# pdp8i-cpu.net
KiCad netlist of a schematic drawn in EAGLE
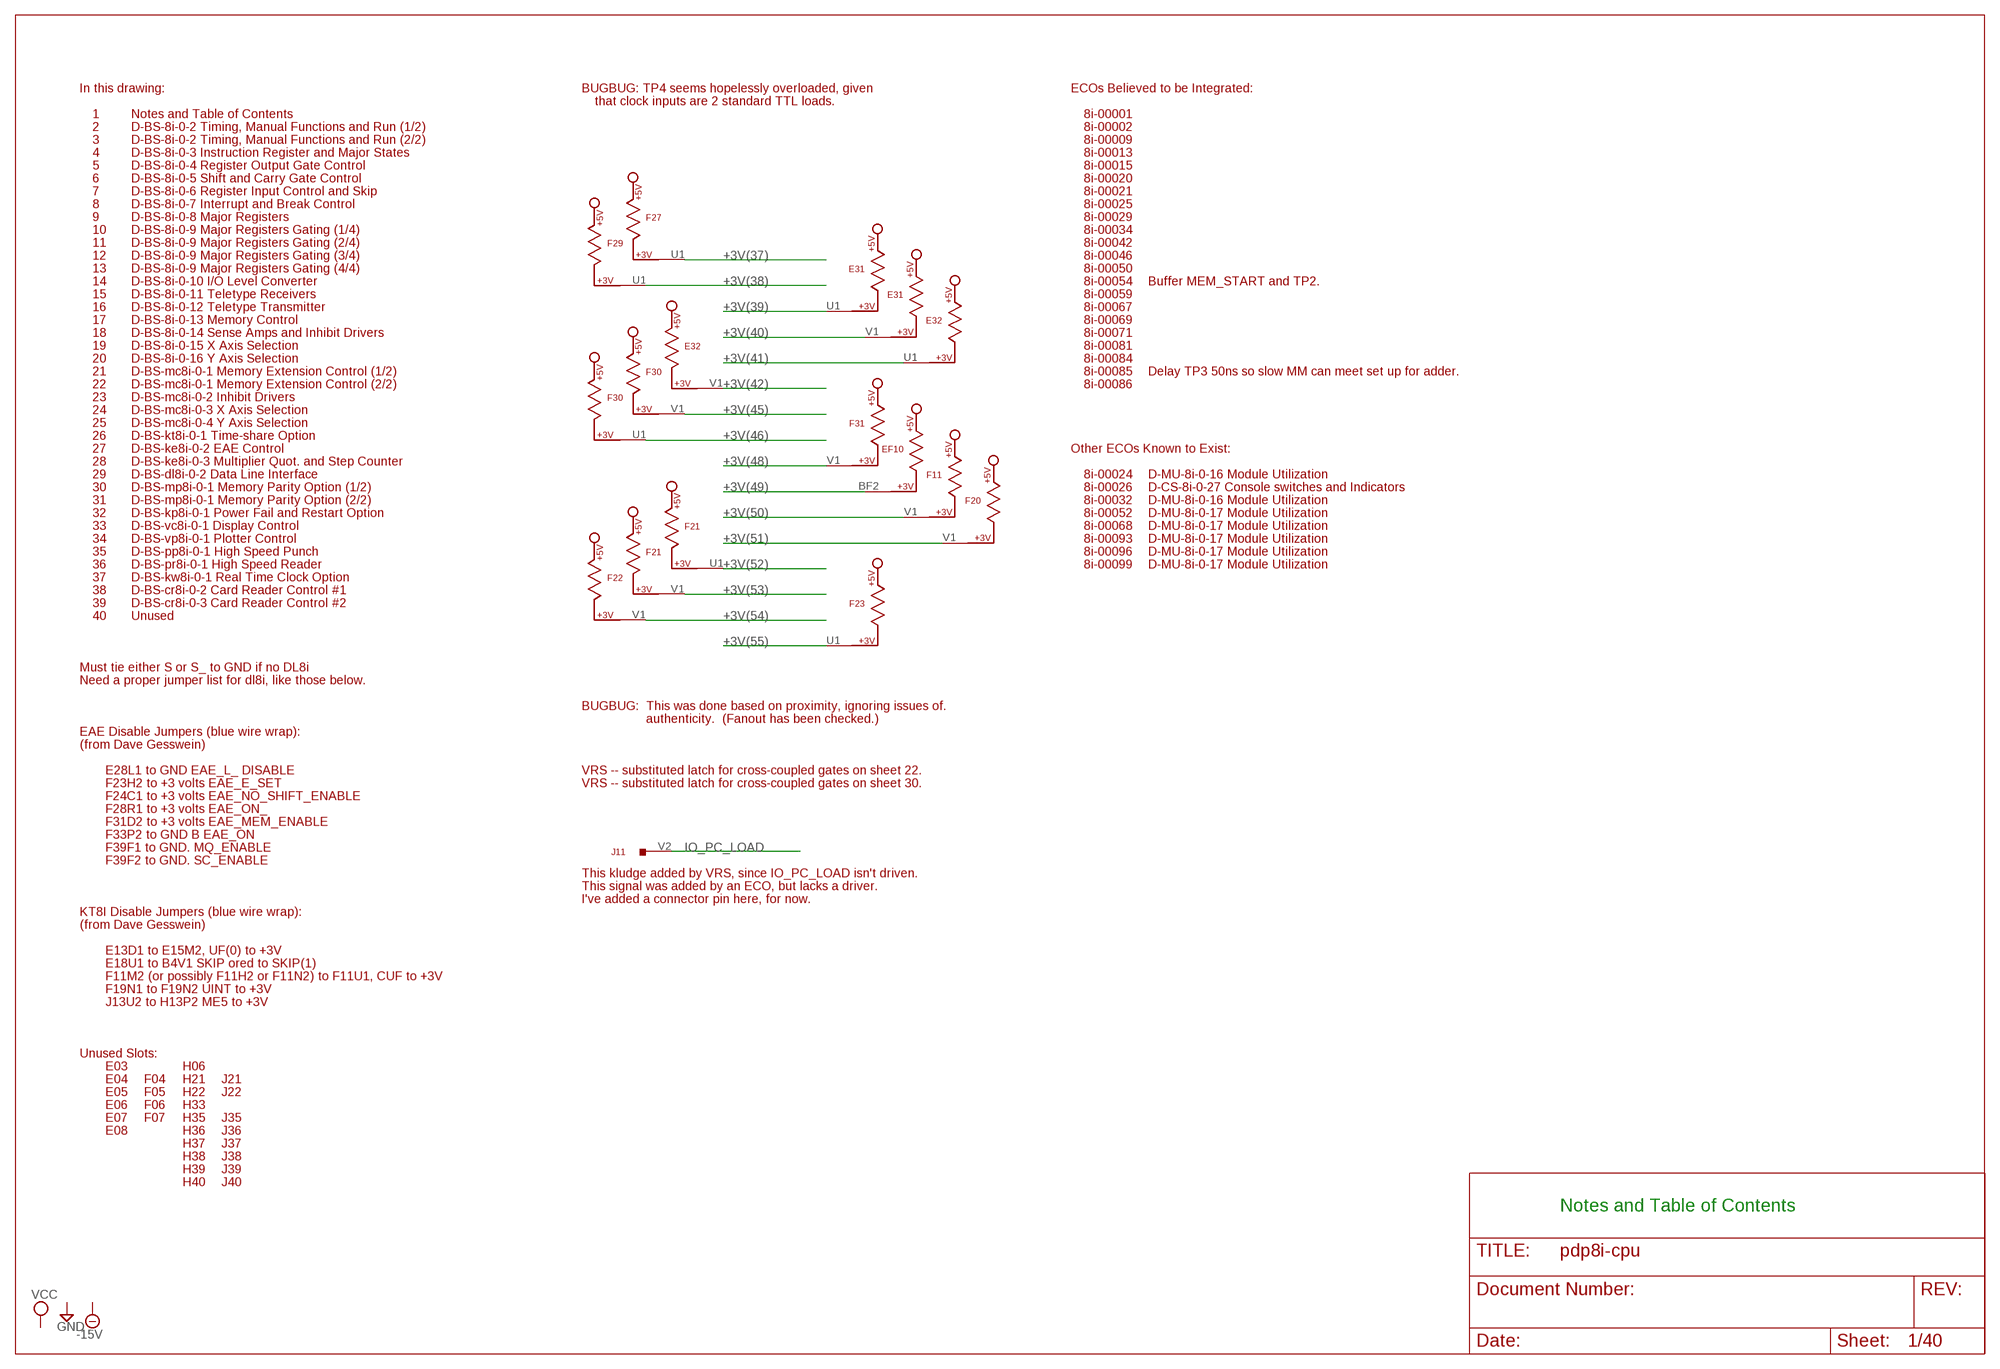
[diagram p0: schematic, sheet 1]
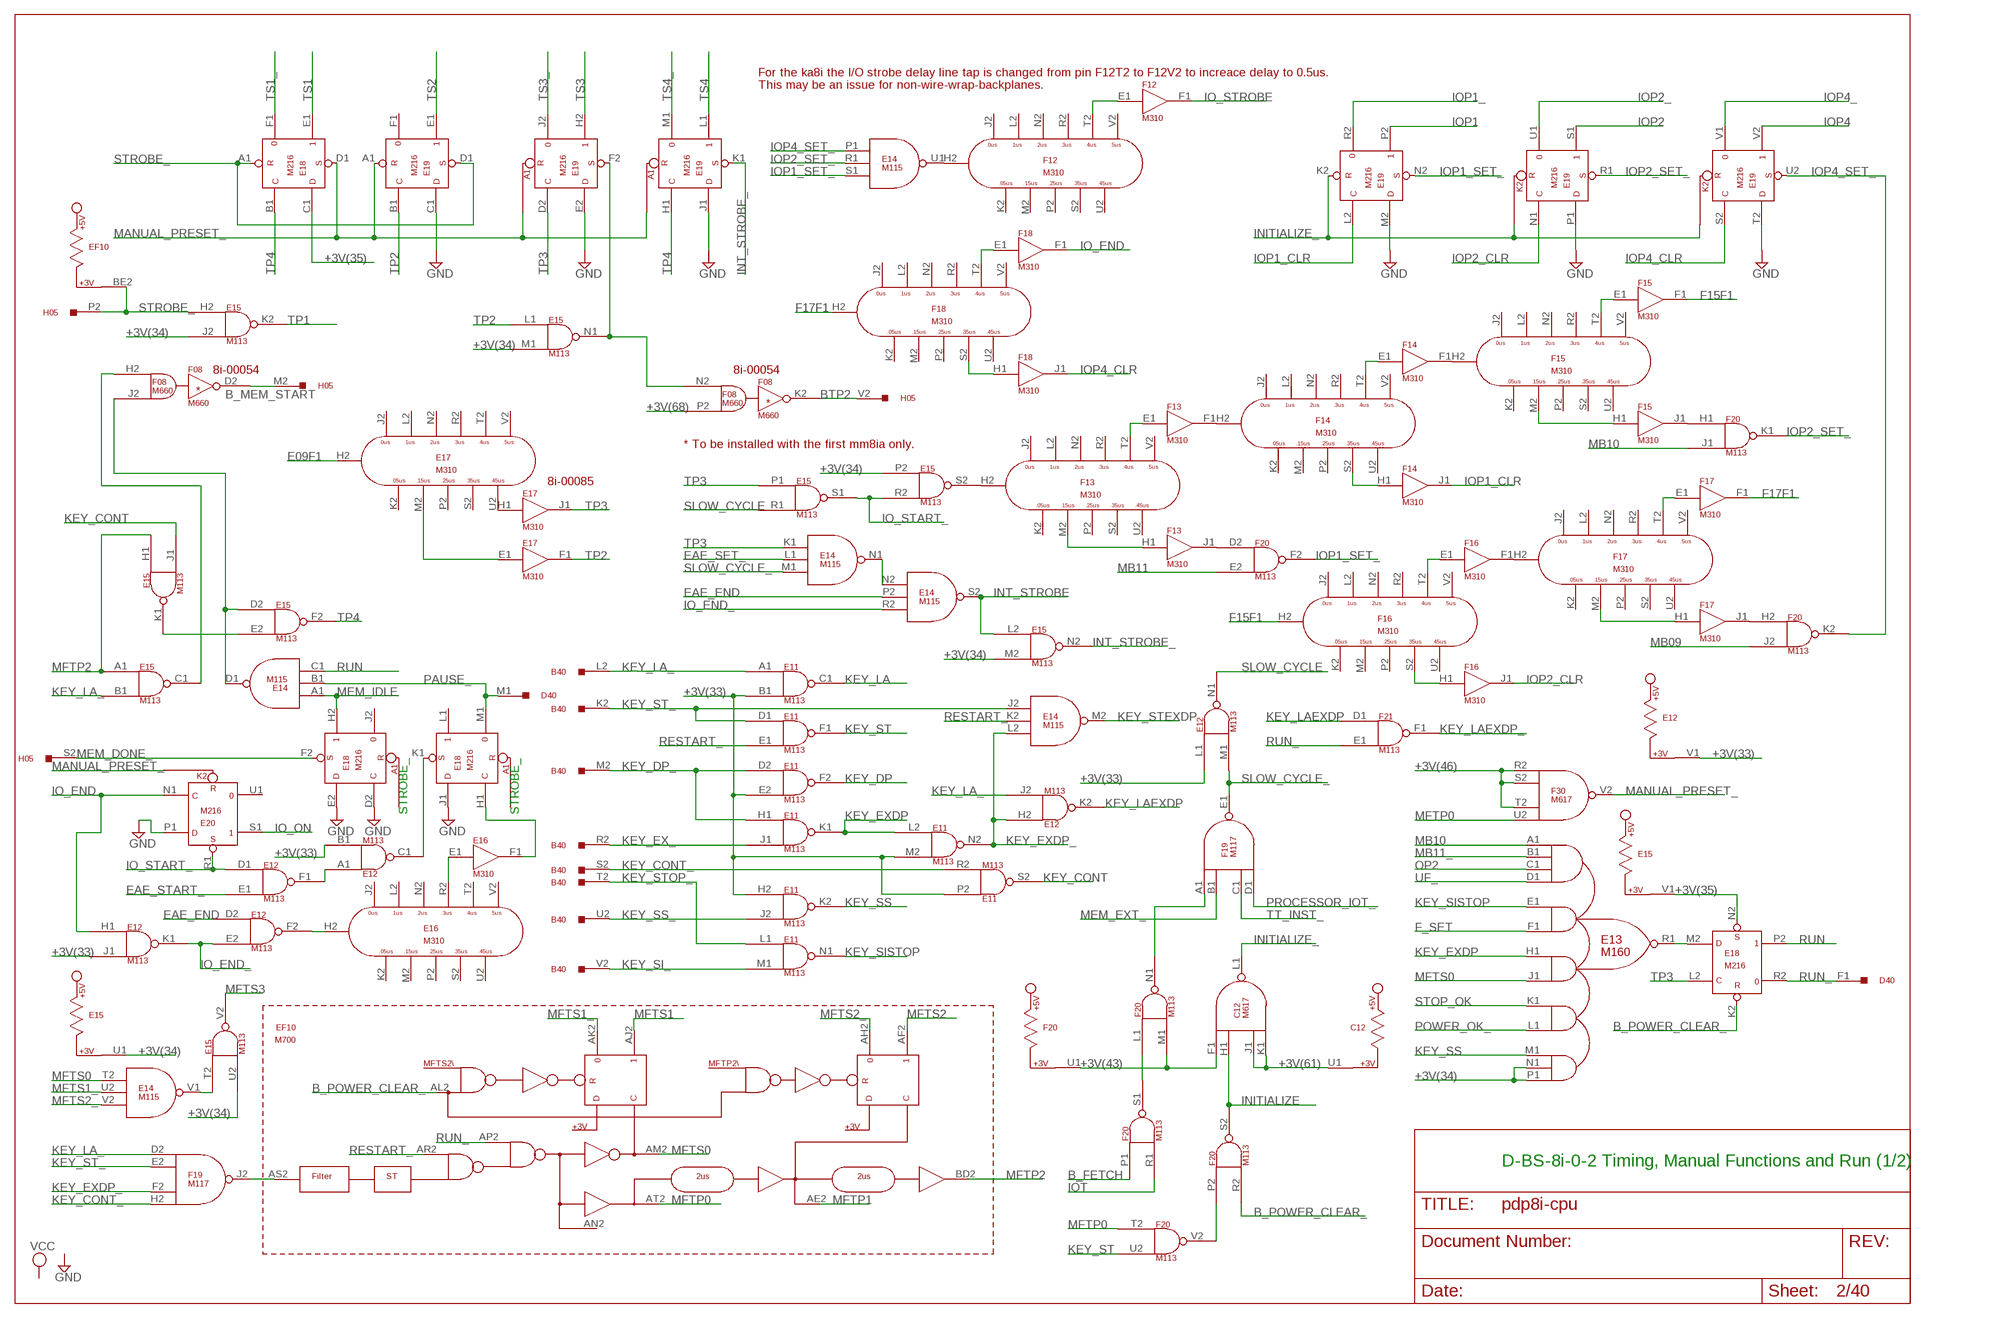
[diagram p1: schematic, sheet 2]
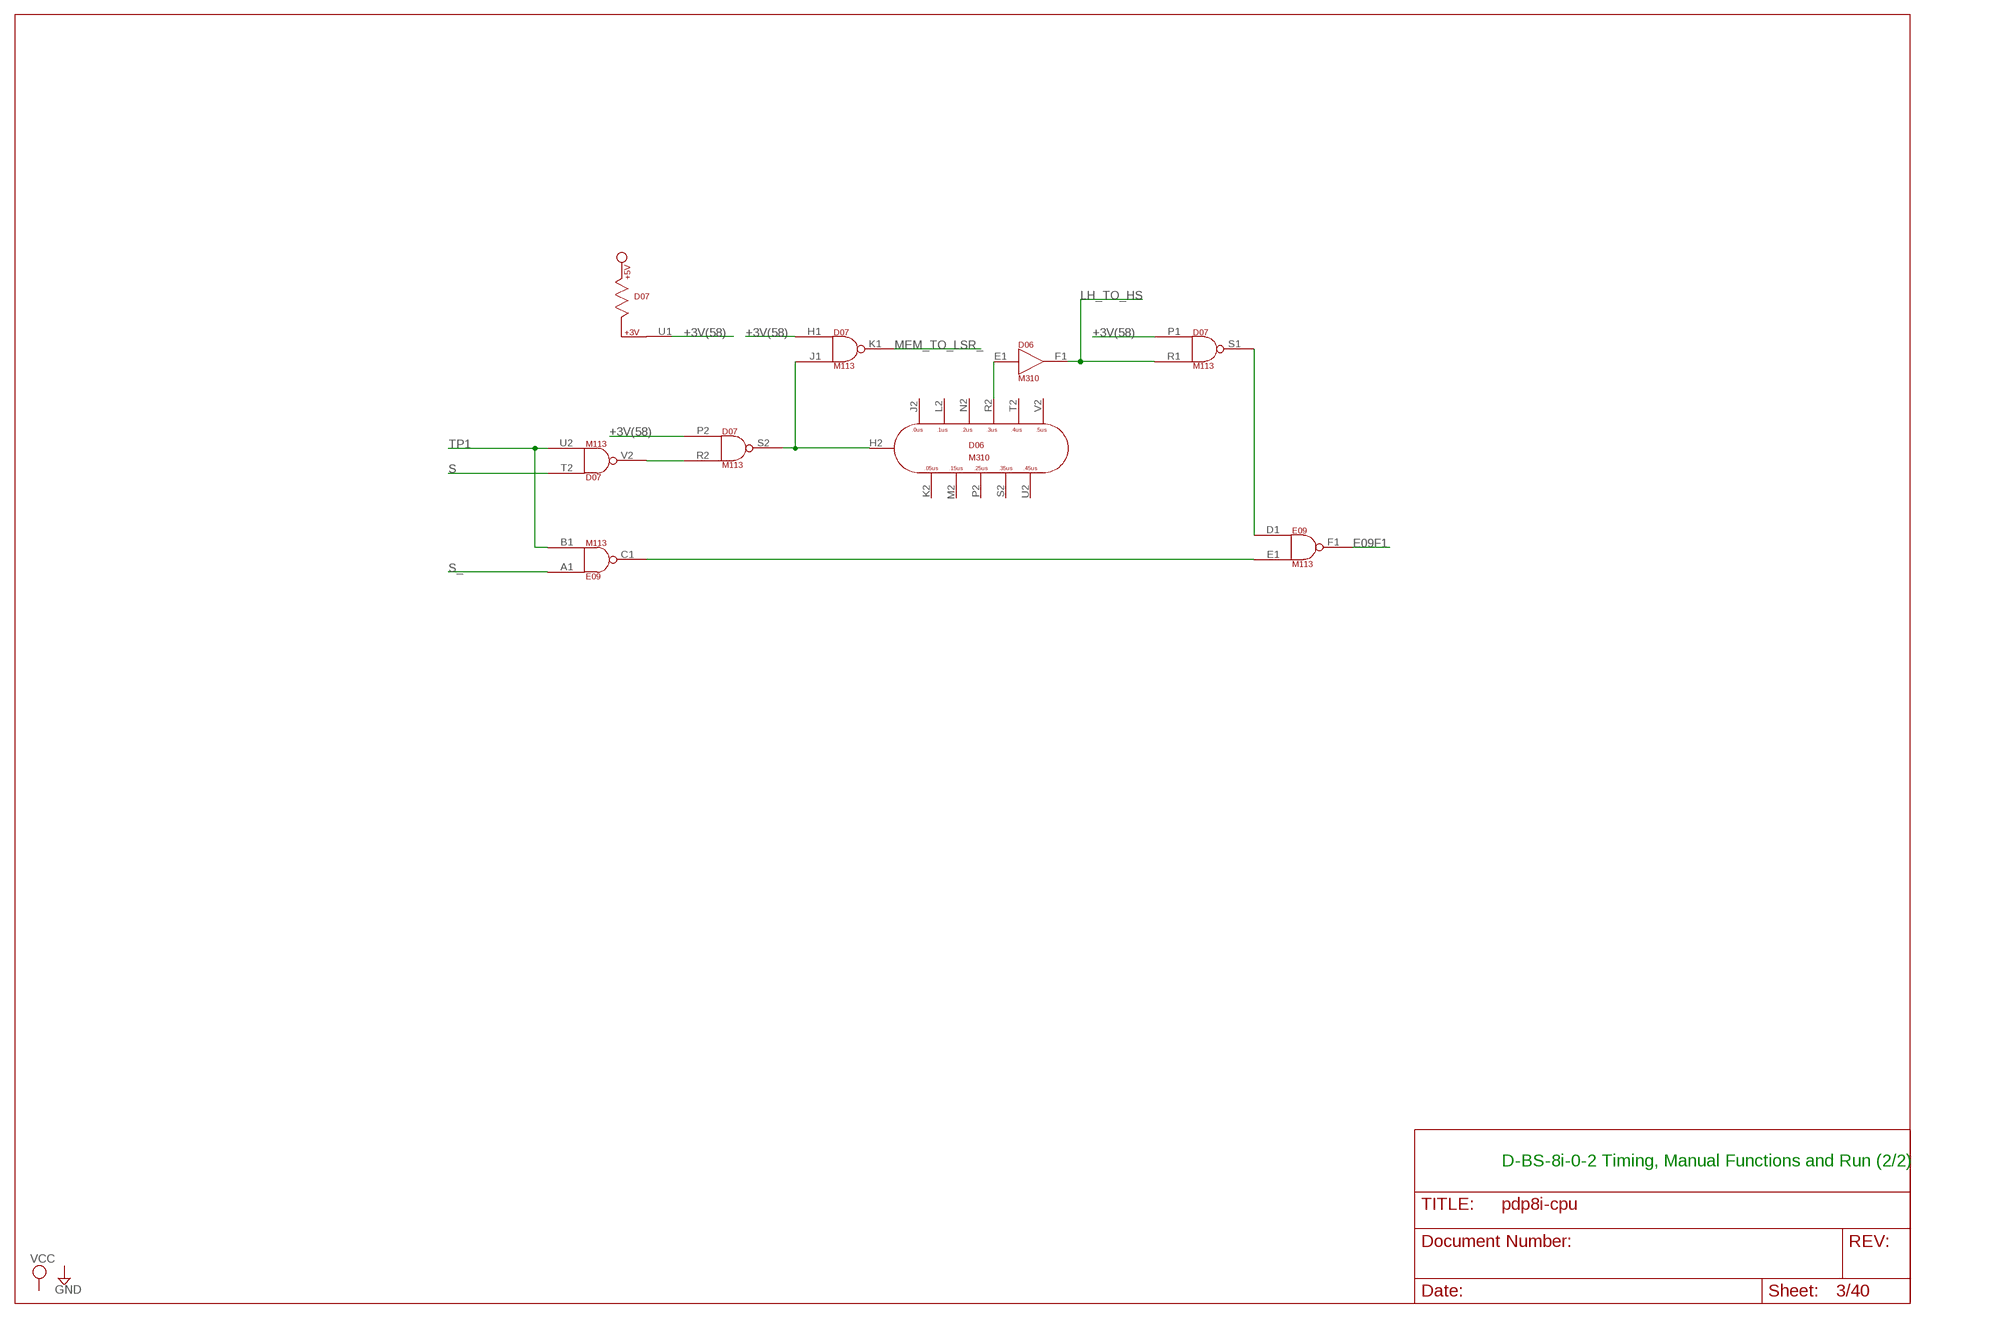
[diagram p2: schematic, sheet 3]
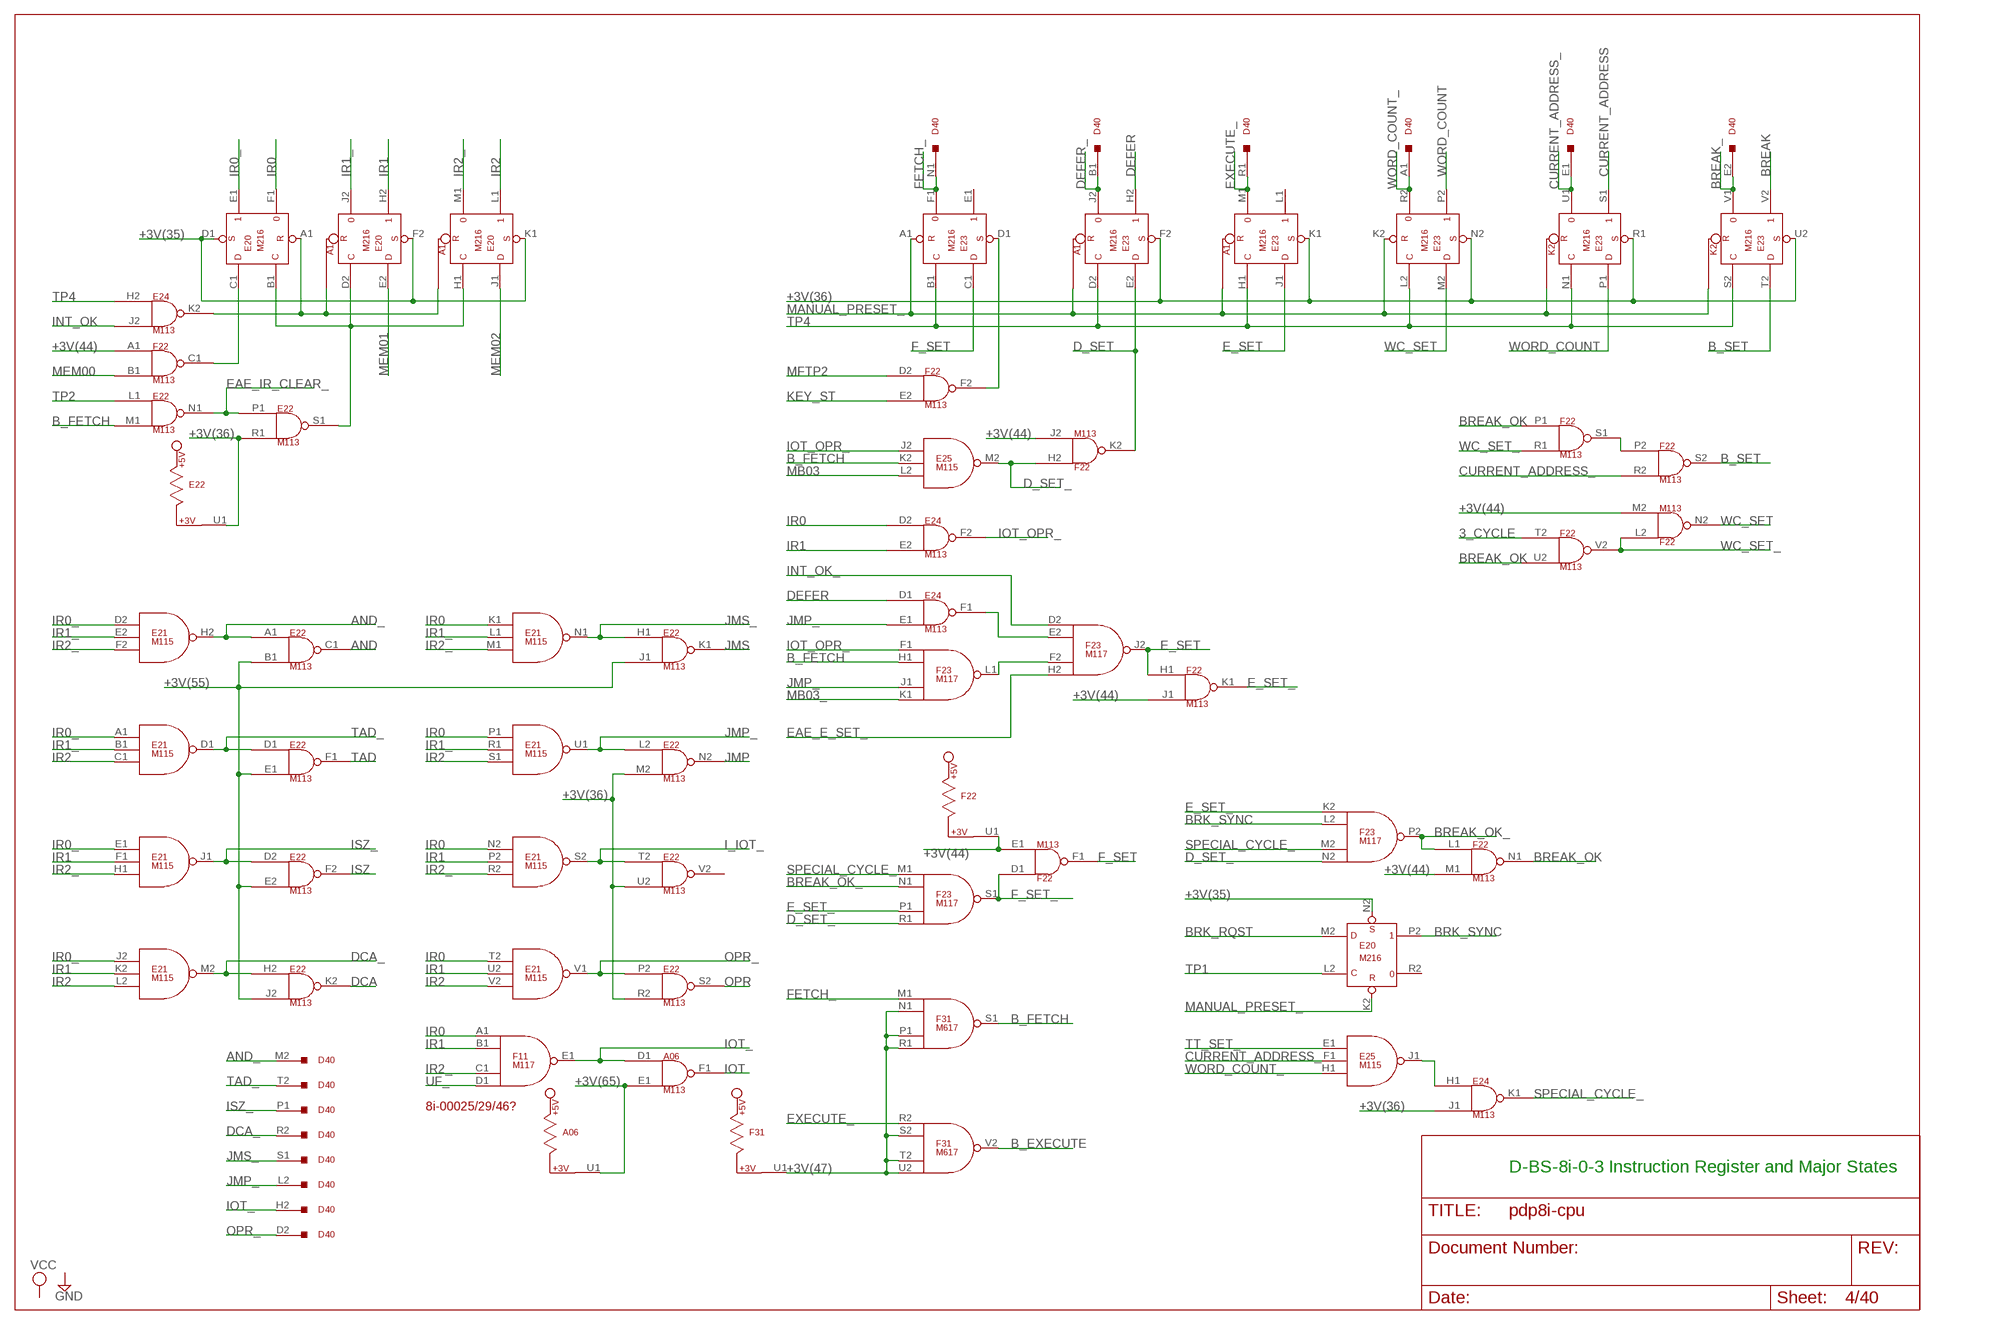
[diagram p3: schematic, sheet 4]
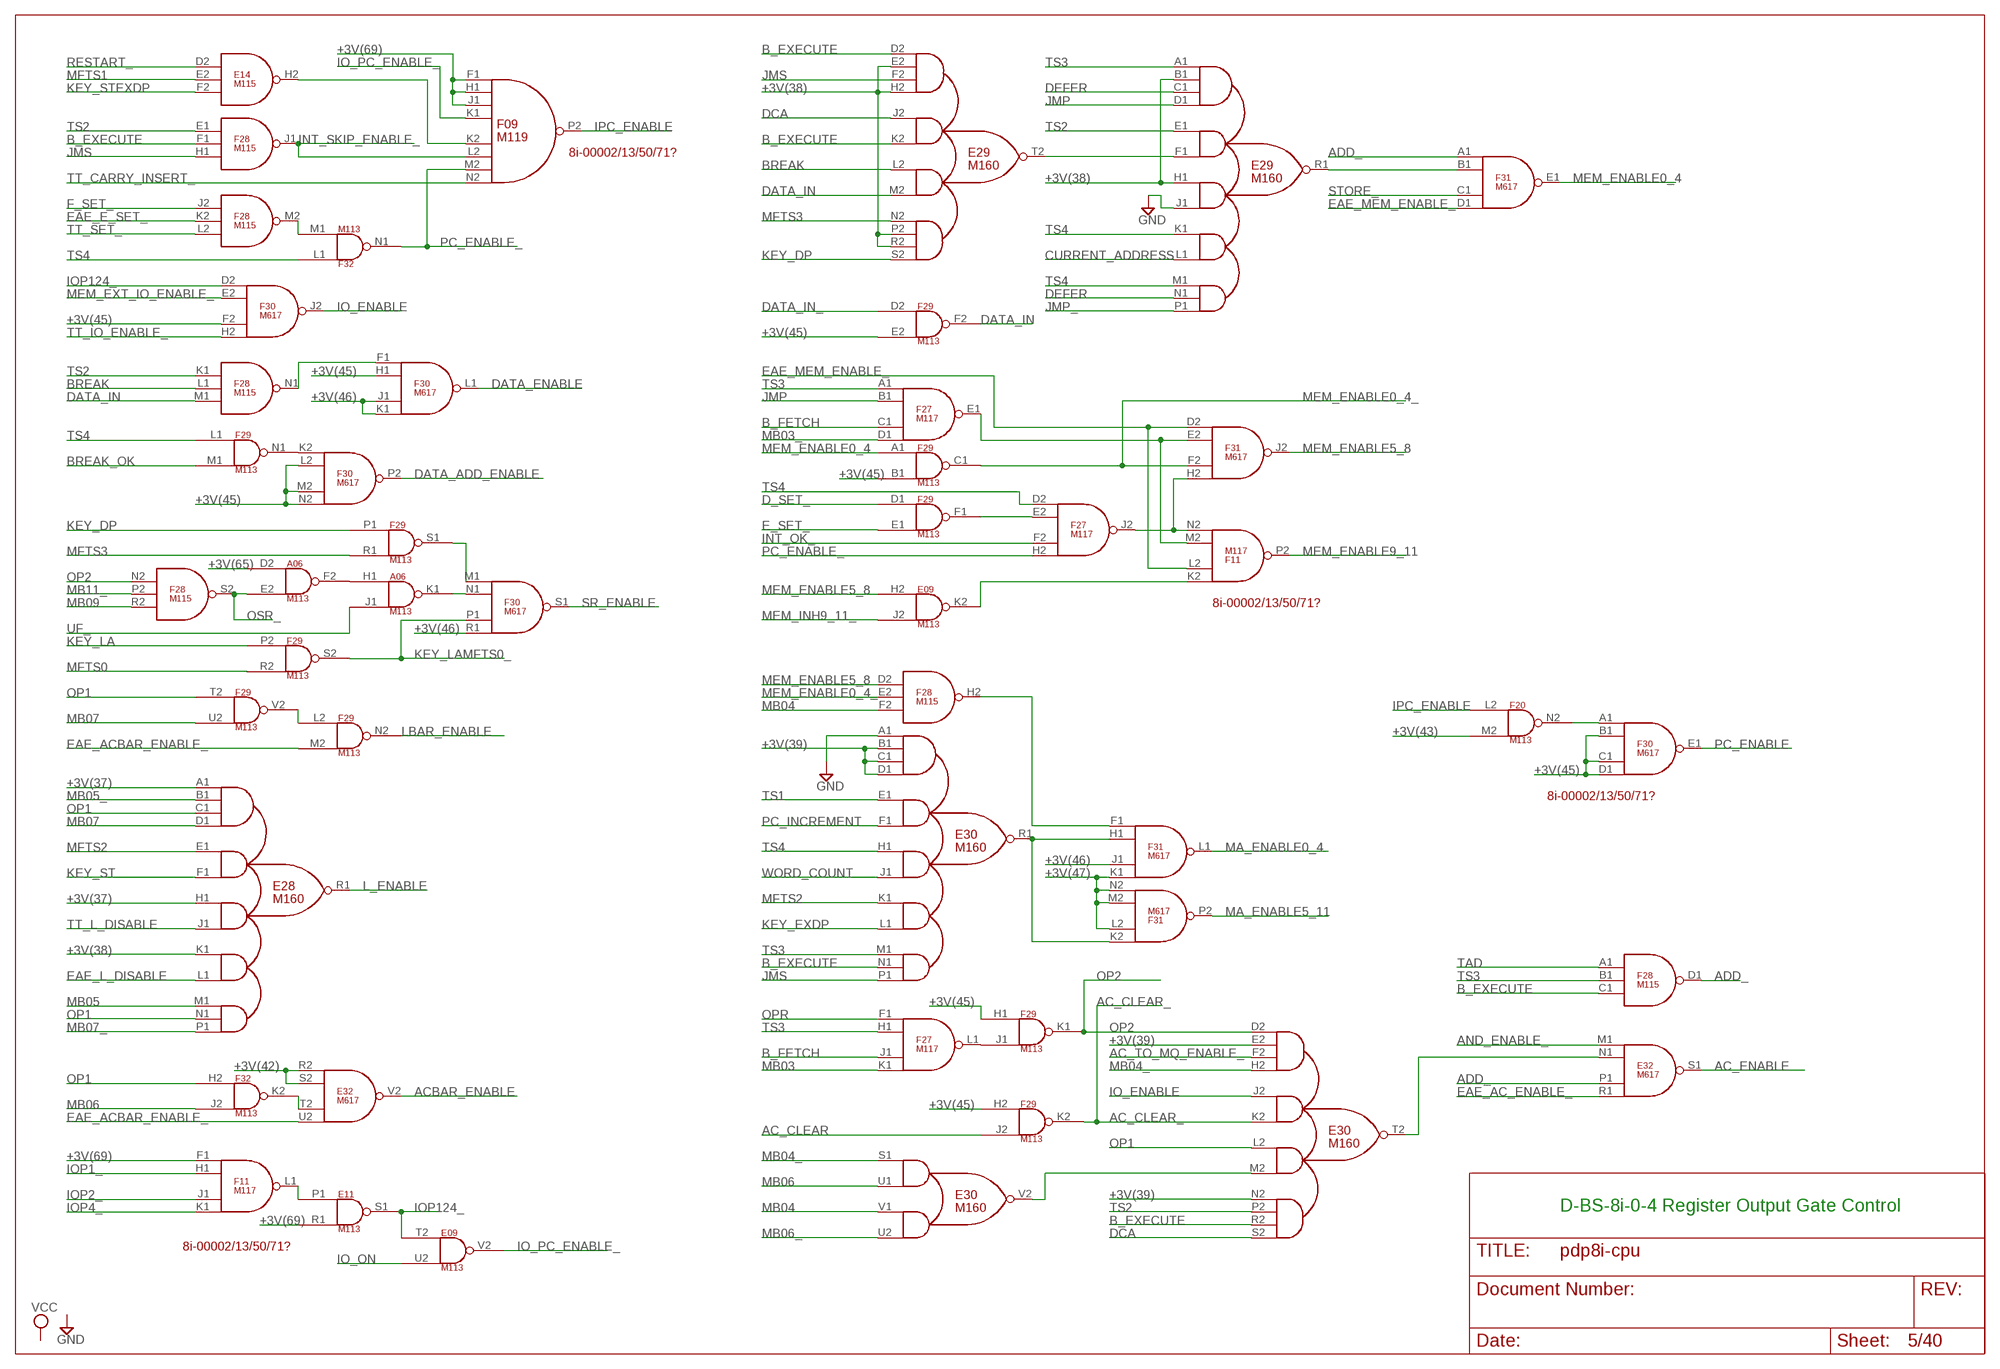
[diagram p4: schematic, sheet 5]
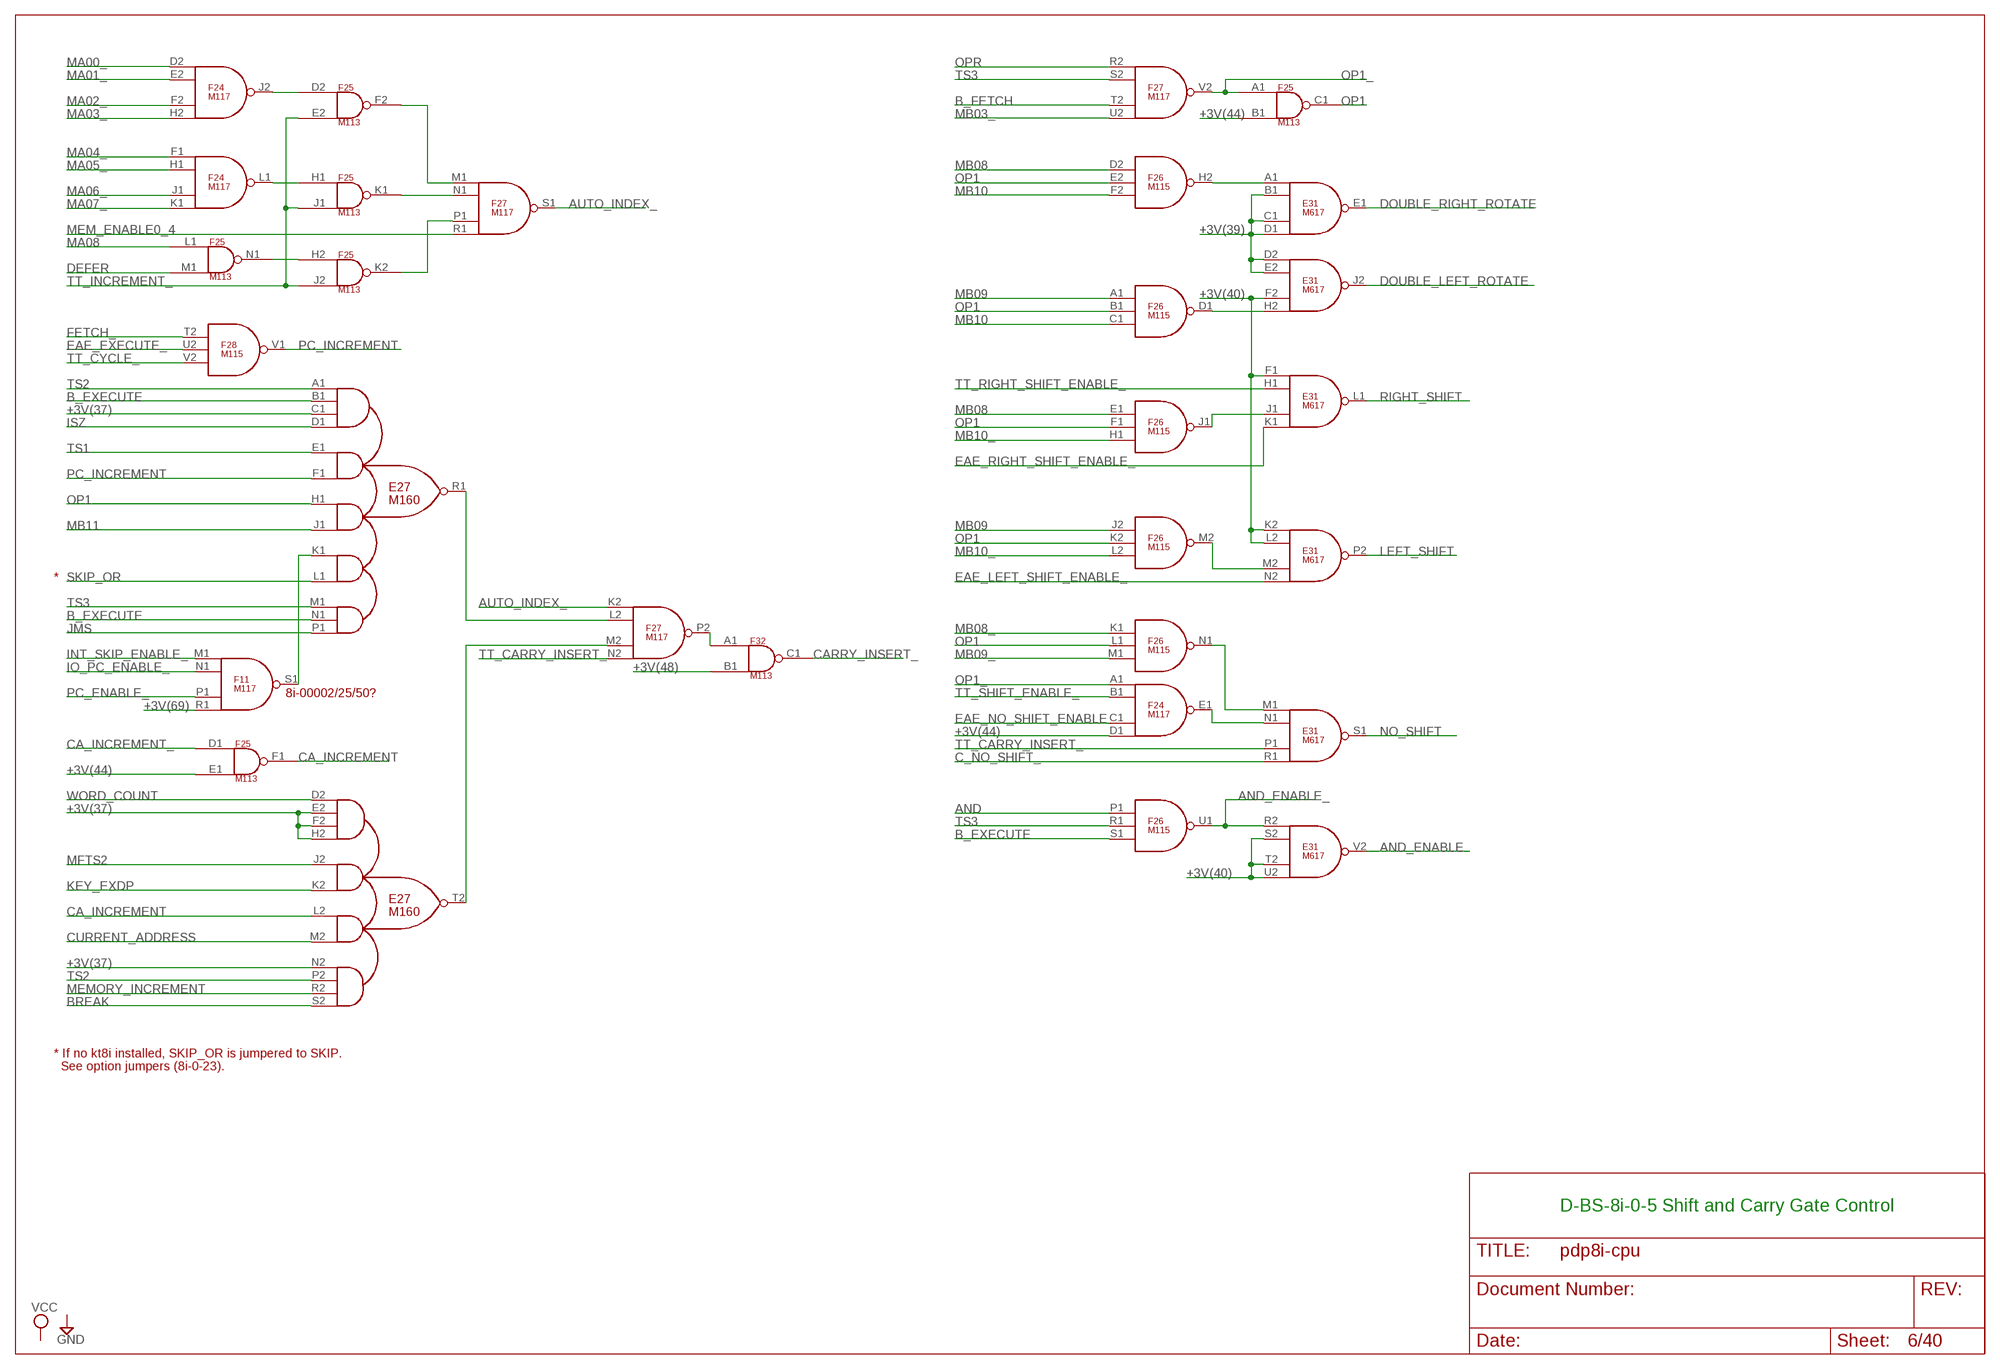
[diagram p5: schematic, sheet 6]
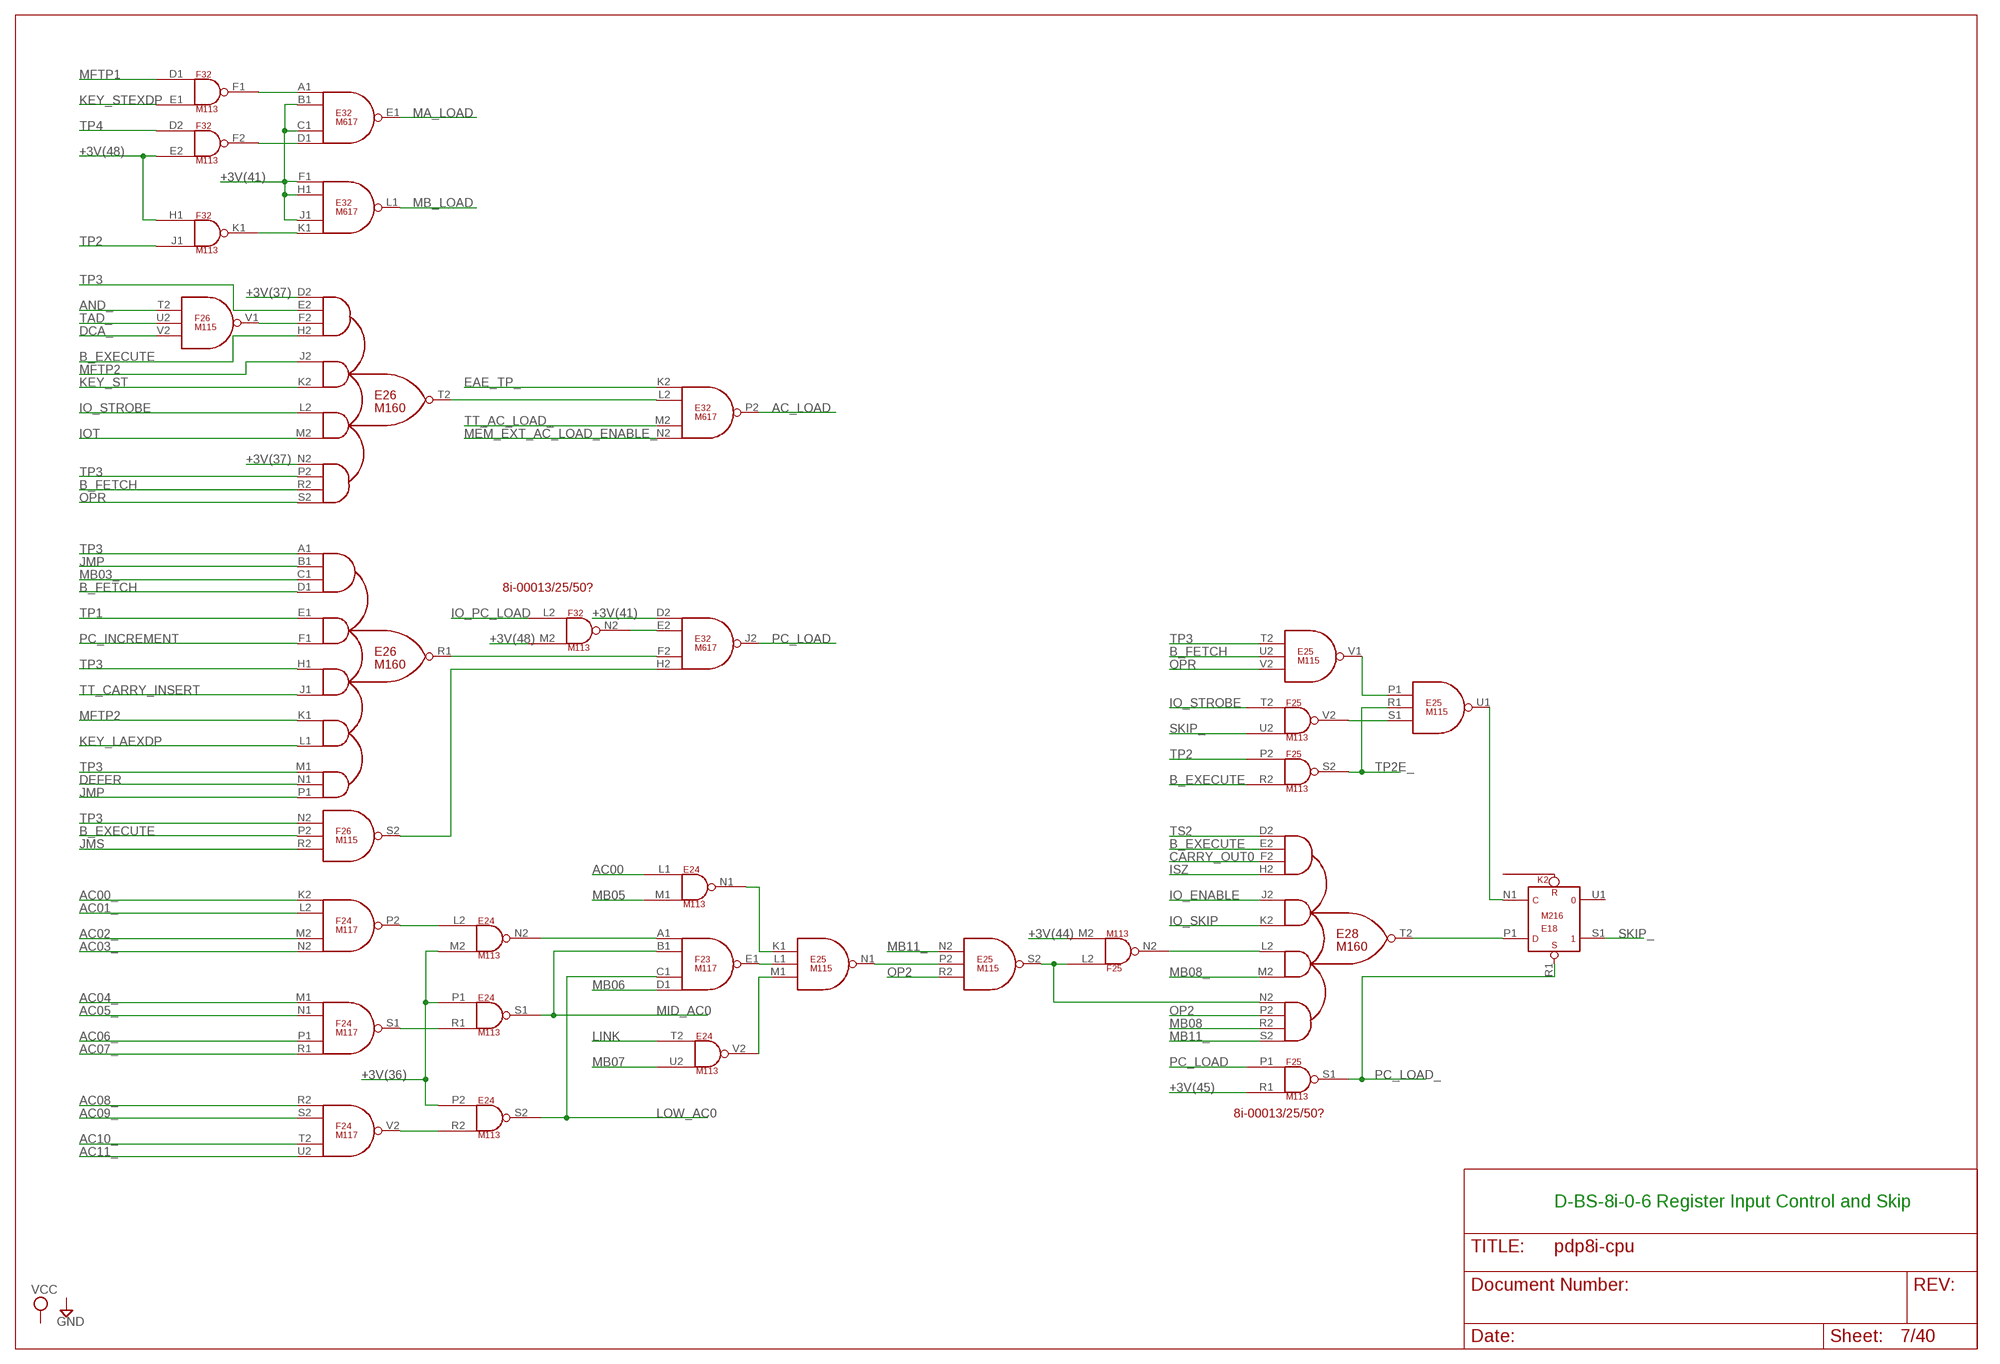
[diagram p6: schematic, sheet 7]
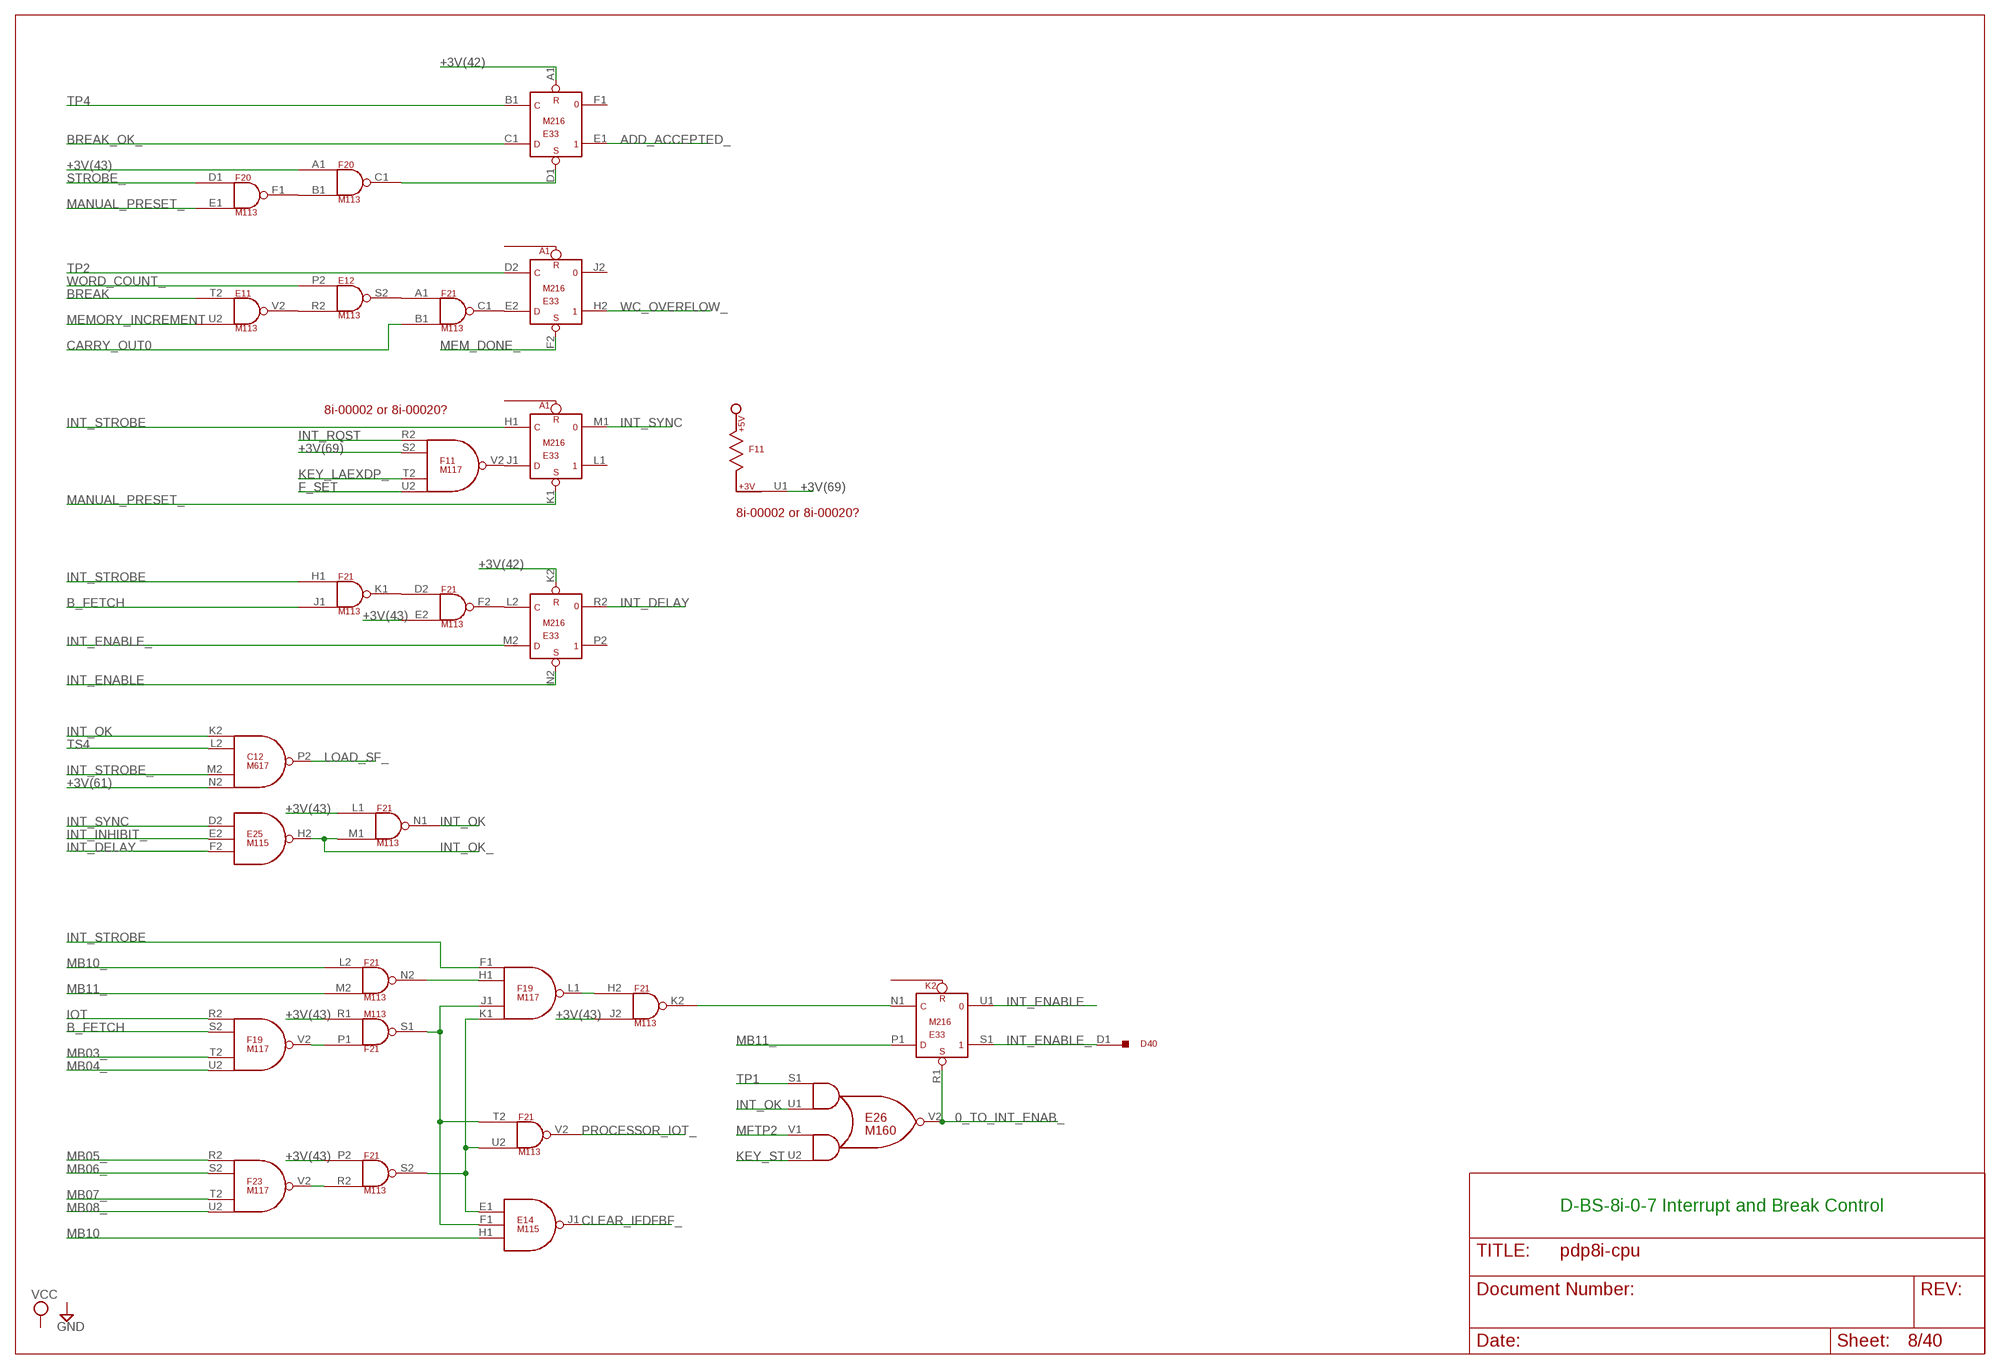
[diagram p7: schematic, sheet 8]
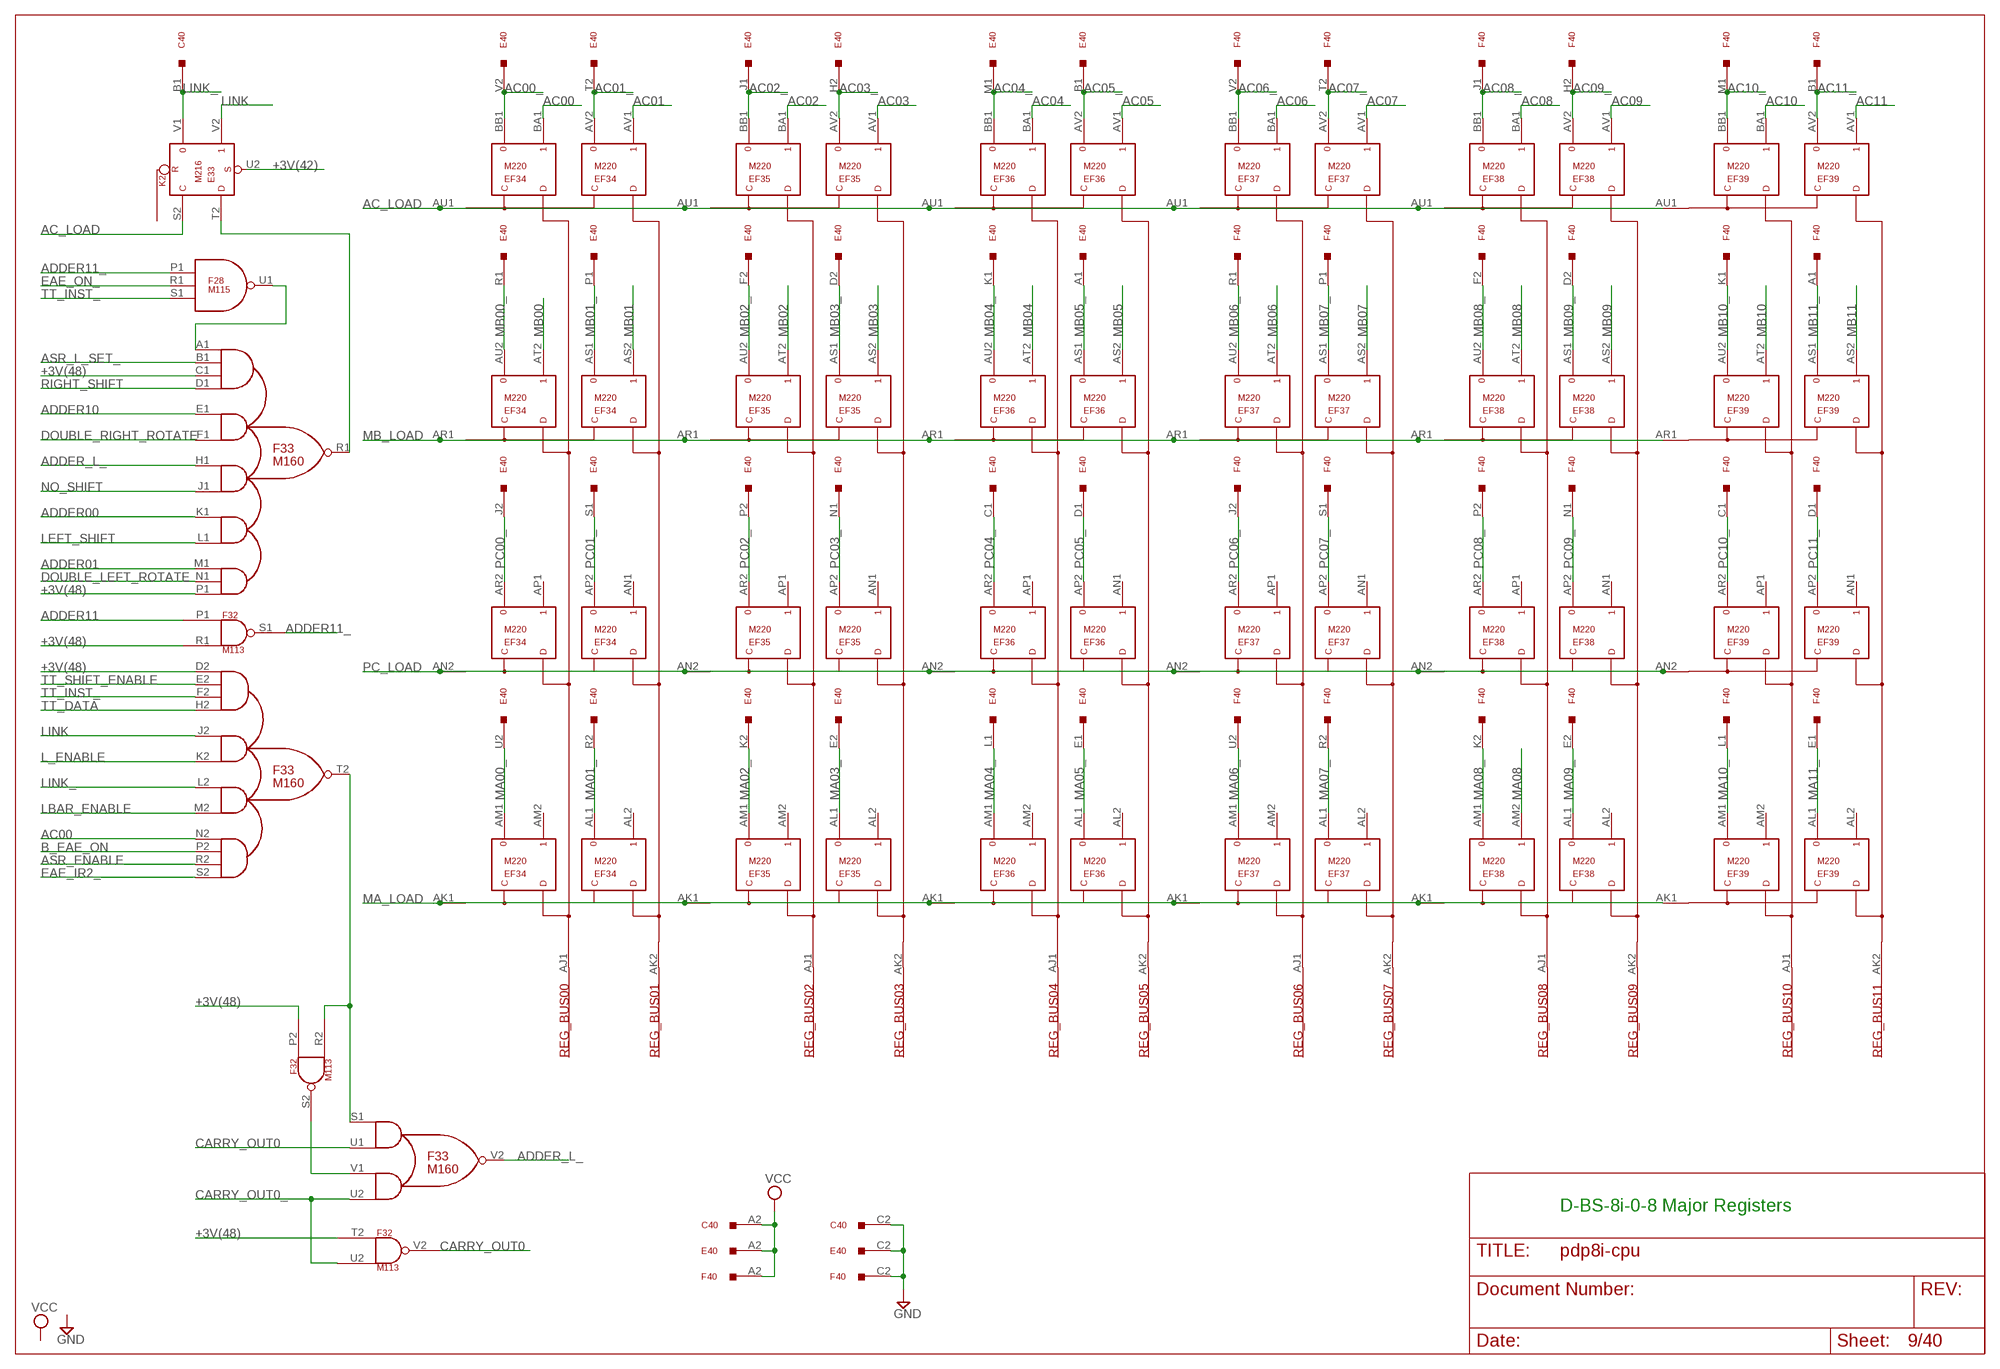
[diagram p8: schematic, sheet 9]
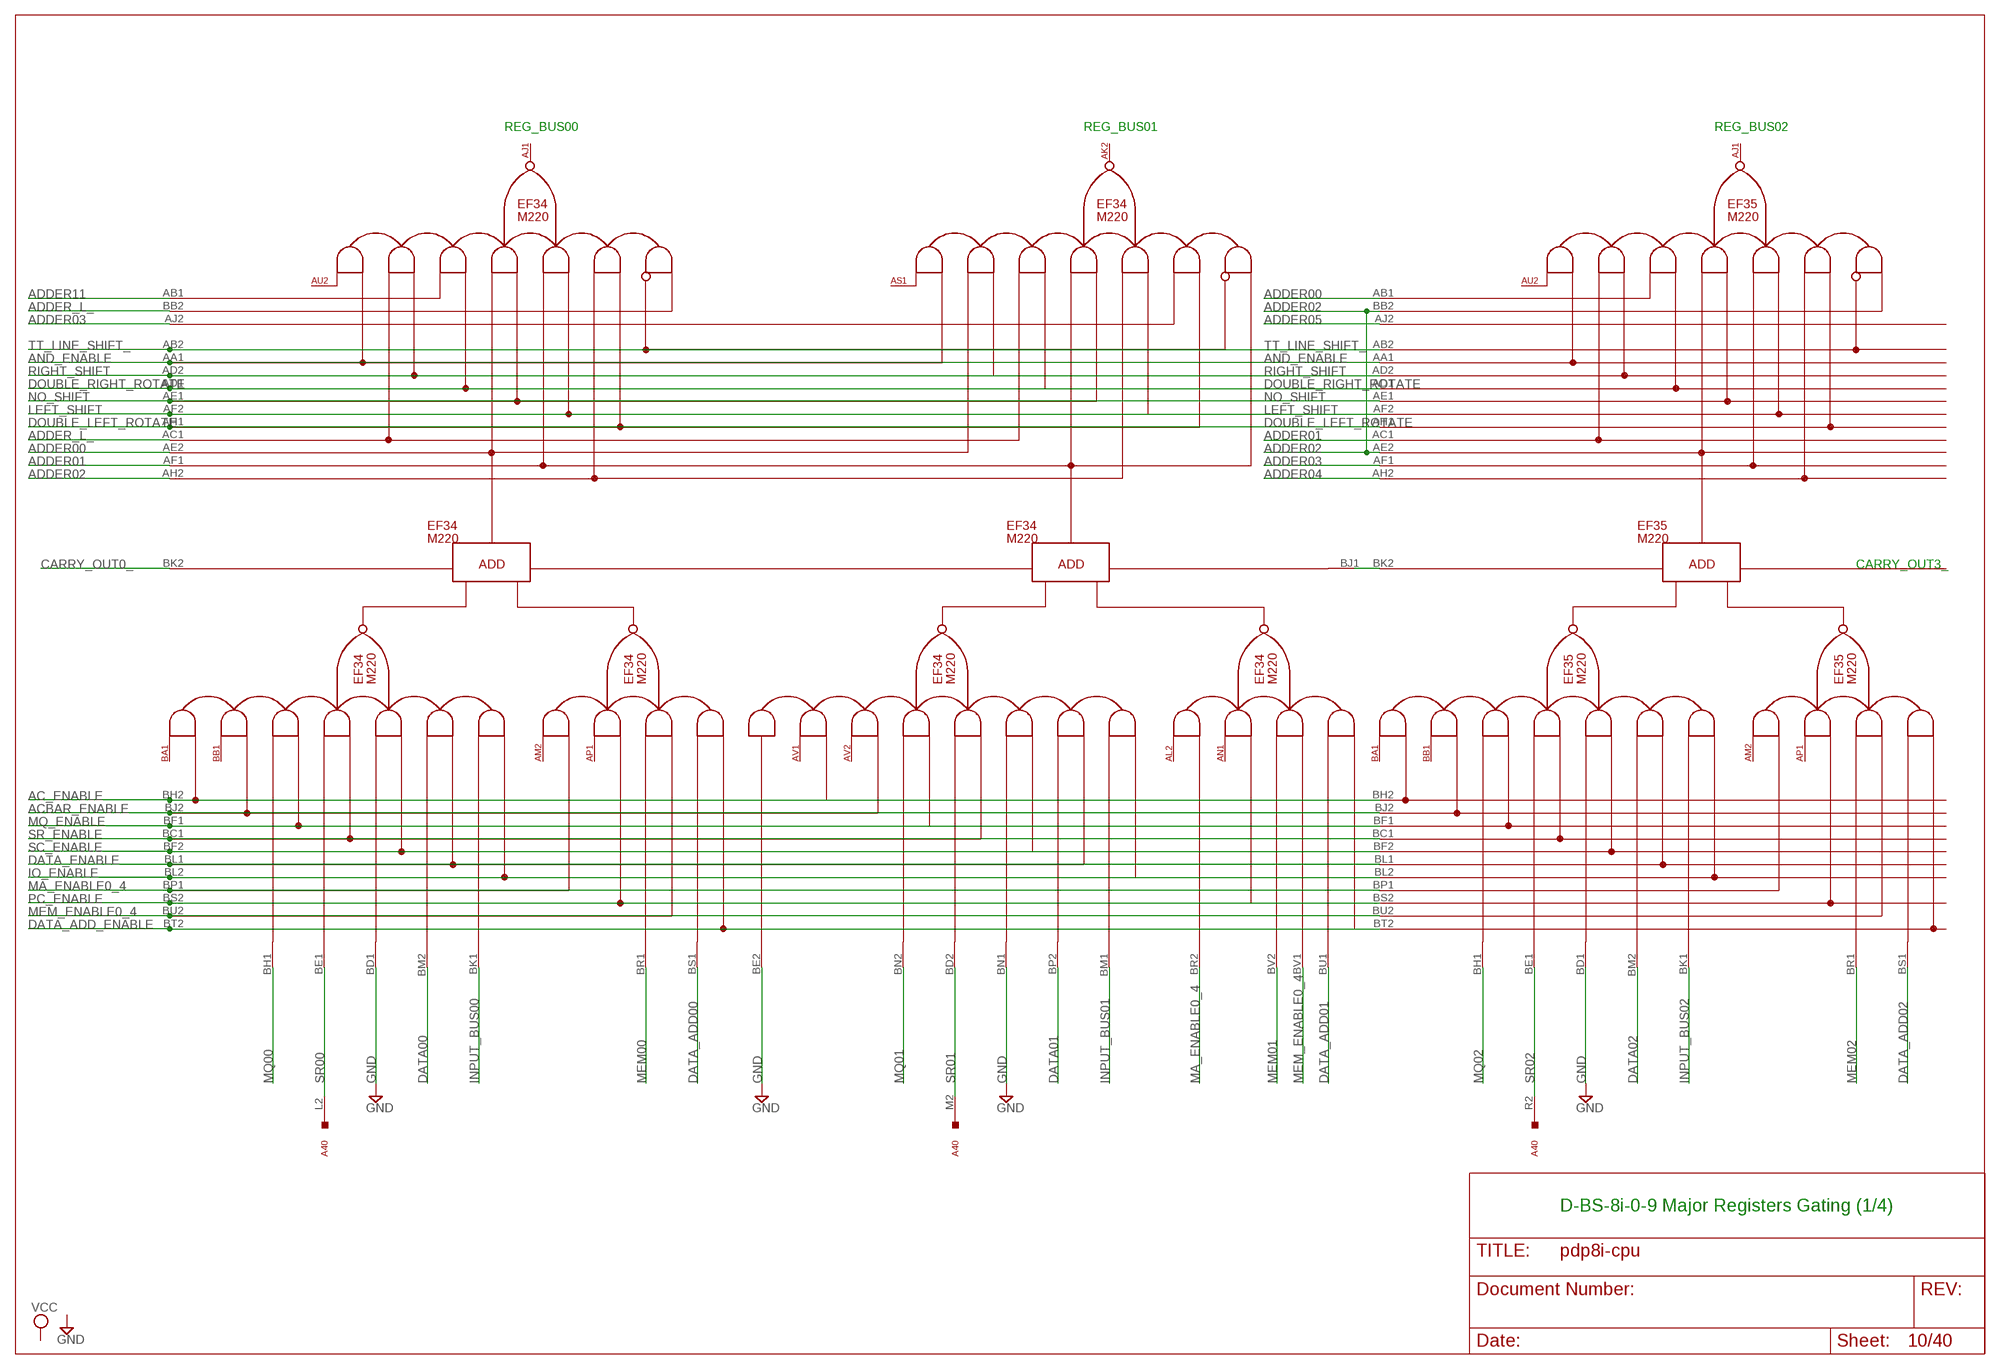
[diagram p9: schematic, sheet 10]
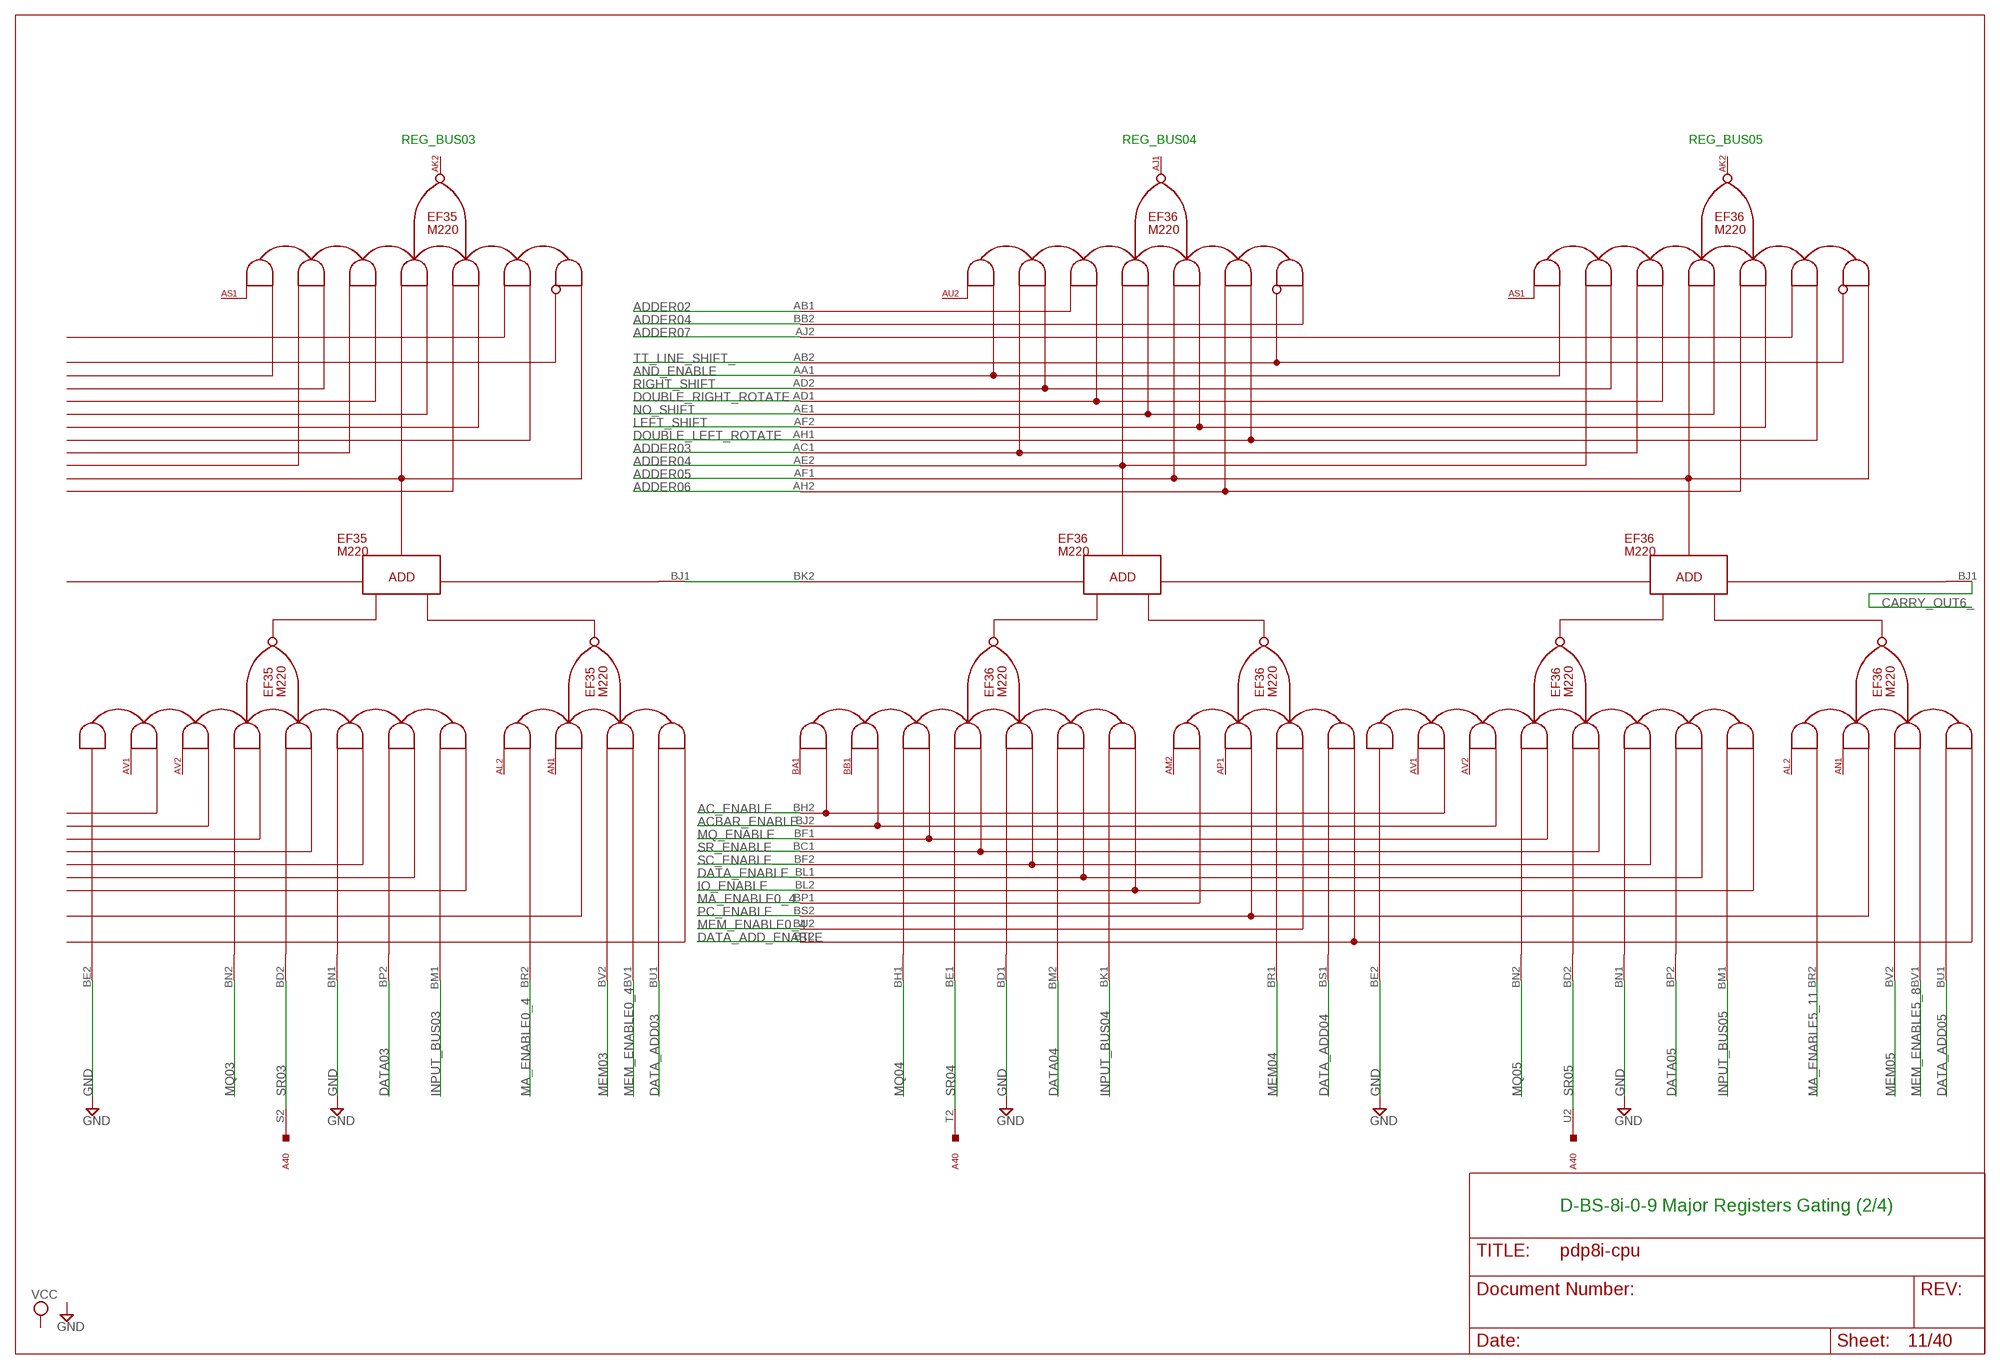
[diagram p10: schematic, sheet 11]
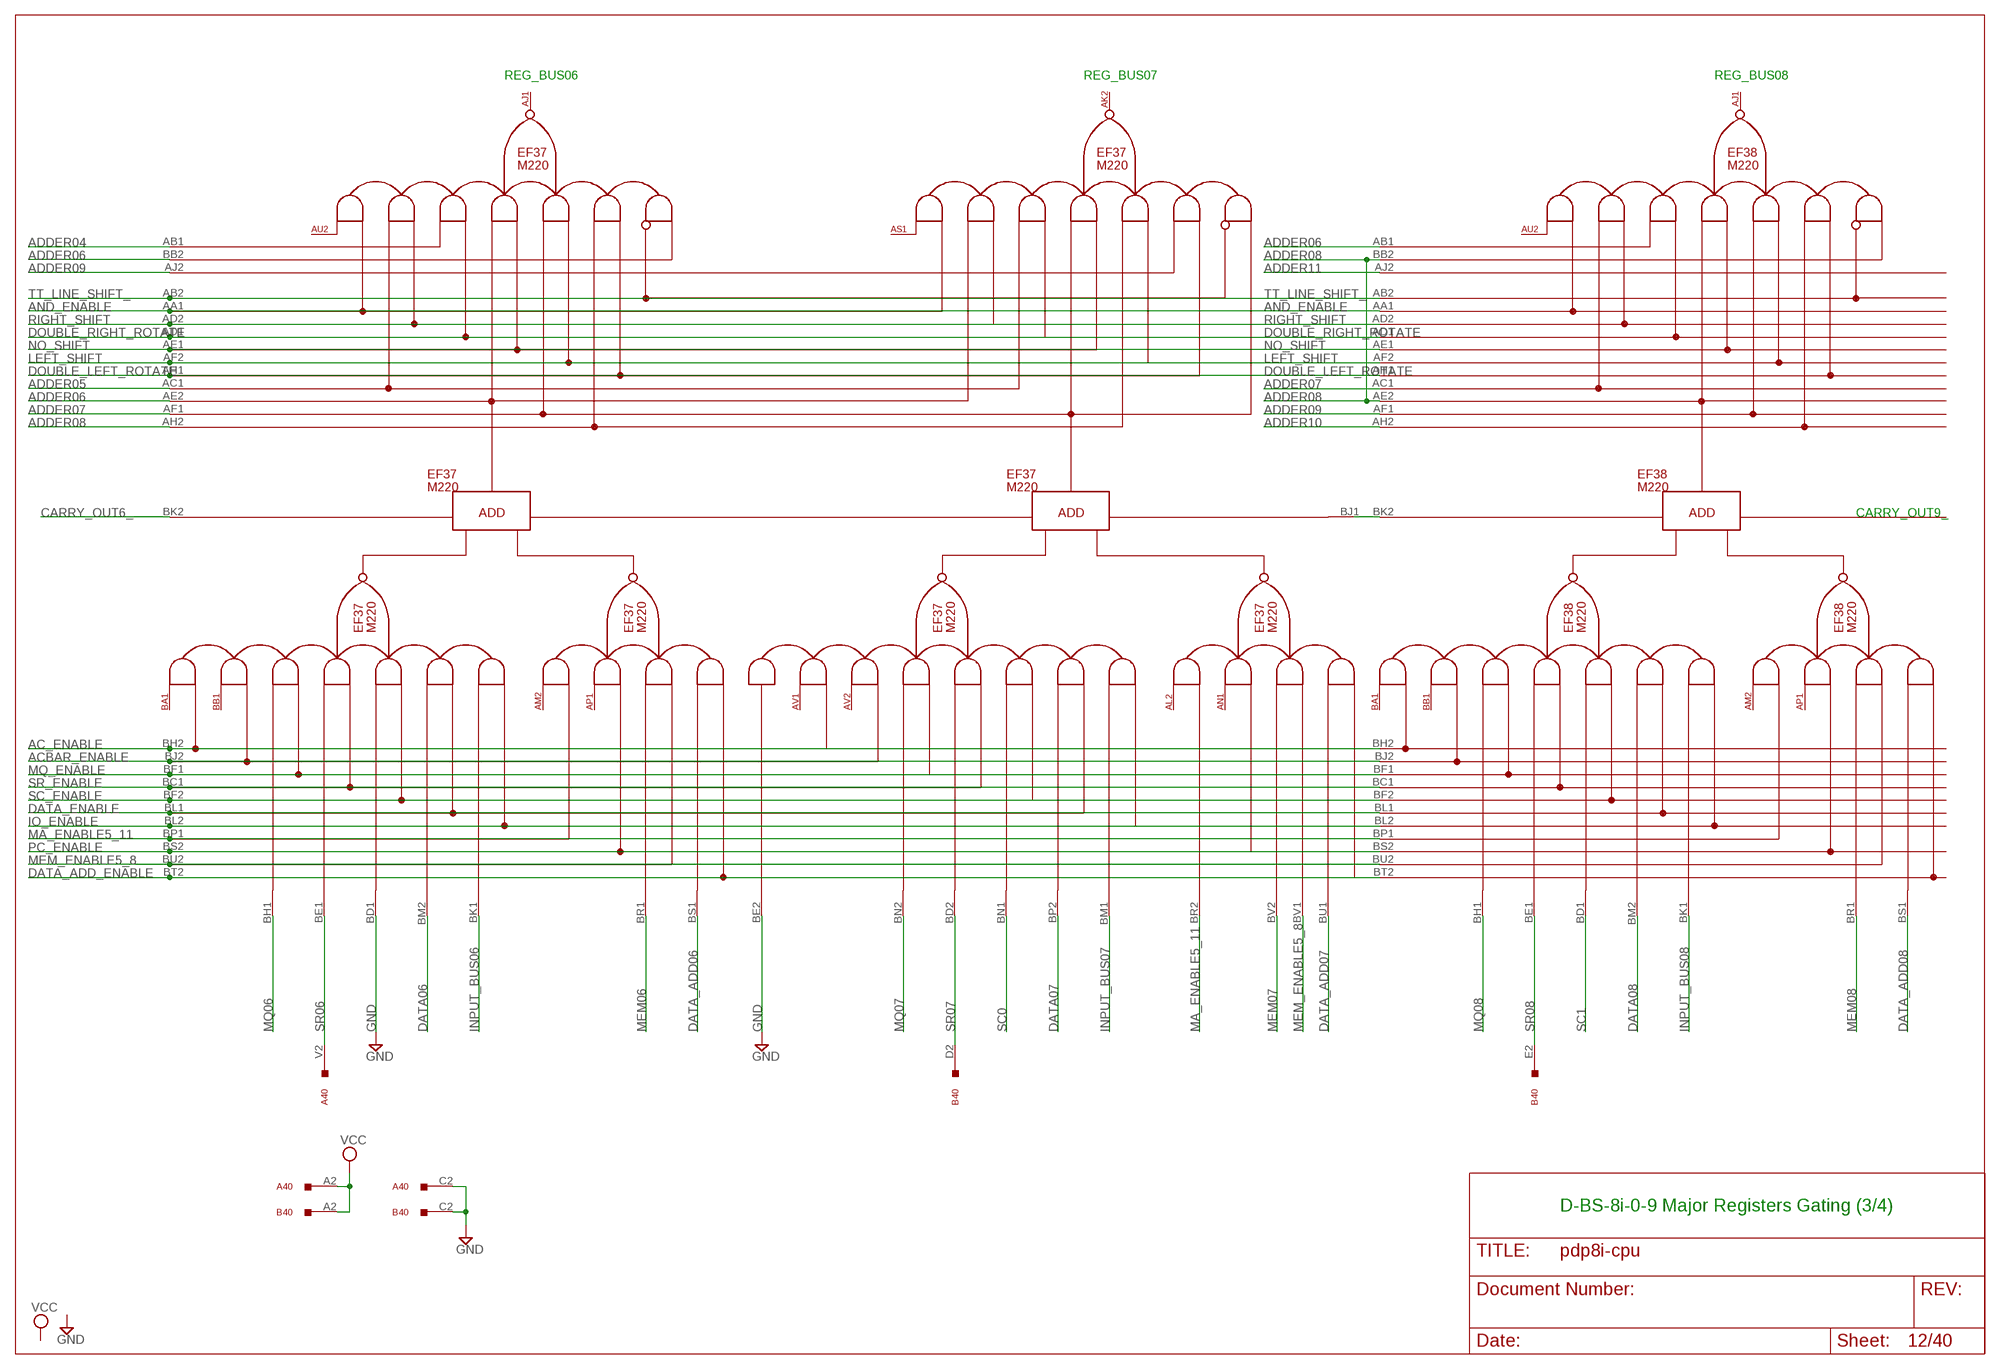
[diagram p11: schematic, sheet 12]
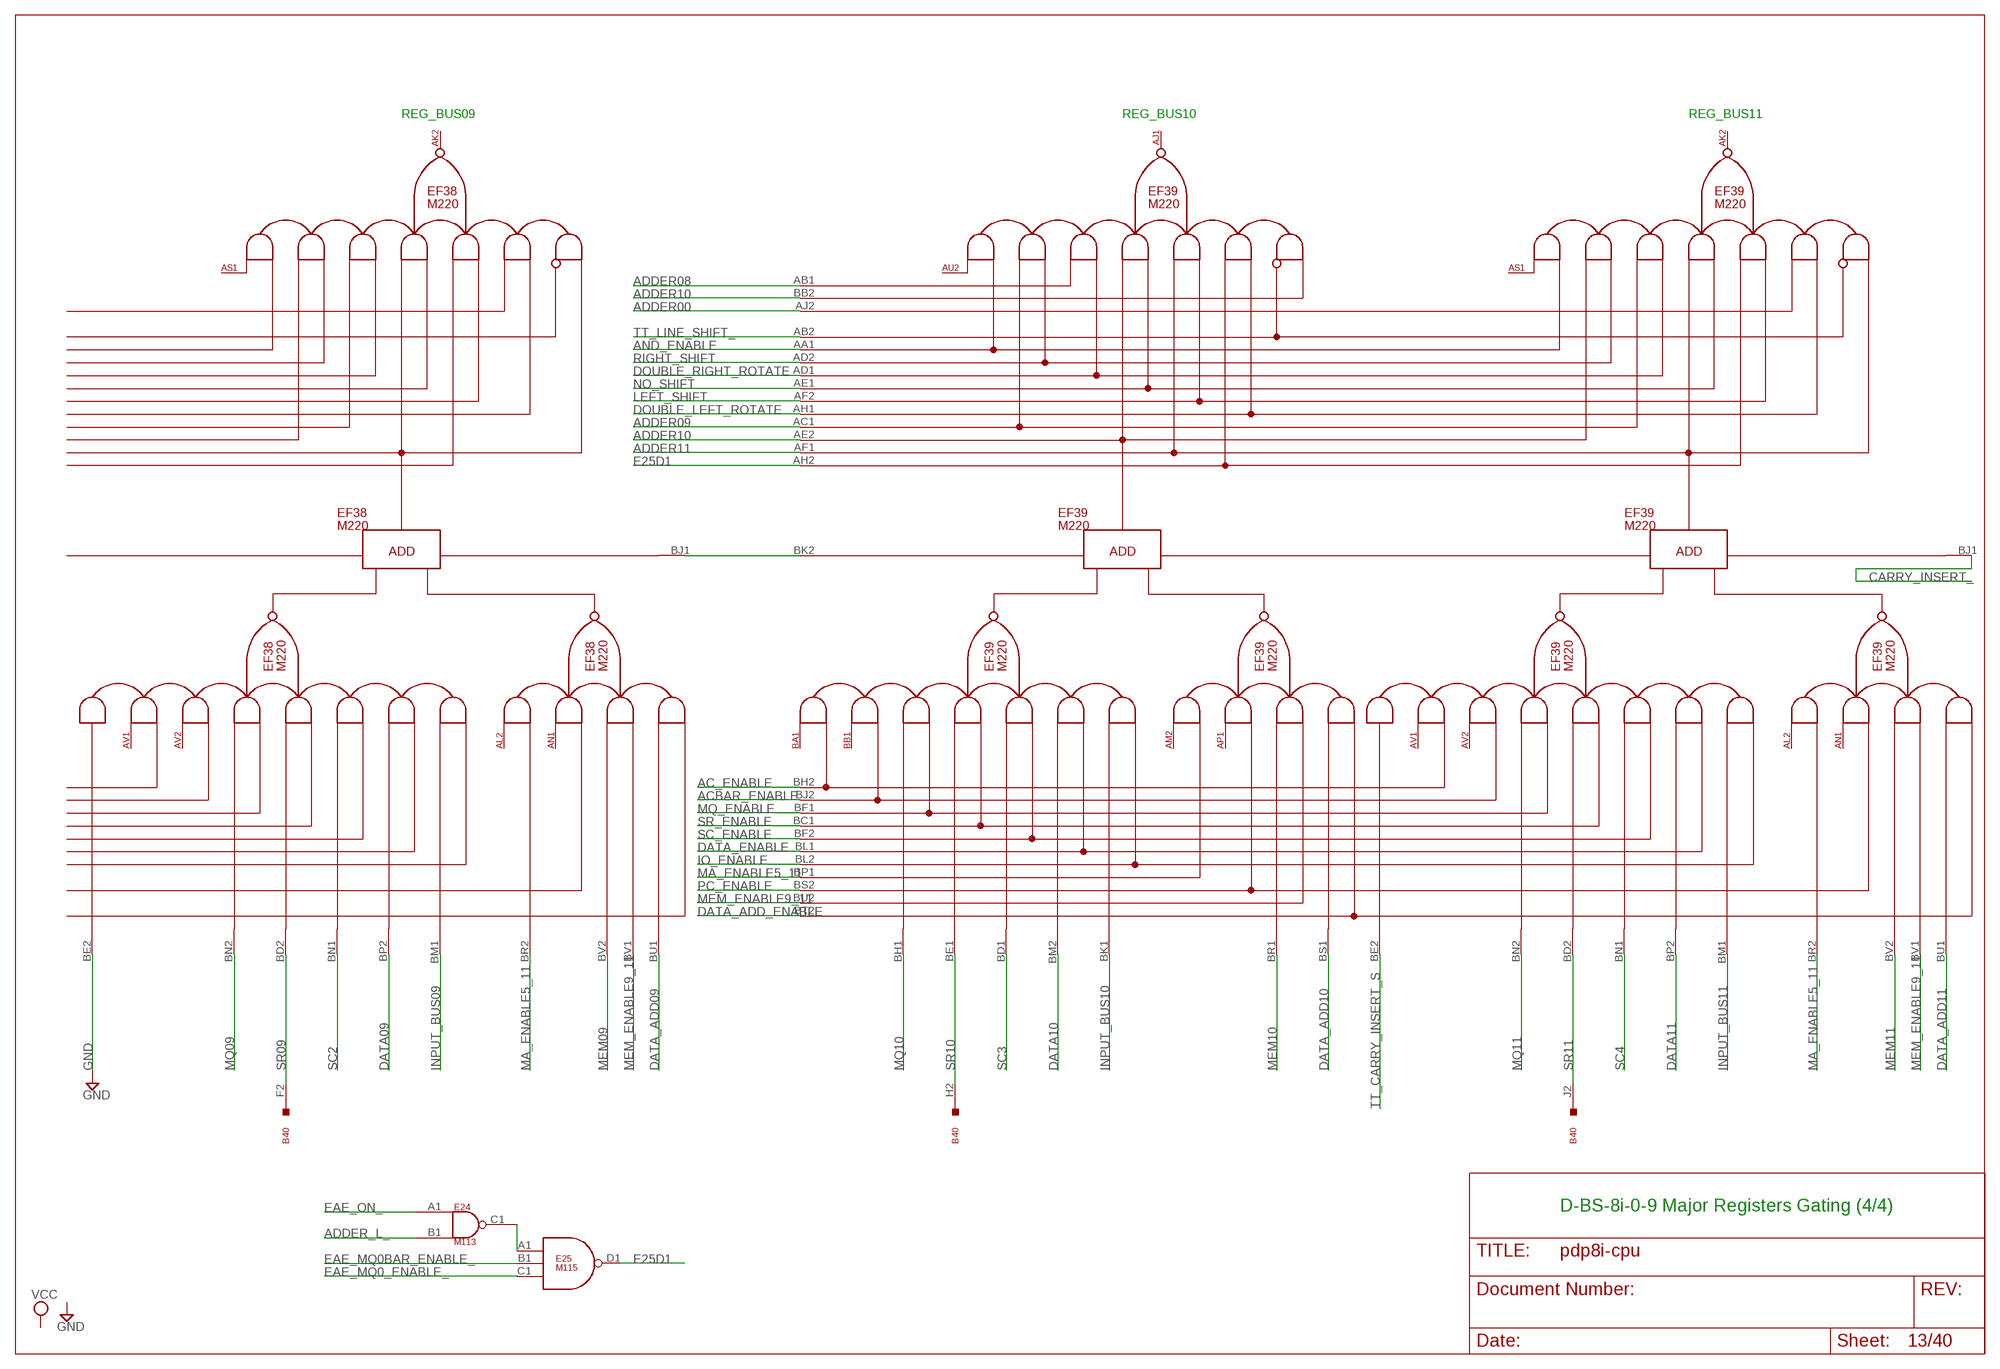
[diagram p12: schematic, sheet 13]
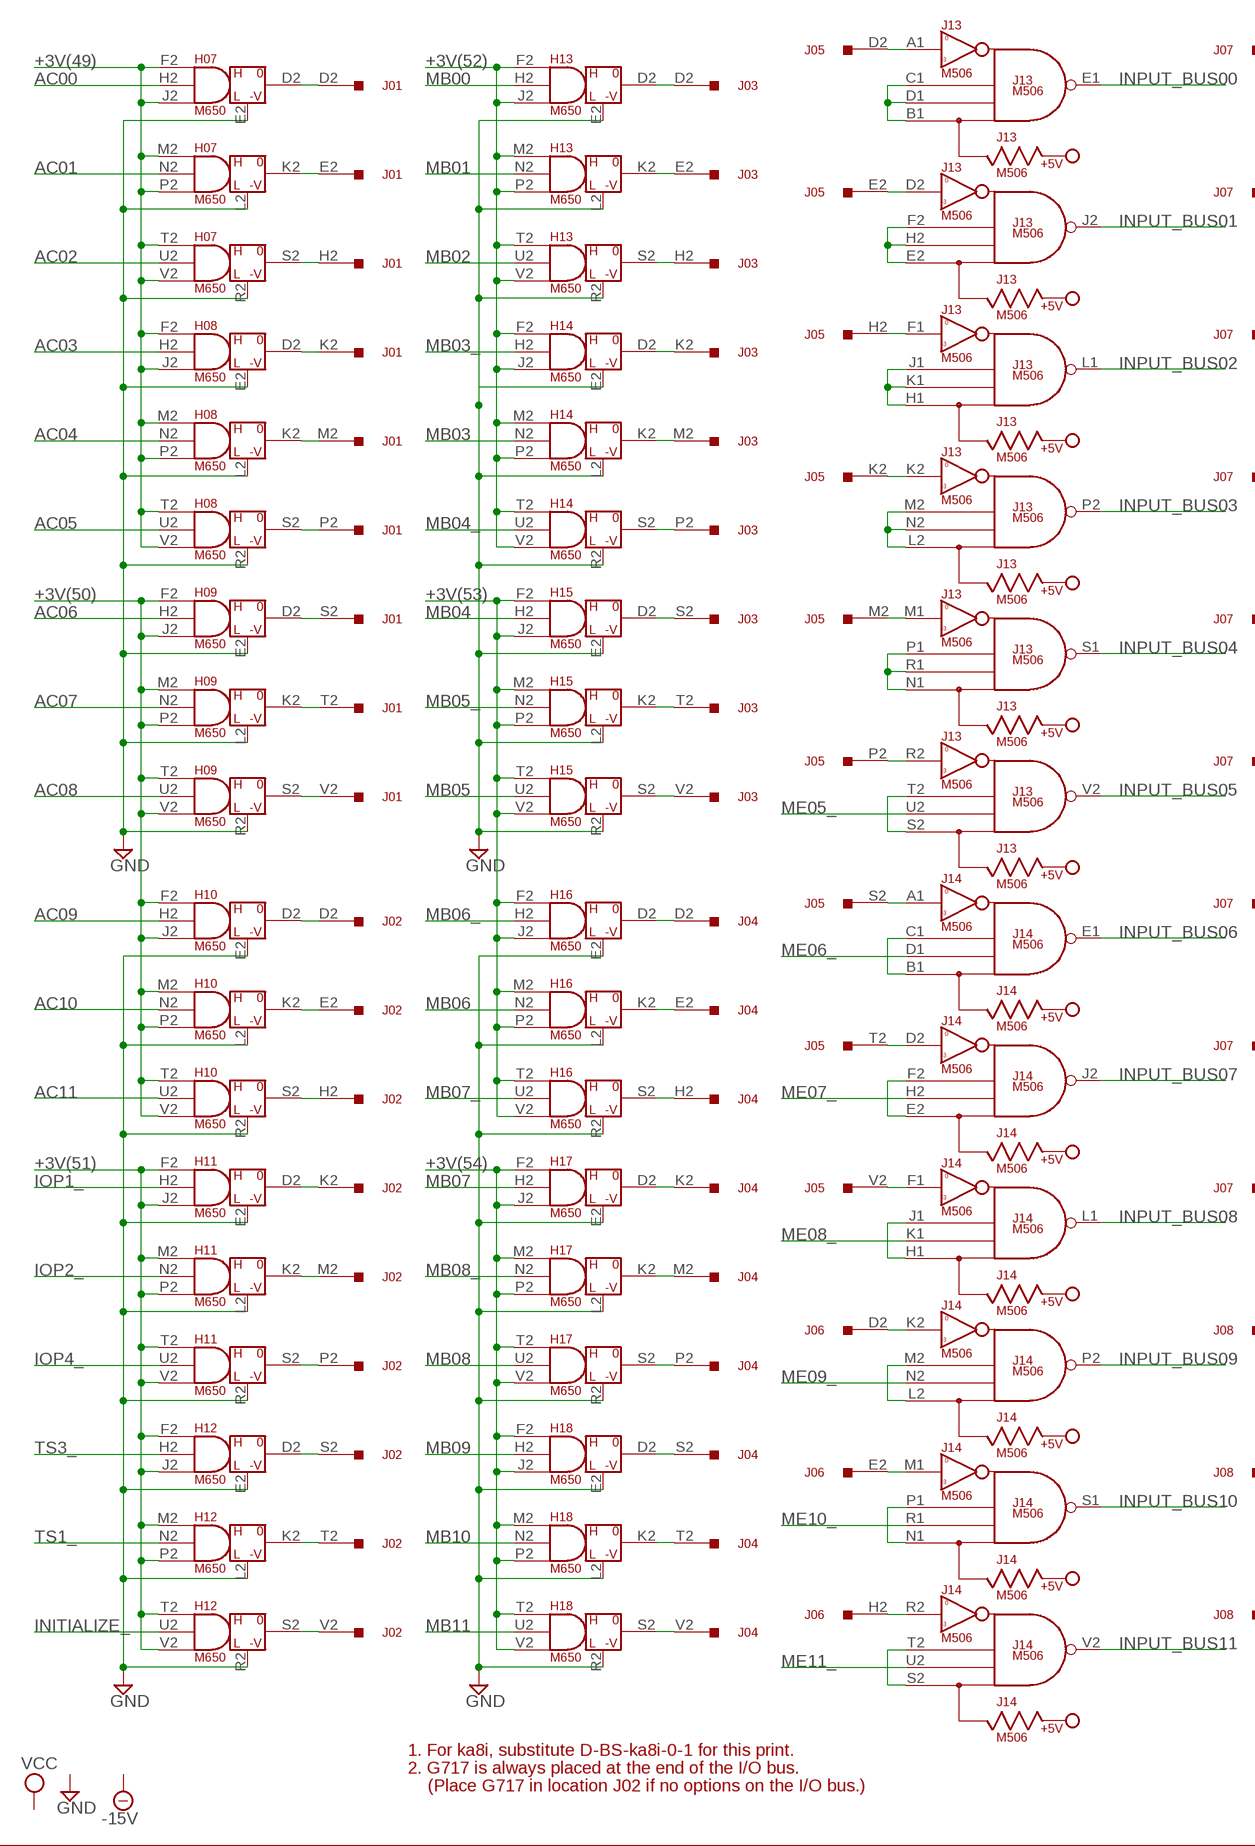
[diagram p13: schematic, sheet 14, part 1 of 2]
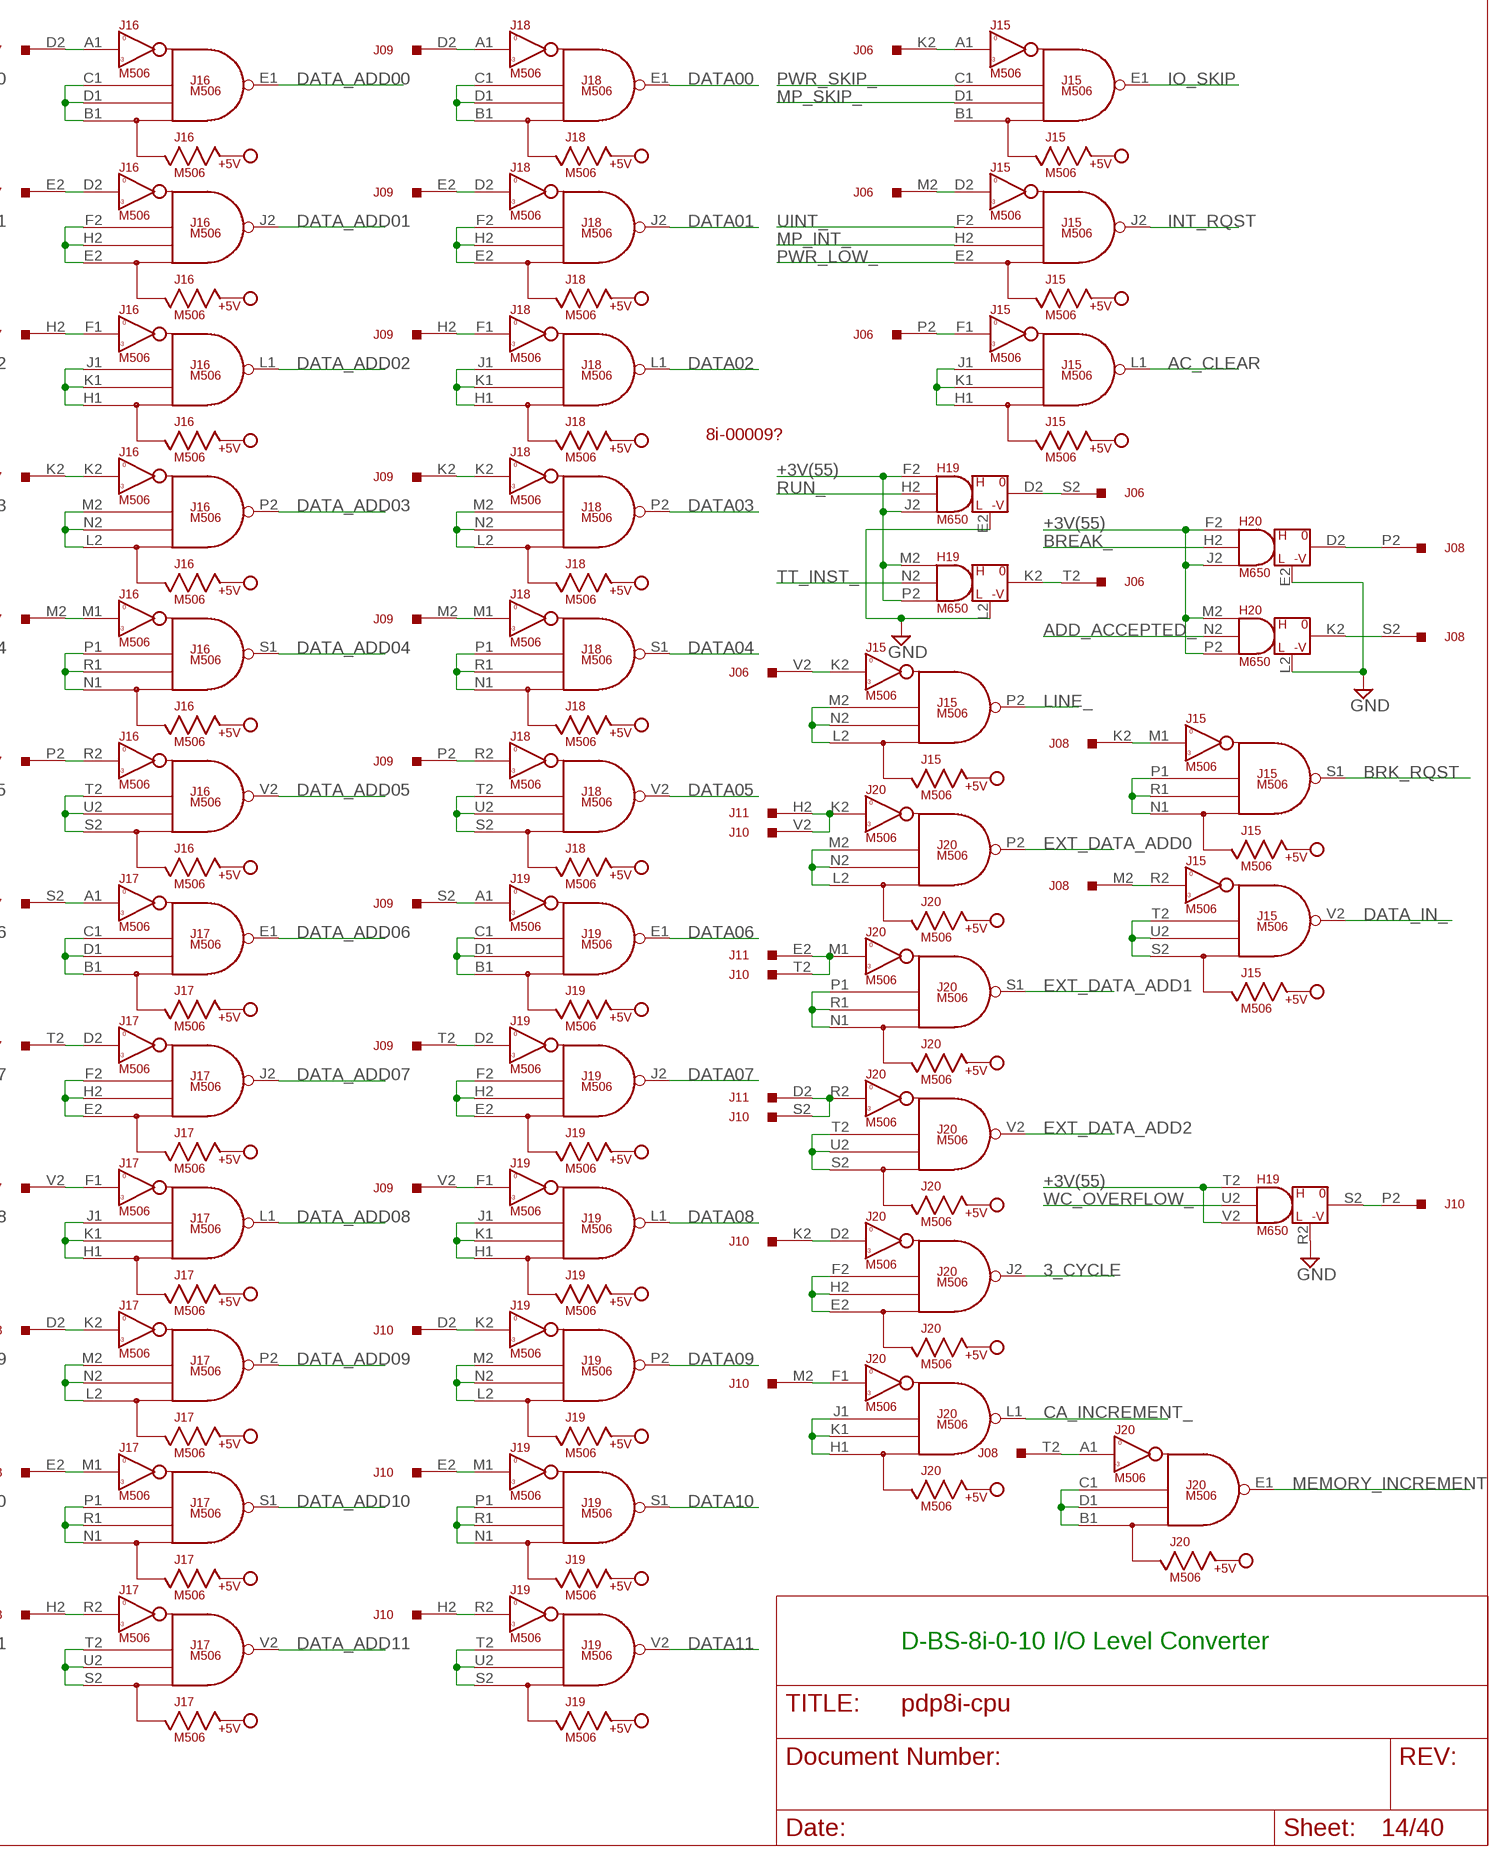
[diagram p14: schematic, sheet 14, part 2 of 2]
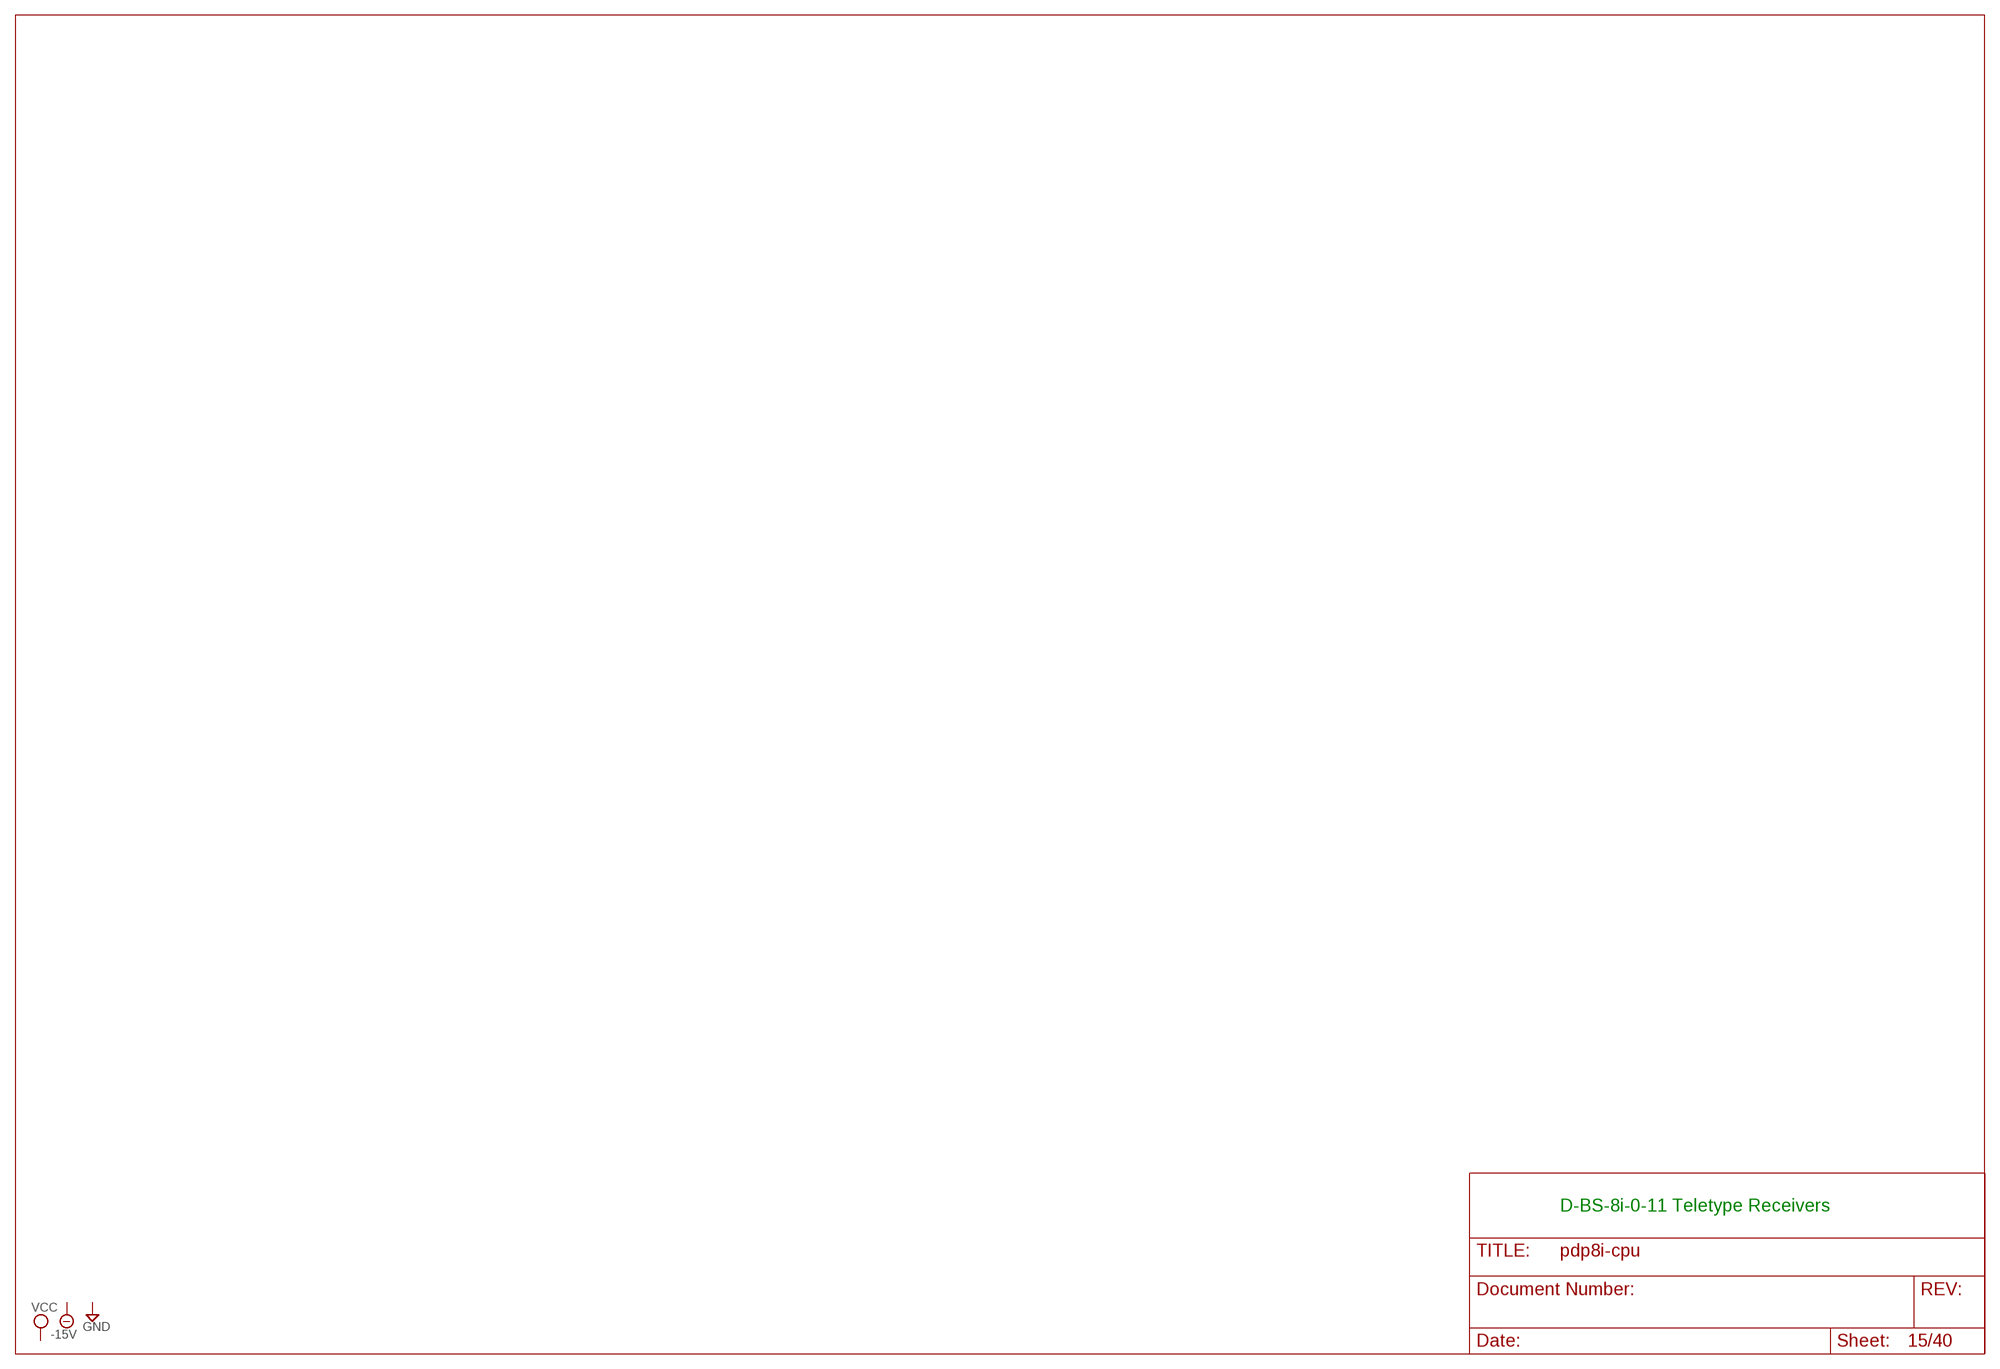
[diagram p15: schematic, sheet 15]
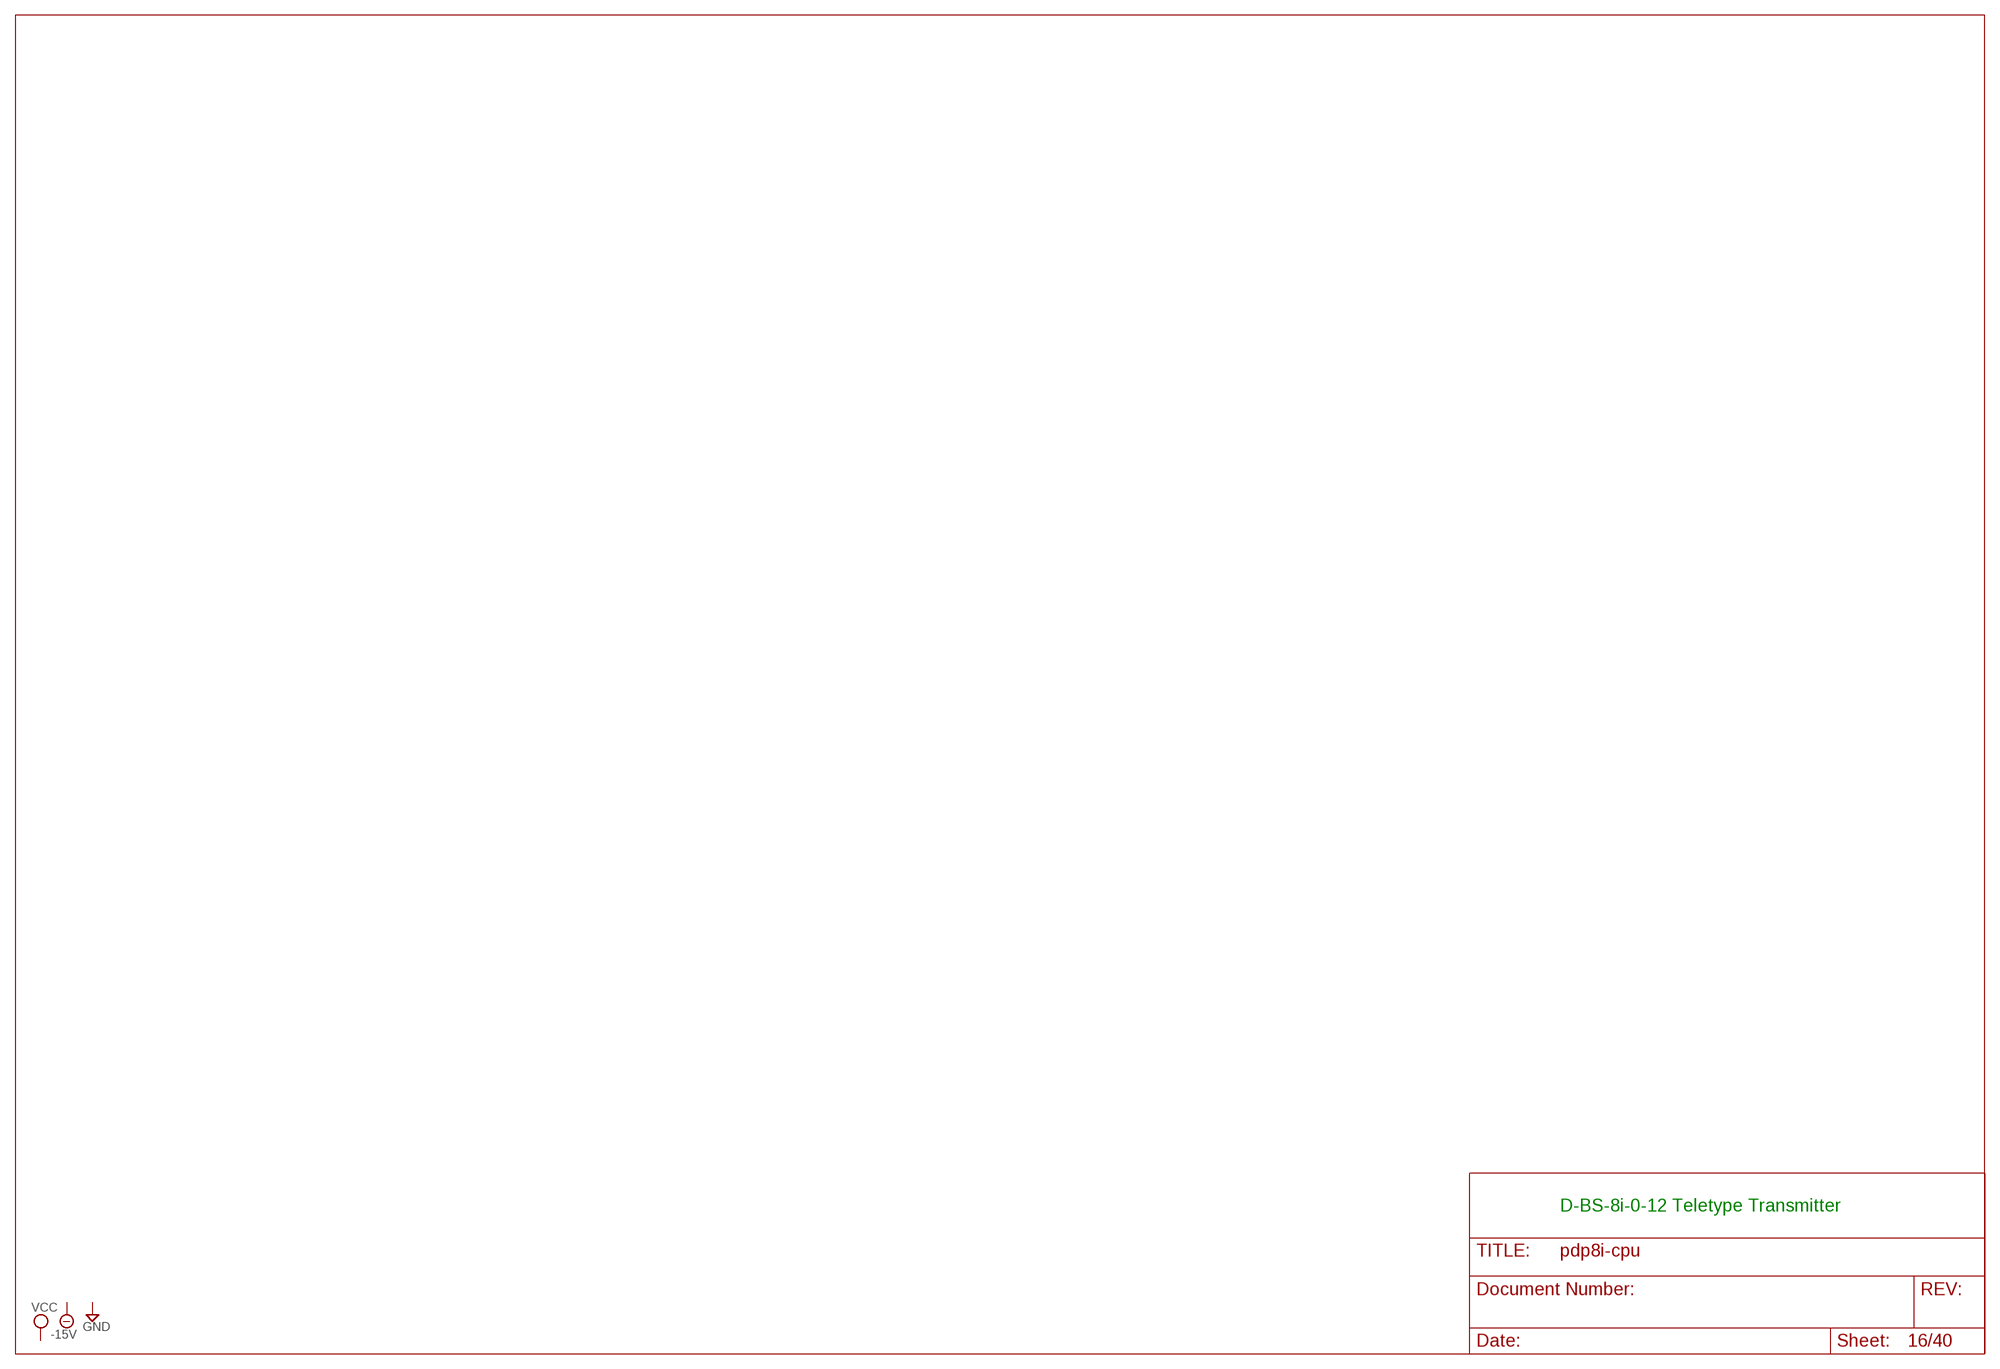
[diagram p16: schematic, sheet 16]
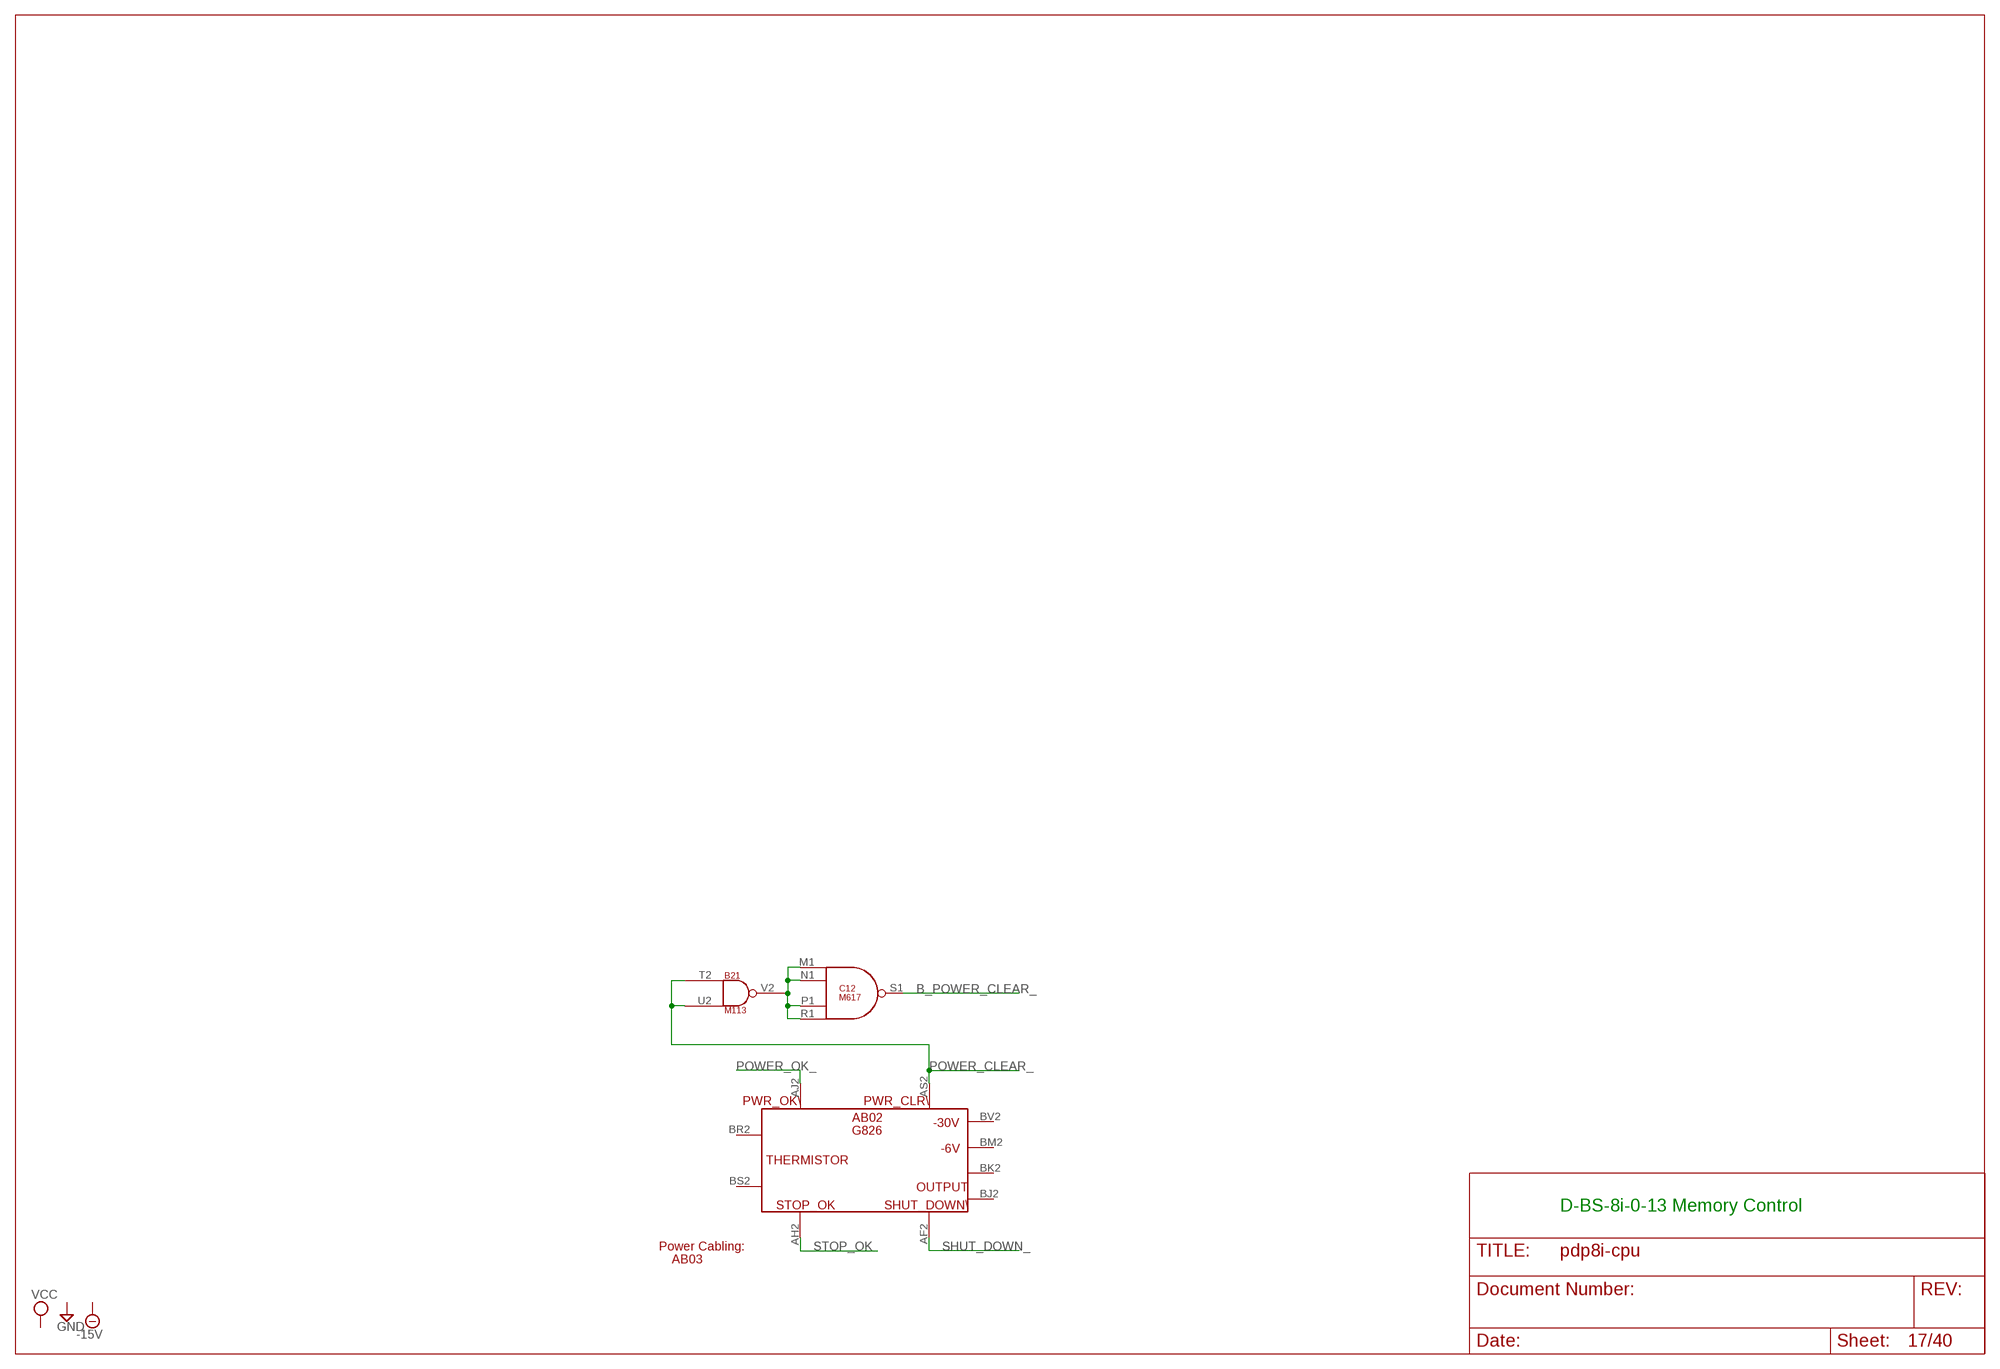
[diagram p17: schematic, sheet 17]
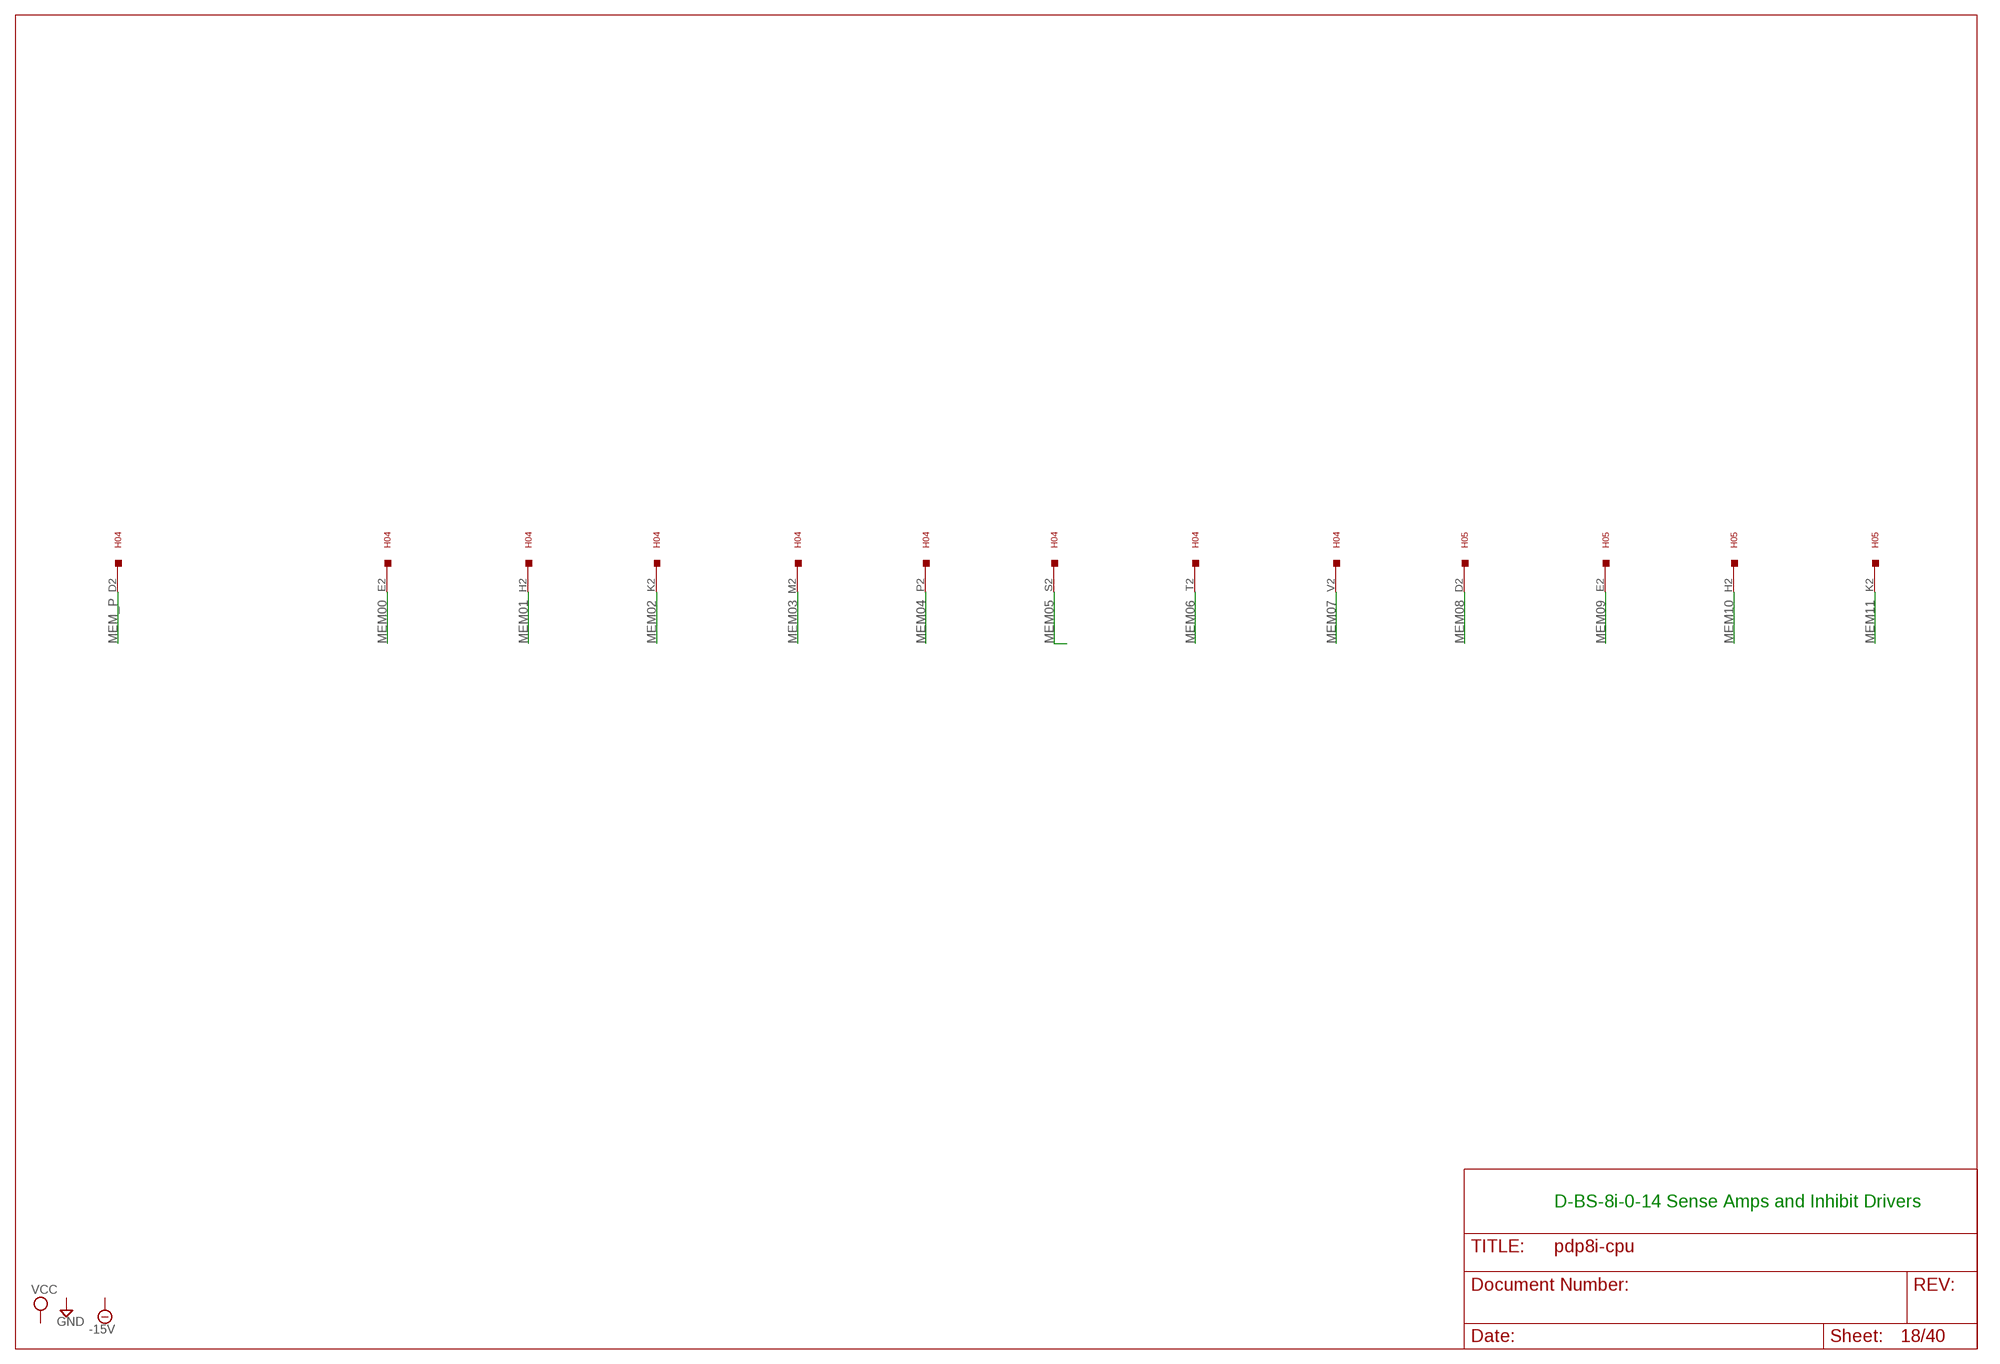
[diagram p18: schematic, sheet 18]
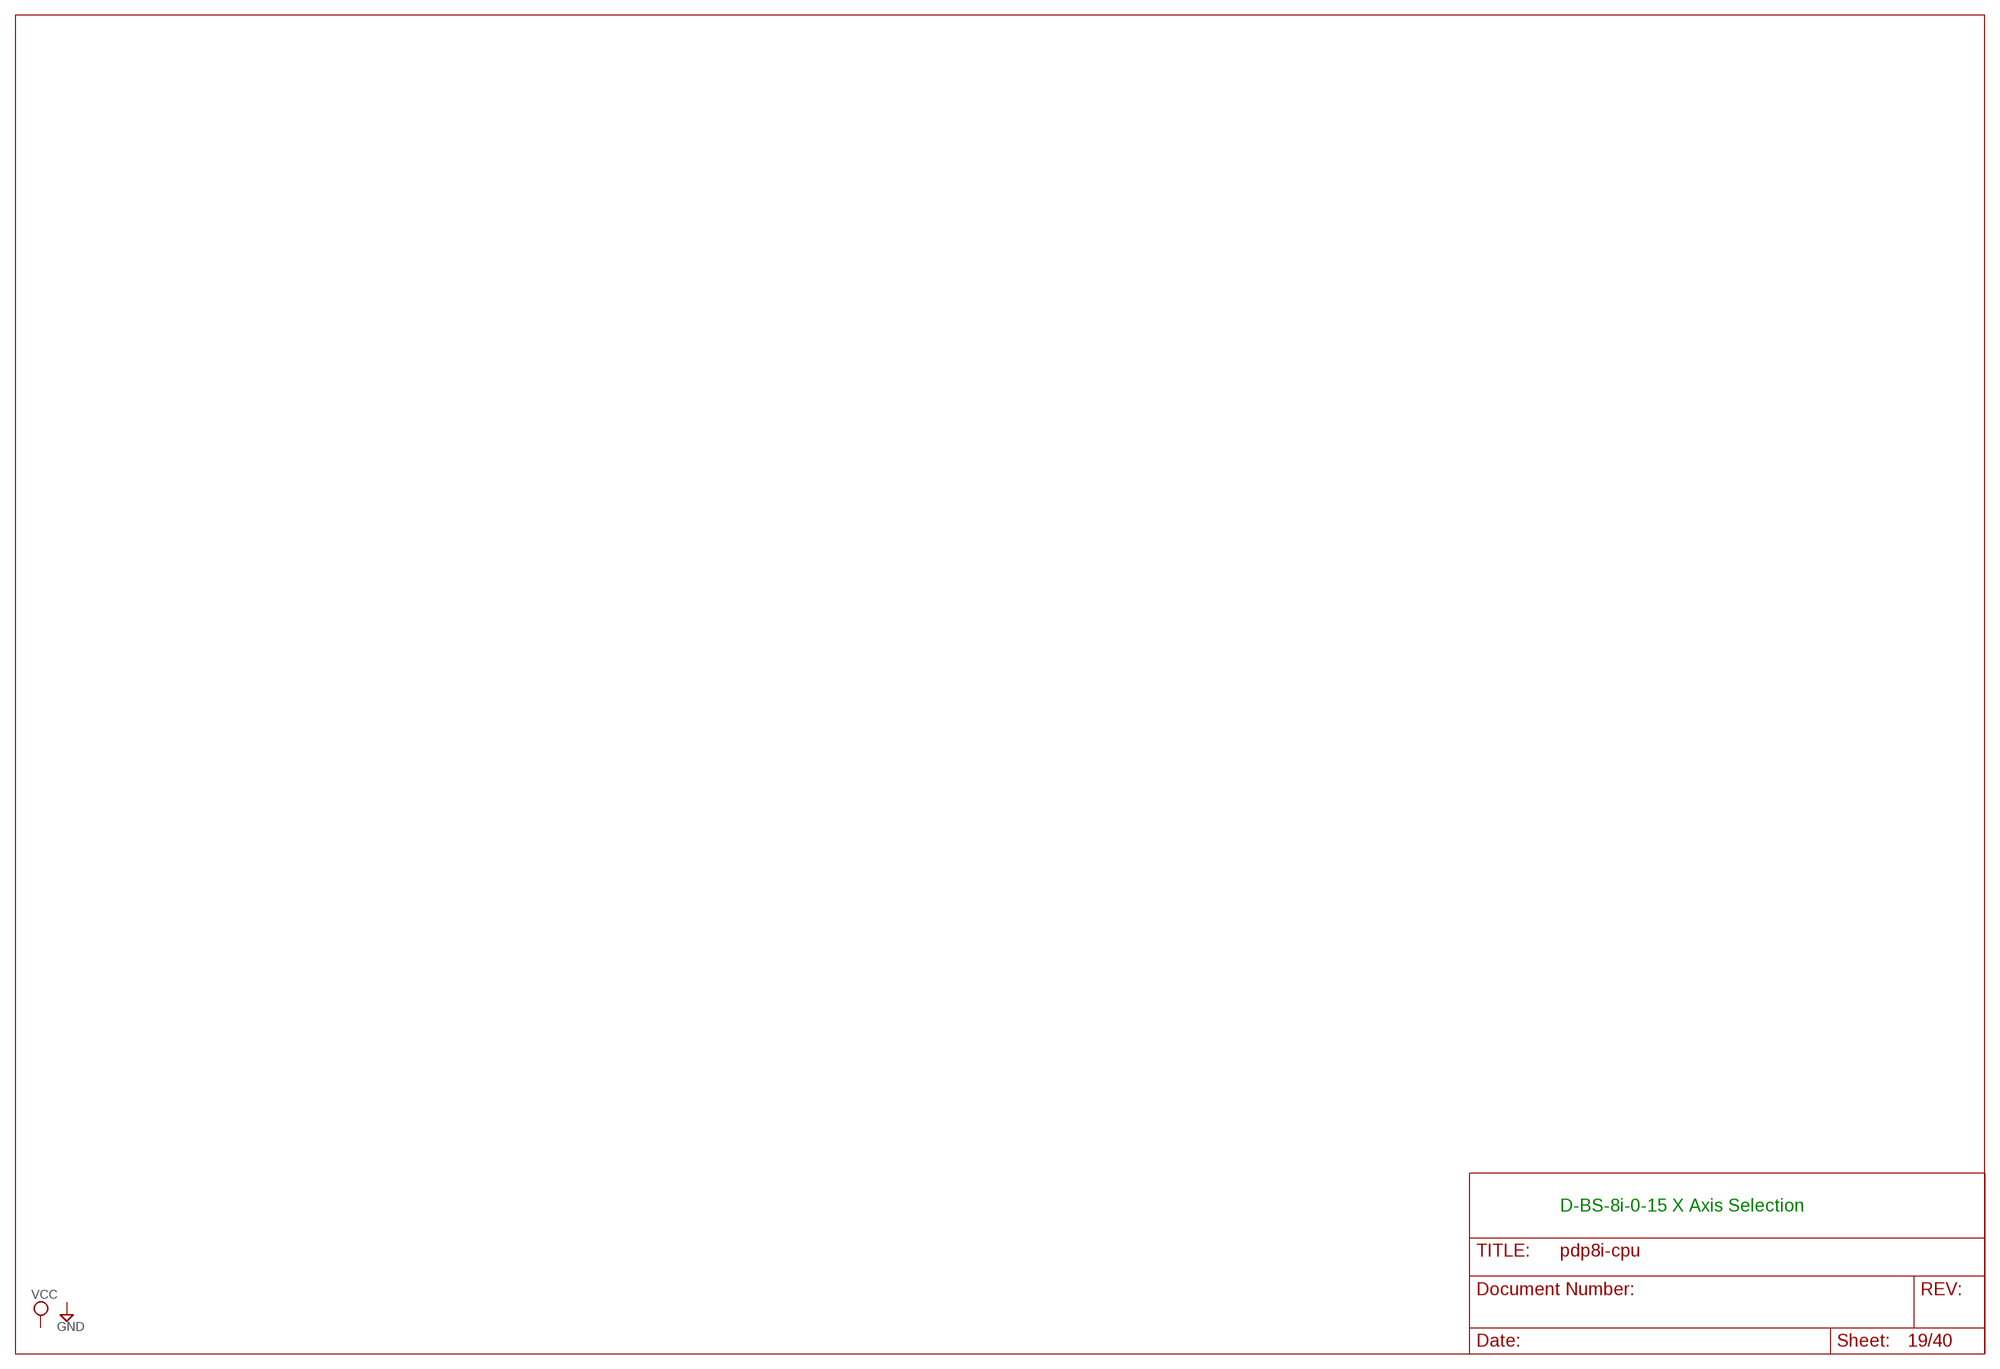
[diagram p19: schematic, sheet 19]
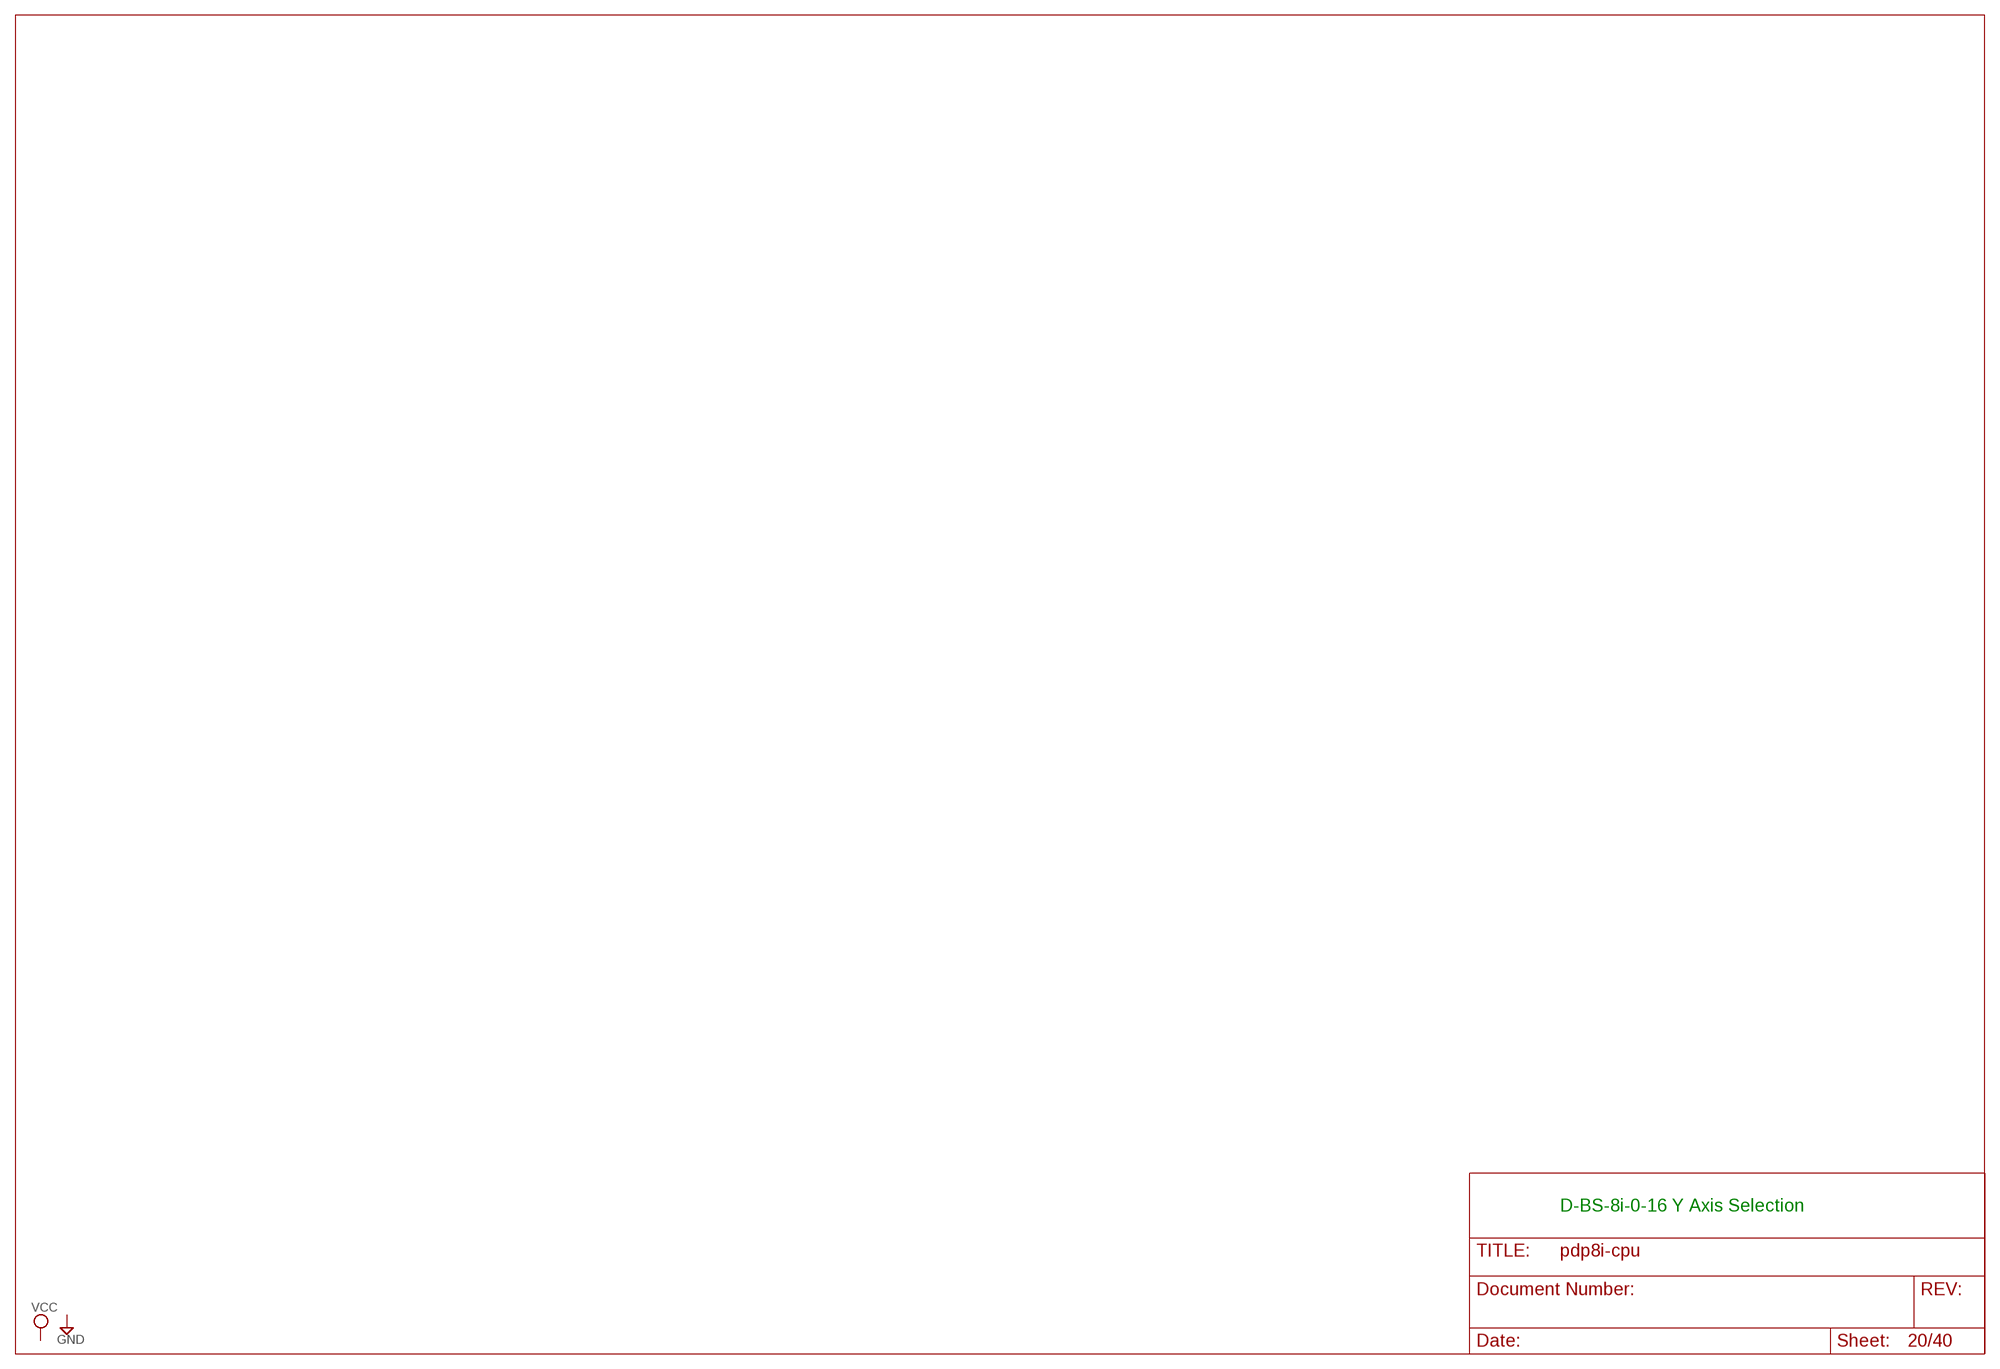
[diagram p20: schematic, sheet 20]
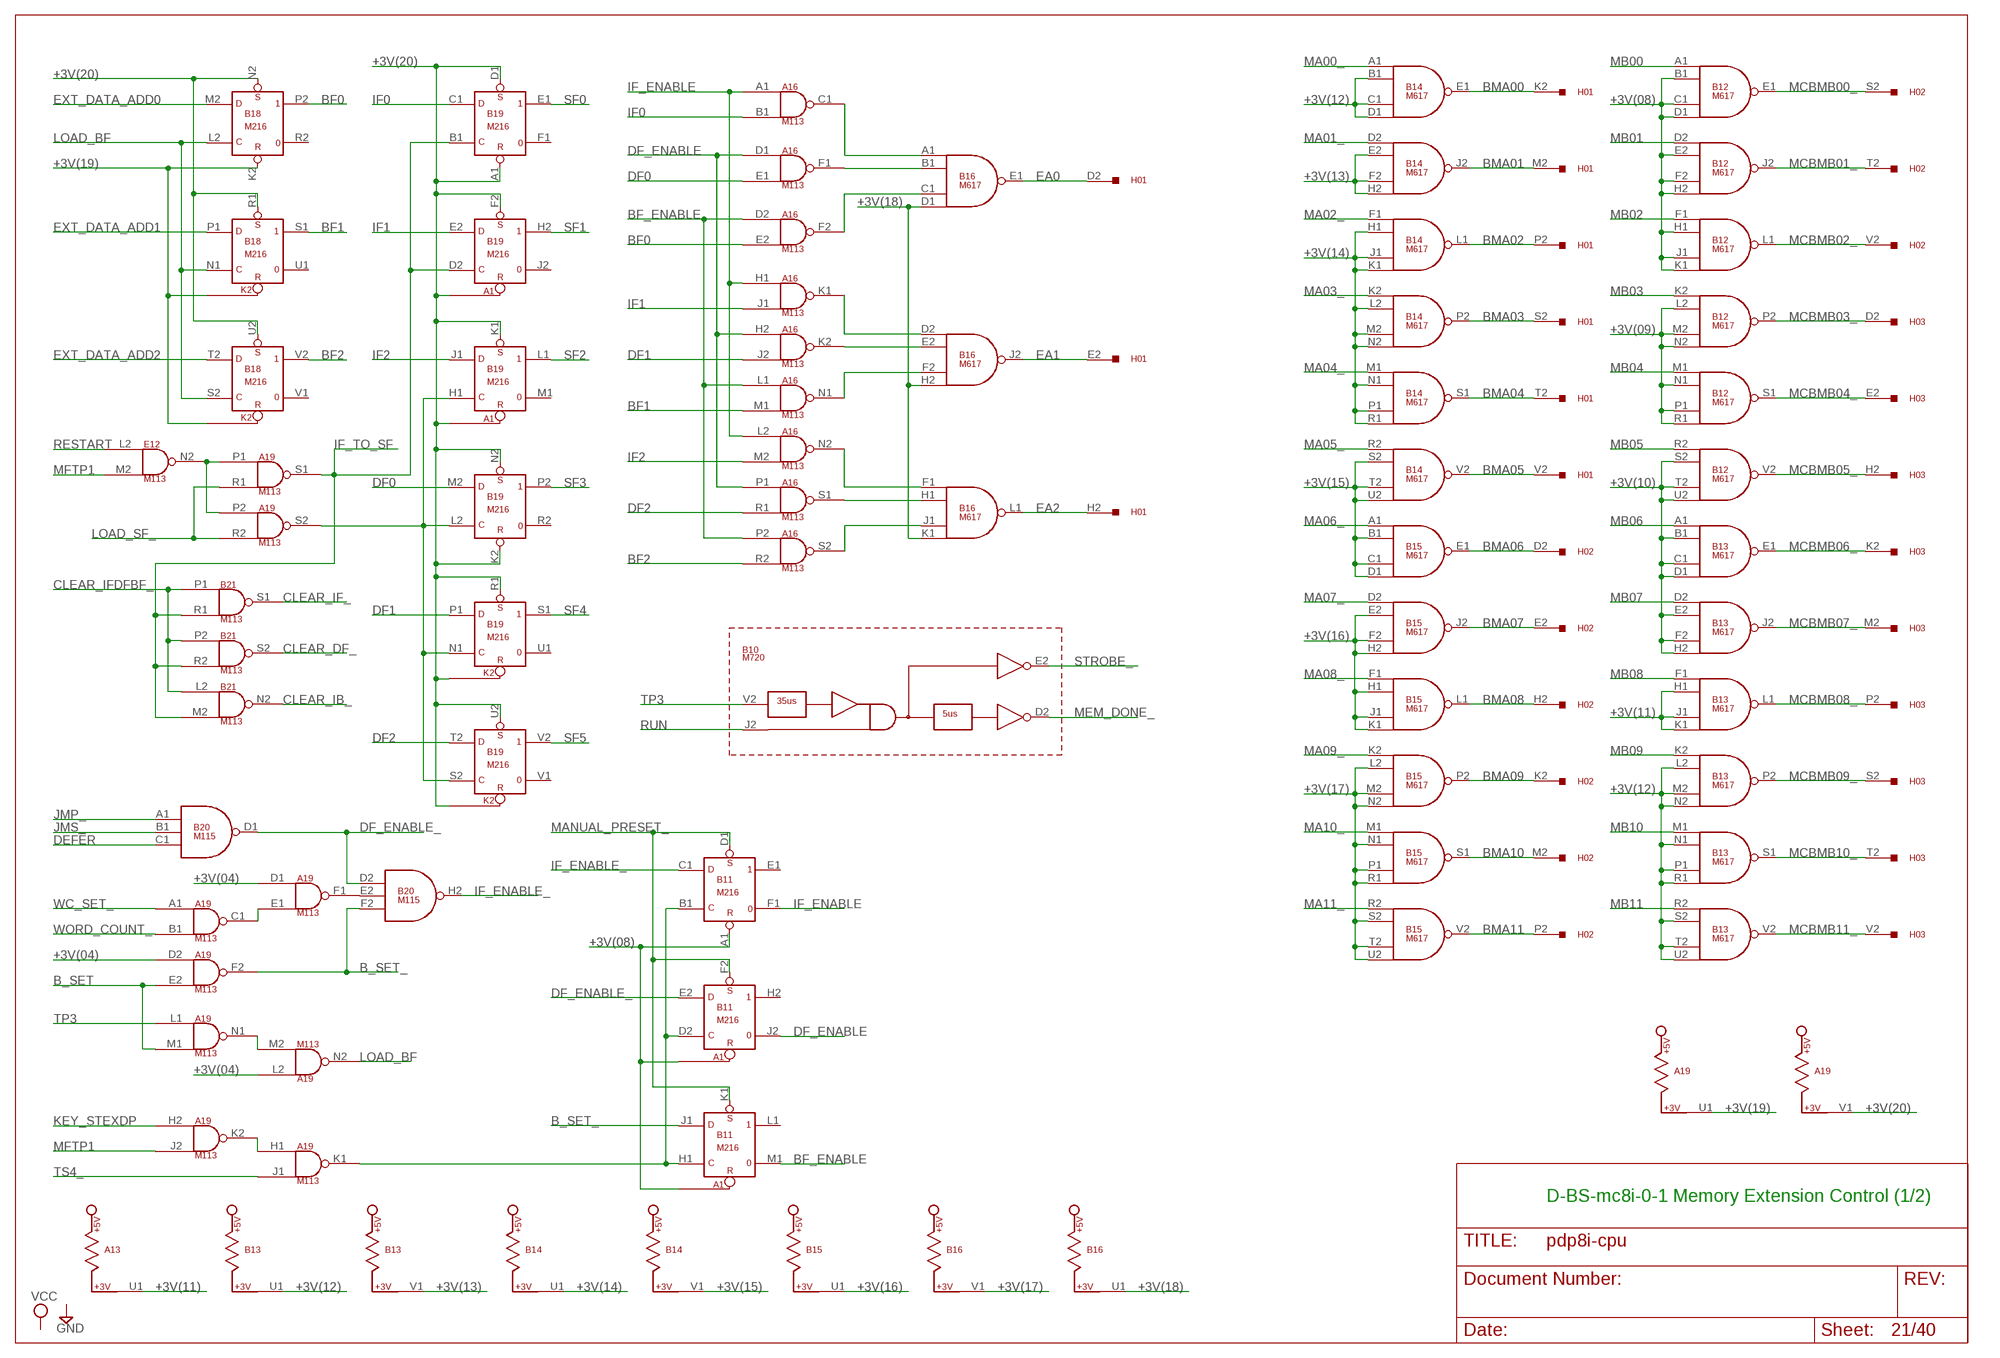
[diagram p21: schematic, sheet 21]
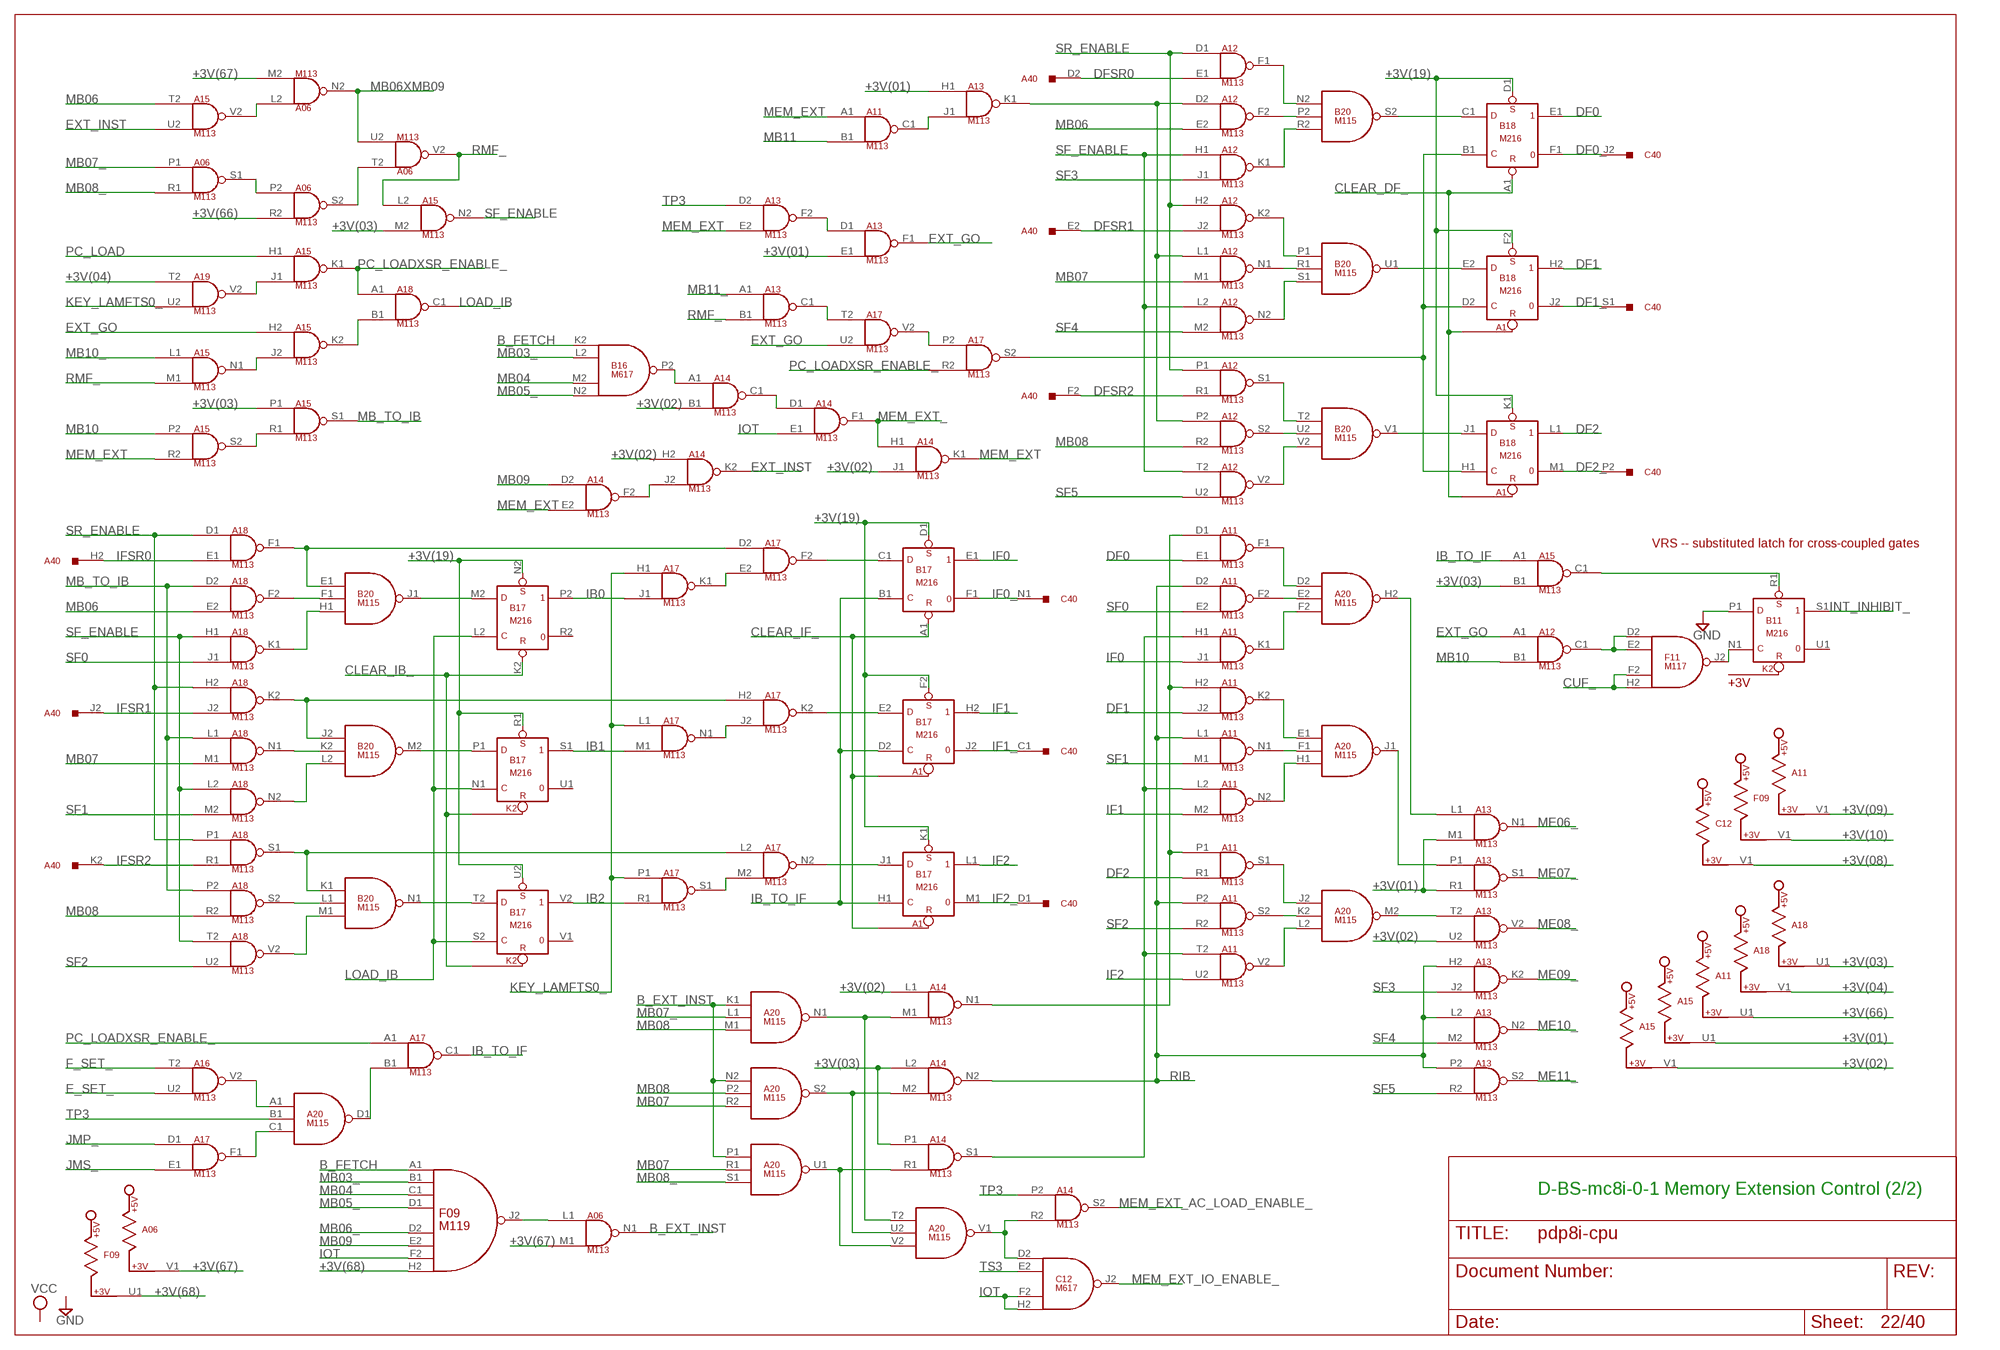
[diagram p22: schematic, sheet 22]
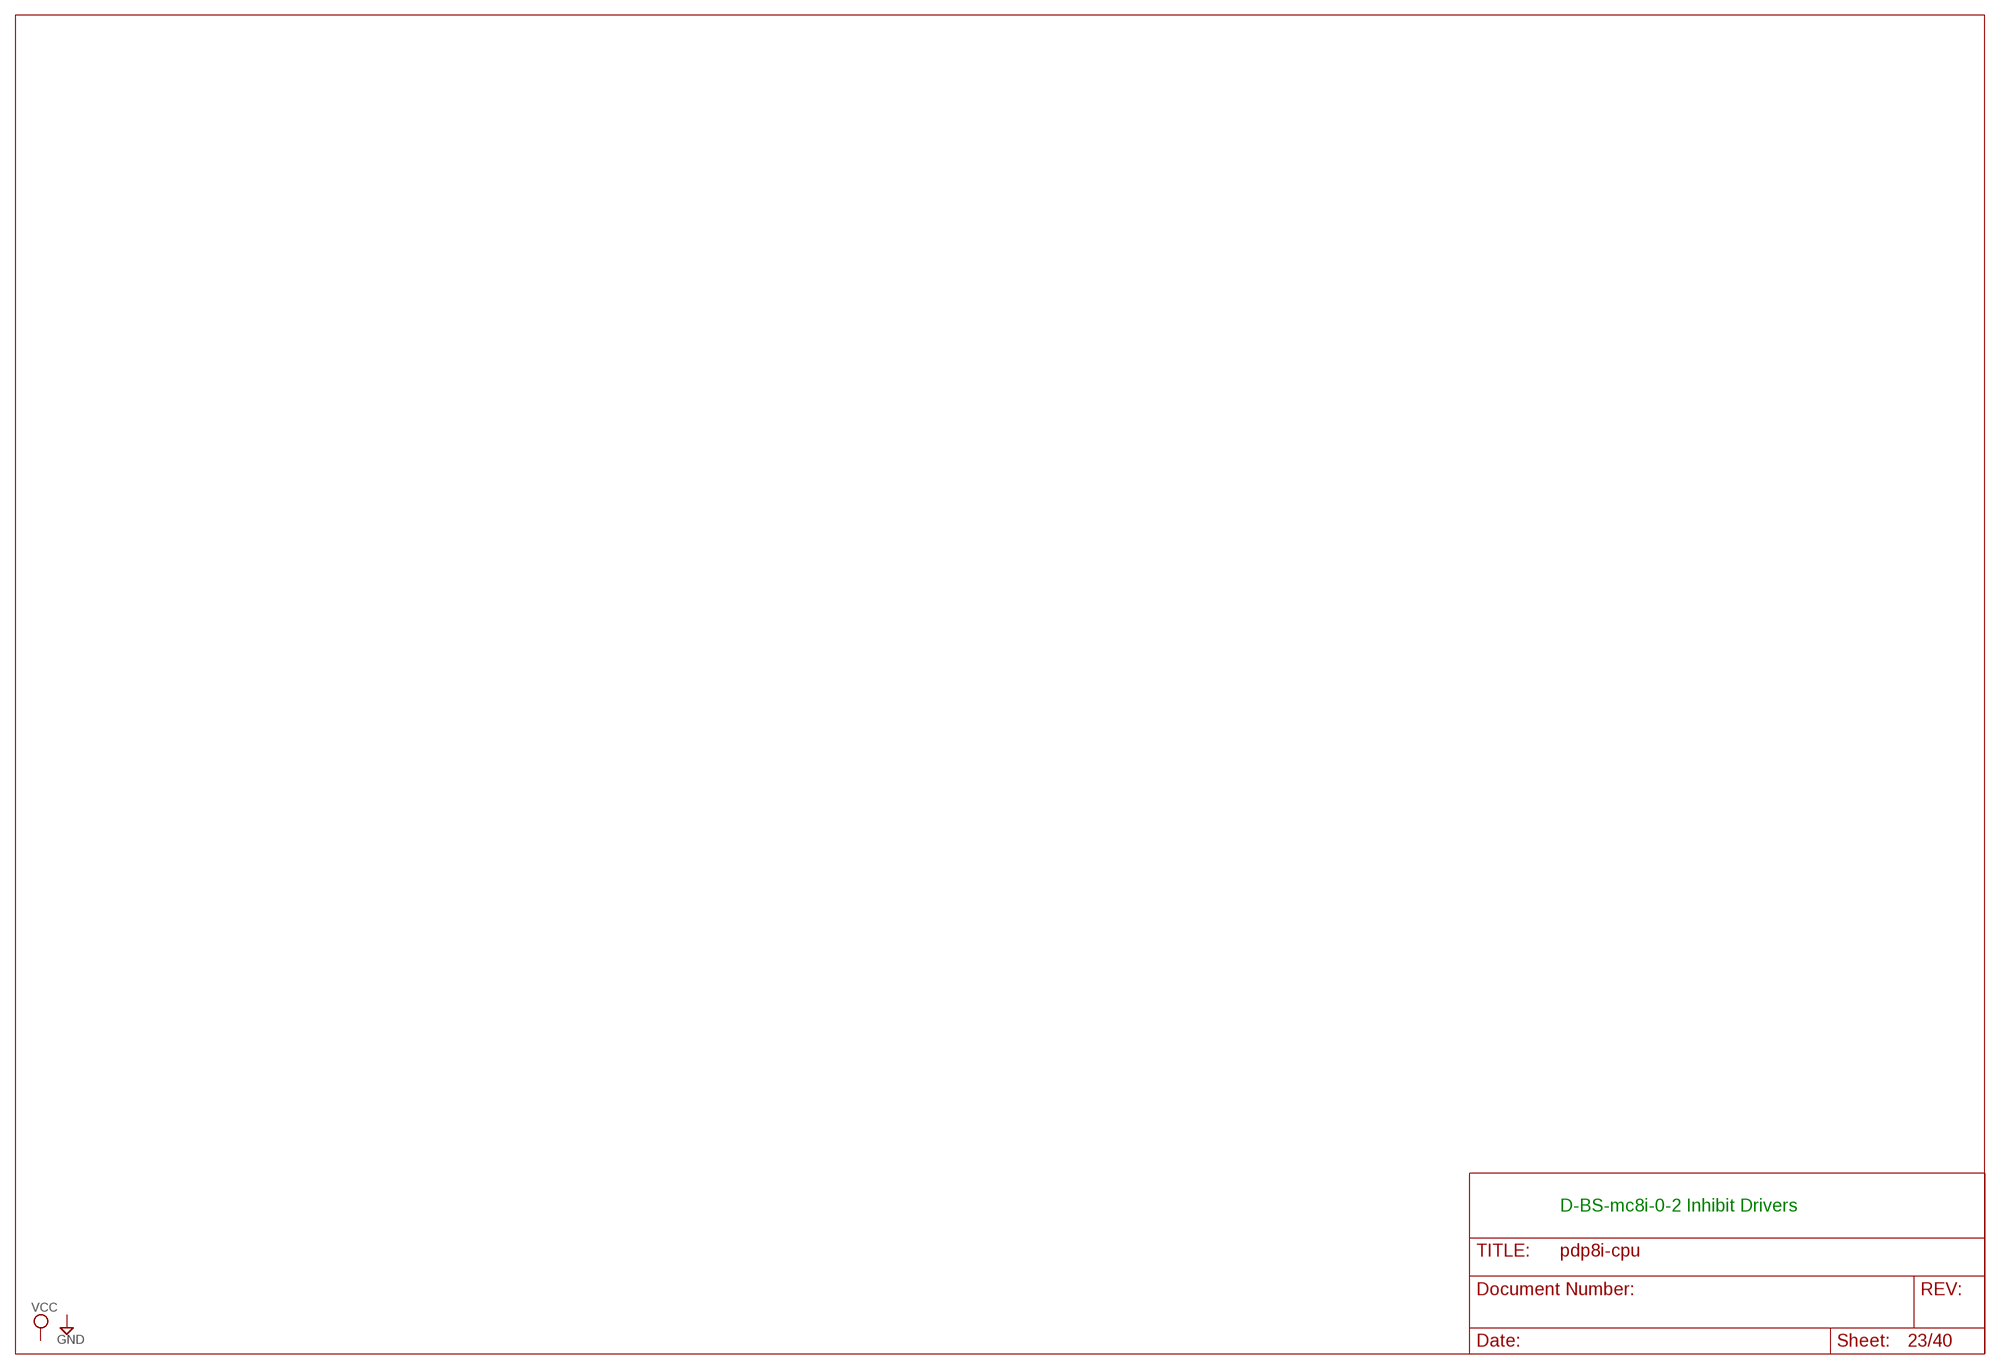
[diagram p23: schematic, sheet 23]
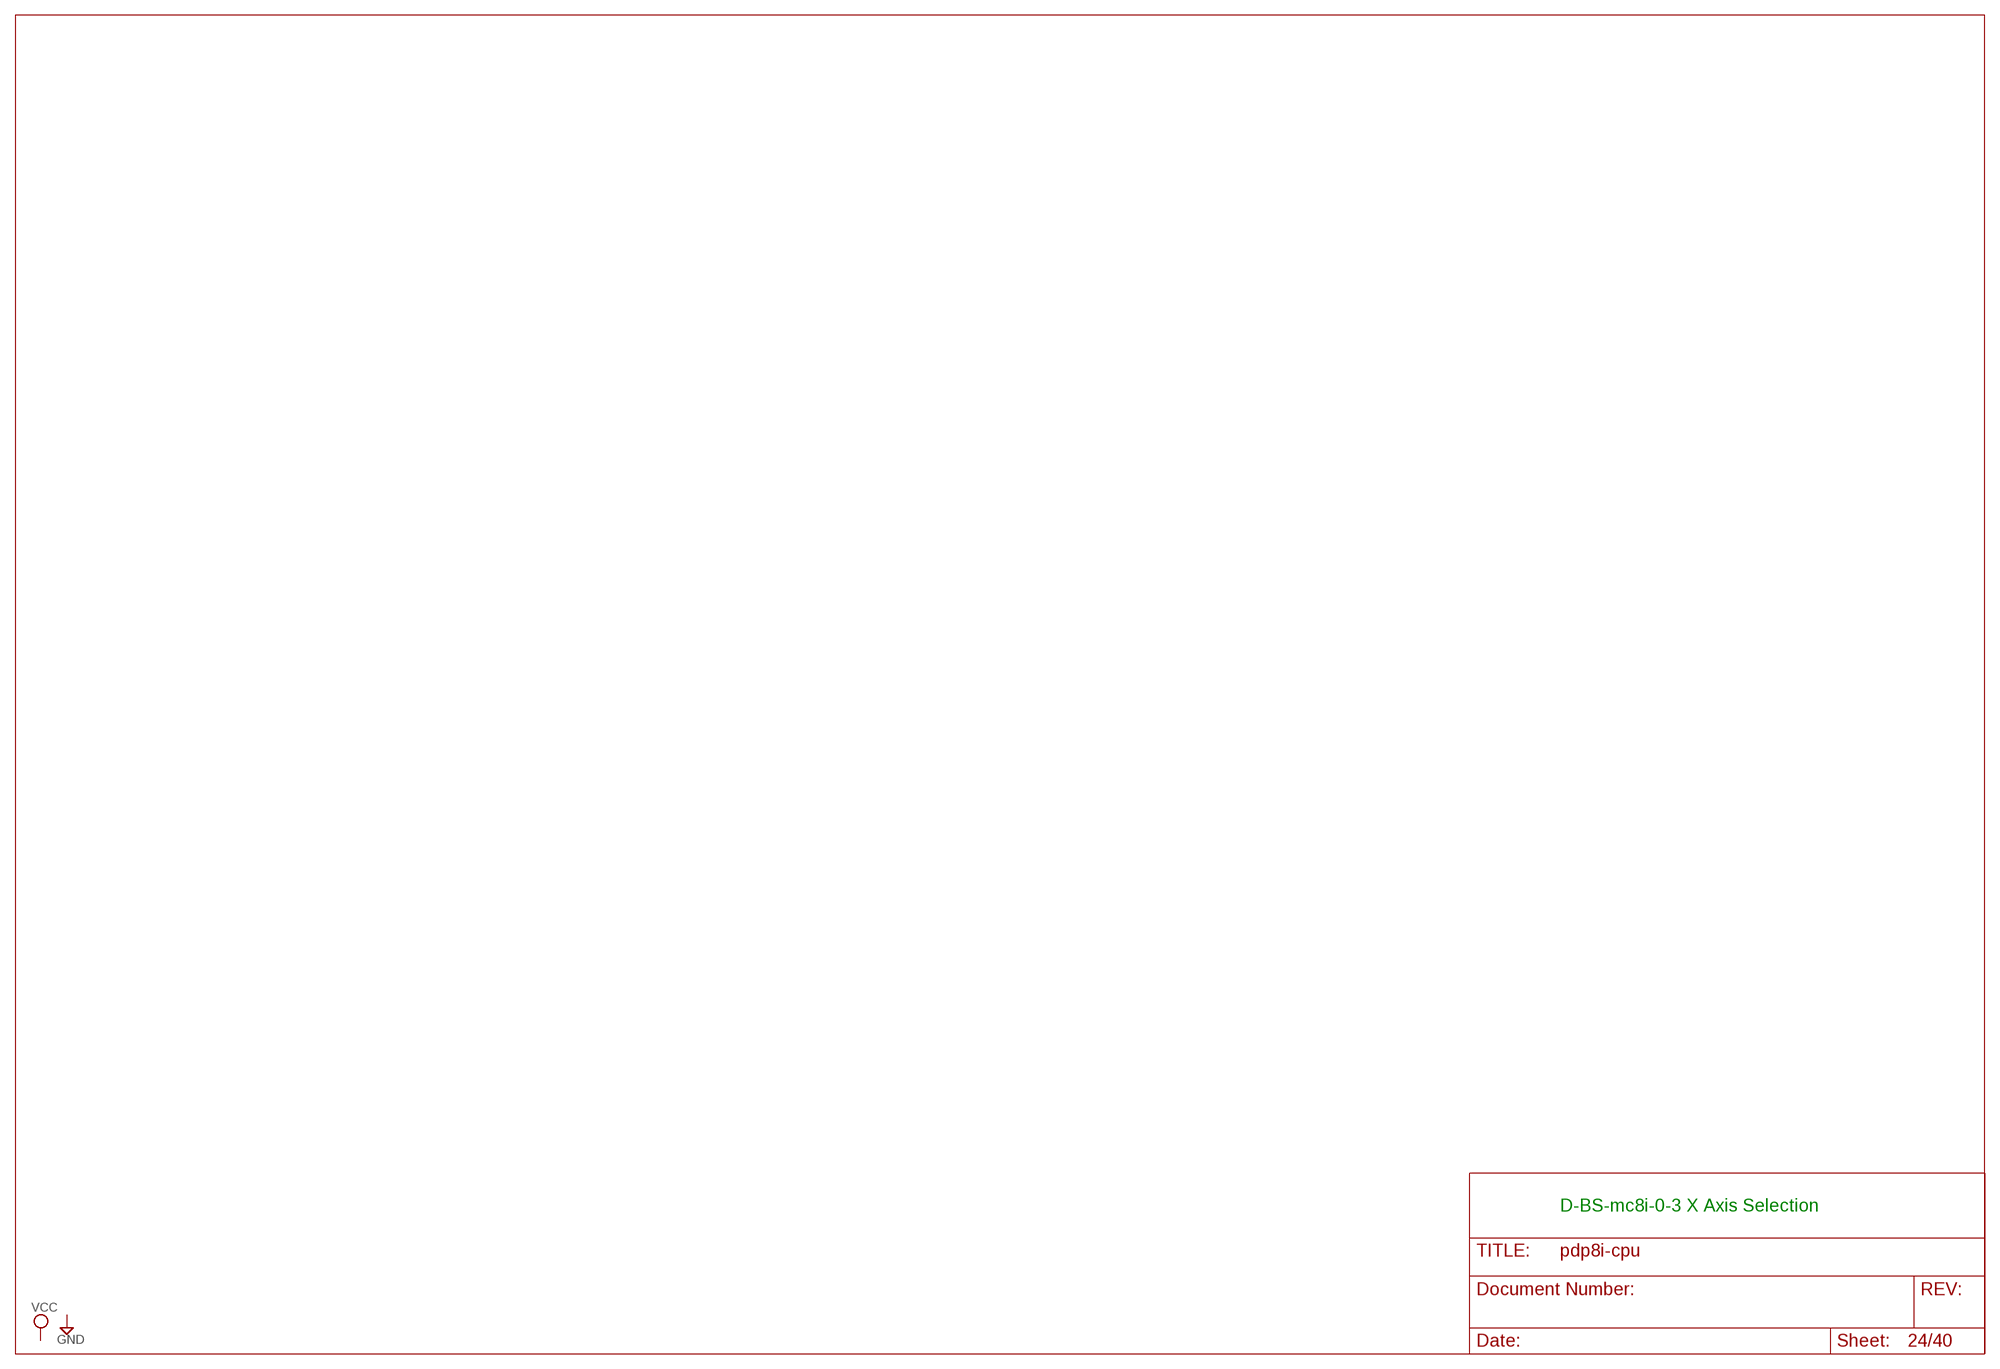
[diagram p24: schematic, sheet 24]
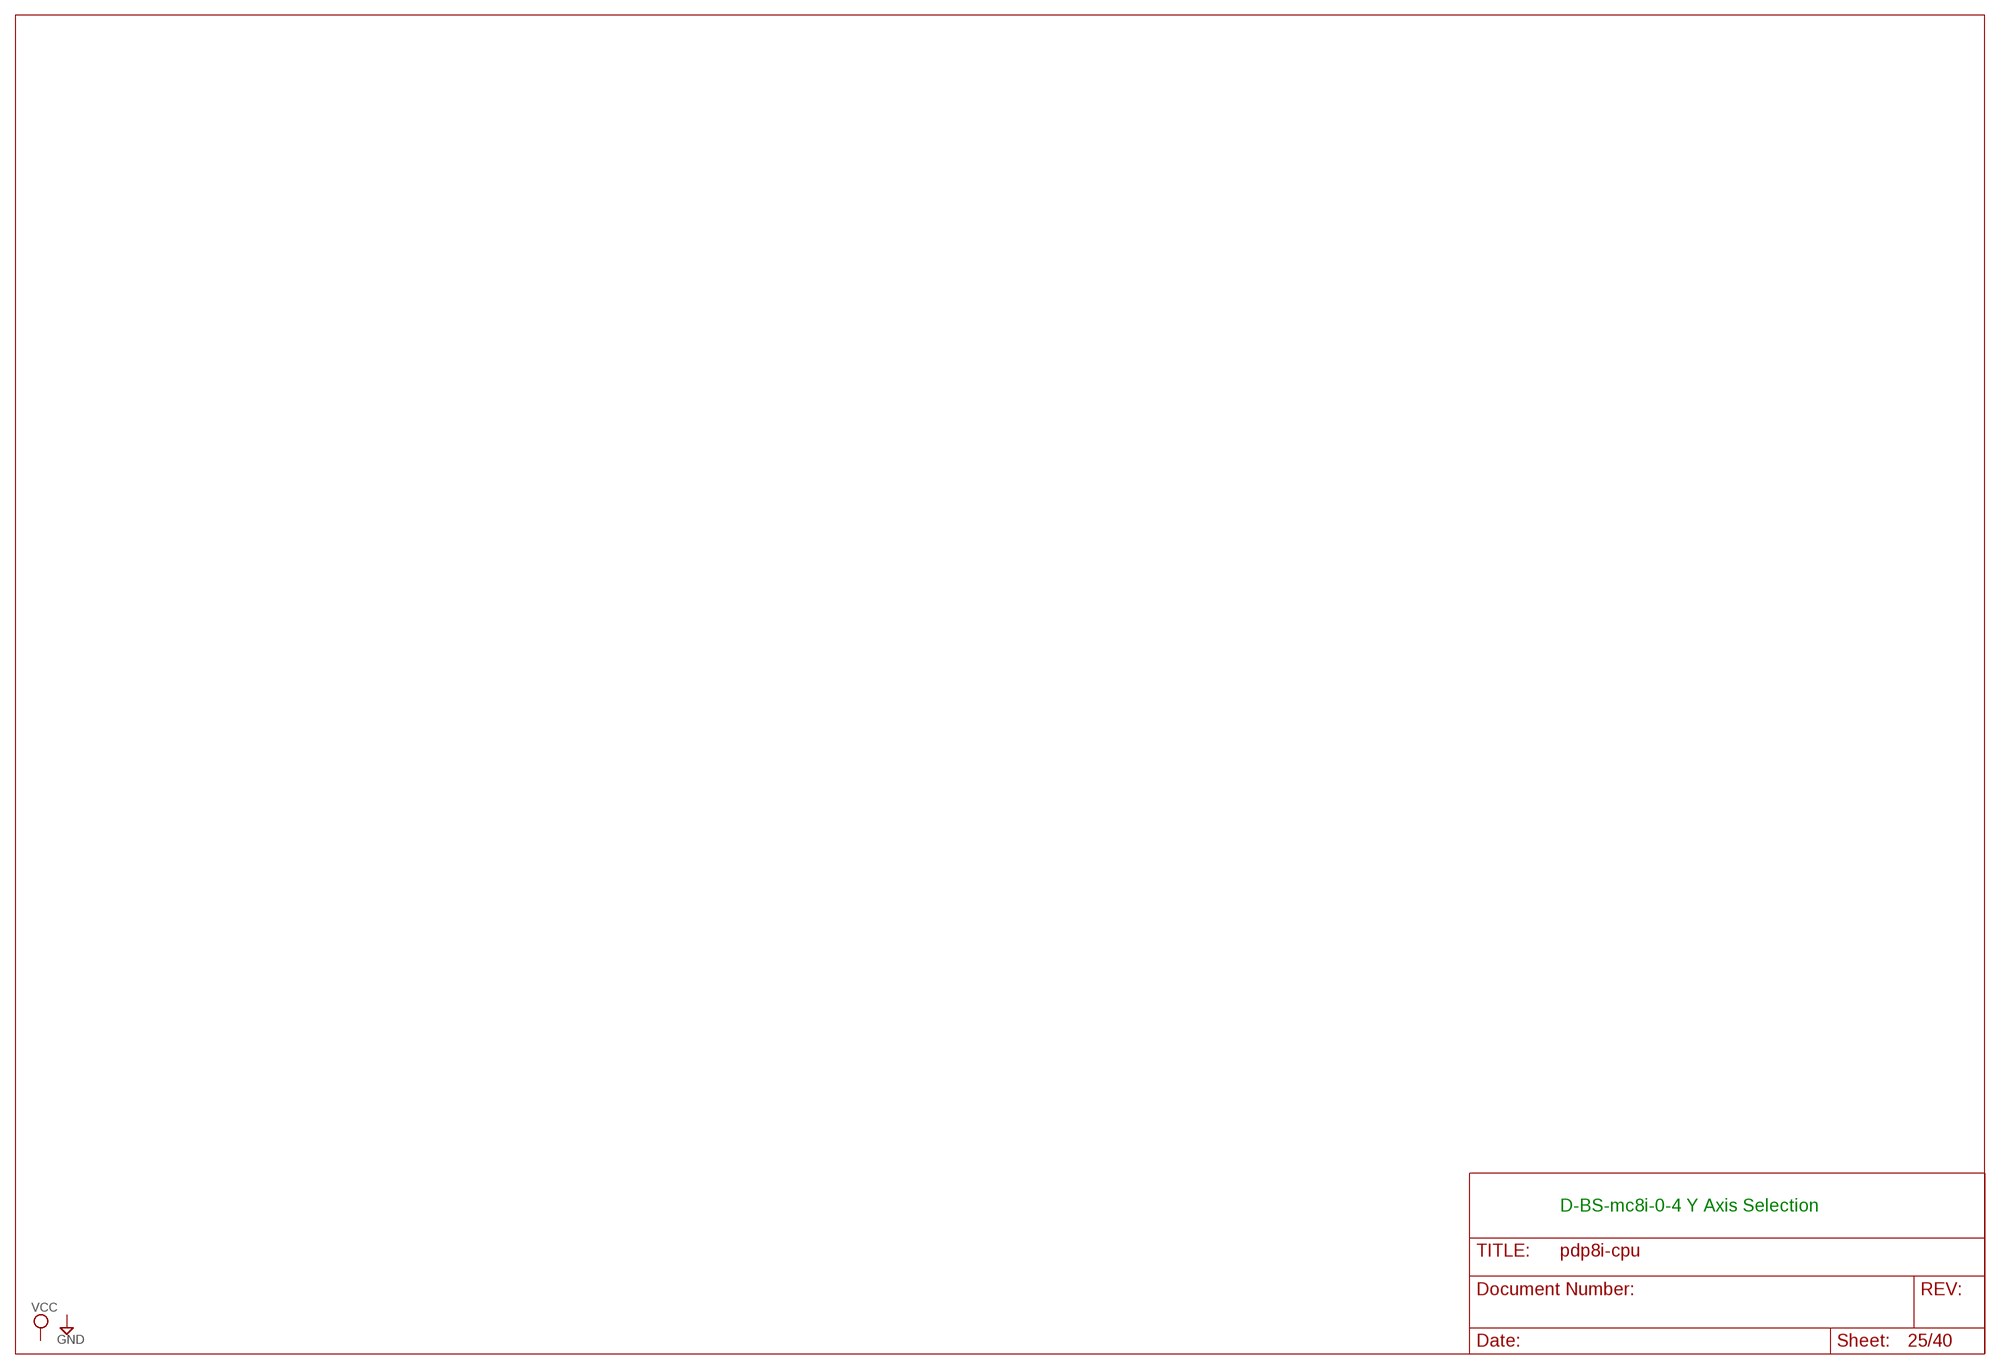
[diagram p25: schematic, sheet 25]
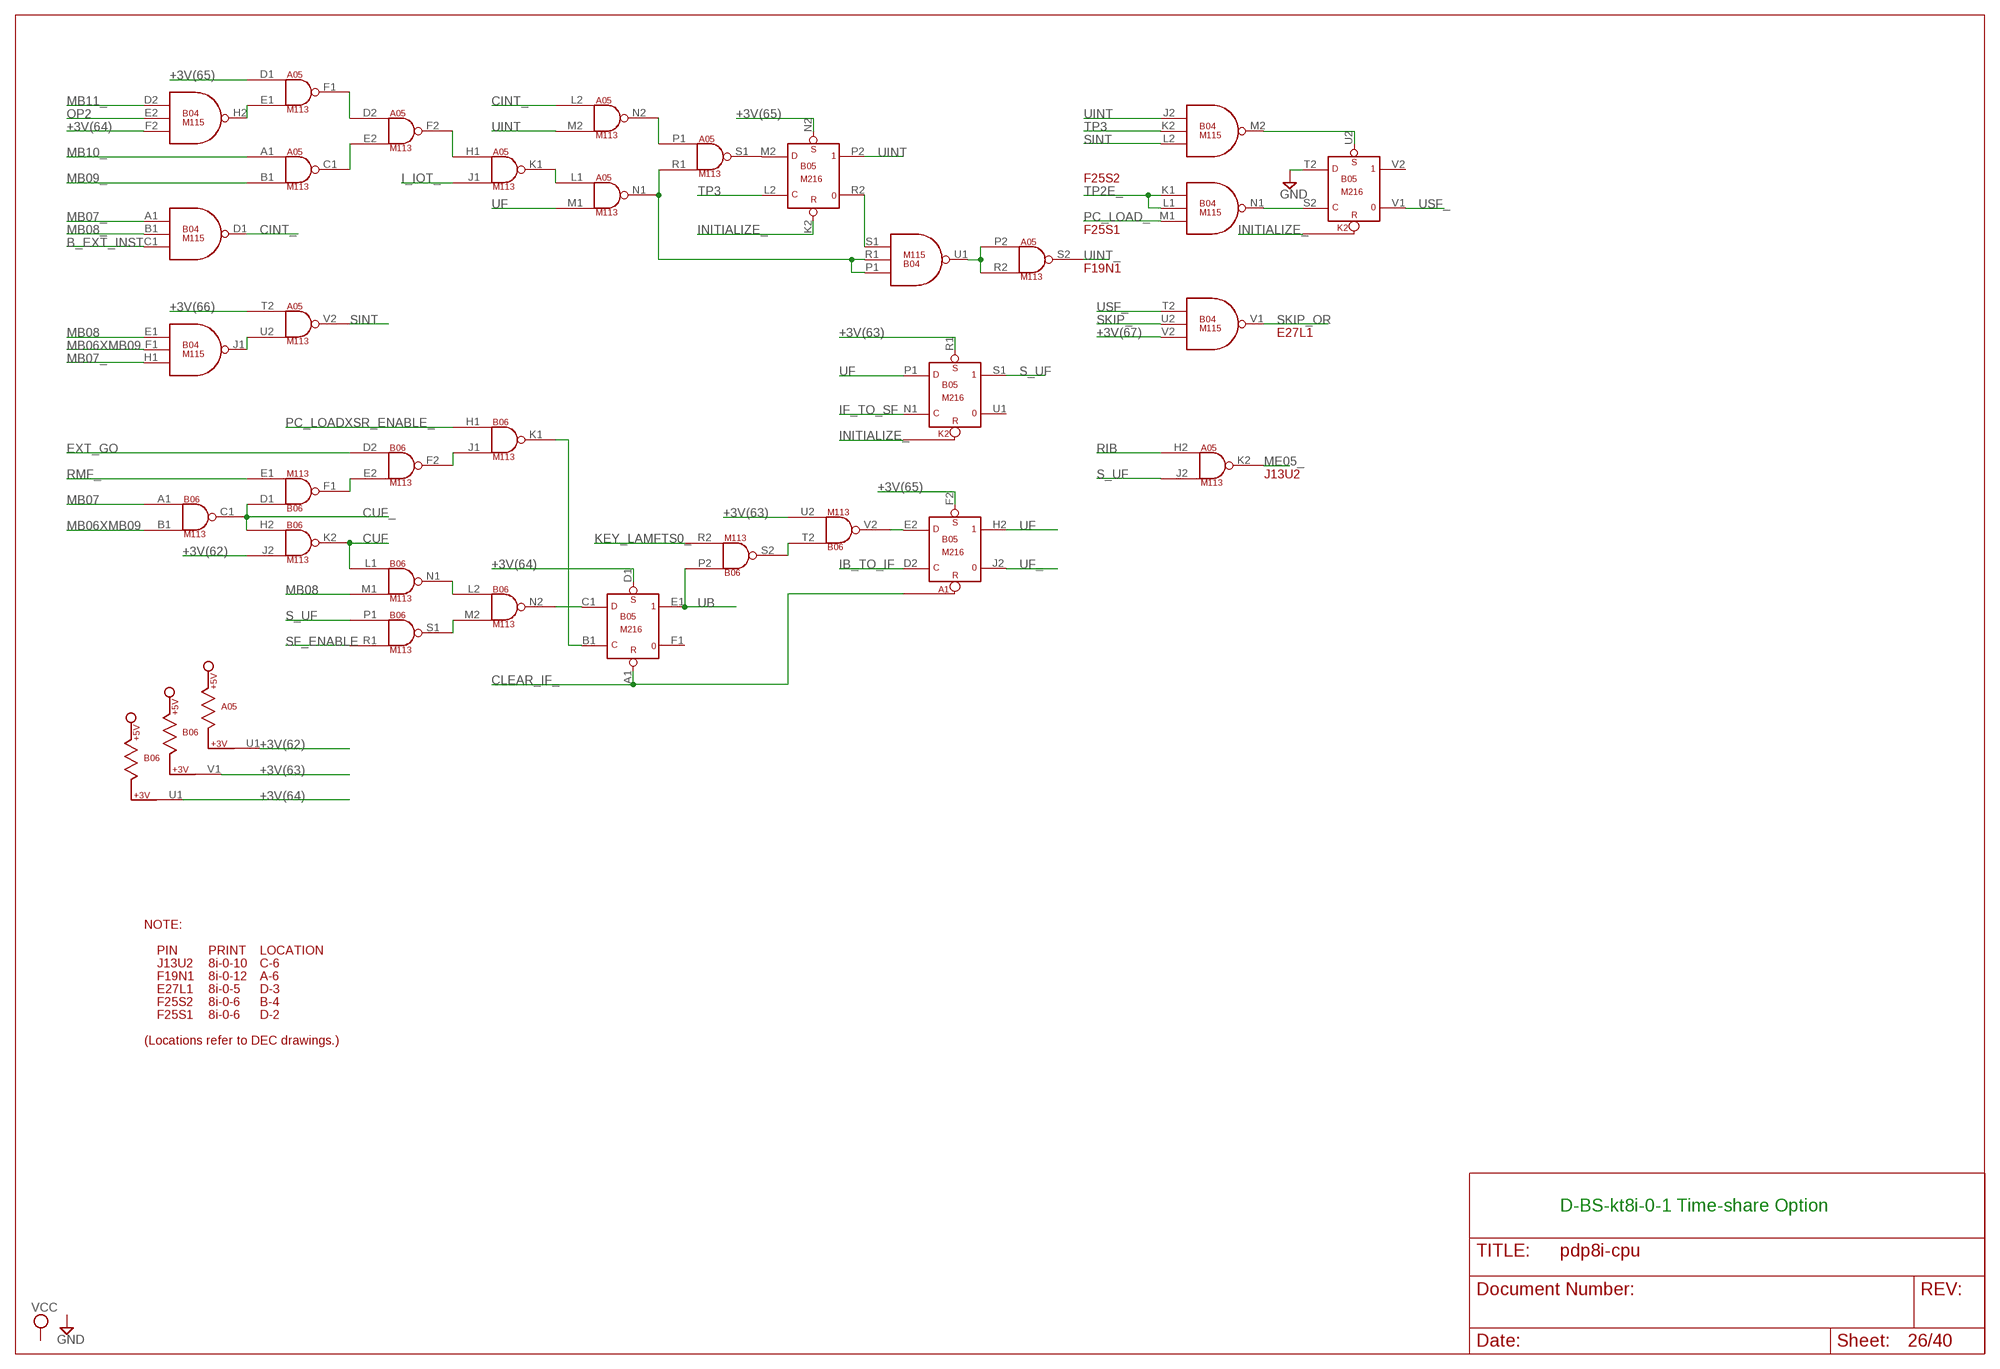
[diagram p26: schematic, sheet 26]
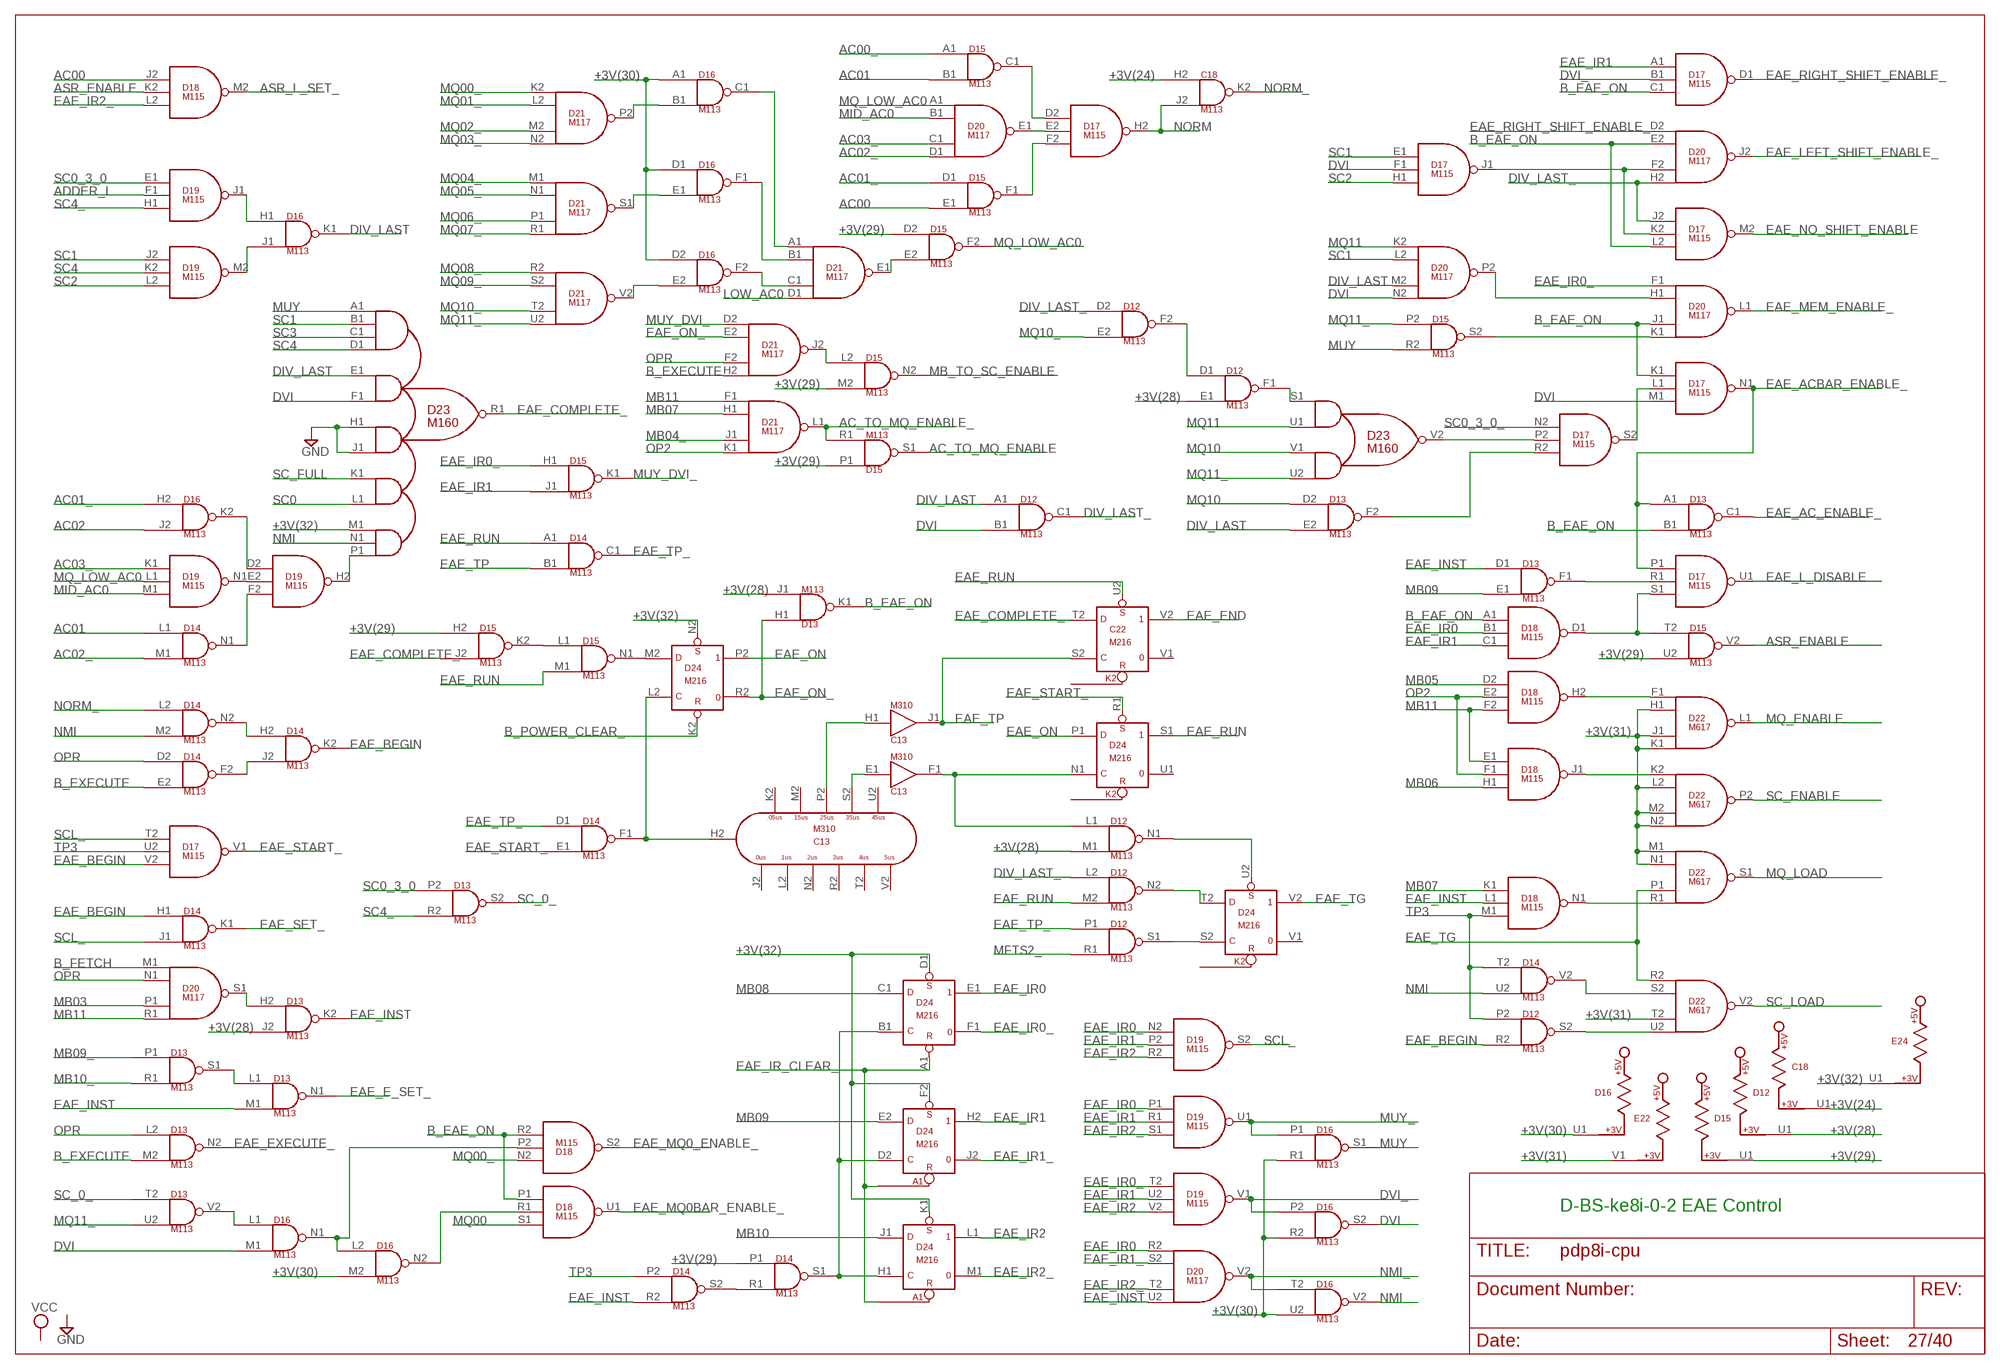
[diagram p27: schematic, sheet 27]
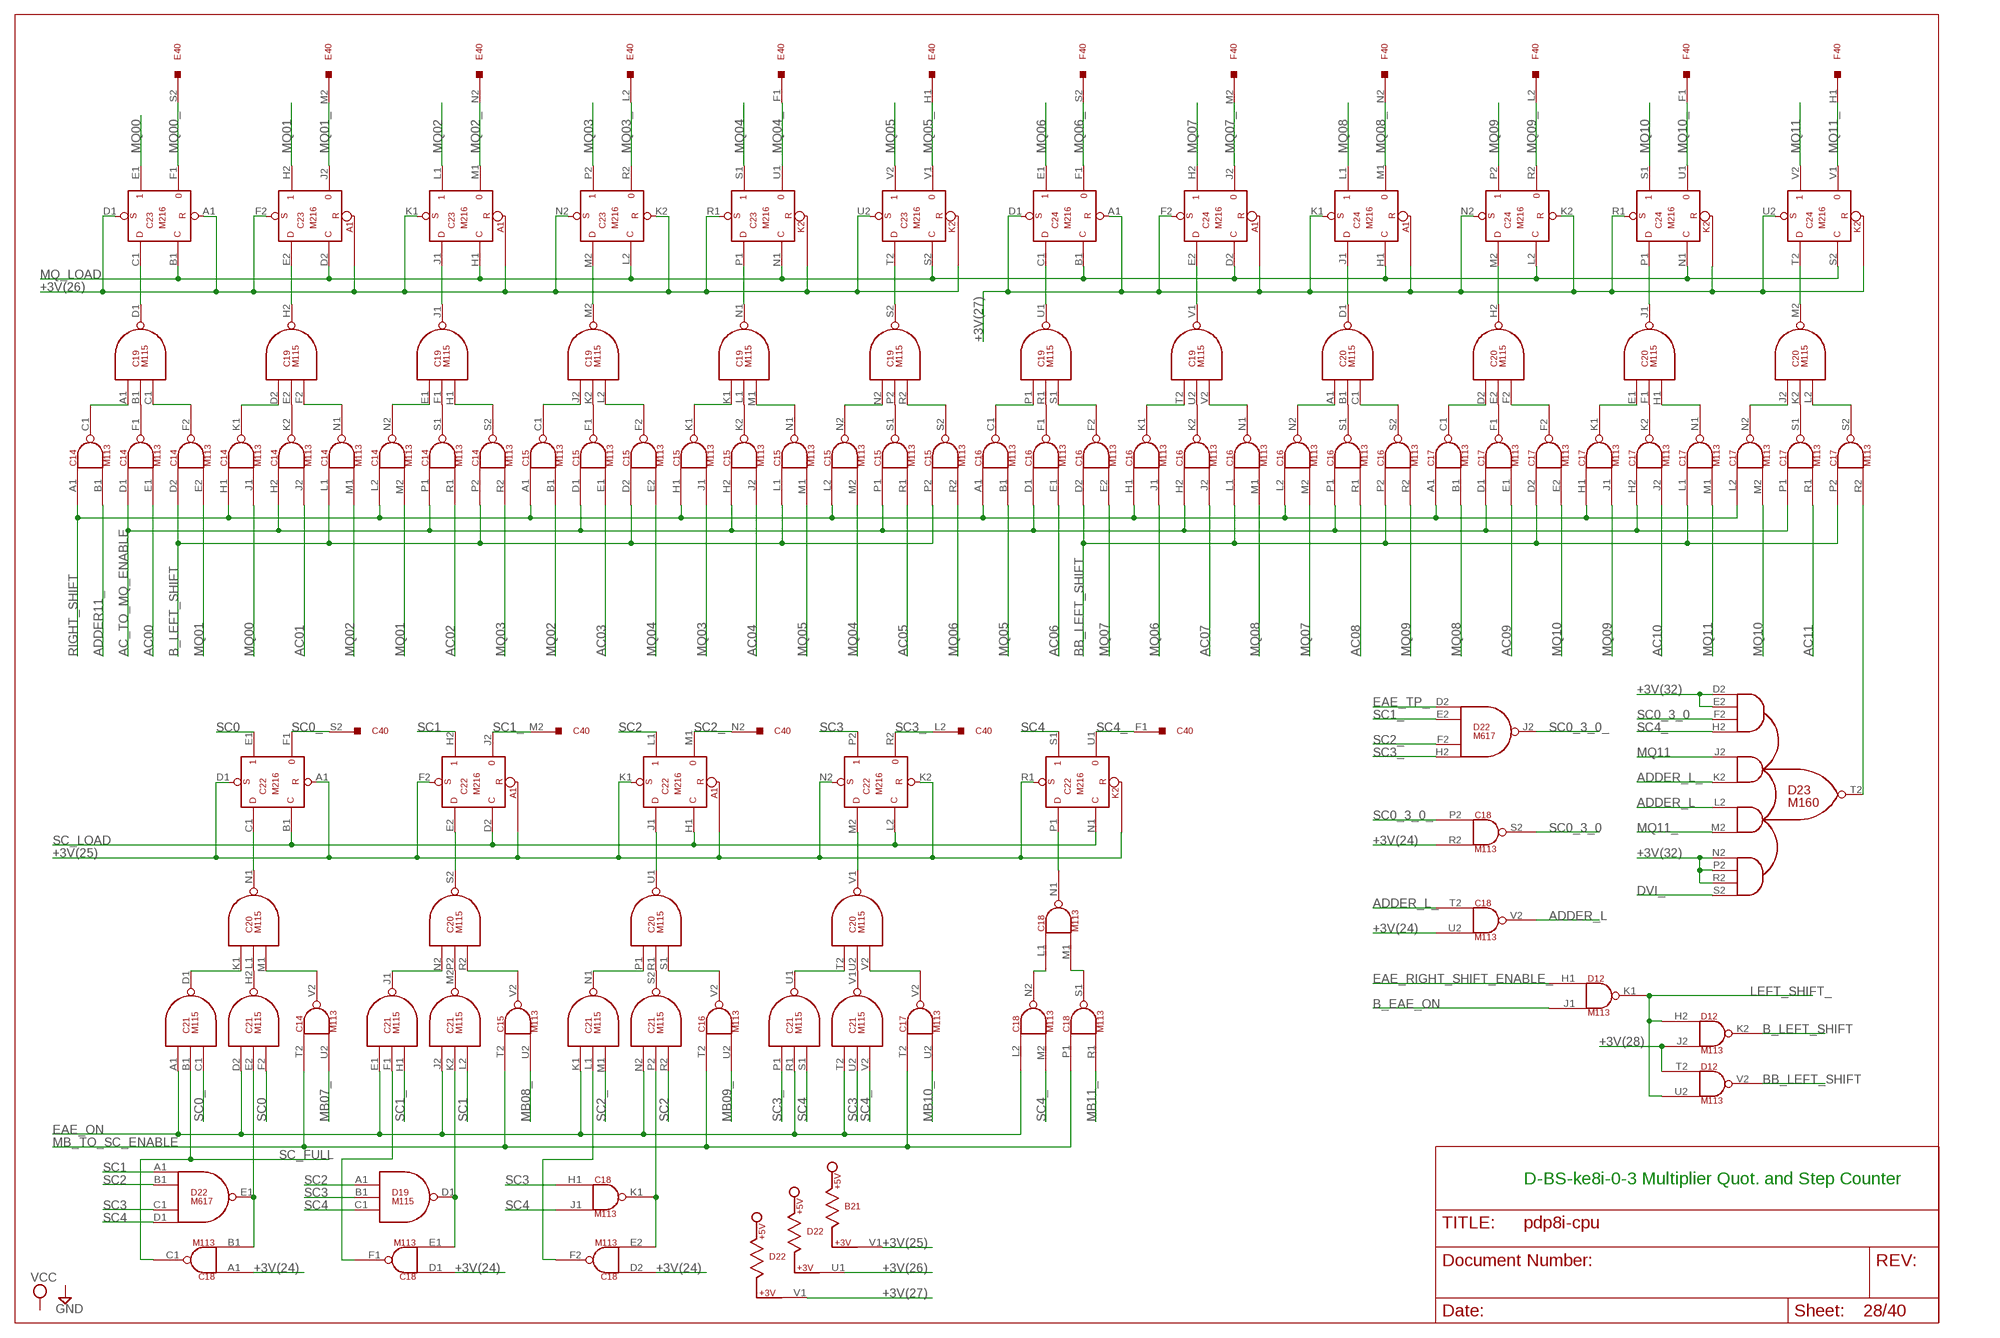
[diagram p28: schematic, sheet 28]
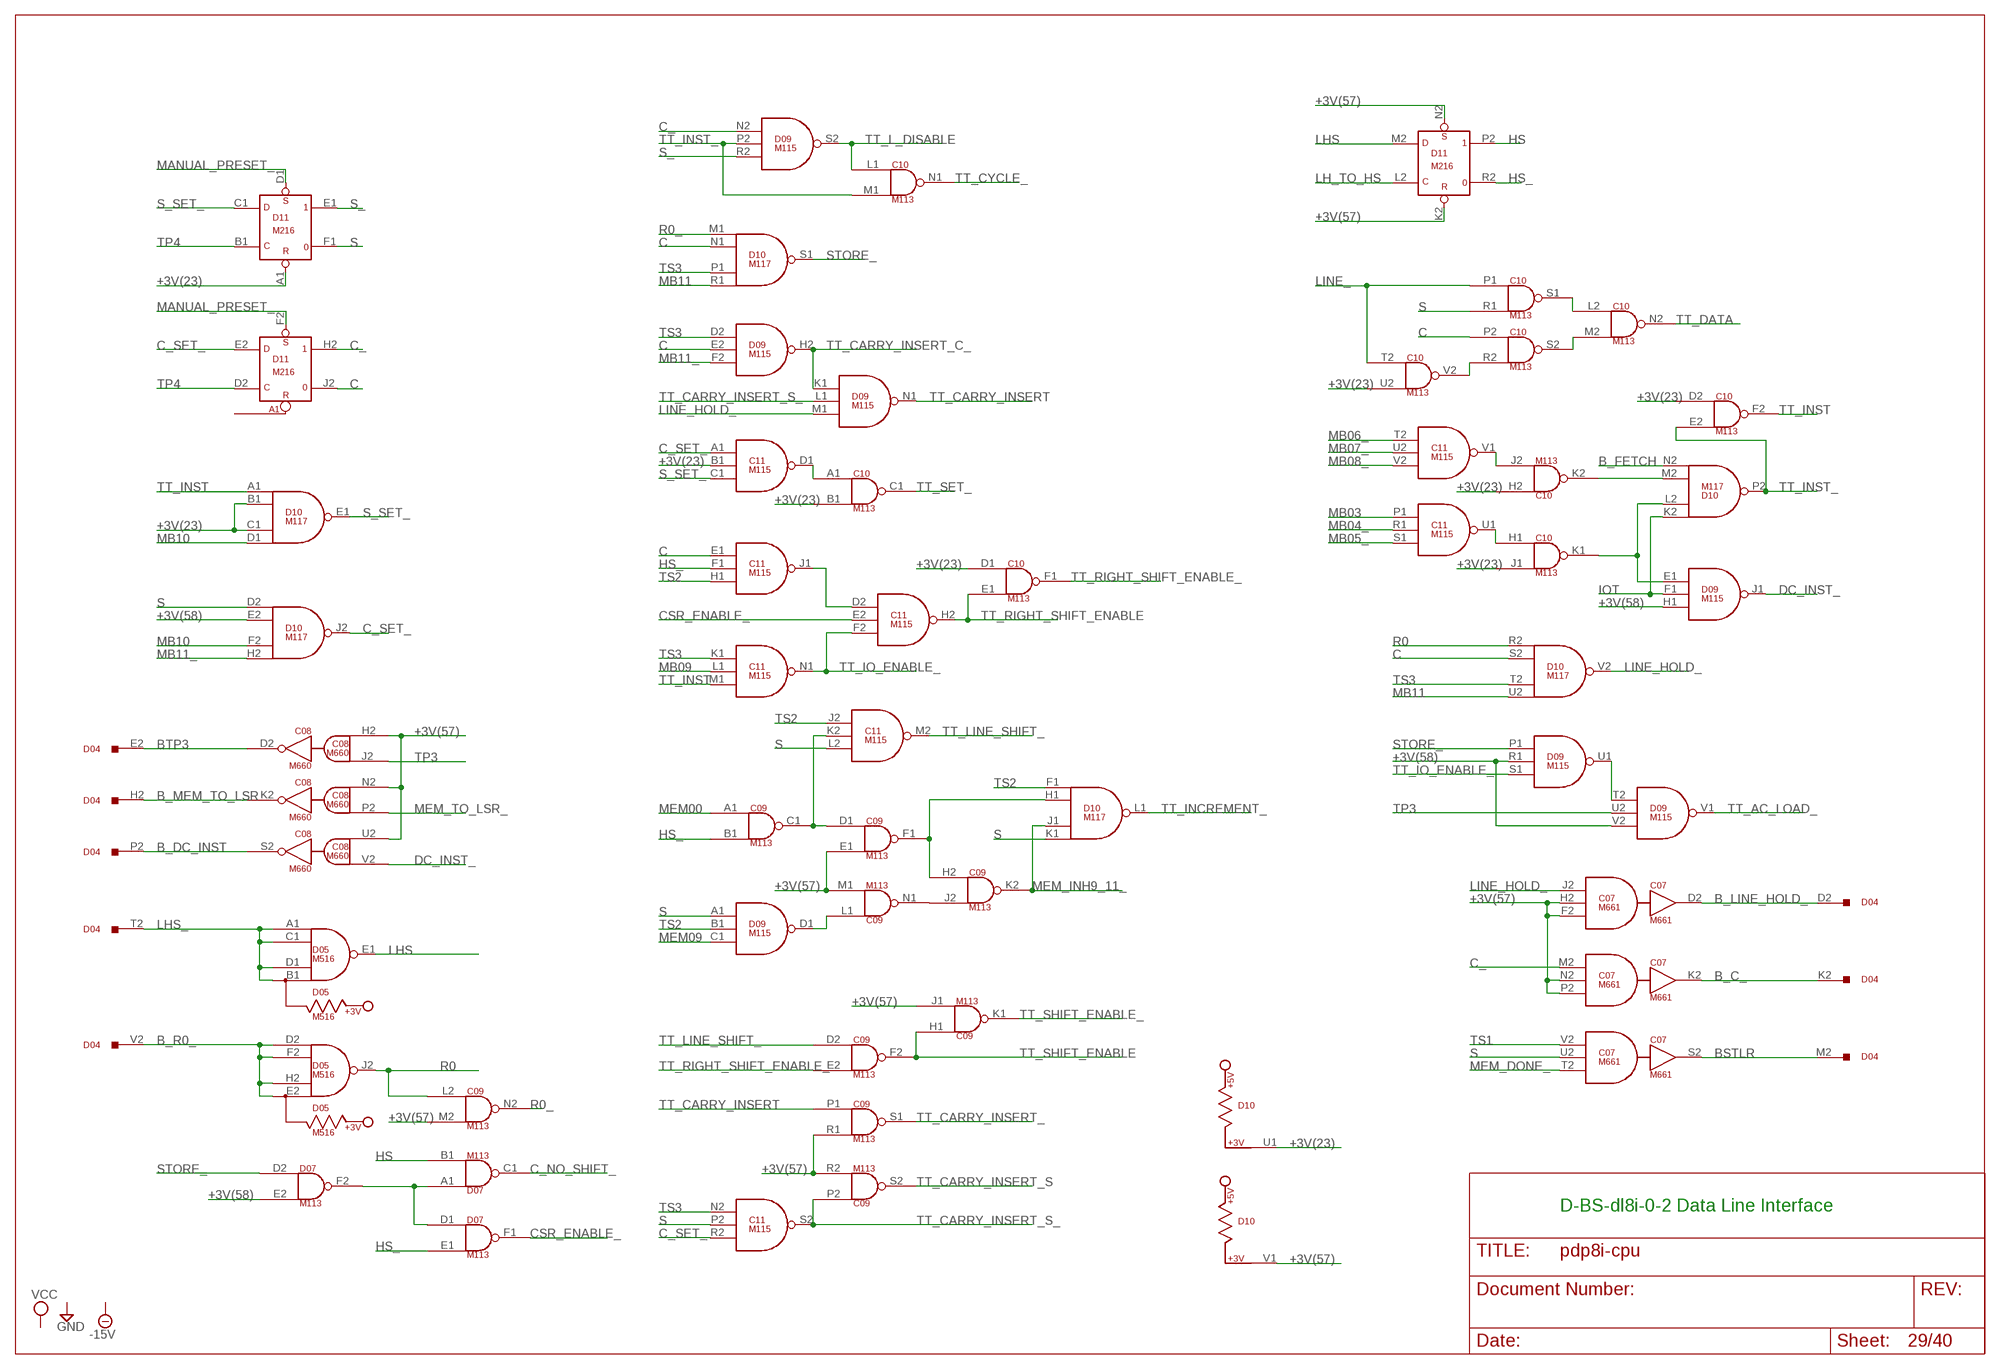
[diagram p29: schematic, sheet 29]
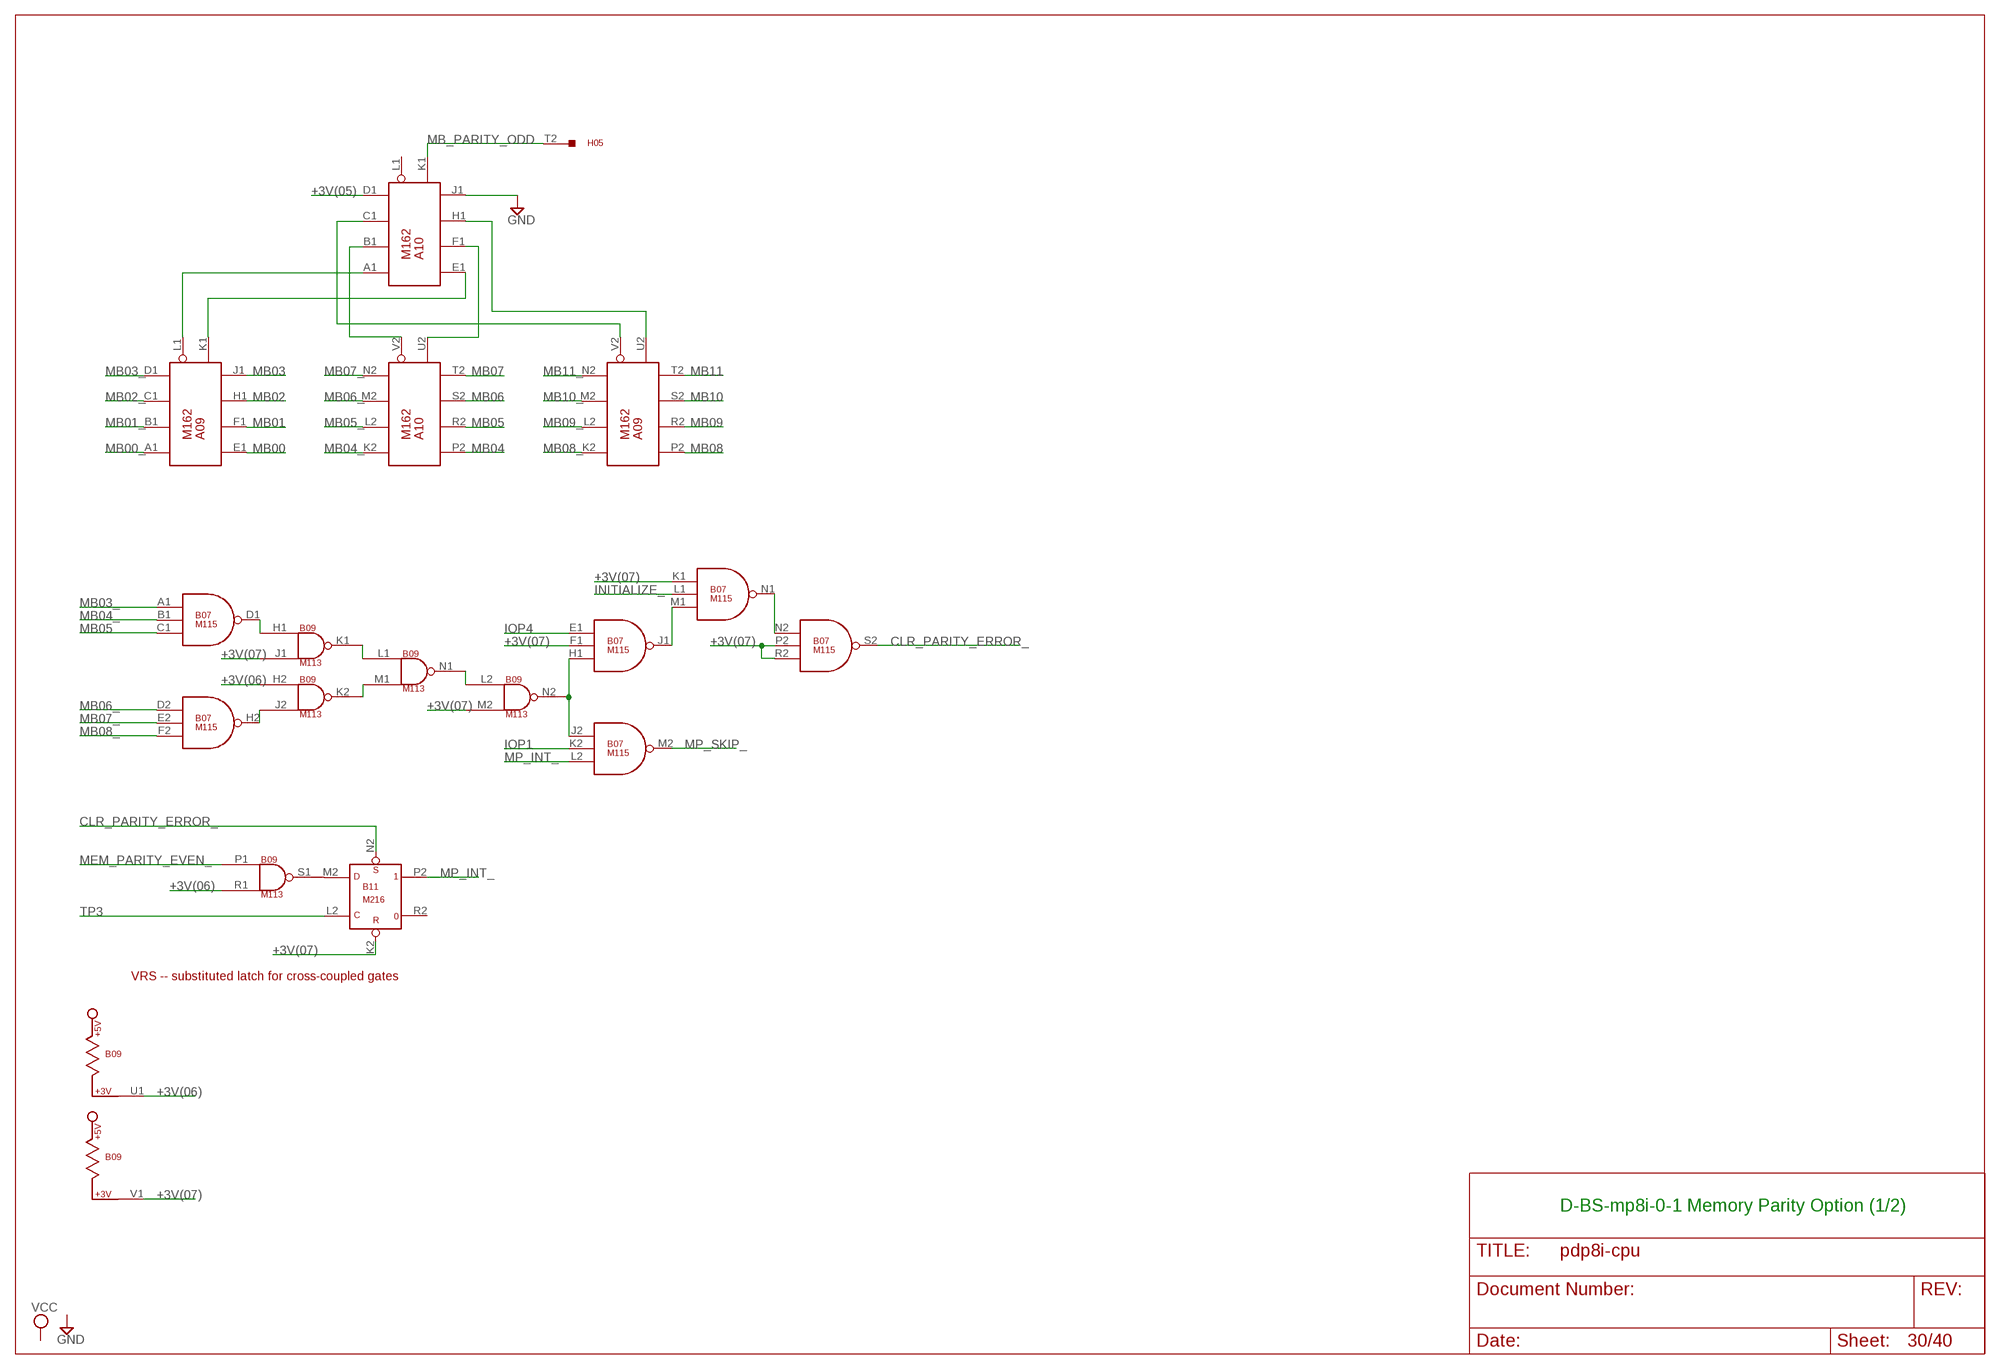
[diagram p30: schematic, sheet 30]
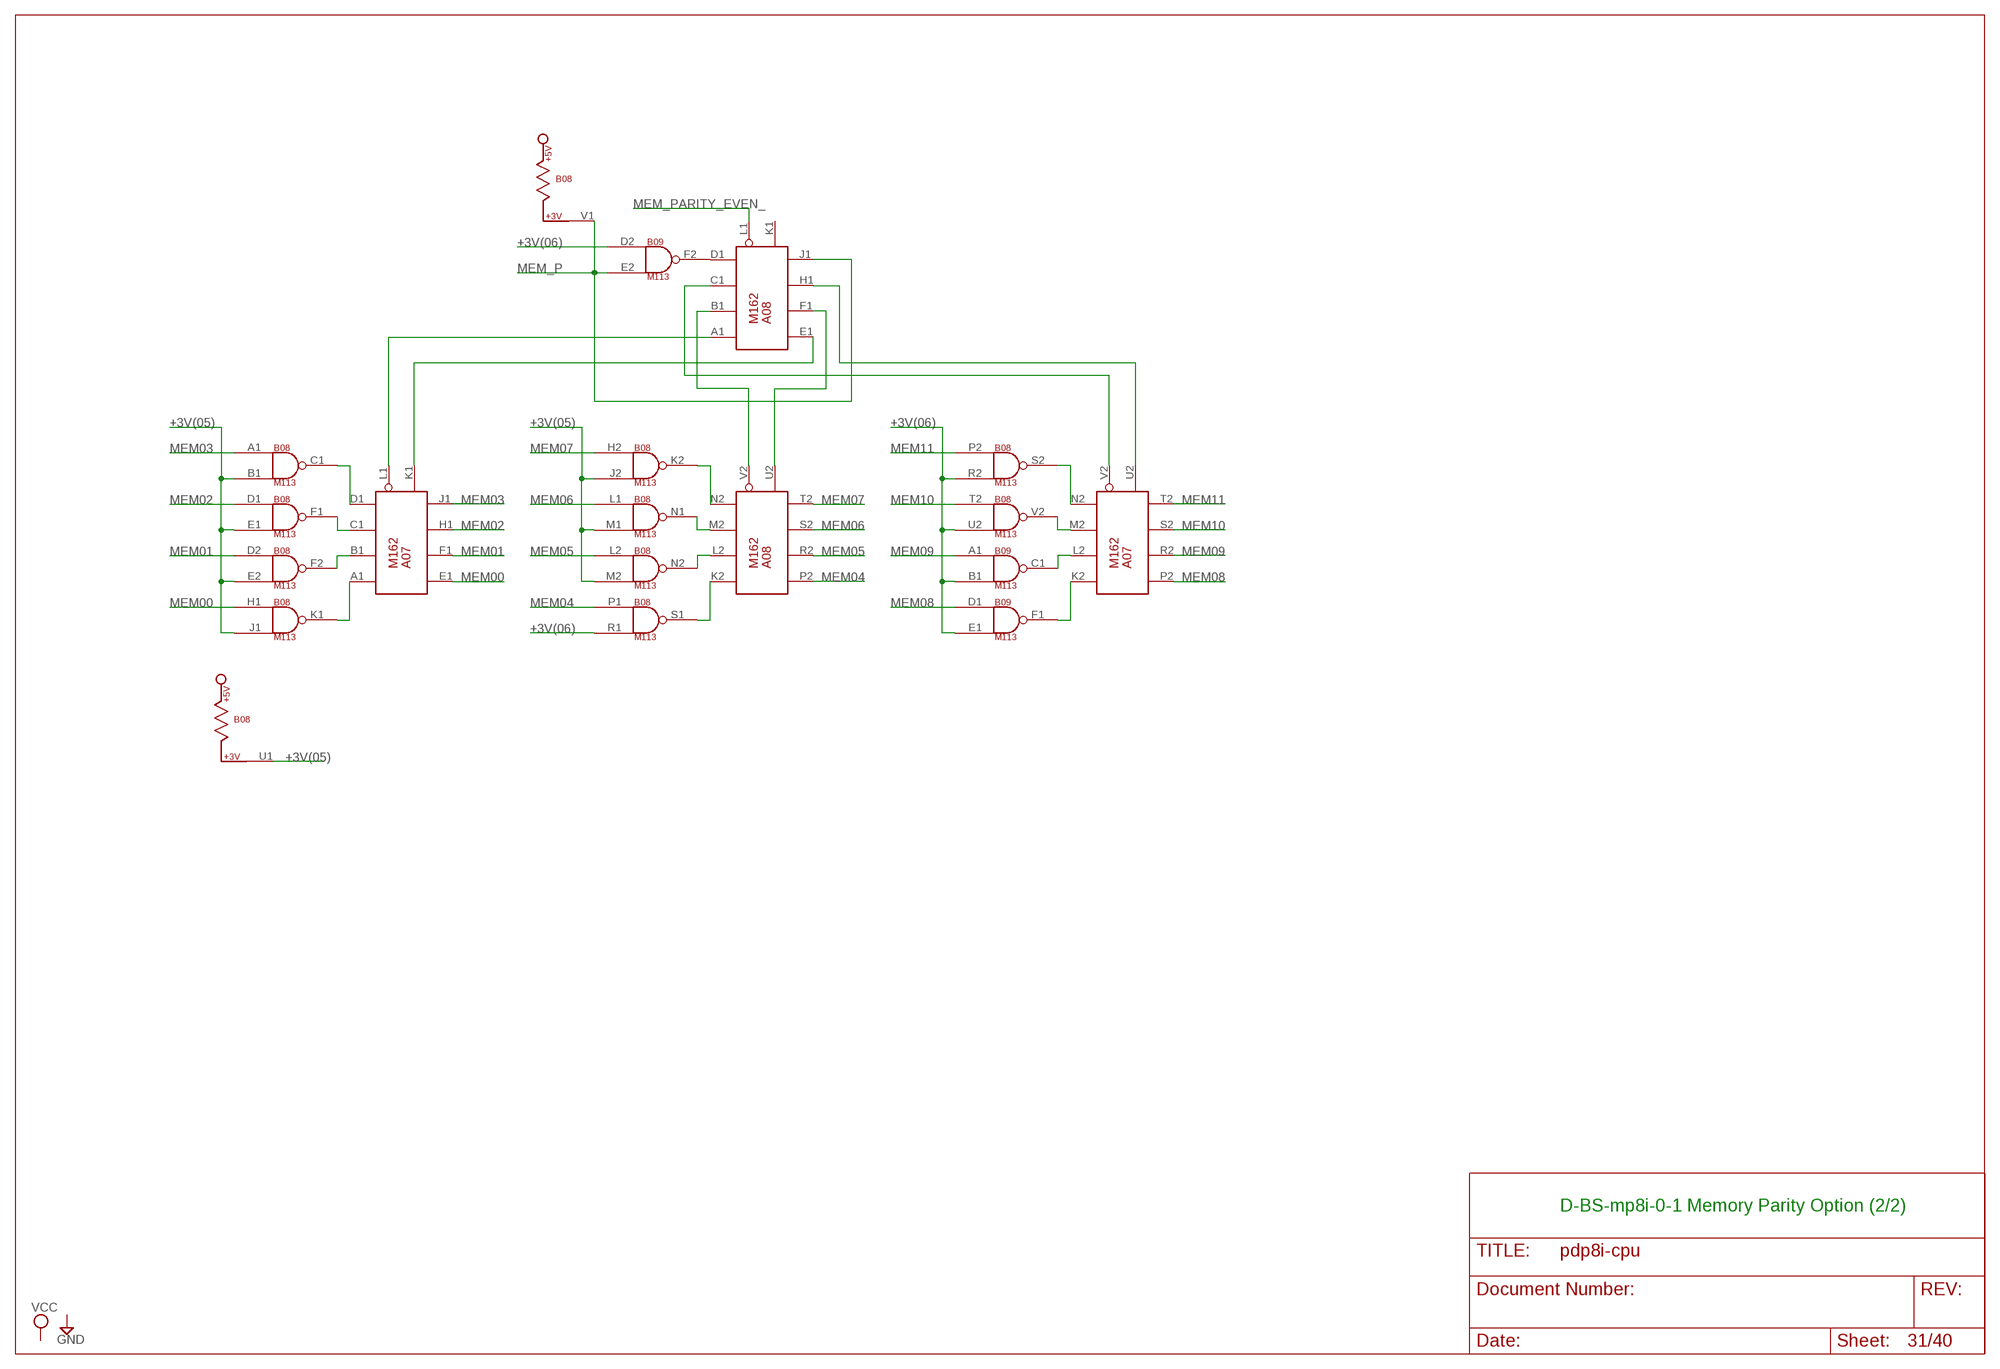
[diagram p31: schematic, sheet 31]
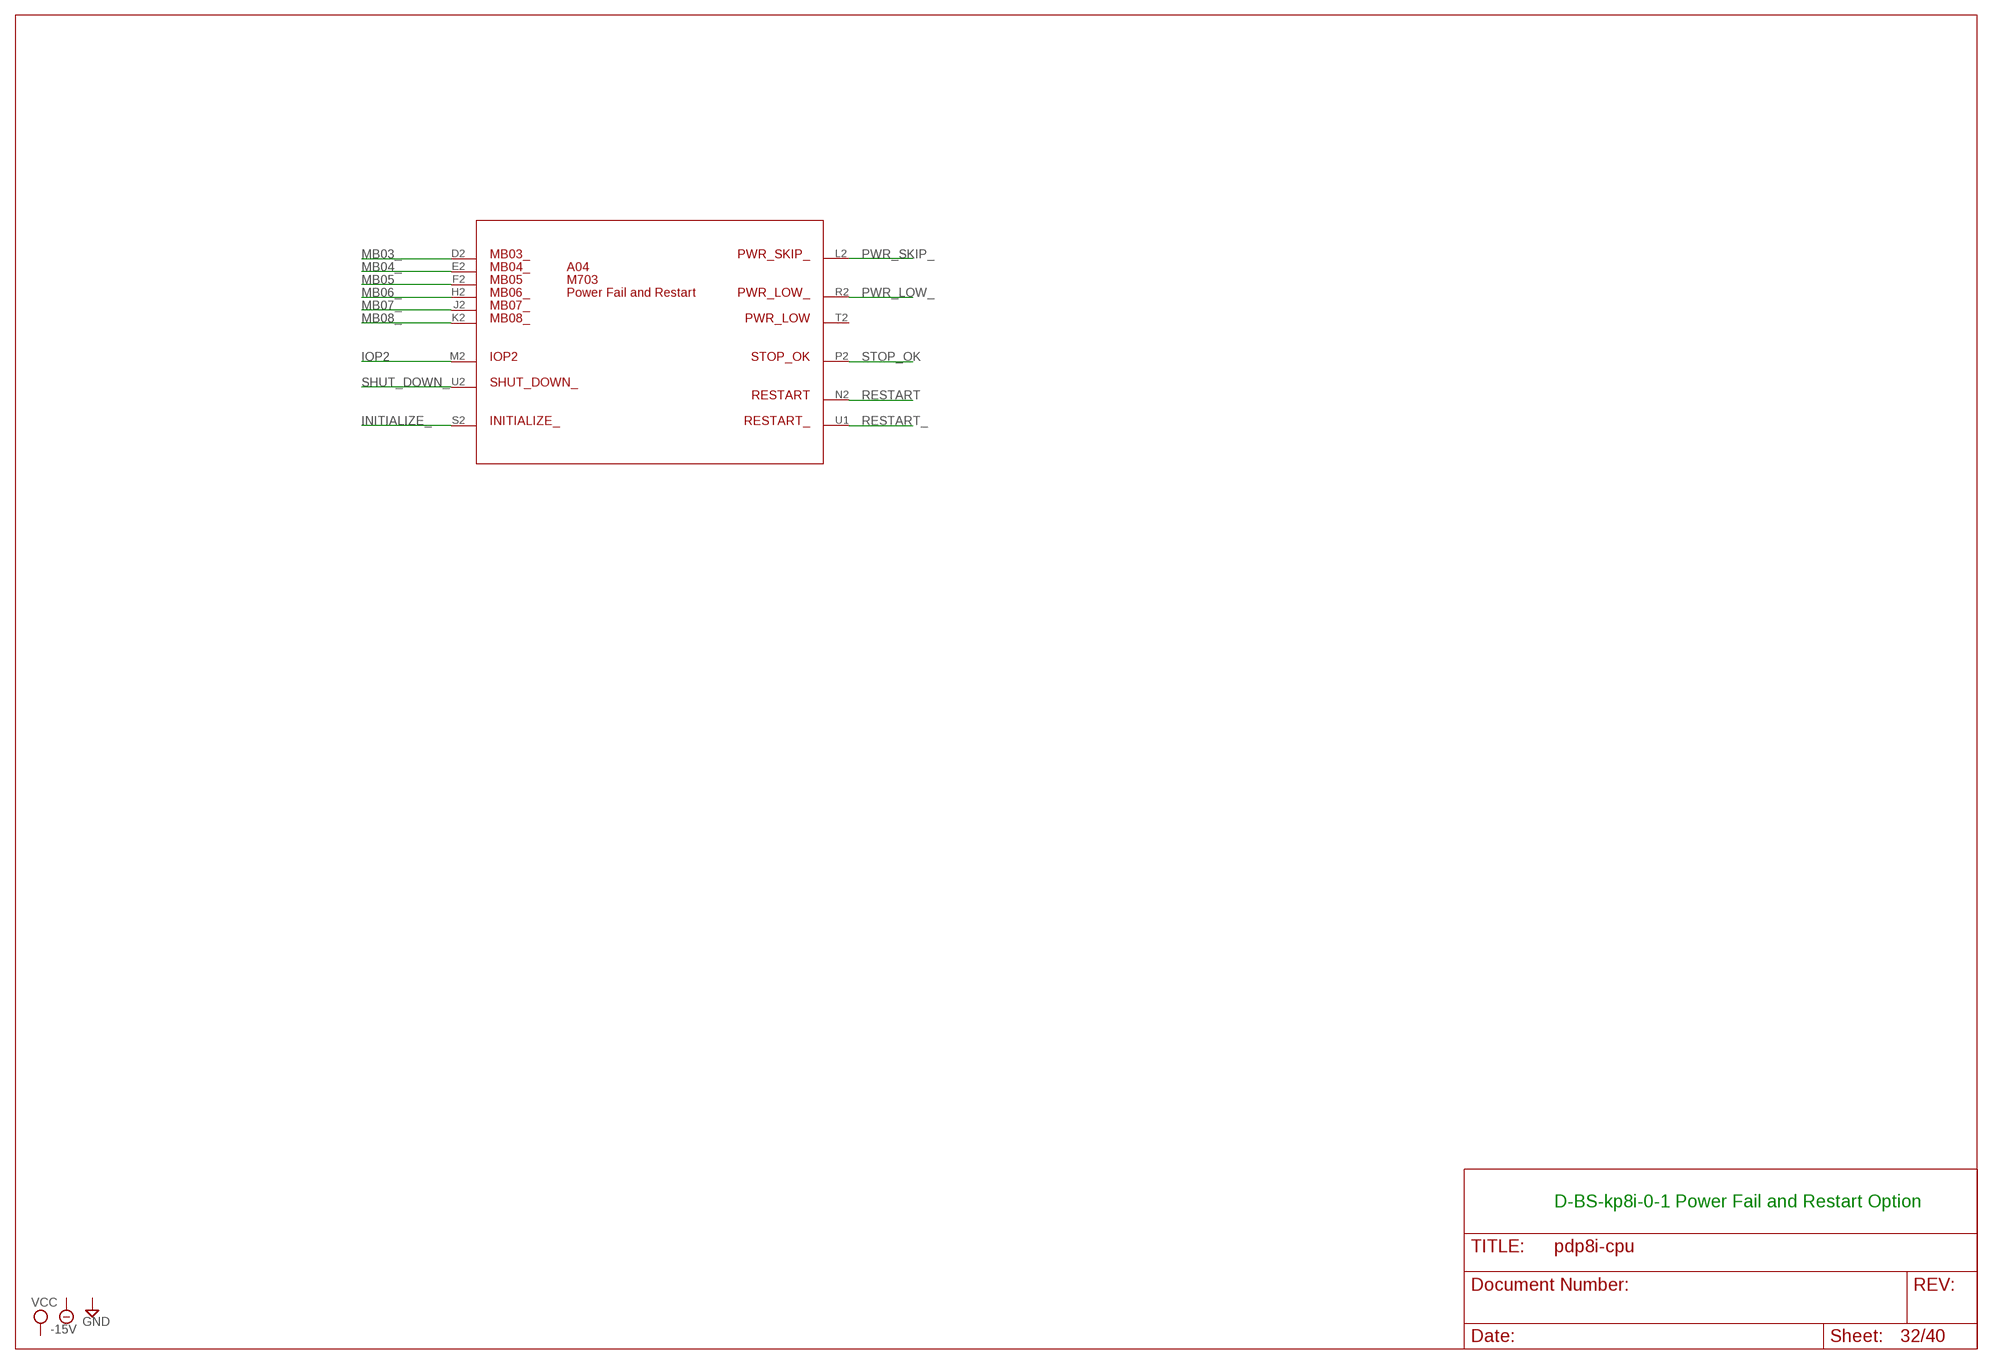
[diagram p32: schematic, sheet 32]
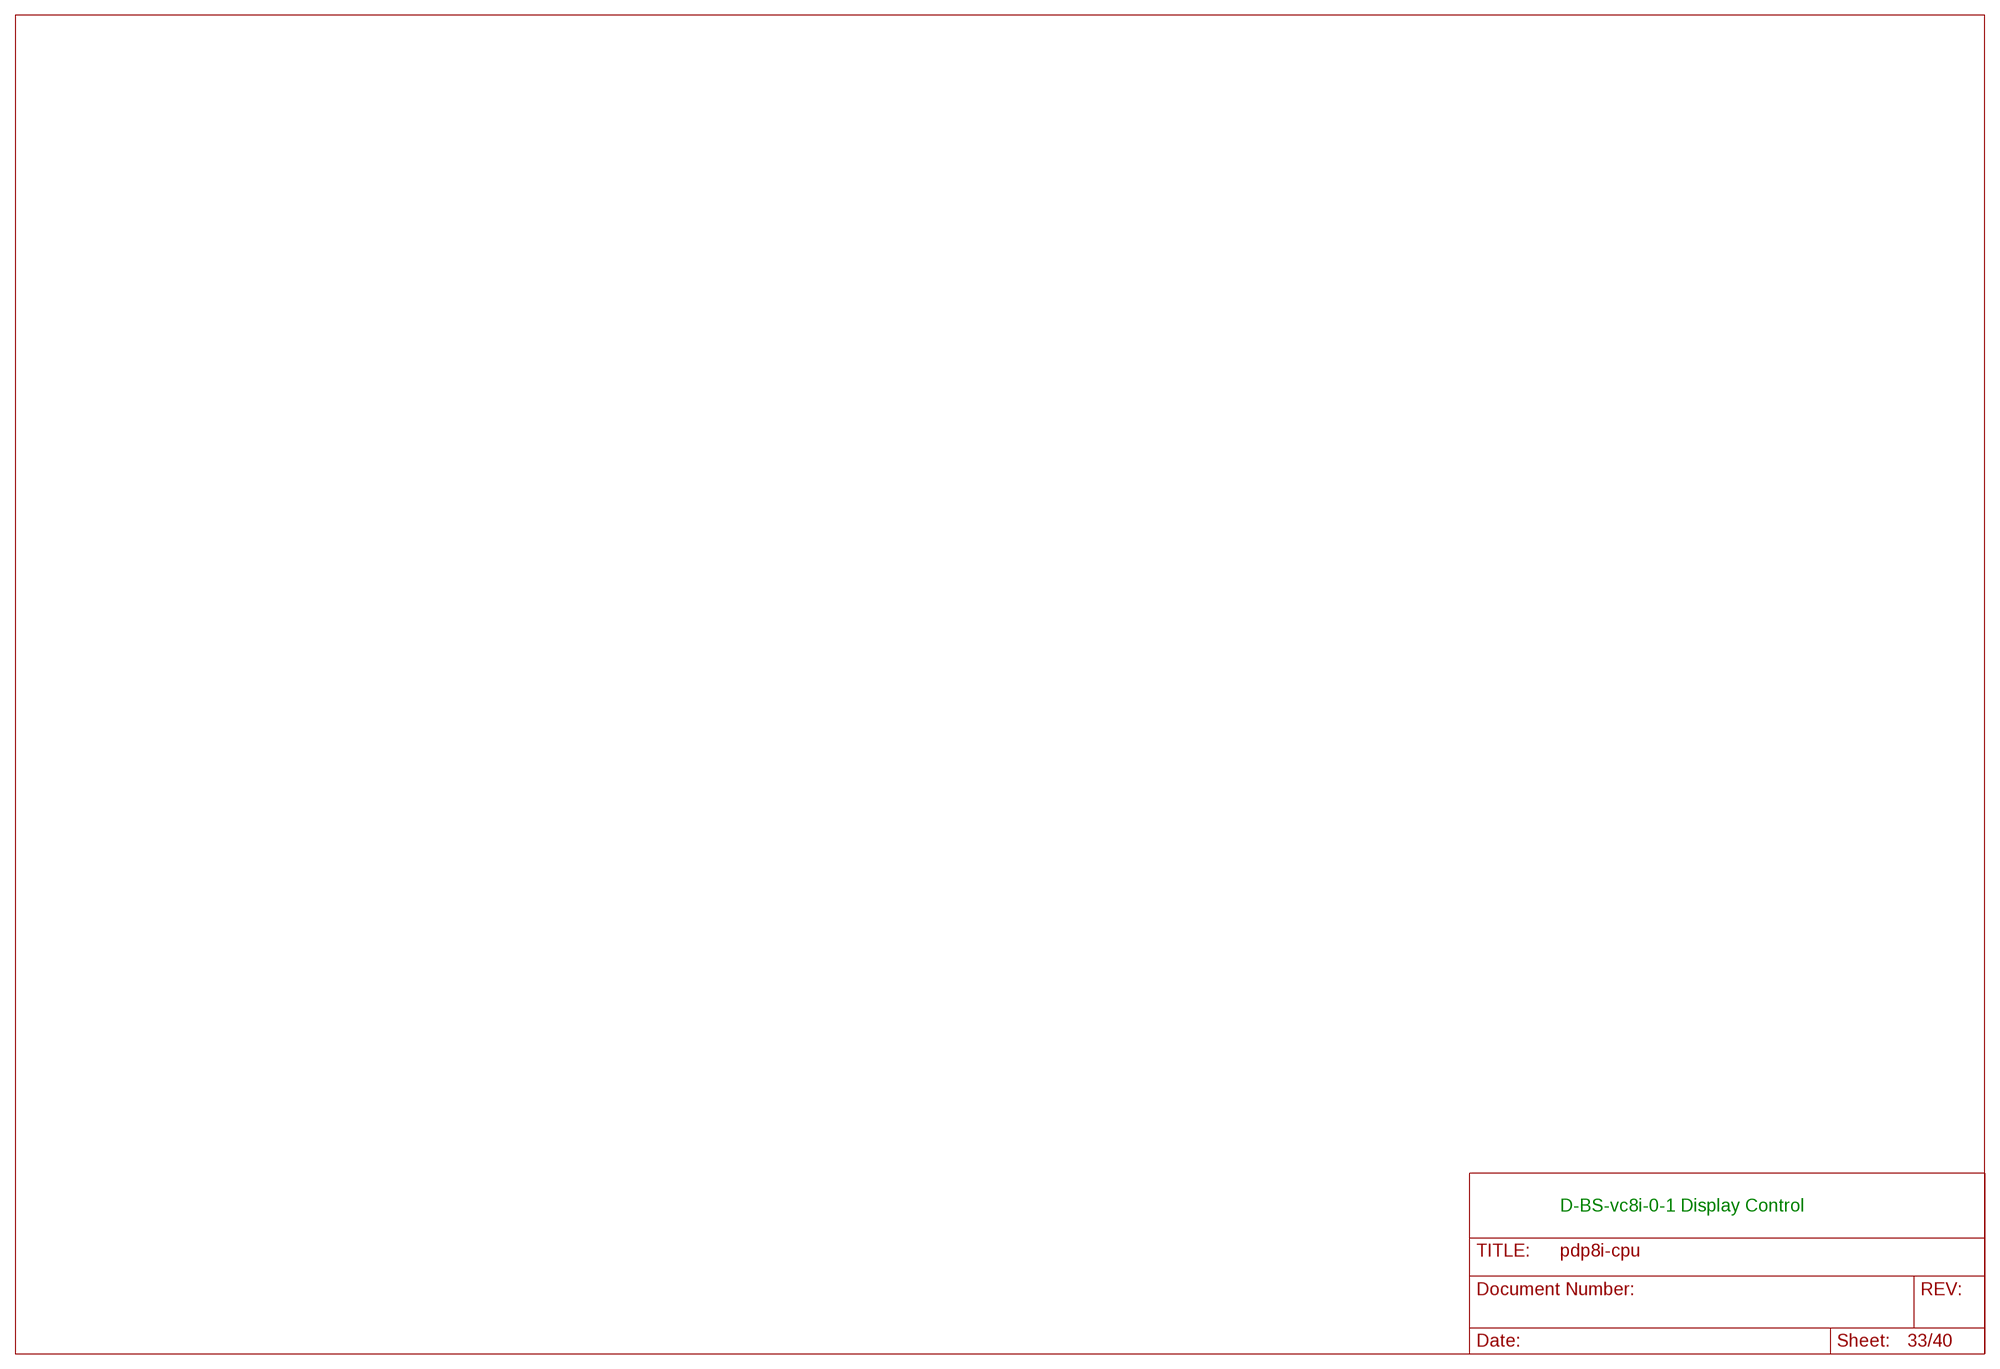
[diagram p33: schematic, sheet 33]
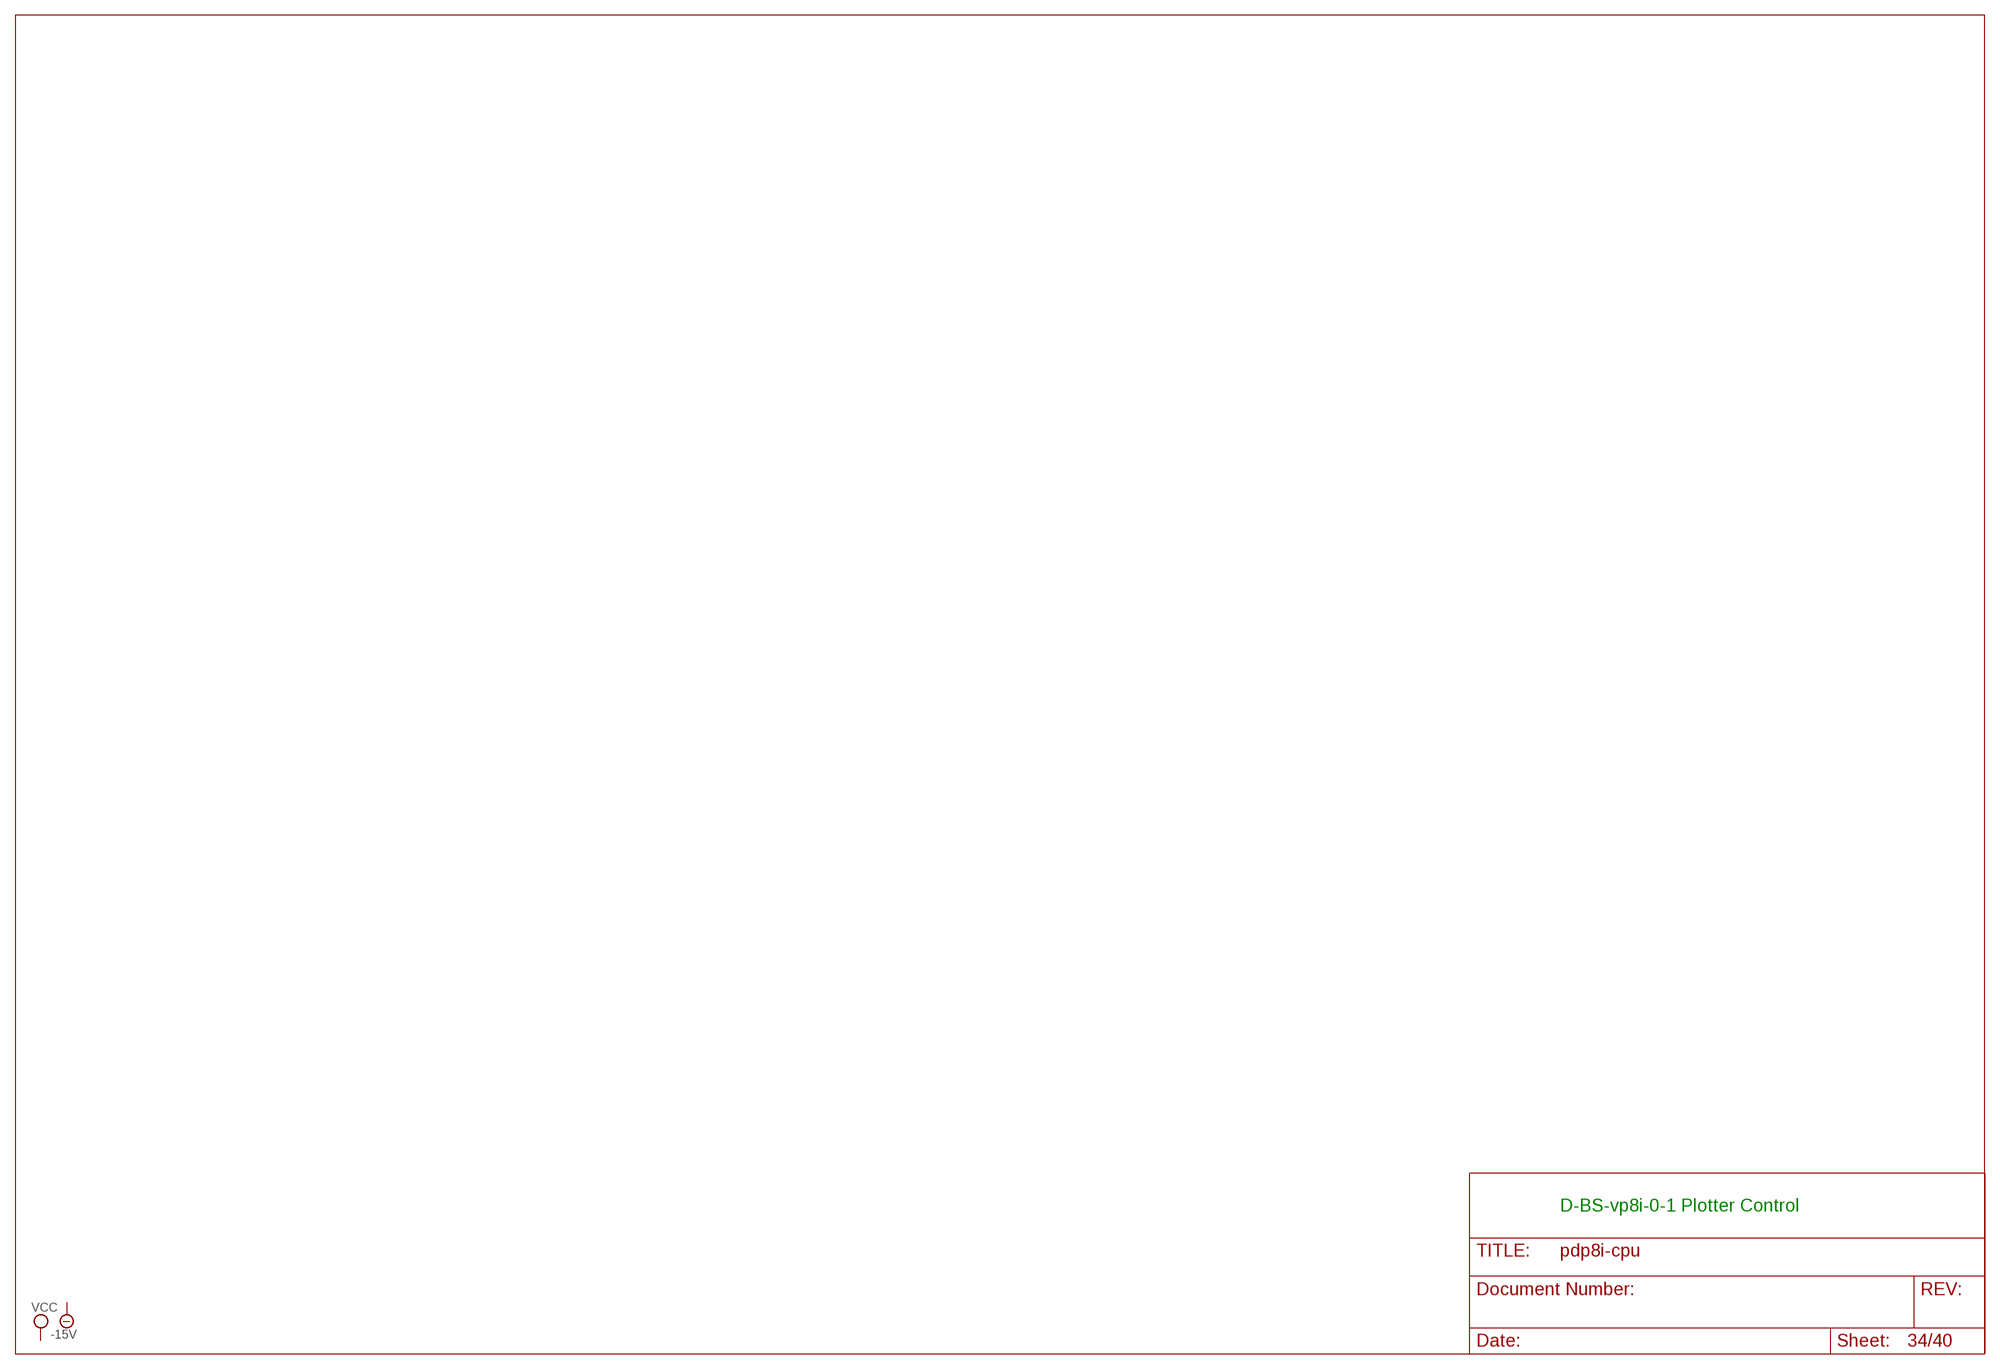
[diagram p34: schematic, sheet 34]
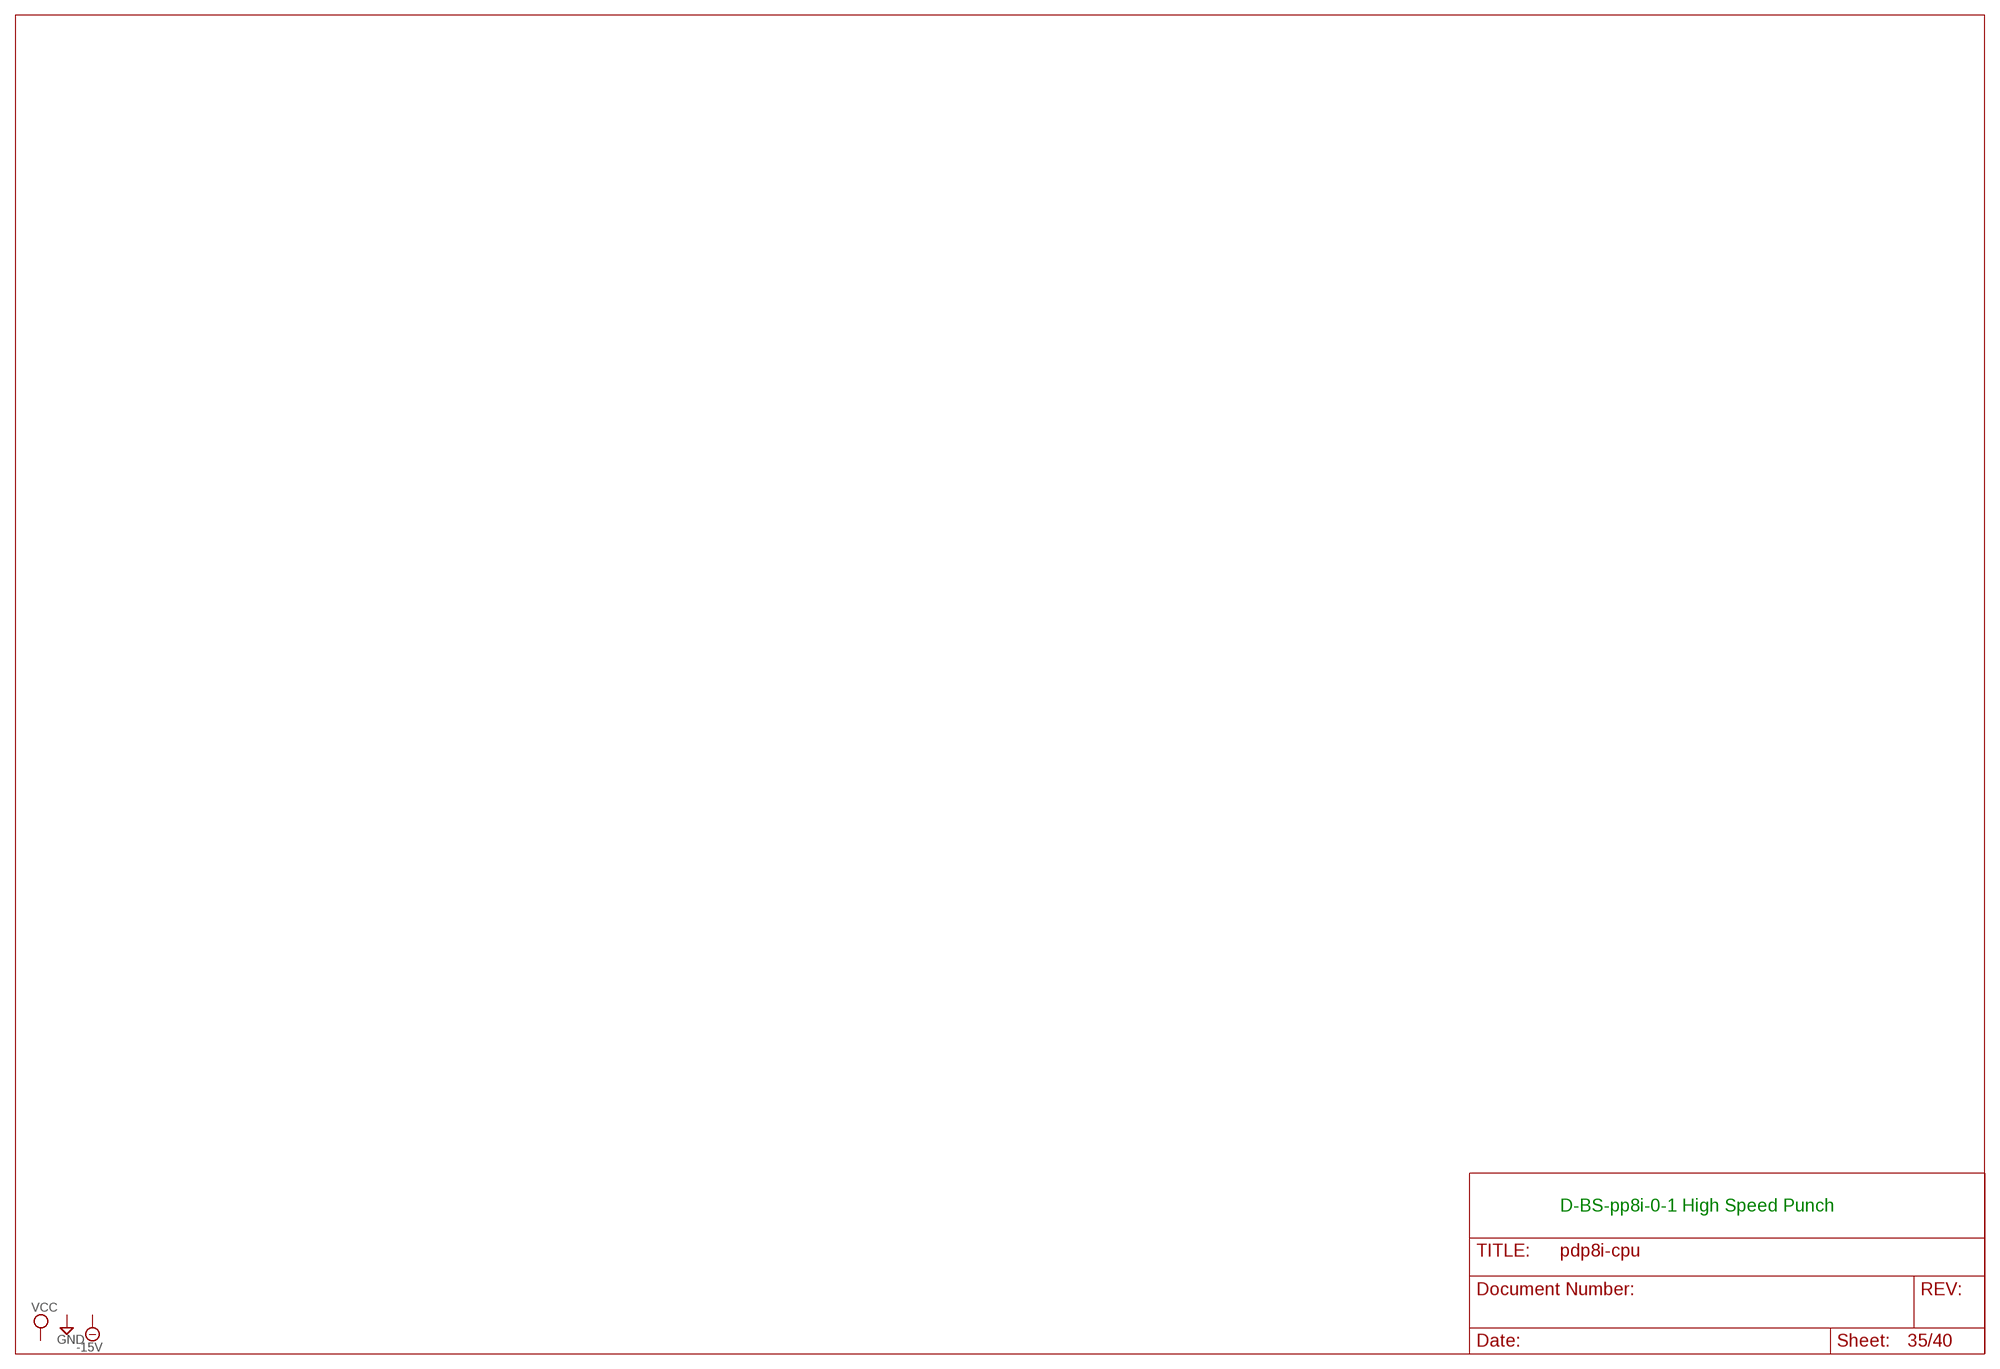
[diagram p35: schematic, sheet 35]
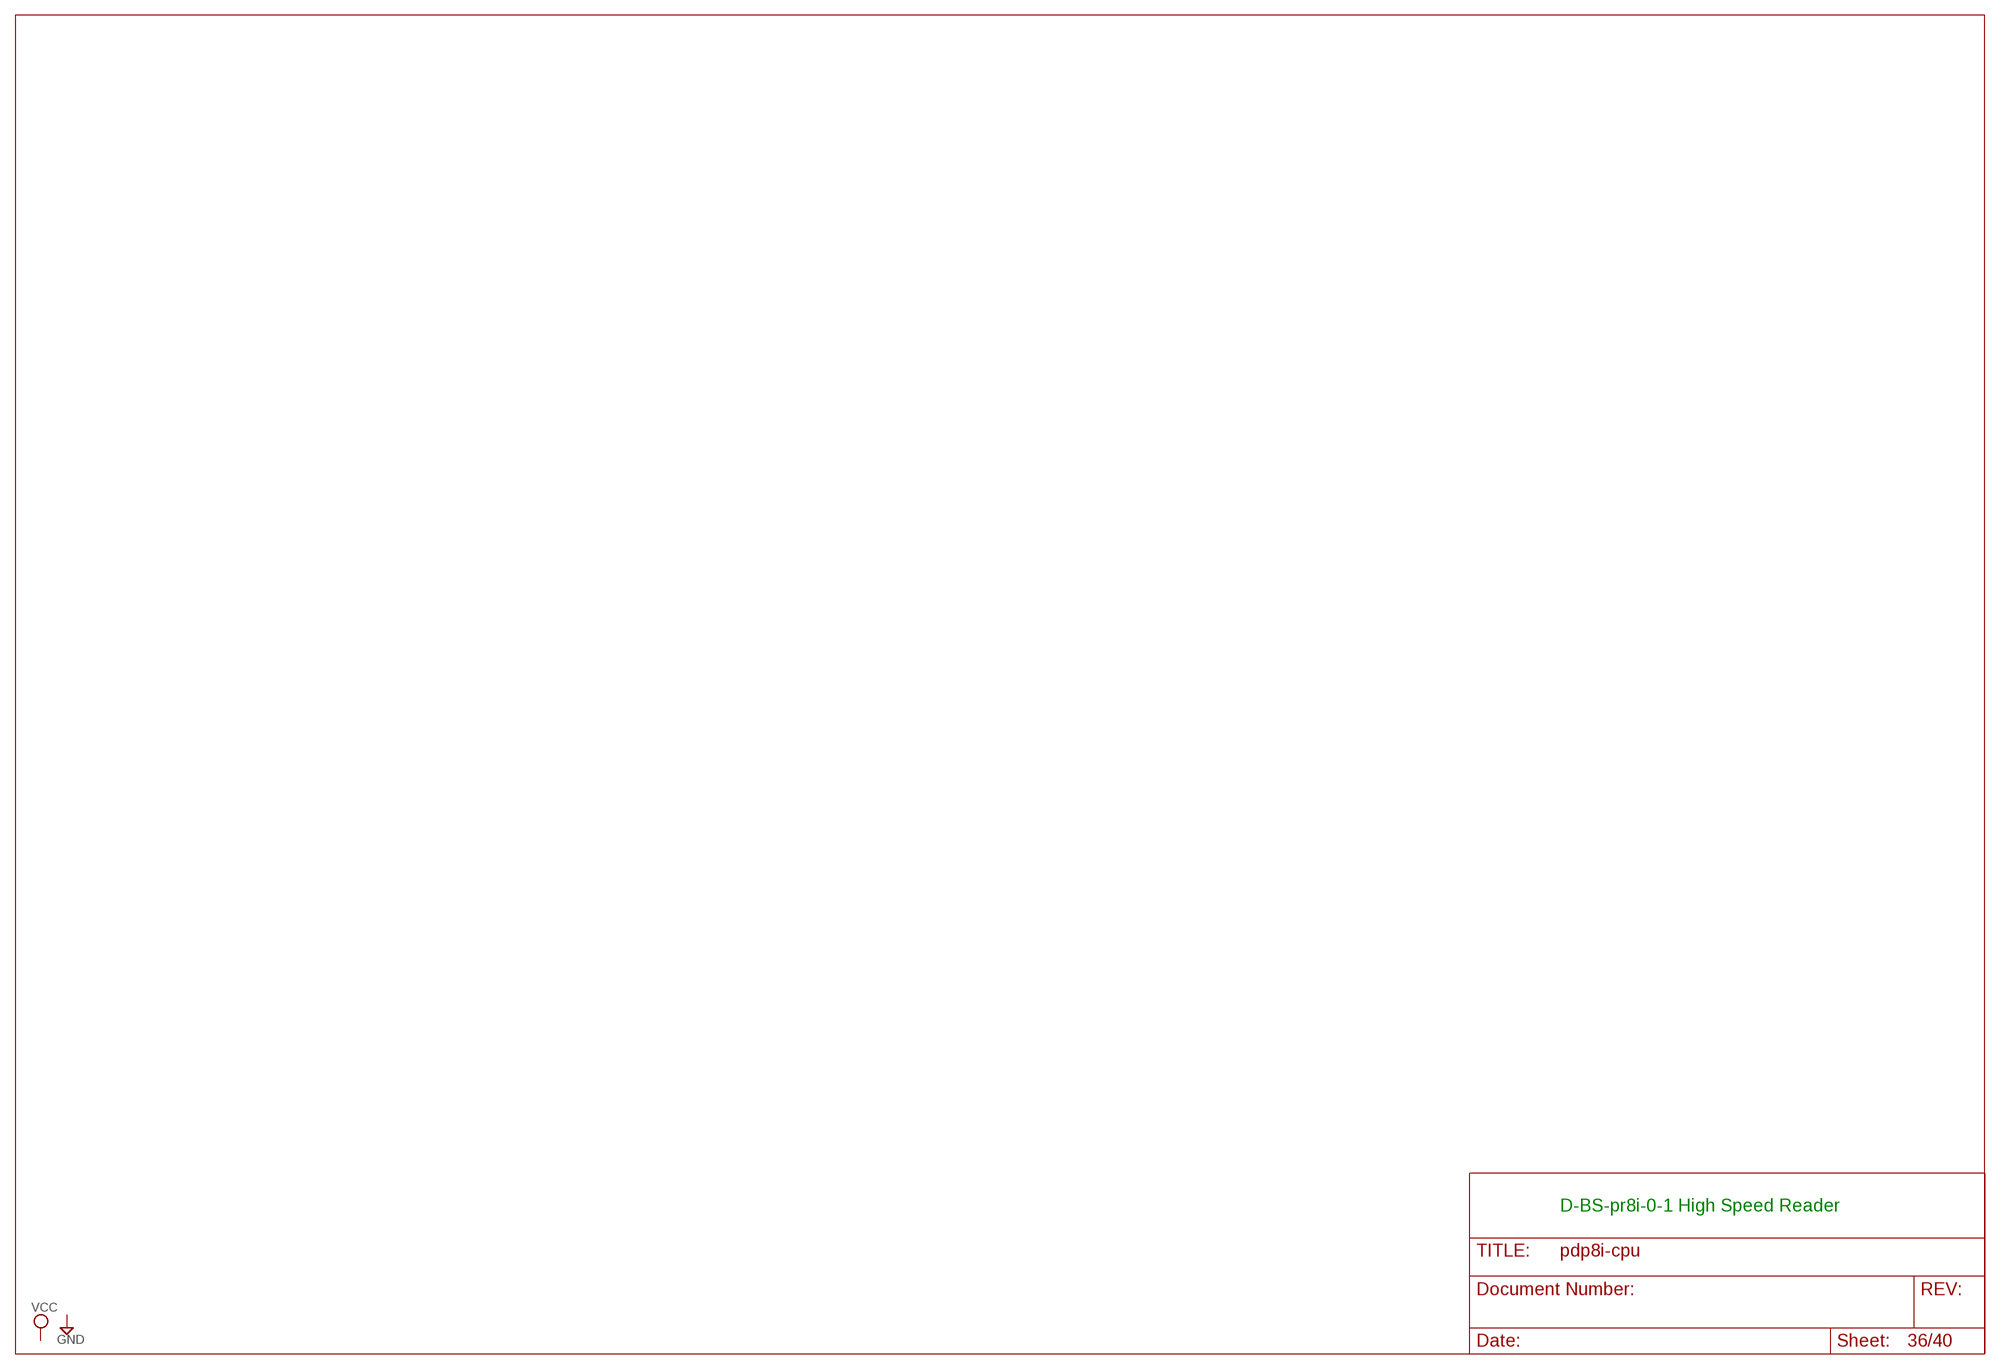
[diagram p36: schematic, sheet 36]
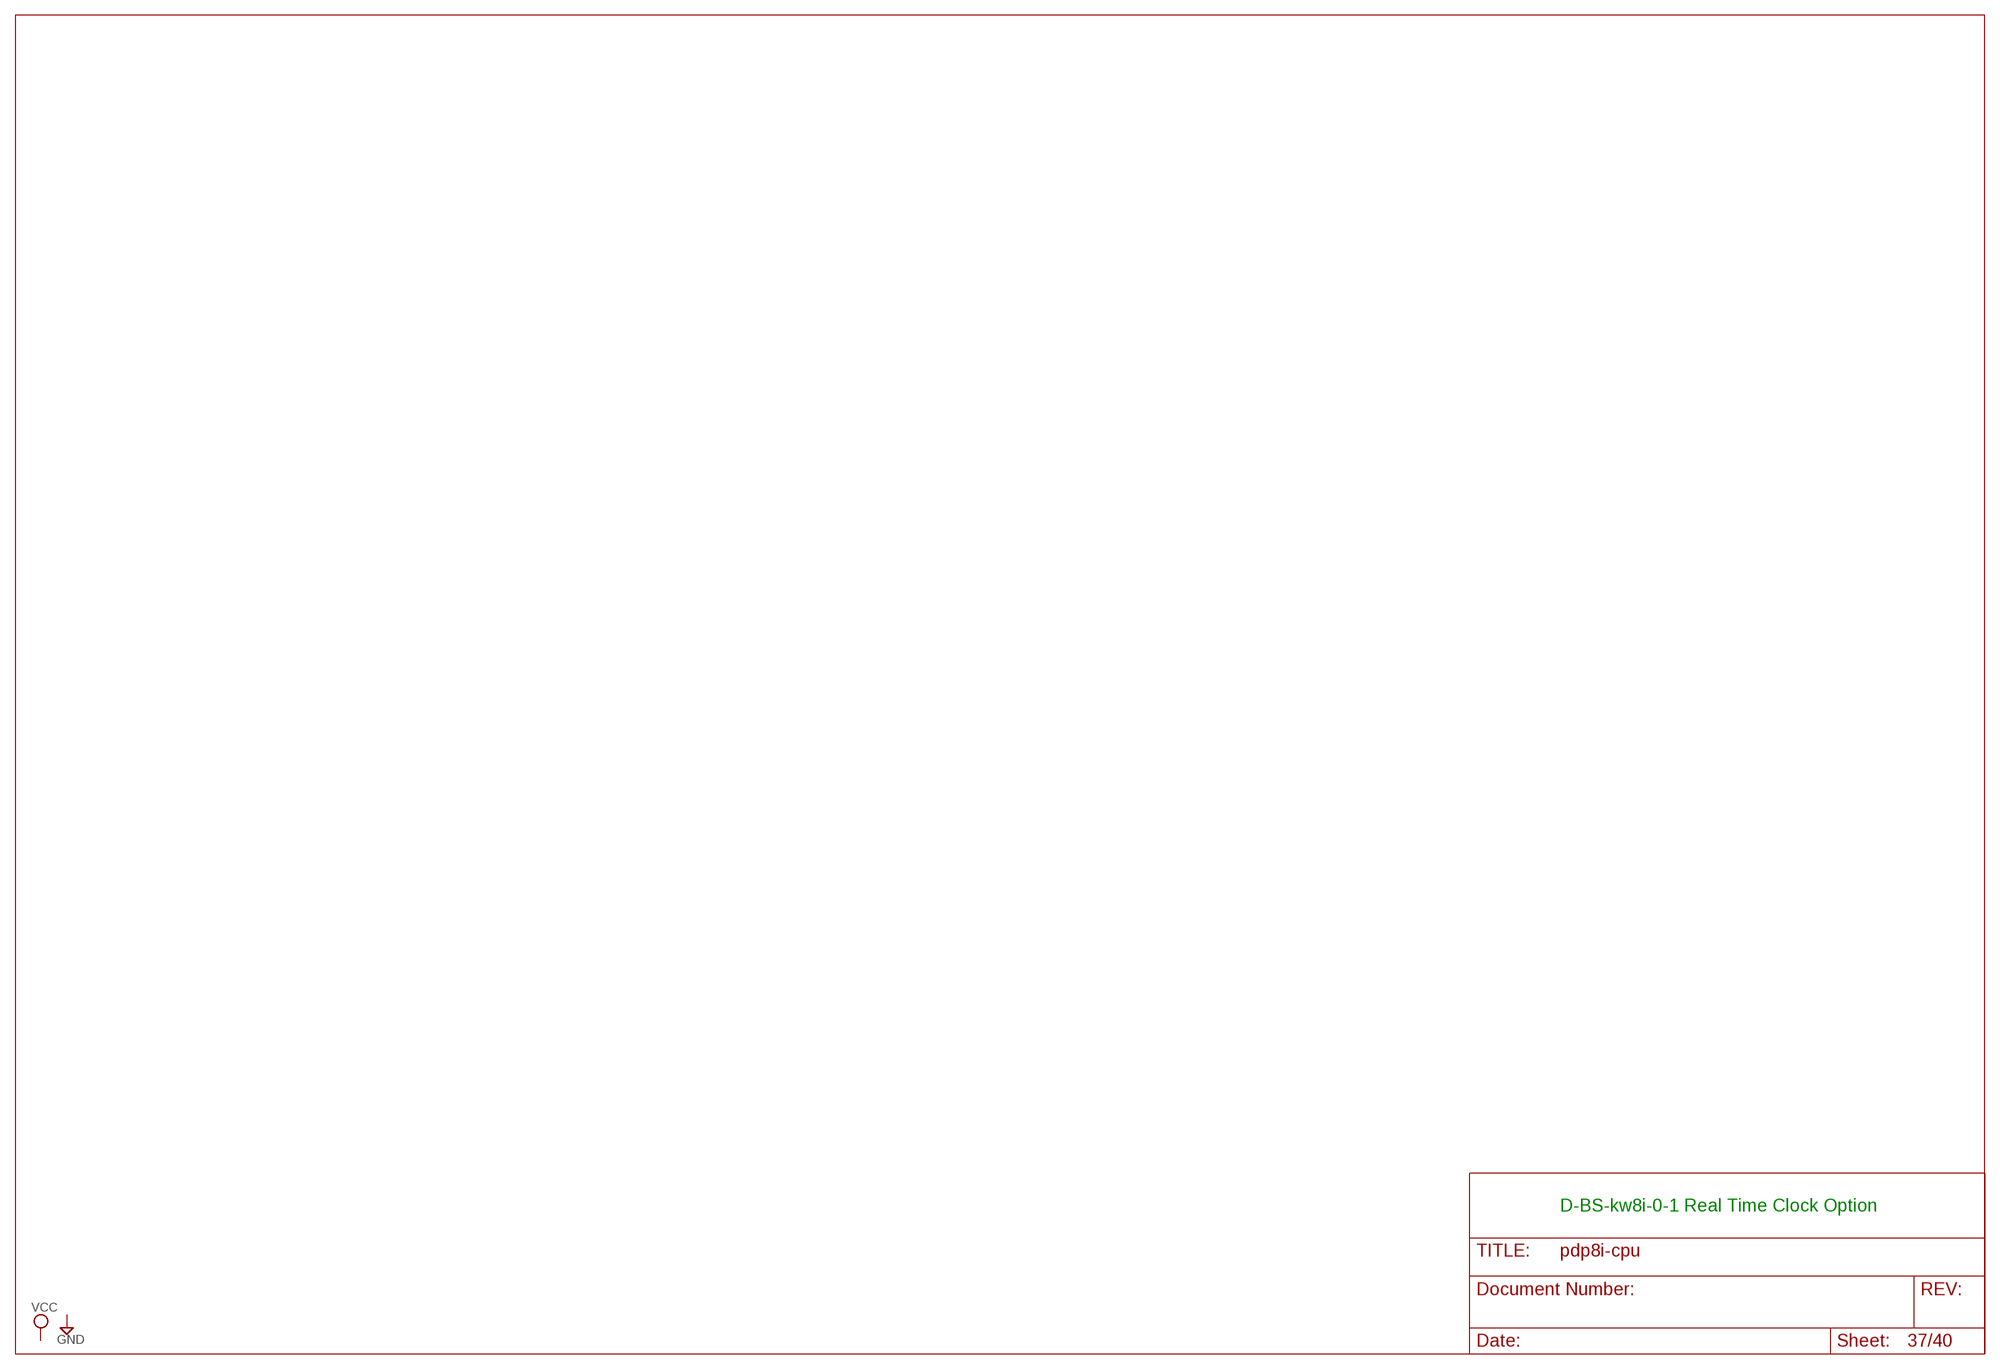
[diagram p37: schematic, sheet 37]
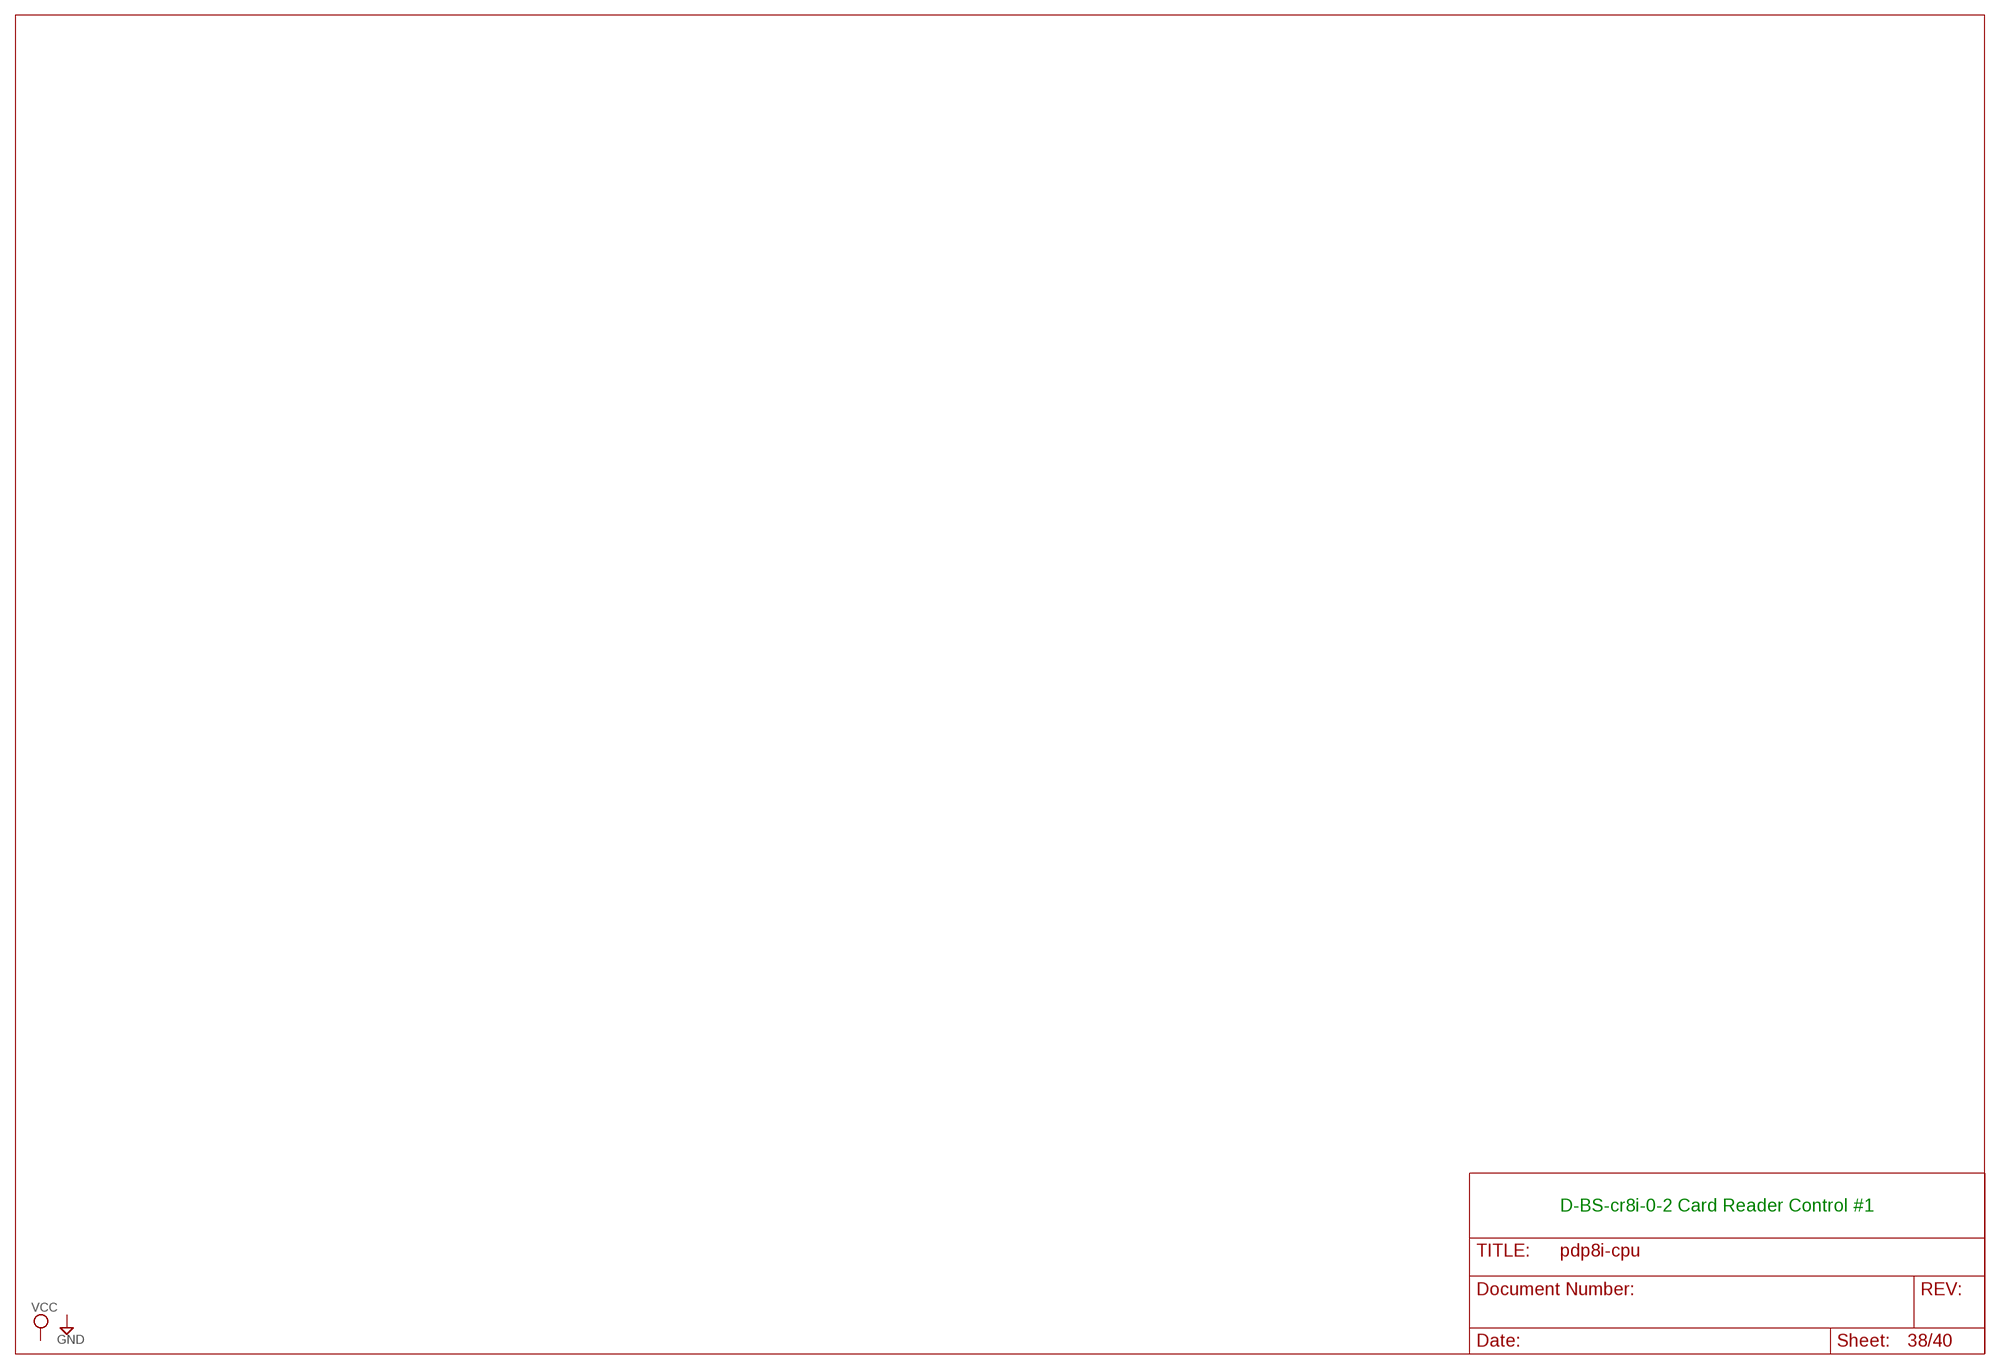
[diagram p38: schematic, sheet 38]
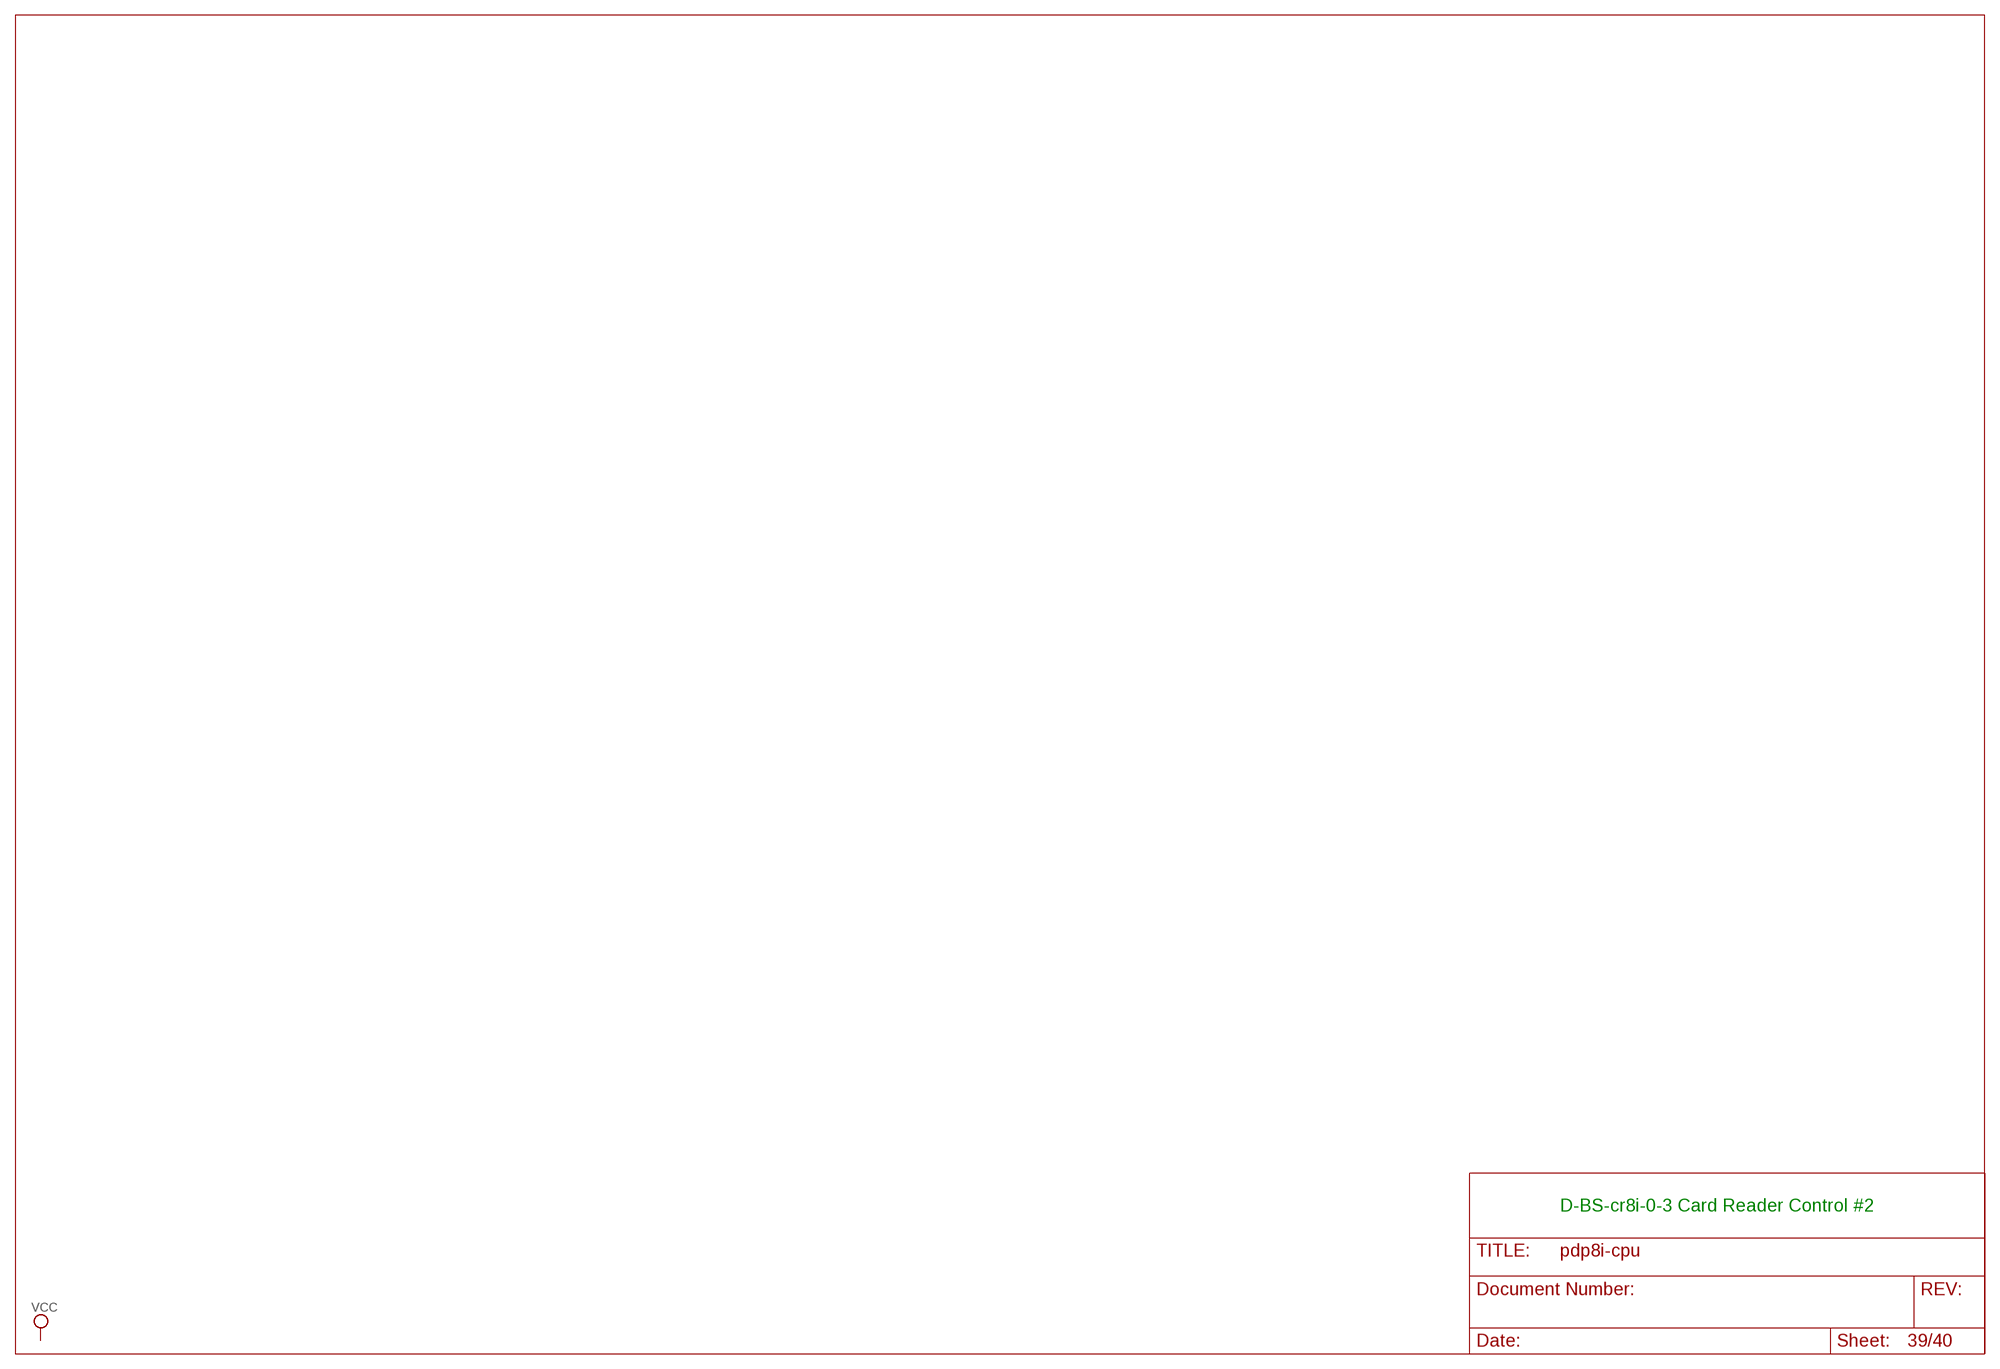
[diagram p39: schematic, sheet 39]
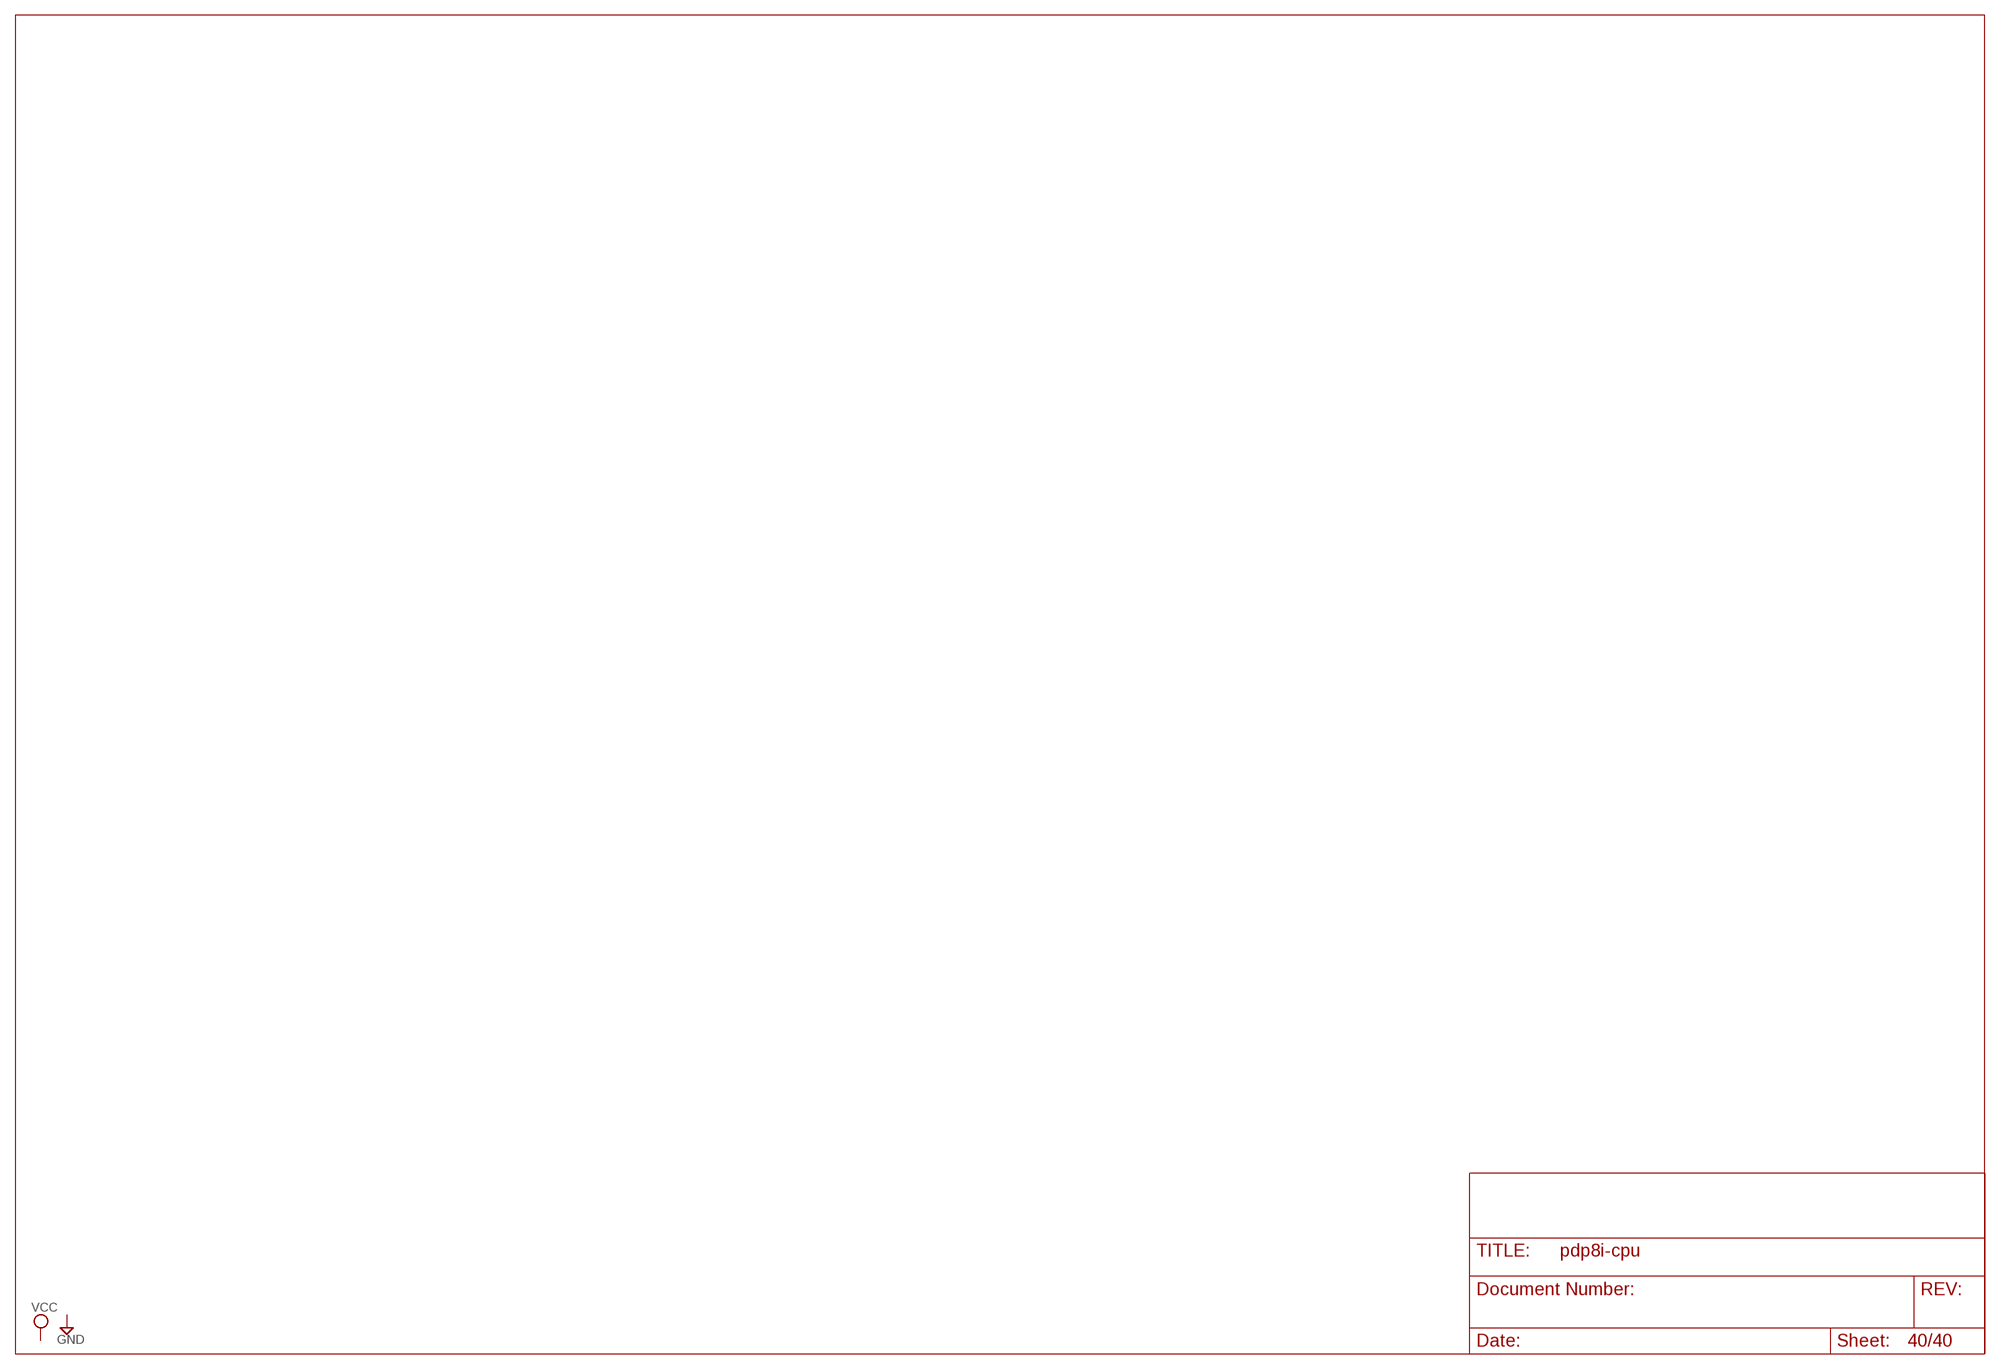
[diagram p40: schematic, sheet 40]

(export (version "E")
  (design (tool "Eeschema 10.0.6"))
  (components
    (comp (ref "A04")
      (value "M703")
      (footprint "eagle-import:H807")
      (libsource (lib "eagle-import") (part "M703"))
    )
    (comp (ref "E03")
      (value "EMPTY")
      (footprint "eagle-import:H807")
      (libsource (lib "eagle-import") (part "EMPTY"))
    )
    (comp (ref "E04")
      (value "EMPTY")
      (footprint "eagle-import:H807")
      (libsource (lib "eagle-import") (part "EMPTY"))
    )
    (comp (ref "E05")
      (value "EMPTY")
      (footprint "eagle-import:H807")
      (libsource (lib "eagle-import") (part "EMPTY"))
    )
    (comp (ref "E06")
      (value "EMPTY")
      (footprint "eagle-import:H807")
      (libsource (lib "eagle-import") (part "EMPTY"))
    )
    (comp (ref "E07")
      (value "EMPTY")
      (footprint "eagle-import:H807")
      (libsource (lib "eagle-import") (part "EMPTY"))
    )
    (comp (ref "E08")
      (value "EMPTY")
      (footprint "eagle-import:H807")
      (libsource (lib "eagle-import") (part "EMPTY"))
    )
    (comp (ref "E31")
      (value "M617")
      (footprint "eagle-import:H807")
      (libsource (lib "eagle-import") (part "M617"))
    )
    (comp (ref "E32")
      (value "M617")
      (footprint "eagle-import:H807")
      (libsource (lib "eagle-import") (part "M617"))
    )
    (comp (ref "EF10")
      (value "M700")
      (footprint "eagle-import:H807-2")
      (libsource (lib "eagle-import") (part "M700"))
    )
    (comp (ref "F04")
      (value "EMPTY")
      (footprint "eagle-import:H807")
      (libsource (lib "eagle-import") (part "EMPTY"))
    )
    (comp (ref "F05")
      (value "EMPTY")
      (footprint "eagle-import:H807")
      (libsource (lib "eagle-import") (part "EMPTY"))
    )
    (comp (ref "F06")
      (value "EMPTY")
      (footprint "eagle-import:H807")
      (libsource (lib "eagle-import") (part "EMPTY"))
    )
    (comp (ref "F07")
      (value "EMPTY")
      (footprint "eagle-import:H807")
      (libsource (lib "eagle-import") (part "EMPTY"))
    )
    (comp (ref "F11")
      (value "M117")
      (footprint "eagle-import:H807")
      (libsource (lib "eagle-import") (part "M117"))
    )
    (comp (ref "F20")
      (value "M113")
      (footprint "eagle-import:H807")
      (libsource (lib "eagle-import") (part "M113"))
    )
    (comp (ref "F21")
      (value "M113")
      (footprint "eagle-import:H807")
      (libsource (lib "eagle-import") (part "M113"))
    )
    (comp (ref "F22")
      (value "M113")
      (footprint "eagle-import:H807")
      (libsource (lib "eagle-import") (part "M113"))
    )
    (comp (ref "F23")
      (value "M117")
      (footprint "eagle-import:H807")
      (libsource (lib "eagle-import") (part "M117"))
    )
    (comp (ref "F27")
      (value "M117")
      (footprint "eagle-import:H807")
      (libsource (lib "eagle-import") (part "M117"))
    )
    (comp (ref "F29")
      (value "M113")
      (footprint "eagle-import:H807")
      (libsource (lib "eagle-import") (part "M113"))
    )
    (comp (ref "F30")
      (value "M617")
      (footprint "eagle-import:H807")
      (libsource (lib "eagle-import") (part "M617"))
    )
    (comp (ref "F31")
      (value "M617")
      (footprint "eagle-import:H807")
      (libsource (lib "eagle-import") (part "M617"))
    )
    (comp (ref "H06")
      (value "EMPTY")
      (footprint "eagle-import:H807")
      (libsource (lib "eagle-import") (part "EMPTY"))
    )
    (comp (ref "H21")
      (value "EMPTY")
      (footprint "eagle-import:H807")
      (libsource (lib "eagle-import") (part "EMPTY"))
    )
    (comp (ref "H22")
      (value "EMPTY")
      (footprint "eagle-import:H807")
      (libsource (lib "eagle-import") (part "EMPTY"))
    )
    (comp (ref "H33")
      (value "EMPTY")
      (footprint "eagle-import:H807")
      (libsource (lib "eagle-import") (part "EMPTY"))
    )
    (comp (ref "H35")
      (value "EMPTY")
      (footprint "eagle-import:H807")
      (libsource (lib "eagle-import") (part "EMPTY"))
    )
    (comp (ref "H36")
      (value "EMPTY")
      (footprint "eagle-import:H807")
      (libsource (lib "eagle-import") (part "EMPTY"))
    )
    (comp (ref "H37")
      (value "EMPTY")
      (footprint "eagle-import:H807")
      (libsource (lib "eagle-import") (part "EMPTY"))
    )
    (comp (ref "H38")
      (value "EMPTY")
      (footprint "eagle-import:H807")
      (libsource (lib "eagle-import") (part "EMPTY"))
    )
    (comp (ref "H39")
      (value "EMPTY")
      (footprint "eagle-import:H807")
      (libsource (lib "eagle-import") (part "EMPTY"))
    )
    (comp (ref "H40")
      (value "EMPTY")
      (footprint "eagle-import:H807")
      (libsource (lib "eagle-import") (part "EMPTY"))
    )
    (comp (ref "J11")
      (value "W011")
      (footprint "eagle-import:H807")
      (libsource (lib "eagle-import") (part "W011"))
    )
    (comp (ref "J21")
      (value "EMPTY")
      (footprint "eagle-import:H807")
      (libsource (lib "eagle-import") (part "EMPTY"))
    )
    (comp (ref "J22")
      (value "EMPTY")
      (footprint "eagle-import:H807")
      (libsource (lib "eagle-import") (part "EMPTY"))
    )
    (comp (ref "J35")
      (value "EMPTY")
      (footprint "eagle-import:H807")
      (libsource (lib "eagle-import") (part "EMPTY"))
    )
    (comp (ref "J36")
      (value "EMPTY")
      (footprint "eagle-import:H807")
      (libsource (lib "eagle-import") (part "EMPTY"))
    )
    (comp (ref "J37")
      (value "EMPTY")
      (footprint "eagle-import:H807")
      (libsource (lib "eagle-import") (part "EMPTY"))
    )
    (comp (ref "J38")
      (value "EMPTY")
      (footprint "eagle-import:H807")
      (libsource (lib "eagle-import") (part "EMPTY"))
    )
    (comp (ref "J39")
      (value "EMPTY")
      (footprint "eagle-import:H807")
      (libsource (lib "eagle-import") (part "EMPTY"))
    )
    (comp (ref "J40")
      (value "EMPTY")
      (footprint "eagle-import:H807")
      (libsource (lib "eagle-import") (part "EMPTY"))
    )
    (comp (ref "E18")
      (value "M216")
      (footprint "eagle-import:H807")
      (libsource (lib "eagle-import") (part "M206X"))
    )
    (comp (ref "E24")
      (value "M113")
      (footprint "eagle-import:H807")
      (libsource (lib "eagle-import") (part "M113"))
    )
    (comp (ref "E25")
      (value "M115")
      (footprint "eagle-import:H807")
      (libsource (lib "eagle-import") (part "M115"))
    )
    (comp (ref "E26")
      (value "M160")
      (footprint "eagle-import:H807")
      (libsource (lib "eagle-import") (part "M160"))
    )
    (comp (ref "E28")
      (value "M160")
      (footprint "eagle-import:H807")
      (libsource (lib "eagle-import") (part "M160"))
    )
    (comp (ref "F24")
      (value "M117")
      (footprint "eagle-import:H807")
      (libsource (lib "eagle-import") (part "M117"))
    )
    (comp (ref "F25")
      (value "M113")
      (footprint "eagle-import:H807")
      (libsource (lib "eagle-import") (part "M113"))
    )
    (comp (ref "F26")
      (value "M115")
      (footprint "eagle-import:H807")
      (libsource (lib "eagle-import") (part "M115"))
    )
    (comp (ref "F32")
      (value "M113")
      (footprint "eagle-import:H807")
      (libsource (lib "eagle-import") (part "M113"))
    )
    (comp (ref "A05")
      (value "M113")
      (footprint "eagle-import:H807")
      (libsource (lib "eagle-import") (part "M113"))
    )
    (comp (ref "B04")
      (value "M115")
      (footprint "eagle-import:H807")
      (libsource (lib "eagle-import") (part "M115"))
    )
    (comp (ref "B05")
      (value "M216")
      (footprint "eagle-import:H807")
      (libsource (lib "eagle-import") (part "M216"))
    )
    (comp (ref "B06")
      (value "M113")
      (footprint "eagle-import:H807")
      (libsource (lib "eagle-import") (part "M113"))
    )
    (comp (ref "C40")
      (value "M900")
      (footprint "eagle-import:H807")
      (libsource (lib "eagle-import") (part "M916"))
    )
    (comp (ref "E33")
      (value "M216")
      (footprint "eagle-import:H807")
      (libsource (lib "eagle-import") (part "M206X"))
    )
    (comp (ref "E40")
      (value "M900")
      (footprint "eagle-import:H807")
      (libsource (lib "eagle-import") (part "M916"))
    )
    (comp (ref "EF34")
      (value "M220")
      (footprint "eagle-import:H807-2")
      (libsource (lib "eagle-import") (part "M220"))
    )
    (comp (ref "EF35")
      (value "M220")
      (footprint "eagle-import:H807-2")
      (libsource (lib "eagle-import") (part "M220"))
    )
    (comp (ref "EF36")
      (value "M220")
      (footprint "eagle-import:H807-2")
      (libsource (lib "eagle-import") (part "M220"))
    )
    (comp (ref "EF37")
      (value "M220")
      (footprint "eagle-import:H807-2")
      (libsource (lib "eagle-import") (part "M220"))
    )
    (comp (ref "EF38")
      (value "M220")
      (footprint "eagle-import:H807-2")
      (libsource (lib "eagle-import") (part "M220"))
    )
    (comp (ref "EF39")
      (value "M220")
      (footprint "eagle-import:H807-2")
      (libsource (lib "eagle-import") (part "M220"))
    )
    (comp (ref "F28")
      (value "M115")
      (footprint "eagle-import:H807")
      (libsource (lib "eagle-import") (part "M115"))
    )
    (comp (ref "F33")
      (value "M160")
      (footprint "eagle-import:H807")
      (libsource (lib "eagle-import") (part "M160"))
    )
    (comp (ref "F40")
      (value "M900")
      (footprint "eagle-import:H807")
      (libsource (lib "eagle-import") (part "M916"))
    )
    (comp (ref "H04")
      (value "W011")
      (footprint "eagle-import:H807")
      (libsource (lib "eagle-import") (part "W011"))
    )
    (comp (ref "H05")
      (value "W011")
      (footprint "eagle-import:H807")
      (libsource (lib "eagle-import") (part "W011"))
    )
    (comp (ref "A07")
      (value "M162")
      (footprint "eagle-import:H807")
      (libsource (lib "eagle-import") (part "M162"))
    )
    (comp (ref "A08")
      (value "M162")
      (footprint "eagle-import:H807")
      (libsource (lib "eagle-import") (part "M162"))
    )
    (comp (ref "B08")
      (value "M113")
      (footprint "eagle-import:H807")
      (libsource (lib "eagle-import") (part "M113"))
    )
    (comp (ref "B09")
      (value "M113")
      (footprint "eagle-import:H807")
      (libsource (lib "eagle-import") (part "M113"))
    )
    (comp (ref "A06")
      (value "M113")
      (footprint "eagle-import:H807")
      (libsource (lib "eagle-import") (part "M113"))
    )
    (comp (ref "D40")
      (value "M900")
      (footprint "eagle-import:H807")
      (libsource (lib "eagle-import") (part "M916"))
    )
    (comp (ref "E20")
      (value "M216")
      (footprint "eagle-import:H807")
      (libsource (lib "eagle-import") (part "M206X"))
    )
    (comp (ref "E21")
      (value "M115")
      (footprint "eagle-import:H807")
      (libsource (lib "eagle-import") (part "M115"))
    )
    (comp (ref "E22")
      (value "M113")
      (footprint "eagle-import:H807")
      (libsource (lib "eagle-import") (part "M113"))
    )
    (comp (ref "E23")
      (value "M216")
      (footprint "eagle-import:H807")
      (libsource (lib "eagle-import") (part "M206X"))
    )
    (comp (ref "AB02")
      (value "G826")
      (footprint "eagle-import:H807-2")
      (libsource (lib "eagle-import") (part "G826"))
    )
    (comp (ref "AB03")
      (value "G792")
      (footprint "eagle-import:H807-2")
      (libsource (lib "eagle-import") (part "G792"))
    )
    (comp (ref "B21")
      (value "M113")
      (footprint "eagle-import:H807")
      (libsource (lib "eagle-import") (part "M113"))
    )
    (comp (ref "C12")
      (value "M617")
      (footprint "eagle-import:H807")
      (libsource (lib "eagle-import") (part "M617"))
    )
    (comp (ref "D06")
      (value "M310")
      (footprint "eagle-import:H807")
      (libsource (lib "eagle-import") (part "M310"))
    )
    (comp (ref "D07")
      (value "M113")
      (footprint "eagle-import:H807")
      (libsource (lib "eagle-import") (part "M113"))
    )
    (comp (ref "E09")
      (value "M113")
      (footprint "eagle-import:H807")
      (libsource (lib "eagle-import") (part "M113"))
    )
    (comp (ref "B40")
      (value "W077")
      (footprint "eagle-import:H807")
      (libsource (lib "eagle-import") (part "M916"))
    )
    (comp (ref "A13")
      (value "M113")
      (footprint "eagle-import:H807")
      (libsource (lib "eagle-import") (part "M113"))
    )
    (comp (ref "A16")
      (value "M113")
      (footprint "eagle-import:H807")
      (libsource (lib "eagle-import") (part "M113"))
    )
    (comp (ref "A19")
      (value "M113")
      (footprint "eagle-import:H807")
      (libsource (lib "eagle-import") (part "M113"))
    )
    (comp (ref "B10")
      (value "M720")
      (footprint "eagle-import:H807")
      (libsource (lib "eagle-import") (part "M720"))
    )
    (comp (ref "B11")
      (value "M216")
      (footprint "eagle-import:H807")
      (libsource (lib "eagle-import") (part "M216"))
    )
    (comp (ref "B12")
      (value "M617")
      (footprint "eagle-import:H807")
      (libsource (lib "eagle-import") (part "M617"))
    )
    (comp (ref "B13")
      (value "M617")
      (footprint "eagle-import:H807")
      (libsource (lib "eagle-import") (part "M617"))
    )
    (comp (ref "B14")
      (value "M617")
      (footprint "eagle-import:H807")
      (libsource (lib "eagle-import") (part "M617"))
    )
    (comp (ref "B15")
      (value "M617")
      (footprint "eagle-import:H807")
      (libsource (lib "eagle-import") (part "M617"))
    )
    (comp (ref "B16")
      (value "M617")
      (footprint "eagle-import:H807")
      (libsource (lib "eagle-import") (part "M617"))
    )
    (comp (ref "B18")
      (value "M216")
      (footprint "eagle-import:H807")
      (libsource (lib "eagle-import") (part "M216"))
    )
    (comp (ref "B19")
      (value "M216")
      (footprint "eagle-import:H807")
      (libsource (lib "eagle-import") (part "M216"))
    )
    (comp (ref "B20")
      (value "M115")
      (footprint "eagle-import:H807")
      (libsource (lib "eagle-import") (part "M115"))
    )
    (comp (ref "E12")
      (value "M113")
      (footprint "eagle-import:H807")
      (libsource (lib "eagle-import") (part "M113"))
    )
    (comp (ref "H01")
      (value "W011")
      (footprint "eagle-import:H807")
      (libsource (lib "eagle-import") (part "W011"))
    )
    (comp (ref "H02")
      (value "W011")
      (footprint "eagle-import:H807")
      (libsource (lib "eagle-import") (part "W011"))
    )
    (comp (ref "H03")
      (value "W011")
      (footprint "eagle-import:H807")
      (libsource (lib "eagle-import") (part "W011"))
    )
    (comp (ref "A09")
      (value "M162")
      (footprint "eagle-import:H807")
      (libsource (lib "eagle-import") (part "M162"))
    )
    (comp (ref "A10")
      (value "M162")
      (footprint "eagle-import:H807")
      (libsource (lib "eagle-import") (part "M162"))
    )
    (comp (ref "B07")
      (value "M115")
      (footprint "eagle-import:H807")
      (libsource (lib "eagle-import") (part "M115"))
    )
    (comp (ref "C07")
      (value "M661")
      (footprint "eagle-import:H807")
      (libsource (lib "eagle-import") (part "M661"))
    )
    (comp (ref "C08")
      (value "M660")
      (footprint "eagle-import:H807")
      (libsource (lib "eagle-import") (part "M660"))
    )
    (comp (ref "C09")
      (value "M113")
      (footprint "eagle-import:H807")
      (libsource (lib "eagle-import") (part "M113"))
    )
    (comp (ref "C10")
      (value "M113")
      (footprint "eagle-import:H807")
      (libsource (lib "eagle-import") (part "M113"))
    )
    (comp (ref "C11")
      (value "M115")
      (footprint "eagle-import:H807")
      (libsource (lib "eagle-import") (part "M115"))
    )
    (comp (ref "D04")
      (value "W011")
      (footprint "eagle-import:H807")
      (libsource (lib "eagle-import") (part "W011"))
    )
    (comp (ref "D05")
      (value "M516")
      (footprint "eagle-import:H807")
      (libsource (lib "eagle-import") (part "M516"))
    )
    (comp (ref "D09")
      (value "M115")
      (footprint "eagle-import:H807")
      (libsource (lib "eagle-import") (part "M115"))
    )
    (comp (ref "D10")
      (value "M117")
      (footprint "eagle-import:H807")
      (libsource (lib "eagle-import") (part "M117"))
    )
    (comp (ref "D11")
      (value "M216")
      (footprint "eagle-import:H807")
      (libsource (lib "eagle-import") (part "M216"))
    )
    (comp (ref "H07")
      (value "M650")
      (footprint "eagle-import:H807")
      (libsource (lib "eagle-import") (part "M650"))
    )
    (comp (ref "H08")
      (value "M650")
      (footprint "eagle-import:H807")
      (libsource (lib "eagle-import") (part "M650"))
    )
    (comp (ref "H09")
      (value "M650")
      (footprint "eagle-import:H807")
      (libsource (lib "eagle-import") (part "M650"))
    )
    (comp (ref "H10")
      (value "M650")
      (footprint "eagle-import:H807")
      (libsource (lib "eagle-import") (part "M650"))
    )
    (comp (ref "H11")
      (value "M650")
      (footprint "eagle-import:H807")
      (libsource (lib "eagle-import") (part "M650"))
    )
    (comp (ref "H12")
      (value "M650")
      (footprint "eagle-import:H807")
      (libsource (lib "eagle-import") (part "M650"))
    )
    (comp (ref "H13")
      (value "M650")
      (footprint "eagle-import:H807")
      (libsource (lib "eagle-import") (part "M650"))
    )
    (comp (ref "H14")
      (value "M650")
      (footprint "eagle-import:H807")
      (libsource (lib "eagle-import") (part "M650"))
    )
    (comp (ref "H15")
      (value "M650")
      (footprint "eagle-import:H807")
      (libsource (lib "eagle-import") (part "M650"))
    )
    (comp (ref "H16")
      (value "M650")
      (footprint "eagle-import:H807")
      (libsource (lib "eagle-import") (part "M650"))
    )
    (comp (ref "H17")
      (value "M650")
      (footprint "eagle-import:H807")
      (libsource (lib "eagle-import") (part "M650"))
    )
    (comp (ref "H18")
      (value "M650")
      (footprint "eagle-import:H807")
      (libsource (lib "eagle-import") (part "M650"))
    )
    (comp (ref "H19")
      (value "M650")
      (footprint "eagle-import:H807")
      (libsource (lib "eagle-import") (part "M650"))
    )
    (comp (ref "H20")
      (value "M650")
      (footprint "eagle-import:H807")
      (libsource (lib "eagle-import") (part "M650"))
    )
    (comp (ref "J01")
      (value "W011")
      (footprint "eagle-import:H807")
      (libsource (lib "eagle-import") (part "W011"))
    )
    (comp (ref "J02")
      (value "W011")
      (footprint "eagle-import:H807")
      (libsource (lib "eagle-import") (part "W011"))
    )
    (comp (ref "J03")
      (value "W011")
      (footprint "eagle-import:H807")
      (libsource (lib "eagle-import") (part "W011"))
    )
    (comp (ref "J04")
      (value "W011")
      (footprint "eagle-import:H807")
      (libsource (lib "eagle-import") (part "W011"))
    )
    (comp (ref "J05")
      (value "W011")
      (footprint "eagle-import:H807")
      (libsource (lib "eagle-import") (part "W011"))
    )
    (comp (ref "J06")
      (value "W011")
      (footprint "eagle-import:H807")
      (libsource (lib "eagle-import") (part "W011"))
    )
    (comp (ref "J07")
      (value "W011")
      (footprint "eagle-import:H807")
      (libsource (lib "eagle-import") (part "W011"))
    )
    (comp (ref "J08")
      (value "W011")
      (footprint "eagle-import:H807")
      (libsource (lib "eagle-import") (part "W011"))
    )
    (comp (ref "J09")
      (value "W011")
      (footprint "eagle-import:H807")
      (libsource (lib "eagle-import") (part "W011"))
    )
    (comp (ref "J10")
      (value "W011")
      (footprint "eagle-import:H807")
      (libsource (lib "eagle-import") (part "W011"))
    )
    (comp (ref "J13")
      (value "M506")
      (footprint "eagle-import:H807")
      (libsource (lib "eagle-import") (part "M506"))
    )
    (comp (ref "J14")
      (value "M506")
      (footprint "eagle-import:H807")
      (libsource (lib "eagle-import") (part "M506"))
    )
    (comp (ref "J15")
      (value "M506")
      (footprint "eagle-import:H807")
      (libsource (lib "eagle-import") (part "M506"))
    )
    (comp (ref "J16")
      (value "M506")
      (footprint "eagle-import:H807")
      (libsource (lib "eagle-import") (part "M506"))
    )
    (comp (ref "J17")
      (value "M506")
      (footprint "eagle-import:H807")
      (libsource (lib "eagle-import") (part "M506"))
    )
    (comp (ref "J18")
      (value "M506")
      (footprint "eagle-import:H807")
      (libsource (lib "eagle-import") (part "M506"))
    )
    (comp (ref "J19")
      (value "M506")
      (footprint "eagle-import:H807")
      (libsource (lib "eagle-import") (part "M506"))
    )
    (comp (ref "J20")
      (value "M506")
      (footprint "eagle-import:H807")
      (libsource (lib "eagle-import") (part "M506"))
    )
    (comp (ref "A40")
      (value "W077")
      (footprint "eagle-import:H807")
      (libsource (lib "eagle-import") (part "M916"))
    )
    (comp (ref "E11")
      (value "M113")
      (footprint "eagle-import:H807")
      (libsource (lib "eagle-import") (part "M113"))
    )
    (comp (ref "E14")
      (value "M115")
      (footprint "eagle-import:H807")
      (libsource (lib "eagle-import") (part "M115"))
    )
    (comp (ref "E29")
      (value "M160")
      (footprint "eagle-import:H807")
      (libsource (lib "eagle-import") (part "M160"))
    )
    (comp (ref "E30")
      (value "M160")
      (footprint "eagle-import:H807")
      (libsource (lib "eagle-import") (part "M160"))
    )
    (comp (ref "F09")
      (value "M119")
      (footprint "eagle-import:H807")
      (libsource (lib "eagle-import") (part "M119"))
    )
    (comp (ref "E27")
      (value "M160")
      (footprint "eagle-import:H807")
      (libsource (lib "eagle-import") (part "M160"))
    )
    (comp (ref "A11")
      (value "M113")
      (footprint "eagle-import:H807")
      (libsource (lib "eagle-import") (part "M113"))
    )
    (comp (ref "A12")
      (value "M113")
      (footprint "eagle-import:H807")
      (libsource (lib "eagle-import") (part "M113"))
    )
    (comp (ref "A14")
      (value "M113")
      (footprint "eagle-import:H807")
      (libsource (lib "eagle-import") (part "M113"))
    )
    (comp (ref "A15")
      (value "M113")
      (footprint "eagle-import:H807")
      (libsource (lib "eagle-import") (part "M113"))
    )
    (comp (ref "A17")
      (value "M113")
      (footprint "eagle-import:H807")
      (libsource (lib "eagle-import") (part "M113"))
    )
    (comp (ref "A18")
      (value "M113")
      (footprint "eagle-import:H807")
      (libsource (lib "eagle-import") (part "M113"))
    )
    (comp (ref "A20")
      (value "M115")
      (footprint "eagle-import:H807")
      (libsource (lib "eagle-import") (part "M115"))
    )
    (comp (ref "B17")
      (value "M216")
      (footprint "eagle-import:H807")
      (libsource (lib "eagle-import") (part "M216"))
    )
    (comp (ref "C14")
      (value "M113")
      (footprint "eagle-import:H807")
      (libsource (lib "eagle-import") (part "M113"))
    )
    (comp (ref "C15")
      (value "M113")
      (footprint "eagle-import:H807")
      (libsource (lib "eagle-import") (part "M113"))
    )
    (comp (ref "C16")
      (value "M113")
      (footprint "eagle-import:H807")
      (libsource (lib "eagle-import") (part "M113"))
    )
    (comp (ref "C17")
      (value "M113")
      (footprint "eagle-import:H807")
      (libsource (lib "eagle-import") (part "M113"))
    )
    (comp (ref "C18")
      (value "M113")
      (footprint "eagle-import:H807")
      (libsource (lib "eagle-import") (part "M113"))
    )
    (comp (ref "C19")
      (value "M115")
      (footprint "eagle-import:H807")
      (libsource (lib "eagle-import") (part "M115"))
    )
    (comp (ref "C20")
      (value "M115")
      (footprint "eagle-import:H807")
      (libsource (lib "eagle-import") (part "M115"))
    )
    (comp (ref "C21")
      (value "M115")
      (footprint "eagle-import:H807")
      (libsource (lib "eagle-import") (part "M115"))
    )
    (comp (ref "C22")
      (value "M216")
      (footprint "eagle-import:H807")
      (libsource (lib "eagle-import") (part "M216"))
    )
    (comp (ref "C23")
      (value "M216")
      (footprint "eagle-import:H807")
      (libsource (lib "eagle-import") (part "M216"))
    )
    (comp (ref "C24")
      (value "M216")
      (footprint "eagle-import:H807")
      (libsource (lib "eagle-import") (part "M216"))
    )
    (comp (ref "D12")
      (value "M113")
      (footprint "eagle-import:H807")
      (libsource (lib "eagle-import") (part "M113"))
    )
    (comp (ref "D19")
      (value "M115")
      (footprint "eagle-import:H807")
      (libsource (lib "eagle-import") (part "M115"))
    )
    (comp (ref "D22")
      (value "M617")
      (footprint "eagle-import:H807")
      (libsource (lib "eagle-import") (part "M617"))
    )
    (comp (ref "D23")
      (value "M160")
      (footprint "eagle-import:H807")
      (libsource (lib "eagle-import") (part "M160"))
    )
    (comp (ref "F19")
      (value "M117")
      (footprint "eagle-import:H807")
      (libsource (lib "eagle-import") (part "M117"))
    )
    (comp (ref "E13")
      (value "M160")
      (footprint "eagle-import:H807")
      (libsource (lib "eagle-import") (part "M160"))
    )
    (comp (ref "E15")
      (value "M113")
      (footprint "eagle-import:H807")
      (libsource (lib "eagle-import") (part "M113"))
    )
    (comp (ref "E16")
      (value "M310")
      (footprint "eagle-import:H807")
      (libsource (lib "eagle-import") (part "M310"))
    )
    (comp (ref "E17")
      (value "M310")
      (footprint "eagle-import:H807")
      (libsource (lib "eagle-import") (part "M310"))
    )
    (comp (ref "E19")
      (value "M216")
      (footprint "eagle-import:H807")
      (libsource (lib "eagle-import") (part "M206X"))
    )
    (comp (ref "F08")
      (value "M660")
      (footprint "eagle-import:H807")
      (libsource (lib "eagle-import") (part "M660"))
    )
    (comp (ref "F12")
      (value "M310")
      (footprint "eagle-import:H807")
      (libsource (lib "eagle-import") (part "M310"))
    )
    (comp (ref "F13")
      (value "M310")
      (footprint "eagle-import:H807")
      (libsource (lib "eagle-import") (part "M310"))
    )
    (comp (ref "F14")
      (value "M310")
      (footprint "eagle-import:H807")
      (libsource (lib "eagle-import") (part "M310"))
    )
    (comp (ref "F15")
      (value "M310")
      (footprint "eagle-import:H807")
      (libsource (lib "eagle-import") (part "M310"))
    )
    (comp (ref "F16")
      (value "M310")
      (footprint "eagle-import:H807")
      (libsource (lib "eagle-import") (part "M310"))
    )
    (comp (ref "F17")
      (value "M310")
      (footprint "eagle-import:H807")
      (libsource (lib "eagle-import") (part "M310"))
    )
    (comp (ref "F18")
      (value "M310")
      (footprint "eagle-import:H807")
      (libsource (lib "eagle-import") (part "M310"))
    )
    (comp (ref "C13")
      (value "M310")
      (footprint "eagle-import:H807")
      (libsource (lib "eagle-import") (part "M310"))
    )
    (comp (ref "D13")
      (value "M113")
      (footprint "eagle-import:H807")
      (libsource (lib "eagle-import") (part "M113"))
    )
    (comp (ref "D14")
      (value "M113")
      (footprint "eagle-import:H807")
      (libsource (lib "eagle-import") (part "M113"))
    )
    (comp (ref "D15")
      (value "M113")
      (footprint "eagle-import:H807")
      (libsource (lib "eagle-import") (part "M113"))
    )
    (comp (ref "D16")
      (value "M113")
      (footprint "eagle-import:H807")
      (libsource (lib "eagle-import") (part "M113"))
    )
    (comp (ref "D17")
      (value "M115")
      (footprint "eagle-import:H807")
      (libsource (lib "eagle-import") (part "M115"))
    )
    (comp (ref "D18")
      (value "M115")
      (footprint "eagle-import:H807")
      (libsource (lib "eagle-import") (part "M115"))
    )
    (comp (ref "D20")
      (value "M117")
      (footprint "eagle-import:H807")
      (libsource (lib "eagle-import") (part "M117"))
    )
    (comp (ref "D21")
      (value "M117")
      (footprint "eagle-import:H807")
      (libsource (lib "eagle-import") (part "M117"))
    )
    (comp (ref "D24")
      (value "M216")
      (footprint "eagle-import:H807")
      (libsource (lib "eagle-import") (part "M216"))
    )
  )
  (nets
    (net (code "1") (name "+3V(01)") (class "Default")
      (node (ref "A13") (pin "E1") (pinfunction "IN2_E1") (pintype "input"))
      (node (ref "A13") (pin "H1") (pinfunction "IN1_H1") (pintype "input"))
      (node (ref "A13") (pin "M1") (pinfunction "IN2_M1") (pintype "input"))
      (node (ref "A13") (pin "R1") (pinfunction "IN2_R1") (pintype "input"))
      (node (ref "A15") (pin "U1") (pinfunction "P$1_U1") (pintype "passive"))
    )
    (net (code "2") (name "+3V(02)") (class "Default")
      (node (ref "A13") (pin "U2") (pinfunction "IN2_U2") (pintype "input"))
      (node (ref "A14") (pin "B1") (pinfunction "IN2_B1") (pintype "input"))
      (node (ref "A14") (pin "H2") (pinfunction "IN1_H2") (pintype "input"))
      (node (ref "A14") (pin "J1") (pinfunction "IN2_J1") (pintype "input"))
      (node (ref "A14") (pin "L1") (pinfunction "IN1_L1") (pintype "input"))
      (node (ref "A15") (pin "V1") (pinfunction "P$1_V1") (pintype "passive"))
    )
    (net (code "3") (name "+3V(03)") (class "Default")
      (node (ref "A14") (pin "L2") (pinfunction "IN1_L2") (pintype "input"))
      (node (ref "A14") (pin "P1") (pinfunction "IN1_P1") (pintype "input"))
      (node (ref "A15") (pin "B1") (pinfunction "IN2_B1") (pintype "input"))
      (node (ref "A15") (pin "M2") (pinfunction "IN2_M2") (pintype "input"))
      (node (ref "A15") (pin "P1") (pinfunction "IN1_P1") (pintype "input"))
      (node (ref "A18") (pin "U1") (pinfunction "P$1_U1") (pintype "passive"))
    )
    (net (code "4") (name "+3V(04)") (class "Default")
      (node (ref "A18") (pin "V1") (pinfunction "P$1_V1") (pintype "passive"))
      (node (ref "A19") (pin "D1") (pinfunction "IN1_D1") (pintype "input"))
      (node (ref "A19") (pin "D2") (pinfunction "IN1_D2") (pintype "input"))
      (node (ref "A19") (pin "L2") (pinfunction "IN1_L2") (pintype "input"))
      (node (ref "A19") (pin "T2") (pinfunction "IN1_T2") (pintype "input"))
    )
    (net (code "5") (name "+3V(05)") (class "Default")
      (node (ref "A10") (pin "D1") (pinfunction "8B_D1") (pintype "input"))
      (node (ref "B08") (pin "B1") (pinfunction "IN2_B1") (pintype "input"))
      (node (ref "B08") (pin "E1") (pinfunction "IN2_E1") (pintype "input"))
      (node (ref "B08") (pin "E2") (pinfunction "IN2_E2") (pintype "input"))
      (node (ref "B08") (pin "J1") (pinfunction "IN2_J1") (pintype "input"))
      (node (ref "B08") (pin "J2") (pinfunction "IN2_J2") (pintype "input"))
      (node (ref "B08") (pin "M1") (pinfunction "IN2_M1") (pintype "input"))
      (node (ref "B08") (pin "M2") (pinfunction "IN2_M2") (pintype "input"))
      (node (ref "B08") (pin "U1") (pinfunction "P$1_U1") (pintype "passive"))
    )
    (net (code "6") (name "+3V(06)") (class "Default")
      (node (ref "B08") (pin "R1") (pinfunction "IN2_R1") (pintype "input"))
      (node (ref "B08") (pin "R2") (pinfunction "IN2_R2") (pintype "input"))
      (node (ref "B08") (pin "U2") (pinfunction "IN2_U2") (pintype "input"))
      (node (ref "B09") (pin "B1") (pinfunction "IN2_B1") (pintype "input"))
      (node (ref "B09") (pin "D2") (pinfunction "IN1_D2") (pintype "input"))
      (node (ref "B09") (pin "E1") (pinfunction "IN2_E1") (pintype "input"))
      (node (ref "B09") (pin "H2") (pinfunction "IN1_H2") (pintype "input"))
      (node (ref "B09") (pin "R1") (pinfunction "IN2_R1") (pintype "input"))
      (node (ref "B09") (pin "U1") (pinfunction "P$1_U1") (pintype "passive"))
    )
    (net (code "7") (name "+3V(07)") (class "Default")
      (node (ref "B07") (pin "F1") (pinfunction "IN2_F1") (pintype "input"))
      (node (ref "B07") (pin "K1") (pinfunction "IN1_K1") (pintype "input"))
      (node (ref "B07") (pin "P2") (pinfunction "IN2_P2") (pintype "input"))
      (node (ref "B07") (pin "R2") (pinfunction "IN3_R2") (pintype "input"))
      (node (ref "B09") (pin "J1") (pinfunction "IN2_J1") (pintype "input"))
      (node (ref "B09") (pin "M2") (pinfunction "IN2_M2") (pintype "input"))
      (node (ref "B09") (pin "V1") (pinfunction "P$1_V1") (pintype "passive"))
      (node (ref "B11") (pin "K2") (pinfunction "R_K2") (pintype "input"))
    )
    (net (code "8") (name "+3V(08)") (class "Default")
      (node (ref "B11") (pin "A1") (pinfunction "R_A1") (pintype "input"))
      (node (ref "B12") (pin "B1") (pinfunction "IN2_B1") (pintype "input"))
      (node (ref "B12") (pin "C1") (pinfunction "IN3_C1") (pintype "input"))
      (node (ref "B12") (pin "D1") (pinfunction "IN4_D1") (pintype "input"))
      (node (ref "B12") (pin "E2") (pinfunction "IN2_E2") (pintype "input"))
      (node (ref "B12") (pin "F2") (pinfunction "IN3_F2") (pintype "input"))
      (node (ref "B12") (pin "H1") (pinfunction "IN2_H1") (pintype "input"))
      (node (ref "B12") (pin "H2") (pinfunction "IN4_H2") (pintype "input"))
      (node (ref "B12") (pin "J1") (pinfunction "IN3_J1") (pintype "input"))
      (node (ref "B12") (pin "K1") (pinfunction "IN4_K1") (pintype "input"))
      (node (ref "C12") (pin "V1") (pinfunction "P$1_V1") (pintype "passive"))
    )
    (net (code "9") (name "+3V(09)") (class "Default")
      (node (ref "A11") (pin "V1") (pinfunction "P$1_V1") (pintype "passive"))
      (node (ref "B12") (pin "L2") (pinfunction "IN2_L2") (pintype "input"))
      (node (ref "B12") (pin "M2") (pinfunction "IN3_M2") (pintype "input"))
      (node (ref "B12") (pin "N1") (pinfunction "IN2_N1") (pintype "input"))
      (node (ref "B12") (pin "N2") (pinfunction "IN4_N2") (pintype "input"))
      (node (ref "B12") (pin "P1") (pinfunction "IN3_P1") (pintype "input"))
      (node (ref "B12") (pin "R1") (pinfunction "IN4_R1") (pintype "input"))
    )
    (net (code "10") (name "+3V(10)") (class "Default")
      (node (ref "B12") (pin "S2") (pinfunction "IN2_S2") (pintype "input"))
      (node (ref "B12") (pin "T2") (pinfunction "IN3_T2") (pintype "input"))
      (node (ref "B12") (pin "U2") (pinfunction "IN4_U2") (pintype "input"))
      (node (ref "B13") (pin "B1") (pinfunction "IN2_B1") (pintype "input"))
      (node (ref "B13") (pin "C1") (pinfunction "IN3_C1") (pintype "input"))
      (node (ref "B13") (pin "D1") (pinfunction "IN4_D1") (pintype "input"))
      (node (ref "B13") (pin "E2") (pinfunction "IN2_E2") (pintype "input"))
      (node (ref "B13") (pin "F2") (pinfunction "IN3_F2") (pintype "input"))
      (node (ref "B13") (pin "H2") (pinfunction "IN4_H2") (pintype "input"))
      (node (ref "F09") (pin "V1") (pinfunction "P$1_V1") (pintype "passive"))
    )
    (net (code "11") (name "+3V(11)") (class "Default")
      (node (ref "A13") (pin "U1") (pinfunction "P$1_U1") (pintype "passive"))
      (node (ref "B13") (pin "H1") (pinfunction "IN2_H1") (pintype "input"))
      (node (ref "B13") (pin "J1") (pinfunction "IN3_J1") (pintype "input"))
      (node (ref "B13") (pin "K1") (pinfunction "IN4_K1") (pintype "input"))
    )
    (net (code "12") (name "+3V(12)") (class "Default")
      (node (ref "B13") (pin "L2") (pinfunction "IN2_L2") (pintype "input"))
      (node (ref "B13") (pin "M2") (pinfunction "IN3_M2") (pintype "input"))
      (node (ref "B13") (pin "N1") (pinfunction "IN2_N1") (pintype "input"))
      (node (ref "B13") (pin "N2") (pinfunction "IN4_N2") (pintype "input"))
      (node (ref "B13") (pin "P1") (pinfunction "IN3_P1") (pintype "input"))
      (node (ref "B13") (pin "R1") (pinfunction "IN4_R1") (pintype "input"))
      (node (ref "B13") (pin "S2") (pinfunction "IN2_S2") (pintype "input"))
      (node (ref "B13") (pin "T2") (pinfunction "IN3_T2") (pintype "input"))
      (node (ref "B13") (pin "U1") (pinfunction "P$1_U1") (pintype "passive"))
      (node (ref "B13") (pin "U2") (pinfunction "IN4_U2") (pintype "input"))
      (node (ref "B14") (pin "B1") (pinfunction "IN2_B1") (pintype "input"))
      (node (ref "B14") (pin "C1") (pinfunction "IN3_C1") (pintype "input"))
      (node (ref "B14") (pin "D1") (pinfunction "IN4_D1") (pintype "input"))
    )
    (net (code "13") (name "+3V(13)") (class "Default")
      (node (ref "B13") (pin "V1") (pinfunction "P$1_V1") (pintype "passive"))
      (node (ref "B14") (pin "E2") (pinfunction "IN2_E2") (pintype "input"))
      (node (ref "B14") (pin "F2") (pinfunction "IN3_F2") (pintype "input"))
      (node (ref "B14") (pin "H2") (pinfunction "IN4_H2") (pintype "input"))
    )
    (net (code "14") (name "+3V(14)") (class "Default")
      (node (ref "B14") (pin "H1") (pinfunction "IN2_H1") (pintype "input"))
      (node (ref "B14") (pin "J1") (pinfunction "IN3_J1") (pintype "input"))
      (node (ref "B14") (pin "K1") (pinfunction "IN4_K1") (pintype "input"))
      (node (ref "B14") (pin "L2") (pinfunction "IN2_L2") (pintype "input"))
      (node (ref "B14") (pin "M2") (pinfunction "IN3_M2") (pintype "input"))
      (node (ref "B14") (pin "N1") (pinfunction "IN2_N1") (pintype "input"))
      (node (ref "B14") (pin "N2") (pinfunction "IN4_N2") (pintype "input"))
      (node (ref "B14") (pin "P1") (pinfunction "IN3_P1") (pintype "input"))
      (node (ref "B14") (pin "R1") (pinfunction "IN4_R1") (pintype "input"))
      (node (ref "B14") (pin "U1") (pinfunction "P$1_U1") (pintype "passive"))
    )
    (net (code "15") (name "+3V(15)") (class "Default")
      (node (ref "B14") (pin "S2") (pinfunction "IN2_S2") (pintype "input"))
      (node (ref "B14") (pin "T2") (pinfunction "IN3_T2") (pintype "input"))
      (node (ref "B14") (pin "U2") (pinfunction "IN4_U2") (pintype "input"))
      (node (ref "B14") (pin "V1") (pinfunction "P$1_V1") (pintype "passive"))
      (node (ref "B15") (pin "B1") (pinfunction "IN2_B1") (pintype "input"))
      (node (ref "B15") (pin "C1") (pinfunction "IN3_C1") (pintype "input"))
      (node (ref "B15") (pin "D1") (pinfunction "IN4_D1") (pintype "input"))
    )
    (net (code "16") (name "+3V(16)") (class "Default")
      (node (ref "B15") (pin "E2") (pinfunction "IN2_E2") (pintype "input"))
      (node (ref "B15") (pin "F2") (pinfunction "IN3_F2") (pintype "input"))
      (node (ref "B15") (pin "H1") (pinfunction "IN2_H1") (pintype "input"))
      (node (ref "B15") (pin "H2") (pinfunction "IN4_H2") (pintype "input"))
      (node (ref "B15") (pin "J1") (pinfunction "IN3_J1") (pintype "input"))
      (node (ref "B15") (pin "K1") (pinfunction "IN4_K1") (pintype "input"))
      (node (ref "B15") (pin "U1") (pinfunction "P$1_U1") (pintype "passive"))
    )
    (net (code "17") (name "+3V(17)") (class "Default")
      (node (ref "B15") (pin "L2") (pinfunction "IN2_L2") (pintype "input"))
      (node (ref "B15") (pin "M2") (pinfunction "IN3_M2") (pintype "input"))
      (node (ref "B15") (pin "N1") (pinfunction "IN2_N1") (pintype "input"))
      (node (ref "B15") (pin "N2") (pinfunction "IN4_N2") (pintype "input"))
      (node (ref "B15") (pin "P1") (pinfunction "IN3_P1") (pintype "input"))
      (node (ref "B15") (pin "R1") (pinfunction "IN4_R1") (pintype "input"))
      (node (ref "B15") (pin "S2") (pinfunction "IN2_S2") (pintype "input"))
      (node (ref "B15") (pin "T2") (pinfunction "IN3_T2") (pintype "input"))
      (node (ref "B15") (pin "U2") (pinfunction "IN4_U2") (pintype "input"))
      (node (ref "B16") (pin "V1") (pinfunction "P$1_V1") (pintype "passive"))
    )
    (net (code "18") (name "+3V(18)") (class "Default")
      (node (ref "B16") (pin "D1") (pinfunction "IN4_D1") (pintype "input"))
      (node (ref "B16") (pin "H2") (pinfunction "IN4_H2") (pintype "input"))
      (node (ref "B16") (pin "K1") (pinfunction "IN4_K1") (pintype "input"))
      (node (ref "B16") (pin "U1") (pinfunction "P$1_U1") (pintype "passive"))
    )
    (net (code "19") (name "+3V(19)") (class "Default")
      (node (ref "A19") (pin "U1") (pinfunction "P$1_U1") (pintype "passive"))
      (node (ref "B17") (pin "D1") (pinfunction "S_D1") (pintype "input"))
      (node (ref "B17") (pin "F2") (pinfunction "S_F2") (pintype "input"))
      (node (ref "B17") (pin "K1") (pinfunction "S_K1") (pintype "input"))
      (node (ref "B17") (pin "N2") (pinfunction "S_N2") (pintype "input"))
      (node (ref "B17") (pin "R1") (pinfunction "S_R1") (pintype "input"))
      (node (ref "B17") (pin "U2") (pinfunction "S_U2") (pintype "input"))
      (node (ref "B18") (pin "D1") (pinfunction "S_D1") (pintype "input"))
      (node (ref "B18") (pin "F2") (pinfunction "S_F2") (pintype "input"))
      (node (ref "B18") (pin "K1") (pinfunction "S_K1") (pintype "input"))
      (node (ref "B18") (pin "K2") (pinfunction "R_K2") (pintype "input"))
    )
    (net (code "20") (name "+3V(20)") (class "Default")
      (node (ref "A19") (pin "V1") (pinfunction "P$1_V1") (pintype "passive"))
      (node (ref "B18") (pin "N2") (pinfunction "S_N2") (pintype "input"))
      (node (ref "B18") (pin "R1") (pinfunction "S_R1") (pintype "input"))
      (node (ref "B18") (pin "U2") (pinfunction "S_U2") (pintype "input"))
      (node (ref "B19") (pin "A1") (pinfunction "R_A1") (pintype "input"))
      (node (ref "B19") (pin "D1") (pinfunction "S_D1") (pintype "input"))
      (node (ref "B19") (pin "F2") (pinfunction "S_F2") (pintype "input"))
      (node (ref "B19") (pin "K1") (pinfunction "S_K1") (pintype "input"))
      (node (ref "B19") (pin "K2") (pinfunction "R_K2") (pintype "input"))
      (node (ref "B19") (pin "N2") (pinfunction "S_N2") (pintype "input"))
      (node (ref "B19") (pin "R1") (pinfunction "S_R1") (pintype "input"))
      (node (ref "B19") (pin "U2") (pinfunction "S_U2") (pintype "input"))
    )
    (net (code "21") (name "+3V(23)") (class "Default")
      (node (ref "C10") (pin "B1") (pinfunction "IN2_B1") (pintype "input"))
      (node (ref "C10") (pin "D1") (pinfunction "IN1_D1") (pintype "input"))
      (node (ref "C10") (pin "D2") (pinfunction "IN1_D2") (pintype "input"))
      (node (ref "C10") (pin "H2") (pinfunction "IN1_H2") (pintype "input"))
      (node (ref "C10") (pin "J1") (pinfunction "IN2_J1") (pintype "input"))
      (node (ref "C10") (pin "U2") (pinfunction "IN2_U2") (pintype "input"))
      (node (ref "C11") (pin "B1") (pinfunction "IN2_B1") (pintype "input"))
      (node (ref "D10") (pin "B1") (pinfunction "IN2_B1") (pintype "input"))
      (node (ref "D10") (pin "C1") (pinfunction "IN3_C1") (pintype "input"))
      (node (ref "D10") (pin "U1") (pinfunction "P$1_U1") (pintype "passive"))
      (node (ref "D11") (pin "A1") (pinfunction "R_A1") (pintype "input"))
    )
    (net (code "22") (name "+3V(24)") (class "Default")
      (node (ref "C18") (pin "A1") (pinfunction "IN1_A1") (pintype "input"))
      (node (ref "C18") (pin "D1") (pinfunction "IN1_D1") (pintype "input"))
      (node (ref "C18") (pin "D2") (pinfunction "IN1_D2") (pintype "input"))
      (node (ref "C18") (pin "H2") (pinfunction "IN1_H2") (pintype "input"))
      (node (ref "C18") (pin "R2") (pinfunction "IN2_R2") (pintype "input"))
      (node (ref "C18") (pin "U1") (pinfunction "P$1_U1") (pintype "passive"))
      (node (ref "C18") (pin "U2") (pinfunction "IN2_U2") (pintype "input"))
    )
    (net (code "23") (name "+3V(25)") (class "Default")
      (node (ref "B21") (pin "V1") (pinfunction "P$1_V1") (pintype "passive"))
      (node (ref "C22") (pin "A1") (pinfunction "R_A1") (pintype "input"))
      (node (ref "C22") (pin "D1") (pinfunction "S_D1") (pintype "input"))
      (node (ref "C22") (pin "F2") (pinfunction "S_F2") (pintype "input"))
      (node (ref "C22") (pin "K1") (pinfunction "S_K1") (pintype "input"))
      (node (ref "C22") (pin "K2") (pinfunction "R_K2") (pintype "input"))
      (node (ref "C22") (pin "N2") (pinfunction "S_N2") (pintype "input"))
      (node (ref "C22") (pin "R1") (pinfunction "S_R1") (pintype "input"))
    )
    (net (code "24") (name "+3V(26)") (class "Default")
      (node (ref "C23") (pin "A1") (pinfunction "R_A1") (pintype "input"))
      (node (ref "C23") (pin "D1") (pinfunction "S_D1") (pintype "input"))
      (node (ref "C23") (pin "F2") (pinfunction "S_F2") (pintype "input"))
      (node (ref "C23") (pin "K1") (pinfunction "S_K1") (pintype "input"))
      (node (ref "C23") (pin "K2") (pinfunction "R_K2") (pintype "input"))
      (node (ref "C23") (pin "N2") (pinfunction "S_N2") (pintype "input"))
      (node (ref "C23") (pin "R1") (pinfunction "S_R1") (pintype "input"))
      (node (ref "C23") (pin "U2") (pinfunction "S_U2") (pintype "input"))
      (node (ref "D22") (pin "U1") (pinfunction "P$1_U1") (pintype "passive"))
    )
    (net (code "25") (name "+3V(27)") (class "Default")
      (node (ref "C24") (pin "A1") (pinfunction "R_A1") (pintype "input"))
      (node (ref "C24") (pin "D1") (pinfunction "S_D1") (pintype "input"))
      (node (ref "C24") (pin "F2") (pinfunction "S_F2") (pintype "input"))
      (node (ref "C24") (pin "K1") (pinfunction "S_K1") (pintype "input"))
      (node (ref "C24") (pin "K2") (pinfunction "R_K2") (pintype "input"))
      (node (ref "C24") (pin "N2") (pinfunction "S_N2") (pintype "input"))
      (node (ref "C24") (pin "R1") (pinfunction "S_R1") (pintype "input"))
      (node (ref "C24") (pin "U2") (pinfunction "S_U2") (pintype "input"))
      (node (ref "D22") (pin "V1") (pinfunction "P$1_V1") (pintype "passive"))
    )
    (net (code "26") (name "+3V(28)") (class "Default")
      (node (ref "D12") (pin "E1") (pinfunction "IN2_E1") (pintype "input"))
      (node (ref "D12") (pin "J2") (pinfunction "IN2_J2") (pintype "input"))
      (node (ref "D12") (pin "M1") (pinfunction "IN2_M1") (pintype "input"))
      (node (ref "D12") (pin "T2") (pinfunction "IN1_T2") (pintype "input"))
      (node (ref "D12") (pin "U1") (pinfunction "P$1_U1") (pintype "passive"))
      (node (ref "D13") (pin "J1") (pinfunction "IN2_J1") (pintype "input"))
      (node (ref "D13") (pin "J2") (pinfunction "IN2_J2") (pintype "input"))
    )
    (net (code "27") (name "+3V(29)") (class "Default")
      (node (ref "D14") (pin "P1") (pinfunction "IN1_P1") (pintype "input"))
      (node (ref "D15") (pin "D2") (pinfunction "IN1_D2") (pintype "input"))
      (node (ref "D15") (pin "H2") (pinfunction "IN1_H2") (pintype "input"))
      (node (ref "D15") (pin "M2") (pinfunction "IN2_M2") (pintype "input"))
      (node (ref "D15") (pin "P1") (pinfunction "IN1_P1") (pintype "input"))
      (node (ref "D15") (pin "U1") (pinfunction "P$1_U1") (pintype "passive"))
      (node (ref "D15") (pin "U2") (pinfunction "IN2_U2") (pintype "input"))
    )
    (net (code "28") (name "+3V(30)") (class "Default")
      (node (ref "D16") (pin "A1") (pinfunction "IN1_A1") (pintype "input"))
      (node (ref "D16") (pin "D1") (pinfunction "IN1_D1") (pintype "input"))
      (node (ref "D16") (pin "D2") (pinfunction "IN1_D2") (pintype "input"))
      (node (ref "D16") (pin "M2") (pinfunction "IN2_M2") (pintype "input"))
      (node (ref "D16") (pin "R1") (pinfunction "IN2_R1") (pintype "input"))
      (node (ref "D16") (pin "R2") (pinfunction "IN2_R2") (pintype "input"))
      (node (ref "D16") (pin "U1") (pinfunction "P$1_U1") (pintype "passive"))
      (node (ref "D16") (pin "U2") (pinfunction "IN2_U2") (pintype "input"))
    )
    (net (code "29") (name "+3V(31)") (class "Default")
      (node (ref "D22") (pin "H1") (pinfunction "IN2_H1") (pintype "input"))
      (node (ref "D22") (pin "J1") (pinfunction "IN3_J1") (pintype "input"))
      (node (ref "D22") (pin "K1") (pinfunction "IN4_K1") (pintype "input"))
      (node (ref "D22") (pin "L2") (pinfunction "IN2_L2") (pintype "input"))
      (node (ref "D22") (pin "M1") (pinfunction "IN1_M1") (pintype "input"))
      (node (ref "D22") (pin "M2") (pinfunction "IN3_M2") (pintype "input"))
      (node (ref "D22") (pin "N1") (pinfunction "IN2_N1") (pintype "input"))
      (node (ref "D22") (pin "N2") (pinfunction "IN4_N2") (pintype "input"))
      (node (ref "D22") (pin "T2") (pinfunction "IN3_T2") (pintype "input"))
      (node (ref "E22") (pin "V1") (pinfunction "P$1_V1") (pintype "passive"))
    )
    (net (code "30") (name "+3V(32)") (class "Default")
      (node (ref "D23") (pin "D2") (pinfunction "IN1A_D2") (pintype "input"))
      (node (ref "D23") (pin "E2") (pinfunction "IN1B_E2") (pintype "input"))
      (node (ref "D23") (pin "M1") (pinfunction "IN5A_M1") (pintype "input"))
      (node (ref "D23") (pin "N2") (pinfunction "IN4A_N2") (pintype "input"))
      (node (ref "D23") (pin "P2") (pinfunction "IN4B_P2") (pintype "input"))
      (node (ref "D23") (pin "R2") (pinfunction "IN4C_R2") (pintype "input"))
      (node (ref "D24") (pin "D1") (pinfunction "S_D1") (pintype "input"))
      (node (ref "D24") (pin "F2") (pinfunction "S_F2") (pintype "input"))
      (node (ref "D24") (pin "K1") (pinfunction "S_K1") (pintype "input"))
      (node (ref "D24") (pin "N2") (pinfunction "S_N2") (pintype "input"))
      (node (ref "E24") (pin "U1") (pinfunction "P$1_U1") (pintype "passive"))
    )
    (net (code "31") (name "+3V(33)") (class "Default")
      (node (ref "E11") (pin "B1") (pinfunction "IN2_B1") (pintype "input"))
      (node (ref "E11") (pin "E2") (pinfunction "IN2_E2") (pintype "input"))
      (node (ref "E11") (pin "H2") (pinfunction "IN1_H2") (pintype "input"))
      (node (ref "E11") (pin "M2") (pinfunction "IN2_M2") (pintype "input"))
      (node (ref "E11") (pin "P2") (pinfunction "IN1_P2") (pintype "input"))
      (node (ref "E12") (pin "B1") (pinfunction "IN2_B1") (pintype "input"))
      (node (ref "E12") (pin "J1") (pinfunction "IN2_J1") (pintype "input"))
      (node (ref "E12") (pin "L1") (pinfunction "IN1_L1") (pintype "input"))
      (node (ref "E12") (pin "V1") (pinfunction "P$1_V1") (pintype "passive"))
    )
    (net (code "32") (name "+3V(34)") (class "Default")
      (node (ref "E13") (pin "N1") (pinfunction "IN5B_N1") (pintype "input"))
      (node (ref "E13") (pin "P1") (pinfunction "IN5C_P1") (pintype "input"))
      (node (ref "E15") (pin "J2") (pinfunction "IN2_J2") (pintype "input"))
      (node (ref "E15") (pin "M1") (pinfunction "IN2_M1") (pintype "input"))
      (node (ref "E15") (pin "M2") (pinfunction "IN2_M2") (pintype "input"))
      (node (ref "E15") (pin "P2") (pinfunction "IN1_P2") (pintype "input"))
      (node (ref "E15") (pin "U1") (pinfunction "P$1_U1") (pintype "passive"))
      (node (ref "E15") (pin "U2") (pinfunction "IN2_U2") (pintype "input"))
    )
    (net (code "33") (name "+3V(35)") (class "Default")
      (node (ref "E15") (pin "V1") (pinfunction "P$1_V1") (pintype "passive"))
      (node (ref "E18") (pin "C1") (pinfunction "D_C1") (pintype "input"))
      (node (ref "E18") (pin "N2") (pinfunction "S_N2") (pintype "input"))
      (node (ref "E20") (pin "D1") (pinfunction "S_D1") (pintype "input"))
      (node (ref "E20") (pin "F2") (pinfunction "S_F2") (pintype "input"))
      (node (ref "E20") (pin "K1") (pinfunction "S_K1") (pintype "input"))
      (node (ref "E20") (pin "N2") (pinfunction "S_N2") (pintype "input"))
    )
    (net (code "34") (name "+3V(36)") (class "Default")
      (node (ref "E22") (pin "M2") (pinfunction "IN2_M2") (pintype "input"))
      (node (ref "E22") (pin "R1") (pinfunction "IN2_R1") (pintype "input"))
      (node (ref "E22") (pin "R2") (pinfunction "IN2_R2") (pintype "input"))
      (node (ref "E22") (pin "U1") (pinfunction "P$1_U1") (pintype "passive"))
      (node (ref "E22") (pin "U2") (pinfunction "IN2_U2") (pintype "input"))
      (node (ref "E23") (pin "F2") (pinfunction "S_F2") (pintype "input"))
      (node (ref "E23") (pin "K1") (pinfunction "S_K1") (pintype "input"))
      (node (ref "E23") (pin "N2") (pinfunction "S_N2") (pintype "input"))
      (node (ref "E23") (pin "R1") (pinfunction "S_R1") (pintype "input"))
      (node (ref "E23") (pin "U2") (pinfunction "S_U2") (pintype "input"))
      (node (ref "E24") (pin "J1") (pinfunction "IN2_J1") (pintype "input"))
      (node (ref "E24") (pin "M2") (pinfunction "IN2_M2") (pintype "input"))
      (node (ref "E24") (pin "P1") (pinfunction "IN1_P1") (pintype "input"))
      (node (ref "E24") (pin "P2") (pinfunction "IN1_P2") (pintype "input"))
    )
    (net (code "35") (name "+3V(37)") (class "Default")
      (node (ref "E26") (pin "D2") (pinfunction "IN1A_D2") (pintype "input"))
      (node (ref "E26") (pin "N2") (pinfunction "IN4A_N2") (pintype "input"))
      (node (ref "E27") (pin "C1") (pinfunction "IN1C_C1") (pintype "input"))
      (node (ref "E27") (pin "E2") (pinfunction "IN1B_E2") (pintype "input"))
      (node (ref "E27") (pin "F2") (pinfunction "IN1C_F2") (pintype "input"))
      (node (ref "E27") (pin "H2") (pinfunction "IN1D_H2") (pintype "input"))
      (node (ref "E27") (pin "N2") (pinfunction "IN4A_N2") (pintype "input"))
      (node (ref "E28") (pin "A1") (pinfunction "IN1A_A1") (pintype "input"))
      (node (ref "E28") (pin "H1") (pinfunction "IN3A_H1") (pintype "input"))
      (node (ref "F27") (pin "U1") (pinfunction "P$1_U1") (pintype "passive"))
    )
    (net (code "36") (name "+3V(38)") (class "Default")
      (node (ref "E28") (pin "K1") (pinfunction "IN4A_K1") (pintype "input"))
      (node (ref "E29") (pin "B1") (pinfunction "IN1B_B1") (pintype "input"))
      (node (ref "E29") (pin "E2") (pinfunction "IN1B_E2") (pintype "input"))
      (node (ref "E29") (pin "H1") (pinfunction "IN3A_H1") (pintype "input"))
      (node (ref "E29") (pin "H2") (pinfunction "IN1D_H2") (pintype "input"))
      (node (ref "E29") (pin "P2") (pinfunction "IN4B_P2") (pintype "input"))
      (node (ref "E29") (pin "R2") (pinfunction "IN4C_R2") (pintype "input"))
      (node (ref "F29") (pin "U1") (pinfunction "P$1_U1") (pintype "passive"))
    )
    (net (code "37") (name "+3V(39)") (class "Default")
      (node (ref "E30") (pin "B1") (pinfunction "IN1B_B1") (pintype "input"))
      (node (ref "E30") (pin "C1") (pinfunction "IN1C_C1") (pintype "input"))
      (node (ref "E30") (pin "D1") (pinfunction "IN1D_D1") (pintype "input"))
      (node (ref "E30") (pin "E2") (pinfunction "IN1B_E2") (pintype "input"))
      (node (ref "E30") (pin "N2") (pinfunction "IN4A_N2") (pintype "input"))
      (node (ref "E31") (pin "B1") (pinfunction "IN2_B1") (pintype "input"))
      (node (ref "E31") (pin "C1") (pinfunction "IN3_C1") (pintype "input"))
      (node (ref "E31") (pin "D1") (pinfunction "IN4_D1") (pintype "input"))
      (node (ref "E31") (pin "D2") (pinfunction "IN1_D2") (pintype "input"))
      (node (ref "E31") (pin "E2") (pinfunction "IN2_E2") (pintype "input"))
      (node (ref "E31") (pin "U1") (pinfunction "P$1_U1") (pintype "passive"))
    )
    (net (code "38") (name "+3V(40)") (class "Default")
      (node (ref "E31") (pin "F1") (pinfunction "IN1_F1") (pintype "input"))
      (node (ref "E31") (pin "F2") (pinfunction "IN3_F2") (pintype "input"))
      (node (ref "E31") (pin "K2") (pinfunction "IN1_K2") (pintype "input"))
      (node (ref "E31") (pin "L2") (pinfunction "IN2_L2") (pintype "input"))
      (node (ref "E31") (pin "S2") (pinfunction "IN2_S2") (pintype "input"))
      (node (ref "E31") (pin "T2") (pinfunction "IN3_T2") (pintype "input"))
      (node (ref "E31") (pin "U2") (pinfunction "IN4_U2") (pintype "input"))
      (node (ref "E31") (pin "V1") (pinfunction "P$1_V1") (pintype "passive"))
    )
    (net (code "39") (name "+3V(41)") (class "Default")
      (node (ref "E32") (pin "B1") (pinfunction "IN2_B1") (pintype "input"))
      (node (ref "E32") (pin "C1") (pinfunction "IN3_C1") (pintype "input"))
      (node (ref "E32") (pin "D2") (pinfunction "IN1_D2") (pintype "input"))
      (node (ref "E32") (pin "F1") (pinfunction "IN1_F1") (pintype "input"))
      (node (ref "E32") (pin "H1") (pinfunction "IN2_H1") (pintype "input"))
      (node (ref "E32") (pin "J1") (pinfunction "IN3_J1") (pintype "input"))
      (node (ref "E32") (pin "U1") (pinfunction "P$1_U1") (pintype "passive"))
    )
    (net (code "40") (name "+3V(42)") (class "Default")
      (node (ref "E32") (pin "R2") (pinfunction "IN1_R2") (pintype "input"))
      (node (ref "E32") (pin "S2") (pinfunction "IN2_S2") (pintype "input"))
      (node (ref "E32") (pin "V1") (pinfunction "P$1_V1") (pintype "passive"))
      (node (ref "E33") (pin "A1") (pinfunction "R_A1") (pintype "input"))
      (node (ref "E33") (pin "K2") (pinfunction "R_K2") (pintype "input"))
      (node (ref "E33") (pin "U2") (pinfunction "S_U2") (pintype "input"))
    )
    (net (code "41") (name "+3V(43)") (class "Default")
      (node (ref "C12") (pin "F1") (pinfunction "IN1_F1") (pintype "input"))
      (node (ref "F20") (pin "A1") (pinfunction "IN1_A1") (pintype "input"))
      (node (ref "F20") (pin "M1") (pinfunction "IN2_M1") (pintype "input"))
      (node (ref "F20") (pin "M2") (pinfunction "IN2_M2") (pintype "input"))
      (node (ref "F20") (pin "U1") (pinfunction "P$1_U1") (pintype "passive"))
      (node (ref "F21") (pin "E2") (pinfunction "IN2_E2") (pintype "input"))
      (node (ref "F21") (pin "J2") (pinfunction "IN2_J2") (pintype "input"))
      (node (ref "F21") (pin "L1") (pinfunction "IN1_L1") (pintype "input"))
      (node (ref "F21") (pin "P2") (pinfunction "IN1_P2") (pintype "input"))
      (node (ref "F21") (pin "R1") (pinfunction "IN2_R1") (pintype "input"))
    )
    (net (code "42") (name "+3V(44)") (class "Default")
      (node (ref "F22") (pin "A1") (pinfunction "IN1_A1") (pintype "input"))
      (node (ref "F22") (pin "E1") (pinfunction "IN2_E1") (pintype "input"))
      (node (ref "F22") (pin "J1") (pinfunction "IN2_J1") (pintype "input"))
      (node (ref "F22") (pin "J2") (pinfunction "IN2_J2") (pintype "input"))
      (node (ref "F22") (pin "M1") (pinfunction "IN2_M1") (pintype "input"))
      (node (ref "F22") (pin "M2") (pinfunction "IN2_M2") (pintype "input"))
      (node (ref "F22") (pin "U1") (pinfunction "P$1_U1") (pintype "passive"))
      (node (ref "F24") (pin "D1") (pinfunction "IN4_D1") (pintype "input"))
      (node (ref "F25") (pin "B1") (pinfunction "IN2_B1") (pintype "input"))
      (node (ref "F25") (pin "E1") (pinfunction "IN2_E1") (pintype "input"))
      (node (ref "F25") (pin "M2") (pinfunction "IN2_M2") (pintype "input"))
    )
    (net (code "43") (name "+3V(45)") (class "Default")
      (node (ref "F25") (pin "R1") (pinfunction "IN2_R1") (pintype "input"))
      (node (ref "F29") (pin "B1") (pinfunction "IN2_B1") (pintype "input"))
      (node (ref "F29") (pin "E2") (pinfunction "IN2_E2") (pintype "input"))
      (node (ref "F29") (pin "H1") (pinfunction "IN1_H1") (pintype "input"))
      (node (ref "F29") (pin "H2") (pinfunction "IN1_H2") (pintype "input"))
      (node (ref "F30") (pin "B1") (pinfunction "IN2_B1") (pintype "input"))
      (node (ref "F30") (pin "C1") (pinfunction "IN3_C1") (pintype "input"))
      (node (ref "F30") (pin "D1") (pinfunction "IN4_D1") (pintype "input"))
      (node (ref "F30") (pin "F2") (pinfunction "IN3_F2") (pintype "input"))
      (node (ref "F30") (pin "H1") (pinfunction "IN2_H1") (pintype "input"))
      (node (ref "F30") (pin "L2") (pinfunction "IN2_L2") (pintype "input"))
      (node (ref "F30") (pin "M2") (pinfunction "IN3_M2") (pintype "input"))
      (node (ref "F30") (pin "N2") (pinfunction "IN4_N2") (pintype "input"))
      (node (ref "F30") (pin "V1") (pinfunction "P$1_V1") (pintype "passive"))
    )
    (net (code "44") (name "+3V(46)") (class "Default")
      (node (ref "F30") (pin "J1") (pinfunction "IN3_J1") (pintype "input"))
      (node (ref "F30") (pin "K1") (pinfunction "IN4_K1") (pintype "input"))
      (node (ref "F30") (pin "R1") (pinfunction "IN4_R1") (pintype "input"))
      (node (ref "F30") (pin "R2") (pinfunction "IN1_R2") (pintype "input"))
      (node (ref "F30") (pin "S2") (pinfunction "IN2_S2") (pintype "input"))
      (node (ref "F30") (pin "T2") (pinfunction "IN3_T2") (pintype "input"))
      (node (ref "F30") (pin "U1") (pinfunction "P$1_U1") (pintype "passive"))
      (node (ref "F31") (pin "J1") (pinfunction "IN3_J1") (pintype "input"))
    )
    (net (code "45") (name "+3V(47)") (class "Default")
      (node (ref "F31") (pin "K1") (pinfunction "IN4_K1") (pintype "input"))
      (node (ref "F31") (pin "L2") (pinfunction "IN2_L2") (pintype "input"))
      (node (ref "F31") (pin "M2") (pinfunction "IN3_M2") (pintype "input"))
      (node (ref "F31") (pin "N1") (pinfunction "IN2_N1") (pintype "input"))
      (node (ref "F31") (pin "N2") (pinfunction "IN4_N2") (pintype "input"))
      (node (ref "F31") (pin "P1") (pinfunction "IN3_P1") (pintype "input"))
      (node (ref "F31") (pin "R1") (pinfunction "IN4_R1") (pintype "input"))
      (node (ref "F31") (pin "S2") (pinfunction "IN2_S2") (pintype "input"))
      (node (ref "F31") (pin "T2") (pinfunction "IN3_T2") (pintype "input"))
      (node (ref "F31") (pin "U1") (pinfunction "P$1_U1") (pintype "passive"))
      (node (ref "F31") (pin "U2") (pinfunction "IN4_U2") (pintype "input"))
    )
    (net (code "46") (name "+3V(48)") (class "Default")
      (node (ref "F31") (pin "V1") (pinfunction "P$1_V1") (pintype "passive"))
      (node (ref "F32") (pin "B1") (pinfunction "IN2_B1") (pintype "input"))
      (node (ref "F32") (pin "E2") (pinfunction "IN2_E2") (pintype "input"))
      (node (ref "F32") (pin "H1") (pinfunction "IN1_H1") (pintype "input"))
      (node (ref "F32") (pin "M2") (pinfunction "IN2_M2") (pintype "input"))
      (node (ref "F32") (pin "P2") (pinfunction "IN1_P2") (pintype "input"))
      (node (ref "F32") (pin "R1") (pinfunction "IN2_R1") (pintype "input"))
      (node (ref "F32") (pin "T2") (pinfunction "IN1_T2") (pintype "input"))
      (node (ref "F33") (pin "C1") (pinfunction "IN1C_C1") (pintype "input"))
      (node (ref "F33") (pin "D2") (pinfunction "IN1A_D2") (pintype "input"))
      (node (ref "F33") (pin "P1") (pinfunction "IN5C_P1") (pintype "input"))
    )
    (net (code "47") (name "+3V(49)") (class "Default")
      (node (ref "EF10") (pin "BF2") (pinfunction "P$1_BF2") (pintype "passive"))
      (node (ref "H07") (pin "F2") (pinfunction "IN1_F2") (pintype "input"))
      (node (ref "H07") (pin "J2") (pinfunction "IN3_J2") (pintype "input"))
      (node (ref "H07") (pin "M2") (pinfunction "IN1_M2") (pintype "input"))
      (node (ref "H07") (pin "P2") (pinfunction "IN3_P2") (pintype "input"))
      (node (ref "H07") (pin "T2") (pinfunction "IN1_T2") (pintype "input"))
      (node (ref "H07") (pin "V2") (pinfunction "IN3_V2") (pintype "input"))
      (node (ref "H08") (pin "F2") (pinfunction "IN1_F2") (pintype "input"))
      (node (ref "H08") (pin "J2") (pinfunction "IN3_J2") (pintype "input"))
      (node (ref "H08") (pin "M2") (pinfunction "IN1_M2") (pintype "input"))
      (node (ref "H08") (pin "P2") (pinfunction "IN3_P2") (pintype "input"))
      (node (ref "H08") (pin "T2") (pinfunction "IN1_T2") (pintype "input"))
      (node (ref "H08") (pin "V2") (pinfunction "IN3_V2") (pintype "input"))
    )
    (net (code "48") (name "+3V(50)") (class "Default")
      (node (ref "F11") (pin "V1") (pinfunction "P$1_V1") (pintype "passive"))
      (node (ref "H09") (pin "F2") (pinfunction "IN1_F2") (pintype "input"))
      (node (ref "H09") (pin "J2") (pinfunction "IN3_J2") (pintype "input"))
      (node (ref "H09") (pin "M2") (pinfunction "IN1_M2") (pintype "input"))
      (node (ref "H09") (pin "P2") (pinfunction "IN3_P2") (pintype "input"))
      (node (ref "H09") (pin "T2") (pinfunction "IN1_T2") (pintype "input"))
      (node (ref "H09") (pin "V2") (pinfunction "IN3_V2") (pintype "input"))
      (node (ref "H10") (pin "F2") (pinfunction "IN1_F2") (pintype "input"))
      (node (ref "H10") (pin "J2") (pinfunction "IN3_J2") (pintype "input"))
      (node (ref "H10") (pin "M2") (pinfunction "IN1_M2") (pintype "input"))
      (node (ref "H10") (pin "P2") (pinfunction "IN3_P2") (pintype "input"))
      (node (ref "H10") (pin "T2") (pinfunction "IN1_T2") (pintype "input"))
      (node (ref "H10") (pin "V2") (pinfunction "IN3_V2") (pintype "input"))
    )
    (net (code "49") (name "+3V(51)") (class "Default")
      (node (ref "F20") (pin "V1") (pinfunction "P$1_V1") (pintype "passive"))
      (node (ref "H11") (pin "F2") (pinfunction "IN1_F2") (pintype "input"))
      (node (ref "H11") (pin "J2") (pinfunction "IN3_J2") (pintype "input"))
      (node (ref "H11") (pin "M2") (pinfunction "IN1_M2") (pintype "input"))
      (node (ref "H11") (pin "P2") (pinfunction "IN3_P2") (pintype "input"))
      (node (ref "H11") (pin "T2") (pinfunction "IN1_T2") (pintype "input"))
      (node (ref "H11") (pin "V2") (pinfunction "IN3_V2") (pintype "input"))
      (node (ref "H12") (pin "F2") (pinfunction "IN1_F2") (pintype "input"))
      (node (ref "H12") (pin "J2") (pinfunction "IN3_J2") (pintype "input"))
      (node (ref "H12") (pin "M2") (pinfunction "IN1_M2") (pintype "input"))
      (node (ref "H12") (pin "P2") (pinfunction "IN3_P2") (pintype "input"))
      (node (ref "H12") (pin "T2") (pinfunction "IN1_T2") (pintype "input"))
      (node (ref "H12") (pin "V2") (pinfunction "IN3_V2") (pintype "input"))
    )
    (net (code "50") (name "+3V(52)") (class "Default")
      (node (ref "F21") (pin "U1") (pinfunction "P$1_U1") (pintype "passive"))
      (node (ref "H13") (pin "F2") (pinfunction "IN1_F2") (pintype "input"))
      (node (ref "H13") (pin "J2") (pinfunction "IN3_J2") (pintype "input"))
      (node (ref "H13") (pin "M2") (pinfunction "IN1_M2") (pintype "input"))
      (node (ref "H13") (pin "P2") (pinfunction "IN3_P2") (pintype "input"))
      (node (ref "H13") (pin "T2") (pinfunction "IN1_T2") (pintype "input"))
      (node (ref "H13") (pin "V2") (pinfunction "IN3_V2") (pintype "input"))
      (node (ref "H14") (pin "F2") (pinfunction "IN1_F2") (pintype "input"))
      (node (ref "H14") (pin "J2") (pinfunction "IN3_J2") (pintype "input"))
      (node (ref "H14") (pin "M2") (pinfunction "IN1_M2") (pintype "input"))
      (node (ref "H14") (pin "P2") (pinfunction "IN3_P2") (pintype "input"))
      (node (ref "H14") (pin "T2") (pinfunction "IN1_T2") (pintype "input"))
      (node (ref "H14") (pin "V2") (pinfunction "IN3_V2") (pintype "input"))
    )
    (net (code "51") (name "+3V(53)") (class "Default")
      (node (ref "F21") (pin "V1") (pinfunction "P$1_V1") (pintype "passive"))
      (node (ref "H15") (pin "F2") (pinfunction "IN1_F2") (pintype "input"))
      (node (ref "H15") (pin "J2") (pinfunction "IN3_J2") (pintype "input"))
      (node (ref "H15") (pin "M2") (pinfunction "IN1_M2") (pintype "input"))
      (node (ref "H15") (pin "P2") (pinfunction "IN3_P2") (pintype "input"))
      (node (ref "H15") (pin "T2") (pinfunction "IN1_T2") (pintype "input"))
      (node (ref "H15") (pin "V2") (pinfunction "IN3_V2") (pintype "input"))
      (node (ref "H16") (pin "F2") (pinfunction "IN1_F2") (pintype "input"))
      (node (ref "H16") (pin "J2") (pinfunction "IN3_J2") (pintype "input"))
      (node (ref "H16") (pin "M2") (pinfunction "IN1_M2") (pintype "input"))
      (node (ref "H16") (pin "P2") (pinfunction "IN3_P2") (pintype "input"))
      (node (ref "H16") (pin "T2") (pinfunction "IN1_T2") (pintype "input"))
      (node (ref "H16") (pin "V2") (pinfunction "IN3_V2") (pintype "input"))
    )
    (net (code "52") (name "+3V(54)") (class "Default")
      (node (ref "F22") (pin "V1") (pinfunction "P$1_V1") (pintype "passive"))
      (node (ref "H17") (pin "F2") (pinfunction "IN1_F2") (pintype "input"))
      (node (ref "H17") (pin "J2") (pinfunction "IN3_J2") (pintype "input"))
      (node (ref "H17") (pin "M2") (pinfunction "IN1_M2") (pintype "input"))
      (node (ref "H17") (pin "P2") (pinfunction "IN3_P2") (pintype "input"))
      (node (ref "H17") (pin "T2") (pinfunction "IN1_T2") (pintype "input"))
      (node (ref "H17") (pin "V2") (pinfunction "IN3_V2") (pintype "input"))
      (node (ref "H18") (pin "F2") (pinfunction "IN1_F2") (pintype "input"))
      (node (ref "H18") (pin "J2") (pinfunction "IN3_J2") (pintype "input"))
      (node (ref "H18") (pin "M2") (pinfunction "IN1_M2") (pintype "input"))
      (node (ref "H18") (pin "P2") (pinfunction "IN3_P2") (pintype "input"))
      (node (ref "H18") (pin "T2") (pinfunction "IN1_T2") (pintype "input"))
      (node (ref "H18") (pin "V2") (pinfunction "IN3_V2") (pintype "input"))
    )
    (net (code "53") (name "+3V(55)") (class "Default")
      (node (ref "E22") (pin "B1") (pinfunction "IN2_B1") (pintype "input"))
      (node (ref "E22") (pin "E1") (pinfunction "IN2_E1") (pintype "input"))
      (node (ref "E22") (pin "E2") (pinfunction "IN2_E2") (pintype "input"))
      (node (ref "E22") (pin "J1") (pinfunction "IN2_J1") (pintype "input"))
      (node (ref "E22") (pin "J2") (pinfunction "IN2_J2") (pintype "input"))
      (node (ref "F23") (pin "U1") (pinfunction "P$1_U1") (pintype "passive"))
      (node (ref "H19") (pin "F2") (pinfunction "IN1_F2") (pintype "input"))
      (node (ref "H19") (pin "J2") (pinfunction "IN3_J2") (pintype "input"))
      (node (ref "H19") (pin "M2") (pinfunction "IN1_M2") (pintype "input"))
      (node (ref "H19") (pin "P2") (pinfunction "IN3_P2") (pintype "input"))
      (node (ref "H19") (pin "T2") (pinfunction "IN1_T2") (pintype "input"))
      (node (ref "H19") (pin "V2") (pinfunction "IN3_V2") (pintype "input"))
      (node (ref "H20") (pin "F2") (pinfunction "IN1_F2") (pintype "input"))
      (node (ref "H20") (pin "J2") (pinfunction "IN3_J2") (pintype "input"))
      (node (ref "H20") (pin "M2") (pinfunction "IN1_M2") (pintype "input"))
      (node (ref "H20") (pin "P2") (pinfunction "IN3_P2") (pintype "input"))
    )
    (net (code "54") (name "+3V(57)") (class "Default")
      (node (ref "C07") (pin "F2") (pinfunction "IN3_F2") (pintype "input"))
      (node (ref "C07") (pin "H2") (pinfunction "IN2_H2") (pintype "input"))
      (node (ref "C07") (pin "N2") (pinfunction "IN2_N2") (pintype "input"))
      (node (ref "C07") (pin "P2") (pinfunction "IN3_P2") (pintype "input"))
      (node (ref "C08") (pin "H2") (pinfunction "IN1_H2") (pintype "input"))
      (node (ref "C08") (pin "N2") (pinfunction "IN1_N2") (pintype "input"))
      (node (ref "C08") (pin "U2") (pinfunction "IN1_U2") (pintype "input"))
      (node (ref "C09") (pin "E1") (pinfunction "IN2_E1") (pintype "input"))
      (node (ref "C09") (pin "J1") (pinfunction "IN2_J1") (pintype "input"))
      (node (ref "C09") (pin "M1") (pinfunction "IN2_M1") (pintype "input"))
      (node (ref "C09") (pin "M2") (pinfunction "IN2_M2") (pintype "input"))
      (node (ref "C09") (pin "R1") (pinfunction "IN2_R1") (pintype "input"))
      (node (ref "C09") (pin "R2") (pinfunction "IN2_R2") (pintype "input"))
      (node (ref "D10") (pin "V1") (pinfunction "P$1_V1") (pintype "passive"))
      (node (ref "D11") (pin "K2") (pinfunction "R_K2") (pintype "input"))
      (node (ref "D11") (pin "N2") (pinfunction "S_N2") (pintype "input"))
    )
    (net (code "55") (name "+3V(58)") (class "Default")
      (node (ref "D07") (pin "E2") (pinfunction "IN2_E2") (pintype "input"))
      (node (ref "D07") (pin "H1") (pinfunction "IN1_H1") (pintype "input"))
      (node (ref "D07") (pin "P1") (pinfunction "IN1_P1") (pintype "input"))
      (node (ref "D07") (pin "P2") (pinfunction "IN1_P2") (pintype "input"))
      (node (ref "D07") (pin "U1") (pinfunction "P$1_U1") (pintype "passive"))
      (node (ref "D09") (pin "H1") (pinfunction "IN3_H1") (pintype "input"))
      (node (ref "D09") (pin "R1") (pinfunction "IN2_R1") (pintype "input"))
      (node (ref "D09") (pin "V2") (pinfunction "IN3_V2") (pintype "input"))
      (node (ref "D10") (pin "E2") (pinfunction "IN2_E2") (pintype "input"))
    )
    (net (code "56") (name "+3V(61)") (class "Default")
      (node (ref "C12") (pin "J1") (pinfunction "IN3_J1") (pintype "input"))
      (node (ref "C12") (pin "K1") (pinfunction "IN4_K1") (pintype "input"))
      (node (ref "C12") (pin "N2") (pinfunction "IN4_N2") (pintype "input"))
      (node (ref "C12") (pin "U1") (pinfunction "P$1_U1") (pintype "passive"))
    )
    (net (code "57") (name "+3V(62)") (class "Default")
      (node (ref "A05") (pin "U1") (pinfunction "P$1_U1") (pintype "passive"))
      (node (ref "B06") (pin "J2") (pinfunction "IN2_J2") (pintype "input"))
    )
    (net (code "58") (name "+3V(63)") (class "Default")
      (node (ref "B05") (pin "R1") (pinfunction "S_R1") (pintype "input"))
      (node (ref "B06") (pin "U2") (pinfunction "IN2_U2") (pintype "input"))
      (node (ref "B06") (pin "V1") (pinfunction "P$1_V1") (pintype "passive"))
    )
    (net (code "59") (name "+3V(64)") (class "Default")
      (node (ref "B04") (pin "F2") (pinfunction "IN3_F2") (pintype "input"))
      (node (ref "B05") (pin "D1") (pinfunction "S_D1") (pintype "input"))
      (node (ref "B06") (pin "U1") (pinfunction "P$1_U1") (pintype "passive"))
    )
    (net (code "60") (name "+3V(65)") (class "Default")
      (node (ref "A05") (pin "D1") (pinfunction "IN1_D1") (pintype "input"))
      (node (ref "A06") (pin "D2") (pinfunction "IN1_D2") (pintype "input"))
      (node (ref "A06") (pin "E1") (pinfunction "IN2_E1") (pintype "input"))
      (node (ref "A06") (pin "U1") (pinfunction "P$1_U1") (pintype "passive"))
      (node (ref "B05") (pin "F2") (pinfunction "S_F2") (pintype "input"))
      (node (ref "B05") (pin "N2") (pinfunction "S_N2") (pintype "input"))
    )
    (net (code "61") (name "+3V(66)") (class "Default")
      (node (ref "A05") (pin "T2") (pinfunction "IN1_T2") (pintype "input"))
      (node (ref "A06") (pin "R2") (pinfunction "IN2_R2") (pintype "input"))
      (node (ref "A11") (pin "U1") (pinfunction "P$1_U1") (pintype "passive"))
    )
    (net (code "62") (name "+3V(67)") (class "Default")
      (node (ref "A06") (pin "M1") (pinfunction "IN2_M1") (pintype "input"))
      (node (ref "A06") (pin "M2") (pinfunction "IN2_M2") (pintype "input"))
      (node (ref "A06") (pin "V1") (pinfunction "P$1_V1") (pintype "passive"))
      (node (ref "B04") (pin "V2") (pinfunction "IN3_V2") (pintype "input"))
    )
    (net (code "63") (name "+3V(68)") (class "Default")
      (node (ref "F08") (pin "P2") (pinfunction "IN2_P2") (pintype "input"))
      (node (ref "F09") (pin "H2") (pinfunction "IN8_H2") (pintype "input"))
      (node (ref "F09") (pin "U1") (pinfunction "P$1_U1") (pintype "passive"))
    )
    (net (code "64") (name "+3V(69)") (class "Default")
      (node (ref "E11") (pin "R1") (pinfunction "IN2_R1") (pintype "input"))
      (node (ref "F09") (pin "F1") (pinfunction "IN1_F1") (pintype "input"))
      (node (ref "F09") (pin "H1") (pinfunction "IN2_H1") (pintype "input"))
      (node (ref "F09") (pin "J1") (pinfunction "IN3_J1") (pintype "input"))
      (node (ref "F11") (pin "F1") (pinfunction "IN1_F1") (pintype "input"))
      (node (ref "F11") (pin "R1") (pinfunction "IN4_R1") (pintype "input"))
      (node (ref "F11") (pin "S2") (pinfunction "IN2_S2") (pintype "input"))
      (node (ref "F11") (pin "U1") (pinfunction "P$1_U1") (pintype "passive"))
    )
    (net (code "65") (name "-6V") (class "Default")
      (node (ref "AB02") (pin "BM2") (pinfunction "-6V_BM2") (pintype "power_in"))
    )
    (net (code "67") (name "-30V") (class "Default")
      (node (ref "AB02") (pin "BV2") (pinfunction "-30V_BV2") (pintype "power_in"))
    )
    (net (code "68") (name "0_TO_INT_ENAB_") (class "Default")
      (node (ref "E26") (pin "V2") (pinfunction "OUT_V2") (pintype "output"))
      (node (ref "E33") (pin "R1") (pinfunction "S_R1") (pintype "input"))
    )
    (net (code "69") (name "3_CYCLE") (class "Default")
      (node (ref "F22") (pin "T2") (pinfunction "IN1_T2") (pintype "input"))
      (node (ref "J20") (pin "J2") (pinfunction "OUT_J2") (pintype "output"))
    )
    (net (code "70") (name "AC00") (class "Default")
      (node (ref "C14") (pin "E1") (pinfunction "IN2_E1") (pintype "input"))
      (node (ref "D15") (pin "E1") (pinfunction "IN2_E1") (pintype "input"))
      (node (ref "D18") (pin "J2") (pinfunction "IN1_J2") (pintype "input"))
      (node (ref "E24") (pin "L1") (pinfunction "IN1_L1") (pintype "input"))
      (node (ref "EF34") (pin "BA1") (pinfunction "BA1_BA1") (pintype "output"))
      (node (ref "F33") (pin "N2") (pinfunction "IN4A_N2") (pintype "input"))
      (node (ref "H07") (pin "H2") (pinfunction "IN2_H2") (pintype "input"))
    )
    (net (code "71") (name "AC00_") (class "Default")
      (node (ref "D15") (pin "A1") (pinfunction "IN1_A1") (pintype "input"))
      (node (ref "E40") (pin "V2") (pinfunction "P$2_V2") (pintype "bidirectional"))
      (node (ref "EF34") (pin "BB1") (pinfunction "BB1_BB1") (pintype "output"))
      (node (ref "F24") (pin "K2") (pinfunction "IN1_K2") (pintype "input"))
    )
    (net (code "72") (name "AC01") (class "Default")
      (node (ref "C14") (pin "J2") (pinfunction "IN2_J2") (pintype "input"))
      (node (ref "D14") (pin "L1") (pinfunction "IN1_L1") (pintype "input"))
      (node (ref "D15") (pin "B1") (pinfunction "IN2_B1") (pintype "input"))
      (node (ref "EF34") (pin "AV1") (pinfunction "AV1_AV1") (pintype "output"))
      (node (ref "H07") (pin "N2") (pinfunction "IN2_N2") (pintype "input"))
    )
    (net (code "73") (name "AC01_") (class "Default")
      (node (ref "D15") (pin "D1") (pinfunction "IN1_D1") (pintype "input"))
      (node (ref "D16") (pin "H2") (pinfunction "IN1_H2") (pintype "input"))
      (node (ref "E40") (pin "T2") (pinfunction "P$2_T2") (pintype "bidirectional"))
      (node (ref "EF34") (pin "AV2") (pinfunction "AV2_AV2") (pintype "output"))
      (node (ref "F24") (pin "L2") (pinfunction "IN2_L2") (pintype "input"))
    )
    (net (code "74") (name "AC02") (class "Default")
      (node (ref "C14") (pin "R1") (pinfunction "IN2_R1") (pintype "input"))
      (node (ref "D16") (pin "J2") (pinfunction "IN2_J2") (pintype "input"))
      (node (ref "EF35") (pin "BA1") (pinfunction "BA1_BA1") (pintype "output"))
      (node (ref "H07") (pin "U2") (pinfunction "IN2_U2") (pintype "input"))
    )
    (net (code "75") (name "AC02_") (class "Default")
      (node (ref "D14") (pin "M1") (pinfunction "IN2_M1") (pintype "input"))
      (node (ref "D20") (pin "D1") (pinfunction "IN4_D1") (pintype "input"))
      (node (ref "E40") (pin "J1") (pinfunction "P$2_J1") (pintype "bidirectional"))
      (node (ref "EF35") (pin "BB1") (pinfunction "BB1_BB1") (pintype "output"))
      (node (ref "F24") (pin "M2") (pinfunction "IN3_M2") (pintype "input"))
    )
    (net (code "76") (name "AC03") (class "Default")
      (node (ref "C15") (pin "E1") (pinfunction "IN2_E1") (pintype "input"))
      (node (ref "EF35") (pin "AV1") (pinfunction "AV1_AV1") (pintype "output"))
      (node (ref "H08") (pin "H2") (pinfunction "IN2_H2") (pintype "input"))
    )
    (net (code "77") (name "AC03_") (class "Default")
      (node (ref "D19") (pin "K1") (pinfunction "IN1_K1") (pintype "input"))
      (node (ref "D20") (pin "C1") (pinfunction "IN3_C1") (pintype "input"))
      (node (ref "E40") (pin "H2") (pinfunction "P$2_H2") (pintype "bidirectional"))
      (node (ref "EF35") (pin "AV2") (pinfunction "AV2_AV2") (pintype "output"))
      (node (ref "F24") (pin "N2") (pinfunction "IN4_N2") (pintype "input"))
    )
    (net (code "78") (name "AC04") (class "Default")
      (node (ref "C15") (pin "J2") (pinfunction "IN2_J2") (pintype "input"))
      (node (ref "EF36") (pin "BA1") (pinfunction "BA1_BA1") (pintype "output"))
      (node (ref "H08") (pin "N2") (pinfunction "IN2_N2") (pintype "input"))
    )
    (net (code "79") (name "AC04_") (class "Default")
      (node (ref "E40") (pin "M1") (pinfunction "P$2_M1") (pintype "bidirectional"))
      (node (ref "EF36") (pin "BB1") (pinfunction "BB1_BB1") (pintype "output"))
      (node (ref "F24") (pin "M1") (pinfunction "IN1_M1") (pintype "input"))
    )
    (net (code "80") (name "AC05") (class "Default")
      (node (ref "C15") (pin "R1") (pinfunction "IN2_R1") (pintype "input"))
      (node (ref "EF36") (pin "AV1") (pinfunction "AV1_AV1") (pintype "output"))
      (node (ref "H08") (pin "U2") (pinfunction "IN2_U2") (pintype "input"))
    )
    (net (code "81") (name "AC05_") (class "Default")
      (node (ref "E40") (pin "B1") (pinfunction "P$2_B1") (pintype "bidirectional"))
      (node (ref "EF36") (pin "AV2") (pinfunction "AV2_AV2") (pintype "output"))
      (node (ref "F24") (pin "N1") (pinfunction "IN2_N1") (pintype "input"))
    )
    (net (code "82") (name "AC06") (class "Default")
      (node (ref "C16") (pin "E1") (pinfunction "IN2_E1") (pintype "input"))
      (node (ref "EF37") (pin "BA1") (pinfunction "BA1_BA1") (pintype "output"))
      (node (ref "H09") (pin "H2") (pinfunction "IN2_H2") (pintype "input"))
    )
    (net (code "83") (name "AC06_") (class "Default")
      (node (ref "EF37") (pin "BB1") (pinfunction "BB1_BB1") (pintype "output"))
      (node (ref "F24") (pin "P1") (pinfunction "IN3_P1") (pintype "input"))
      (node (ref "F40") (pin "V2") (pinfunction "P$2_V2") (pintype "bidirectional"))
    )
    (net (code "84") (name "AC07") (class "Default")
      (node (ref "C16") (pin "J2") (pinfunction "IN2_J2") (pintype "input"))
      (node (ref "EF37") (pin "AV1") (pinfunction "AV1_AV1") (pintype "output"))
      (node (ref "H09") (pin "N2") (pinfunction "IN2_N2") (pintype "input"))
    )
    (net (code "85") (name "AC07_") (class "Default")
      (node (ref "EF37") (pin "AV2") (pinfunction "AV2_AV2") (pintype "output"))
      (node (ref "F24") (pin "R1") (pinfunction "IN4_R1") (pintype "input"))
      (node (ref "F40") (pin "T2") (pinfunction "P$2_T2") (pintype "bidirectional"))
    )
    (net (code "86") (name "AC08") (class "Default")
      (node (ref "C16") (pin "R1") (pinfunction "IN2_R1") (pintype "input"))
      (node (ref "EF38") (pin "BA1") (pinfunction "BA1_BA1") (pintype "output"))
      (node (ref "H09") (pin "U2") (pinfunction "IN2_U2") (pintype "input"))
    )
    (net (code "87") (name "AC08_") (class "Default")
      (node (ref "EF38") (pin "BB1") (pinfunction "BB1_BB1") (pintype "output"))
      (node (ref "F24") (pin "R2") (pinfunction "IN1_R2") (pintype "input"))
      (node (ref "F40") (pin "J1") (pinfunction "P$2_J1") (pintype "bidirectional"))
    )
    (net (code "88") (name "AC09") (class "Default")
      (node (ref "C17") (pin "E1") (pinfunction "IN2_E1") (pintype "input"))
      (node (ref "EF38") (pin "AV1") (pinfunction "AV1_AV1") (pintype "output"))
      (node (ref "H10") (pin "H2") (pinfunction "IN2_H2") (pintype "input"))
    )
    (net (code "89") (name "AC09_") (class "Default")
      (node (ref "EF38") (pin "AV2") (pinfunction "AV2_AV2") (pintype "output"))
      (node (ref "F24") (pin "S2") (pinfunction "IN2_S2") (pintype "input"))
      (node (ref "F40") (pin "H2") (pinfunction "P$2_H2") (pintype "bidirectional"))
    )
    (net (code "90") (name "AC10") (class "Default")
      (node (ref "C17") (pin "J2") (pinfunction "IN2_J2") (pintype "input"))
      (node (ref "EF39") (pin "BA1") (pinfunction "BA1_BA1") (pintype "output"))
      (node (ref "H10") (pin "N2") (pinfunction "IN2_N2") (pintype "input"))
    )
    (net (code "91") (name "AC10_") (class "Default")
      (node (ref "EF39") (pin "BB1") (pinfunction "BB1_BB1") (pintype "output"))
      (node (ref "F24") (pin "T2") (pinfunction "IN3_T2") (pintype "input"))
      (node (ref "F40") (pin "M1") (pinfunction "P$2_M1") (pintype "bidirectional"))
    )
    (net (code "92") (name "AC11") (class "Default")
      (node (ref "C17") (pin "R1") (pinfunction "IN2_R1") (pintype "input"))
      (node (ref "EF39") (pin "AV1") (pinfunction "AV1_AV1") (pintype "output"))
      (node (ref "H10") (pin "U2") (pinfunction "IN2_U2") (pintype "input"))
    )
    (net (code "93") (name "AC11_") (class "Default")
      (node (ref "EF39") (pin "AV2") (pinfunction "AV2_AV2") (pintype "output"))
      (node (ref "F24") (pin "U2") (pinfunction "IN4_U2") (pintype "input"))
      (node (ref "F40") (pin "B1") (pinfunction "P$2_B1") (pintype "bidirectional"))
    )
    (net (code "94") (name "ACBAR_ENABLE") (class "Default")
      (node (ref "E32") (pin "V2") (pinfunction "OUT_V2") (pintype "open_collector"))
      (node (ref "EF34") (pin "BJ2") (pinfunction "BJ2_BJ2") (pintype "input"))
      (node (ref "EF35") (pin "BJ2") (pinfunction "BJ2_BJ2") (pintype "input"))
      (node (ref "EF36") (pin "BJ2") (pinfunction "BJ2_BJ2") (pintype "input"))
      (node (ref "EF37") (pin "BJ2") (pinfunction "BJ2_BJ2") (pintype "input"))
      (node (ref "EF38") (pin "BJ2") (pinfunction "BJ2_BJ2") (pintype "input"))
      (node (ref "EF39") (pin "BJ2") (pinfunction "BJ2_BJ2") (pintype "input"))
    )
    (net (code "95") (name "AC_CLEAR") (class "Default")
      (node (ref "F29") (pin "J2") (pinfunction "IN2_J2") (pintype "input"))
      (node (ref "J15") (pin "L1") (pinfunction "OUT_L1") (pintype "output"))
    )
    (net (code "96") (name "AC_CLEAR_") (class "Default")
      (node (ref "E30") (pin "K2") (pinfunction "IN2B_K2") (pintype "input"))
      (node (ref "F29") (pin "K2") (pinfunction "OUT_K2") (pintype "output"))
    )
    (net (code "97") (name "AC_ENABLE") (class "Default")
      (node (ref "E32") (pin "S1") (pinfunction "OUT_S1") (pintype "open_collector"))
      (node (ref "EF34") (pin "BH2") (pinfunction "BH2_BH2") (pintype "input"))
      (node (ref "EF35") (pin "BH2") (pinfunction "BH2_BH2") (pintype "input"))
      (node (ref "EF36") (pin "BH2") (pinfunction "BH2_BH2") (pintype "input"))
      (node (ref "EF37") (pin "BH2") (pinfunction "BH2_BH2") (pintype "input"))
      (node (ref "EF38") (pin "BH2") (pinfunction "BH2_BH2") (pintype "input"))
      (node (ref "EF39") (pin "BH2") (pinfunction "BH2_BH2") (pintype "input"))
    )
    (net (code "98") (name "AC_LOAD") (class "Default")
      (node (ref "E32") (pin "P2") (pinfunction "OUT_P2") (pintype "open_collector"))
      (node (ref "E33") (pin "S2") (pinfunction "C_S2") (pintype "input"))
      (node (ref "EF34") (pin "AU1") (pinfunction "AU1_AU1") (pintype "input"))
      (node (ref "EF35") (pin "AU1") (pinfunction "AU1_AU1") (pintype "input"))
      (node (ref "EF36") (pin "AU1") (pinfunction "AU1_AU1") (pintype "input"))
      (node (ref "EF37") (pin "AU1") (pinfunction "AU1_AU1") (pintype "input"))
      (node (ref "EF38") (pin "AU1") (pinfunction "AU1_AU1") (pintype "input"))
      (node (ref "EF39") (pin "AU1") (pinfunction "AU1_AU1") (pintype "input"))
    )
    (net (code "99") (name "AC_TO_MQ_ENABLE") (class "Default")
      (node (ref "C14") (pin "D1") (pinfunction "IN1_D1") (pintype "input"))
      (node (ref "C14") (pin "H2") (pinfunction "IN1_H2") (pintype "input"))
      (node (ref "C14") (pin "P1") (pinfunction "IN1_P1") (pintype "input"))
      (node (ref "C15") (pin "D1") (pinfunction "IN1_D1") (pintype "input"))
      (node (ref "C15") (pin "H2") (pinfunction "IN1_H2") (pintype "input"))
      (node (ref "C15") (pin "P1") (pinfunction "IN1_P1") (pintype "input"))
      (node (ref "C16") (pin "D1") (pinfunction "IN1_D1") (pintype "input"))
      (node (ref "C16") (pin "H2") (pinfunction "IN1_H2") (pintype "input"))
      (node (ref "C16") (pin "P1") (pinfunction "IN1_P1") (pintype "input"))
      (node (ref "C17") (pin "D1") (pinfunction "IN1_D1") (pintype "input"))
      (node (ref "C17") (pin "H2") (pinfunction "IN1_H2") (pintype "input"))
      (node (ref "C17") (pin "P1") (pinfunction "IN1_P1") (pintype "input"))
      (node (ref "D15") (pin "S1") (pinfunction "OUT_S1") (pintype "output"))
    )
    (net (code "100") (name "AC_TO_MQ_ENABLE_") (class "Default")
      (node (ref "D15") (pin "R1") (pinfunction "IN2_R1") (pintype "input"))
      (node (ref "D21") (pin "L1") (pinfunction "OUT_L1") (pintype "output"))
      (node (ref "E30") (pin "F2") (pinfunction "IN1C_F2") (pintype "input"))
    )
    (net (code "101") (name "ADDER00") (class "Default")
      (node (ref "EF34") (pin "AE2") (pinfunction "AE2_AE2") (pintype "output"))
      (node (ref "EF35") (pin "AB1") (pinfunction "AB1_AB1") (pintype "input"))
      (node (ref "EF39") (pin "AJ2") (pinfunction "AJ2_AJ2") (pintype "input"))
      (node (ref "F33") (pin "K1") (pinfunction "IN4A_K1") (pintype "input"))
    )
    (net (code "102") (name "ADDER01") (class "Default")
      (node (ref "EF34") (pin "AF1") (pinfunction "AF1_AF1") (pintype "output"))
      (node (ref "EF35") (pin "AC1") (pinfunction "AC1_AC1") (pintype "input"))
      (node (ref "F33") (pin "M1") (pinfunction "IN5A_M1") (pintype "input"))
    )
    (net (code "103") (name "ADDER02") (class "Default")
      (node (ref "EF34") (pin "AH2") (pinfunction "AH2_AH2") (pintype "input"))
      (node (ref "EF35") (pin "AE2") (pinfunction "AE2_AE2") (pintype "output"))
      (node (ref "EF35") (pin "BB2") (pinfunction "BB2_BB2") (pintype "input"))
      (node (ref "EF36") (pin "AB1") (pinfunction "AB1_AB1") (pintype "input"))
    )
    (net (code "104") (name "ADDER03") (class "Default")
      (node (ref "EF34") (pin "AJ2") (pinfunction "AJ2_AJ2") (pintype "input"))
      (node (ref "EF35") (pin "AF1") (pinfunction "AF1_AF1") (pintype "output"))
      (node (ref "EF36") (pin "AC1") (pinfunction "AC1_AC1") (pintype "input"))
    )
    (net (code "105") (name "ADDER04") (class "Default")
      (node (ref "EF35") (pin "AH2") (pinfunction "AH2_AH2") (pintype "input"))
      (node (ref "EF36") (pin "AE2") (pinfunction "AE2_AE2") (pintype "output"))
      (node (ref "EF36") (pin "BB2") (pinfunction "BB2_BB2") (pintype "input"))
      (node (ref "EF37") (pin "AB1") (pinfunction "AB1_AB1") (pintype "input"))
    )
    (net (code "106") (name "ADDER05") (class "Default")
      (node (ref "EF35") (pin "AJ2") (pinfunction "AJ2_AJ2") (pintype "input"))
      (node (ref "EF36") (pin "AF1") (pinfunction "AF1_AF1") (pintype "output"))
      (node (ref "EF37") (pin "AC1") (pinfunction "AC1_AC1") (pintype "input"))
    )
    (net (code "107") (name "ADDER06") (class "Default")
      (node (ref "EF36") (pin "AH2") (pinfunction "AH2_AH2") (pintype "input"))
      (node (ref "EF37") (pin "AE2") (pinfunction "AE2_AE2") (pintype "output"))
      (node (ref "EF37") (pin "BB2") (pinfunction "BB2_BB2") (pintype "input"))
      (node (ref "EF38") (pin "AB1") (pinfunction "AB1_AB1") (pintype "input"))
    )
    (net (code "108") (name "ADDER07") (class "Default")
      (node (ref "EF36") (pin "AJ2") (pinfunction "AJ2_AJ2") (pintype "input"))
      (node (ref "EF37") (pin "AF1") (pinfunction "AF1_AF1") (pintype "output"))
      (node (ref "EF38") (pin "AC1") (pinfunction "AC1_AC1") (pintype "input"))
    )
    (net (code "109") (name "ADDER08") (class "Default")
      (node (ref "EF37") (pin "AH2") (pinfunction "AH2_AH2") (pintype "input"))
      (node (ref "EF38") (pin "AE2") (pinfunction "AE2_AE2") (pintype "output"))
      (node (ref "EF38") (pin "BB2") (pinfunction "BB2_BB2") (pintype "input"))
      (node (ref "EF39") (pin "AB1") (pinfunction "AB1_AB1") (pintype "input"))
    )
    (net (code "110") (name "ADDER09") (class "Default")
      (node (ref "EF37") (pin "AJ2") (pinfunction "AJ2_AJ2") (pintype "input"))
      (node (ref "EF38") (pin "AF1") (pinfunction "AF1_AF1") (pintype "output"))
      (node (ref "EF39") (pin "AC1") (pinfunction "AC1_AC1") (pintype "input"))
    )
    (net (code "111") (name "ADDER10") (class "Default")
      (node (ref "EF38") (pin "AH2") (pinfunction "AH2_AH2") (pintype "input"))
      (node (ref "EF39") (pin "AE2") (pinfunction "AE2_AE2") (pintype "output"))
      (node (ref "EF39") (pin "BB2") (pinfunction "BB2_BB2") (pintype "input"))
      (node (ref "F33") (pin "E1") (pinfunction "IN2A_E1") (pintype "input"))
    )
    (net (code "112") (name "ADDER11") (class "Default")
      (node (ref "EF34") (pin "AB1") (pinfunction "AB1_AB1") (pintype "input"))
      (node (ref "EF38") (pin "AJ2") (pinfunction "AJ2_AJ2") (pintype "input"))
      (node (ref "EF39") (pin "AF1") (pinfunction "AF1_AF1") (pintype "output"))
      (node (ref "F32") (pin "P1") (pinfunction "IN1_P1") (pintype "input"))
    )
    (net (code "113") (name "ADDER11_") (class "Default")
      (node (ref "C14") (pin "B1") (pinfunction "IN2_B1") (pintype "input"))
      (node (ref "F28") (pin "P1") (pinfunction "IN1_P1") (pintype "input"))
      (node (ref "F32") (pin "S1") (pinfunction "OUT_S1") (pintype "output"))
    )
    (net (code "114") (name "ADDER_L") (class "Default")
      (node (ref "C18") (pin "V2") (pinfunction "OUT_V2") (pintype "output"))
      (node (ref "D19") (pin "F1") (pinfunction "IN2_F1") (pintype "input"))
      (node (ref "D23") (pin "L2") (pinfunction "IN3A_L2") (pintype "input"))
    )
    (net (code "115") (name "ADDER_L_") (class "Default")
      (node (ref "C18") (pin "T2") (pinfunction "IN1_T2") (pintype "input"))
      (node (ref "D23") (pin "K2") (pinfunction "IN2B_K2") (pintype "input"))
      (node (ref "E24") (pin "B1") (pinfunction "IN2_B1") (pintype "input"))
      (node (ref "EF34") (pin "AC1") (pinfunction "AC1_AC1") (pintype "input"))
      (node (ref "EF34") (pin "BB2") (pinfunction "BB2_BB2") (pintype "input"))
      (node (ref "F33") (pin "H1") (pinfunction "IN3A_H1") (pintype "input"))
      (node (ref "F33") (pin "V2") (pinfunction "OUT_V2") (pintype "output"))
    )
    (net (code "116") (name "ADD_") (class "Default")
      (node (ref "E32") (pin "P1") (pinfunction "IN3_P1") (pintype "input"))
      (node (ref "F28") (pin "D1") (pinfunction "OUT_D1") (pintype "output"))
      (node (ref "F31") (pin "A1") (pinfunction "IN1_A1") (pintype "input"))
    )
    (net (code "117") (name "ADD_ACCEPTED_") (class "Default")
      (node (ref "E33") (pin "E1") (pinfunction "1_E1") (pintype "output"))
      (node (ref "H20") (pin "N2") (pinfunction "IN2_N2") (pintype "input"))
    )
    (net (code "118") (name "AND") (class "Default")
      (node (ref "E22") (pin "C1") (pinfunction "OUT_C1") (pintype "output"))
      (node (ref "F26") (pin "P1") (pinfunction "IN1_P1") (pintype "input"))
    )
    (net (code "119") (name "AND_") (class "Default")
      (node (ref "D40") (pin "M2") (pinfunction "P$2_M2") (pintype "bidirectional"))
      (node (ref "E21") (pin "H2") (pinfunction "OUT_H2") (pintype "output"))
      (node (ref "E22") (pin "A1") (pinfunction "IN1_A1") (pintype "input"))
      (node (ref "F26") (pin "T2") (pinfunction "IN1_T2") (pintype "input"))
    )
    (net (code "120") (name "AND_ENABLE") (class "Default")
      (node (ref "E31") (pin "V2") (pinfunction "OUT_V2") (pintype "open_collector"))
      (node (ref "EF34") (pin "AA1") (pinfunction "AA1_AA1") (pintype "input"))
      (node (ref "EF35") (pin "AA1") (pinfunction "AA1_AA1") (pintype "input"))
      (node (ref "EF36") (pin "AA1") (pinfunction "AA1_AA1") (pintype "input"))
      (node (ref "EF37") (pin "AA1") (pinfunction "AA1_AA1") (pintype "input"))
      (node (ref "EF38") (pin "AA1") (pinfunction "AA1_AA1") (pintype "input"))
      (node (ref "EF39") (pin "AA1") (pinfunction "AA1_AA1") (pintype "input"))
    )
    (net (code "121") (name "AND_ENABLE_") (class "Default")
      (node (ref "E31") (pin "R2") (pinfunction "IN1_R2") (pintype "input"))
      (node (ref "E32") (pin "M1") (pinfunction "IN1_M1") (pintype "input"))
      (node (ref "F26") (pin "U1") (pinfunction "OUT_U1") (pintype "output"))
    )
    (net (code "122") (name "ASR_ENABLE") (class "Default")
      (node (ref "D15") (pin "V2") (pinfunction "OUT_V2") (pintype "output"))
      (node (ref "D18") (pin "K2") (pinfunction "IN2_K2") (pintype "input"))
      (node (ref "F33") (pin "R2") (pinfunction "IN4C_R2") (pintype "input"))
    )
    (net (code "123") (name "ASR_L_SET_") (class "Default")
      (node (ref "D18") (pin "M2") (pinfunction "OUT_M2") (pintype "output"))
      (node (ref "F33") (pin "B1") (pinfunction "IN1B_B1") (pintype "input"))
    )
    (net (code "124") (name "AUTO_INDEX_") (class "Default")
      (node (ref "F27") (pin "K2") (pinfunction "IN1_K2") (pintype "input"))
      (node (ref "F27") (pin "S1") (pinfunction "OUT_S1") (pintype "output"))
    )
    (net (code "125") (name "BB_LEFT_SHIFT") (class "Default")
      (node (ref "C16") (pin "D2") (pinfunction "IN1_D2") (pintype "input"))
      (node (ref "C16") (pin "L1") (pinfunction "IN1_L1") (pintype "input"))
      (node (ref "C16") (pin "P2") (pinfunction "IN1_P2") (pintype "input"))
      (node (ref "C17") (pin "D2") (pinfunction "IN1_D2") (pintype "input"))
      (node (ref "C17") (pin "L1") (pinfunction "IN1_L1") (pintype "input"))
      (node (ref "C17") (pin "P2") (pinfunction "IN1_P2") (pintype "input"))
      (node (ref "D12") (pin "V2") (pinfunction "OUT_V2") (pintype "output"))
    )
    (net (code "126") (name "BF0") (class "Default")
      (node (ref "A16") (pin "E2") (pinfunction "IN2_E2") (pintype "input"))
      (node (ref "B18") (pin "P2") (pinfunction "1_P2") (pintype "output"))
    )
    (net (code "127") (name "BF1") (class "Default")
      (node (ref "A16") (pin "M1") (pinfunction "IN2_M1") (pintype "input"))
      (node (ref "B18") (pin "S1") (pinfunction "1_S1") (pintype "output"))
    )
    (net (code "128") (name "BF2") (class "Default")
      (node (ref "A16") (pin "R2") (pinfunction "IN2_R2") (pintype "input"))
      (node (ref "B18") (pin "V2") (pinfunction "1_V2") (pintype "output"))
    )
    (net (code "129") (name "BF_ENABLE") (class "Default")
      (node (ref "A16") (pin "D2") (pinfunction "IN1_D2") (pintype "input"))
      (node (ref "A16") (pin "L1") (pinfunction "IN1_L1") (pintype "input"))
      (node (ref "A16") (pin "P2") (pinfunction "IN1_P2") (pintype "input"))
      (node (ref "B11") (pin "M1") (pinfunction "0_M1") (pintype "output"))
    )
    (net (code "130") (name "BMA00") (class "Default")
      (node (ref "B14") (pin "E1") (pinfunction "OUT_E1") (pintype "open_collector"))
      (node (ref "H01") (pin "K2") (pinfunction "P$2_K2") (pintype "bidirectional"))
    )
    (net (code "131") (name "BMA01") (class "Default")
      (node (ref "B14") (pin "J2") (pinfunction "OUT_J2") (pintype "open_collector"))
      (node (ref "H01") (pin "M2") (pinfunction "P$2_M2") (pintype "bidirectional"))
    )
    (net (code "132") (name "BMA02") (class "Default")
      (node (ref "B14") (pin "L1") (pinfunction "OUT_L1") (pintype "open_collector"))
      (node (ref "H01") (pin "P2") (pinfunction "P$2_P2") (pintype "bidirectional"))
    )
    (net (code "133") (name "BMA03") (class "Default")
      (node (ref "B14") (pin "P2") (pinfunction "OUT_P2") (pintype "open_collector"))
      (node (ref "H01") (pin "S2") (pinfunction "P$2_S2") (pintype "bidirectional"))
    )
    (net (code "134") (name "BMA04") (class "Default")
      (node (ref "B14") (pin "S1") (pinfunction "OUT_S1") (pintype "open_collector"))
      (node (ref "H01") (pin "T2") (pinfunction "P$2_T2") (pintype "bidirectional"))
    )
    (net (code "135") (name "BMA05") (class "Default")
      (node (ref "B14") (pin "V2") (pinfunction "OUT_V2") (pintype "open_collector"))
      (node (ref "H01") (pin "V2") (pinfunction "P$2_V2") (pintype "bidirectional"))
    )
    (net (code "136") (name "BMA06") (class "Default")
      (node (ref "B15") (pin "E1") (pinfunction "OUT_E1") (pintype "open_collector"))
      (node (ref "H02") (pin "D2") (pinfunction "P$2_D2") (pintype "bidirectional"))
    )
    (net (code "137") (name "BMA07") (class "Default")
      (node (ref "B15") (pin "J2") (pinfunction "OUT_J2") (pintype "open_collector"))
      (node (ref "H02") (pin "E2") (pinfunction "P$2_E2") (pintype "bidirectional"))
    )
    (net (code "138") (name "BMA08") (class "Default")
      (node (ref "B15") (pin "L1") (pinfunction "OUT_L1") (pintype "open_collector"))
      (node (ref "H02") (pin "H2") (pinfunction "P$2_H2") (pintype "bidirectional"))
    )
    (net (code "139") (name "BMA09") (class "Default")
      (node (ref "B15") (pin "P2") (pinfunction "OUT_P2") (pintype "open_collector"))
      (node (ref "H02") (pin "K2") (pinfunction "P$2_K2") (pintype "bidirectional"))
    )
    (net (code "140") (name "BMA10") (class "Default")
      (node (ref "B15") (pin "S1") (pinfunction "OUT_S1") (pintype "open_collector"))
      (node (ref "H02") (pin "M2") (pinfunction "P$2_M2") (pintype "bidirectional"))
    )
    (net (code "141") (name "BMA11") (class "Default")
      (node (ref "B15") (pin "V2") (pinfunction "OUT_V2") (pintype "open_collector"))
      (node (ref "H02") (pin "P2") (pinfunction "P$2_P2") (pintype "bidirectional"))
    )
    (net (code "142") (name "BREAK") (class "Default")
      (node (ref "E11") (pin "T2") (pinfunction "IN1_T2") (pintype "input"))
      (node (ref "E23") (pin "V2") (pinfunction "1_V2") (pintype "output"))
      (node (ref "E27") (pin "S2") (pinfunction "IN4D_S2") (pintype "input"))
      (node (ref "E29") (pin "L2") (pinfunction "IN3A_L2") (pintype "input"))
      (node (ref "F28") (pin "L1") (pinfunction "IN2_L1") (pintype "input"))
    )
    (net (code "143") (name "BREAK_") (class "Default")
      (node (ref "D40") (pin "E2") (pinfunction "P$2_E2") (pintype "bidirectional"))
      (node (ref "E23") (pin "V1") (pinfunction "0_V1") (pintype "output"))
      (node (ref "H20") (pin "H2") (pinfunction "IN2_H2") (pintype "input"))
    )
    (net (code "144") (name "BREAK_OK") (class "Default")
      (node (ref "F22") (pin "N1") (pinfunction "OUT_N1") (pintype "output"))
      (node (ref "F22") (pin "P1") (pinfunction "IN1_P1") (pintype "input"))
      (node (ref "F22") (pin "U2") (pinfunction "IN2_U2") (pintype "input"))
      (node (ref "F29") (pin "M1") (pinfunction "IN2_M1") (pintype "input"))
    )
    (net (code "145") (name "BREAK_OK_") (class "Default")
      (node (ref "E33") (pin "C1") (pinfunction "D_C1") (pintype "input"))
      (node (ref "F22") (pin "L1") (pinfunction "IN1_L1") (pintype "input"))
      (node (ref "F23") (pin "N1") (pinfunction "IN2_N1") (pintype "input"))
      (node (ref "F23") (pin "P2") (pinfunction "OUT_P2") (pintype "output"))
    )
    (net (code "146") (name "BRK_RQST") (class "Default")
      (node (ref "E20") (pin "M2") (pinfunction "D_M2") (pintype "input"))
      (node (ref "J15") (pin "S1") (pinfunction "OUT_S1") (pintype "output"))
    )
    (net (code "147") (name "BRK_SYNC") (class "Default")
      (node (ref "E20") (pin "P2") (pinfunction "1_P2") (pintype "output"))
      (node (ref "F23") (pin "L2") (pinfunction "IN2_L2") (pintype "input"))
    )
    (net (code "148") (name "BSTLR") (class "Default")
      (node (ref "C07") (pin "S2") (pinfunction "OUT_S2") (pintype "output"))
      (node (ref "D04") (pin "M2") (pinfunction "P$2_M2") (pintype "bidirectional"))
    )
    (net (code "149") (name "BTP2") (class "Default")
      (node (ref "F08") (pin "K2") (pinfunction "OUT_K2") (pintype "output"))
      (node (ref "H05") (pin "V2") (pinfunction "P$2_V2") (pintype "bidirectional"))
    )
    (net (code "150") (name "BTP3") (class "Default")
      (node (ref "C08") (pin "D2") (pinfunction "OUT_D2") (pintype "output"))
      (node (ref "D04") (pin "E2") (pinfunction "P$2_E2") (pintype "bidirectional"))
    )
    (net (code "151") (name "B_C_") (class "Default")
      (node (ref "C07") (pin "K2") (pinfunction "OUT_K2") (pintype "output"))
      (node (ref "D04") (pin "K2") (pinfunction "P$2_K2") (pintype "bidirectional"))
    )
    (net (code "152") (name "B_DC_INST") (class "Default")
      (node (ref "C08") (pin "S2") (pinfunction "OUT_S2") (pintype "output"))
      (node (ref "D04") (pin "P2") (pinfunction "P$2_P2") (pintype "bidirectional"))
    )
    (net (code "153") (name "B_EAE_ON") (class "Default")
      (node (ref "D12") (pin "J1") (pinfunction "IN2_J1") (pintype "input"))
      (node (ref "D13") (pin "B1") (pinfunction "IN2_B1") (pintype "input"))
      (node (ref "D13") (pin "K1") (pinfunction "OUT_K1") (pintype "output"))
      (node (ref "D17") (pin "C1") (pinfunction "IN3_C1") (pintype "input"))
      (node (ref "D17") (pin "K1") (pinfunction "IN1_K1") (pintype "input"))
      (node (ref "D17") (pin "L2") (pinfunction "IN3_L2") (pintype "input"))
      (node (ref "D18") (pin "A1") (pinfunction "IN1_A1") (pintype "input"))
      (node (ref "D18") (pin "P1") (pinfunction "IN1_P1") (pintype "input"))
      (node (ref "D18") (pin "R2") (pinfunction "IN3_R2") (pintype "input"))
      (node (ref "D20") (pin "E2") (pinfunction "IN2_E2") (pintype "input"))
      (node (ref "D20") (pin "J1") (pinfunction "IN3_J1") (pintype "input"))
      (node (ref "F33") (pin "P2") (pinfunction "IN4B_P2") (pintype "input"))
    )
    (net (code "154") (name "B_EXECUTE") (class "Default")
      (node (ref "D13") (pin "M2") (pinfunction "IN2_M2") (pintype "input"))
      (node (ref "D14") (pin "E2") (pinfunction "IN2_E2") (pintype "input"))
      (node (ref "D21") (pin "H2") (pinfunction "IN4_H2") (pintype "input"))
      (node (ref "E26") (pin "H2") (pinfunction "IN1D_H2") (pintype "input"))
      (node (ref "E27") (pin "B1") (pinfunction "IN1B_B1") (pintype "input"))
      (node (ref "E27") (pin "N1") (pinfunction "IN5B_N1") (pintype "input"))
      (node (ref "E28") (pin "E2") (pinfunction "IN1B_E2") (pintype "input"))
      (node (ref "E29") (pin "D2") (pinfunction "IN1A_D2") (pintype "input"))
      (node (ref "E29") (pin "K2") (pinfunction "IN2B_K2") (pintype "input"))
      (node (ref "E30") (pin "N1") (pinfunction "IN5B_N1") (pintype "input"))
      (node (ref "E30") (pin "R2") (pinfunction "IN4C_R2") (pintype "input"))
      (node (ref "F25") (pin "R2") (pinfunction "IN2_R2") (pintype "input"))
      (node (ref "F26") (pin "P2") (pinfunction "IN2_P2") (pintype "input"))
      (node (ref "F26") (pin "S1") (pinfunction "IN3_S1") (pintype "input"))
      (node (ref "F28") (pin "C1") (pinfunction "IN3_C1") (pintype "input"))
      (node (ref "F28") (pin "F1") (pinfunction "IN2_F1") (pintype "input"))
      (node (ref "F31") (pin "V2") (pinfunction "OUT_V2") (pintype "open_collector"))
    )
    (net (code "155") (name "B_EXT_INST") (class "Default")
      (node (ref "A06") (pin "N1") (pinfunction "OUT_N1") (pintype "output"))
      (node (ref "A20") (pin "K1") (pinfunction "IN1_K1") (pintype "input"))
      (node (ref "A20") (pin "N2") (pinfunction "IN1_N2") (pintype "input"))
      (node (ref "A20") (pin "P1") (pinfunction "IN1_P1") (pintype "input"))
      (node (ref "B04") (pin "C1") (pinfunction "IN3_C1") (pintype "input"))
    )
    (net (code "156") (name "B_FETCH") (class "Default")
      (node (ref "B16") (pin "K2") (pinfunction "IN1_K2") (pintype "input"))
      (node (ref "D10") (pin "N2") (pinfunction "IN4_N2") (pintype "input"))
      (node (ref "D20") (pin "M1") (pinfunction "IN1_M1") (pintype "input"))
      (node (ref "E22") (pin "M1") (pinfunction "IN2_M1") (pintype "input"))
      (node (ref "E25") (pin "K2") (pinfunction "IN2_K2") (pintype "input"))
      (node (ref "E25") (pin "U2") (pinfunction "IN2_U2") (pintype "input"))
      (node (ref "E26") (pin "D1") (pinfunction "IN1D_D1") (pintype "input"))
      (node (ref "E26") (pin "R2") (pinfunction "IN4C_R2") (pintype "input"))
      (node (ref "F09") (pin "A1") (pinfunction "IN1_A1") (pintype "input"))
      (node (ref "F19") (pin "S2") (pinfunction "IN2_S2") (pintype "input"))
      (node (ref "F20") (pin "P1") (pinfunction "IN1_P1") (pintype "input"))
      (node (ref "F21") (pin "J1") (pinfunction "IN2_J1") (pintype "input"))
      (node (ref "F23") (pin "H1") (pinfunction "IN2_H1") (pintype "input"))
      (node (ref "F27") (pin "C1") (pinfunction "IN3_C1") (pintype "input"))
      (node (ref "F27") (pin "J1") (pinfunction "IN3_J1") (pintype "input"))
      (node (ref "F27") (pin "T2") (pinfunction "IN3_T2") (pintype "input"))
      (node (ref "F31") (pin "S1") (pinfunction "OUT_S1") (pintype "open_collector"))
    )
    (net (code "157") (name "B_LEFT_SHIFT") (class "Default")
      (node (ref "C14") (pin "D2") (pinfunction "IN1_D2") (pintype "input"))
      (node (ref "C14") (pin "L1") (pinfunction "IN1_L1") (pintype "input"))
      (node (ref "C14") (pin "P2") (pinfunction "IN1_P2") (pintype "input"))
      (node (ref "C15") (pin "D2") (pinfunction "IN1_D2") (pintype "input"))
      (node (ref "C15") (pin "L1") (pinfunction "IN1_L1") (pintype "input"))
      (node (ref "C15") (pin "P2") (pinfunction "IN1_P2") (pintype "input"))
      (node (ref "D12") (pin "K2") (pinfunction "OUT_K2") (pintype "output"))
    )
    (net (code "158") (name "B_LINE_HOLD_") (class "Default")
      (node (ref "C07") (pin "D2") (pinfunction "OUT_D2") (pintype "output"))
      (node (ref "D04") (pin "D2") (pinfunction "P$2_D2") (pintype "bidirectional"))
    )
    (net (code "159") (name "B_MEM_START") (class "Default")
      (node (ref "F08") (pin "D2") (pinfunction "OUT_D2") (pintype "output"))
      (node (ref "H05") (pin "M2") (pinfunction "P$2_M2") (pintype "bidirectional"))
    )
    (net (code "160") (name "B_MEM_TO_LSR") (class "Default")
      (node (ref "C08") (pin "K2") (pinfunction "OUT_K2") (pintype "output"))
      (node (ref "D04") (pin "H2") (pinfunction "P$2_H2") (pintype "bidirectional"))
    )
    (net (code "161") (name "B_POWER_CLEAR_") (class "Default")
      (node (ref "C12") (pin "S1") (pinfunction "OUT_S1") (pintype "open_collector"))
      (node (ref "D24") (pin "K2") (pinfunction "R_K2") (pintype "input"))
      (node (ref "E18") (pin "K2") (pinfunction "R_K2") (pintype "input"))
      (node (ref "EF10") (pin "AL2") (pinfunction "CL2_AL2") (pintype "input"))
      (node (ref "F20") (pin "R2") (pinfunction "IN2_R2") (pintype "input"))
    )
    (net (code "162") (name "B_R0_") (class "Default")
      (node (ref "D04") (pin "V2") (pinfunction "P$2_V2") (pintype "bidirectional"))
      (node (ref "D05") (pin "D2") (pinfunction "IN_D2") (pintype "input"))
      (node (ref "D05") (pin "E2") (pinfunction "IN2_E2") (pintype "bidirectional"))
      (node (ref "D05") (pin "F2") (pinfunction "IN3_F2") (pintype "input"))
      (node (ref "D05") (pin "H2") (pinfunction "IN4_H2") (pintype "input"))
    )
    (net (code "163") (name "B_SET") (class "Default")
      (node (ref "A19") (pin "E2") (pinfunction "IN2_E2") (pintype "input"))
      (node (ref "A19") (pin "M1") (pinfunction "IN2_M1") (pintype "input"))
      (node (ref "E23") (pin "T2") (pinfunction "D_T2") (pintype "input"))
      (node (ref "F22") (pin "S2") (pinfunction "OUT_S2") (pintype "output"))
    )
    (net (code "164") (name "B_SET_") (class "Default")
      (node (ref "A19") (pin "F2") (pinfunction "OUT_F2") (pintype "output"))
      (node (ref "B11") (pin "J1") (pinfunction "D_J1") (pintype "input"))
      (node (ref "B20") (pin "F2") (pinfunction "IN3_F2") (pintype "input"))
    )
    (net (code "165") (name "C") (class "Default")
      (node (ref "C10") (pin "P2") (pinfunction "IN1_P2") (pintype "input"))
      (node (ref "C11") (pin "E1") (pinfunction "IN1_E1") (pintype "input"))
      (node (ref "D09") (pin "E2") (pinfunction "IN2_E2") (pintype "input"))
      (node (ref "D10") (pin "N1") (pinfunction "IN2_N1") (pintype "input"))
      (node (ref "D10") (pin "S2") (pinfunction "IN2_S2") (pintype "input"))
      (node (ref "D11") (pin "J2") (pinfunction "0_J2") (pintype "output"))
    )
    (net (code "166") (name "CARRY_INSERT_") (class "Default")
      (node (ref "EF39") (pin "BJ1") (pinfunction "BJ1_BJ1") (pintype "input"))
      (node (ref "F32") (pin "C1") (pinfunction "OUT_C1") (pintype "output"))
    )
    (net (code "167") (name "CARRY_OUT0") (class "Default")
      (node (ref "E28") (pin "F2") (pinfunction "IN1C_F2") (pintype "input"))
      (node (ref "F21") (pin "B1") (pinfunction "IN2_B1") (pintype "input"))
      (node (ref "F32") (pin "V2") (pinfunction "OUT_V2") (pintype "output"))
      (node (ref "F33") (pin "U1") (pinfunction "IN1B_U1") (pintype "input"))
    )
    (net (code "168") (name "CARRY_OUT0_") (class "Default")
      (node (ref "EF34") (pin "BK2") (pinfunction "BK2_BK2") (pintype "output"))
      (node (ref "F32") (pin "U2") (pinfunction "IN2_U2") (pintype "input"))
      (node (ref "F33") (pin "U2") (pinfunction "IN2B_U2") (pintype "input"))
    )
    (net (code "169") (name "CARRY_OUT6_") (class "Default")
      (node (ref "EF36") (pin "BJ1") (pinfunction "BJ1_BJ1") (pintype "input"))
      (node (ref "EF37") (pin "BK2") (pinfunction "BK2_BK2") (pintype "output"))
    )
    (net (code "170") (name "CA_INCREMENT") (class "Default")
      (node (ref "E27") (pin "L2") (pinfunction "IN3A_L2") (pintype "input"))
      (node (ref "F25") (pin "F1") (pinfunction "OUT_F1") (pintype "output"))
    )
    (net (code "171") (name "CA_INCREMENT_") (class "Default")
      (node (ref "F25") (pin "D1") (pinfunction "IN1_D1") (pintype "input"))
      (node (ref "J20") (pin "L1") (pinfunction "OUT_L1") (pintype "output"))
    )
    (net (code "172") (name "CINT_") (class "Default")
      (node (ref "A05") (pin "L2") (pinfunction "IN1_L2") (pintype "input"))
      (node (ref "B04") (pin "D1") (pinfunction "OUT_D1") (pintype "output"))
    )
    (net (code "173") (name "CLEAR_DF_") (class "Default")
      (node (ref "B18") (pin "A1") (pinfunction "R_A1") (pintype "input"))
      (node (ref "B21") (pin "S2") (pinfunction "OUT_S2") (pintype "output"))
    )
    (net (code "174") (name "CLEAR_IB_") (class "Default")
      (node (ref "B17") (pin "K2") (pinfunction "R_K2") (pintype "input"))
      (node (ref "B21") (pin "N2") (pinfunction "OUT_N2") (pintype "output"))
    )
    (net (code "175") (name "CLEAR_IFDFBF_") (class "Default")
      (node (ref "B21") (pin "L2") (pinfunction "IN1_L2") (pintype "input"))
      (node (ref "B21") (pin "P1") (pinfunction "IN1_P1") (pintype "input"))
      (node (ref "B21") (pin "P2") (pinfunction "IN1_P2") (pintype "input"))
      (node (ref "E14") (pin "J1") (pinfunction "OUT_J1") (pintype "output"))
    )
    (net (code "176") (name "CLEAR_IF_") (class "Default")
      (node (ref "B05") (pin "A1") (pinfunction "R_A1") (pintype "input"))
      (node (ref "B17") (pin "A1") (pinfunction "R_A1") (pintype "input"))
      (node (ref "B21") (pin "S1") (pinfunction "OUT_S1") (pintype "output"))
    )
    (net (code "177") (name "CLR_PARITY_ERROR_") (class "Default")
      (node (ref "B07") (pin "S2") (pinfunction "OUT_S2") (pintype "output"))
      (node (ref "B11") (pin "N2") (pinfunction "S_N2") (pintype "input"))
    )
    (net (code "178") (name "CSR_ENABLE_") (class "Default")
      (node (ref "C11") (pin "E2") (pinfunction "IN2_E2") (pintype "input"))
      (node (ref "D07") (pin "F1") (pinfunction "OUT_F1") (pintype "output"))
    )
    (net (code "179") (name "CUF") (class "Default")
      (node (ref "B06") (pin "K2") (pinfunction "OUT_K2") (pintype "output"))
      (node (ref "B06") (pin "L1") (pinfunction "IN1_L1") (pintype "input"))
    )
    (net (code "180") (name "CUF_") (class "Default")
      (node (ref "B06") (pin "C1") (pinfunction "OUT_C1") (pintype "output"))
      (node (ref "B06") (pin "D1") (pinfunction "IN1_D1") (pintype "input"))
      (node (ref "B06") (pin "H2") (pinfunction "IN1_H2") (pintype "input"))
      (node (ref "F11") (pin "F2") (pinfunction "IN3_F2") (pintype "input"))
      (node (ref "F11") (pin "H2") (pinfunction "IN4_H2") (pintype "input"))
    )
    (net (code "181") (name "CURRENT_ADDRESS") (class "Default")
      (node (ref "E23") (pin "S1") (pinfunction "1_S1") (pintype "output"))
      (node (ref "E27") (pin "M2") (pinfunction "IN3B_M2") (pintype "input"))
      (node (ref "E29") (pin "L1") (pinfunction "IN4B_L1") (pintype "input"))
    )
    (net (code "182") (name "CURRENT_ADDRESS_") (class "Default")
      (node (ref "D40") (pin "E1") (pinfunction "P$2_E1") (pintype "bidirectional"))
      (node (ref "E23") (pin "U1") (pinfunction "0_U1") (pintype "output"))
      (node (ref "E25") (pin "F1") (pinfunction "IN2_F1") (pintype "input"))
      (node (ref "F22") (pin "R2") (pinfunction "IN2_R2") (pintype "input"))
    )
    (net (code "183") (name "C_") (class "Default")
      (node (ref "C07") (pin "M2") (pinfunction "IN1_M2") (pintype "input"))
      (node (ref "D09") (pin "N2") (pinfunction "IN1_N2") (pintype "input"))
      (node (ref "D11") (pin "H2") (pinfunction "1_H2") (pintype "output"))
    )
    (net (code "184") (name "C_NO_SHIFT_") (class "Default")
      (node (ref "D07") (pin "C1") (pinfunction "OUT_C1") (pintype "output"))
      (node (ref "E31") (pin "R1") (pinfunction "IN4_R1") (pintype "input"))
    )
    (net (code "185") (name "C_SET_") (class "Default")
      (node (ref "C11") (pin "A1") (pinfunction "IN1_A1") (pintype "input"))
      (node (ref "C11") (pin "R2") (pinfunction "IN3_R2") (pintype "input"))
      (node (ref "D10") (pin "J2") (pinfunction "OUT_J2") (pintype "output"))
      (node (ref "D11") (pin "E2") (pinfunction "D_E2") (pintype "input"))
    )
    (net (code "186") (name "DATA00") (class "Default")
      (node (ref "EF34") (pin "BM2") (pinfunction "BM2_BM2") (pintype "input"))
      (node (ref "J18") (pin "E1") (pinfunction "OUT_E1") (pintype "output"))
    )
    (net (code "187") (name "DATA01") (class "Default")
      (node (ref "EF34") (pin "BP2") (pinfunction "BP2_BP2") (pintype "input"))
      (node (ref "J18") (pin "J2") (pinfunction "OUT_J2") (pintype "output"))
    )
    (net (code "188") (name "DATA02") (class "Default")
      (node (ref "EF35") (pin "BM2") (pinfunction "BM2_BM2") (pintype "input"))
      (node (ref "J18") (pin "L1") (pinfunction "OUT_L1") (pintype "output"))
    )
    (net (code "189") (name "DATA03") (class "Default")
      (node (ref "EF35") (pin "BP2") (pinfunction "BP2_BP2") (pintype "input"))
      (node (ref "J18") (pin "P2") (pinfunction "OUT_P2") (pintype "output"))
    )
    (net (code "190") (name "DATA04") (class "Default")
      (node (ref "EF36") (pin "BM2") (pinfunction "BM2_BM2") (pintype "input"))
      (node (ref "J18") (pin "S1") (pinfunction "OUT_S1") (pintype "output"))
    )
    (net (code "191") (name "DATA05") (class "Default")
      (node (ref "EF36") (pin "BP2") (pinfunction "BP2_BP2") (pintype "input"))
      (node (ref "J18") (pin "V2") (pinfunction "OUT_V2") (pintype "output"))
    )
    (net (code "192") (name "DATA06") (class "Default")
      (node (ref "EF37") (pin "BM2") (pinfunction "BM2_BM2") (pintype "input"))
      (node (ref "J19") (pin "E1") (pinfunction "OUT_E1") (pintype "output"))
    )
    (net (code "193") (name "DATA07") (class "Default")
      (node (ref "EF37") (pin "BP2") (pinfunction "BP2_BP2") (pintype "input"))
      (node (ref "J19") (pin "J2") (pinfunction "OUT_J2") (pintype "output"))
    )
    (net (code "194") (name "DATA08") (class "Default")
      (node (ref "EF38") (pin "BM2") (pinfunction "BM2_BM2") (pintype "input"))
      (node (ref "J19") (pin "L1") (pinfunction "OUT_L1") (pintype "output"))
    )
    (net (code "195") (name "DATA09") (class "Default")
      (node (ref "EF38") (pin "BP2") (pinfunction "BP2_BP2") (pintype "input"))
      (node (ref "J19") (pin "P2") (pinfunction "OUT_P2") (pintype "output"))
    )
    (net (code "196") (name "DATA10") (class "Default")
      (node (ref "EF39") (pin "BM2") (pinfunction "BM2_BM2") (pintype "input"))
      (node (ref "J19") (pin "S1") (pinfunction "OUT_S1") (pintype "output"))
    )
    (net (code "197") (name "DATA11") (class "Default")
      (node (ref "EF39") (pin "BP2") (pinfunction "BP2_BP2") (pintype "input"))
      (node (ref "J19") (pin "V2") (pinfunction "OUT_V2") (pintype "output"))
    )
    (net (code "198") (name "DATA_ADD00") (class "Default")
      (node (ref "EF34") (pin "BS1") (pinfunction "BS1_BS1") (pintype "input"))
      (node (ref "J16") (pin "E1") (pinfunction "OUT_E1") (pintype "output"))
    )
    (net (code "199") (name "DATA_ADD01") (class "Default")
      (node (ref "EF34") (pin "BU1") (pinfunction "BU1_BU1") (pintype "input"))
      (node (ref "J16") (pin "J2") (pinfunction "OUT_J2") (pintype "output"))
    )
    (net (code "200") (name "DATA_ADD02") (class "Default")
      (node (ref "EF35") (pin "BS1") (pinfunction "BS1_BS1") (pintype "input"))
      (node (ref "J16") (pin "L1") (pinfunction "OUT_L1") (pintype "output"))
    )
    (net (code "201") (name "DATA_ADD03") (class "Default")
      (node (ref "EF35") (pin "BU1") (pinfunction "BU1_BU1") (pintype "input"))
      (node (ref "J16") (pin "P2") (pinfunction "OUT_P2") (pintype "output"))
    )
    (net (code "202") (name "DATA_ADD04") (class "Default")
      (node (ref "EF36") (pin "BS1") (pinfunction "BS1_BS1") (pintype "input"))
      (node (ref "J16") (pin "S1") (pinfunction "OUT_S1") (pintype "output"))
    )
    (net (code "203") (name "DATA_ADD05") (class "Default")
      (node (ref "EF36") (pin "BU1") (pinfunction "BU1_BU1") (pintype "input"))
      (node (ref "J16") (pin "V2") (pinfunction "OUT_V2") (pintype "output"))
    )
    (net (code "204") (name "DATA_ADD06") (class "Default")
      (node (ref "EF37") (pin "BS1") (pinfunction "BS1_BS1") (pintype "input"))
      (node (ref "J17") (pin "E1") (pinfunction "OUT_E1") (pintype "output"))
    )
    (net (code "205") (name "DATA_ADD07") (class "Default")
      (node (ref "EF37") (pin "BU1") (pinfunction "BU1_BU1") (pintype "input"))
      (node (ref "J17") (pin "J2") (pinfunction "OUT_J2") (pintype "output"))
    )
    (net (code "206") (name "DATA_ADD08") (class "Default")
      (node (ref "EF38") (pin "BS1") (pinfunction "BS1_BS1") (pintype "input"))
      (node (ref "J17") (pin "L1") (pinfunction "OUT_L1") (pintype "output"))
    )
    (net (code "207") (name "DATA_ADD09") (class "Default")
      (node (ref "EF38") (pin "BU1") (pinfunction "BU1_BU1") (pintype "input"))
      (node (ref "J17") (pin "P2") (pinfunction "OUT_P2") (pintype "output"))
    )
    (net (code "208") (name "DATA_ADD10") (class "Default")
      (node (ref "EF39") (pin "BS1") (pinfunction "BS1_BS1") (pintype "input"))
      (node (ref "J17") (pin "S1") (pinfunction "OUT_S1") (pintype "output"))
    )
    (net (code "209") (name "DATA_ADD11") (class "Default")
      (node (ref "EF39") (pin "BU1") (pinfunction "BU1_BU1") (pintype "input"))
      (node (ref "J17") (pin "V2") (pinfunction "OUT_V2") (pintype "output"))
    )
    (net (code "210") (name "DATA_ADD_ENABLE") (class "Default")
      (node (ref "EF34") (pin "BT2") (pinfunction "BT2_BT2") (pintype "input"))
      (node (ref "EF35") (pin "BT2") (pinfunction "BT2_BT2") (pintype "input"))
      (node (ref "EF36") (pin "BT2") (pinfunction "BT2_BT2") (pintype "input"))
      (node (ref "EF37") (pin "BT2") (pinfunction "BT2_BT2") (pintype "input"))
      (node (ref "EF38") (pin "BT2") (pinfunction "BT2_BT2") (pintype "input"))
      (node (ref "EF39") (pin "BT2") (pinfunction "BT2_BT2") (pintype "input"))
      (node (ref "F30") (pin "P2") (pinfunction "OUT_P2") (pintype "open_collector"))
    )
    (net (code "211") (name "DATA_ENABLE") (class "Default")
      (node (ref "EF34") (pin "BL1") (pinfunction "BL1_BL1") (pintype "input"))
      (node (ref "EF35") (pin "BL1") (pinfunction "BL1_BL1") (pintype "input"))
      (node (ref "EF36") (pin "BL1") (pinfunction "BL1_BL1") (pintype "input"))
      (node (ref "EF37") (pin "BL1") (pinfunction "BL1_BL1") (pintype "input"))
      (node (ref "EF38") (pin "BL1") (pinfunction "BL1_BL1") (pintype "input"))
      (node (ref "EF39") (pin "BL1") (pinfunction "BL1_BL1") (pintype "input"))
      (node (ref "F30") (pin "L1") (pinfunction "OUT_L1") (pintype "open_collector"))
    )
    (net (code "212") (name "DATA_IN") (class "Default")
      (node (ref "E29") (pin "M2") (pinfunction "IN3B_M2") (pintype "input"))
      (node (ref "F28") (pin "M1") (pinfunction "IN3_M1") (pintype "input"))
      (node (ref "F29") (pin "F2") (pinfunction "OUT_F2") (pintype "output"))
    )
    (net (code "213") (name "DATA_IN_") (class "Default")
      (node (ref "F29") (pin "D2") (pinfunction "IN1_D2") (pintype "input"))
      (node (ref "J15") (pin "V2") (pinfunction "OUT_V2") (pintype "output"))
    )
    (net (code "214") (name "DCA") (class "Default")
      (node (ref "E22") (pin "K2") (pinfunction "OUT_K2") (pintype "output"))
      (node (ref "E29") (pin "J2") (pinfunction "IN2A_J2") (pintype "input"))
      (node (ref "E30") (pin "S2") (pinfunction "IN4D_S2") (pintype "input"))
    )
    (net (code "215") (name "DCA_") (class "Default")
      (node (ref "D40") (pin "R2") (pinfunction "P$2_R2") (pintype "bidirectional"))
      (node (ref "E21") (pin "M2") (pinfunction "OUT_M2") (pintype "output"))
      (node (ref "E22") (pin "H2") (pinfunction "IN1_H2") (pintype "input"))
      (node (ref "F26") (pin "V2") (pinfunction "IN3_V2") (pintype "input"))
    )
    (net (code "216") (name "DC_INST_") (class "Default")
      (node (ref "C08") (pin "V2") (pinfunction "IN2_V2") (pintype "input"))
      (node (ref "D09") (pin "J1") (pinfunction "OUT_J1") (pintype "output"))
    )
    (net (code "217") (name "DEFER") (class "Default")
      (node (ref "B20") (pin "C1") (pinfunction "IN3_C1") (pintype "input"))
      (node (ref "E23") (pin "H2") (pinfunction "1_H2") (pintype "output"))
      (node (ref "E24") (pin "D1") (pinfunction "IN1_D1") (pintype "input"))
      (node (ref "E26") (pin "N1") (pinfunction "IN5B_N1") (pintype "input"))
      (node (ref "E29") (pin "C1") (pinfunction "IN1C_C1") (pintype "input"))
      (node (ref "E29") (pin "N1") (pinfunction "IN5B_N1") (pintype "input"))
      (node (ref "F25") (pin "M1") (pinfunction "IN2_M1") (pintype "input"))
    )
    (net (code "218") (name "DEFER_") (class "Default")
      (node (ref "D40") (pin "B1") (pinfunction "P$2_B1") (pintype "bidirectional"))
      (node (ref "E23") (pin "J2") (pinfunction "0_J2") (pintype "output"))
    )
    (net (code "219") (name "DF0") (class "Default")
      (node (ref "A11") (pin "E1") (pinfunction "IN2_E1") (pintype "input"))
      (node (ref "A16") (pin "E1") (pinfunction "IN2_E1") (pintype "input"))
      (node (ref "B18") (pin "E1") (pinfunction "1_E1") (pintype "output"))
      (node (ref "B19") (pin "M2") (pinfunction "D_M2") (pintype "input"))
    )
    (net (code "220") (name "DF0_") (class "Default")
      (node (ref "B18") (pin "F1") (pinfunction "0_F1") (pintype "output"))
      (node (ref "C40") (pin "J2") (pinfunction "P$2_J2") (pintype "bidirectional"))
    )
    (net (code "221") (name "DF1") (class "Default")
      (node (ref "A11") (pin "J2") (pinfunction "IN2_J2") (pintype "input"))
      (node (ref "A16") (pin "J2") (pinfunction "IN2_J2") (pintype "input"))
      (node (ref "B18") (pin "H2") (pinfunction "1_H2") (pintype "output"))
      (node (ref "B19") (pin "P1") (pinfunction "D_P1") (pintype "input"))
    )
    (net (code "222") (name "DF1_") (class "Default")
      (node (ref "B18") (pin "J2") (pinfunction "0_J2") (pintype "output"))
      (node (ref "C40") (pin "S1") (pinfunction "P$2_S1") (pintype "bidirectional"))
    )
    (net (code "223") (name "DF2") (class "Default")
      (node (ref "A11") (pin "R1") (pinfunction "IN2_R1") (pintype "input"))
      (node (ref "A16") (pin "R1") (pinfunction "IN2_R1") (pintype "input"))
      (node (ref "B18") (pin "L1") (pinfunction "1_L1") (pintype "output"))
      (node (ref "B19") (pin "T2") (pinfunction "D_T2") (pintype "input"))
    )
    (net (code "224") (name "DF2_") (class "Default")
      (node (ref "B18") (pin "M1") (pinfunction "0_M1") (pintype "output"))
      (node (ref "C40") (pin "P2") (pinfunction "P$2_P2") (pintype "bidirectional"))
    )
    (net (code "225") (name "DFSR0") (class "Default")
      (node (ref "A12") (pin "E1") (pinfunction "IN2_E1") (pintype "input"))
      (node (ref "A40") (pin "D2") (pinfunction "P$2_D2") (pintype "bidirectional"))
    )
    (net (code "226") (name "DFSR1") (class "Default")
      (node (ref "A12") (pin "J2") (pinfunction "IN2_J2") (pintype "input"))
      (node (ref "A40") (pin "E2") (pinfunction "P$2_E2") (pintype "bidirectional"))
    )
    (net (code "227") (name "DFSR2") (class "Default")
      (node (ref "A12") (pin "R1") (pinfunction "IN2_R1") (pintype "input"))
      (node (ref "A40") (pin "F2") (pinfunction "P$2_F2") (pintype "bidirectional"))
    )
    (net (code "228") (name "DF_ENABLE") (class "Default")
      (node (ref "A16") (pin "D1") (pinfunction "IN1_D1") (pintype "input"))
      (node (ref "A16") (pin "H2") (pinfunction "IN1_H2") (pintype "input"))
      (node (ref "A16") (pin "P1") (pinfunction "IN1_P1") (pintype "input"))
      (node (ref "B11") (pin "J2") (pinfunction "0_J2") (pintype "output"))
    )
    (net (code "229") (name "DF_ENABLE_") (class "Default")
      (node (ref "B11") (pin "E2") (pinfunction "D_E2") (pintype "input"))
      (node (ref "B20") (pin "D1") (pinfunction "OUT_D1") (pintype "output"))
      (node (ref "B20") (pin "D2") (pinfunction "IN1_D2") (pintype "input"))
    )
    (net (code "230") (name "DIV_LAST") (class "Default")
      (node (ref "D12") (pin "A1") (pinfunction "IN1_A1") (pintype "input"))
      (node (ref "D13") (pin "E2") (pinfunction "IN2_E2") (pintype "input"))
      (node (ref "D16") (pin "K1") (pinfunction "OUT_K1") (pintype "output"))
      (node (ref "D20") (pin "M2") (pinfunction "IN3_M2") (pintype "input"))
      (node (ref "D23") (pin "E1") (pinfunction "IN2A_E1") (pintype "input"))
    )
    (net (code "231") (name "DIV_LAST_") (class "Default")
      (node (ref "D12") (pin "C1") (pinfunction "OUT_C1") (pintype "output"))
      (node (ref "D12") (pin "D2") (pinfunction "IN1_D2") (pintype "input"))
      (node (ref "D12") (pin "L2") (pinfunction "IN1_L2") (pintype "input"))
      (node (ref "D17") (pin "J2") (pinfunction "IN1_J2") (pintype "input"))
      (node (ref "D20") (pin "H2") (pinfunction "IN4_H2") (pintype "input"))
    )
    (net (code "232") (name "DOUBLE_LEFT_ROTATE") (class "Default")
      (node (ref "E31") (pin "J2") (pinfunction "OUT_J2") (pintype "open_collector"))
      (node (ref "EF34") (pin "AH1") (pinfunction "AH1_AH1") (pintype "input"))
      (node (ref "EF35") (pin "AH1") (pinfunction "AH1_AH1") (pintype "input"))
      (node (ref "EF36") (pin "AH1") (pinfunction "AH1_AH1") (pintype "input"))
      (node (ref "EF37") (pin "AH1") (pinfunction "AH1_AH1") (pintype "input"))
      (node (ref "EF38") (pin "AH1") (pinfunction "AH1_AH1") (pintype "input"))
      (node (ref "EF39") (pin "AH1") (pinfunction "AH1_AH1") (pintype "input"))
      (node (ref "F33") (pin "N1") (pinfunction "IN5B_N1") (pintype "input"))
    )
    (net (code "233") (name "DOUBLE_RIGHT_ROTATE") (class "Default")
      (node (ref "E31") (pin "E1") (pinfunction "OUT_E1") (pintype "open_collector"))
      (node (ref "EF34") (pin "AD1") (pinfunction "AD1_AD1") (pintype "input"))
      (node (ref "EF35") (pin "AD1") (pinfunction "AD1_AD1") (pintype "input"))
      (node (ref "EF36") (pin "AD1") (pinfunction "AD1_AD1") (pintype "input"))
      (node (ref "EF37") (pin "AD1") (pinfunction "AD1_AD1") (pintype "input"))
      (node (ref "EF38") (pin "AD1") (pinfunction "AD1_AD1") (pintype "input"))
      (node (ref "EF39") (pin "AD1") (pinfunction "AD1_AD1") (pintype "input"))
      (node (ref "F33") (pin "F1") (pinfunction "IN2B_F1") (pintype "input"))
    )
    (net (code "234") (name "DVI") (class "Default")
      (node (ref "D12") (pin "B1") (pinfunction "IN2_B1") (pintype "input"))
      (node (ref "D16") (pin "M1") (pinfunction "IN2_M1") (pintype "input"))
      (node (ref "D16") (pin "S2") (pinfunction "OUT_S2") (pintype "output"))
      (node (ref "D17") (pin "F1") (pinfunction "IN2_F1") (pintype "input"))
      (node (ref "D17") (pin "M1") (pinfunction "IN3_M1") (pintype "input"))
      (node (ref "D20") (pin "N2") (pinfunction "IN4_N2") (pintype "input"))
      (node (ref "D23") (pin "F1") (pinfunction "IN2B_F1") (pintype "input"))
    )
    (net (code "235") (name "DVI_") (class "Default")
      (node (ref "D16") (pin "P2") (pinfunction "IN1_P2") (pintype "input"))
      (node (ref "D17") (pin "B1") (pinfunction "IN2_B1") (pintype "input"))
      (node (ref "D19") (pin "V1") (pinfunction "OUT_V1") (pintype "output"))
      (node (ref "D23") (pin "S2") (pinfunction "IN4D_S2") (pintype "input"))
    )
    (net (code "236") (name "D_SET") (class "Default")
      (node (ref "E23") (pin "E2") (pinfunction "D_E2") (pintype "input"))
      (node (ref "F22") (pin "K2") (pinfunction "OUT_K2") (pintype "output"))
    )
    (net (code "237") (name "D_SET_") (class "Default")
      (node (ref "E25") (pin "M2") (pinfunction "OUT_M2") (pintype "output"))
      (node (ref "F22") (pin "H2") (pinfunction "IN1_H2") (pintype "input"))
      (node (ref "F23") (pin "N2") (pinfunction "IN4_N2") (pintype "input"))
      (node (ref "F23") (pin "R1") (pinfunction "IN4_R1") (pintype "input"))
      (node (ref "F29") (pin "D1") (pinfunction "IN1_D1") (pintype "input"))
    )
    (net (code "238") (name "E09F1") (class "Default")
      (node (ref "E09") (pin "F1") (pinfunction "OUT_F1") (pintype "output"))
      (node (ref "E17") (pin "H2") (pinfunction "H2_H2") (pintype "input"))
    )
    (net (code "239") (name "E25D1") (class "Default")
      (node (ref "E25") (pin "D1") (pinfunction "OUT_D1") (pintype "output"))
      (node (ref "EF39") (pin "AH2") (pinfunction "AH2_AH2") (pintype "input"))
    )
    (net (code "240") (name "EA0") (class "Default")
      (node (ref "B16") (pin "E1") (pinfunction "OUT_E1") (pintype "open_collector"))
      (node (ref "H01") (pin "D2") (pinfunction "P$2_D2") (pintype "bidirectional"))
    )
    (net (code "241") (name "EA1") (class "Default")
      (node (ref "B16") (pin "J2") (pinfunction "OUT_J2") (pintype "open_collector"))
      (node (ref "H01") (pin "E2") (pinfunction "P$2_E2") (pintype "bidirectional"))
    )
    (net (code "242") (name "EA2") (class "Default")
      (node (ref "B16") (pin "L1") (pinfunction "OUT_L1") (pintype "open_collector"))
      (node (ref "H01") (pin "H2") (pinfunction "P$2_H2") (pintype "bidirectional"))
    )
    (net (code "243") (name "EAE_ACBAR_ENABLE_") (class "Default")
      (node (ref "D13") (pin "A1") (pinfunction "IN1_A1") (pintype "input"))
      (node (ref "D17") (pin "N1") (pinfunction "OUT_N1") (pintype "output"))
      (node (ref "D17") (pin "P1") (pinfunction "IN1_P1") (pintype "input"))
      (node (ref "E32") (pin "U2") (pinfunction "IN4_U2") (pintype "input"))
      (node (ref "F29") (pin "M2") (pinfunction "IN2_M2") (pintype "input"))
    )
    (net (code "244") (name "EAE_AC_ENABLE_") (class "Default")
      (node (ref "D13") (pin "C1") (pinfunction "OUT_C1") (pintype "output"))
      (node (ref "E32") (pin "R1") (pinfunction "IN4_R1") (pintype "input"))
    )
    (net (code "245") (name "EAE_BEGIN") (class "Default")
      (node (ref "D12") (pin "R2") (pinfunction "IN2_R2") (pintype "input"))
      (node (ref "D14") (pin "H1") (pinfunction "IN1_H1") (pintype "input"))
      (node (ref "D14") (pin "K2") (pinfunction "OUT_K2") (pintype "output"))
      (node (ref "D17") (pin "V2") (pinfunction "IN3_V2") (pintype "input"))
    )
    (net (code "246") (name "EAE_COMPLETE_") (class "Default")
      (node (ref "C22") (pin "T2") (pinfunction "D_T2") (pintype "input"))
      (node (ref "D15") (pin "J2") (pinfunction "IN2_J2") (pintype "input"))
      (node (ref "D23") (pin "R1") (pinfunction "OUT_R1") (pintype "output"))
    )
    (net (code "247") (name "EAE_END") (class "Default")
      (node (ref "C22") (pin "V2") (pinfunction "1_V2") (pintype "output"))
      (node (ref "E12") (pin "D2") (pinfunction "IN1_D2") (pintype "input"))
      (node (ref "E14") (pin "P2") (pinfunction "IN2_P2") (pintype "input"))
    )
    (net (code "248") (name "EAE_EXECUTE_") (class "Default")
      (node (ref "D13") (pin "N2") (pinfunction "OUT_N2") (pintype "output"))
      (node (ref "F28") (pin "U2") (pinfunction "IN2_U2") (pintype "input"))
    )
    (net (code "249") (name "EAE_E_SET_") (class "Default")
      (node (ref "D13") (pin "N1") (pinfunction "OUT_N1") (pintype "output"))
      (node (ref "F23") (pin "H2") (pinfunction "IN4_H2") (pintype "input"))
      (node (ref "F28") (pin "K2") (pinfunction "IN2_K2") (pintype "input"))
    )
    (net (code "250") (name "EAE_INST") (class "Default")
      (node (ref "D13") (pin "D1") (pinfunction "IN1_D1") (pintype "input"))
      (node (ref "D13") (pin "K2") (pinfunction "OUT_K2") (pintype "output"))
      (node (ref "D13") (pin "M1") (pinfunction "IN2_M1") (pintype "input"))
      (node (ref "D14") (pin "R2") (pinfunction "IN2_R2") (pintype "input"))
      (node (ref "D18") (pin "L1") (pinfunction "IN2_L1") (pintype "input"))
      (node (ref "D20") (pin "U2") (pinfunction "IN4_U2") (pintype "input"))
    )
    (net (code "251") (name "EAE_IR0") (class "Default")
      (node (ref "D18") (pin "B1") (pinfunction "IN2_B1") (pintype "input"))
      (node (ref "D20") (pin "R2") (pinfunction "IN1_R2") (pintype "input"))
      (node (ref "D24") (pin "E1") (pinfunction "1_E1") (pintype "output"))
    )
    (net (code "252") (name "EAE_IR0_") (class "Default")
      (node (ref "D15") (pin "H1") (pinfunction "IN1_H1") (pintype "input"))
      (node (ref "D19") (pin "N2") (pinfunction "IN1_N2") (pintype "input"))
      (node (ref "D19") (pin "P1") (pinfunction "IN1_P1") (pintype "input"))
      (node (ref "D19") (pin "T2") (pinfunction "IN1_T2") (pintype "input"))
      (node (ref "D20") (pin "F1") (pinfunction "IN1_F1") (pintype "input"))
      (node (ref "D24") (pin "F1") (pinfunction "0_F1") (pintype "output"))
    )
    (net (code "253") (name "EAE_IR1") (class "Default")
      (node (ref "D15") (pin "J1") (pinfunction "IN2_J1") (pintype "input"))
      (node (ref "D17") (pin "A1") (pinfunction "IN1_A1") (pintype "input"))
      (node (ref "D18") (pin "C1") (pinfunction "IN3_C1") (pintype "input"))
      (node (ref "D19") (pin "R1") (pinfunction "IN2_R1") (pintype "input"))
      (node (ref "D19") (pin "U2") (pinfunction "IN2_U2") (pintype "input"))
      (node (ref "D24") (pin "H2") (pinfunction "1_H2") (pintype "output"))
    )
    (net (code "254") (name "EAE_IR1_") (class "Default")
      (node (ref "D19") (pin "P2") (pinfunction "IN2_P2") (pintype "input"))
      (node (ref "D20") (pin "S2") (pinfunction "IN2_S2") (pintype "input"))
      (node (ref "D24") (pin "J2") (pinfunction "0_J2") (pintype "output"))
    )
    (net (code "255") (name "EAE_IR2") (class "Default")
      (node (ref "D19") (pin "R2") (pinfunction "IN3_R2") (pintype "input"))
      (node (ref "D19") (pin "V2") (pinfunction "IN3_V2") (pintype "input"))
      (node (ref "D24") (pin "L1") (pinfunction "1_L1") (pintype "output"))
    )
    (net (code "256") (name "EAE_IR2_") (class "Default")
      (node (ref "D18") (pin "L2") (pinfunction "IN3_L2") (pintype "input"))
      (node (ref "D19") (pin "S1") (pinfunction "IN3_S1") (pintype "input"))
      (node (ref "D20") (pin "T2") (pinfunction "IN3_T2") (pintype "input"))
      (node (ref "D24") (pin "M1") (pinfunction "0_M1") (pintype "output"))
      (node (ref "F33") (pin "S2") (pinfunction "IN4D_S2") (pintype "input"))
    )
    (net (code "257") (name "EAE_IR_CLEAR_") (class "Default")
      (node (ref "D24") (pin "A1") (pinfunction "R_A1") (pintype "input"))
      (node (ref "E22") (pin "N1") (pinfunction "OUT_N1") (pintype "output"))
      (node (ref "E22") (pin "P1") (pinfunction "IN1_P1") (pintype "input"))
    )
    (net (code "258") (name "EAE_LEFT_SHIFT_ENABLE_") (class "Default")
      (node (ref "D20") (pin "J2") (pinfunction "OUT_J2") (pintype "output"))
      (node (ref "E31") (pin "N2") (pinfunction "IN4_N2") (pintype "input"))
    )
    (net (code "259") (name "EAE_L_DISABLE") (class "Default")
      (node (ref "D17") (pin "U1") (pinfunction "OUT_U1") (pintype "output"))
      (node (ref "E28") (pin "L1") (pinfunction "IN4B_L1") (pintype "input"))
    )
    (net (code "260") (name "EAE_MEM_ENABLE_") (class "Default")
      (node (ref "D20") (pin "L1") (pinfunction "OUT_L1") (pintype "output"))
      (node (ref "F11") (pin "L2") (pinfunction "IN2_L2") (pintype "input"))
      (node (ref "F31") (pin "D1") (pinfunction "IN4_D1") (pintype "input"))
      (node (ref "F31") (pin "D2") (pinfunction "IN1_D2") (pintype "input"))
    )
    (net (code "261") (name "EAE_MQ0BAR_ENABLE_") (class "Default")
      (node (ref "D18") (pin "U1") (pinfunction "OUT_U1") (pintype "output"))
      (node (ref "E25") (pin "B1") (pinfunction "IN2_B1") (pintype "input"))
    )
    (net (code "262") (name "EAE_MQ0_ENABLE_") (class "Default")
      (node (ref "D18") (pin "S2") (pinfunction "OUT_S2") (pintype "output"))
      (node (ref "E25") (pin "C1") (pinfunction "IN3_C1") (pintype "input"))
    )
    (net (code "263") (name "EAE_NO_SHIFT_ENABLE") (class "Default")
      (node (ref "D17") (pin "M2") (pinfunction "OUT_M2") (pintype "output"))
      (node (ref "F24") (pin "C1") (pinfunction "IN3_C1") (pintype "input"))
    )
    (net (code "264") (name "EAE_ON") (class "Default")
      (node (ref "C18") (pin "L2") (pinfunction "IN1_L2") (pintype "input"))
      (node (ref "C21") (pin "A1") (pinfunction "IN1_A1") (pintype "input"))
      (node (ref "C21") (pin "D2") (pinfunction "IN1_D2") (pintype "input"))
      (node (ref "C21") (pin "E1") (pinfunction "IN1_E1") (pintype "input"))
      (node (ref "C21") (pin "J2") (pinfunction "IN1_J2") (pintype "input"))
      (node (ref "C21") (pin "K1") (pinfunction "IN1_K1") (pintype "input"))
      (node (ref "C21") (pin "N2") (pinfunction "IN1_N2") (pintype "input"))
      (node (ref "C21") (pin "R1") (pinfunction "IN2_R1") (pintype "input"))
      (node (ref "C21") (pin "T2") (pinfunction "IN1_T2") (pintype "input"))
      (node (ref "D24") (pin "P1") (pinfunction "D_P1") (pintype "input"))
      (node (ref "D24") (pin "P2") (pinfunction "1_P2") (pintype "output"))
    )
    (net (code "265") (name "EAE_ON_") (class "Default")
      (node (ref "D13") (pin "H1") (pinfunction "IN1_H1") (pintype "input"))
      (node (ref "D21") (pin "E2") (pinfunction "IN2_E2") (pintype "input"))
      (node (ref "D24") (pin "R2") (pinfunction "0_R2") (pintype "output"))
      (node (ref "E24") (pin "A1") (pinfunction "IN1_A1") (pintype "input"))
      (node (ref "F28") (pin "R1") (pinfunction "IN2_R1") (pintype "input"))
    )
    (net (code "266") (name "EAE_RIGHT_SHIFT_ENABLE_") (class "Default")
      (node (ref "D12") (pin "H1") (pinfunction "IN1_H1") (pintype "input"))
      (node (ref "D17") (pin "D1") (pinfunction "OUT_D1") (pintype "output"))
      (node (ref "D20") (pin "D2") (pinfunction "IN1_D2") (pintype "input"))
      (node (ref "E31") (pin "K1") (pinfunction "IN4_K1") (pintype "input"))
    )
    (net (code "267") (name "EAE_RUN") (class "Default")
      (node (ref "C22") (pin "U2") (pinfunction "S_U2") (pintype "input"))
      (node (ref "D12") (pin "M2") (pinfunction "IN2_M2") (pintype "input"))
      (node (ref "D14") (pin "A1") (pinfunction "IN1_A1") (pintype "input"))
      (node (ref "D15") (pin "M1") (pinfunction "IN2_M1") (pintype "input"))
      (node (ref "D24") (pin "S1") (pinfunction "1_S1") (pintype "output"))
    )
    (net (code "268") (name "EAE_SET_") (class "Default")
      (node (ref "D14") (pin "K1") (pinfunction "OUT_K1") (pintype "output"))
      (node (ref "E14") (pin "L1") (pinfunction "IN2_L1") (pintype "input"))
    )
    (net (code "269") (name "EAE_START_") (class "Default")
      (node (ref "D14") (pin "E1") (pinfunction "IN2_E1") (pintype "input"))
      (node (ref "D17") (pin "V1") (pinfunction "OUT_V1") (pintype "output"))
      (node (ref "D24") (pin "R1") (pinfunction "S_R1") (pintype "input"))
      (node (ref "E12") (pin "E1") (pinfunction "IN2_E1") (pintype "input"))
    )
    (net (code "270") (name "EAE_TG") (class "Default")
      (node (ref "D22") (pin "P1") (pinfunction "IN3_P1") (pintype "input"))
      (node (ref "D22") (pin "R2") (pinfunction "IN1_R2") (pintype "input"))
      (node (ref "D24") (pin "V2") (pinfunction "1_V2") (pintype "output"))
    )
    (net (code "271") (name "EAE_TP") (class "Default")
      (node (ref "C13") (pin "J1") (pinfunction "OUT_J1") (pintype "output"))
      (node (ref "C22") (pin "S2") (pinfunction "C_S2") (pintype "input"))
      (node (ref "D14") (pin "B1") (pinfunction "IN2_B1") (pintype "input"))
    )
    (net (code "272") (name "EAE_TP_") (class "Default")
      (node (ref "D12") (pin "P1") (pinfunction "IN1_P1") (pintype "input"))
      (node (ref "D14") (pin "C1") (pinfunction "OUT_C1") (pintype "output"))
      (node (ref "D14") (pin "D1") (pinfunction "IN1_D1") (pintype "input"))
      (node (ref "D22") (pin "D2") (pinfunction "IN1_D2") (pintype "input"))
      (node (ref "E32") (pin "K2") (pinfunction "IN1_K2") (pintype "input"))
    )
    (net (code "273") (name "EXECUTE_") (class "Default")
      (node (ref "D40") (pin "R1") (pinfunction "P$2_R1") (pintype "bidirectional"))
      (node (ref "E23") (pin "M1") (pinfunction "0_M1") (pintype "output"))
      (node (ref "F31") (pin "R2") (pinfunction "IN1_R2") (pintype "input"))
    )
    (net (code "274") (name "EXT_DATA_ADD0") (class "Default")
      (node (ref "B18") (pin "M2") (pinfunction "D_M2") (pintype "input"))
      (node (ref "J20") (pin "P2") (pinfunction "OUT_P2") (pintype "output"))
    )
    (net (code "275") (name "EXT_DATA_ADD1") (class "Default")
      (node (ref "B18") (pin "P1") (pinfunction "D_P1") (pintype "input"))
      (node (ref "J20") (pin "S1") (pinfunction "OUT_S1") (pintype "output"))
    )
    (net (code "276") (name "EXT_DATA_ADD2") (class "Default")
      (node (ref "B18") (pin "T2") (pinfunction "D_T2") (pintype "input"))
      (node (ref "J20") (pin "V2") (pinfunction "OUT_V2") (pintype "output"))
    )
    (net (code "277") (name "EXT_GO") (class "Default")
      (node (ref "A12") (pin "A1") (pinfunction "IN1_A1") (pintype "input"))
      (node (ref "A13") (pin "F1") (pinfunction "OUT_F1") (pintype "output"))
      (node (ref "A15") (pin "H2") (pinfunction "IN1_H2") (pintype "input"))
      (node (ref "A17") (pin "U2") (pinfunction "IN2_U2") (pintype "input"))
      (node (ref "B06") (pin "D2") (pinfunction "IN1_D2") (pintype "input"))
    )
    (net (code "278") (name "EXT_INST") (class "Default")
      (node (ref "A14") (pin "K2") (pinfunction "OUT_K2") (pintype "output"))
      (node (ref "A15") (pin "U2") (pinfunction "IN2_U2") (pintype "input"))
    )
    (net (code "279") (name "E_SET") (class "Default")
      (node (ref "E23") (pin "J1") (pinfunction "D_J1") (pintype "input"))
      (node (ref "F22") (pin "H1") (pinfunction "IN1_H1") (pintype "input"))
      (node (ref "F23") (pin "J2") (pinfunction "OUT_J2") (pintype "output"))
    )
    (net (code "280") (name "E_SET_") (class "Default")
      (node (ref "A16") (pin "U2") (pinfunction "IN2_U2") (pintype "input"))
      (node (ref "F22") (pin "K1") (pinfunction "OUT_K1") (pintype "output"))
      (node (ref "F23") (pin "K2") (pinfunction "IN1_K2") (pintype "input"))
      (node (ref "F23") (pin "P1") (pinfunction "IN3_P1") (pintype "input"))
      (node (ref "F29") (pin "E1") (pinfunction "IN2_E1") (pintype "input"))
    )
    (net (code "281") (name "F15F1") (class "Default")
      (node (ref "F15") (pin "F1") (pinfunction "OUT_F1") (pintype "output"))
      (node (ref "F16") (pin "H2") (pinfunction "H2_H2") (pintype "input"))
    )
    (net (code "282") (name "F17F1") (class "Default")
      (node (ref "F17") (pin "F1") (pinfunction "OUT_F1") (pintype "output"))
      (node (ref "F18") (pin "H2") (pinfunction "H2_H2") (pintype "input"))
    )
    (net (code "283") (name "FETCH_") (class "Default")
      (node (ref "D40") (pin "N1") (pinfunction "P$2_N1") (pintype "bidirectional"))
      (node (ref "E23") (pin "F1") (pinfunction "0_F1") (pintype "output"))
      (node (ref "F28") (pin "T2") (pinfunction "IN1_T2") (pintype "input"))
      (node (ref "F31") (pin "M1") (pinfunction "IN1_M1") (pintype "input"))
    )
    (net (code "284") (name "F_SET") (class "Default")
      (node (ref "E13") (pin "F1") (pinfunction "IN2B_F1") (pintype "input"))
      (node (ref "E23") (pin "C1") (pinfunction "D_C1") (pintype "input"))
      (node (ref "F11") (pin "U2") (pinfunction "IN4_U2") (pintype "input"))
      (node (ref "F22") (pin "F1") (pinfunction "OUT_F1") (pintype "output"))
    )
    (net (code "285") (name "F_SET_") (class "Default")
      (node (ref "A16") (pin "T2") (pinfunction "IN1_T2") (pintype "input"))
      (node (ref "F22") (pin "D1") (pinfunction "IN1_D1") (pintype "input"))
      (node (ref "F23") (pin "S1") (pinfunction "OUT_S1") (pintype "output"))
      (node (ref "F28") (pin "J2") (pinfunction "IN1_J2") (pintype "input"))
    )
    (net (code "286") (name "GND") (class "Default")
      (node (ref "A10") (pin "J1") (pinfunction "8A_J1") (pintype "input"))
      (node (ref "A40") (pin "C2") (pinfunction "P$2_C2") (pintype "bidirectional"))
      (node (ref "B05") (pin "T2") (pinfunction "D_T2") (pintype "input"))
      (node (ref "B11") (pin "P1") (pinfunction "D_P1") (pintype "input"))
      (node (ref "B40") (pin "C2") (pinfunction "P$2_C2") (pintype "bidirectional"))
      (node (ref "C40") (pin "C2") (pinfunction "P$2_C2") (pintype "bidirectional"))
      (node (ref "D23") (pin "H1") (pinfunction "IN3A_H1") (pintype "input"))
      (node (ref "D23") (pin "J1") (pinfunction "IN3B_J1") (pintype "input"))
      (node (ref "E18") (pin "D2") (pinfunction "C_D2") (pintype "input"))
      (node (ref "E18") (pin "E2") (pinfunction "D_E2") (pintype "input"))
      (node (ref "E18") (pin "J1") (pinfunction "D_J1") (pintype "input"))
      (node (ref "E19") (pin "C1") (pinfunction "D_C1") (pintype "input"))
      (node (ref "E19") (pin "E2") (pinfunction "D_E2") (pintype "input"))
      (node (ref "E19") (pin "J1") (pinfunction "D_J1") (pintype "input"))
      (node (ref "E19") (pin "M2") (pinfunction "D_M2") (pintype "input"))
      (node (ref "E19") (pin "P1") (pinfunction "D_P1") (pintype "input"))
      (node (ref "E19") (pin "T2") (pinfunction "D_T2") (pintype "input"))
      (node (ref "E20") (pin "P1") (pinfunction "D_P1") (pintype "input"))
      (node (ref "E29") (pin "J1") (pinfunction "IN3B_J1") (pintype "input"))
      (node (ref "E30") (pin "A1") (pinfunction "IN1A_A1") (pintype "input"))
      (node (ref "E40") (pin "C2") (pinfunction "P$2_C2") (pintype "bidirectional"))
      (node (ref "EF34") (pin "BD1") (pinfunction "BD1_BD1") (pintype "input"))
      (node (ref "EF34") (pin "BE2") (pinfunction "BE2_BE2") (pintype "input"))
      (node (ref "EF34") (pin "BN1") (pinfunction "BN1_BN1") (pintype "input"))
      (node (ref "EF35") (pin "BD1") (pinfunction "BD1_BD1") (pintype "input"))
      (node (ref "EF35") (pin "BE2") (pinfunction "BE2_BE2") (pintype "input"))
      (node (ref "EF35") (pin "BN1") (pinfunction "BN1_BN1") (pintype "input"))
      (node (ref "EF36") (pin "BD1") (pinfunction "BD1_BD1") (pintype "input"))
      (node (ref "EF36") (pin "BE2") (pinfunction "BE2_BE2") (pintype "input"))
      (node (ref "EF36") (pin "BN1") (pinfunction "BN1_BN1") (pintype "input"))
      (node (ref "EF37") (pin "BD1") (pinfunction "BD1_BD1") (pintype "input"))
      (node (ref "EF37") (pin "BE2") (pinfunction "BE2_BE2") (pintype "input"))
      (node (ref "EF38") (pin "BE2") (pinfunction "BE2_BE2") (pintype "input"))
      (node (ref "F40") (pin "C2") (pinfunction "P$2_C2") (pintype "bidirectional"))
      (node (ref "H07") (pin "E2") (pinfunction "SLOW_E2") (pintype "passive"))
      (node (ref "H07") (pin "L2") (pinfunction "SLOW_L2") (pintype "passive"))
      (node (ref "H07") (pin "R2") (pinfunction "SLOW_R2") (pintype "passive"))
      (node (ref "H08") (pin "E2") (pinfunction "SLOW_E2") (pintype "passive"))
      (node (ref "H08") (pin "L2") (pinfunction "SLOW_L2") (pintype "passive"))
      (node (ref "H08") (pin "R2") (pinfunction "SLOW_R2") (pintype "passive"))
      (node (ref "H09") (pin "E2") (pinfunction "SLOW_E2") (pintype "passive"))
      (node (ref "H09") (pin "L2") (pinfunction "SLOW_L2") (pintype "passive"))
      (node (ref "H09") (pin "R2") (pinfunction "SLOW_R2") (pintype "passive"))
      (node (ref "H10") (pin "E2") (pinfunction "SLOW_E2") (pintype "passive"))
      (node (ref "H10") (pin "L2") (pinfunction "SLOW_L2") (pintype "passive"))
      (node (ref "H10") (pin "R2") (pinfunction "SLOW_R2") (pintype "passive"))
      (node (ref "H11") (pin "E2") (pinfunction "SLOW_E2") (pintype "passive"))
      (node (ref "H11") (pin "L2") (pinfunction "SLOW_L2") (pintype "passive"))
      (node (ref "H11") (pin "R2") (pinfunction "SLOW_R2") (pintype "passive"))
      (node (ref "H12") (pin "E2") (pinfunction "SLOW_E2") (pintype "passive"))
      (node (ref "H12") (pin "L2") (pinfunction "SLOW_L2") (pintype "passive"))
      (node (ref "H12") (pin "R2") (pinfunction "SLOW_R2") (pintype "passive"))
      (node (ref "H13") (pin "E2") (pinfunction "SLOW_E2") (pintype "passive"))
      (node (ref "H13") (pin "L2") (pinfunction "SLOW_L2") (pintype "passive"))
      (node (ref "H13") (pin "R2") (pinfunction "SLOW_R2") (pintype "passive"))
      (node (ref "H14") (pin "E2") (pinfunction "SLOW_E2") (pintype "passive"))
      (node (ref "H14") (pin "L2") (pinfunction "SLOW_L2") (pintype "passive"))
      (node (ref "H14") (pin "R2") (pinfunction "SLOW_R2") (pintype "passive"))
      (node (ref "H15") (pin "E2") (pinfunction "SLOW_E2") (pintype "passive"))
      (node (ref "H15") (pin "L2") (pinfunction "SLOW_L2") (pintype "passive"))
      (node (ref "H15") (pin "R2") (pinfunction "SLOW_R2") (pintype "passive"))
      (node (ref "H16") (pin "E2") (pinfunction "SLOW_E2") (pintype "passive"))
      (node (ref "H16") (pin "L2") (pinfunction "SLOW_L2") (pintype "passive"))
      (node (ref "H16") (pin "R2") (pinfunction "SLOW_R2") (pintype "passive"))
      (node (ref "H17") (pin "E2") (pinfunction "SLOW_E2") (pintype "passive"))
      (node (ref "H17") (pin "L2") (pinfunction "SLOW_L2") (pintype "passive"))
      (node (ref "H17") (pin "R2") (pinfunction "SLOW_R2") (pintype "passive"))
      (node (ref "H18") (pin "E2") (pinfunction "SLOW_E2") (pintype "passive"))
      (node (ref "H18") (pin "L2") (pinfunction "SLOW_L2") (pintype "passive"))
      (node (ref "H18") (pin "R2") (pinfunction "SLOW_R2") (pintype "passive"))
      (node (ref "H19") (pin "E2") (pinfunction "SLOW_E2") (pintype "passive"))
      (node (ref "H19") (pin "L2") (pinfunction "SLOW_L2") (pintype "passive"))
      (node (ref "H19") (pin "R2") (pinfunction "SLOW_R2") (pintype "passive"))
      (node (ref "H20") (pin "E2") (pinfunction "SLOW_E2") (pintype "passive"))
      (node (ref "H20") (pin "L2") (pinfunction "SLOW_L2") (pintype "passive"))
    )
    (net (code "287") (name "HS") (class "Default")
      (node (ref "D07") (pin "B1") (pinfunction "IN2_B1") (pintype "input"))
      (node (ref "D11") (pin "P2") (pinfunction "1_P2") (pintype "output"))
    )
    (net (code "288") (name "HS_") (class "Default")
      (node (ref "C09") (pin "B1") (pinfunction "IN2_B1") (pintype "input"))
      (node (ref "C11") (pin "F1") (pinfunction "IN2_F1") (pintype "input"))
      (node (ref "D07") (pin "E1") (pinfunction "IN2_E1") (pintype "input"))
      (node (ref "D11") (pin "R2") (pinfunction "0_R2") (pintype "output"))
    )
    (net (code "289") (name "IB0") (class "Default")
      (node (ref "A17") (pin "J1") (pinfunction "IN2_J1") (pintype "input"))
      (node (ref "B17") (pin "P2") (pinfunction "1_P2") (pintype "output"))
    )
    (net (code "290") (name "IB1") (class "Default")
      (node (ref "A17") (pin "M1") (pinfunction "IN2_M1") (pintype "input"))
      (node (ref "B17") (pin "S1") (pinfunction "1_S1") (pintype "output"))
    )
    (net (code "291") (name "IB2") (class "Default")
      (node (ref "A17") (pin "R1") (pinfunction "IN2_R1") (pintype "input"))
      (node (ref "B17") (pin "V2") (pinfunction "1_V2") (pintype "output"))
    )
    (net (code "292") (name "IB_TO_IF") (class "Default")
      (node (ref "A15") (pin "A1") (pinfunction "IN1_A1") (pintype "input"))
      (node (ref "A17") (pin "C1") (pinfunction "OUT_C1") (pintype "output"))
      (node (ref "B05") (pin "D2") (pinfunction "C_D2") (pintype "input"))
      (node (ref "B17") (pin "B1") (pinfunction "C_B1") (pintype "input"))
      (node (ref "B17") (pin "D2") (pinfunction "C_D2") (pintype "input"))
      (node (ref "B17") (pin "H1") (pinfunction "C_H1") (pintype "input"))
    )
    (net (code "293") (name "IF0") (class "Default")
      (node (ref "A11") (pin "J1") (pinfunction "IN2_J1") (pintype "input"))
      (node (ref "A16") (pin "B1") (pinfunction "IN2_B1") (pintype "input"))
      (node (ref "B17") (pin "E1") (pinfunction "1_E1") (pintype "output"))
      (node (ref "B19") (pin "C1") (pinfunction "D_C1") (pintype "input"))
    )
    (net (code "294") (name "IF0_") (class "Default")
      (node (ref "B17") (pin "F1") (pinfunction "0_F1") (pintype "output"))
      (node (ref "C40") (pin "N1") (pinfunction "P$2_N1") (pintype "bidirectional"))
    )
    (net (code "295") (name "IF1") (class "Default")
      (node (ref "A11") (pin "M2") (pinfunction "IN2_M2") (pintype "input"))
      (node (ref "A16") (pin "J1") (pinfunction "IN2_J1") (pintype "input"))
      (node (ref "B17") (pin "H2") (pinfunction "1_H2") (pintype "output"))
      (node (ref "B19") (pin "E2") (pinfunction "D_E2") (pintype "input"))
    )
    (net (code "296") (name "IF1_") (class "Default")
      (node (ref "B17") (pin "J2") (pinfunction "0_J2") (pintype "output"))
      (node (ref "C40") (pin "C1") (pinfunction "P$2_C1") (pintype "bidirectional"))
    )
    (net (code "297") (name "IF2") (class "Default")
      (node (ref "A11") (pin "U2") (pinfunction "IN2_U2") (pintype "input"))
      (node (ref "A16") (pin "M2") (pinfunction "IN2_M2") (pintype "input"))
      (node (ref "B17") (pin "L1") (pinfunction "1_L1") (pintype "output"))
      (node (ref "B19") (pin "J1") (pinfunction "D_J1") (pintype "input"))
    )
    (net (code "298") (name "IF2_") (class "Default")
      (node (ref "B17") (pin "M1") (pinfunction "0_M1") (pintype "output"))
      (node (ref "C40") (pin "D1") (pinfunction "P$2_D1") (pintype "bidirectional"))
    )
    (net (code "299") (name "IFSR0") (class "Default")
      (node (ref "A18") (pin "E1") (pinfunction "IN2_E1") (pintype "input"))
      (node (ref "A40") (pin "H2") (pinfunction "P$2_H2") (pintype "bidirectional"))
    )
    (net (code "300") (name "IFSR1") (class "Default")
      (node (ref "A18") (pin "J2") (pinfunction "IN2_J2") (pintype "input"))
      (node (ref "A40") (pin "J2") (pinfunction "P$2_J2") (pintype "bidirectional"))
    )
    (net (code "301") (name "IFSR2") (class "Default")
      (node (ref "A18") (pin "R1") (pinfunction "IN2_R1") (pintype "input"))
      (node (ref "A40") (pin "K2") (pinfunction "P$2_K2") (pintype "bidirectional"))
    )
    (net (code "302") (name "IF_ENABLE") (class "Default")
      (node (ref "A16") (pin "A1") (pinfunction "IN1_A1") (pintype "input"))
      (node (ref "A16") (pin "H1") (pinfunction "IN1_H1") (pintype "input"))
      (node (ref "A16") (pin "L2") (pinfunction "IN1_L2") (pintype "input"))
      (node (ref "B11") (pin "F1") (pinfunction "0_F1") (pintype "output"))
    )
    (net (code "303") (name "IF_ENABLE_") (class "Default")
      (node (ref "B11") (pin "C1") (pinfunction "D_C1") (pintype "input"))
      (node (ref "B20") (pin "H2") (pinfunction "OUT_H2") (pintype "output"))
    )
    (net (code "304") (name "IF_TO_SF") (class "Default")
      (node (ref "A19") (pin "S1") (pinfunction "OUT_S1") (pintype "output"))
      (node (ref "B05") (pin "N1") (pinfunction "C_N1") (pintype "input"))
      (node (ref "B19") (pin "B1") (pinfunction "C_B1") (pintype "input"))
      (node (ref "B19") (pin "D2") (pinfunction "C_D2") (pintype "input"))
      (node (ref "B21") (pin "M2") (pinfunction "IN2_M2") (pintype "input"))
      (node (ref "B21") (pin "R1") (pinfunction "IN2_R1") (pintype "input"))
      (node (ref "B21") (pin "R2") (pinfunction "IN2_R2") (pintype "input"))
    )
    (net (code "305") (name "INITIALIZE") (class "Default")
      (node (ref "C12") (pin "H1") (pinfunction "IN2_H1") (pintype "input"))
      (node (ref "F20") (pin "S2") (pinfunction "OUT_S2") (pintype "output"))
    )
    (net (code "306") (name "INITIALIZE_") (class "Default")
      (node (ref "A04") (pin "S2") (pinfunction "S2_S2") (pintype "input"))
      (node (ref "B05") (pin "K2") (pinfunction "R_K2") (pintype "input"))
      (node (ref "B07") (pin "L1") (pinfunction "IN2_L1") (pintype "input"))
      (node (ref "C12") (pin "L1") (pinfunction "OUT_L1") (pintype "open_collector"))
      (node (ref "E19") (pin "K2") (pinfunction "R_K2") (pintype "input"))
      (node (ref "H12") (pin "U2") (pinfunction "IN2_U2") (pintype "input"))
    )
    (net (code "307") (name "INPUT_BUS00") (class "Default")
      (node (ref "EF34") (pin "BK1") (pinfunction "BK1_BK1") (pintype "input"))
      (node (ref "J13") (pin "E1") (pinfunction "OUT_E1") (pintype "output"))
    )
    (net (code "308") (name "INPUT_BUS01") (class "Default")
      (node (ref "EF34") (pin "BM1") (pinfunction "BM1_BM1") (pintype "input"))
      (node (ref "J13") (pin "J2") (pinfunction "OUT_J2") (pintype "output"))
    )
    (net (code "309") (name "INPUT_BUS02") (class "Default")
      (node (ref "EF35") (pin "BK1") (pinfunction "BK1_BK1") (pintype "input"))
      (node (ref "J13") (pin "L1") (pinfunction "OUT_L1") (pintype "output"))
    )
    (net (code "310") (name "INPUT_BUS03") (class "Default")
      (node (ref "EF35") (pin "BM1") (pinfunction "BM1_BM1") (pintype "input"))
      (node (ref "J13") (pin "P2") (pinfunction "OUT_P2") (pintype "output"))
    )
    (net (code "311") (name "INPUT_BUS04") (class "Default")
      (node (ref "EF36") (pin "BK1") (pinfunction "BK1_BK1") (pintype "input"))
      (node (ref "J13") (pin "S1") (pinfunction "OUT_S1") (pintype "output"))
    )
    (net (code "312") (name "INPUT_BUS05") (class "Default")
      (node (ref "EF36") (pin "BM1") (pinfunction "BM1_BM1") (pintype "input"))
      (node (ref "J13") (pin "V2") (pinfunction "OUT_V2") (pintype "output"))
    )
    (net (code "313") (name "INPUT_BUS06") (class "Default")
      (node (ref "EF37") (pin "BK1") (pinfunction "BK1_BK1") (pintype "input"))
      (node (ref "J14") (pin "E1") (pinfunction "OUT_E1") (pintype "output"))
    )
    (net (code "314") (name "INPUT_BUS07") (class "Default")
      (node (ref "EF37") (pin "BM1") (pinfunction "BM1_BM1") (pintype "input"))
      (node (ref "J14") (pin "J2") (pinfunction "OUT_J2") (pintype "output"))
    )
    (net (code "315") (name "INPUT_BUS08") (class "Default")
      (node (ref "EF38") (pin "BK1") (pinfunction "BK1_BK1") (pintype "input"))
      (node (ref "J14") (pin "L1") (pinfunction "OUT_L1") (pintype "output"))
    )
    (net (code "316") (name "INPUT_BUS09") (class "Default")
      (node (ref "EF38") (pin "BM1") (pinfunction "BM1_BM1") (pintype "input"))
      (node (ref "J14") (pin "P2") (pinfunction "OUT_P2") (pintype "output"))
    )
    (net (code "317") (name "INPUT_BUS10") (class "Default")
      (node (ref "EF39") (pin "BK1") (pinfunction "BK1_BK1") (pintype "input"))
      (node (ref "J14") (pin "S1") (pinfunction "OUT_S1") (pintype "output"))
    )
    (net (code "318") (name "INPUT_BUS11") (class "Default")
      (node (ref "EF39") (pin "BM1") (pinfunction "BM1_BM1") (pintype "input"))
      (node (ref "J14") (pin "V2") (pinfunction "OUT_V2") (pintype "output"))
    )
    (net (code "319") (name "INT_DELAY") (class "Default")
      (node (ref "E25") (pin "F2") (pinfunction "IN3_F2") (pintype "input"))
      (node (ref "E33") (pin "R2") (pinfunction "0_R2") (pintype "output"))
    )
    (net (code "320") (name "INT_ENABLE") (class "Default")
      (node (ref "E33") (pin "N2") (pinfunction "S_N2") (pintype "input"))
      (node (ref "E33") (pin "U1") (pinfunction "0_U1") (pintype "output"))
    )
    (net (code "321") (name "INT_ENABLE_") (class "Default")
      (node (ref "D40") (pin "D1") (pinfunction "P$2_D1") (pintype "bidirectional"))
      (node (ref "E33") (pin "M2") (pinfunction "D_M2") (pintype "input"))
      (node (ref "E33") (pin "S1") (pinfunction "1_S1") (pintype "output"))
    )
    (net (code "322") (name "INT_INHIBIT_") (class "Default")
      (node (ref "B11") (pin "S1") (pinfunction "1_S1") (pintype "output"))
      (node (ref "E25") (pin "E2") (pinfunction "IN2_E2") (pintype "input"))
    )
    (net (code "323") (name "INT_OK") (class "Default")
      (node (ref "C12") (pin "K2") (pinfunction "IN1_K2") (pintype "input"))
      (node (ref "E24") (pin "J2") (pinfunction "IN2_J2") (pintype "input"))
      (node (ref "E26") (pin "U1") (pinfunction "IN1B_U1") (pintype "input"))
      (node (ref "F21") (pin "N1") (pinfunction "OUT_N1") (pintype "output"))
    )
    (net (code "324") (name "INT_OK_") (class "Default")
      (node (ref "E25") (pin "H2") (pinfunction "OUT_H2") (pintype "output"))
      (node (ref "F21") (pin "M1") (pinfunction "IN2_M1") (pintype "input"))
      (node (ref "F23") (pin "D2") (pinfunction "IN1_D2") (pintype "input"))
      (node (ref "F27") (pin "F2") (pinfunction "IN3_F2") (pintype "input"))
    )
    (net (code "325") (name "INT_RQST") (class "Default")
      (node (ref "F11") (pin "R2") (pinfunction "IN1_R2") (pintype "input"))
      (node (ref "J15") (pin "J2") (pinfunction "OUT_J2") (pintype "output"))
    )
    (net (code "326") (name "INT_SKIP_ENABLE_") (class "Default")
      (node (ref "F09") (pin "L2") (pinfunction "IN6_L2") (pintype "input"))
      (node (ref "F11") (pin "M1") (pinfunction "IN1_M1") (pintype "input"))
      (node (ref "F28") (pin "J1") (pinfunction "OUT_J1") (pintype "output"))
    )
    (net (code "327") (name "INT_STROBE") (class "Default")
      (node (ref "E14") (pin "S2") (pinfunction "OUT_S2") (pintype "output"))
      (node (ref "E15") (pin "L2") (pinfunction "IN1_L2") (pintype "input"))
      (node (ref "E33") (pin "H1") (pinfunction "C_H1") (pintype "input"))
      (node (ref "F19") (pin "F1") (pinfunction "IN1_F1") (pintype "input"))
      (node (ref "F21") (pin "H1") (pinfunction "IN1_H1") (pintype "input"))
    )
    (net (code "328") (name "INT_STROBE_") (class "Default")
      (node (ref "C12") (pin "M2") (pinfunction "IN3_M2") (pintype "input"))
      (node (ref "E15") (pin "N2") (pinfunction "OUT_N2") (pintype "output"))
      (node (ref "E19") (pin "K1") (pinfunction "S_K1") (pintype "input"))
    )
    (net (code "329") (name "INT_SYNC") (class "Default")
      (node (ref "E25") (pin "D2") (pinfunction "IN1_D2") (pintype "input"))
      (node (ref "E33") (pin "M1") (pinfunction "0_M1") (pintype "output"))
    )
    (net (code "330") (name "IOP1") (class "Default")
      (node (ref "B07") (pin "K2") (pinfunction "IN2_K2") (pintype "input"))
      (node (ref "E19") (pin "P2") (pinfunction "1_P2") (pintype "output"))
    )
    (net (code "331") (name "IOP1_") (class "Default")
      (node (ref "E19") (pin "R2") (pinfunction "0_R2") (pintype "output"))
      (node (ref "F11") (pin "H1") (pinfunction "IN2_H1") (pintype "input"))
      (node (ref "H11") (pin "H2") (pinfunction "IN2_H2") (pintype "input"))
    )
    (net (code "332") (name "IOP1_CLR") (class "Default")
      (node (ref "E19") (pin "L2") (pinfunction "C_L2") (pintype "input"))
      (node (ref "F14") (pin "J1") (pinfunction "OUT_J1") (pintype "output"))
    )
    (net (code "333") (name "IOP1_SET_") (class "Default")
      (node (ref "E14") (pin "S1") (pinfunction "IN3_S1") (pintype "input"))
      (node (ref "E19") (pin "N2") (pinfunction "S_N2") (pintype "input"))
      (node (ref "F20") (pin "F2") (pinfunction "OUT_F2") (pintype "output"))
    )
    (net (code "334") (name "IOP2") (class "Default")
      (node (ref "A04") (pin "M2") (pinfunction "M2_M2") (pintype "input"))
      (node (ref "E19") (pin "S1") (pinfunction "1_S1") (pintype "output"))
    )
    (net (code "335") (name "IOP2_") (class "Default")
      (node (ref "E19") (pin "U1") (pinfunction "0_U1") (pintype "output"))
      (node (ref "F11") (pin "J1") (pinfunction "IN3_J1") (pintype "input"))
      (node (ref "H11") (pin "N2") (pinfunction "IN2_N2") (pintype "input"))
    )
    (net (code "336") (name "IOP2_CLR") (class "Default")
      (node (ref "E19") (pin "N1") (pinfunction "C_N1") (pintype "input"))
      (node (ref "F16") (pin "J1") (pinfunction "OUT_J1") (pintype "output"))
    )
    (net (code "337") (name "IOP2_SET_") (class "Default")
      (node (ref "E14") (pin "R1") (pinfunction "IN2_R1") (pintype "input"))
      (node (ref "E19") (pin "R1") (pinfunction "S_R1") (pintype "input"))
      (node (ref "F20") (pin "K1") (pinfunction "OUT_K1") (pintype "output"))
    )
    (net (code "338") (name "IOP4") (class "Default")
      (node (ref "B07") (pin "E1") (pinfunction "IN1_E1") (pintype "input"))
      (node (ref "E19") (pin "V2") (pinfunction "1_V2") (pintype "output"))
    )
    (net (code "339") (name "IOP4_") (class "Default")
      (node (ref "E19") (pin "V1") (pinfunction "0_V1") (pintype "output"))
      (node (ref "F11") (pin "K1") (pinfunction "IN4_K1") (pintype "input"))
      (node (ref "H11") (pin "U2") (pinfunction "IN2_U2") (pintype "input"))
    )
    (net (code "340") (name "IOP4_CLR") (class "Default")
      (node (ref "E19") (pin "S2") (pinfunction "C_S2") (pintype "input"))
      (node (ref "F18") (pin "J1") (pinfunction "OUT_J1") (pintype "output"))
    )
    (net (code "341") (name "IOP4_SET_") (class "Default")
      (node (ref "E14") (pin "P1") (pinfunction "IN1_P1") (pintype "input"))
      (node (ref "E19") (pin "U2") (pinfunction "S_U2") (pintype "input"))
      (node (ref "F20") (pin "K2") (pinfunction "OUT_K2") (pintype "output"))
    )
    (net (code "342") (name "IOP124_") (class "Default")
      (node (ref "E09") (pin "T2") (pinfunction "IN1_T2") (pintype "input"))
      (node (ref "E11") (pin "S1") (pinfunction "OUT_S1") (pintype "output"))
      (node (ref "F30") (pin "D2") (pinfunction "IN1_D2") (pintype "input"))
    )
    (net (code "343") (name "IOT") (class "Default")
      (node (ref "A06") (pin "F1") (pinfunction "OUT_F1") (pintype "output"))
      (node (ref "A14") (pin "E1") (pinfunction "IN2_E1") (pintype "input"))
      (node (ref "C12") (pin "F2") (pinfunction "IN3_F2") (pintype "input"))
      (node (ref "C12") (pin "H2") (pinfunction "IN4_H2") (pintype "input"))
      (node (ref "D09") (pin "F1") (pinfunction "IN2_F1") (pintype "input"))
      (node (ref "D10") (pin "K2") (pinfunction "IN1_K2") (pintype "input"))
      (node (ref "E26") (pin "M2") (pinfunction "IN3B_M2") (pintype "input"))
      (node (ref "F09") (pin "F2") (pinfunction "IN7_F2") (pintype "input"))
      (node (ref "F19") (pin "R2") (pinfunction "IN1_R2") (pintype "input"))
      (node (ref "F20") (pin "R1") (pinfunction "IN2_R1") (pintype "input"))
    )
    (net (code "344") (name "IOT_") (class "Default")
      (node (ref "A06") (pin "D1") (pinfunction "IN1_D1") (pintype "input"))
      (node (ref "D40") (pin "H2") (pinfunction "P$2_H2") (pintype "bidirectional"))
      (node (ref "F11") (pin "E1") (pinfunction "OUT_E1") (pintype "output"))
    )
    (net (code "345") (name "IOT_OPR_") (class "Default")
      (node (ref "E24") (pin "F2") (pinfunction "OUT_F2") (pintype "output"))
      (node (ref "E25") (pin "J2") (pinfunction "IN1_J2") (pintype "input"))
      (node (ref "F23") (pin "F1") (pinfunction "IN1_F1") (pintype "input"))
    )
    (net (code "346") (name "IO_ENABLE") (class "Default")
      (node (ref "E28") (pin "J2") (pinfunction "IN2A_J2") (pintype "input"))
      (node (ref "E30") (pin "J2") (pinfunction "IN2A_J2") (pintype "input"))
      (node (ref "EF34") (pin "BL2") (pinfunction "BL2_BL2") (pintype "input"))
      (node (ref "EF35") (pin "BL2") (pinfunction "BL2_BL2") (pintype "input"))
      (node (ref "EF36") (pin "BL2") (pinfunction "BL2_BL2") (pintype "input"))
      (node (ref "EF37") (pin "BL2") (pinfunction "BL2_BL2") (pintype "input"))
      (node (ref "EF38") (pin "BL2") (pinfunction "BL2_BL2") (pintype "input"))
      (node (ref "EF39") (pin "BL2") (pinfunction "BL2_BL2") (pintype "input"))
      (node (ref "F30") (pin "J2") (pinfunction "OUT_J2") (pintype "open_collector"))
    )
    (net (code "347") (name "IO_END") (class "Default")
      (node (ref "E12") (pin "H1") (pinfunction "IN1_H1") (pintype "input"))
      (node (ref "E20") (pin "N1") (pinfunction "C_N1") (pintype "input"))
      (node (ref "F18") (pin "F1") (pinfunction "OUT_F1") (pintype "output"))
    )
    (net (code "348") (name "IO_END_") (class "Default")
      (node (ref "E12") (pin "E2") (pinfunction "IN2_E2") (pintype "input"))
      (node (ref "E12") (pin "K1") (pinfunction "OUT_K1") (pintype "output"))
      (node (ref "E14") (pin "R2") (pinfunction "IN3_R2") (pintype "input"))
    )
    (net (code "349") (name "IO_ON") (class "Default")
      (node (ref "E09") (pin "U2") (pinfunction "IN2_U2") (pintype "input"))
      (node (ref "E20") (pin "S1") (pinfunction "1_S1") (pintype "output"))
    )
    (net (code "350") (name "IO_PC_ENABLE_") (class "Default")
      (node (ref "E09") (pin "V2") (pinfunction "OUT_V2") (pintype "output"))
      (node (ref "F09") (pin "K1") (pinfunction "IN4_K1") (pintype "input"))
      (node (ref "F11") (pin "N1") (pinfunction "IN2_N1") (pintype "input"))
    )
    (net (code "351") (name "IO_PC_LOAD") (class "Default")
      (node (ref "F32") (pin "L2") (pinfunction "IN1_L2") (pintype "input"))
      (node (ref "J11") (pin "V2") (pinfunction "P$2_V2") (pintype "bidirectional"))
    )
    (net (code "352") (name "IO_SKIP") (class "Default")
      (node (ref "E28") (pin "K2") (pinfunction "IN2B_K2") (pintype "input"))
      (node (ref "J15") (pin "E1") (pinfunction "OUT_E1") (pintype "output"))
    )
    (net (code "353") (name "IO_START_") (class "Default")
      (node (ref "E12") (pin "D1") (pinfunction "IN1_D1") (pintype "input"))
      (node (ref "E15") (pin "R2") (pinfunction "IN2_R2") (pintype "input"))
      (node (ref "E15") (pin "S1") (pinfunction "OUT_S1") (pintype "output"))
      (node (ref "E20") (pin "R1") (pinfunction "S_R1") (pintype "input"))
    )
    (net (code "354") (name "IO_STROBE") (class "Default")
      (node (ref "E26") (pin "L2") (pinfunction "IN3A_L2") (pintype "input"))
      (node (ref "F12") (pin "F1") (pinfunction "OUT_F1") (pintype "output"))
      (node (ref "F25") (pin "T2") (pinfunction "IN1_T2") (pintype "input"))
    )
    (net (code "355") (name "IPC_ENABLE") (class "Default")
      (node (ref "F09") (pin "P2") (pinfunction "OUT_P2") (pintype "output"))
      (node (ref "F20") (pin "L2") (pinfunction "IN1_L2") (pintype "input"))
    )
    (net (code "356") (name "IR0") (class "Default")
      (node (ref "E20") (pin "F1") (pinfunction "0_F1") (pintype "output"))
      (node (ref "E21") (pin "K1") (pinfunction "IN1_K1") (pintype "input"))
      (node (ref "E21") (pin "N2") (pinfunction "IN1_N2") (pintype "input"))
      (node (ref "E21") (pin "P1") (pinfunction "IN1_P1") (pintype "input"))
      (node (ref "E21") (pin "T2") (pinfunction "IN1_T2") (pintype "input"))
      (node (ref "E24") (pin "D2") (pinfunction "IN1_D2") (pintype "input"))
      (node (ref "F11") (pin "A1") (pinfunction "IN1_A1") (pintype "input"))
    )
    (net (code "357") (name "IR0_") (class "Default")
      (node (ref "E20") (pin "E1") (pinfunction "1_E1") (pintype "output"))
      (node (ref "E21") (pin "A1") (pinfunction "IN1_A1") (pintype "input"))
      (node (ref "E21") (pin "D2") (pinfunction "IN1_D2") (pintype "input"))
      (node (ref "E21") (pin "E1") (pinfunction "IN1_E1") (pintype "input"))
      (node (ref "E21") (pin "J2") (pinfunction "IN1_J2") (pintype "input"))
    )
    (net (code "358") (name "IR1") (class "Default")
      (node (ref "E20") (pin "H2") (pinfunction "1_H2") (pintype "output"))
      (node (ref "E21") (pin "F1") (pinfunction "IN2_F1") (pintype "input"))
      (node (ref "E21") (pin "K2") (pinfunction "IN2_K2") (pintype "input"))
      (node (ref "E21") (pin "P2") (pinfunction "IN2_P2") (pintype "input"))
      (node (ref "E21") (pin "U2") (pinfunction "IN2_U2") (pintype "input"))
      (node (ref "E24") (pin "E2") (pinfunction "IN2_E2") (pintype "input"))
      (node (ref "F11") (pin "B1") (pinfunction "IN2_B1") (pintype "input"))
    )
    (net (code "359") (name "IR1_") (class "Default")
      (node (ref "E20") (pin "J2") (pinfunction "0_J2") (pintype "output"))
      (node (ref "E21") (pin "B1") (pinfunction "IN2_B1") (pintype "input"))
      (node (ref "E21") (pin "E2") (pinfunction "IN2_E2") (pintype "input"))
      (node (ref "E21") (pin "L1") (pinfunction "IN2_L1") (pintype "input"))
      (node (ref "E21") (pin "R1") (pinfunction "IN2_R1") (pintype "input"))
    )
    (net (code "360") (name "IR2") (class "Default")
      (node (ref "E20") (pin "L1") (pinfunction "1_L1") (pintype "output"))
      (node (ref "E21") (pin "C1") (pinfunction "IN3_C1") (pintype "input"))
      (node (ref "E21") (pin "L2") (pinfunction "IN3_L2") (pintype "input"))
      (node (ref "E21") (pin "S1") (pinfunction "IN3_S1") (pintype "input"))
      (node (ref "E21") (pin "V2") (pinfunction "IN3_V2") (pintype "input"))
    )
    (net (code "361") (name "IR2_") (class "Default")
      (node (ref "E20") (pin "M1") (pinfunction "0_M1") (pintype "output"))
      (node (ref "E21") (pin "F2") (pinfunction "IN3_F2") (pintype "input"))
      (node (ref "E21") (pin "H1") (pinfunction "IN3_H1") (pintype "input"))
      (node (ref "E21") (pin "M1") (pinfunction "IN3_M1") (pintype "input"))
      (node (ref "E21") (pin "R2") (pinfunction "IN3_R2") (pintype "input"))
      (node (ref "F11") (pin "C1") (pinfunction "IN3_C1") (pintype "input"))
    )
    (net (code "362") (name "ISZ") (class "Default")
      (node (ref "E22") (pin "F2") (pinfunction "OUT_F2") (pintype "output"))
      (node (ref "E27") (pin "D1") (pinfunction "IN1D_D1") (pintype "input"))
      (node (ref "E28") (pin "H2") (pinfunction "IN1D_H2") (pintype "input"))
    )
    (net (code "363") (name "ISZ_") (class "Default")
      (node (ref "D40") (pin "P1") (pinfunction "P$2_P1") (pintype "bidirectional"))
      (node (ref "E21") (pin "J1") (pinfunction "OUT_J1") (pintype "output"))
      (node (ref "E22") (pin "D2") (pinfunction "IN1_D2") (pintype "input"))
    )
    (net (code "364") (name "I_IOT_") (class "Default")
      (node (ref "A05") (pin "J1") (pinfunction "IN2_J1") (pintype "input"))
      (node (ref "E21") (pin "S2") (pinfunction "OUT_S2") (pintype "output"))
      (node (ref "E22") (pin "T2") (pinfunction "IN1_T2") (pintype "input"))
    )
    (net (code "365") (name "JMP") (class "Default")
      (node (ref "E22") (pin "N2") (pinfunction "OUT_N2") (pintype "output"))
      (node (ref "E26") (pin "B1") (pinfunction "IN1B_B1") (pintype "input"))
      (node (ref "E26") (pin "P1") (pinfunction "IN5C_P1") (pintype "input"))
      (node (ref "E29") (pin "D1") (pinfunction "IN1D_D1") (pintype "input"))
      (node (ref "F27") (pin "B1") (pinfunction "IN2_B1") (pintype "input"))
    )
    (net (code "366") (name "JMP_") (class "Default")
      (node (ref "A17") (pin "D1") (pinfunction "IN1_D1") (pintype "input"))
      (node (ref "B20") (pin "A1") (pinfunction "IN1_A1") (pintype "input"))
      (node (ref "D40") (pin "L2") (pinfunction "P$2_L2") (pintype "bidirectional"))
      (node (ref "E21") (pin "U1") (pinfunction "OUT_U1") (pintype "output"))
      (node (ref "E22") (pin "L2") (pinfunction "IN1_L2") (pintype "input"))
      (node (ref "E24") (pin "E1") (pinfunction "IN2_E1") (pintype "input"))
      (node (ref "E29") (pin "P1") (pinfunction "IN5C_P1") (pintype "input"))
      (node (ref "F23") (pin "J1") (pinfunction "IN3_J1") (pintype "input"))
    )
    (net (code "367") (name "JMS") (class "Default")
      (node (ref "E22") (pin "K1") (pinfunction "OUT_K1") (pintype "output"))
      (node (ref "E27") (pin "P1") (pinfunction "IN5C_P1") (pintype "input"))
      (node (ref "E29") (pin "F2") (pinfunction "IN1C_F2") (pintype "input"))
      (node (ref "E30") (pin "P1") (pinfunction "IN5C_P1") (pintype "input"))
      (node (ref "F26") (pin "R2") (pinfunction "IN3_R2") (pintype "input"))
      (node (ref "F28") (pin "H1") (pinfunction "IN3_H1") (pintype "input"))
    )
    (net (code "368") (name "JMS_") (class "Default")
      (node (ref "A17") (pin "E1") (pinfunction "IN2_E1") (pintype "input"))
      (node (ref "B20") (pin "B1") (pinfunction "IN2_B1") (pintype "input"))
      (node (ref "D40") (pin "S1") (pinfunction "P$2_S1") (pintype "bidirectional"))
      (node (ref "E21") (pin "N1") (pinfunction "OUT_N1") (pintype "output"))
      (node (ref "E22") (pin "H1") (pinfunction "IN1_H1") (pintype "input"))
    )
    (net (code "369") (name "KEY_CONT") (class "Default")
      (node (ref "E11") (pin "S2") (pinfunction "OUT_S2") (pintype "output"))
      (node (ref "E15") (pin "J1") (pinfunction "IN2_J1") (pintype "input"))
    )
    (net (code "370") (name "KEY_CONT_") (class "Default")
      (node (ref "B40") (pin "S2") (pinfunction "P$2_S2") (pintype "bidirectional"))
      (node (ref "E11") (pin "R2") (pinfunction "IN2_R2") (pintype "input"))
      (node (ref "F19") (pin "H2") (pinfunction "IN4_H2") (pintype "input"))
    )
    (net (code "371") (name "KEY_DP") (class "Default")
      (node (ref "E11") (pin "F2") (pinfunction "OUT_F2") (pintype "output"))
      (node (ref "E29") (pin "S2") (pinfunction "IN4D_S2") (pintype "input"))
      (node (ref "F29") (pin "P1") (pinfunction "IN1_P1") (pintype "input"))
    )
    (net (code "372") (name "KEY_DP_") (class "Default")
      (node (ref "B40") (pin "M2") (pinfunction "P$2_M2") (pintype "bidirectional"))
      (node (ref "E11") (pin "D2") (pinfunction "IN1_D2") (pintype "input"))
      (node (ref "E11") (pin "H1") (pinfunction "IN1_H1") (pintype "input"))
    )
    (net (code "373") (name "KEY_EXDP") (class "Default")
      (node (ref "E11") (pin "K1") (pinfunction "OUT_K1") (pintype "output"))
      (node (ref "E11") (pin "L2") (pinfunction "IN1_L2") (pintype "input"))
      (node (ref "E13") (pin "H1") (pinfunction "IN3A_H1") (pintype "input"))
      (node (ref "E27") (pin "K2") (pinfunction "IN2B_K2") (pintype "input"))
      (node (ref "E30") (pin "L1") (pinfunction "IN4B_L1") (pintype "input"))
    )
    (net (code "374") (name "KEY_EXDP_") (class "Default")
      (node (ref "E11") (pin "N2") (pinfunction "OUT_N2") (pintype "output"))
      (node (ref "E12") (pin "H2") (pinfunction "IN1_H2") (pintype "input"))
      (node (ref "E14") (pin "L2") (pinfunction "IN3_L2") (pintype "input"))
      (node (ref "F19") (pin "F2") (pinfunction "IN3_F2") (pintype "input"))
    )
    (net (code "375") (name "KEY_EX_") (class "Default")
      (node (ref "B40") (pin "R2") (pinfunction "P$2_R2") (pintype "bidirectional"))
      (node (ref "E11") (pin "J1") (pinfunction "IN2_J1") (pintype "input"))
    )
    (net (code "376") (name "KEY_LA") (class "Default")
      (node (ref "E11") (pin "C1") (pinfunction "OUT_C1") (pintype "output"))
      (node (ref "F29") (pin "P2") (pinfunction "IN1_P2") (pintype "input"))
    )
    (net (code "377") (name "KEY_LAEXDP") (class "Default")
      (node (ref "E12") (pin "K2") (pinfunction "OUT_K2") (pintype "output"))
      (node (ref "E26") (pin "L1") (pinfunction "IN4B_L1") (pintype "input"))
      (node (ref "F21") (pin "D1") (pinfunction "IN1_D1") (pintype "input"))
    )
    (net (code "378") (name "KEY_LAEXDP_") (class "Default")
      (node (ref "F11") (pin "T2") (pinfunction "IN3_T2") (pintype "input"))
      (node (ref "F21") (pin "F1") (pinfunction "OUT_F1") (pintype "output"))
    )
    (net (code "379") (name "KEY_LAMFTS0_") (class "Default")
      (node (ref "A17") (pin "H1") (pinfunction "IN1_H1") (pintype "input"))
      (node (ref "A17") (pin "L1") (pinfunction "IN1_L1") (pintype "input"))
      (node (ref "A17") (pin "P1") (pinfunction "IN1_P1") (pintype "input"))
      (node (ref "A19") (pin "U2") (pinfunction "IN2_U2") (pintype "input"))
      (node (ref "B06") (pin "R2") (pinfunction "IN2_R2") (pintype "input"))
      (node (ref "F29") (pin "S2") (pinfunction "OUT_S2") (pintype "output"))
      (node (ref "F30") (pin "P1") (pinfunction "IN3_P1") (pintype "input"))
    )
    (net (code "380") (name "KEY_LA_") (class "Default")
      (node (ref "B40") (pin "L2") (pinfunction "P$2_L2") (pintype "bidirectional"))
      (node (ref "E11") (pin "A1") (pinfunction "IN1_A1") (pintype "input"))
      (node (ref "E12") (pin "J2") (pinfunction "IN2_J2") (pintype "input"))
      (node (ref "E15") (pin "B1") (pinfunction "IN2_B1") (pintype "input"))
      (node (ref "F19") (pin "D2") (pinfunction "IN1_D2") (pintype "input"))
    )
    (net (code "381") (name "KEY_SISTOP") (class "Default")
      (node (ref "E11") (pin "N1") (pinfunction "OUT_N1") (pintype "output"))
      (node (ref "E13") (pin "E1") (pinfunction "IN2A_E1") (pintype "input"))
    )
    (net (code "382") (name "KEY_SI_") (class "Default")
      (node (ref "B40") (pin "V2") (pinfunction "P$2_V2") (pintype "bidirectional"))
      (node (ref "E11") (pin "M1") (pinfunction "IN2_M1") (pintype "input"))
    )
    (net (code "383") (name "KEY_SS") (class "Default")
      (node (ref "E11") (pin "K2") (pinfunction "OUT_K2") (pintype "output"))
      (node (ref "E13") (pin "M1") (pinfunction "IN5A_M1") (pintype "input"))
    )
    (net (code "384") (name "KEY_SS_") (class "Default")
      (node (ref "B40") (pin "U2") (pinfunction "P$2_U2") (pintype "bidirectional"))
      (node (ref "E11") (pin "J2") (pinfunction "IN2_J2") (pintype "input"))
    )
    (net (code "385") (name "KEY_ST") (class "Default")
      (node (ref "E11") (pin "F1") (pinfunction "OUT_F1") (pintype "output"))
      (node (ref "E26") (pin "K2") (pinfunction "IN2B_K2") (pintype "input"))
      (node (ref "E26") (pin "U2") (pinfunction "IN2B_U2") (pintype "input"))
      (node (ref "E28") (pin "F1") (pinfunction "IN2B_F1") (pintype "input"))
      (node (ref "F20") (pin "U2") (pinfunction "IN2_U2") (pintype "input"))
      (node (ref "F22") (pin "E2") (pinfunction "IN2_E2") (pintype "input"))
    )
    (net (code "386") (name "KEY_STEXDP") (class "Default")
      (node (ref "A19") (pin "H2") (pinfunction "IN1_H2") (pintype "input"))
      (node (ref "E14") (pin "F2") (pinfunction "IN3_F2") (pintype "input"))
      (node (ref "E14") (pin "M2") (pinfunction "OUT_M2") (pintype "output"))
      (node (ref "F32") (pin "E1") (pinfunction "IN2_E1") (pintype "input"))
    )
    (net (code "387") (name "KEY_STOP_") (class "Default")
      (node (ref "B40") (pin "T2") (pinfunction "P$2_T2") (pintype "bidirectional"))
      (node (ref "E11") (pin "L1") (pinfunction "IN1_L1") (pintype "input"))
    )
    (net (code "388") (name "KEY_ST_") (class "Default")
      (node (ref "B40") (pin "K2") (pinfunction "P$2_K2") (pintype "bidirectional"))
      (node (ref "E11") (pin "D1") (pinfunction "IN1_D1") (pintype "input"))
      (node (ref "E14") (pin "J2") (pinfunction "IN1_J2") (pintype "input"))
      (node (ref "F19") (pin "E2") (pinfunction "IN2_E2") (pintype "input"))
    )
    (net (code "389") (name "LBAR_ENABLE") (class "Default")
      (node (ref "F29") (pin "N2") (pinfunction "OUT_N2") (pintype "output"))
      (node (ref "F33") (pin "M2") (pinfunction "IN3B_M2") (pintype "input"))
    )
    (net (code "390") (name "LEFT_SHIFT") (class "Default")
      (node (ref "E31") (pin "P2") (pinfunction "OUT_P2") (pintype "open_collector"))
      (node (ref "EF34") (pin "AF2") (pinfunction "AF2_AF2") (pintype "input"))
      (node (ref "EF35") (pin "AF2") (pinfunction "AF2_AF2") (pintype "input"))
      (node (ref "EF36") (pin "AF2") (pinfunction "AF2_AF2") (pintype "input"))
      (node (ref "EF37") (pin "AF2") (pinfunction "AF2_AF2") (pintype "input"))
      (node (ref "EF38") (pin "AF2") (pinfunction "AF2_AF2") (pintype "input"))
      (node (ref "EF39") (pin "AF2") (pinfunction "AF2_AF2") (pintype "input"))
      (node (ref "F33") (pin "L1") (pinfunction "IN4B_L1") (pintype "input"))
    )
    (net (code "391") (name "LEFT_SHIFT_") (class "Default")
      (node (ref "D12") (pin "H2") (pinfunction "IN1_H2") (pintype "input"))
      (node (ref "D12") (pin "K1") (pinfunction "OUT_K1") (pintype "output"))
      (node (ref "D12") (pin "U2") (pinfunction "IN2_U2") (pintype "input"))
    )
    (net (code "392") (name "LHS") (class "Default")
      (node (ref "D05") (pin "E1") (pinfunction "OUT_E1") (pintype "output"))
      (node (ref "D11") (pin "M2") (pinfunction "D_M2") (pintype "input"))
    )
    (net (code "393") (name "LHS_") (class "Default")
      (node (ref "D04") (pin "T2") (pinfunction "P$2_T2") (pintype "bidirectional"))
      (node (ref "D05") (pin "A1") (pinfunction "IN_A1") (pintype "input"))
      (node (ref "D05") (pin "B1") (pinfunction "IN2_B1") (pintype "bidirectional"))
      (node (ref "D05") (pin "C1") (pinfunction "IN3_C1") (pintype "input"))
      (node (ref "D05") (pin "D1") (pinfunction "IN4_D1") (pintype "input"))
    )
    (net (code "394") (name "LH_TO_HS") (class "Default")
      (node (ref "D06") (pin "F1") (pinfunction "OUT_F1") (pintype "output"))
      (node (ref "D07") (pin "R1") (pinfunction "IN2_R1") (pintype "input"))
      (node (ref "D11") (pin "L2") (pinfunction "C_L2") (pintype "input"))
    )
    (net (code "395") (name "LINE_") (class "Default")
      (node (ref "C10") (pin "P1") (pinfunction "IN1_P1") (pintype "input"))
      (node (ref "C10") (pin "T2") (pinfunction "IN1_T2") (pintype "input"))
      (node (ref "J15") (pin "P2") (pinfunction "OUT_P2") (pintype "output"))
    )
    (net (code "396") (name "LINE_HOLD_") (class "Default")
      (node (ref "C07") (pin "J2") (pinfunction "IN1_J2") (pintype "input"))
      (node (ref "D09") (pin "M1") (pinfunction "IN3_M1") (pintype "input"))
      (node (ref "D10") (pin "V2") (pinfunction "OUT_V2") (pintype "output"))
    )
    (net (code "397") (name "LINK") (class "Default")
      (node (ref "E24") (pin "T2") (pinfunction "IN1_T2") (pintype "input"))
      (node (ref "E33") (pin "V2") (pinfunction "1_V2") (pintype "output"))
      (node (ref "F33") (pin "J2") (pinfunction "IN2A_J2") (pintype "input"))
    )
    (net (code "398") (name "LINK_") (class "Default")
      (node (ref "C40") (pin "B1") (pinfunction "P$2_B1") (pintype "bidirectional"))
      (node (ref "E33") (pin "V1") (pinfunction "0_V1") (pintype "output"))
      (node (ref "F33") (pin "L2") (pinfunction "IN3A_L2") (pintype "input"))
    )
    (net (code "399") (name "LOAD_BF") (class "Default")
      (node (ref "A19") (pin "N2") (pinfunction "OUT_N2") (pintype "output"))
      (node (ref "B18") (pin "L2") (pinfunction "C_L2") (pintype "input"))
      (node (ref "B18") (pin "N1") (pinfunction "C_N1") (pintype "input"))
      (node (ref "B18") (pin "S2") (pinfunction "C_S2") (pintype "input"))
    )
    (net (code "400") (name "LOAD_IB") (class "Default")
      (node (ref "A18") (pin "C1") (pinfunction "OUT_C1") (pintype "output"))
      (node (ref "B17") (pin "L2") (pinfunction "C_L2") (pintype "input"))
      (node (ref "B17") (pin "N1") (pinfunction "C_N1") (pintype "input"))
      (node (ref "B17") (pin "S2") (pinfunction "C_S2") (pintype "input"))
    )
    (net (code "401") (name "LOAD_SF_") (class "Default")
      (node (ref "A19") (pin "R1") (pinfunction "IN2_R1") (pintype "input"))
      (node (ref "A19") (pin "R2") (pinfunction "IN2_R2") (pintype "input"))
      (node (ref "C12") (pin "P2") (pinfunction "OUT_P2") (pintype "open_collector"))
    )
    (net (code "402") (name "LOW_AC0") (class "Default")
      (node (ref "D21") (pin "D1") (pinfunction "IN4_D1") (pintype "input"))
      (node (ref "E24") (pin "S2") (pinfunction "OUT_S2") (pintype "output"))
      (node (ref "F23") (pin "C1") (pinfunction "IN3_C1") (pintype "input"))
    )
    (net (code "403") (name "L_ENABLE") (class "Default")
      (node (ref "E28") (pin "R1") (pinfunction "OUT_R1") (pintype "output"))
      (node (ref "F33") (pin "K2") (pinfunction "IN2B_K2") (pintype "input"))
    )
    (net (code "404") (name "MA00_") (class "Default")
      (node (ref "B14") (pin "A1") (pinfunction "IN1_A1") (pintype "input"))
      (node (ref "E40") (pin "U2") (pinfunction "P$2_U2") (pintype "bidirectional"))
      (node (ref "EF34") (pin "AM1") (pinfunction "AM1_AM1") (pintype "output"))
      (node (ref "F24") (pin "D2") (pinfunction "IN1_D2") (pintype "input"))
    )
    (net (code "405") (name "MA01_") (class "Default")
      (node (ref "B14") (pin "D2") (pinfunction "IN1_D2") (pintype "input"))
      (node (ref "E40") (pin "R2") (pinfunction "P$2_R2") (pintype "bidirectional"))
      (node (ref "EF34") (pin "AL1") (pinfunction "AL1_AL1") (pintype "output"))
      (node (ref "F24") (pin "E2") (pinfunction "IN2_E2") (pintype "input"))
    )
    (net (code "406") (name "MA02_") (class "Default")
      (node (ref "B14") (pin "F1") (pinfunction "IN1_F1") (pintype "input"))
      (node (ref "E40") (pin "K2") (pinfunction "P$2_K2") (pintype "bidirectional"))
      (node (ref "EF35") (pin "AM1") (pinfunction "AM1_AM1") (pintype "output"))
      (node (ref "F24") (pin "F2") (pinfunction "IN3_F2") (pintype "input"))
    )
    (net (code "407") (name "MA03_") (class "Default")
      (node (ref "B14") (pin "K2") (pinfunction "IN1_K2") (pintype "input"))
      (node (ref "E40") (pin "E2") (pinfunction "P$2_E2") (pintype "bidirectional"))
      (node (ref "EF35") (pin "AL1") (pinfunction "AL1_AL1") (pintype "output"))
      (node (ref "F24") (pin "H2") (pinfunction "IN4_H2") (pintype "input"))
    )
    (net (code "408") (name "MA04_") (class "Default")
      (node (ref "B14") (pin "M1") (pinfunction "IN1_M1") (pintype "input"))
      (node (ref "E40") (pin "L1") (pinfunction "P$2_L1") (pintype "bidirectional"))
      (node (ref "EF36") (pin "AM1") (pinfunction "AM1_AM1") (pintype "output"))
      (node (ref "F24") (pin "F1") (pinfunction "IN1_F1") (pintype "input"))
    )
    (net (code "409") (name "MA05_") (class "Default")
      (node (ref "B14") (pin "R2") (pinfunction "IN1_R2") (pintype "input"))
      (node (ref "E40") (pin "E1") (pinfunction "P$2_E1") (pintype "bidirectional"))
      (node (ref "EF36") (pin "AL1") (pinfunction "AL1_AL1") (pintype "output"))
      (node (ref "F24") (pin "H1") (pinfunction "IN2_H1") (pintype "input"))
    )
    (net (code "410") (name "MA06_") (class "Default")
      (node (ref "B15") (pin "A1") (pinfunction "IN1_A1") (pintype "input"))
      (node (ref "EF37") (pin "AM1") (pinfunction "AM1_AM1") (pintype "output"))
      (node (ref "F24") (pin "J1") (pinfunction "IN3_J1") (pintype "input"))
      (node (ref "F40") (pin "U2") (pinfunction "P$2_U2") (pintype "bidirectional"))
    )
    (net (code "411") (name "MA07_") (class "Default")
      (node (ref "B15") (pin "D2") (pinfunction "IN1_D2") (pintype "input"))
      (node (ref "EF37") (pin "AL1") (pinfunction "AL1_AL1") (pintype "output"))
      (node (ref "F24") (pin "K1") (pinfunction "IN4_K1") (pintype "input"))
      (node (ref "F40") (pin "R2") (pinfunction "P$2_R2") (pintype "bidirectional"))
    )
    (net (code "412") (name "MA08") (class "Default")
      (node (ref "EF38") (pin "AM2") (pinfunction "AM2_AM2") (pintype "output"))
      (node (ref "F25") (pin "L1") (pinfunction "IN1_L1") (pintype "input"))
    )
    (net (code "413") (name "MA08_") (class "Default")
      (node (ref "B15") (pin "F1") (pinfunction "IN1_F1") (pintype "input"))
      (node (ref "EF38") (pin "AM1") (pinfunction "AM1_AM1") (pintype "output"))
      (node (ref "F40") (pin "K2") (pinfunction "P$2_K2") (pintype "bidirectional"))
    )
    (net (code "414") (name "MA09_") (class "Default")
      (node (ref "B15") (pin "K2") (pinfunction "IN1_K2") (pintype "input"))
      (node (ref "EF38") (pin "AL1") (pinfunction "AL1_AL1") (pintype "output"))
      (node (ref "F40") (pin "E2") (pinfunction "P$2_E2") (pintype "bidirectional"))
    )
    (net (code "415") (name "MA10_") (class "Default")
      (node (ref "B15") (pin "M1") (pinfunction "IN1_M1") (pintype "input"))
      (node (ref "EF39") (pin "AM1") (pinfunction "AM1_AM1") (pintype "output"))
      (node (ref "F40") (pin "L1") (pinfunction "P$2_L1") (pintype "bidirectional"))
    )
    (net (code "416") (name "MA11_") (class "Default")
      (node (ref "B15") (pin "R2") (pinfunction "IN1_R2") (pintype "input"))
      (node (ref "EF39") (pin "AL1") (pinfunction "AL1_AL1") (pintype "output"))
      (node (ref "F40") (pin "E1") (pinfunction "P$2_E1") (pintype "bidirectional"))
    )
    (net (code "417") (name "MANUAL_PRESET_") (class "Default")
      (node (ref "B11") (pin "D1") (pinfunction "S_D1") (pintype "input"))
      (node (ref "B11") (pin "F2") (pinfunction "S_F2") (pintype "input"))
      (node (ref "B11") (pin "K1") (pinfunction "S_K1") (pintype "input"))
      (node (ref "D11") (pin "D1") (pinfunction "S_D1") (pintype "input"))
      (node (ref "D11") (pin "F2") (pinfunction "S_F2") (pintype "input"))
      (node (ref "E18") (pin "D1") (pinfunction "S_D1") (pintype "input"))
      (node (ref "E19") (pin "A1") (pinfunction "R_A1") (pintype "input"))
      (node (ref "E20") (pin "K2") (pinfunction "R_K2") (pintype "input"))
      (node (ref "E23") (pin "A1") (pinfunction "R_A1") (pintype "input"))
      (node (ref "E23") (pin "K2") (pinfunction "R_K2") (pintype "input"))
      (node (ref "E33") (pin "K1") (pinfunction "S_K1") (pintype "input"))
      (node (ref "F20") (pin "E1") (pinfunction "IN2_E1") (pintype "input"))
      (node (ref "F30") (pin "V2") (pinfunction "OUT_V2") (pintype "open_collector"))
    )
    (net (code "418") (name "MA_ENABLE0_4") (class "Default")
      (node (ref "EF34") (pin "BP1") (pinfunction "BP1_BP1") (pintype "input"))
      (node (ref "EF34") (pin "BR2") (pinfunction "BR2_BR2") (pintype "input"))
      (node (ref "EF35") (pin "BP1") (pinfunction "BP1_BP1") (pintype "input"))
      (node (ref "EF35") (pin "BR2") (pinfunction "BR2_BR2") (pintype "input"))
      (node (ref "EF36") (pin "BP1") (pinfunction "BP1_BP1") (pintype "input"))
      (node (ref "F31") (pin "L1") (pinfunction "OUT_L1") (pintype "open_collector"))
    )
    (net (code "419") (name "MA_ENABLE5_11") (class "Default")
      (node (ref "EF36") (pin "BR2") (pinfunction "BR2_BR2") (pintype "input"))
      (node (ref "EF37") (pin "BP1") (pinfunction "BP1_BP1") (pintype "input"))
      (node (ref "EF37") (pin "BR2") (pinfunction "BR2_BR2") (pintype "input"))
      (node (ref "EF38") (pin "BP1") (pinfunction "BP1_BP1") (pintype "input"))
      (node (ref "EF38") (pin "BR2") (pinfunction "BR2_BR2") (pintype "input"))
      (node (ref "EF39") (pin "BP1") (pinfunction "BP1_BP1") (pintype "input"))
      (node (ref "EF39") (pin "BR2") (pinfunction "BR2_BR2") (pintype "input"))
      (node (ref "F31") (pin "P2") (pinfunction "OUT_P2") (pintype "open_collector"))
    )
    (net (code "420") (name "MA_LOAD") (class "Default")
      (node (ref "E32") (pin "E1") (pinfunction "OUT_E1") (pintype "open_collector"))
      (node (ref "EF34") (pin "AK1") (pinfunction "AK1_AK1") (pintype "input"))
      (node (ref "EF35") (pin "AK1") (pinfunction "AK1_AK1") (pintype "input"))
      (node (ref "EF36") (pin "AK1") (pinfunction "AK1_AK1") (pintype "input"))
      (node (ref "EF37") (pin "AK1") (pinfunction "AK1_AK1") (pintype "input"))
      (node (ref "EF38") (pin "AK1") (pinfunction "AK1_AK1") (pintype "input"))
      (node (ref "EF39") (pin "AK1") (pinfunction "AK1_AK1") (pintype "input"))
    )
    (net (code "421") (name "MB00") (class "Default")
      (node (ref "A09") (pin "E1") (pinfunction "1A_E1") (pintype "input"))
      (node (ref "B12") (pin "A1") (pinfunction "IN1_A1") (pintype "input"))
      (node (ref "EF34") (pin "AT2") (pinfunction "AT2_AT2") (pintype "output"))
      (node (ref "H13") (pin "H2") (pinfunction "IN2_H2") (pintype "input"))
    )
    (net (code "422") (name "MB00_") (class "Default")
      (node (ref "A09") (pin "A1") (pinfunction "1B_A1") (pintype "input"))
      (node (ref "E40") (pin "R1") (pinfunction "P$2_R1") (pintype "bidirectional"))
      (node (ref "EF34") (pin "AU2") (pinfunction "AU2_AU2") (pintype "output"))
    )
    (net (code "423") (name "MB01") (class "Default")
      (node (ref "A09") (pin "F1") (pinfunction "2A_F1") (pintype "input"))
      (node (ref "B12") (pin "D2") (pinfunction "IN1_D2") (pintype "input"))
      (node (ref "EF34") (pin "AS2") (pinfunction "AS2_AS2") (pintype "output"))
      (node (ref "H13") (pin "N2") (pinfunction "IN2_N2") (pintype "input"))
    )
    (net (code "424") (name "MB01_") (class "Default")
      (node (ref "A09") (pin "B1") (pinfunction "2B_B1") (pintype "input"))
      (node (ref "E40") (pin "P1") (pinfunction "P$2_P1") (pintype "bidirectional"))
      (node (ref "EF34") (pin "AS1") (pinfunction "AS1_AS1") (pintype "output"))
    )
    (net (code "425") (name "MB02") (class "Default")
      (node (ref "A09") (pin "H1") (pinfunction "4A_H1") (pintype "input"))
      (node (ref "B12") (pin "F1") (pinfunction "IN1_F1") (pintype "input"))
      (node (ref "EF35") (pin "AT2") (pinfunction "AT2_AT2") (pintype "output"))
      (node (ref "H13") (pin "U2") (pinfunction "IN2_U2") (pintype "input"))
    )
    (net (code "426") (name "MB02_") (class "Default")
      (node (ref "A09") (pin "C1") (pinfunction "4B_C1") (pintype "input"))
      (node (ref "E40") (pin "F2") (pinfunction "P$2_F2") (pintype "bidirectional"))
      (node (ref "EF35") (pin "AU2") (pinfunction "AU2_AU2") (pintype "output"))
    )
    (net (code "427") (name "MB03") (class "Default")
      (node (ref "A09") (pin "J1") (pinfunction "8A_J1") (pintype "input"))
      (node (ref "B12") (pin "K2") (pinfunction "IN1_K2") (pintype "input"))
      (node (ref "C11") (pin "P1") (pinfunction "IN1_P1") (pintype "input"))
      (node (ref "D20") (pin "P1") (pinfunction "IN3_P1") (pintype "input"))
      (node (ref "E25") (pin "L2") (pinfunction "IN3_L2") (pintype "input"))
      (node (ref "EF35") (pin "AS2") (pinfunction "AS2_AS2") (pintype "output"))
      (node (ref "F27") (pin "K1") (pinfunction "IN4_K1") (pintype "input"))
      (node (ref "H14") (pin "N2") (pinfunction "IN2_N2") (pintype "input"))
    )
    (net (code "428") (name "MB03_") (class "Default")
      (node (ref "A04") (pin "D2") (pinfunction "D2_D2") (pintype "input"))
      (node (ref "A09") (pin "D1") (pinfunction "8B_D1") (pintype "input"))
      (node (ref "B07") (pin "A1") (pinfunction "IN1_A1") (pintype "input"))
      (node (ref "B16") (pin "L2") (pinfunction "IN2_L2") (pintype "input"))
      (node (ref "E26") (pin "C1") (pinfunction "IN1C_C1") (pintype "input"))
      (node (ref "E40") (pin "D2") (pinfunction "P$2_D2") (pintype "bidirectional"))
      (node (ref "EF35") (pin "AS1") (pinfunction "AS1_AS1") (pintype "output"))
      (node (ref "F09") (pin "B1") (pinfunction "IN2_B1") (pintype "input"))
      (node (ref "F19") (pin "T2") (pinfunction "IN3_T2") (pintype "input"))
      (node (ref "F23") (pin "K1") (pinfunction "IN4_K1") (pintype "input"))
      (node (ref "F27") (pin "D1") (pinfunction "IN4_D1") (pintype "input"))
      (node (ref "F27") (pin "U2") (pinfunction "IN4_U2") (pintype "input"))
      (node (ref "H14") (pin "H2") (pinfunction "IN2_H2") (pintype "input"))
    )
    (net (code "429") (name "MB04") (class "Default")
      (node (ref "A10") (pin "P2") (pinfunction "1A_P2") (pintype "input"))
      (node (ref "B12") (pin "M1") (pinfunction "IN1_M1") (pintype "input"))
      (node (ref "B16") (pin "M2") (pinfunction "IN3_M2") (pintype "input"))
      (node (ref "E30") (pin "V1") (pinfunction "IN2A_V1") (pintype "input"))
      (node (ref "EF36") (pin "AT2") (pinfunction "AT2_AT2") (pintype "output"))
      (node (ref "F09") (pin "C1") (pinfunction "IN3_C1") (pintype "input"))
      (node (ref "F28") (pin "F2") (pinfunction "IN3_F2") (pintype "input"))
      (node (ref "H15") (pin "H2") (pinfunction "IN2_H2") (pintype "input"))
    )
    (net (code "430") (name "MB04_") (class "Default")
      (node (ref "A04") (pin "E2") (pinfunction "E2_E2") (pintype "input"))
      (node (ref "A10") (pin "K2") (pinfunction "1B_K2") (pintype "input"))
      (node (ref "B07") (pin "B1") (pinfunction "IN2_B1") (pintype "input"))
      (node (ref "C11") (pin "R1") (pinfunction "IN2_R1") (pintype "input"))
      (node (ref "D21") (pin "J1") (pinfunction "IN3_J1") (pintype "input"))
      (node (ref "E30") (pin "H2") (pinfunction "IN1D_H2") (pintype "input"))
      (node (ref "E30") (pin "S1") (pinfunction "IN1A_S1") (pintype "input"))
      (node (ref "E40") (pin "K1") (pinfunction "P$2_K1") (pintype "bidirectional"))
      (node (ref "EF36") (pin "AU2") (pinfunction "AU2_AU2") (pintype "output"))
      (node (ref "F19") (pin "U2") (pinfunction "IN4_U2") (pintype "input"))
      (node (ref "H14") (pin "U2") (pinfunction "IN2_U2") (pintype "input"))
    )
    (net (code "431") (name "MB05") (class "Default")
      (node (ref "A04") (pin "F2") (pinfunction "F2_F2") (pintype "input"))
      (node (ref "A10") (pin "R2") (pinfunction "2A_R2") (pintype "input"))
      (node (ref "B07") (pin "C1") (pinfunction "IN3_C1") (pintype "input"))
      (node (ref "B12") (pin "R2") (pinfunction "IN1_R2") (pintype "input"))
      (node (ref "D18") (pin "D2") (pinfunction "IN1_D2") (pintype "input"))
      (node (ref "E24") (pin "M1") (pinfunction "IN2_M1") (pintype "input"))
      (node (ref "E28") (pin "M1") (pinfunction "IN5A_M1") (pintype "input"))
      (node (ref "EF36") (pin "AS2") (pinfunction "AS2_AS2") (pintype "output"))
      (node (ref "H15") (pin "U2") (pinfunction "IN2_U2") (pintype "input"))
    )
    (net (code "432") (name "MB05_") (class "Default")
      (node (ref "A10") (pin "L2") (pinfunction "2B_L2") (pintype "input"))
      (node (ref "B16") (pin "N2") (pinfunction "IN4_N2") (pintype "input"))
      (node (ref "C11") (pin "S1") (pinfunction "IN3_S1") (pintype "input"))
      (node (ref "E28") (pin "B1") (pinfunction "IN1B_B1") (pintype "input"))
      (node (ref "E40") (pin "A1") (pinfunction "P$2_A1") (pintype "bidirectional"))
      (node (ref "EF36") (pin "AS1") (pinfunction "AS1_AS1") (pintype "output"))
      (node (ref "F09") (pin "D1") (pinfunction "IN4_D1") (pintype "input"))
      (node (ref "F23") (pin "R2") (pinfunction "IN1_R2") (pintype "input"))
      (node (ref "H15") (pin "N2") (pinfunction "IN2_N2") (pintype "input"))
    )
    (net (code "433") (name "MB06") (class "Default")
      (node (ref "A10") (pin "S2") (pinfunction "4A_S2") (pintype "input"))
      (node (ref "A12") (pin "E2") (pinfunction "IN2_E2") (pintype "input"))
      (node (ref "A15") (pin "T2") (pinfunction "IN1_T2") (pintype "input"))
      (node (ref "A18") (pin "E2") (pinfunction "IN2_E2") (pintype "input"))
      (node (ref "B13") (pin "A1") (pinfunction "IN1_A1") (pintype "input"))
      (node (ref "D18") (pin "H1") (pinfunction "IN3_H1") (pintype "input"))
      (node (ref "E30") (pin "U1") (pinfunction "IN1B_U1") (pintype "input"))
      (node (ref "EF37") (pin "AT2") (pinfunction "AT2_AT2") (pintype "output"))
      (node (ref "F23") (pin "D1") (pinfunction "IN4_D1") (pintype "input"))
      (node (ref "F32") (pin "J2") (pinfunction "IN2_J2") (pintype "input"))
      (node (ref "H16") (pin "N2") (pinfunction "IN2_N2") (pintype "input"))
    )
    (net (code "434") (name "MB06XMB09") (class "Default")
      (node (ref "A06") (pin "N2") (pinfunction "OUT_N2") (pintype "output"))
      (node (ref "A06") (pin "U2") (pinfunction "IN2_U2") (pintype "input"))
      (node (ref "B04") (pin "F1") (pinfunction "IN2_F1") (pintype "input"))
      (node (ref "B06") (pin "B1") (pinfunction "IN2_B1") (pintype "input"))
    )
    (net (code "435") (name "MB06_") (class "Default")
      (node (ref "A04") (pin "H2") (pinfunction "H2_H2") (pintype "input"))
      (node (ref "A10") (pin "M2") (pinfunction "4B_M2") (pintype "input"))
      (node (ref "B07") (pin "D2") (pinfunction "IN1_D2") (pintype "input"))
      (node (ref "C11") (pin "T2") (pinfunction "IN1_T2") (pintype "input"))
      (node (ref "E30") (pin "U2") (pinfunction "IN2B_U2") (pintype "input"))
      (node (ref "EF37") (pin "AU2") (pinfunction "AU2_AU2") (pintype "output"))
      (node (ref "F09") (pin "D2") (pinfunction "IN5_D2") (pintype "input"))
      (node (ref "F23") (pin "S2") (pinfunction "IN2_S2") (pintype "input"))
      (node (ref "F40") (pin "R1") (pinfunction "P$2_R1") (pintype "bidirectional"))
      (node (ref "H16") (pin "H2") (pinfunction "IN2_H2") (pintype "input"))
    )
    (net (code "436") (name "MB07") (class "Default")
      (node (ref "A10") (pin "T2") (pinfunction "8A_T2") (pintype "input"))
      (node (ref "A12") (pin "M1") (pinfunction "IN2_M1") (pintype "input"))
      (node (ref "A18") (pin "M1") (pinfunction "IN2_M1") (pintype "input"))
      (node (ref "A20") (pin "R1") (pinfunction "IN2_R1") (pintype "input"))
      (node (ref "A20") (pin "R2") (pinfunction "IN3_R2") (pintype "input"))
      (node (ref "B06") (pin "A1") (pinfunction "IN1_A1") (pintype "input"))
      (node (ref "B13") (pin "D2") (pinfunction "IN1_D2") (pintype "input"))
      (node (ref "D18") (pin "K1") (pinfunction "IN1_K1") (pintype "input"))
      (node (ref "D21") (pin "H1") (pinfunction "IN2_H1") (pintype "input"))
      (node (ref "E24") (pin "U2") (pinfunction "IN2_U2") (pintype "input"))
      (node (ref "E28") (pin "D1") (pinfunction "IN1D_D1") (pintype "input"))
      (node (ref "EF37") (pin "AS2") (pinfunction "AS2_AS2") (pintype "output"))
      (node (ref "F29") (pin "U2") (pinfunction "IN2_U2") (pintype "input"))
      (node (ref "H17") (pin "H2") (pinfunction "IN2_H2") (pintype "input"))
    )
    (net (code "437") (name "MB07_") (class "Default")
      (node (ref "A04") (pin "J2") (pinfunction "J2_J2") (pintype "input"))
      (node (ref "A06") (pin "P1") (pinfunction "IN1_P1") (pintype "input"))
      (node (ref "A10") (pin "N2") (pinfunction "8B_N2") (pintype "input"))
      (node (ref "A20") (pin "L1") (pinfunction "IN2_L1") (pintype "input"))
      (node (ref "B04") (pin "A1") (pinfunction "IN1_A1") (pintype "input"))
      (node (ref "B04") (pin "H1") (pinfunction "IN3_H1") (pintype "input"))
      (node (ref "B07") (pin "E2") (pinfunction "IN2_E2") (pintype "input"))
      (node (ref "C11") (pin "U2") (pinfunction "IN2_U2") (pintype "input"))
      (node (ref "C14") (pin "U2") (pinfunction "IN2_U2") (pintype "input"))
      (node (ref "E28") (pin "P1") (pinfunction "IN5C_P1") (pintype "input"))
      (node (ref "EF37") (pin "AS1") (pinfunction "AS1_AS1") (pintype "output"))
      (node (ref "F23") (pin "T2") (pinfunction "IN3_T2") (pintype "input"))
      (node (ref "F40") (pin "P1") (pinfunction "P$2_P1") (pintype "bidirectional"))
      (node (ref "H16") (pin "U2") (pinfunction "IN2_U2") (pintype "input"))
    )
    (net (code "438") (name "MB08") (class "Default")
      (node (ref "A09") (pin "P2") (pinfunction "1A_P2") (pintype "input"))
      (node (ref "A12") (pin "R2") (pinfunction "IN2_R2") (pintype "input"))
      (node (ref "A18") (pin "R2") (pinfunction "IN2_R2") (pintype "input"))
      (node (ref "A20") (pin "M1") (pinfunction "IN3_M1") (pintype "input"))
      (node (ref "A20") (pin "P2") (pinfunction "IN2_P2") (pintype "input"))
      (node (ref "B04") (pin "E1") (pinfunction "IN1_E1") (pintype "input"))
      (node (ref "B06") (pin "M1") (pinfunction "IN2_M1") (pintype "input"))
      (node (ref "B13") (pin "F1") (pinfunction "IN1_F1") (pintype "input"))
      (node (ref "D24") (pin "C1") (pinfunction "D_C1") (pintype "input"))
      (node (ref "E28") (pin "R2") (pinfunction "IN4C_R2") (pintype "input"))
      (node (ref "EF38") (pin "AT2") (pinfunction "AT2_AT2") (pintype "output"))
      (node (ref "F26") (pin "D2") (pinfunction "IN1_D2") (pintype "input"))
      (node (ref "F26") (pin "E1") (pinfunction "IN1_E1") (pintype "input"))
      (node (ref "H17") (pin "U2") (pinfunction "IN2_U2") (pintype "input"))
    )
    (net (code "439") (name "MB08_") (class "Default")
      (node (ref "A04") (pin "K2") (pinfunction "K2_K2") (pintype "input"))
      (node (ref "A06") (pin "R1") (pinfunction "IN2_R1") (pintype "input"))
      (node (ref "A09") (pin "K2") (pinfunction "1B_K2") (pintype "input"))
      (node (ref "A20") (pin "S1") (pinfunction "IN3_S1") (pintype "input"))
      (node (ref "B04") (pin "B1") (pinfunction "IN2_B1") (pintype "input"))
      (node (ref "B07") (pin "F2") (pinfunction "IN3_F2") (pintype "input"))
      (node (ref "C11") (pin "V2") (pinfunction "IN3_V2") (pintype "input"))
      (node (ref "C15") (pin "U2") (pinfunction "IN2_U2") (pintype "input"))
      (node (ref "E28") (pin "M2") (pinfunction "IN3B_M2") (pintype "input"))
      (node (ref "EF38") (pin "AU2") (pinfunction "AU2_AU2") (pintype "output"))
      (node (ref "F23") (pin "U2") (pinfunction "IN4_U2") (pintype "input"))
      (node (ref "F26") (pin "K1") (pinfunction "IN1_K1") (pintype "input"))
      (node (ref "F40") (pin "F2") (pinfunction "P$2_F2") (pintype "bidirectional"))
      (node (ref "H17") (pin "N2") (pinfunction "IN2_N2") (pintype "input"))
    )
    (net (code "440") (name "MB09") (class "Default")
      (node (ref "A09") (pin "R2") (pinfunction "2A_R2") (pintype "input"))
      (node (ref "A14") (pin "D2") (pinfunction "IN1_D2") (pintype "input"))
      (node (ref "B13") (pin "K2") (pinfunction "IN1_K2") (pintype "input"))
      (node (ref "C11") (pin "L1") (pinfunction "IN2_L1") (pintype "input"))
      (node (ref "D13") (pin "E1") (pinfunction "IN2_E1") (pintype "input"))
      (node (ref "D24") (pin "E2") (pinfunction "D_E2") (pintype "input"))
      (node (ref "EF38") (pin "AS2") (pinfunction "AS2_AS2") (pintype "output"))
      (node (ref "F09") (pin "E2") (pinfunction "IN6_E2") (pintype "input"))
      (node (ref "F20") (pin "J2") (pinfunction "IN2_J2") (pintype "input"))
      (node (ref "F26") (pin "A1") (pinfunction "IN1_A1") (pintype "input"))
      (node (ref "F26") (pin "J2") (pinfunction "IN1_J2") (pintype "input"))
      (node (ref "F28") (pin "R2") (pinfunction "IN3_R2") (pintype "input"))
      (node (ref "H18") (pin "H2") (pinfunction "IN2_H2") (pintype "input"))
    )
    (net (code "441") (name "MB09_") (class "Default")
      (node (ref "A05") (pin "B1") (pinfunction "IN2_B1") (pintype "input"))
      (node (ref "A09") (pin "L2") (pinfunction "2B_L2") (pintype "input"))
      (node (ref "C16") (pin "U2") (pinfunction "IN2_U2") (pintype "input"))
      (node (ref "D13") (pin "P1") (pinfunction "IN1_P1") (pintype "input"))
      (node (ref "EF38") (pin "AS1") (pinfunction "AS1_AS1") (pintype "output"))
      (node (ref "F26") (pin "M1") (pinfunction "IN3_M1") (pintype "input"))
      (node (ref "F40") (pin "D2") (pinfunction "P$2_D2") (pintype "bidirectional"))
    )
    (net (code "442") (name "MB10") (class "Default")
      (node (ref "A09") (pin "S2") (pinfunction "4A_S2") (pintype "input"))
      (node (ref "A12") (pin "B1") (pinfunction "IN2_B1") (pintype "input"))
      (node (ref "A15") (pin "P2") (pinfunction "IN1_P2") (pintype "input"))
      (node (ref "B13") (pin "M1") (pinfunction "IN1_M1") (pintype "input"))
      (node (ref "D10") (pin "D1") (pinfunction "IN4_D1") (pintype "input"))
      (node (ref "D10") (pin "F2") (pinfunction "IN3_F2") (pintype "input"))
      (node (ref "D24") (pin "J1") (pinfunction "D_J1") (pintype "input"))
      (node (ref "E13") (pin "A1") (pinfunction "IN1A_A1") (pintype "input"))
      (node (ref "E14") (pin "H1") (pinfunction "IN3_H1") (pintype "input"))
      (node (ref "EF39") (pin "AT2") (pinfunction "AT2_AT2") (pintype "output"))
      (node (ref "F20") (pin "J1") (pinfunction "IN2_J1") (pintype "input"))
      (node (ref "F26") (pin "C1") (pinfunction "IN3_C1") (pintype "input"))
      (node (ref "F26") (pin "F2") (pinfunction "IN3_F2") (pintype "input"))
      (node (ref "H18") (pin "N2") (pinfunction "IN2_N2") (pintype "input"))
    )
    (net (code "443") (name "MB10_") (class "Default")
      (node (ref "A05") (pin "A1") (pinfunction "IN1_A1") (pintype "input"))
      (node (ref "A09") (pin "M2") (pinfunction "4B_M2") (pintype "input"))
      (node (ref "A15") (pin "L1") (pinfunction "IN1_L1") (pintype "input"))
      (node (ref "C17") (pin "U2") (pinfunction "IN2_U2") (pintype "input"))
      (node (ref "D13") (pin "R1") (pinfunction "IN2_R1") (pintype "input"))
      (node (ref "EF39") (pin "AU2") (pinfunction "AU2_AU2") (pintype "output"))
      (node (ref "F21") (pin "L2") (pinfunction "IN1_L2") (pintype "input"))
      (node (ref "F26") (pin "H1") (pinfunction "IN3_H1") (pintype "input"))
      (node (ref "F26") (pin "L2") (pinfunction "IN3_L2") (pintype "input"))
      (node (ref "F40") (pin "K1") (pinfunction "P$2_K1") (pintype "bidirectional"))
    )
    (net (code "444") (name "MB11") (class "Default")
      (node (ref "A09") (pin "T2") (pinfunction "8A_T2") (pintype "input"))
      (node (ref "A11") (pin "B1") (pinfunction "IN2_B1") (pintype "input"))
      (node (ref "B13") (pin "R2") (pinfunction "IN1_R2") (pintype "input"))
      (node (ref "D10") (pin "R1") (pinfunction "IN4_R1") (pintype "input"))
      (node (ref "D10") (pin "U2") (pinfunction "IN4_U2") (pintype "input"))
      (node (ref "D18") (pin "E1") (pinfunction "IN1_E1") (pintype "input"))
      (node (ref "D18") (pin "F2") (pinfunction "IN3_F2") (pintype "input"))
      (node (ref "D20") (pin "R1") (pinfunction "IN4_R1") (pintype "input"))
      (node (ref "D21") (pin "F1") (pinfunction "IN1_F1") (pintype "input"))
      (node (ref "E27") (pin "J1") (pinfunction "IN3B_J1") (pintype "input"))
      (node (ref "EF39") (pin "AS2") (pinfunction "AS2_AS2") (pintype "output"))
      (node (ref "F20") (pin "E2") (pinfunction "IN2_E2") (pintype "input"))
      (node (ref "H18") (pin "U2") (pinfunction "IN2_U2") (pintype "input"))
    )
    (net (code "445") (name "MB11_") (class "Default")
      (node (ref "A09") (pin "N2") (pinfunction "8B_N2") (pintype "input"))
      (node (ref "A13") (pin "A1") (pinfunction "IN1_A1") (pintype "input"))
      (node (ref "B04") (pin "D2") (pinfunction "IN1_D2") (pintype "input"))
      (node (ref "C18") (pin "R1") (pinfunction "IN2_R1") (pintype "input"))
      (node (ref "D09") (pin "F2") (pinfunction "IN3_F2") (pintype "input"))
      (node (ref "D10") (pin "H2") (pinfunction "IN4_H2") (pintype "input"))
      (node (ref "E13") (pin "B1") (pinfunction "IN1B_B1") (pintype "input"))
      (node (ref "E25") (pin "N2") (pinfunction "IN1_N2") (pintype "input"))
      (node (ref "E28") (pin "S2") (pinfunction "IN4D_S2") (pintype "input"))
      (node (ref "E33") (pin "P1") (pinfunction "D_P1") (pintype "input"))
      (node (ref "EF39") (pin "AS1") (pinfunction "AS1_AS1") (pintype "output"))
      (node (ref "F21") (pin "M2") (pinfunction "IN2_M2") (pintype "input"))
      (node (ref "F28") (pin "P2") (pinfunction "IN2_P2") (pintype "input"))
      (node (ref "F40") (pin "A1") (pinfunction "P$2_A1") (pintype "bidirectional"))
    )
    (net (code "446") (name "MB_LOAD") (class "Default")
      (node (ref "E32") (pin "L1") (pinfunction "OUT_L1") (pintype "open_collector"))
      (node (ref "EF34") (pin "AR1") (pinfunction "AR1_AR1") (pintype "input"))
      (node (ref "EF35") (pin "AR1") (pinfunction "AR1_AR1") (pintype "input"))
      (node (ref "EF36") (pin "AR1") (pinfunction "AR1_AR1") (pintype "input"))
      (node (ref "EF37") (pin "AR1") (pinfunction "AR1_AR1") (pintype "input"))
      (node (ref "EF38") (pin "AR1") (pinfunction "AR1_AR1") (pintype "input"))
      (node (ref "EF39") (pin "AR1") (pinfunction "AR1_AR1") (pintype "input"))
    )
    (net (code "447") (name "MB_PARITY_ODD") (class "Default")
      (node (ref "A10") (pin "K1") (pinfunction "ODD_K1") (pintype "output"))
      (node (ref "H05") (pin "T2") (pinfunction "P$2_T2") (pintype "bidirectional"))
    )
    (net (code "448") (name "MB_TO_IB") (class "Default")
      (node (ref "A15") (pin "S1") (pinfunction "OUT_S1") (pintype "output"))
      (node (ref "A18") (pin "D2") (pinfunction "IN1_D2") (pintype "input"))
      (node (ref "A18") (pin "L1") (pinfunction "IN1_L1") (pintype "input"))
      (node (ref "A18") (pin "P2") (pinfunction "IN1_P2") (pintype "input"))
    )
    (net (code "449") (name "MB_TO_SC_ENABLE") (class "Default")
      (node (ref "C14") (pin "T2") (pinfunction "IN1_T2") (pintype "input"))
      (node (ref "C15") (pin "T2") (pinfunction "IN1_T2") (pintype "input"))
      (node (ref "C16") (pin "T2") (pinfunction "IN1_T2") (pintype "input"))
      (node (ref "C17") (pin "T2") (pinfunction "IN1_T2") (pintype "input"))
      (node (ref "C18") (pin "P1") (pinfunction "IN1_P1") (pintype "input"))
      (node (ref "D15") (pin "N2") (pinfunction "OUT_N2") (pintype "output"))
    )
    (net (code "450") (name "MCBMB00_") (class "Default")
      (node (ref "B12") (pin "E1") (pinfunction "OUT_E1") (pintype "open_collector"))
      (node (ref "H02") (pin "S2") (pinfunction "P$2_S2") (pintype "bidirectional"))
    )
    (net (code "451") (name "MCBMB01_") (class "Default")
      (node (ref "B12") (pin "J2") (pinfunction "OUT_J2") (pintype "open_collector"))
      (node (ref "H02") (pin "T2") (pinfunction "P$2_T2") (pintype "bidirectional"))
    )
    (net (code "452") (name "MCBMB02_") (class "Default")
      (node (ref "B12") (pin "L1") (pinfunction "OUT_L1") (pintype "open_collector"))
      (node (ref "H02") (pin "V2") (pinfunction "P$2_V2") (pintype "bidirectional"))
    )
    (net (code "453") (name "MCBMB03_") (class "Default")
      (node (ref "B12") (pin "P2") (pinfunction "OUT_P2") (pintype "open_collector"))
      (node (ref "H03") (pin "D2") (pinfunction "P$2_D2") (pintype "bidirectional"))
    )
    (net (code "454") (name "MCBMB04_") (class "Default")
      (node (ref "B12") (pin "S1") (pinfunction "OUT_S1") (pintype "open_collector"))
      (node (ref "H03") (pin "E2") (pinfunction "P$2_E2") (pintype "bidirectional"))
    )
    (net (code "455") (name "MCBMB05_") (class "Default")
      (node (ref "B12") (pin "V2") (pinfunction "OUT_V2") (pintype "open_collector"))
      (node (ref "H03") (pin "H2") (pinfunction "P$2_H2") (pintype "bidirectional"))
    )
    (net (code "456") (name "MCBMB06_") (class "Default")
      (node (ref "B13") (pin "E1") (pinfunction "OUT_E1") (pintype "open_collector"))
      (node (ref "H03") (pin "K2") (pinfunction "P$2_K2") (pintype "bidirectional"))
    )
    (net (code "457") (name "MCBMB07_") (class "Default")
      (node (ref "B13") (pin "J2") (pinfunction "OUT_J2") (pintype "open_collector"))
      (node (ref "H03") (pin "M2") (pinfunction "P$2_M2") (pintype "bidirectional"))
    )
    (net (code "458") (name "MCBMB08_") (class "Default")
      (node (ref "B13") (pin "L1") (pinfunction "OUT_L1") (pintype "open_collector"))
      (node (ref "H03") (pin "P2") (pinfunction "P$2_P2") (pintype "bidirectional"))
    )
    (net (code "459") (name "MCBMB09_") (class "Default")
      (node (ref "B13") (pin "P2") (pinfunction "OUT_P2") (pintype "open_collector"))
      (node (ref "H03") (pin "S2") (pinfunction "P$2_S2") (pintype "bidirectional"))
    )
    (net (code "460") (name "MCBMB10_") (class "Default")
      (node (ref "B13") (pin "S1") (pinfunction "OUT_S1") (pintype "open_collector"))
      (node (ref "H03") (pin "T2") (pinfunction "P$2_T2") (pintype "bidirectional"))
    )
    (net (code "461") (name "MCBMB11_") (class "Default")
      (node (ref "B13") (pin "V2") (pinfunction "OUT_V2") (pintype "open_collector"))
      (node (ref "H03") (pin "V2") (pinfunction "P$2_V2") (pintype "bidirectional"))
    )
    (net (code "462") (name "ME05_") (class "Default")
      (node (ref "A05") (pin "K2") (pinfunction "OUT_K2") (pintype "output"))
      (node (ref "J13") (pin "U2") (pinfunction "IN4_U2") (pintype "input"))
    )
    (net (code "463") (name "ME06_") (class "Default")
      (node (ref "A13") (pin "N1") (pinfunction "OUT_N1") (pintype "output"))
      (node (ref "J14") (pin "D1") (pinfunction "IN4_D1") (pintype "input"))
    )
    (net (code "464") (name "ME07_") (class "Default")
      (node (ref "A13") (pin "S1") (pinfunction "OUT_S1") (pintype "output"))
      (node (ref "J14") (pin "H2") (pinfunction "IN4_H2") (pintype "input"))
    )
    (net (code "465") (name "ME08_") (class "Default")
      (node (ref "A13") (pin "V2") (pinfunction "OUT_V2") (pintype "output"))
      (node (ref "J14") (pin "K1") (pinfunction "IN4_K1") (pintype "input"))
    )
    (net (code "466") (name "ME09_") (class "Default")
      (node (ref "A13") (pin "K2") (pinfunction "OUT_K2") (pintype "output"))
      (node (ref "J14") (pin "N2") (pinfunction "IN4_N2") (pintype "input"))
    )
    (net (code "467") (name "ME10_") (class "Default")
      (node (ref "A13") (pin "N2") (pinfunction "OUT_N2") (pintype "output"))
      (node (ref "J14") (pin "R1") (pinfunction "IN4_R1") (pintype "input"))
    )
    (net (code "468") (name "ME11_") (class "Default")
      (node (ref "A13") (pin "S2") (pinfunction "OUT_S2") (pintype "output"))
      (node (ref "J14") (pin "U2") (pinfunction "IN4_U2") (pintype "input"))
    )
    (net (code "469") (name "MEM00") (class "Default")
      (node (ref "A07") (pin "E1") (pinfunction "1A_E1") (pintype "input"))
      (node (ref "B08") (pin "H1") (pinfunction "IN1_H1") (pintype "input"))
      (node (ref "C09") (pin "A1") (pinfunction "IN1_A1") (pintype "input"))
      (node (ref "EF34") (pin "BR1") (pinfunction "BR1_BR1") (pintype "input"))
      (node (ref "F22") (pin "B1") (pinfunction "IN2_B1") (pintype "input"))
      (node (ref "H04") (pin "E2") (pinfunction "P$2_E2") (pintype "bidirectional"))
    )
    (net (code "470") (name "MEM01") (class "Default")
      (node (ref "A07") (pin "F1") (pinfunction "2A_F1") (pintype "input"))
      (node (ref "B08") (pin "D2") (pinfunction "IN1_D2") (pintype "input"))
      (node (ref "E20") (pin "E2") (pinfunction "D_E2") (pintype "input"))
      (node (ref "EF34") (pin "BV2") (pinfunction "BV2_BV2") (pintype "input"))
      (node (ref "H04") (pin "H2") (pinfunction "P$2_H2") (pintype "bidirectional"))
    )
    (net (code "471") (name "MEM02") (class "Default")
      (node (ref "A07") (pin "H1") (pinfunction "4A_H1") (pintype "input"))
      (node (ref "B08") (pin "D1") (pinfunction "IN1_D1") (pintype "input"))
      (node (ref "E20") (pin "J1") (pinfunction "D_J1") (pintype "input"))
      (node (ref "EF35") (pin "BR1") (pinfunction "BR1_BR1") (pintype "input"))
      (node (ref "H04") (pin "K2") (pinfunction "P$2_K2") (pintype "bidirectional"))
    )
    (net (code "472") (name "MEM03") (class "Default")
      (node (ref "A07") (pin "J1") (pinfunction "8A_J1") (pintype "input"))
      (node (ref "B08") (pin "A1") (pinfunction "IN1_A1") (pintype "input"))
      (node (ref "EF35") (pin "BV2") (pinfunction "BV2_BV2") (pintype "input"))
      (node (ref "H04") (pin "M2") (pinfunction "P$2_M2") (pintype "bidirectional"))
    )
    (net (code "473") (name "MEM04") (class "Default")
      (node (ref "A08") (pin "P2") (pinfunction "1A_P2") (pintype "input"))
      (node (ref "B08") (pin "P1") (pinfunction "IN1_P1") (pintype "input"))
      (node (ref "EF36") (pin "BR1") (pinfunction "BR1_BR1") (pintype "input"))
      (node (ref "H04") (pin "P2") (pinfunction "P$2_P2") (pintype "bidirectional"))
    )
    (net (code "474") (name "MEM05") (class "Default")
      (node (ref "A08") (pin "R2") (pinfunction "2A_R2") (pintype "input"))
      (node (ref "B08") (pin "L2") (pinfunction "IN1_L2") (pintype "input"))
      (node (ref "EF36") (pin "BV2") (pinfunction "BV2_BV2") (pintype "input"))
      (node (ref "H04") (pin "S2") (pinfunction "P$2_S2") (pintype "bidirectional"))
    )
    (net (code "475") (name "MEM06") (class "Default")
      (node (ref "A08") (pin "S2") (pinfunction "4A_S2") (pintype "input"))
      (node (ref "B08") (pin "L1") (pinfunction "IN1_L1") (pintype "input"))
      (node (ref "EF37") (pin "BR1") (pinfunction "BR1_BR1") (pintype "input"))
      (node (ref "H04") (pin "T2") (pinfunction "P$2_T2") (pintype "bidirectional"))
    )
    (net (code "476") (name "MEM07") (class "Default")
      (node (ref "A08") (pin "T2") (pinfunction "8A_T2") (pintype "input"))
      (node (ref "B08") (pin "H2") (pinfunction "IN1_H2") (pintype "input"))
      (node (ref "EF37") (pin "BV2") (pinfunction "BV2_BV2") (pintype "input"))
      (node (ref "H04") (pin "V2") (pinfunction "P$2_V2") (pintype "bidirectional"))
    )
    (net (code "477") (name "MEM08") (class "Default")
      (node (ref "A07") (pin "P2") (pinfunction "1A_P2") (pintype "input"))
      (node (ref "B09") (pin "D1") (pinfunction "IN1_D1") (pintype "input"))
      (node (ref "EF38") (pin "BR1") (pinfunction "BR1_BR1") (pintype "input"))
      (node (ref "H05") (pin "D2") (pinfunction "P$2_D2") (pintype "bidirectional"))
    )
    (net (code "478") (name "MEM09") (class "Default")
      (node (ref "A07") (pin "R2") (pinfunction "2A_R2") (pintype "input"))
      (node (ref "B09") (pin "A1") (pinfunction "IN1_A1") (pintype "input"))
      (node (ref "D09") (pin "C1") (pinfunction "IN3_C1") (pintype "input"))
      (node (ref "EF38") (pin "BV2") (pinfunction "BV2_BV2") (pintype "input"))
      (node (ref "H05") (pin "E2") (pinfunction "P$2_E2") (pintype "bidirectional"))
    )
    (net (code "479") (name "MEM10") (class "Default")
      (node (ref "A07") (pin "S2") (pinfunction "4A_S2") (pintype "input"))
      (node (ref "B08") (pin "T2") (pinfunction "IN1_T2") (pintype "input"))
      (node (ref "EF39") (pin "BR1") (pinfunction "BR1_BR1") (pintype "input"))
      (node (ref "H05") (pin "H2") (pinfunction "P$2_H2") (pintype "bidirectional"))
    )
    (net (code "480") (name "MEM11") (class "Default")
      (node (ref "A07") (pin "T2") (pinfunction "8A_T2") (pintype "input"))
      (node (ref "B08") (pin "P2") (pinfunction "IN1_P2") (pintype "input"))
      (node (ref "EF39") (pin "BV2") (pinfunction "BV2_BV2") (pintype "input"))
      (node (ref "H05") (pin "K2") (pinfunction "P$2_K2") (pintype "bidirectional"))
    )
    (net (code "481") (name "MEMORY_INCREMENT") (class "Default")
      (node (ref "E11") (pin "U2") (pinfunction "IN2_U2") (pintype "input"))
      (node (ref "E27") (pin "R2") (pinfunction "IN4C_R2") (pintype "input"))
      (node (ref "J20") (pin "E1") (pinfunction "OUT_E1") (pintype "output"))
    )
    (net (code "482") (name "MEM_DONE_") (class "Default")
      (node (ref "B10") (pin "D2") (pinfunction "D2_D2") (pintype "open_collector"))
      (node (ref "C07") (pin "T2") (pinfunction "IN3_T2") (pintype "input"))
      (node (ref "E18") (pin "F2") (pinfunction "S_F2") (pintype "input"))
      (node (ref "E33") (pin "F2") (pinfunction "S_F2") (pintype "input"))
      (node (ref "H05") (pin "S2") (pinfunction "P$2_S2") (pintype "bidirectional"))
    )
    (net (code "483") (name "MEM_ENABLE0_4") (class "Default")
      (node (ref "EF34") (pin "BU2") (pinfunction "BU2_BU2") (pintype "input"))
      (node (ref "EF34") (pin "BV1") (pinfunction "BV1_BV1") (pintype "input"))
      (node (ref "EF35") (pin "BU2") (pinfunction "BU2_BU2") (pintype "input"))
      (node (ref "EF35") (pin "BV1") (pinfunction "BV1_BV1") (pintype "input"))
      (node (ref "EF36") (pin "BU2") (pinfunction "BU2_BU2") (pintype "input"))
      (node (ref "F27") (pin "R1") (pinfunction "IN4_R1") (pintype "input"))
      (node (ref "F29") (pin "A1") (pinfunction "IN1_A1") (pintype "input"))
      (node (ref "F31") (pin "E1") (pinfunction "OUT_E1") (pintype "open_collector"))
    )
    (net (code "484") (name "MEM_ENABLE0_4_") (class "Default")
      (node (ref "F28") (pin "E2") (pinfunction "IN2_E2") (pintype "input"))
      (node (ref "F29") (pin "C1") (pinfunction "OUT_C1") (pintype "output"))
      (node (ref "F31") (pin "F2") (pinfunction "IN3_F2") (pintype "input"))
    )
    (net (code "485") (name "MEM_ENABLE5_8") (class "Default")
      (node (ref "E09") (pin "H2") (pinfunction "IN1_H2") (pintype "input"))
      (node (ref "EF36") (pin "BV1") (pinfunction "BV1_BV1") (pintype "input"))
      (node (ref "EF37") (pin "BU2") (pinfunction "BU2_BU2") (pintype "input"))
      (node (ref "EF37") (pin "BV1") (pinfunction "BV1_BV1") (pintype "input"))
      (node (ref "EF38") (pin "BU2") (pinfunction "BU2_BU2") (pintype "input"))
      (node (ref "F28") (pin "D2") (pinfunction "IN1_D2") (pintype "input"))
      (node (ref "F31") (pin "J2") (pinfunction "OUT_J2") (pintype "open_collector"))
    )
    (net (code "486") (name "MEM_ENABLE9_11") (class "Default")
      (node (ref "EF38") (pin "BV1") (pinfunction "BV1_BV1") (pintype "input"))
      (node (ref "EF39") (pin "BU2") (pinfunction "BU2_BU2") (pintype "input"))
      (node (ref "EF39") (pin "BV1") (pinfunction "BV1_BV1") (pintype "input"))
      (node (ref "F11") (pin "P2") (pinfunction "OUT_P2") (pintype "output"))
    )
    (net (code "487") (name "MEM_EXT") (class "Default")
      (node (ref "A11") (pin "A1") (pinfunction "IN1_A1") (pintype "input"))
      (node (ref "A13") (pin "E2") (pinfunction "IN2_E2") (pintype "input"))
      (node (ref "A14") (pin "E2") (pinfunction "IN2_E2") (pintype "input"))
      (node (ref "A14") (pin "K1") (pinfunction "OUT_K1") (pintype "output"))
      (node (ref "A15") (pin "R2") (pinfunction "IN2_R2") (pintype "input"))
    )
    (net (code "488") (name "MEM_EXT_") (class "Default")
      (node (ref "A14") (pin "F1") (pinfunction "OUT_F1") (pintype "output"))
      (node (ref "A14") (pin "H1") (pinfunction "IN1_H1") (pintype "input"))
      (node (ref "F19") (pin "B1") (pinfunction "IN2_B1") (pintype "input"))
    )
    (net (code "489") (name "MEM_EXT_AC_LOAD_ENABLE_") (class "Default")
      (node (ref "A14") (pin "S2") (pinfunction "OUT_S2") (pintype "output"))
      (node (ref "E32") (pin "N2") (pinfunction "IN4_N2") (pintype "input"))
    )
    (net (code "490") (name "MEM_EXT_IO_ENABLE_") (class "Default")
      (node (ref "C12") (pin "J2") (pinfunction "OUT_J2") (pintype "open_collector"))
      (node (ref "F30") (pin "E2") (pinfunction "IN2_E2") (pintype "input"))
    )
    (net (code "491") (name "MEM_IDLE") (class "Default")
      (node (ref "E14") (pin "A1") (pinfunction "IN1_A1") (pintype "input"))
      (node (ref "E18") (pin "H2") (pinfunction "1_H2") (pintype "output"))
    )
    (net (code "492") (name "MEM_INH9_11_") (class "Default")
      (node (ref "C09") (pin "K2") (pinfunction "OUT_K2") (pintype "output"))
      (node (ref "D10") (pin "J1") (pinfunction "IN3_J1") (pintype "input"))
      (node (ref "E09") (pin "J2") (pinfunction "IN2_J2") (pintype "input"))
    )
    (net (code "493") (name "MEM_P") (class "Default")
      (node (ref "A08") (pin "J1") (pinfunction "8A_J1") (pintype "input"))
      (node (ref "B08") (pin "V1") (pinfunction "P$1_V1") (pintype "passive"))
      (node (ref "B09") (pin "E2") (pinfunction "IN2_E2") (pintype "input"))
      (node (ref "H04") (pin "D2") (pinfunction "P$2_D2") (pintype "bidirectional"))
    )
    (net (code "494") (name "MEM_PARITY_EVEN_") (class "Default")
      (node (ref "A08") (pin "L1") (pinfunction "EVEN_L1") (pintype "output"))
      (node (ref "B09") (pin "P1") (pinfunction "IN1_P1") (pintype "input"))
    )
    (net (code "495") (name "MEM_TO_LSR_") (class "Default")
      (node (ref "C08") (pin "P2") (pinfunction "IN2_P2") (pintype "input"))
      (node (ref "D07") (pin "K1") (pinfunction "OUT_K1") (pintype "output"))
    )
    (net (code "496") (name "MFTP0") (class "Default")
      (node (ref "EF10") (pin "AT2") (pinfunction "CT2_AT2") (pintype "output"))
      (node (ref "F20") (pin "T2") (pinfunction "IN1_T2") (pintype "input"))
      (node (ref "F30") (pin "U2") (pinfunction "IN4_U2") (pintype "input"))
    )
    (net (code "497") (name "MFTP1") (class "Default")
      (node (ref "A19") (pin "J2") (pinfunction "IN2_J2") (pintype "input"))
      (node (ref "E12") (pin "M2") (pinfunction "IN2_M2") (pintype "input"))
      (node (ref "EF10") (pin "AE2") (pinfunction "CE2_AE2") (pintype "output"))
      (node (ref "F32") (pin "D1") (pinfunction "IN1_D1") (pintype "input"))
    )
    (net (code "498") (name "MFTP2") (class "Default")
      (node (ref "E15") (pin "A1") (pinfunction "IN1_A1") (pintype "input"))
      (node (ref "E15") (pin "H1") (pinfunction "IN1_H1") (pintype "input"))
      (node (ref "E26") (pin "J2") (pinfunction "IN2A_J2") (pintype "input"))
      (node (ref "E26") (pin "K1") (pinfunction "IN4A_K1") (pintype "input"))
      (node (ref "E26") (pin "V1") (pinfunction "IN2A_V1") (pintype "input"))
      (node (ref "EF10") (pin "BD2") (pinfunction "DD2_BD2") (pintype "output"))
      (node (ref "F22") (pin "D2") (pinfunction "IN1_D2") (pintype "input"))
    )
    (net (code "499") (name "MFTS0") (class "Default")
      (node (ref "E13") (pin "J1") (pinfunction "IN3B_J1") (pintype "input"))
      (node (ref "E14") (pin "T2") (pinfunction "IN1_T2") (pintype "input"))
      (node (ref "EF10") (pin "AM2") (pinfunction "CM2_AM2") (pintype "output"))
      (node (ref "F29") (pin "R2") (pinfunction "IN2_R2") (pintype "input"))
    )
    (net (code "500") (name "MFTS1") (class "Default")
      (node (ref "E14") (pin "E2") (pinfunction "IN2_E2") (pintype "input"))
      (node (ref "EF10") (pin "AJ2") (pinfunction "CJ2_AJ2") (pintype "output"))
    )
    (net (code "501") (name "MFTS1_") (class "Default")
      (node (ref "E14") (pin "U2") (pinfunction "IN2_U2") (pintype "input"))
      (node (ref "EF10") (pin "AK2") (pinfunction "CK2_AK2") (pintype "output"))
    )
    (net (code "502") (name "MFTS2") (class "Default")
      (node (ref "E27") (pin "J2") (pinfunction "IN2A_J2") (pintype "input"))
      (node (ref "E28") (pin "E1") (pinfunction "IN2A_E1") (pintype "input"))
      (node (ref "E30") (pin "K1") (pinfunction "IN4A_K1") (pintype "input"))
      (node (ref "EF10") (pin "AF2") (pinfunction "CF2_AF2") (pintype "output"))
    )
    (net (code "503") (name "MFTS2_") (class "Default")
      (node (ref "D12") (pin "R1") (pinfunction "IN2_R1") (pintype "input"))
      (node (ref "E14") (pin "V2") (pinfunction "IN3_V2") (pintype "input"))
      (node (ref "EF10") (pin "AH2") (pinfunction "CH2_AH2") (pintype "output"))
    )
    (net (code "504") (name "MFTS3") (class "Default")
      (node (ref "E15") (pin "V2") (pinfunction "OUT_V2") (pintype "output"))
      (node (ref "E29") (pin "N2") (pinfunction "IN4A_N2") (pintype "input"))
      (node (ref "F29") (pin "R1") (pinfunction "IN2_R1") (pintype "input"))
    )
    (net (code "505") (name "MID_AC0") (class "Default")
      (node (ref "D19") (pin "M1") (pinfunction "IN3_M1") (pintype "input"))
      (node (ref "D20") (pin "B1") (pinfunction "IN2_B1") (pintype "input"))
      (node (ref "E24") (pin "S1") (pinfunction "OUT_S1") (pintype "output"))
      (node (ref "F23") (pin "B1") (pinfunction "IN2_B1") (pintype "input"))
    )
    (net (code "506") (name "MP_INT_") (class "Default")
      (node (ref "B07") (pin "L2") (pinfunction "IN3_L2") (pintype "input"))
      (node (ref "B11") (pin "P2") (pinfunction "1_P2") (pintype "output"))
      (node (ref "J15") (pin "H2") (pinfunction "IN4_H2") (pintype "input"))
    )
    (net (code "507") (name "MP_SKIP_") (class "Default")
      (node (ref "B07") (pin "M2") (pinfunction "OUT_M2") (pintype "output"))
      (node (ref "J15") (pin "D1") (pinfunction "IN4_D1") (pintype "input"))
    )
    (net (code "508") (name "MQ00") (class "Default")
      (node (ref "C14") (pin "J1") (pinfunction "IN2_J1") (pintype "input"))
      (node (ref "C23") (pin "E1") (pinfunction "1_E1") (pintype "output"))
      (node (ref "D18") (pin "S1") (pinfunction "IN3_S1") (pintype "input"))
      (node (ref "EF34") (pin "BH1") (pinfunction "BH1_BH1") (pintype "input"))
    )
    (net (code "509") (name "MQ00_") (class "Default")
      (node (ref "C23") (pin "F1") (pinfunction "0_F1") (pintype "output"))
      (node (ref "D18") (pin "N2") (pinfunction "IN1_N2") (pintype "input"))
      (node (ref "D21") (pin "K2") (pinfunction "IN1_K2") (pintype "input"))
      (node (ref "E40") (pin "S2") (pinfunction "P$2_S2") (pintype "bidirectional"))
    )
    (net (code "510") (name "MQ01") (class "Default")
      (node (ref "C14") (pin "E2") (pinfunction "IN2_E2") (pintype "input"))
      (node (ref "C14") (pin "M2") (pinfunction "IN2_M2") (pintype "input"))
      (node (ref "C23") (pin "H2") (pinfunction "1_H2") (pintype "output"))
      (node (ref "EF34") (pin "BN2") (pinfunction "BN2_BN2") (pintype "input"))
    )
    (net (code "511") (name "MQ01_") (class "Default")
      (node (ref "C23") (pin "J2") (pinfunction "0_J2") (pintype "output"))
      (node (ref "D21") (pin "L2") (pinfunction "IN2_L2") (pintype "input"))
      (node (ref "E40") (pin "M2") (pinfunction "P$2_M2") (pintype "bidirectional"))
    )
    (net (code "512") (name "MQ02") (class "Default")
      (node (ref "C14") (pin "M1") (pinfunction "IN2_M1") (pintype "input"))
      (node (ref "C15") (pin "B1") (pinfunction "IN2_B1") (pintype "input"))
      (node (ref "C23") (pin "L1") (pinfunction "1_L1") (pintype "output"))
      (node (ref "EF35") (pin "BH1") (pinfunction "BH1_BH1") (pintype "input"))
    )
    (net (code "513") (name "MQ02_") (class "Default")
      (node (ref "C23") (pin "M1") (pinfunction "0_M1") (pintype "output"))
      (node (ref "D21") (pin "M2") (pinfunction "IN3_M2") (pintype "input"))
      (node (ref "E40") (pin "N2") (pinfunction "P$2_N2") (pintype "bidirectional"))
    )
    (net (code "514") (name "MQ03") (class "Default")
      (node (ref "C14") (pin "R2") (pinfunction "IN2_R2") (pintype "input"))
      (node (ref "C15") (pin "J1") (pinfunction "IN2_J1") (pintype "input"))
      (node (ref "C23") (pin "P2") (pinfunction "1_P2") (pintype "output"))
      (node (ref "EF35") (pin "BN2") (pinfunction "BN2_BN2") (pintype "input"))
    )
    (net (code "515") (name "MQ03_") (class "Default")
      (node (ref "C23") (pin "R2") (pinfunction "0_R2") (pintype "output"))
      (node (ref "D21") (pin "N2") (pinfunction "IN4_N2") (pintype "input"))
      (node (ref "E40") (pin "L2") (pinfunction "P$2_L2") (pintype "bidirectional"))
    )
    (net (code "516") (name "MQ04") (class "Default")
      (node (ref "C15") (pin "E2") (pinfunction "IN2_E2") (pintype "input"))
      (node (ref "C15") (pin "M2") (pinfunction "IN2_M2") (pintype "input"))
      (node (ref "C23") (pin "S1") (pinfunction "1_S1") (pintype "output"))
      (node (ref "EF36") (pin "BH1") (pinfunction "BH1_BH1") (pintype "input"))
    )
    (net (code "517") (name "MQ04_") (class "Default")
      (node (ref "C23") (pin "U1") (pinfunction "0_U1") (pintype "output"))
      (node (ref "D21") (pin "M1") (pinfunction "IN1_M1") (pintype "input"))
      (node (ref "E40") (pin "F1") (pinfunction "P$2_F1") (pintype "bidirectional"))
    )
    (net (code "518") (name "MQ05") (class "Default")
      (node (ref "C15") (pin "M1") (pinfunction "IN2_M1") (pintype "input"))
      (node (ref "C16") (pin "B1") (pinfunction "IN2_B1") (pintype "input"))
      (node (ref "C23") (pin "V2") (pinfunction "1_V2") (pintype "output"))
      (node (ref "EF36") (pin "BN2") (pinfunction "BN2_BN2") (pintype "input"))
    )
    (net (code "519") (name "MQ05_") (class "Default")
      (node (ref "C23") (pin "V1") (pinfunction "0_V1") (pintype "output"))
      (node (ref "D21") (pin "N1") (pinfunction "IN2_N1") (pintype "input"))
      (node (ref "E40") (pin "H1") (pinfunction "P$2_H1") (pintype "bidirectional"))
    )
    (net (code "520") (name "MQ06") (class "Default")
      (node (ref "C15") (pin "R2") (pinfunction "IN2_R2") (pintype "input"))
      (node (ref "C16") (pin "J1") (pinfunction "IN2_J1") (pintype "input"))
      (node (ref "C24") (pin "E1") (pinfunction "1_E1") (pintype "output"))
      (node (ref "EF37") (pin "BH1") (pinfunction "BH1_BH1") (pintype "input"))
    )
    (net (code "521") (name "MQ06_") (class "Default")
      (node (ref "C24") (pin "F1") (pinfunction "0_F1") (pintype "output"))
      (node (ref "D21") (pin "P1") (pinfunction "IN3_P1") (pintype "input"))
      (node (ref "F40") (pin "S2") (pinfunction "P$2_S2") (pintype "bidirectional"))
    )
    (net (code "522") (name "MQ07") (class "Default")
      (node (ref "C16") (pin "E2") (pinfunction "IN2_E2") (pintype "input"))
      (node (ref "C16") (pin "M2") (pinfunction "IN2_M2") (pintype "input"))
      (node (ref "C24") (pin "H2") (pinfunction "1_H2") (pintype "output"))
      (node (ref "EF37") (pin "BN2") (pinfunction "BN2_BN2") (pintype "input"))
    )
    (net (code "523") (name "MQ07_") (class "Default")
      (node (ref "C24") (pin "J2") (pinfunction "0_J2") (pintype "output"))
      (node (ref "D21") (pin "R1") (pinfunction "IN4_R1") (pintype "input"))
      (node (ref "F40") (pin "M2") (pinfunction "P$2_M2") (pintype "bidirectional"))
    )
    (net (code "524") (name "MQ08") (class "Default")
      (node (ref "C16") (pin "M1") (pinfunction "IN2_M1") (pintype "input"))
      (node (ref "C17") (pin "B1") (pinfunction "IN2_B1") (pintype "input"))
      (node (ref "C24") (pin "L1") (pinfunction "1_L1") (pintype "output"))
      (node (ref "EF38") (pin "BH1") (pinfunction "BH1_BH1") (pintype "input"))
    )
    (net (code "525") (name "MQ08_") (class "Default")
      (node (ref "C24") (pin "M1") (pinfunction "0_M1") (pintype "output"))
      (node (ref "D21") (pin "R2") (pinfunction "IN1_R2") (pintype "input"))
      (node (ref "F40") (pin "N2") (pinfunction "P$2_N2") (pintype "bidirectional"))
    )
    (net (code "526") (name "MQ09") (class "Default")
      (node (ref "C16") (pin "R2") (pinfunction "IN2_R2") (pintype "input"))
      (node (ref "C17") (pin "J1") (pinfunction "IN2_J1") (pintype "input"))
      (node (ref "C24") (pin "P2") (pinfunction "1_P2") (pintype "output"))
      (node (ref "EF38") (pin "BN2") (pinfunction "BN2_BN2") (pintype "input"))
    )
    (net (code "527") (name "MQ09_") (class "Default")
      (node (ref "C24") (pin "R2") (pinfunction "0_R2") (pintype "output"))
      (node (ref "D21") (pin "S2") (pinfunction "IN2_S2") (pintype "input"))
      (node (ref "F40") (pin "L2") (pinfunction "P$2_L2") (pintype "bidirectional"))
    )
    (net (code "528") (name "MQ10") (class "Default")
      (node (ref "C17") (pin "E2") (pinfunction "IN2_E2") (pintype "input"))
      (node (ref "C17") (pin "M2") (pinfunction "IN2_M2") (pintype "input"))
      (node (ref "C24") (pin "S1") (pinfunction "1_S1") (pintype "output"))
      (node (ref "D13") (pin "D2") (pinfunction "IN1_D2") (pintype "input"))
      (node (ref "D23") (pin "V1") (pinfunction "IN2A_V1") (pintype "input"))
      (node (ref "EF39") (pin "BH1") (pinfunction "BH1_BH1") (pintype "input"))
    )
    (net (code "529") (name "MQ10_") (class "Default")
      (node (ref "C24") (pin "U1") (pinfunction "0_U1") (pintype "output"))
      (node (ref "D12") (pin "E2") (pinfunction "IN2_E2") (pintype "input"))
      (node (ref "D21") (pin "T2") (pinfunction "IN3_T2") (pintype "input"))
      (node (ref "F40") (pin "F1") (pinfunction "P$2_F1") (pintype "bidirectional"))
    )
    (net (code "530") (name "MQ11") (class "Default")
      (node (ref "C17") (pin "M1") (pinfunction "IN2_M1") (pintype "input"))
      (node (ref "C24") (pin "V2") (pinfunction "1_V2") (pintype "output"))
      (node (ref "D20") (pin "K2") (pinfunction "IN1_K2") (pintype "input"))
      (node (ref "D23") (pin "J2") (pinfunction "IN2A_J2") (pintype "input"))
      (node (ref "D23") (pin "U1") (pinfunction "IN1B_U1") (pintype "input"))
      (node (ref "EF39") (pin "BN2") (pinfunction "BN2_BN2") (pintype "input"))
    )
    (net (code "531") (name "MQ11_") (class "Default")
      (node (ref "C24") (pin "V1") (pinfunction "0_V1") (pintype "output"))
      (node (ref "D13") (pin "U2") (pinfunction "IN2_U2") (pintype "input"))
      (node (ref "D15") (pin "P2") (pinfunction "IN1_P2") (pintype "input"))
      (node (ref "D21") (pin "U2") (pinfunction "IN4_U2") (pintype "input"))
      (node (ref "D23") (pin "M2") (pinfunction "IN3B_M2") (pintype "input"))
      (node (ref "D23") (pin "U2") (pinfunction "IN2B_U2") (pintype "input"))
      (node (ref "F40") (pin "H1") (pinfunction "P$2_H1") (pintype "bidirectional"))
    )
    (net (code "532") (name "MQ_ENABLE") (class "Default")
      (node (ref "D22") (pin "L1") (pinfunction "OUT_L1") (pintype "open_collector"))
      (node (ref "EF34") (pin "BF1") (pinfunction "BF1_BF1") (pintype "input"))
      (node (ref "EF35") (pin "BF1") (pinfunction "BF1_BF1") (pintype "input"))
      (node (ref "EF36") (pin "BF1") (pinfunction "BF1_BF1") (pintype "input"))
      (node (ref "EF37") (pin "BF1") (pinfunction "BF1_BF1") (pintype "input"))
      (node (ref "EF38") (pin "BF1") (pinfunction "BF1_BF1") (pintype "input"))
      (node (ref "EF39") (pin "BF1") (pinfunction "BF1_BF1") (pintype "input"))
    )
    (net (code "533") (name "MQ_LOAD") (class "Default")
      (node (ref "C23") (pin "B1") (pinfunction "C_B1") (pintype "input"))
      (node (ref "C23") (pin "D2") (pinfunction "C_D2") (pintype "input"))
      (node (ref "C23") (pin "H1") (pinfunction "C_H1") (pintype "input"))
      (node (ref "C23") (pin "L2") (pinfunction "C_L2") (pintype "input"))
      (node (ref "C23") (pin "N1") (pinfunction "C_N1") (pintype "input"))
      (node (ref "C23") (pin "S2") (pinfunction "C_S2") (pintype "input"))
      (node (ref "C24") (pin "B1") (pinfunction "C_B1") (pintype "input"))
      (node (ref "C24") (pin "D2") (pinfunction "C_D2") (pintype "input"))
      (node (ref "C24") (pin "H1") (pinfunction "C_H1") (pintype "input"))
      (node (ref "C24") (pin "L2") (pinfunction "C_L2") (pintype "input"))
      (node (ref "C24") (pin "N1") (pinfunction "C_N1") (pintype "input"))
      (node (ref "C24") (pin "S2") (pinfunction "C_S2") (pintype "input"))
      (node (ref "D22") (pin "S1") (pinfunction "OUT_S1") (pintype "open_collector"))
    )
    (net (code "534") (name "MQ_LOW_AC0") (class "Default")
      (node (ref "D15") (pin "F2") (pinfunction "OUT_F2") (pintype "output"))
      (node (ref "D19") (pin "L1") (pinfunction "IN2_L1") (pintype "input"))
      (node (ref "D20") (pin "A1") (pinfunction "IN1_A1") (pintype "input"))
    )
    (net (code "535") (name "MUY") (class "Default")
      (node (ref "D15") (pin "R2") (pinfunction "IN2_R2") (pintype "input"))
      (node (ref "D16") (pin "S1") (pinfunction "OUT_S1") (pintype "output"))
      (node (ref "D23") (pin "A1") (pinfunction "IN1A_A1") (pintype "input"))
    )
    (net (code "536") (name "MUY_") (class "Default")
      (node (ref "D16") (pin "P1") (pinfunction "IN1_P1") (pintype "input"))
      (node (ref "D19") (pin "U1") (pinfunction "OUT_U1") (pintype "output"))
    )
    (net (code "537") (name "MUY_DVI_") (class "Default")
      (node (ref "D15") (pin "K1") (pinfunction "OUT_K1") (pintype "output"))
      (node (ref "D21") (pin "D2") (pinfunction "IN1_D2") (pintype "input"))
    )
    (net (code "538") (name "NMI") (class "Default")
      (node (ref "D14") (pin "M2") (pinfunction "IN2_M2") (pintype "input"))
      (node (ref "D14") (pin "U2") (pinfunction "IN2_U2") (pintype "input"))
      (node (ref "D16") (pin "V2") (pinfunction "OUT_V2") (pintype "output"))
      (node (ref "D23") (pin "N1") (pinfunction "IN5B_N1") (pintype "input"))
    )
    (net (code "539") (name "NMI_") (class "Default")
      (node (ref "D16") (pin "T2") (pinfunction "IN1_T2") (pintype "input"))
      (node (ref "D20") (pin "V2") (pinfunction "OUT_V2") (pintype "output"))
    )
    (net (code "540") (name "NORM") (class "Default")
      (node (ref "C18") (pin "J2") (pinfunction "IN2_J2") (pintype "input"))
      (node (ref "D17") (pin "H2") (pinfunction "OUT_H2") (pintype "output"))
    )
    (net (code "541") (name "NORM_") (class "Default")
      (node (ref "C18") (pin "K2") (pinfunction "OUT_K2") (pintype "output"))
      (node (ref "D14") (pin "L2") (pinfunction "IN1_L2") (pintype "input"))
    )
    (net (code "542") (name "NO_SHIFT") (class "Default")
      (node (ref "E31") (pin "S1") (pinfunction "OUT_S1") (pintype "open_collector"))
      (node (ref "EF34") (pin "AE1") (pinfunction "AE1_AE1") (pintype "input"))
      (node (ref "EF35") (pin "AE1") (pinfunction "AE1_AE1") (pintype "input"))
      (node (ref "EF36") (pin "AE1") (pinfunction "AE1_AE1") (pintype "input"))
      (node (ref "EF37") (pin "AE1") (pinfunction "AE1_AE1") (pintype "input"))
      (node (ref "EF38") (pin "AE1") (pinfunction "AE1_AE1") (pintype "input"))
      (node (ref "EF39") (pin "AE1") (pinfunction "AE1_AE1") (pintype "input"))
      (node (ref "F33") (pin "J1") (pinfunction "IN3B_J1") (pintype "input"))
    )
    (net (code "543") (name "Net-(A05A-OUT)") (class "Default")
      (node (ref "A05") (pin "C1") (pinfunction "OUT_C1") (pintype "output"))
      (node (ref "A05") (pin "E2") (pinfunction "IN2_E2") (pintype "input"))
    )
    (net (code "544") (name "Net-(A05B-IN2)") (class "Default")
      (node (ref "A05") (pin "E1") (pinfunction "IN2_E1") (pintype "input"))
      (node (ref "B04") (pin "H2") (pinfunction "OUT_H2") (pintype "output"))
    )
    (net (code "545") (name "Net-(A05B-OUT)") (class "Default")
      (node (ref "A05") (pin "D2") (pinfunction "IN1_D2") (pintype "input"))
      (node (ref "A05") (pin "F1") (pinfunction "OUT_F1") (pintype "output"))
    )
    (net (code "546") (name "Net-(A05C-OUT)") (class "Default")
      (node (ref "A05") (pin "F2") (pinfunction "OUT_F2") (pintype "output"))
      (node (ref "A05") (pin "H1") (pinfunction "IN1_H1") (pintype "input"))
    )
    (net (code "547") (name "Net-(A05F-OUT)") (class "Default")
      (node (ref "A05") (pin "K1") (pinfunction "OUT_K1") (pintype "output"))
      (node (ref "A05") (pin "L1") (pinfunction "IN1_L1") (pintype "input"))
    )
    (net (code "548") (name "Net-(A05H-OUT)") (class "Default")
      (node (ref "A05") (pin "N1") (pinfunction "OUT_N1") (pintype "output"))
      (node (ref "A05") (pin "R1") (pinfunction "IN2_R1") (pintype "input"))
      (node (ref "B04") (pin "P1") (pinfunction "IN1_P1") (pintype "input"))
      (node (ref "B04") (pin "R1") (pinfunction "IN2_R1") (pintype "input"))
    )
    (net (code "549") (name "Net-(A05I-OUT)") (class "Default")
      (node (ref "A05") (pin "N2") (pinfunction "OUT_N2") (pintype "output"))
      (node (ref "A05") (pin "P1") (pinfunction "IN1_P1") (pintype "input"))
    )
    (net (code "550") (name "Net-(A05J-OUT)") (class "Default")
      (node (ref "A05") (pin "S1") (pinfunction "OUT_S1") (pintype "output"))
      (node (ref "B05") (pin "M2") (pinfunction "D_M2") (pintype "input"))
    )
    (net (code "551") (name "Net-(A05K-IN1)") (class "Default")
      (node (ref "A05") (pin "P2") (pinfunction "IN1_P2") (pintype "input"))
      (node (ref "A05") (pin "R2") (pinfunction "IN2_R2") (pintype "input"))
      (node (ref "B04") (pin "U1") (pinfunction "OUT_U1") (pintype "output"))
    )
    (net (code "552") (name "Net-(A05N-IN2)") (class "Default")
      (node (ref "A05") (pin "U2") (pinfunction "IN2_U2") (pintype "input"))
      (node (ref "B04") (pin "J1") (pinfunction "OUT_J1") (pintype "output"))
    )
    (net (code "553") (name "Net-(A06C-OUT)") (class "Default")
      (node (ref "A06") (pin "F2") (pinfunction "OUT_F2") (pintype "output"))
      (node (ref "A06") (pin "H1") (pinfunction "IN1_H1") (pintype "input"))
    )
    (net (code "554") (name "Net-(A06F-OUT)") (class "Default")
      (node (ref "A06") (pin "K1") (pinfunction "OUT_K1") (pintype "output"))
      (node (ref "F30") (pin "N1") (pinfunction "IN2_N1") (pintype "input"))
    )
    (net (code "555") (name "Net-(A06H-IN1)") (class "Default")
      (node (ref "A06") (pin "L1") (pinfunction "IN1_L1") (pintype "input"))
      (node (ref "F09") (pin "J2") (pinfunction "OUT_J2") (pintype "output"))
    )
    (net (code "556") (name "Net-(A06I-IN1)") (class "Default")
      (node (ref "A06") (pin "L2") (pinfunction "IN1_L2") (pintype "input"))
      (node (ref "A15") (pin "V2") (pinfunction "OUT_V2") (pintype "output"))
    )
    (net (code "557") (name "Net-(A06J-OUT)") (class "Default")
      (node (ref "A06") (pin "P2") (pinfunction "IN1_P2") (pintype "input"))
      (node (ref "A06") (pin "S1") (pinfunction "OUT_S1") (pintype "output"))
    )
    (net (code "558") (name "Net-(A06K-OUT)") (class "Default")
      (node (ref "A06") (pin "S2") (pinfunction "OUT_S2") (pintype "output"))
      (node (ref "A06") (pin "T2") (pinfunction "IN1_T2") (pintype "input"))
    )
    (net (code "559") (name "Net-(A07C-1B)") (class "Default")
      (node (ref "A07") (pin "A1") (pinfunction "1B_A1") (pintype "input"))
      (node (ref "B08") (pin "K1") (pinfunction "OUT_K1") (pintype "output"))
    )
    (net (code "560") (name "Net-(A07C-2B)") (class "Default")
      (node (ref "A07") (pin "B1") (pinfunction "2B_B1") (pintype "input"))
      (node (ref "B08") (pin "F2") (pinfunction "OUT_F2") (pintype "output"))
    )
    (net (code "561") (name "Net-(A07C-4B)") (class "Default")
      (node (ref "A07") (pin "C1") (pinfunction "4B_C1") (pintype "input"))
      (node (ref "B08") (pin "F1") (pinfunction "OUT_F1") (pintype "output"))
    )
    (net (code "562") (name "Net-(A07C-8B)") (class "Default")
      (node (ref "A07") (pin "D1") (pinfunction "8B_D1") (pintype "input"))
      (node (ref "B08") (pin "C1") (pinfunction "OUT_C1") (pintype "output"))
    )
    (net (code "563") (name "Net-(A07C-EVEN)") (class "Default")
      (node (ref "A07") (pin "L1") (pinfunction "EVEN_L1") (pintype "output"))
      (node (ref "A08") (pin "A1") (pinfunction "1B_A1") (pintype "input"))
    )
    (net (code "564") (name "Net-(A07C-ODD)") (class "Default")
      (node (ref "A07") (pin "K1") (pinfunction "ODD_K1") (pintype "output"))
      (node (ref "A08") (pin "E1") (pinfunction "1A_E1") (pintype "input"))
    )
    (net (code "565") (name "Net-(A07D-1B)") (class "Default")
      (node (ref "A07") (pin "K2") (pinfunction "1B_K2") (pintype "input"))
      (node (ref "B09") (pin "F1") (pinfunction "OUT_F1") (pintype "output"))
    )
    (net (code "566") (name "Net-(A07D-2B)") (class "Default")
      (node (ref "A07") (pin "L2") (pinfunction "2B_L2") (pintype "input"))
      (node (ref "B09") (pin "C1") (pinfunction "OUT_C1") (pintype "output"))
    )
    (net (code "567") (name "Net-(A07D-4B)") (class "Default")
      (node (ref "A07") (pin "M2") (pinfunction "4B_M2") (pintype "input"))
      (node (ref "B08") (pin "V2") (pinfunction "OUT_V2") (pintype "output"))
    )
    (net (code "568") (name "Net-(A07D-8B)") (class "Default")
      (node (ref "A07") (pin "N2") (pinfunction "8B_N2") (pintype "input"))
      (node (ref "B08") (pin "S2") (pinfunction "OUT_S2") (pintype "output"))
    )
    (net (code "569") (name "Net-(A07D-EVEN)") (class "Default")
      (node (ref "A07") (pin "V2") (pinfunction "EVEN_V2") (pintype "output"))
      (node (ref "A08") (pin "C1") (pinfunction "4B_C1") (pintype "input"))
    )
    (net (code "570") (name "Net-(A07D-ODD)") (class "Default")
      (node (ref "A07") (pin "U2") (pinfunction "ODD_U2") (pintype "output"))
      (node (ref "A08") (pin "H1") (pinfunction "4A_H1") (pintype "input"))
    )
    (net (code "571") (name "Net-(A08C-2A)") (class "Default")
      (node (ref "A08") (pin "F1") (pinfunction "2A_F1") (pintype "input"))
      (node (ref "A08") (pin "U2") (pinfunction "ODD_U2") (pintype "output"))
    )
    (net (code "572") (name "Net-(A08C-2B)") (class "Default")
      (node (ref "A08") (pin "B1") (pinfunction "2B_B1") (pintype "input"))
      (node (ref "A08") (pin "V2") (pinfunction "EVEN_V2") (pintype "output"))
    )
    (net (code "573") (name "Net-(A08C-8B)") (class "Default")
      (node (ref "A08") (pin "D1") (pinfunction "8B_D1") (pintype "input"))
      (node (ref "B09") (pin "F2") (pinfunction "OUT_F2") (pintype "output"))
    )
    (net (code "574") (name "Net-(A08D-1B)") (class "Default")
      (node (ref "A08") (pin "K2") (pinfunction "1B_K2") (pintype "input"))
      (node (ref "B08") (pin "S1") (pinfunction "OUT_S1") (pintype "output"))
    )
    (net (code "575") (name "Net-(A08D-2B)") (class "Default")
      (node (ref "A08") (pin "L2") (pinfunction "2B_L2") (pintype "input"))
      (node (ref "B08") (pin "N2") (pinfunction "OUT_N2") (pintype "output"))
    )
    (net (code "576") (name "Net-(A08D-4B)") (class "Default")
      (node (ref "A08") (pin "M2") (pinfunction "4B_M2") (pintype "input"))
      (node (ref "B08") (pin "N1") (pinfunction "OUT_N1") (pintype "output"))
    )
    (net (code "577") (name "Net-(A08D-8B)") (class "Default")
      (node (ref "A08") (pin "N2") (pinfunction "8B_N2") (pintype "input"))
      (node (ref "B08") (pin "K2") (pinfunction "OUT_K2") (pintype "output"))
    )
    (net (code "578") (name "Net-(A09C-EVEN)") (class "Default")
      (node (ref "A09") (pin "L1") (pinfunction "EVEN_L1") (pintype "output"))
      (node (ref "A10") (pin "A1") (pinfunction "1B_A1") (pintype "input"))
    )
    (net (code "579") (name "Net-(A09C-ODD)") (class "Default")
      (node (ref "A09") (pin "K1") (pinfunction "ODD_K1") (pintype "output"))
      (node (ref "A10") (pin "E1") (pinfunction "1A_E1") (pintype "input"))
    )
    (net (code "580") (name "Net-(A09D-EVEN)") (class "Default")
      (node (ref "A09") (pin "V2") (pinfunction "EVEN_V2") (pintype "output"))
      (node (ref "A10") (pin "C1") (pinfunction "4B_C1") (pintype "input"))
    )
    (net (code "581") (name "Net-(A09D-ODD)") (class "Default")
      (node (ref "A09") (pin "U2") (pinfunction "ODD_U2") (pintype "output"))
      (node (ref "A10") (pin "H1") (pinfunction "4A_H1") (pintype "input"))
    )
    (net (code "582") (name "Net-(A10C-2A)") (class "Default")
      (node (ref "A10") (pin "F1") (pinfunction "2A_F1") (pintype "input"))
      (node (ref "A10") (pin "U2") (pinfunction "ODD_U2") (pintype "output"))
    )
    (net (code "583") (name "Net-(A10C-2B)") (class "Default")
      (node (ref "A10") (pin "B1") (pinfunction "2B_B1") (pintype "input"))
      (node (ref "A10") (pin "V2") (pinfunction "EVEN_V2") (pintype "output"))
    )
    (net (code "584") (name "Net-(A11A-OUT)") (class "Default")
      (node (ref "A11") (pin "C1") (pinfunction "OUT_C1") (pintype "output"))
      (node (ref "A13") (pin "J1") (pinfunction "IN2_J1") (pintype "input"))
    )
    (net (code "585") (name "Net-(A11B-IN1)") (class "Default")
      (node (ref "A11") (pin "D1") (pinfunction "IN1_D1") (pintype "input"))
      (node (ref "A11") (pin "H2") (pinfunction "IN1_H2") (pintype "input"))
      (node (ref "A11") (pin "P1") (pinfunction "IN1_P1") (pintype "input"))
      (node (ref "A14") (pin "N1") (pinfunction "OUT_N1") (pintype "output"))
    )
    (net (code "586") (name "Net-(A11B-OUT)") (class "Default")
      (node (ref "A11") (pin "F1") (pinfunction "OUT_F1") (pintype "output"))
      (node (ref "A20") (pin "D2") (pinfunction "IN1_D2") (pintype "input"))
    )
    (net (code "587") (name "Net-(A11C-OUT)") (class "Default")
      (node (ref "A11") (pin "F2") (pinfunction "OUT_F2") (pintype "output"))
      (node (ref "A20") (pin "E2") (pinfunction "IN2_E2") (pintype "input"))
    )
    (net (code "588") (name "Net-(A11F-IN1)") (class "Default")
      (node (ref "A11") (pin "H1") (pinfunction "IN1_H1") (pintype "input"))
      (node (ref "A11") (pin "L2") (pinfunction "IN1_L2") (pintype "input"))
      (node (ref "A11") (pin "T2") (pinfunction "IN1_T2") (pintype "input"))
      (node (ref "A14") (pin "S1") (pinfunction "OUT_S1") (pintype "output"))
    )
    (net (code "589") (name "Net-(A11F-OUT)") (class "Default")
      (node (ref "A11") (pin "K1") (pinfunction "OUT_K1") (pintype "output"))
      (node (ref "A20") (pin "F2") (pinfunction "IN3_F2") (pintype "input"))
    )
    (net (code "590") (name "Net-(A11G-OUT)") (class "Default")
      (node (ref "A11") (pin "K2") (pinfunction "OUT_K2") (pintype "output"))
      (node (ref "A20") (pin "E1") (pinfunction "IN1_E1") (pintype "input"))
    )
    (net (code "591") (name "Net-(A11H-OUT)") (class "Default")
      (node (ref "A11") (pin "N1") (pinfunction "OUT_N1") (pintype "output"))
      (node (ref "A20") (pin "F1") (pinfunction "IN2_F1") (pintype "input"))
    )
    (net (code "592") (name "Net-(A11I-OUT)") (class "Default")
      (node (ref "A11") (pin "N2") (pinfunction "OUT_N2") (pintype "output"))
      (node (ref "A20") (pin "H1") (pinfunction "IN3_H1") (pintype "input"))
    )
    (net (code "593") (name "Net-(A11J-OUT)") (class "Default")
      (node (ref "A11") (pin "S1") (pinfunction "OUT_S1") (pintype "output"))
      (node (ref "A20") (pin "J2") (pinfunction "IN1_J2") (pintype "input"))
    )
    (net (code "594") (name "Net-(A11K-OUT)") (class "Default")
      (node (ref "A11") (pin "S2") (pinfunction "OUT_S2") (pintype "output"))
      (node (ref "A20") (pin "K2") (pinfunction "IN2_K2") (pintype "input"))
    )
    (net (code "595") (name "Net-(A11N-OUT)") (class "Default")
      (node (ref "A11") (pin "V2") (pinfunction "OUT_V2") (pintype "output"))
      (node (ref "A20") (pin "L2") (pinfunction "IN3_L2") (pintype "input"))
    )
    (net (code "596") (name "Net-(A12A-OUT)") (class "Default")
      (node (ref "A12") (pin "C1") (pinfunction "OUT_C1") (pintype "output"))
      (node (ref "F11") (pin "D2") (pinfunction "IN1_D2") (pintype "input"))
      (node (ref "F11") (pin "E2") (pinfunction "IN2_E2") (pintype "input"))
    )
    (net (code "597") (name "Net-(A12B-OUT)") (class "Default")
      (node (ref "A12") (pin "F1") (pinfunction "OUT_F1") (pintype "output"))
      (node (ref "B20") (pin "N2") (pinfunction "IN1_N2") (pintype "input"))
    )
    (net (code "598") (name "Net-(A12C-IN1)") (class "Default")
      (node (ref "A12") (pin "D2") (pinfunction "IN1_D2") (pintype "input"))
      (node (ref "A12") (pin "L1") (pinfunction "IN1_L1") (pintype "input"))
      (node (ref "A12") (pin "P2") (pinfunction "IN1_P2") (pintype "input"))
      (node (ref "A13") (pin "K1") (pinfunction "OUT_K1") (pintype "output"))
    )
    (net (code "599") (name "Net-(A12C-OUT)") (class "Default")
      (node (ref "A12") (pin "F2") (pinfunction "OUT_F2") (pintype "output"))
      (node (ref "B20") (pin "P2") (pinfunction "IN2_P2") (pintype "input"))
    )
    (net (code "600") (name "Net-(A12F-OUT)") (class "Default")
      (node (ref "A12") (pin "K1") (pinfunction "OUT_K1") (pintype "output"))
      (node (ref "B20") (pin "R2") (pinfunction "IN3_R2") (pintype "input"))
    )
    (net (code "601") (name "Net-(A12G-OUT)") (class "Default")
      (node (ref "A12") (pin "K2") (pinfunction "OUT_K2") (pintype "output"))
      (node (ref "B20") (pin "P1") (pinfunction "IN1_P1") (pintype "input"))
    )
    (net (code "602") (name "Net-(A12H-OUT)") (class "Default")
      (node (ref "A12") (pin "N1") (pinfunction "OUT_N1") (pintype "output"))
      (node (ref "B20") (pin "R1") (pinfunction "IN2_R1") (pintype "input"))
    )
    (net (code "603") (name "Net-(A12I-OUT)") (class "Default")
      (node (ref "A12") (pin "N2") (pinfunction "OUT_N2") (pintype "output"))
      (node (ref "B20") (pin "S1") (pinfunction "IN3_S1") (pintype "input"))
    )
    (net (code "604") (name "Net-(A12J-OUT)") (class "Default")
      (node (ref "A12") (pin "S1") (pinfunction "OUT_S1") (pintype "output"))
      (node (ref "B20") (pin "T2") (pinfunction "IN1_T2") (pintype "input"))
    )
    (net (code "605") (name "Net-(A12K-OUT)") (class "Default")
      (node (ref "A12") (pin "S2") (pinfunction "OUT_S2") (pintype "output"))
      (node (ref "B20") (pin "U2") (pinfunction "IN2_U2") (pintype "input"))
    )
    (net (code "606") (name "Net-(A12N-OUT)") (class "Default")
      (node (ref "A12") (pin "V2") (pinfunction "OUT_V2") (pintype "output"))
      (node (ref "B20") (pin "V2") (pinfunction "IN3_V2") (pintype "input"))
    )
    (net (code "607") (name "Net-(A13A-OUT)") (class "Default")
      (node (ref "A13") (pin "C1") (pinfunction "OUT_C1") (pintype "output"))
      (node (ref "A17") (pin "T2") (pinfunction "IN1_T2") (pintype "input"))
    )
    (net (code "608") (name "Net-(A13B-IN1)") (class "Default")
      (node (ref "A13") (pin "D1") (pinfunction "IN1_D1") (pintype "input"))
      (node (ref "A13") (pin "F2") (pinfunction "OUT_F2") (pintype "output"))
    )
    (net (code "609") (name "Net-(A13H-IN1)") (class "Default")
      (node (ref "A13") (pin "L1") (pinfunction "IN1_L1") (pintype "input"))
      (node (ref "A20") (pin "H2") (pinfunction "OUT_H2") (pintype "output"))
    )
    (net (code "610") (name "Net-(A13J-IN1)") (class "Default")
      (node (ref "A13") (pin "P1") (pinfunction "IN1_P1") (pintype "input"))
      (node (ref "A20") (pin "J1") (pinfunction "OUT_J1") (pintype "output"))
    )
    (net (code "611") (name "Net-(A13N-IN1)") (class "Default")
      (node (ref "A13") (pin "T2") (pinfunction "IN1_T2") (pintype "input"))
      (node (ref "A20") (pin "M2") (pinfunction "OUT_M2") (pintype "output"))
    )
    (net (code "612") (name "Net-(A14A-IN1)") (class "Default")
      (node (ref "A14") (pin "A1") (pinfunction "IN1_A1") (pintype "input"))
      (node (ref "B16") (pin "P2") (pinfunction "OUT_P2") (pintype "open_collector"))
    )
    (net (code "613") (name "Net-(A14A-OUT)") (class "Default")
      (node (ref "A14") (pin "C1") (pinfunction "OUT_C1") (pintype "output"))
      (node (ref "A14") (pin "D1") (pinfunction "IN1_D1") (pintype "input"))
    )
    (net (code "614") (name "Net-(A14C-OUT)") (class "Default")
      (node (ref "A14") (pin "F2") (pinfunction "OUT_F2") (pintype "output"))
      (node (ref "A14") (pin "J2") (pinfunction "IN2_J2") (pintype "input"))
    )
    (net (code "615") (name "Net-(A14H-IN2)") (class "Default")
      (node (ref "A14") (pin "M1") (pinfunction "IN2_M1") (pintype "input"))
      (node (ref "A20") (pin "N1") (pinfunction "OUT_N1") (pintype "output"))
      (node (ref "A20") (pin "T2") (pinfunction "IN1_T2") (pintype "input"))
    )
    (net (code "616") (name "Net-(A14I-IN2)") (class "Default")
      (node (ref "A14") (pin "M2") (pinfunction "IN2_M2") (pintype "input"))
      (node (ref "A20") (pin "S2") (pinfunction "OUT_S2") (pintype "output"))
      (node (ref "A20") (pin "U2") (pinfunction "IN2_U2") (pintype "input"))
    )
    (net (code "617") (name "Net-(A14J-IN2)") (class "Default")
      (node (ref "A14") (pin "R1") (pinfunction "IN2_R1") (pintype "input"))
      (node (ref "A20") (pin "U1") (pinfunction "OUT_U1") (pintype "output"))
      (node (ref "A20") (pin "V2") (pinfunction "IN3_V2") (pintype "input"))
    )
    (net (code "618") (name "Net-(A14K-IN2)") (class "Default")
      (node (ref "A14") (pin "R2") (pinfunction "IN2_R2") (pintype "input"))
      (node (ref "A20") (pin "V1") (pinfunction "OUT_V1") (pintype "output"))
      (node (ref "C12") (pin "D2") (pinfunction "IN1_D2") (pintype "input"))
    )
    (net (code "619") (name "Net-(A15A-OUT)") (class "Default")
      (node (ref "A15") (pin "C1") (pinfunction "OUT_C1") (pintype "output"))
      (node (ref "B11") (pin "R1") (pinfunction "S_R1") (pintype "input"))
    )
    (net (code "620") (name "Net-(A15F-IN2)") (class "Default")
      (node (ref "A15") (pin "J1") (pinfunction "IN2_J1") (pintype "input"))
      (node (ref "A19") (pin "V2") (pinfunction "OUT_V2") (pintype "output"))
    )
    (net (code "621") (name "Net-(A15G-IN2)") (class "Default")
      (node (ref "A15") (pin "J2") (pinfunction "IN2_J2") (pintype "input"))
      (node (ref "A15") (pin "N1") (pinfunction "OUT_N1") (pintype "output"))
    )
    (net (code "622") (name "Net-(A15G-OUT)") (class "Default")
      (node (ref "A15") (pin "K2") (pinfunction "OUT_K2") (pintype "output"))
      (node (ref "A18") (pin "B1") (pinfunction "IN2_B1") (pintype "input"))
    )
    (net (code "623") (name "Net-(A15J-IN2)") (class "Default")
      (node (ref "A15") (pin "R1") (pinfunction "IN2_R1") (pintype "input"))
      (node (ref "A15") (pin "S2") (pinfunction "OUT_S2") (pintype "output"))
    )
    (net (code "624") (name "Net-(A16A-OUT)") (class "Default")
      (node (ref "A16") (pin "C1") (pinfunction "OUT_C1") (pintype "output"))
      (node (ref "B16") (pin "A1") (pinfunction "IN1_A1") (pintype "input"))
    )
    (net (code "625") (name "Net-(A16B-OUT)") (class "Default")
      (node (ref "A16") (pin "F1") (pinfunction "OUT_F1") (pintype "output"))
      (node (ref "B16") (pin "B1") (pinfunction "IN2_B1") (pintype "input"))
    )
    (net (code "626") (name "Net-(A16C-OUT)") (class "Default")
      (node (ref "A16") (pin "F2") (pinfunction "OUT_F2") (pintype "output"))
      (node (ref "B16") (pin "C1") (pinfunction "IN3_C1") (pintype "input"))
    )
    (net (code "627") (name "Net-(A16F-OUT)") (class "Default")
      (node (ref "A16") (pin "K1") (pinfunction "OUT_K1") (pintype "output"))
      (node (ref "B16") (pin "D2") (pinfunction "IN1_D2") (pintype "input"))
    )
    (net (code "628") (name "Net-(A16G-OUT)") (class "Default")
      (node (ref "A16") (pin "K2") (pinfunction "OUT_K2") (pintype "output"))
      (node (ref "B16") (pin "E2") (pinfunction "IN2_E2") (pintype "input"))
    )
    (net (code "629") (name "Net-(A16H-OUT)") (class "Default")
      (node (ref "A16") (pin "N1") (pinfunction "OUT_N1") (pintype "output"))
      (node (ref "B16") (pin "F2") (pinfunction "IN3_F2") (pintype "input"))
    )
    (net (code "630") (name "Net-(A16I-OUT)") (class "Default")
      (node (ref "A16") (pin "N2") (pinfunction "OUT_N2") (pintype "output"))
      (node (ref "B16") (pin "F1") (pinfunction "IN1_F1") (pintype "input"))
    )
    (net (code "631") (name "Net-(A16J-OUT)") (class "Default")
      (node (ref "A16") (pin "S1") (pinfunction "OUT_S1") (pintype "output"))
      (node (ref "B16") (pin "H1") (pinfunction "IN2_H1") (pintype "input"))
    )
    (net (code "632") (name "Net-(A16K-OUT)") (class "Default")
      (node (ref "A16") (pin "S2") (pinfunction "OUT_S2") (pintype "output"))
      (node (ref "B16") (pin "J1") (pinfunction "IN3_J1") (pintype "input"))
    )
    (net (code "633") (name "Net-(A16N-OUT)") (class "Default")
      (node (ref "A16") (pin "V2") (pinfunction "OUT_V2") (pintype "output"))
      (node (ref "A20") (pin "A1") (pinfunction "IN1_A1") (pintype "input"))
    )
    (net (code "634") (name "Net-(A17A-IN2)") (class "Default")
      (node (ref "A17") (pin "B1") (pinfunction "IN2_B1") (pintype "input"))
      (node (ref "A20") (pin "D1") (pinfunction "OUT_D1") (pintype "output"))
    )
    (net (code "635") (name "Net-(A17B-OUT)") (class "Default")
      (node (ref "A17") (pin "F1") (pinfunction "OUT_F1") (pintype "output"))
      (node (ref "A20") (pin "C1") (pinfunction "IN3_C1") (pintype "input"))
    )
    (net (code "636") (name "Net-(A17C-IN1)") (class "Default")
      (node (ref "A17") (pin "D2") (pinfunction "IN1_D2") (pintype "input"))
      (node (ref "A18") (pin "F1") (pinfunction "OUT_F1") (pintype "output"))
      (node (ref "B20") (pin "E1") (pinfunction "IN1_E1") (pintype "input"))
    )
    (net (code "637") (name "Net-(A17C-IN2)") (class "Default")
      (node (ref "A17") (pin "E2") (pinfunction "IN2_E2") (pintype "input"))
      (node (ref "A17") (pin "K1") (pinfunction "OUT_K1") (pintype "output"))
    )
    (net (code "638") (name "Net-(A17C-OUT)") (class "Default")
      (node (ref "A17") (pin "F2") (pinfunction "OUT_F2") (pintype "output"))
      (node (ref "B17") (pin "C1") (pinfunction "D_C1") (pintype "input"))
    )
    (net (code "639") (name "Net-(A17G-IN1)") (class "Default")
      (node (ref "A17") (pin "H2") (pinfunction "IN1_H2") (pintype "input"))
      (node (ref "A18") (pin "K2") (pinfunction "OUT_K2") (pintype "output"))
      (node (ref "B20") (pin "J2") (pinfunction "IN1_J2") (pintype "input"))
    )
    (net (code "640") (name "Net-(A17G-IN2)") (class "Default")
      (node (ref "A17") (pin "J2") (pinfunction "IN2_J2") (pintype "input"))
      (node (ref "A17") (pin "N1") (pinfunction "OUT_N1") (pintype "output"))
    )
    (net (code "641") (name "Net-(A17G-OUT)") (class "Default")
      (node (ref "A17") (pin "K2") (pinfunction "OUT_K2") (pintype "output"))
      (node (ref "B17") (pin "E2") (pinfunction "D_E2") (pintype "input"))
    )
    (net (code "642") (name "Net-(A17I-IN1)") (class "Default")
      (node (ref "A17") (pin "L2") (pinfunction "IN1_L2") (pintype "input"))
      (node (ref "A18") (pin "S1") (pinfunction "OUT_S1") (pintype "output"))
      (node (ref "B20") (pin "K1") (pinfunction "IN1_K1") (pintype "input"))
    )
    (net (code "643") (name "Net-(A17I-IN2)") (class "Default")
      (node (ref "A17") (pin "M2") (pinfunction "IN2_M2") (pintype "input"))
      (node (ref "A17") (pin "S1") (pinfunction "OUT_S1") (pintype "output"))
    )
    (net (code "644") (name "Net-(A17I-OUT)") (class "Default")
      (node (ref "A17") (pin "N2") (pinfunction "OUT_N2") (pintype "output"))
      (node (ref "B17") (pin "J1") (pinfunction "D_J1") (pintype "input"))
    )
    (net (code "645") (name "Net-(A17K-IN1)") (class "Default")
      (node (ref "A17") (pin "P2") (pinfunction "IN1_P2") (pintype "input"))
      (node (ref "A17") (pin "V2") (pinfunction "OUT_V2") (pintype "output"))
    )
    (net (code "646") (name "Net-(A17K-OUT)") (class "Default")
      (node (ref "A17") (pin "S2") (pinfunction "OUT_S2") (pintype "output"))
      (node (ref "B18") (pin "B1") (pinfunction "C_B1") (pintype "input"))
      (node (ref "B18") (pin "D2") (pinfunction "C_D2") (pintype "input"))
      (node (ref "B18") (pin "H1") (pinfunction "C_H1") (pintype "input"))
    )
    (net (code "647") (name "Net-(A18C-OUT)") (class "Default")
      (node (ref "A18") (pin "F2") (pinfunction "OUT_F2") (pintype "output"))
      (node (ref "B20") (pin "F1") (pinfunction "IN2_F1") (pintype "input"))
    )
    (net (code "648") (name "Net-(A18F-OUT)") (class "Default")
      (node (ref "A18") (pin "K1") (pinfunction "OUT_K1") (pintype "output"))
      (node (ref "B20") (pin "H1") (pinfunction "IN3_H1") (pintype "input"))
    )
    (net (code "649") (name "Net-(A18H-OUT)") (class "Default")
      (node (ref "A18") (pin "N1") (pinfunction "OUT_N1") (pintype "output"))
      (node (ref "B20") (pin "K2") (pinfunction "IN2_K2") (pintype "input"))
    )
    (net (code "650") (name "Net-(A18I-OUT)") (class "Default")
      (node (ref "A18") (pin "N2") (pinfunction "OUT_N2") (pintype "output"))
      (node (ref "B20") (pin "L2") (pinfunction "IN3_L2") (pintype "input"))
    )
    (net (code "651") (name "Net-(A18K-OUT)") (class "Default")
      (node (ref "A18") (pin "S2") (pinfunction "OUT_S2") (pintype "output"))
      (node (ref "B20") (pin "L1") (pinfunction "IN2_L1") (pintype "input"))
    )
    (net (code "652") (name "Net-(A18N-OUT)") (class "Default")
      (node (ref "A18") (pin "V2") (pinfunction "OUT_V2") (pintype "output"))
      (node (ref "B20") (pin "M1") (pinfunction "IN3_M1") (pintype "input"))
    )
    (net (code "653") (name "Net-(A19A-OUT)") (class "Default")
      (node (ref "A19") (pin "C1") (pinfunction "OUT_C1") (pintype "output"))
      (node (ref "A19") (pin "E1") (pinfunction "IN2_E1") (pintype "input"))
    )
    (net (code "654") (name "Net-(A19B-OUT)") (class "Default")
      (node (ref "A19") (pin "F1") (pinfunction "OUT_F1") (pintype "output"))
      (node (ref "B20") (pin "E2") (pinfunction "IN2_E2") (pintype "input"))
    )
    (net (code "655") (name "Net-(A19F-IN1)") (class "Default")
      (node (ref "A19") (pin "H1") (pinfunction "IN1_H1") (pintype "input"))
      (node (ref "A19") (pin "K2") (pinfunction "OUT_K2") (pintype "output"))
    )
    (net (code "656") (name "Net-(A19F-OUT)") (class "Default")
      (node (ref "A19") (pin "K1") (pinfunction "OUT_K1") (pintype "output"))
      (node (ref "B11") (pin "B1") (pinfunction "C_B1") (pintype "input"))
      (node (ref "B11") (pin "D2") (pinfunction "C_D2") (pintype "input"))
      (node (ref "B11") (pin "H1") (pinfunction "C_H1") (pintype "input"))
    )
    (net (code "657") (name "Net-(A19H-OUT)") (class "Default")
      (node (ref "A19") (pin "M2") (pinfunction "IN2_M2") (pintype "input"))
      (node (ref "A19") (pin "N1") (pinfunction "OUT_N1") (pintype "output"))
    )
    (net (code "658") (name "Net-(A19J-IN1)") (class "Default")
      (node (ref "A19") (pin "P1") (pinfunction "IN1_P1") (pintype "input"))
      (node (ref "A19") (pin "P2") (pinfunction "IN1_P2") (pintype "input"))
      (node (ref "E12") (pin "N2") (pinfunction "OUT_N2") (pintype "output"))
    )
    (net (code "659") (name "Net-(A19K-OUT)") (class "Default")
      (node (ref "A19") (pin "S2") (pinfunction "OUT_S2") (pintype "output"))
      (node (ref "B19") (pin "H1") (pinfunction "C_H1") (pintype "input"))
      (node (ref "B19") (pin "L2") (pinfunction "C_L2") (pintype "input"))
      (node (ref "B19") (pin "N1") (pinfunction "C_N1") (pintype "input"))
      (node (ref "B19") (pin "S2") (pinfunction "C_S2") (pintype "input"))
    )
    (net (code "660") (name "Net-(B04F-OUT)") (class "Default")
      (node (ref "B04") (pin "M2") (pinfunction "OUT_M2") (pintype "output"))
      (node (ref "B05") (pin "U2") (pinfunction "S_U2") (pintype "input"))
    )
    (net (code "661") (name "Net-(B04G-OUT)") (class "Default")
      (node (ref "B04") (pin "N1") (pinfunction "OUT_N1") (pintype "output"))
      (node (ref "B05") (pin "S2") (pinfunction "C_S2") (pintype "input"))
    )
    (net (code "662") (name "Net-(B04I-IN3)") (class "Default")
      (node (ref "B04") (pin "S1") (pinfunction "IN3_S1") (pintype "input"))
      (node (ref "B05") (pin "R2") (pinfunction "0_R2") (pintype "output"))
    )
    (net (code "663") (name "Net-(B05A-C)") (class "Default")
      (node (ref "B05") (pin "B1") (pinfunction "C_B1") (pintype "input"))
      (node (ref "B06") (pin "K1") (pinfunction "OUT_K1") (pintype "output"))
    )
    (net (code "664") (name "Net-(B05A-D)") (class "Default")
      (node (ref "B05") (pin "C1") (pinfunction "D_C1") (pintype "input"))
      (node (ref "B06") (pin "N2") (pinfunction "OUT_N2") (pintype "output"))
    )
    (net (code "665") (name "Net-(B05D-D)") (class "Default")
      (node (ref "B05") (pin "E2") (pinfunction "D_E2") (pintype "input"))
      (node (ref "B06") (pin "V2") (pinfunction "OUT_V2") (pintype "output"))
    )
    (net (code "666") (name "Net-(B06B-OUT)") (class "Default")
      (node (ref "B06") (pin "E2") (pinfunction "IN2_E2") (pintype "input"))
      (node (ref "B06") (pin "F1") (pinfunction "OUT_F1") (pintype "output"))
    )
    (net (code "667") (name "Net-(B06C-OUT)") (class "Default")
      (node (ref "B06") (pin "F2") (pinfunction "OUT_F2") (pintype "output"))
      (node (ref "B06") (pin "J1") (pinfunction "IN2_J1") (pintype "input"))
    )
    (net (code "668") (name "Net-(B06H-OUT)") (class "Default")
      (node (ref "B06") (pin "L2") (pinfunction "IN1_L2") (pintype "input"))
      (node (ref "B06") (pin "N1") (pinfunction "OUT_N1") (pintype "output"))
    )
    (net (code "669") (name "Net-(B06I-IN2)") (class "Default")
      (node (ref "B06") (pin "M2") (pinfunction "IN2_M2") (pintype "input"))
      (node (ref "B06") (pin "S1") (pinfunction "OUT_S1") (pintype "output"))
    )
    (net (code "670") (name "Net-(B06K-OUT)") (class "Default")
      (node (ref "B06") (pin "S2") (pinfunction "OUT_S2") (pintype "output"))
      (node (ref "B06") (pin "T2") (pinfunction "IN1_T2") (pintype "input"))
    )
    (net (code "671") (name "Net-(B07A-OUT)") (class "Default")
      (node (ref "B07") (pin "D1") (pinfunction "OUT_D1") (pintype "output"))
      (node (ref "B09") (pin "H1") (pinfunction "IN1_H1") (pintype "input"))
    )
    (net (code "672") (name "Net-(B07D-OUT)") (class "Default")
      (node (ref "B07") (pin "H2") (pinfunction "OUT_H2") (pintype "output"))
      (node (ref "B09") (pin "J2") (pinfunction "IN2_J2") (pintype "input"))
    )
    (net (code "673") (name "Net-(B07E-IN3)") (class "Default")
      (node (ref "B07") (pin "H1") (pinfunction "IN3_H1") (pintype "input"))
      (node (ref "B07") (pin "J2") (pinfunction "IN1_J2") (pintype "input"))
      (node (ref "B09") (pin "N2") (pinfunction "OUT_N2") (pintype "output"))
    )
    (net (code "674") (name "Net-(B07E-OUT)") (class "Default")
      (node (ref "B07") (pin "J1") (pinfunction "OUT_J1") (pintype "output"))
      (node (ref "B07") (pin "M1") (pinfunction "IN3_M1") (pintype "input"))
    )
    (net (code "675") (name "Net-(B07G-OUT)") (class "Default")
      (node (ref "B07") (pin "N1") (pinfunction "OUT_N1") (pintype "output"))
      (node (ref "B07") (pin "N2") (pinfunction "IN1_N2") (pintype "input"))
    )
    (net (code "676") (name "Net-(B09F-OUT)") (class "Default")
      (node (ref "B09") (pin "K1") (pinfunction "OUT_K1") (pintype "output"))
      (node (ref "B09") (pin "L1") (pinfunction "IN1_L1") (pintype "input"))
    )
    (net (code "677") (name "Net-(B09G-OUT)") (class "Default")
      (node (ref "B09") (pin "K2") (pinfunction "OUT_K2") (pintype "output"))
      (node (ref "B09") (pin "M1") (pinfunction "IN2_M1") (pintype "input"))
    )
    (net (code "678") (name "Net-(B09H-OUT)") (class "Default")
      (node (ref "B09") (pin "L2") (pinfunction "IN1_L2") (pintype "input"))
      (node (ref "B09") (pin "N1") (pinfunction "OUT_N1") (pintype "output"))
    )
    (net (code "679") (name "Net-(B09J-OUT)") (class "Default")
      (node (ref "B09") (pin "S1") (pinfunction "OUT_S1") (pintype "output"))
      (node (ref "B11") (pin "M2") (pinfunction "D_M2") (pintype "input"))
    )
    (net (code "680") (name "Net-(B11G-C)") (class "Default")
      (node (ref "B11") (pin "N1") (pinfunction "C_N1") (pintype "input"))
      (node (ref "F11") (pin "J2") (pinfunction "OUT_J2") (pintype "output"))
    )
    (net (code "681") (name "Net-(B17F-D)") (class "Default")
      (node (ref "B17") (pin "M2") (pinfunction "D_M2") (pintype "input"))
      (node (ref "B20") (pin "J1") (pinfunction "OUT_J1") (pintype "output"))
    )
    (net (code "682") (name "Net-(B17G-D)") (class "Default")
      (node (ref "B17") (pin "P1") (pinfunction "D_P1") (pintype "input"))
      (node (ref "B20") (pin "M2") (pinfunction "OUT_M2") (pintype "output"))
    )
    (net (code "683") (name "Net-(B17H-D)") (class "Default")
      (node (ref "B17") (pin "T2") (pinfunction "D_T2") (pintype "input"))
      (node (ref "B20") (pin "N1") (pinfunction "OUT_N1") (pintype "output"))
    )
    (net (code "684") (name "Net-(B18A-D)") (class "Default")
      (node (ref "B18") (pin "C1") (pinfunction "D_C1") (pintype "input"))
      (node (ref "B20") (pin "S2") (pinfunction "OUT_S2") (pintype "output"))
    )
    (net (code "685") (name "Net-(B18D-D)") (class "Default")
      (node (ref "B18") (pin "E2") (pinfunction "D_E2") (pintype "input"))
      (node (ref "B20") (pin "U1") (pinfunction "OUT_U1") (pintype "output"))
    )
    (net (code "686") (name "Net-(B18E-D)") (class "Default")
      (node (ref "B18") (pin "J1") (pinfunction "D_J1") (pintype "input"))
      (node (ref "B20") (pin "V1") (pinfunction "OUT_V1") (pintype "output"))
    )
    (net (code "687") (name "Net-(B21N-OUT)") (class "Default")
      (node (ref "B21") (pin "V2") (pinfunction "OUT_V2") (pintype "output"))
      (node (ref "C12") (pin "M1") (pinfunction "IN1_M1") (pintype "input"))
      (node (ref "C12") (pin "N1") (pinfunction "IN2_N1") (pintype "input"))
      (node (ref "C12") (pin "P1") (pinfunction "IN3_P1") (pintype "input"))
      (node (ref "C12") (pin "R1") (pinfunction "IN4_R1") (pintype "input"))
    )
    (net (code "688") (name "Net-(C09A-OUT)") (class "Default")
      (node (ref "C09") (pin "C1") (pinfunction "OUT_C1") (pintype "output"))
      (node (ref "C09") (pin "D1") (pinfunction "IN1_D1") (pintype "input"))
      (node (ref "C11") (pin "K2") (pinfunction "IN2_K2") (pintype "input"))
    )
    (net (code "689") (name "Net-(C09B-OUT)") (class "Default")
      (node (ref "C09") (pin "F1") (pinfunction "OUT_F1") (pintype "output"))
      (node (ref "C09") (pin "H2") (pinfunction "IN1_H2") (pintype "input"))
      (node (ref "D10") (pin "H1") (pinfunction "IN2_H1") (pintype "input"))
    )
    (net (code "690") (name "Net-(C09G-IN2)") (class "Default")
      (node (ref "C09") (pin "J2") (pinfunction "IN2_J2") (pintype "input"))
      (node (ref "C09") (pin "N1") (pinfunction "OUT_N1") (pintype "output"))
    )
    (net (code "691") (name "Net-(C09H-IN1)") (class "Default")
      (node (ref "C09") (pin "L1") (pinfunction "IN1_L1") (pintype "input"))
      (node (ref "D09") (pin "D1") (pinfunction "OUT_D1") (pintype "output"))
    )
    (net (code "692") (name "Net-(C10A-IN1)") (class "Default")
      (node (ref "C10") (pin "A1") (pinfunction "IN1_A1") (pintype "input"))
      (node (ref "C11") (pin "D1") (pinfunction "OUT_D1") (pintype "output"))
    )
    (net (code "693") (name "Net-(C10F-IN1)") (class "Default")
      (node (ref "C10") (pin "H1") (pinfunction "IN1_H1") (pintype "input"))
      (node (ref "C11") (pin "U1") (pinfunction "OUT_U1") (pintype "output"))
    )
    (net (code "694") (name "Net-(C10F-OUT)") (class "Default")
      (node (ref "C10") (pin "K1") (pinfunction "OUT_K1") (pintype "output"))
      (node (ref "D09") (pin "E1") (pinfunction "IN1_E1") (pintype "input"))
      (node (ref "D10") (pin "L2") (pinfunction "IN2_L2") (pintype "input"))
    )
    (net (code "695") (name "Net-(C10G-IN2)") (class "Default")
      (node (ref "C10") (pin "J2") (pinfunction "IN2_J2") (pintype "input"))
      (node (ref "C11") (pin "V1") (pinfunction "OUT_V1") (pintype "output"))
    )
    (net (code "696") (name "Net-(C10G-OUT)") (class "Default")
      (node (ref "C10") (pin "K2") (pinfunction "OUT_K2") (pintype "output"))
      (node (ref "D10") (pin "M2") (pinfunction "IN3_M2") (pintype "input"))
    )
    (net (code "697") (name "Net-(C10I-IN1)") (class "Default")
      (node (ref "C10") (pin "L2") (pinfunction "IN1_L2") (pintype "input"))
      (node (ref "C10") (pin "S1") (pinfunction "OUT_S1") (pintype "output"))
    )
    (net (code "698") (name "Net-(C10I-IN2)") (class "Default")
      (node (ref "C10") (pin "M2") (pinfunction "IN2_M2") (pintype "input"))
      (node (ref "C10") (pin "S2") (pinfunction "OUT_S2") (pintype "output"))
    )
    (net (code "699") (name "Net-(C10K-IN2)") (class "Default")
      (node (ref "C10") (pin "R2") (pinfunction "IN2_R2") (pintype "input"))
      (node (ref "C10") (pin "V2") (pinfunction "OUT_V2") (pintype "output"))
    )
    (net (code "700") (name "Net-(C11D-IN1)") (class "Default")
      (node (ref "C11") (pin "D2") (pinfunction "IN1_D2") (pintype "input"))
      (node (ref "C11") (pin "J1") (pinfunction "OUT_J1") (pintype "output"))
    )
    (net (code "701") (name "Net-(C13A-IN)") (class "Default")
      (node (ref "C13") (pin "E1") (pinfunction "IN_E1") (pintype "input"))
      (node (ref "C13") (pin "S2") (pinfunction "S2_S2") (pintype "output"))
    )
    (net (code "702") (name "Net-(C13A-OUT)") (class "Default")
      (node (ref "C13") (pin "F1") (pinfunction "OUT_F1") (pintype "output"))
      (node (ref "D12") (pin "L1") (pinfunction "IN1_L1") (pintype "input"))
      (node (ref "D24") (pin "N1") (pinfunction "C_N1") (pintype "input"))
    )
    (net (code "703") (name "Net-(C13E-IN)") (class "Default")
      (node (ref "C13") (pin "H1") (pinfunction "IN_H1") (pintype "input"))
      (node (ref "C13") (pin "P2") (pinfunction "P2_P2") (pintype "output"))
    )
    (net (code "704") (name "Net-(C14A-OUT)") (class "Default")
      (node (ref "C14") (pin "C1") (pinfunction "OUT_C1") (pintype "output"))
      (node (ref "C19") (pin "A1") (pinfunction "IN1_A1") (pintype "input"))
    )
    (net (code "705") (name "Net-(C14B-OUT)") (class "Default")
      (node (ref "C14") (pin "F1") (pinfunction "OUT_F1") (pintype "output"))
      (node (ref "C19") (pin "B1") (pinfunction "IN2_B1") (pintype "input"))
    )
    (net (code "706") (name "Net-(C14C-OUT)") (class "Default")
      (node (ref "C14") (pin "F2") (pinfunction "OUT_F2") (pintype "output"))
      (node (ref "C19") (pin "C1") (pinfunction "IN3_C1") (pintype "input"))
    )
    (net (code "707") (name "Net-(C14F-OUT)") (class "Default")
      (node (ref "C14") (pin "K1") (pinfunction "OUT_K1") (pintype "output"))
      (node (ref "C19") (pin "D2") (pinfunction "IN1_D2") (pintype "input"))
    )
    (net (code "708") (name "Net-(C14G-OUT)") (class "Default")
      (node (ref "C14") (pin "K2") (pinfunction "OUT_K2") (pintype "output"))
      (node (ref "C19") (pin "E2") (pinfunction "IN2_E2") (pintype "input"))
    )
    (net (code "709") (name "Net-(C14H-OUT)") (class "Default")
      (node (ref "C14") (pin "N1") (pinfunction "OUT_N1") (pintype "output"))
      (node (ref "C19") (pin "F2") (pinfunction "IN3_F2") (pintype "input"))
    )
    (net (code "710") (name "Net-(C14I-OUT)") (class "Default")
      (node (ref "C14") (pin "N2") (pinfunction "OUT_N2") (pintype "output"))
      (node (ref "C19") (pin "E1") (pinfunction "IN1_E1") (pintype "input"))
    )
    (net (code "711") (name "Net-(C14J-OUT)") (class "Default")
      (node (ref "C14") (pin "S1") (pinfunction "OUT_S1") (pintype "output"))
      (node (ref "C19") (pin "F1") (pinfunction "IN2_F1") (pintype "input"))
    )
    (net (code "712") (name "Net-(C14K-OUT)") (class "Default")
      (node (ref "C14") (pin "S2") (pinfunction "OUT_S2") (pintype "output"))
      (node (ref "C19") (pin "H1") (pinfunction "IN3_H1") (pintype "input"))
    )
    (net (code "713") (name "Net-(C14N-OUT)") (class "Default")
      (node (ref "C14") (pin "V2") (pinfunction "OUT_V2") (pintype "output"))
      (node (ref "C20") (pin "M1") (pinfunction "IN3_M1") (pintype "input"))
    )
    (net (code "714") (name "Net-(C15A-OUT)") (class "Default")
      (node (ref "C15") (pin "C1") (pinfunction "OUT_C1") (pintype "output"))
      (node (ref "C19") (pin "J2") (pinfunction "IN1_J2") (pintype "input"))
    )
    (net (code "715") (name "Net-(C15B-OUT)") (class "Default")
      (node (ref "C15") (pin "F1") (pinfunction "OUT_F1") (pintype "output"))
      (node (ref "C19") (pin "K2") (pinfunction "IN2_K2") (pintype "input"))
    )
    (net (code "716") (name "Net-(C15C-OUT)") (class "Default")
      (node (ref "C15") (pin "F2") (pinfunction "OUT_F2") (pintype "output"))
      (node (ref "C19") (pin "L2") (pinfunction "IN3_L2") (pintype "input"))
    )
    (net (code "717") (name "Net-(C15F-OUT)") (class "Default")
      (node (ref "C15") (pin "K1") (pinfunction "OUT_K1") (pintype "output"))
      (node (ref "C19") (pin "K1") (pinfunction "IN1_K1") (pintype "input"))
    )
    (net (code "718") (name "Net-(C15G-OUT)") (class "Default")
      (node (ref "C15") (pin "K2") (pinfunction "OUT_K2") (pintype "output"))
      (node (ref "C19") (pin "L1") (pinfunction "IN2_L1") (pintype "input"))
    )
    (net (code "719") (name "Net-(C15H-OUT)") (class "Default")
      (node (ref "C15") (pin "N1") (pinfunction "OUT_N1") (pintype "output"))
      (node (ref "C19") (pin "M1") (pinfunction "IN3_M1") (pintype "input"))
    )
    (net (code "720") (name "Net-(C15I-OUT)") (class "Default")
      (node (ref "C15") (pin "N2") (pinfunction "OUT_N2") (pintype "output"))
      (node (ref "C19") (pin "N2") (pinfunction "IN1_N2") (pintype "input"))
    )
    (net (code "721") (name "Net-(C15J-OUT)") (class "Default")
      (node (ref "C15") (pin "S1") (pinfunction "OUT_S1") (pintype "output"))
      (node (ref "C19") (pin "P2") (pinfunction "IN2_P2") (pintype "input"))
    )
    (net (code "722") (name "Net-(C15K-OUT)") (class "Default")
      (node (ref "C15") (pin "S2") (pinfunction "OUT_S2") (pintype "output"))
      (node (ref "C19") (pin "R2") (pinfunction "IN3_R2") (pintype "input"))
    )
    (net (code "723") (name "Net-(C15N-OUT)") (class "Default")
      (node (ref "C15") (pin "V2") (pinfunction "OUT_V2") (pintype "output"))
      (node (ref "C20") (pin "R2") (pinfunction "IN3_R2") (pintype "input"))
    )
    (net (code "724") (name "Net-(C16A-OUT)") (class "Default")
      (node (ref "C16") (pin "C1") (pinfunction "OUT_C1") (pintype "output"))
      (node (ref "C19") (pin "P1") (pinfunction "IN1_P1") (pintype "input"))
    )
    (net (code "725") (name "Net-(C16B-OUT)") (class "Default")
      (node (ref "C16") (pin "F1") (pinfunction "OUT_F1") (pintype "output"))
      (node (ref "C19") (pin "R1") (pinfunction "IN2_R1") (pintype "input"))
    )
    (net (code "726") (name "Net-(C16C-OUT)") (class "Default")
      (node (ref "C16") (pin "F2") (pinfunction "OUT_F2") (pintype "output"))
      (node (ref "C19") (pin "S1") (pinfunction "IN3_S1") (pintype "input"))
    )
    (net (code "727") (name "Net-(C16F-OUT)") (class "Default")
      (node (ref "C16") (pin "K1") (pinfunction "OUT_K1") (pintype "output"))
      (node (ref "C19") (pin "T2") (pinfunction "IN1_T2") (pintype "input"))
    )
    (net (code "728") (name "Net-(C16G-OUT)") (class "Default")
      (node (ref "C16") (pin "K2") (pinfunction "OUT_K2") (pintype "output"))
      (node (ref "C19") (pin "U2") (pinfunction "IN2_U2") (pintype "input"))
    )
    (net (code "729") (name "Net-(C16H-OUT)") (class "Default")
      (node (ref "C16") (pin "N1") (pinfunction "OUT_N1") (pintype "output"))
      (node (ref "C19") (pin "V2") (pinfunction "IN3_V2") (pintype "input"))
    )
    (net (code "730") (name "Net-(C16I-OUT)") (class "Default")
      (node (ref "C16") (pin "N2") (pinfunction "OUT_N2") (pintype "output"))
      (node (ref "C20") (pin "A1") (pinfunction "IN1_A1") (pintype "input"))
    )
    (net (code "731") (name "Net-(C16J-OUT)") (class "Default")
      (node (ref "C16") (pin "S1") (pinfunction "OUT_S1") (pintype "output"))
      (node (ref "C20") (pin "B1") (pinfunction "IN2_B1") (pintype "input"))
    )
    (net (code "732") (name "Net-(C16K-OUT)") (class "Default")
      (node (ref "C16") (pin "S2") (pinfunction "OUT_S2") (pintype "output"))
      (node (ref "C20") (pin "C1") (pinfunction "IN3_C1") (pintype "input"))
    )
    (net (code "733") (name "Net-(C16N-OUT)") (class "Default")
      (node (ref "C16") (pin "V2") (pinfunction "OUT_V2") (pintype "output"))
      (node (ref "C20") (pin "S1") (pinfunction "IN3_S1") (pintype "input"))
    )
    (net (code "734") (name "Net-(C17A-OUT)") (class "Default")
      (node (ref "C17") (pin "C1") (pinfunction "OUT_C1") (pintype "output"))
      (node (ref "C20") (pin "D2") (pinfunction "IN1_D2") (pintype "input"))
    )
    (net (code "735") (name "Net-(C17B-OUT)") (class "Default")
      (node (ref "C17") (pin "F1") (pinfunction "OUT_F1") (pintype "output"))
      (node (ref "C20") (pin "E2") (pinfunction "IN2_E2") (pintype "input"))
    )
    (net (code "736") (name "Net-(C17C-OUT)") (class "Default")
      (node (ref "C17") (pin "F2") (pinfunction "OUT_F2") (pintype "output"))
      (node (ref "C20") (pin "F2") (pinfunction "IN3_F2") (pintype "input"))
    )
    (net (code "737") (name "Net-(C17F-OUT)") (class "Default")
      (node (ref "C17") (pin "K1") (pinfunction "OUT_K1") (pintype "output"))
      (node (ref "C20") (pin "E1") (pinfunction "IN1_E1") (pintype "input"))
    )
    (net (code "738") (name "Net-(C17G-OUT)") (class "Default")
      (node (ref "C17") (pin "K2") (pinfunction "OUT_K2") (pintype "output"))
      (node (ref "C20") (pin "F1") (pinfunction "IN2_F1") (pintype "input"))
    )
    (net (code "739") (name "Net-(C17H-OUT)") (class "Default")
      (node (ref "C17") (pin "N1") (pinfunction "OUT_N1") (pintype "output"))
      (node (ref "C20") (pin "H1") (pinfunction "IN3_H1") (pintype "input"))
    )
    (net (code "740") (name "Net-(C17I-OUT)") (class "Default")
      (node (ref "C17") (pin "N2") (pinfunction "OUT_N2") (pintype "output"))
      (node (ref "C20") (pin "J2") (pinfunction "IN1_J2") (pintype "input"))
    )
    (net (code "741") (name "Net-(C17J-OUT)") (class "Default")
      (node (ref "C17") (pin "S1") (pinfunction "OUT_S1") (pintype "output"))
      (node (ref "C20") (pin "K2") (pinfunction "IN2_K2") (pintype "input"))
    )
    (net (code "742") (name "Net-(C17K-IN2)") (class "Default")
      (node (ref "C17") (pin "R2") (pinfunction "IN2_R2") (pintype "input"))
      (node (ref "D23") (pin "T2") (pinfunction "OUT_T2") (pintype "output"))
    )
    (net (code "743") (name "Net-(C17K-OUT)") (class "Default")
      (node (ref "C17") (pin "S2") (pinfunction "OUT_S2") (pintype "output"))
      (node (ref "C20") (pin "L2") (pinfunction "IN3_L2") (pintype "input"))
    )
    (net (code "744") (name "Net-(C17N-OUT)") (class "Default")
      (node (ref "C17") (pin "V2") (pinfunction "OUT_V2") (pintype "output"))
      (node (ref "C20") (pin "V2") (pinfunction "IN3_V2") (pintype "input"))
    )
    (net (code "745") (name "Net-(C18A-IN2)") (class "Default")
      (node (ref "C18") (pin "B1") (pinfunction "IN2_B1") (pintype "input"))
      (node (ref "C21") (pin "E2") (pinfunction "IN2_E2") (pintype "input"))
      (node (ref "D22") (pin "E1") (pinfunction "OUT_E1") (pintype "open_collector"))
    )
    (net (code "746") (name "Net-(C18B-IN2)") (class "Default")
      (node (ref "C18") (pin "E1") (pinfunction "IN2_E1") (pintype "input"))
      (node (ref "C21") (pin "K2") (pinfunction "IN2_K2") (pintype "input"))
      (node (ref "D19") (pin "D1") (pinfunction "OUT_D1") (pintype "output"))
    )
    (net (code "747") (name "Net-(C18B-OUT)") (class "Default")
      (node (ref "C18") (pin "F1") (pinfunction "OUT_F1") (pintype "output"))
      (node (ref "C21") (pin "F1") (pinfunction "IN2_F1") (pintype "input"))
    )
    (net (code "748") (name "Net-(C18C-IN2)") (class "Default")
      (node (ref "C18") (pin "E2") (pinfunction "IN2_E2") (pintype "input"))
      (node (ref "C18") (pin "K1") (pinfunction "OUT_K1") (pintype "output"))
      (node (ref "C21") (pin "P2") (pinfunction "IN2_P2") (pintype "input"))
    )
    (net (code "749") (name "Net-(C18C-OUT)") (class "Default")
      (node (ref "C18") (pin "F2") (pinfunction "OUT_F2") (pintype "output"))
      (node (ref "C21") (pin "L1") (pinfunction "IN2_L1") (pintype "input"))
    )
    (net (code "750") (name "Net-(C18H-IN1)") (class "Default")
      (node (ref "C18") (pin "L1") (pinfunction "IN1_L1") (pintype "input"))
      (node (ref "C18") (pin "N2") (pinfunction "OUT_N2") (pintype "output"))
    )
    (net (code "751") (name "Net-(C18H-IN2)") (class "Default")
      (node (ref "C18") (pin "M1") (pinfunction "IN2_M1") (pintype "input"))
      (node (ref "C18") (pin "S1") (pinfunction "OUT_S1") (pintype "output"))
    )
    (net (code "752") (name "Net-(C18H-OUT)") (class "Default")
      (node (ref "C18") (pin "N1") (pinfunction "OUT_N1") (pintype "output"))
      (node (ref "C22") (pin "P1") (pinfunction "D_P1") (pintype "input"))
    )
    (net (code "753") (name "Net-(C19A-OUT)") (class "Default")
      (node (ref "C19") (pin "D1") (pinfunction "OUT_D1") (pintype "output"))
      (node (ref "C23") (pin "C1") (pinfunction "D_C1") (pintype "input"))
    )
    (net (code "754") (name "Net-(C19D-OUT)") (class "Default")
      (node (ref "C19") (pin "H2") (pinfunction "OUT_H2") (pintype "output"))
      (node (ref "C23") (pin "E2") (pinfunction "D_E2") (pintype "input"))
    )
    (net (code "755") (name "Net-(C19E-OUT)") (class "Default")
      (node (ref "C19") (pin "J1") (pinfunction "OUT_J1") (pintype "output"))
      (node (ref "C23") (pin "J1") (pinfunction "D_J1") (pintype "input"))
    )
    (net (code "756") (name "Net-(C19F-OUT)") (class "Default")
      (node (ref "C19") (pin "M2") (pinfunction "OUT_M2") (pintype "output"))
      (node (ref "C23") (pin "M2") (pinfunction "D_M2") (pintype "input"))
    )
    (net (code "757") (name "Net-(C19G-OUT)") (class "Default")
      (node (ref "C19") (pin "N1") (pinfunction "OUT_N1") (pintype "output"))
      (node (ref "C23") (pin "P1") (pinfunction "D_P1") (pintype "input"))
    )
    (net (code "758") (name "Net-(C19H-OUT)") (class "Default")
      (node (ref "C19") (pin "S2") (pinfunction "OUT_S2") (pintype "output"))
      (node (ref "C23") (pin "T2") (pinfunction "D_T2") (pintype "input"))
    )
    (net (code "759") (name "Net-(C19I-OUT)") (class "Default")
      (node (ref "C19") (pin "U1") (pinfunction "OUT_U1") (pintype "output"))
      (node (ref "C24") (pin "C1") (pinfunction "D_C1") (pintype "input"))
    )
    (net (code "760") (name "Net-(C19J-OUT)") (class "Default")
      (node (ref "C19") (pin "V1") (pinfunction "OUT_V1") (pintype "output"))
      (node (ref "C24") (pin "E2") (pinfunction "D_E2") (pintype "input"))
    )
    (net (code "761") (name "Net-(C20A-OUT)") (class "Default")
      (node (ref "C20") (pin "D1") (pinfunction "OUT_D1") (pintype "output"))
      (node (ref "C24") (pin "J1") (pinfunction "D_J1") (pintype "input"))
    )
    (net (code "762") (name "Net-(C20D-OUT)") (class "Default")
      (node (ref "C20") (pin "H2") (pinfunction "OUT_H2") (pintype "output"))
      (node (ref "C24") (pin "M2") (pinfunction "D_M2") (pintype "input"))
    )
    (net (code "763") (name "Net-(C20E-OUT)") (class "Default")
      (node (ref "C20") (pin "J1") (pinfunction "OUT_J1") (pintype "output"))
      (node (ref "C24") (pin "P1") (pinfunction "D_P1") (pintype "input"))
    )
    (net (code "764") (name "Net-(C20F-OUT)") (class "Default")
      (node (ref "C20") (pin "M2") (pinfunction "OUT_M2") (pintype "output"))
      (node (ref "C24") (pin "T2") (pinfunction "D_T2") (pintype "input"))
    )
    (net (code "765") (name "Net-(C20G-IN1)") (class "Default")
      (node (ref "C20") (pin "K1") (pinfunction "IN1_K1") (pintype "input"))
      (node (ref "C21") (pin "D1") (pinfunction "OUT_D1") (pintype "output"))
    )
    (net (code "766") (name "Net-(C20G-IN2)") (class "Default")
      (node (ref "C20") (pin "L1") (pinfunction "IN2_L1") (pintype "input"))
      (node (ref "C21") (pin "H2") (pinfunction "OUT_H2") (pintype "output"))
    )
    (net (code "767") (name "Net-(C20G-OUT)") (class "Default")
      (node (ref "C20") (pin "N1") (pinfunction "OUT_N1") (pintype "output"))
      (node (ref "C22") (pin "C1") (pinfunction "D_C1") (pintype "input"))
    )
    (net (code "768") (name "Net-(C20H-IN1)") (class "Default")
      (node (ref "C20") (pin "N2") (pinfunction "IN1_N2") (pintype "input"))
      (node (ref "C21") (pin "J1") (pinfunction "OUT_J1") (pintype "output"))
    )
    (net (code "769") (name "Net-(C20H-IN2)") (class "Default")
      (node (ref "C20") (pin "P2") (pinfunction "IN2_P2") (pintype "input"))
      (node (ref "C21") (pin "M2") (pinfunction "OUT_M2") (pintype "output"))
    )
    (net (code "770") (name "Net-(C20H-OUT)") (class "Default")
      (node (ref "C20") (pin "S2") (pinfunction "OUT_S2") (pintype "output"))
      (node (ref "C22") (pin "E2") (pinfunction "D_E2") (pintype "input"))
    )
    (net (code "771") (name "Net-(C20I-IN1)") (class "Default")
      (node (ref "C20") (pin "P1") (pinfunction "IN1_P1") (pintype "input"))
      (node (ref "C21") (pin "N1") (pinfunction "OUT_N1") (pintype "output"))
    )
    (net (code "772") (name "Net-(C20I-IN2)") (class "Default")
      (node (ref "C20") (pin "R1") (pinfunction "IN2_R1") (pintype "input"))
      (node (ref "C21") (pin "S2") (pinfunction "OUT_S2") (pintype "output"))
    )
    (net (code "773") (name "Net-(C20I-OUT)") (class "Default")
      (node (ref "C20") (pin "U1") (pinfunction "OUT_U1") (pintype "output"))
      (node (ref "C22") (pin "J1") (pinfunction "D_J1") (pintype "input"))
    )
    (net (code "774") (name "Net-(C20J-IN1)") (class "Default")
      (node (ref "C20") (pin "T2") (pinfunction "IN1_T2") (pintype "input"))
      (node (ref "C21") (pin "U1") (pinfunction "OUT_U1") (pintype "output"))
    )
    (net (code "775") (name "Net-(C20J-IN2)") (class "Default")
      (node (ref "C20") (pin "U2") (pinfunction "IN2_U2") (pintype "input"))
      (node (ref "C21") (pin "V1") (pinfunction "OUT_V1") (pintype "output"))
    )
    (net (code "776") (name "Net-(C20J-OUT)") (class "Default")
      (node (ref "C20") (pin "V1") (pinfunction "OUT_V1") (pintype "output"))
      (node (ref "C22") (pin "M2") (pinfunction "D_M2") (pintype "input"))
    )
    (net (code "777") (name "Net-(D06A-IN)") (class "Default")
      (node (ref "D06") (pin "E1") (pinfunction "IN_E1") (pintype "input"))
      (node (ref "D06") (pin "R2") (pinfunction "R2_R2") (pintype "output"))
    )
    (net (code "778") (name "Net-(D07A-IN1)") (class "Default")
      (node (ref "D07") (pin "A1") (pinfunction "IN1_A1") (pintype "input"))
      (node (ref "D07") (pin "D1") (pinfunction "IN1_D1") (pintype "input"))
      (node (ref "D07") (pin "F2") (pinfunction "OUT_F2") (pintype "output"))
    )
    (net (code "779") (name "Net-(D07F-IN2)") (class "Default")
      (node (ref "D06") (pin "H2") (pinfunction "H2_H2") (pintype "input"))
      (node (ref "D07") (pin "J1") (pinfunction "IN2_J1") (pintype "input"))
      (node (ref "D07") (pin "S2") (pinfunction "OUT_S2") (pintype "output"))
    )
    (net (code "780") (name "Net-(D07J-OUT)") (class "Default")
      (node (ref "D07") (pin "S1") (pinfunction "OUT_S1") (pintype "output"))
      (node (ref "E09") (pin "D1") (pinfunction "IN1_D1") (pintype "input"))
    )
    (net (code "781") (name "Net-(D07K-IN2)") (class "Default")
      (node (ref "D07") (pin "R2") (pinfunction "IN2_R2") (pintype "input"))
      (node (ref "D07") (pin "V2") (pinfunction "OUT_V2") (pintype "output"))
    )
    (net (code "782") (name "Net-(D09I-OUT)") (class "Default")
      (node (ref "D09") (pin "T2") (pinfunction "IN1_T2") (pintype "input"))
      (node (ref "D09") (pin "U1") (pinfunction "OUT_U1") (pintype "output"))
    )
    (net (code "783") (name "Net-(D12B-IN1)") (class "Default")
      (node (ref "D12") (pin "D1") (pinfunction "IN1_D1") (pintype "input"))
      (node (ref "D12") (pin "F2") (pinfunction "OUT_F2") (pintype "output"))
    )
    (net (code "784") (name "Net-(D12B-OUT)") (class "Default")
      (node (ref "D12") (pin "F1") (pinfunction "OUT_F1") (pintype "output"))
      (node (ref "D23") (pin "S1") (pinfunction "IN1A_S1") (pintype "input"))
    )
    (net (code "785") (name "Net-(D12H-OUT)") (class "Default")
      (node (ref "D12") (pin "N1") (pinfunction "OUT_N1") (pintype "output"))
      (node (ref "D24") (pin "U2") (pinfunction "S_U2") (pintype "input"))
    )
    (net (code "786") (name "Net-(D12I-OUT)") (class "Default")
      (node (ref "D12") (pin "N2") (pinfunction "OUT_N2") (pintype "output"))
      (node (ref "D24") (pin "T2") (pinfunction "D_T2") (pintype "input"))
    )
    (net (code "787") (name "Net-(D12J-OUT)") (class "Default")
      (node (ref "D12") (pin "S1") (pinfunction "OUT_S1") (pintype "output"))
      (node (ref "D24") (pin "S2") (pinfunction "C_S2") (pintype "input"))
    )
    (net (code "788") (name "Net-(D12K-OUT)") (class "Default")
      (node (ref "D12") (pin "S2") (pinfunction "OUT_S2") (pintype "output"))
      (node (ref "D22") (pin "U2") (pinfunction "IN4_U2") (pintype "input"))
    )
    (net (code "789") (name "Net-(D13B-OUT)") (class "Default")
      (node (ref "D13") (pin "F1") (pinfunction "OUT_F1") (pintype "output"))
      (node (ref "D17") (pin "R1") (pinfunction "IN2_R1") (pintype "input"))
    )
    (net (code "790") (name "Net-(D13C-OUT)") (class "Default")
      (node (ref "D13") (pin "F2") (pinfunction "OUT_F2") (pintype "output"))
      (node (ref "D17") (pin "R2") (pinfunction "IN3_R2") (pintype "input"))
    )
    (net (code "791") (name "Net-(D13G-IN1)") (class "Default")
      (node (ref "D13") (pin "H2") (pinfunction "IN1_H2") (pintype "input"))
      (node (ref "D20") (pin "S1") (pinfunction "OUT_S1") (pintype "output"))
    )
    (net (code "792") (name "Net-(D13H-IN1)") (class "Default")
      (node (ref "D13") (pin "L1") (pinfunction "IN1_L1") (pintype "input"))
      (node (ref "D13") (pin "S1") (pinfunction "OUT_S1") (pintype "output"))
    )
    (net (code "793") (name "Net-(D13N-OUT)") (class "Default")
      (node (ref "D13") (pin "V2") (pinfunction "OUT_V2") (pintype "output"))
      (node (ref "D16") (pin "L1") (pinfunction "IN1_L1") (pintype "input"))
    )
    (net (code "794") (name "Net-(D14B-OUT)") (class "Default")
      (node (ref "C13") (pin "H2") (pinfunction "H2_H2") (pintype "input"))
      (node (ref "D14") (pin "F1") (pinfunction "OUT_F1") (pintype "output"))
      (node (ref "D24") (pin "L2") (pinfunction "C_L2") (pintype "input"))
    )
    (net (code "795") (name "Net-(D14C-OUT)") (class "Default")
      (node (ref "D14") (pin "F2") (pinfunction "OUT_F2") (pintype "output"))
      (node (ref "D14") (pin "J2") (pinfunction "IN2_J2") (pintype "input"))
    )
    (net (code "796") (name "Net-(D14G-IN1)") (class "Default")
      (node (ref "D14") (pin "H2") (pinfunction "IN1_H2") (pintype "input"))
      (node (ref "D14") (pin "N2") (pinfunction "OUT_N2") (pintype "output"))
    )
    (net (code "797") (name "Net-(D14H-OUT)") (class "Default")
      (node (ref "D14") (pin "N1") (pinfunction "OUT_N1") (pintype "output"))
      (node (ref "D19") (pin "F2") (pinfunction "IN3_F2") (pintype "input"))
    )
    (net (code "798") (name "Net-(D14J-IN2)") (class "Default")
      (node (ref "D14") (pin "R1") (pinfunction "IN2_R1") (pintype "input"))
      (node (ref "D14") (pin "S2") (pinfunction "OUT_S2") (pintype "output"))
    )
    (net (code "799") (name "Net-(D14J-OUT)") (class "Default")
      (node (ref "D14") (pin "S1") (pinfunction "OUT_S1") (pintype "output"))
      (node (ref "D24") (pin "B1") (pinfunction "C_B1") (pintype "input"))
      (node (ref "D24") (pin "D2") (pinfunction "C_D2") (pintype "input"))
      (node (ref "D24") (pin "H1") (pinfunction "C_H1") (pintype "input"))
    )
    (net (code "800") (name "Net-(D14N-OUT)") (class "Default")
      (node (ref "D14") (pin "V2") (pinfunction "OUT_V2") (pintype "output"))
      (node (ref "D22") (pin "S2") (pinfunction "IN2_S2") (pintype "input"))
    )
    (net (code "801") (name "Net-(D15A-OUT)") (class "Default")
      (node (ref "D15") (pin "C1") (pinfunction "OUT_C1") (pintype "output"))
      (node (ref "D17") (pin "D2") (pinfunction "IN1_D2") (pintype "input"))
    )
    (net (code "802") (name "Net-(D15B-OUT)") (class "Default")
      (node (ref "D15") (pin "F1") (pinfunction "OUT_F1") (pintype "output"))
      (node (ref "D17") (pin "F2") (pinfunction "IN3_F2") (pintype "input"))
    )
    (net (code "803") (name "Net-(D15C-IN2)") (class "Default")
      (node (ref "D15") (pin "E2") (pinfunction "IN2_E2") (pintype "input"))
      (node (ref "D21") (pin "E1") (pinfunction "OUT_E1") (pintype "output"))
    )
    (net (code "804") (name "Net-(D15G-OUT)") (class "Default")
      (node (ref "D15") (pin "K2") (pinfunction "OUT_K2") (pintype "output"))
      (node (ref "D15") (pin "L1") (pinfunction "IN1_L1") (pintype "input"))
    )
    (net (code "805") (name "Net-(D15H-OUT)") (class "Default")
      (node (ref "D15") (pin "N1") (pinfunction "OUT_N1") (pintype "output"))
      (node (ref "D24") (pin "M2") (pinfunction "D_M2") (pintype "input"))
    )
    (net (code "806") (name "Net-(D15I-IN1)") (class "Default")
      (node (ref "D15") (pin "L2") (pinfunction "IN1_L2") (pintype "input"))
      (node (ref "D21") (pin "J2") (pinfunction "OUT_J2") (pintype "output"))
    )
    (net (code "807") (name "Net-(D15K-OUT)") (class "Default")
      (node (ref "D15") (pin "S2") (pinfunction "OUT_S2") (pintype "output"))
      (node (ref "D20") (pin "K1") (pinfunction "IN4_K1") (pintype "input"))
    )
    (net (code "808") (name "Net-(D15N-IN1)") (class "Default")
      (node (ref "D15") (pin "T2") (pinfunction "IN1_T2") (pintype "input"))
      (node (ref "D17") (pin "S1") (pinfunction "IN3_S1") (pintype "input"))
      (node (ref "D18") (pin "D1") (pinfunction "OUT_D1") (pintype "output"))
    )
    (net (code "809") (name "Net-(D16A-IN2)") (class "Default")
      (node (ref "D16") (pin "B1") (pinfunction "IN2_B1") (pintype "input"))
      (node (ref "D21") (pin "P2") (pinfunction "OUT_P2") (pintype "output"))
    )
    (net (code "810") (name "Net-(D16A-OUT)") (class "Default")
      (node (ref "D16") (pin "C1") (pinfunction "OUT_C1") (pintype "output"))
      (node (ref "D21") (pin "A1") (pinfunction "IN1_A1") (pintype "input"))
    )
    (net (code "811") (name "Net-(D16B-IN2)") (class "Default")
      (node (ref "D16") (pin "E1") (pinfunction "IN2_E1") (pintype "input"))
      (node (ref "D21") (pin "S1") (pinfunction "OUT_S1") (pintype "output"))
    )
    (net (code "812") (name "Net-(D16B-OUT)") (class "Default")
      (node (ref "D16") (pin "F1") (pinfunction "OUT_F1") (pintype "output"))
      (node (ref "D21") (pin "B1") (pinfunction "IN2_B1") (pintype "input"))
    )
    (net (code "813") (name "Net-(D16C-IN2)") (class "Default")
      (node (ref "D16") (pin "E2") (pinfunction "IN2_E2") (pintype "input"))
      (node (ref "D21") (pin "V2") (pinfunction "OUT_V2") (pintype "output"))
    )
    (net (code "814") (name "Net-(D16C-OUT)") (class "Default")
      (node (ref "D16") (pin "F2") (pinfunction "OUT_F2") (pintype "output"))
      (node (ref "D21") (pin "C1") (pinfunction "IN3_C1") (pintype "input"))
    )
    (net (code "815") (name "Net-(D16F-IN1)") (class "Default")
      (node (ref "D16") (pin "H1") (pinfunction "IN1_H1") (pintype "input"))
      (node (ref "D19") (pin "J1") (pinfunction "OUT_J1") (pintype "output"))
    )
    (net (code "816") (name "Net-(D16F-IN2)") (class "Default")
      (node (ref "D16") (pin "J1") (pinfunction "IN2_J1") (pintype "input"))
      (node (ref "D19") (pin "M2") (pinfunction "OUT_M2") (pintype "output"))
    )
    (net (code "817") (name "Net-(D16G-OUT)") (class "Default")
      (node (ref "D16") (pin "K2") (pinfunction "OUT_K2") (pintype "output"))
      (node (ref "D19") (pin "D2") (pinfunction "IN1_D2") (pintype "input"))
    )
    (net (code "818") (name "Net-(D16H-OUT)") (class "Default")
      (node (ref "D16") (pin "L2") (pinfunction "IN1_L2") (pintype "input"))
      (node (ref "D16") (pin "N1") (pinfunction "OUT_N1") (pintype "output"))
      (node (ref "D18") (pin "P2") (pinfunction "IN2_P2") (pintype "input"))
    )
    (net (code "819") (name "Net-(D16I-OUT)") (class "Default")
      (node (ref "D16") (pin "N2") (pinfunction "OUT_N2") (pintype "output"))
      (node (ref "D18") (pin "R1") (pinfunction "IN2_R1") (pintype "input"))
    )
    (net (code "820") (name "Net-(D17D-IN2)") (class "Default")
      (node (ref "D17") (pin "E2") (pinfunction "IN2_E2") (pintype "input"))
      (node (ref "D20") (pin "E1") (pinfunction "OUT_E1") (pintype "output"))
    )
    (net (code "821") (name "Net-(D17E-OUT)") (class "Default")
      (node (ref "D17") (pin "J1") (pinfunction "OUT_J1") (pintype "output"))
      (node (ref "D17") (pin "K2") (pinfunction "IN2_K2") (pintype "input"))
      (node (ref "D20") (pin "F2") (pinfunction "IN3_F2") (pintype "input"))
    )
    (net (code "822") (name "Net-(D17G-IN2)") (class "Default")
      (node (ref "D17") (pin "L1") (pinfunction "IN2_L1") (pintype "input"))
      (node (ref "D17") (pin "S2") (pinfunction "OUT_S2") (pintype "output"))
    )
    (net (code "823") (name "Net-(D17H-IN2)") (class "Default")
      (node (ref "D17") (pin "P2") (pinfunction "IN2_P2") (pintype "input"))
      (node (ref "D23") (pin "V2") (pinfunction "OUT_V2") (pintype "output"))
    )
    (net (code "824") (name "Net-(D18D-OUT)") (class "Default")
      (node (ref "D18") (pin "H2") (pinfunction "OUT_H2") (pintype "output"))
      (node (ref "D22") (pin "F1") (pinfunction "IN1_F1") (pintype "input"))
    )
    (net (code "825") (name "Net-(D18E-OUT)") (class "Default")
      (node (ref "D18") (pin "J1") (pinfunction "OUT_J1") (pintype "output"))
      (node (ref "D22") (pin "K2") (pinfunction "IN1_K2") (pintype "input"))
    )
    (net (code "826") (name "Net-(D18G-OUT)") (class "Default")
      (node (ref "D18") (pin "N1") (pinfunction "OUT_N1") (pintype "output"))
      (node (ref "D22") (pin "R1") (pinfunction "IN4_R1") (pintype "input"))
    )
    (net (code "827") (name "Net-(D19D-IN2)") (class "Default")
      (node (ref "D19") (pin "E2") (pinfunction "IN2_E2") (pintype "input"))
      (node (ref "D19") (pin "N1") (pinfunction "OUT_N1") (pintype "output"))
    )
    (net (code "828") (name "Net-(D19D-OUT)") (class "Default")
      (node (ref "D19") (pin "H2") (pinfunction "OUT_H2") (pintype "output"))
      (node (ref "D23") (pin "P1") (pinfunction "IN5C_P1") (pintype "input"))
    )
    (net (code "829") (name "Net-(D20E-IN2)") (class "Default")
      (node (ref "D20") (pin "H1") (pinfunction "IN2_H1") (pintype "input"))
      (node (ref "D20") (pin "P2") (pinfunction "OUT_P2") (pintype "output"))
    )
    (net (code "830") (name "Net-(E09A-OUT)") (class "Default")
      (node (ref "E09") (pin "C1") (pinfunction "OUT_C1") (pintype "output"))
      (node (ref "E09") (pin "E1") (pinfunction "IN2_E1") (pintype "input"))
    )
    (net (code "831") (name "Net-(E09G-OUT)") (class "Default")
      (node (ref "E09") (pin "K2") (pinfunction "OUT_K2") (pintype "output"))
      (node (ref "F11") (pin "K2") (pinfunction "IN1_K2") (pintype "input"))
    )
    (net (code "832") (name "Net-(E11J-IN1)") (class "Default")
      (node (ref "E11") (pin "P1") (pinfunction "IN1_P1") (pintype "input"))
      (node (ref "F11") (pin "L1") (pinfunction "OUT_L1") (pintype "output"))
    )
    (net (code "833") (name "Net-(E11N-OUT)") (class "Default")
      (node (ref "E11") (pin "V2") (pinfunction "OUT_V2") (pintype "output"))
      (node (ref "E12") (pin "R2") (pinfunction "IN2_R2") (pintype "input"))
    )
    (net (code "834") (name "Net-(E12A-IN1)") (class "Default")
      (node (ref "E12") (pin "A1") (pinfunction "IN1_A1") (pintype "input"))
      (node (ref "E12") (pin "F1") (pinfunction "OUT_F1") (pintype "output"))
    )
    (net (code "835") (name "Net-(E12A-OUT)") (class "Default")
      (node (ref "E12") (pin "C1") (pinfunction "OUT_C1") (pintype "output"))
      (node (ref "E18") (pin "K1") (pinfunction "S_K1") (pintype "input"))
    )
    (net (code "836") (name "Net-(E12C-OUT)") (class "Default")
      (node (ref "E12") (pin "F2") (pinfunction "OUT_F2") (pintype "output"))
      (node (ref "E16") (pin "H2") (pinfunction "H2_H2") (pintype "input"))
    )
    (net (code "837") (name "Net-(E12K-OUT)") (class "Default")
      (node (ref "E12") (pin "S2") (pinfunction "OUT_S2") (pintype "output"))
      (node (ref "F21") (pin "A1") (pinfunction "IN1_A1") (pintype "input"))
    )
    (net (code "838") (name "Net-(E13C-OUT)") (class "Default")
      (node (ref "E13") (pin "R1") (pinfunction "OUT_R1") (pintype "output"))
      (node (ref "E18") (pin "M2") (pinfunction "D_M2") (pintype "input"))
    )
    (net (code "839") (name "Net-(E14A-OUT)") (class "Default")
      (node (ref "E14") (pin "D1") (pinfunction "OUT_D1") (pintype "output"))
      (node (ref "E15") (pin "D2") (pinfunction "IN1_D2") (pintype "input"))
      (node (ref "F08") (pin "J2") (pinfunction "IN2_J2") (pintype "input"))
    )
    (net (code "840") (name "Net-(E14D-OUT)") (class "Default")
      (node (ref "E14") (pin "H2") (pinfunction "OUT_H2") (pintype "output"))
      (node (ref "F09") (pin "K2") (pinfunction "IN5_K2") (pintype "input"))
    )
    (net (code "841") (name "Net-(E14E-IN1)") (class "Default")
      (node (ref "E14") (pin "E1") (pinfunction "IN1_E1") (pintype "input"))
      (node (ref "F19") (pin "K1") (pinfunction "IN4_K1") (pintype "input"))
      (node (ref "F21") (pin "S2") (pinfunction "OUT_S2") (pintype "output"))
      (node (ref "F21") (pin "U2") (pinfunction "IN2_U2") (pintype "input"))
    )
    (net (code "842") (name "Net-(E14E-IN2)") (class "Default")
      (node (ref "E14") (pin "F1") (pinfunction "IN2_F1") (pintype "input"))
      (node (ref "F19") (pin "J1") (pinfunction "IN3_J1") (pintype "input"))
      (node (ref "F21") (pin "S1") (pinfunction "OUT_S1") (pintype "output"))
      (node (ref "F21") (pin "T2") (pinfunction "IN1_T2") (pintype "input"))
    )
    (net (code "843") (name "Net-(E14G-OUT)") (class "Default")
      (node (ref "E14") (pin "N1") (pinfunction "OUT_N1") (pintype "output"))
      (node (ref "E14") (pin "N2") (pinfunction "IN1_N2") (pintype "input"))
    )
    (net (code "844") (name "Net-(E14I-OUT)") (class "Default")
      (node (ref "E14") (pin "U1") (pinfunction "OUT_U1") (pintype "output"))
      (node (ref "F12") (pin "H2") (pinfunction "H2_H2") (pintype "input"))
    )
    (net (code "845") (name "Net-(E14J-OUT)") (class "Default")
      (node (ref "E14") (pin "V1") (pinfunction "OUT_V1") (pintype "output"))
      (node (ref "E15") (pin "T2") (pinfunction "IN1_T2") (pintype "input"))
    )
    (net (code "846") (name "Net-(E15A-OUT)") (class "Default")
      (node (ref "E15") (pin "C1") (pinfunction "OUT_C1") (pintype "output"))
      (node (ref "F08") (pin "H2") (pinfunction "IN1_H2") (pintype "input"))
    )
    (net (code "847") (name "Net-(E15C-IN2)") (class "Default")
      (node (ref "E15") (pin "E2") (pinfunction "IN2_E2") (pintype "input"))
      (node (ref "E15") (pin "K1") (pinfunction "OUT_K1") (pintype "output"))
    )
    (net (code "848") (name "Net-(E15H-OUT)") (class "Default")
      (node (ref "E15") (pin "N1") (pinfunction "OUT_N1") (pintype "output"))
      (node (ref "E19") (pin "F2") (pinfunction "S_F2") (pintype "input"))
      (node (ref "F08") (pin "N2") (pinfunction "IN1_N2") (pintype "input"))
    )
    (net (code "849") (name "Net-(E15K-OUT)") (class "Default")
      (node (ref "E15") (pin "S2") (pinfunction "OUT_S2") (pintype "output"))
      (node (ref "F13") (pin "H2") (pinfunction "H2_H2") (pintype "input"))
    )
    (net (code "850") (name "Net-(E16A-IN)") (class "Default")
      (node (ref "E16") (pin "E1") (pinfunction "IN_E1") (pintype "input"))
      (node (ref "E16") (pin "R2") (pinfunction "R2_R2") (pintype "output"))
    )
    (net (code "851") (name "Net-(E16A-OUT)") (class "Default")
      (node (ref "E16") (pin "F1") (pinfunction "OUT_F1") (pintype "output"))
      (node (ref "E18") (pin "H1") (pinfunction "C_H1") (pintype "input"))
    )
    (net (code "852") (name "Net-(E17A-IN)") (class "Default")
      (node (ref "E17") (pin "E1") (pinfunction "IN_E1") (pintype "input"))
      (node (ref "E17") (pin "M2") (pinfunction "M2_M2") (pintype "output"))
    )
    (net (code "853") (name "Net-(E17E-IN)") (class "Default")
      (node (ref "E17") (pin "H1") (pinfunction "IN_H1") (pintype "input"))
      (node (ref "E17") (pin "U2") (pinfunction "U2_U2") (pintype "output"))
    )
    (net (code "854") (name "Net-(E18G-C)") (class "Default")
      (node (ref "E18") (pin "N1") (pinfunction "C_N1") (pintype "input"))
      (node (ref "E25") (pin "U1") (pinfunction "OUT_U1") (pintype "output"))
    )
    (net (code "855") (name "Net-(E18G-D)") (class "Default")
      (node (ref "E18") (pin "P1") (pinfunction "D_P1") (pintype "input"))
      (node (ref "E28") (pin "T2") (pinfunction "OUT_T2") (pintype "output"))
    )
    (net (code "856") (name "Net-(E20A-C)") (class "Default")
      (node (ref "E20") (pin "B1") (pinfunction "C_B1") (pintype "input"))
      (node (ref "E20") (pin "D2") (pinfunction "C_D2") (pintype "input"))
      (node (ref "E20") (pin "H1") (pinfunction "C_H1") (pintype "input"))
      (node (ref "E22") (pin "S1") (pinfunction "OUT_S1") (pintype "output"))
    )
    (net (code "857") (name "Net-(E20A-D)") (class "Default")
      (node (ref "E20") (pin "C1") (pinfunction "D_C1") (pintype "input"))
      (node (ref "F22") (pin "C1") (pinfunction "OUT_C1") (pintype "output"))
    )
    (net (code "858") (name "Net-(E20A-R)") (class "Default")
      (node (ref "E20") (pin "A1") (pinfunction "R_A1") (pintype "input"))
      (node (ref "E24") (pin "K2") (pinfunction "OUT_K2") (pintype "output"))
    )
    (net (code "859") (name "Net-(E23A-S)") (class "Default")
      (node (ref "E23") (pin "D1") (pinfunction "S_D1") (pintype "input"))
      (node (ref "F22") (pin "F2") (pinfunction "OUT_F2") (pintype "output"))
    )
    (net (code "860") (name "Net-(E24A-OUT)") (class "Default")
      (node (ref "E24") (pin "C1") (pinfunction "OUT_C1") (pintype "output"))
      (node (ref "E25") (pin "A1") (pinfunction "IN1_A1") (pintype "input"))
    )
    (net (code "861") (name "Net-(E24B-OUT)") (class "Default")
      (node (ref "E24") (pin "F1") (pinfunction "OUT_F1") (pintype "output"))
      (node (ref "F23") (pin "E2") (pinfunction "IN2_E2") (pintype "input"))
    )
    (net (code "862") (name "Net-(E24F-IN1)") (class "Default")
      (node (ref "E24") (pin "H1") (pinfunction "IN1_H1") (pintype "input"))
      (node (ref "E25") (pin "J1") (pinfunction "OUT_J1") (pintype "output"))
    )
    (net (code "863") (name "Net-(E24H-OUT)") (class "Default")
      (node (ref "E24") (pin "N1") (pinfunction "OUT_N1") (pintype "output"))
      (node (ref "E25") (pin "K1") (pinfunction "IN1_K1") (pintype "input"))
    )
    (net (code "864") (name "Net-(E24I-IN1)") (class "Default")
      (node (ref "E24") (pin "L2") (pinfunction "IN1_L2") (pintype "input"))
      (node (ref "F24") (pin "P2") (pinfunction "OUT_P2") (pintype "output"))
    )
    (net (code "865") (name "Net-(E24I-OUT)") (class "Default")
      (node (ref "E24") (pin "N2") (pinfunction "OUT_N2") (pintype "output"))
      (node (ref "F23") (pin "A1") (pinfunction "IN1_A1") (pintype "input"))
    )
    (net (code "866") (name "Net-(E24J-IN2)") (class "Default")
      (node (ref "E24") (pin "R1") (pinfunction "IN2_R1") (pintype "input"))
      (node (ref "F24") (pin "S1") (pinfunction "OUT_S1") (pintype "output"))
    )
    (net (code "867") (name "Net-(E24K-IN2)") (class "Default")
      (node (ref "E24") (pin "R2") (pinfunction "IN2_R2") (pintype "input"))
      (node (ref "F24") (pin "V2") (pinfunction "OUT_V2") (pintype "output"))
    )
    (net (code "868") (name "Net-(E24N-OUT)") (class "Default")
      (node (ref "E24") (pin "V2") (pinfunction "OUT_V2") (pintype "output"))
      (node (ref "E25") (pin "M1") (pinfunction "IN3_M1") (pintype "input"))
    )
    (net (code "869") (name "Net-(E25G-IN2)") (class "Default")
      (node (ref "E25") (pin "L1") (pinfunction "IN2_L1") (pintype "input"))
      (node (ref "F23") (pin "E1") (pinfunction "OUT_E1") (pintype "output"))
    )
    (net (code "870") (name "Net-(E25G-OUT)") (class "Default")
      (node (ref "E25") (pin "N1") (pinfunction "OUT_N1") (pintype "output"))
      (node (ref "E25") (pin "P2") (pinfunction "IN2_P2") (pintype "input"))
    )
    (net (code "871") (name "Net-(E25H-OUT)") (class "Default")
      (node (ref "E25") (pin "S2") (pinfunction "OUT_S2") (pintype "output"))
      (node (ref "E28") (pin "N2") (pinfunction "IN4A_N2") (pintype "input"))
      (node (ref "F25") (pin "L2") (pinfunction "IN1_L2") (pintype "input"))
    )
    (net (code "872") (name "Net-(E25I-IN1)") (class "Default")
      (node (ref "E25") (pin "P1") (pinfunction "IN1_P1") (pintype "input"))
      (node (ref "E25") (pin "V1") (pinfunction "OUT_V1") (pintype "output"))
    )
    (net (code "873") (name "Net-(E25I-IN3)") (class "Default")
      (node (ref "E25") (pin "S1") (pinfunction "IN3_S1") (pintype "input"))
      (node (ref "F25") (pin "V2") (pinfunction "OUT_V2") (pintype "output"))
    )
    (net (code "874") (name "Net-(E26C-OUT)") (class "Default")
      (node (ref "E26") (pin "R1") (pinfunction "OUT_R1") (pintype "output"))
      (node (ref "E32") (pin "F2") (pinfunction "IN3_F2") (pintype "input"))
    )
    (net (code "875") (name "Net-(E26D-IN1C)") (class "Default")
      (node (ref "E26") (pin "F2") (pinfunction "IN1C_F2") (pintype "input"))
      (node (ref "F26") (pin "V1") (pinfunction "OUT_V1") (pintype "output"))
    )
    (net (code "876") (name "Net-(E26D-OUT)") (class "Default")
      (node (ref "E26") (pin "T2") (pinfunction "OUT_T2") (pintype "output"))
      (node (ref "E32") (pin "L2") (pinfunction "IN2_L2") (pintype "input"))
    )
    (net (code "877") (name "Net-(E27C-IN4A)") (class "Default")
      (node (ref "E27") (pin "K1") (pinfunction "IN4A_K1") (pintype "input"))
      (node (ref "F11") (pin "S1") (pinfunction "OUT_S1") (pintype "output"))
    )
    (net (code "878") (name "Net-(E27C-OUT)") (class "Default")
      (node (ref "E27") (pin "R1") (pinfunction "OUT_R1") (pintype "output"))
      (node (ref "F27") (pin "L2") (pinfunction "IN2_L2") (pintype "input"))
    )
    (net (code "879") (name "Net-(E27D-OUT)") (class "Default")
      (node (ref "E27") (pin "T2") (pinfunction "OUT_T2") (pintype "output"))
      (node (ref "F27") (pin "M2") (pinfunction "IN3_M2") (pintype "input"))
    )
    (net (code "880") (name "Net-(E28D-IN3A)") (class "Default")
      (node (ref "E28") (pin "L2") (pinfunction "IN3A_L2") (pintype "input"))
      (node (ref "F25") (pin "N2") (pinfunction "OUT_N2") (pintype "output"))
    )
    (net (code "881") (name "Net-(E29C-IN2B)") (class "Default")
      (node (ref "E29") (pin "F1") (pinfunction "IN2B_F1") (pintype "input"))
      (node (ref "E29") (pin "T2") (pinfunction "OUT_T2") (pintype "output"))
    )
    (net (code "882") (name "Net-(E29C-OUT)") (class "Default")
      (node (ref "E29") (pin "R1") (pinfunction "OUT_R1") (pintype "output"))
      (node (ref "F31") (pin "B1") (pinfunction "IN2_B1") (pintype "input"))
    )
    (net (code "883") (name "Net-(E30C-OUT)") (class "Default")
      (node (ref "E30") (pin "R1") (pinfunction "OUT_R1") (pintype "output"))
      (node (ref "F31") (pin "H1") (pinfunction "IN2_H1") (pintype "input"))
      (node (ref "F31") (pin "K2") (pinfunction "IN1_K2") (pintype "input"))
    )
    (net (code "884") (name "Net-(E30D-IN3B)") (class "Default")
      (node (ref "E30") (pin "M2") (pinfunction "IN3B_M2") (pintype "input"))
      (node (ref "E30") (pin "V2") (pinfunction "OUT_V2") (pintype "output"))
    )
    (net (code "885") (name "Net-(E30D-OUT)") (class "Default")
      (node (ref "E30") (pin "T2") (pinfunction "OUT_T2") (pintype "output"))
      (node (ref "E32") (pin "N1") (pinfunction "IN2_N1") (pintype "input"))
    )
    (net (code "886") (name "Net-(E31A-IN1)") (class "Default")
      (node (ref "E31") (pin "A1") (pinfunction "IN1_A1") (pintype "input"))
      (node (ref "F26") (pin "H2") (pinfunction "OUT_H2") (pintype "output"))
    )
    (net (code "887") (name "Net-(E31D-IN4)") (class "Default")
      (node (ref "E31") (pin "H2") (pinfunction "IN4_H2") (pintype "input"))
      (node (ref "F26") (pin "D1") (pinfunction "OUT_D1") (pintype "output"))
    )
    (net (code "888") (name "Net-(E31E-IN3)") (class "Default")
      (node (ref "E31") (pin "J1") (pinfunction "IN3_J1") (pintype "input"))
      (node (ref "F26") (pin "J1") (pinfunction "OUT_J1") (pintype "output"))
    )
    (net (code "889") (name "Net-(E31F-IN3)") (class "Default")
      (node (ref "E31") (pin "M2") (pinfunction "IN3_M2") (pintype "input"))
      (node (ref "F26") (pin "M2") (pinfunction "OUT_M2") (pintype "output"))
    )
    (net (code "890") (name "Net-(E31G-IN1)") (class "Default")
      (node (ref "E31") (pin "M1") (pinfunction "IN1_M1") (pintype "input"))
      (node (ref "F26") (pin "N1") (pinfunction "OUT_N1") (pintype "output"))
    )
    (net (code "891") (name "Net-(E31G-IN2)") (class "Default")
      (node (ref "E31") (pin "N1") (pinfunction "IN2_N1") (pintype "input"))
      (node (ref "F24") (pin "E1") (pinfunction "OUT_E1") (pintype "output"))
    )
    (net (code "892") (name "Net-(E32A-IN1)") (class "Default")
      (node (ref "E32") (pin "A1") (pinfunction "IN1_A1") (pintype "input"))
      (node (ref "F32") (pin "F1") (pinfunction "OUT_F1") (pintype "output"))
    )
    (net (code "893") (name "Net-(E32A-IN4)") (class "Default")
      (node (ref "E32") (pin "D1") (pinfunction "IN4_D1") (pintype "input"))
      (node (ref "F32") (pin "F2") (pinfunction "OUT_F2") (pintype "output"))
    )
    (net (code "894") (name "Net-(E32D-IN2)") (class "Default")
      (node (ref "E32") (pin "E2") (pinfunction "IN2_E2") (pintype "input"))
      (node (ref "F32") (pin "N2") (pinfunction "OUT_N2") (pintype "output"))
    )
    (net (code "895") (name "Net-(E32D-IN4)") (class "Default")
      (node (ref "E32") (pin "H2") (pinfunction "IN4_H2") (pintype "input"))
      (node (ref "F26") (pin "S2") (pinfunction "OUT_S2") (pintype "output"))
    )
    (net (code "896") (name "Net-(E32E-IN4)") (class "Default")
      (node (ref "E32") (pin "K1") (pinfunction "IN4_K1") (pintype "input"))
      (node (ref "F32") (pin "K1") (pinfunction "OUT_K1") (pintype "output"))
    )
    (net (code "897") (name "Net-(E32J-IN3)") (class "Default")
      (node (ref "E32") (pin "T2") (pinfunction "IN3_T2") (pintype "input"))
      (node (ref "F32") (pin "K2") (pinfunction "OUT_K2") (pintype "output"))
    )
    (net (code "898") (name "Net-(E33A-S)") (class "Default")
      (node (ref "E33") (pin "D1") (pinfunction "S_D1") (pintype "input"))
      (node (ref "F20") (pin "C1") (pinfunction "OUT_C1") (pintype "output"))
    )
    (net (code "899") (name "Net-(E33D-D)") (class "Default")
      (node (ref "E33") (pin "E2") (pinfunction "D_E2") (pintype "input"))
      (node (ref "F21") (pin "C1") (pinfunction "OUT_C1") (pintype "output"))
    )
    (net (code "900") (name "Net-(E33E-D)") (class "Default")
      (node (ref "E33") (pin "J1") (pinfunction "D_J1") (pintype "input"))
      (node (ref "F11") (pin "V2") (pinfunction "OUT_V2") (pintype "output"))
    )
    (net (code "901") (name "Net-(E33F-C)") (class "Default")
      (node (ref "E33") (pin "L2") (pinfunction "C_L2") (pintype "input"))
      (node (ref "F21") (pin "F2") (pinfunction "OUT_F2") (pintype "output"))
    )
    (net (code "902") (name "Net-(E33G-C)") (class "Default")
      (node (ref "E33") (pin "N1") (pinfunction "C_N1") (pintype "input"))
      (node (ref "F21") (pin "K2") (pinfunction "OUT_K2") (pintype "output"))
    )
    (net (code "903") (name "Net-(E33H-D)") (class "Default")
      (node (ref "E33") (pin "T2") (pinfunction "D_T2") (pintype "input"))
      (node (ref "F33") (pin "R1") (pinfunction "OUT_R1") (pintype "output"))
    )
    (net (code "904") (name "Net-(EF10C-CS2)") (class "Default")
      (node (ref "EF10") (pin "AS2") (pinfunction "CS2_AS2") (pintype "input"))
      (node (ref "F19") (pin "J2") (pinfunction "OUT_J2") (pintype "output"))
    )
    (net (code "905") (name "Net-(EF34-PadBJ1)") (class "Default")
      (node (ref "EF34") (pin "BJ1") (pinfunction "BJ1_BJ1") (pintype "input"))
      (node (ref "EF35") (pin "BK2") (pinfunction "BK2_BK2") (pintype "output"))
    )
    (net (code "906") (name "Net-(EF35-PadBJ1)") (class "Default")
      (node (ref "EF35") (pin "BJ1") (pinfunction "BJ1_BJ1") (pintype "input"))
      (node (ref "EF36") (pin "BK2") (pinfunction "BK2_BK2") (pintype "output"))
    )
    (net (code "907") (name "Net-(EF37-PadBJ1)") (class "Default")
      (node (ref "EF37") (pin "BJ1") (pinfunction "BJ1_BJ1") (pintype "input"))
      (node (ref "EF38") (pin "BK2") (pinfunction "BK2_BK2") (pintype "output"))
    )
    (net (code "908") (name "Net-(EF38-PadBJ1)") (class "Default")
      (node (ref "EF38") (pin "BJ1") (pinfunction "BJ1_BJ1") (pintype "input"))
      (node (ref "EF39") (pin "BK2") (pinfunction "BK2_BK2") (pintype "output"))
    )
    (net (code "909") (name "Net-(F11F-IN3)") (class "Default")
      (node (ref "F11") (pin "M2") (pinfunction "IN3_M2") (pintype "input"))
      (node (ref "F27") (pin "E1") (pinfunction "OUT_E1") (pintype "output"))
      (node (ref "F31") (pin "E2") (pinfunction "IN2_E2") (pintype "input"))
    )
    (net (code "910") (name "Net-(F11F-IN4)") (class "Default")
      (node (ref "F11") (pin "N2") (pinfunction "IN4_N2") (pintype "input"))
      (node (ref "F27") (pin "J2") (pinfunction "OUT_J2") (pintype "output"))
      (node (ref "F31") (pin "H2") (pinfunction "IN4_H2") (pintype "input"))
    )
    (net (code "911") (name "Net-(F12A-IN)") (class "Default")
      (node (ref "F12") (pin "E1") (pinfunction "IN_E1") (pintype "input"))
      (node (ref "F12") (pin "T2") (pinfunction "T2_T2") (pintype "output"))
    )
    (net (code "912") (name "Net-(F13A-IN)") (class "Default")
      (node (ref "F13") (pin "E1") (pinfunction "IN_E1") (pintype "input"))
      (node (ref "F13") (pin "T2") (pinfunction "T2_T2") (pintype "output"))
    )
    (net (code "913") (name "Net-(F13A-OUT)") (class "Default")
      (node (ref "F13") (pin "F1") (pinfunction "OUT_F1") (pintype "output"))
      (node (ref "F14") (pin "H2") (pinfunction "H2_H2") (pintype "input"))
    )
    (net (code "914") (name "Net-(F13E-IN)") (class "Default")
      (node (ref "F13") (pin "H1") (pinfunction "IN_H1") (pintype "input"))
      (node (ref "F13") (pin "M2") (pinfunction "M2_M2") (pintype "output"))
    )
    (net (code "915") (name "Net-(F13E-OUT)") (class "Default")
      (node (ref "F13") (pin "J1") (pinfunction "OUT_J1") (pintype "output"))
      (node (ref "F20") (pin "D2") (pinfunction "IN1_D2") (pintype "input"))
    )
    (net (code "916") (name "Net-(F14A-IN)") (class "Default")
      (node (ref "F14") (pin "E1") (pinfunction "IN_E1") (pintype "input"))
      (node (ref "F14") (pin "T2") (pinfunction "T2_T2") (pintype "output"))
    )
    (net (code "917") (name "Net-(F14A-OUT)") (class "Default")
      (node (ref "F14") (pin "F1") (pinfunction "OUT_F1") (pintype "output"))
      (node (ref "F15") (pin "H2") (pinfunction "H2_H2") (pintype "input"))
    )
    (net (code "918") (name "Net-(F14E-IN)") (class "Default")
      (node (ref "F14") (pin "H1") (pinfunction "IN_H1") (pintype "input"))
      (node (ref "F14") (pin "S2") (pinfunction "S2_S2") (pintype "output"))
    )
    (net (code "919") (name "Net-(F15A-IN)") (class "Default")
      (node (ref "F15") (pin "E1") (pinfunction "IN_E1") (pintype "input"))
      (node (ref "F15") (pin "T2") (pinfunction "T2_T2") (pintype "output"))
    )
    (net (code "920") (name "Net-(F15E-IN)") (class "Default")
      (node (ref "F15") (pin "H1") (pinfunction "IN_H1") (pintype "input"))
      (node (ref "F15") (pin "M2") (pinfunction "M2_M2") (pintype "output"))
    )
    (net (code "921") (name "Net-(F15E-OUT)") (class "Default")
      (node (ref "F15") (pin "J1") (pinfunction "OUT_J1") (pintype "output"))
      (node (ref "F20") (pin "H1") (pinfunction "IN1_H1") (pintype "input"))
    )
    (net (code "922") (name "Net-(F16A-IN)") (class "Default")
      (node (ref "F16") (pin "E1") (pinfunction "IN_E1") (pintype "input"))
      (node (ref "F16") (pin "T2") (pinfunction "T2_T2") (pintype "output"))
    )
    (net (code "923") (name "Net-(F16A-OUT)") (class "Default")
      (node (ref "F16") (pin "F1") (pinfunction "OUT_F1") (pintype "output"))
      (node (ref "F17") (pin "H2") (pinfunction "H2_H2") (pintype "input"))
    )
    (net (code "924") (name "Net-(F16E-IN)") (class "Default")
      (node (ref "F16") (pin "H1") (pinfunction "IN_H1") (pintype "input"))
      (node (ref "F16") (pin "S2") (pinfunction "S2_S2") (pintype "output"))
    )
    (net (code "925") (name "Net-(F17A-IN)") (class "Default")
      (node (ref "F17") (pin "E1") (pinfunction "IN_E1") (pintype "input"))
      (node (ref "F17") (pin "T2") (pinfunction "T2_T2") (pintype "output"))
    )
    (net (code "926") (name "Net-(F17E-IN)") (class "Default")
      (node (ref "F17") (pin "H1") (pinfunction "IN_H1") (pintype "input"))
      (node (ref "F17") (pin "M2") (pinfunction "M2_M2") (pintype "output"))
    )
    (net (code "927") (name "Net-(F17E-OUT)") (class "Default")
      (node (ref "F17") (pin "J1") (pinfunction "OUT_J1") (pintype "output"))
      (node (ref "F20") (pin "H2") (pinfunction "IN1_H2") (pintype "input"))
    )
    (net (code "928") (name "Net-(F18A-IN)") (class "Default")
      (node (ref "F18") (pin "E1") (pinfunction "IN_E1") (pintype "input"))
      (node (ref "F18") (pin "T2") (pinfunction "T2_T2") (pintype "output"))
    )
    (net (code "929") (name "Net-(F18E-IN)") (class "Default")
      (node (ref "F18") (pin "H1") (pinfunction "IN_H1") (pintype "input"))
      (node (ref "F18") (pin "S2") (pinfunction "S2_S2") (pintype "output"))
    )
    (net (code "930") (name "Net-(F19A-IN1)") (class "Default")
      (node (ref "F19") (pin "A1") (pinfunction "IN1_A1") (pintype "input"))
      (node (ref "F20") (pin "N1") (pinfunction "OUT_N1") (pintype "output"))
    )
    (net (code "931") (name "Net-(F19E-IN2)") (class "Default")
      (node (ref "F19") (pin "H1") (pinfunction "IN2_H1") (pintype "input"))
      (node (ref "F21") (pin "N2") (pinfunction "OUT_N2") (pintype "output"))
    )
    (net (code "932") (name "Net-(F19E-OUT)") (class "Default")
      (node (ref "F19") (pin "L1") (pinfunction "OUT_L1") (pintype "output"))
      (node (ref "F21") (pin "H2") (pinfunction "IN1_H2") (pintype "input"))
    )
    (net (code "933") (name "Net-(F19J-OUT)") (class "Default")
      (node (ref "F19") (pin "V2") (pinfunction "OUT_V2") (pintype "output"))
      (node (ref "F21") (pin "P1") (pinfunction "IN1_P1") (pintype "input"))
    )
    (net (code "934") (name "Net-(F20A-IN2)") (class "Default")
      (node (ref "F20") (pin "B1") (pinfunction "IN2_B1") (pintype "input"))
      (node (ref "F20") (pin "F1") (pinfunction "OUT_F1") (pintype "output"))
    )
    (net (code "935") (name "Net-(F20H-IN1)") (class "Default")
      (node (ref "F20") (pin "L1") (pinfunction "IN1_L1") (pintype "input"))
      (node (ref "F20") (pin "S1") (pinfunction "OUT_S1") (pintype "output"))
    )
    (net (code "936") (name "Net-(F20I-OUT)") (class "Default")
      (node (ref "F20") (pin "N2") (pinfunction "OUT_N2") (pintype "output"))
      (node (ref "F30") (pin "A1") (pinfunction "IN1_A1") (pintype "input"))
    )
    (net (code "937") (name "Net-(F20K-IN1)") (class "Default")
      (node (ref "F20") (pin "P2") (pinfunction "IN1_P2") (pintype "input"))
      (node (ref "F20") (pin "V2") (pinfunction "OUT_V2") (pintype "output"))
    )
    (net (code "938") (name "Net-(F21C-IN1)") (class "Default")
      (node (ref "F21") (pin "D2") (pinfunction "IN1_D2") (pintype "input"))
      (node (ref "F21") (pin "K1") (pinfunction "OUT_K1") (pintype "output"))
    )
    (net (code "939") (name "Net-(F21K-IN2)") (class "Default")
      (node (ref "F21") (pin "R2") (pinfunction "IN2_R2") (pintype "input"))
      (node (ref "F23") (pin "V2") (pinfunction "OUT_V2") (pintype "output"))
    )
    (net (code "940") (name "Net-(F22J-OUT)") (class "Default")
      (node (ref "F22") (pin "P2") (pinfunction "IN1_P2") (pintype "input"))
      (node (ref "F22") (pin "S1") (pinfunction "OUT_S1") (pintype "output"))
    )
    (net (code "941") (name "Net-(F23D-IN3)") (class "Default")
      (node (ref "F23") (pin "F2") (pinfunction "IN3_F2") (pintype "input"))
      (node (ref "F23") (pin "L1") (pinfunction "OUT_L1") (pintype "output"))
    )
    (net (code "942") (name "Net-(F24D-OUT)") (class "Default")
      (node (ref "F24") (pin "J2") (pinfunction "OUT_J2") (pintype "output"))
      (node (ref "F25") (pin "D2") (pinfunction "IN1_D2") (pintype "input"))
    )
    (net (code "943") (name "Net-(F24E-OUT)") (class "Default")
      (node (ref "F24") (pin "L1") (pinfunction "OUT_L1") (pintype "output"))
      (node (ref "F25") (pin "H1") (pinfunction "IN1_H1") (pintype "input"))
    )
    (net (code "944") (name "Net-(F25C-OUT)") (class "Default")
      (node (ref "F25") (pin "F2") (pinfunction "OUT_F2") (pintype "output"))
      (node (ref "F27") (pin "M1") (pinfunction "IN1_M1") (pintype "input"))
    )
    (net (code "945") (name "Net-(F25F-OUT)") (class "Default")
      (node (ref "F25") (pin "K1") (pinfunction "OUT_K1") (pintype "output"))
      (node (ref "F27") (pin "N1") (pinfunction "IN2_N1") (pintype "input"))
    )
    (net (code "946") (name "Net-(F25G-IN1)") (class "Default")
      (node (ref "F25") (pin "H2") (pinfunction "IN1_H2") (pintype "input"))
      (node (ref "F25") (pin "N1") (pinfunction "OUT_N1") (pintype "output"))
    )
    (net (code "947") (name "Net-(F25G-OUT)") (class "Default")
      (node (ref "F25") (pin "K2") (pinfunction "OUT_K2") (pintype "output"))
      (node (ref "F27") (pin "P1") (pinfunction "IN3_P1") (pintype "input"))
    )
    (net (code "948") (name "Net-(F27D-IN2)") (class "Default")
      (node (ref "F27") (pin "E2") (pinfunction "IN2_E2") (pintype "input"))
      (node (ref "F29") (pin "F1") (pinfunction "OUT_F1") (pintype "output"))
    )
    (net (code "949") (name "Net-(F27E-OUT)") (class "Default")
      (node (ref "F27") (pin "L1") (pinfunction "OUT_L1") (pintype "output"))
      (node (ref "F29") (pin "J1") (pinfunction "IN2_J1") (pintype "input"))
    )
    (net (code "950") (name "Net-(F27F-OUT)") (class "Default")
      (node (ref "F27") (pin "P2") (pinfunction "OUT_P2") (pintype "output"))
      (node (ref "F32") (pin "A1") (pinfunction "IN1_A1") (pintype "input"))
    )
    (net (code "951") (name "Net-(F28D-OUT)") (class "Default")
      (node (ref "F28") (pin "H2") (pinfunction "OUT_H2") (pintype "output"))
      (node (ref "F31") (pin "F1") (pinfunction "IN1_F1") (pintype "input"))
    )
    (net (code "952") (name "Net-(F28F-OUT)") (class "Default")
      (node (ref "F28") (pin "M2") (pinfunction "OUT_M2") (pintype "output"))
      (node (ref "F32") (pin "M1") (pinfunction "IN2_M1") (pintype "input"))
    )
    (net (code "953") (name "Net-(F28G-OUT)") (class "Default")
      (node (ref "F28") (pin "N1") (pinfunction "OUT_N1") (pintype "output"))
      (node (ref "F30") (pin "F1") (pinfunction "IN1_F1") (pintype "input"))
    )
    (net (code "954") (name "Net-(F28I-OUT)") (class "Default")
      (node (ref "F28") (pin "U1") (pinfunction "OUT_U1") (pintype "output"))
      (node (ref "F33") (pin "A1") (pinfunction "IN1A_A1") (pintype "input"))
    )
    (net (code "955") (name "Net-(F29H-OUT)") (class "Default")
      (node (ref "F29") (pin "N1") (pinfunction "OUT_N1") (pintype "output"))
      (node (ref "F30") (pin "K2") (pinfunction "IN1_K2") (pintype "input"))
    )
    (net (code "956") (name "Net-(F29I-IN1)") (class "Default")
      (node (ref "F29") (pin "L2") (pinfunction "IN1_L2") (pintype "input"))
      (node (ref "F29") (pin "V2") (pinfunction "OUT_V2") (pintype "output"))
    )
    (net (code "957") (name "Net-(F29J-OUT)") (class "Default")
      (node (ref "F29") (pin "S1") (pinfunction "OUT_S1") (pintype "output"))
      (node (ref "F30") (pin "M1") (pinfunction "IN1_M1") (pintype "input"))
    )
    (net (code "958") (name "Net-(F32K-IN2)") (class "Default")
      (node (ref "F32") (pin "R2") (pinfunction "IN2_R2") (pintype "input"))
      (node (ref "F33") (pin "S1") (pinfunction "IN1A_S1") (pintype "input"))
      (node (ref "F33") (pin "T2") (pinfunction "OUT_T2") (pintype "output"))
    )
    (net (code "959") (name "Net-(F32K-OUT)") (class "Default")
      (node (ref "F32") (pin "S2") (pinfunction "OUT_S2") (pintype "output"))
      (node (ref "F33") (pin "V1") (pinfunction "IN2A_V1") (pintype "input"))
    )
    (net (code "960") (name "Net-(H07A-OUT)") (class "Default")
      (node (ref "H07") (pin "D2") (pinfunction "OUT_D2") (pintype "output"))
      (node (ref "J01") (pin "D2") (pinfunction "P$2_D2") (pintype "bidirectional"))
    )
    (net (code "961") (name "Net-(H07B-OUT)") (class "Default")
      (node (ref "H07") (pin "K2") (pinfunction "OUT_K2") (pintype "output"))
      (node (ref "J01") (pin "E2") (pinfunction "P$2_E2") (pintype "bidirectional"))
    )
    (net (code "962") (name "Net-(H07C-OUT)") (class "Default")
      (node (ref "H07") (pin "S2") (pinfunction "OUT_S2") (pintype "output"))
      (node (ref "J01") (pin "H2") (pinfunction "P$2_H2") (pintype "bidirectional"))
    )
    (net (code "963") (name "Net-(H08A-OUT)") (class "Default")
      (node (ref "H08") (pin "D2") (pinfunction "OUT_D2") (pintype "output"))
      (node (ref "J01") (pin "K2") (pinfunction "P$2_K2") (pintype "bidirectional"))
    )
    (net (code "964") (name "Net-(H08B-OUT)") (class "Default")
      (node (ref "H08") (pin "K2") (pinfunction "OUT_K2") (pintype "output"))
      (node (ref "J01") (pin "M2") (pinfunction "P$2_M2") (pintype "bidirectional"))
    )
    (net (code "965") (name "Net-(H08C-OUT)") (class "Default")
      (node (ref "H08") (pin "S2") (pinfunction "OUT_S2") (pintype "output"))
      (node (ref "J01") (pin "P2") (pinfunction "P$2_P2") (pintype "bidirectional"))
    )
    (net (code "966") (name "Net-(H09A-OUT)") (class "Default")
      (node (ref "H09") (pin "D2") (pinfunction "OUT_D2") (pintype "output"))
      (node (ref "J01") (pin "S2") (pinfunction "P$2_S2") (pintype "bidirectional"))
    )
    (net (code "967") (name "Net-(H09B-OUT)") (class "Default")
      (node (ref "H09") (pin "K2") (pinfunction "OUT_K2") (pintype "output"))
      (node (ref "J01") (pin "T2") (pinfunction "P$2_T2") (pintype "bidirectional"))
    )
    (net (code "968") (name "Net-(H09C-OUT)") (class "Default")
      (node (ref "H09") (pin "S2") (pinfunction "OUT_S2") (pintype "output"))
      (node (ref "J01") (pin "V2") (pinfunction "P$2_V2") (pintype "bidirectional"))
    )
    (net (code "969") (name "Net-(H10A-OUT)") (class "Default")
      (node (ref "H10") (pin "D2") (pinfunction "OUT_D2") (pintype "output"))
      (node (ref "J02") (pin "D2") (pinfunction "P$2_D2") (pintype "bidirectional"))
    )
    (net (code "970") (name "Net-(H10B-OUT)") (class "Default")
      (node (ref "H10") (pin "K2") (pinfunction "OUT_K2") (pintype "output"))
      (node (ref "J02") (pin "E2") (pinfunction "P$2_E2") (pintype "bidirectional"))
    )
    (net (code "971") (name "Net-(H10C-OUT)") (class "Default")
      (node (ref "H10") (pin "S2") (pinfunction "OUT_S2") (pintype "output"))
      (node (ref "J02") (pin "H2") (pinfunction "P$2_H2") (pintype "bidirectional"))
    )
    (net (code "972") (name "Net-(H11A-OUT)") (class "Default")
      (node (ref "H11") (pin "D2") (pinfunction "OUT_D2") (pintype "output"))
      (node (ref "J02") (pin "K2") (pinfunction "P$2_K2") (pintype "bidirectional"))
    )
    (net (code "973") (name "Net-(H11B-OUT)") (class "Default")
      (node (ref "H11") (pin "K2") (pinfunction "OUT_K2") (pintype "output"))
      (node (ref "J02") (pin "M2") (pinfunction "P$2_M2") (pintype "bidirectional"))
    )
    (net (code "974") (name "Net-(H11C-OUT)") (class "Default")
      (node (ref "H11") (pin "S2") (pinfunction "OUT_S2") (pintype "output"))
      (node (ref "J02") (pin "P2") (pinfunction "P$2_P2") (pintype "bidirectional"))
    )
    (net (code "975") (name "Net-(H12A-OUT)") (class "Default")
      (node (ref "H12") (pin "D2") (pinfunction "OUT_D2") (pintype "output"))
      (node (ref "J02") (pin "S2") (pinfunction "P$2_S2") (pintype "bidirectional"))
    )
    (net (code "976") (name "Net-(H12B-OUT)") (class "Default")
      (node (ref "H12") (pin "K2") (pinfunction "OUT_K2") (pintype "output"))
      (node (ref "J02") (pin "T2") (pinfunction "P$2_T2") (pintype "bidirectional"))
    )
    (net (code "977") (name "Net-(H12C-OUT)") (class "Default")
      (node (ref "H12") (pin "S2") (pinfunction "OUT_S2") (pintype "output"))
      (node (ref "J02") (pin "V2") (pinfunction "P$2_V2") (pintype "bidirectional"))
    )
    (net (code "978") (name "Net-(H13A-OUT)") (class "Default")
      (node (ref "H13") (pin "D2") (pinfunction "OUT_D2") (pintype "output"))
      (node (ref "J03") (pin "D2") (pinfunction "P$2_D2") (pintype "bidirectional"))
    )
    (net (code "979") (name "Net-(H13B-OUT)") (class "Default")
      (node (ref "H13") (pin "K2") (pinfunction "OUT_K2") (pintype "output"))
      (node (ref "J03") (pin "E2") (pinfunction "P$2_E2") (pintype "bidirectional"))
    )
    (net (code "980") (name "Net-(H13C-OUT)") (class "Default")
      (node (ref "H13") (pin "S2") (pinfunction "OUT_S2") (pintype "output"))
      (node (ref "J03") (pin "H2") (pinfunction "P$2_H2") (pintype "bidirectional"))
    )
    (net (code "981") (name "Net-(H14A-OUT)") (class "Default")
      (node (ref "H14") (pin "D2") (pinfunction "OUT_D2") (pintype "output"))
      (node (ref "J03") (pin "K2") (pinfunction "P$2_K2") (pintype "bidirectional"))
    )
    (net (code "982") (name "Net-(H14B-OUT)") (class "Default")
      (node (ref "H14") (pin "K2") (pinfunction "OUT_K2") (pintype "output"))
      (node (ref "J03") (pin "M2") (pinfunction "P$2_M2") (pintype "bidirectional"))
    )
    (net (code "983") (name "Net-(H14C-OUT)") (class "Default")
      (node (ref "H14") (pin "S2") (pinfunction "OUT_S2") (pintype "output"))
      (node (ref "J03") (pin "P2") (pinfunction "P$2_P2") (pintype "bidirectional"))
    )
    (net (code "984") (name "Net-(H15A-OUT)") (class "Default")
      (node (ref "H15") (pin "D2") (pinfunction "OUT_D2") (pintype "output"))
      (node (ref "J03") (pin "S2") (pinfunction "P$2_S2") (pintype "bidirectional"))
    )
    (net (code "985") (name "Net-(H15B-OUT)") (class "Default")
      (node (ref "H15") (pin "K2") (pinfunction "OUT_K2") (pintype "output"))
      (node (ref "J03") (pin "T2") (pinfunction "P$2_T2") (pintype "bidirectional"))
    )
    (net (code "986") (name "Net-(H15C-OUT)") (class "Default")
      (node (ref "H15") (pin "S2") (pinfunction "OUT_S2") (pintype "output"))
      (node (ref "J03") (pin "V2") (pinfunction "P$2_V2") (pintype "bidirectional"))
    )
    (net (code "987") (name "Net-(H16A-OUT)") (class "Default")
      (node (ref "H16") (pin "D2") (pinfunction "OUT_D2") (pintype "output"))
      (node (ref "J04") (pin "D2") (pinfunction "P$2_D2") (pintype "bidirectional"))
    )
    (net (code "988") (name "Net-(H16B-OUT)") (class "Default")
      (node (ref "H16") (pin "K2") (pinfunction "OUT_K2") (pintype "output"))
      (node (ref "J04") (pin "E2") (pinfunction "P$2_E2") (pintype "bidirectional"))
    )
    (net (code "989") (name "Net-(H16C-OUT)") (class "Default")
      (node (ref "H16") (pin "S2") (pinfunction "OUT_S2") (pintype "output"))
      (node (ref "J04") (pin "H2") (pinfunction "P$2_H2") (pintype "bidirectional"))
    )
    (net (code "990") (name "Net-(H17A-OUT)") (class "Default")
      (node (ref "H17") (pin "D2") (pinfunction "OUT_D2") (pintype "output"))
      (node (ref "J04") (pin "K2") (pinfunction "P$2_K2") (pintype "bidirectional"))
    )
    (net (code "991") (name "Net-(H17B-OUT)") (class "Default")
      (node (ref "H17") (pin "K2") (pinfunction "OUT_K2") (pintype "output"))
      (node (ref "J04") (pin "M2") (pinfunction "P$2_M2") (pintype "bidirectional"))
    )
    (net (code "992") (name "Net-(H17C-OUT)") (class "Default")
      (node (ref "H17") (pin "S2") (pinfunction "OUT_S2") (pintype "output"))
      (node (ref "J04") (pin "P2") (pinfunction "P$2_P2") (pintype "bidirectional"))
    )
    (net (code "993") (name "Net-(H18A-OUT)") (class "Default")
      (node (ref "H18") (pin "D2") (pinfunction "OUT_D2") (pintype "output"))
      (node (ref "J04") (pin "S2") (pinfunction "P$2_S2") (pintype "bidirectional"))
    )
    (net (code "994") (name "Net-(H18B-OUT)") (class "Default")
      (node (ref "H18") (pin "K2") (pinfunction "OUT_K2") (pintype "output"))
      (node (ref "J04") (pin "T2") (pinfunction "P$2_T2") (pintype "bidirectional"))
    )
    (net (code "995") (name "Net-(H18C-OUT)") (class "Default")
      (node (ref "H18") (pin "S2") (pinfunction "OUT_S2") (pintype "output"))
      (node (ref "J04") (pin "V2") (pinfunction "P$2_V2") (pintype "bidirectional"))
    )
    (net (code "996") (name "Net-(H19A-OUT)") (class "Default")
      (node (ref "H19") (pin "D2") (pinfunction "OUT_D2") (pintype "output"))
      (node (ref "J06") (pin "S2") (pinfunction "P$2_S2") (pintype "bidirectional"))
    )
    (net (code "997") (name "Net-(H19B-OUT)") (class "Default")
      (node (ref "H19") (pin "K2") (pinfunction "OUT_K2") (pintype "output"))
      (node (ref "J06") (pin "T2") (pinfunction "P$2_T2") (pintype "bidirectional"))
    )
    (net (code "998") (name "Net-(H19C-OUT)") (class "Default")
      (node (ref "H19") (pin "S2") (pinfunction "OUT_S2") (pintype "output"))
      (node (ref "J10") (pin "P2") (pinfunction "P$2_P2") (pintype "bidirectional"))
    )
    (net (code "999") (name "Net-(H20A-OUT)") (class "Default")
      (node (ref "H20") (pin "D2") (pinfunction "OUT_D2") (pintype "output"))
      (node (ref "J08") (pin "P2") (pinfunction "P$2_P2") (pintype "bidirectional"))
    )
    (net (code "1000") (name "Net-(H20B-OUT)") (class "Default")
      (node (ref "H20") (pin "K2") (pinfunction "OUT_K2") (pintype "output"))
      (node (ref "J08") (pin "S2") (pinfunction "P$2_S2") (pintype "bidirectional"))
    )
    (net (code "1001") (name "Net-(J05A-P$2)") (class "Default")
      (node (ref "J05") (pin "D2") (pinfunction "P$2_D2") (pintype "bidirectional"))
      (node (ref "J13") (pin "A1") (pinfunction "IN_A1") (pintype "input"))
    )
    (net (code "1002") (name "Net-(J05B-P$2)") (class "Default")
      (node (ref "J05") (pin "E2") (pinfunction "P$2_E2") (pintype "bidirectional"))
      (node (ref "J13") (pin "D2") (pinfunction "IN_D2") (pintype "input"))
    )
    (net (code "1003") (name "Net-(J05J-P$2)") (class "Default")
      (node (ref "J05") (pin "H2") (pinfunction "P$2_H2") (pintype "bidirectional"))
      (node (ref "J13") (pin "F1") (pinfunction "IN_F1") (pintype "input"))
    )
    (net (code "1004") (name "Net-(J05K-P$2)") (class "Default")
      (node (ref "J05") (pin "K2") (pinfunction "P$2_K2") (pintype "bidirectional"))
      (node (ref "J13") (pin "K2") (pinfunction "IN_K2") (pintype "input"))
    )
    (net (code "1005") (name "Net-(J05L-P$2)") (class "Default")
      (node (ref "J05") (pin "M2") (pinfunction "P$2_M2") (pintype "bidirectional"))
      (node (ref "J13") (pin "M1") (pinfunction "IN_M1") (pintype "input"))
    )
    (net (code "1006") (name "Net-(J05M-P$2)") (class "Default")
      (node (ref "J05") (pin "P2") (pinfunction "P$2_P2") (pintype "bidirectional"))
      (node (ref "J13") (pin "R2") (pinfunction "IN_R2") (pintype "input"))
    )
    (net (code "1007") (name "Net-(J05N-P$2)") (class "Default")
      (node (ref "J05") (pin "S2") (pinfunction "P$2_S2") (pintype "bidirectional"))
      (node (ref "J14") (pin "A1") (pinfunction "IN_A1") (pintype "input"))
    )
    (net (code "1008") (name "Net-(J05O-P$2)") (class "Default")
      (node (ref "J05") (pin "T2") (pinfunction "P$2_T2") (pintype "bidirectional"))
      (node (ref "J14") (pin "D2") (pinfunction "IN_D2") (pintype "input"))
    )
    (net (code "1009") (name "Net-(J05P-P$2)") (class "Default")
      (node (ref "J05") (pin "V2") (pinfunction "P$2_V2") (pintype "bidirectional"))
      (node (ref "J14") (pin "F1") (pinfunction "IN_F1") (pintype "input"))
    )
    (net (code "1010") (name "Net-(J06A-P$2)") (class "Default")
      (node (ref "J06") (pin "D2") (pinfunction "P$2_D2") (pintype "bidirectional"))
      (node (ref "J14") (pin "K2") (pinfunction "IN_K2") (pintype "input"))
    )
    (net (code "1011") (name "Net-(J06B-P$2)") (class "Default")
      (node (ref "J06") (pin "E2") (pinfunction "P$2_E2") (pintype "bidirectional"))
      (node (ref "J14") (pin "M1") (pinfunction "IN_M1") (pintype "input"))
    )
    (net (code "1012") (name "Net-(J06J-P$2)") (class "Default")
      (node (ref "J06") (pin "H2") (pinfunction "P$2_H2") (pintype "bidirectional"))
      (node (ref "J14") (pin "R2") (pinfunction "IN_R2") (pintype "input"))
    )
    (net (code "1013") (name "Net-(J06K-P$2)") (class "Default")
      (node (ref "J06") (pin "K2") (pinfunction "P$2_K2") (pintype "bidirectional"))
      (node (ref "J15") (pin "A1") (pinfunction "IN_A1") (pintype "input"))
    )
    (net (code "1014") (name "Net-(J06L-P$2)") (class "Default")
      (node (ref "J06") (pin "M2") (pinfunction "P$2_M2") (pintype "bidirectional"))
      (node (ref "J15") (pin "D2") (pinfunction "IN_D2") (pintype "input"))
    )
    (net (code "1015") (name "Net-(J06M-P$2)") (class "Default")
      (node (ref "J06") (pin "P2") (pinfunction "P$2_P2") (pintype "bidirectional"))
      (node (ref "J15") (pin "F1") (pinfunction "IN_F1") (pintype "input"))
    )
    (net (code "1016") (name "Net-(J06P-P$2)") (class "Default")
      (node (ref "J06") (pin "V2") (pinfunction "P$2_V2") (pintype "bidirectional"))
      (node (ref "J15") (pin "K2") (pinfunction "IN_K2") (pintype "input"))
    )
    (net (code "1017") (name "Net-(J07A-P$2)") (class "Default")
      (node (ref "J07") (pin "D2") (pinfunction "P$2_D2") (pintype "bidirectional"))
      (node (ref "J16") (pin "A1") (pinfunction "IN_A1") (pintype "input"))
    )
    (net (code "1018") (name "Net-(J07B-P$2)") (class "Default")
      (node (ref "J07") (pin "E2") (pinfunction "P$2_E2") (pintype "bidirectional"))
      (node (ref "J16") (pin "D2") (pinfunction "IN_D2") (pintype "input"))
    )
    (net (code "1019") (name "Net-(J07J-P$2)") (class "Default")
      (node (ref "J07") (pin "H2") (pinfunction "P$2_H2") (pintype "bidirectional"))
      (node (ref "J16") (pin "F1") (pinfunction "IN_F1") (pintype "input"))
    )
    (net (code "1020") (name "Net-(J07K-P$2)") (class "Default")
      (node (ref "J07") (pin "K2") (pinfunction "P$2_K2") (pintype "bidirectional"))
      (node (ref "J16") (pin "K2") (pinfunction "IN_K2") (pintype "input"))
    )
    (net (code "1021") (name "Net-(J07L-P$2)") (class "Default")
      (node (ref "J07") (pin "M2") (pinfunction "P$2_M2") (pintype "bidirectional"))
      (node (ref "J16") (pin "M1") (pinfunction "IN_M1") (pintype "input"))
    )
    (net (code "1022") (name "Net-(J07M-P$2)") (class "Default")
      (node (ref "J07") (pin "P2") (pinfunction "P$2_P2") (pintype "bidirectional"))
      (node (ref "J16") (pin "R2") (pinfunction "IN_R2") (pintype "input"))
    )
    (net (code "1023") (name "Net-(J07N-P$2)") (class "Default")
      (node (ref "J07") (pin "S2") (pinfunction "P$2_S2") (pintype "bidirectional"))
      (node (ref "J17") (pin "A1") (pinfunction "IN_A1") (pintype "input"))
    )
    (net (code "1024") (name "Net-(J07O-P$2)") (class "Default")
      (node (ref "J07") (pin "T2") (pinfunction "P$2_T2") (pintype "bidirectional"))
      (node (ref "J17") (pin "D2") (pinfunction "IN_D2") (pintype "input"))
    )
    (net (code "1025") (name "Net-(J07P-P$2)") (class "Default")
      (node (ref "J07") (pin "V2") (pinfunction "P$2_V2") (pintype "bidirectional"))
      (node (ref "J17") (pin "F1") (pinfunction "IN_F1") (pintype "input"))
    )
    (net (code "1026") (name "Net-(J08A-P$2)") (class "Default")
      (node (ref "J08") (pin "D2") (pinfunction "P$2_D2") (pintype "bidirectional"))
      (node (ref "J17") (pin "K2") (pinfunction "IN_K2") (pintype "input"))
    )
    (net (code "1027") (name "Net-(J08B-P$2)") (class "Default")
      (node (ref "J08") (pin "E2") (pinfunction "P$2_E2") (pintype "bidirectional"))
      (node (ref "J17") (pin "M1") (pinfunction "IN_M1") (pintype "input"))
    )
    (net (code "1028") (name "Net-(J08J-P$2)") (class "Default")
      (node (ref "J08") (pin "H2") (pinfunction "P$2_H2") (pintype "bidirectional"))
      (node (ref "J17") (pin "R2") (pinfunction "IN_R2") (pintype "input"))
    )
    (net (code "1029") (name "Net-(J08K-P$2)") (class "Default")
      (node (ref "J08") (pin "K2") (pinfunction "P$2_K2") (pintype "bidirectional"))
      (node (ref "J15") (pin "M1") (pinfunction "IN_M1") (pintype "input"))
    )
    (net (code "1030") (name "Net-(J08L-P$2)") (class "Default")
      (node (ref "J08") (pin "M2") (pinfunction "P$2_M2") (pintype "bidirectional"))
      (node (ref "J15") (pin "R2") (pinfunction "IN_R2") (pintype "input"))
    )
    (net (code "1031") (name "Net-(J08O-P$2)") (class "Default")
      (node (ref "J08") (pin "T2") (pinfunction "P$2_T2") (pintype "bidirectional"))
      (node (ref "J20") (pin "A1") (pinfunction "IN_A1") (pintype "input"))
    )
    (net (code "1032") (name "Net-(J09A-P$2)") (class "Default")
      (node (ref "J09") (pin "D2") (pinfunction "P$2_D2") (pintype "bidirectional"))
      (node (ref "J18") (pin "A1") (pinfunction "IN_A1") (pintype "input"))
    )
    (net (code "1033") (name "Net-(J09B-P$2)") (class "Default")
      (node (ref "J09") (pin "E2") (pinfunction "P$2_E2") (pintype "bidirectional"))
      (node (ref "J18") (pin "D2") (pinfunction "IN_D2") (pintype "input"))
    )
    (net (code "1034") (name "Net-(J09J-P$2)") (class "Default")
      (node (ref "J09") (pin "H2") (pinfunction "P$2_H2") (pintype "bidirectional"))
      (node (ref "J18") (pin "F1") (pinfunction "IN_F1") (pintype "input"))
    )
    (net (code "1035") (name "Net-(J09K-P$2)") (class "Default")
      (node (ref "J09") (pin "K2") (pinfunction "P$2_K2") (pintype "bidirectional"))
      (node (ref "J18") (pin "K2") (pinfunction "IN_K2") (pintype "input"))
    )
    (net (code "1036") (name "Net-(J09L-P$2)") (class "Default")
      (node (ref "J09") (pin "M2") (pinfunction "P$2_M2") (pintype "bidirectional"))
      (node (ref "J18") (pin "M1") (pinfunction "IN_M1") (pintype "input"))
    )
    (net (code "1037") (name "Net-(J09M-P$2)") (class "Default")
      (node (ref "J09") (pin "P2") (pinfunction "P$2_P2") (pintype "bidirectional"))
      (node (ref "J18") (pin "R2") (pinfunction "IN_R2") (pintype "input"))
    )
    (net (code "1038") (name "Net-(J09N-P$2)") (class "Default")
      (node (ref "J09") (pin "S2") (pinfunction "P$2_S2") (pintype "bidirectional"))
      (node (ref "J19") (pin "A1") (pinfunction "IN_A1") (pintype "input"))
    )
    (net (code "1039") (name "Net-(J09O-P$2)") (class "Default")
      (node (ref "J09") (pin "T2") (pinfunction "P$2_T2") (pintype "bidirectional"))
      (node (ref "J19") (pin "D2") (pinfunction "IN_D2") (pintype "input"))
    )
    (net (code "1040") (name "Net-(J09P-P$2)") (class "Default")
      (node (ref "J09") (pin "V2") (pinfunction "P$2_V2") (pintype "bidirectional"))
      (node (ref "J19") (pin "F1") (pinfunction "IN_F1") (pintype "input"))
    )
    (net (code "1041") (name "Net-(J10A-P$2)") (class "Default")
      (node (ref "J10") (pin "D2") (pinfunction "P$2_D2") (pintype "bidirectional"))
      (node (ref "J19") (pin "K2") (pinfunction "IN_K2") (pintype "input"))
    )
    (net (code "1042") (name "Net-(J10B-P$2)") (class "Default")
      (node (ref "J10") (pin "E2") (pinfunction "P$2_E2") (pintype "bidirectional"))
      (node (ref "J19") (pin "M1") (pinfunction "IN_M1") (pintype "input"))
    )
    (net (code "1043") (name "Net-(J10J-P$2)") (class "Default")
      (node (ref "J10") (pin "H2") (pinfunction "P$2_H2") (pintype "bidirectional"))
      (node (ref "J19") (pin "R2") (pinfunction "IN_R2") (pintype "input"))
    )
    (net (code "1044") (name "Net-(J10K-P$2)") (class "Default")
      (node (ref "J10") (pin "K2") (pinfunction "P$2_K2") (pintype "bidirectional"))
      (node (ref "J20") (pin "D2") (pinfunction "IN_D2") (pintype "input"))
    )
    (net (code "1045") (name "Net-(J10L-P$2)") (class "Default")
      (node (ref "J10") (pin "M2") (pinfunction "P$2_M2") (pintype "bidirectional"))
      (node (ref "J20") (pin "F1") (pinfunction "IN_F1") (pintype "input"))
    )
    (net (code "1046") (name "Net-(J10N-P$2)") (class "Default")
      (node (ref "J10") (pin "S2") (pinfunction "P$2_S2") (pintype "bidirectional"))
      (node (ref "J11") (pin "D2") (pinfunction "P$2_D2") (pintype "bidirectional"))
      (node (ref "J20") (pin "R2") (pinfunction "IN_R2") (pintype "input"))
    )
    (net (code "1047") (name "Net-(J10O-P$2)") (class "Default")
      (node (ref "J10") (pin "T2") (pinfunction "P$2_T2") (pintype "bidirectional"))
      (node (ref "J11") (pin "E2") (pinfunction "P$2_E2") (pintype "bidirectional"))
      (node (ref "J20") (pin "M1") (pinfunction "IN_M1") (pintype "input"))
    )
    (net (code "1048") (name "Net-(J10P-P$2)") (class "Default")
      (node (ref "J10") (pin "V2") (pinfunction "P$2_V2") (pintype "bidirectional"))
      (node (ref "J11") (pin "H2") (pinfunction "P$2_H2") (pintype "bidirectional"))
      (node (ref "J20") (pin "K2") (pinfunction "IN_K2") (pintype "input"))
    )
    (net (code "1049") (name "Net-(J13A-IN2)") (class "Default")
      (node (ref "J13") (pin "B1") (pinfunction "IN2_B1") (pintype "passive"))
      (node (ref "J13") (pin "C1") (pinfunction "IN3_C1") (pintype "input"))
      (node (ref "J13") (pin "D1") (pinfunction "IN4_D1") (pintype "input"))
    )
    (net (code "1050") (name "Net-(J13E-IN2)") (class "Default")
      (node (ref "J13") (pin "E2") (pinfunction "IN2_E2") (pintype "passive"))
      (node (ref "J13") (pin "F2") (pinfunction "IN3_F2") (pintype "input"))
      (node (ref "J13") (pin "H2") (pinfunction "IN4_H2") (pintype "input"))
    )
    (net (code "1051") (name "Net-(J13F-IN2)") (class "Default")
      (node (ref "J13") (pin "H1") (pinfunction "IN2_H1") (pintype "passive"))
      (node (ref "J13") (pin "J1") (pinfunction "IN3_J1") (pintype "input"))
      (node (ref "J13") (pin "K1") (pinfunction "IN4_K1") (pintype "input"))
    )
    (net (code "1052") (name "Net-(J13G-IN2)") (class "Default")
      (node (ref "J13") (pin "L2") (pinfunction "IN2_L2") (pintype "passive"))
      (node (ref "J13") (pin "M2") (pinfunction "IN3_M2") (pintype "input"))
      (node (ref "J13") (pin "N2") (pinfunction "IN4_N2") (pintype "input"))
    )
    (net (code "1053") (name "Net-(J13H-IN2)") (class "Default")
      (node (ref "J13") (pin "N1") (pinfunction "IN2_N1") (pintype "passive"))
      (node (ref "J13") (pin "P1") (pinfunction "IN3_P1") (pintype "input"))
      (node (ref "J13") (pin "R1") (pinfunction "IN4_R1") (pintype "input"))
    )
    (net (code "1054") (name "Net-(J13I-IN2)") (class "Default")
      (node (ref "J13") (pin "S2") (pinfunction "IN2_S2") (pintype "passive"))
      (node (ref "J13") (pin "T2") (pinfunction "IN3_T2") (pintype "input"))
    )
    (net (code "1055") (name "Net-(J14A-IN2)") (class "Default")
      (node (ref "J14") (pin "B1") (pinfunction "IN2_B1") (pintype "passive"))
      (node (ref "J14") (pin "C1") (pinfunction "IN3_C1") (pintype "input"))
    )
    (net (code "1056") (name "Net-(J14E-IN2)") (class "Default")
      (node (ref "J14") (pin "E2") (pinfunction "IN2_E2") (pintype "passive"))
      (node (ref "J14") (pin "F2") (pinfunction "IN3_F2") (pintype "input"))
    )
    (net (code "1057") (name "Net-(J14F-IN2)") (class "Default")
      (node (ref "J14") (pin "H1") (pinfunction "IN2_H1") (pintype "passive"))
      (node (ref "J14") (pin "J1") (pinfunction "IN3_J1") (pintype "input"))
    )
    (net (code "1058") (name "Net-(J14G-IN2)") (class "Default")
      (node (ref "J14") (pin "L2") (pinfunction "IN2_L2") (pintype "passive"))
      (node (ref "J14") (pin "M2") (pinfunction "IN3_M2") (pintype "input"))
    )
    (net (code "1059") (name "Net-(J14H-IN2)") (class "Default")
      (node (ref "J14") (pin "N1") (pinfunction "IN2_N1") (pintype "passive"))
      (node (ref "J14") (pin "P1") (pinfunction "IN3_P1") (pintype "input"))
    )
    (net (code "1060") (name "Net-(J14I-IN2)") (class "Default")
      (node (ref "J14") (pin "S2") (pinfunction "IN2_S2") (pintype "passive"))
      (node (ref "J14") (pin "T2") (pinfunction "IN3_T2") (pintype "input"))
    )
    (net (code "1061") (name "Net-(J15F-IN2)") (class "Default")
      (node (ref "J15") (pin "H1") (pinfunction "IN2_H1") (pintype "passive"))
      (node (ref "J15") (pin "J1") (pinfunction "IN3_J1") (pintype "input"))
      (node (ref "J15") (pin "K1") (pinfunction "IN4_K1") (pintype "input"))
    )
    (net (code "1062") (name "Net-(J15G-IN2)") (class "Default")
      (node (ref "J15") (pin "L2") (pinfunction "IN2_L2") (pintype "passive"))
      (node (ref "J15") (pin "M2") (pinfunction "IN3_M2") (pintype "input"))
      (node (ref "J15") (pin "N2") (pinfunction "IN4_N2") (pintype "input"))
    )
    (net (code "1063") (name "Net-(J15H-IN2)") (class "Default")
      (node (ref "J15") (pin "N1") (pinfunction "IN2_N1") (pintype "passive"))
      (node (ref "J15") (pin "P1") (pinfunction "IN3_P1") (pintype "input"))
      (node (ref "J15") (pin "R1") (pinfunction "IN4_R1") (pintype "input"))
    )
    (net (code "1064") (name "Net-(J15I-IN2)") (class "Default")
      (node (ref "J15") (pin "S2") (pinfunction "IN2_S2") (pintype "passive"))
      (node (ref "J15") (pin "T2") (pinfunction "IN3_T2") (pintype "input"))
      (node (ref "J15") (pin "U2") (pinfunction "IN4_U2") (pintype "input"))
    )
    (net (code "1065") (name "Net-(J16A-IN2)") (class "Default")
      (node (ref "J16") (pin "B1") (pinfunction "IN2_B1") (pintype "passive"))
      (node (ref "J16") (pin "C1") (pinfunction "IN3_C1") (pintype "input"))
      (node (ref "J16") (pin "D1") (pinfunction "IN4_D1") (pintype "input"))
    )
    (net (code "1066") (name "Net-(J16E-IN2)") (class "Default")
      (node (ref "J16") (pin "E2") (pinfunction "IN2_E2") (pintype "passive"))
      (node (ref "J16") (pin "F2") (pinfunction "IN3_F2") (pintype "input"))
      (node (ref "J16") (pin "H2") (pinfunction "IN4_H2") (pintype "input"))
    )
    (net (code "1067") (name "Net-(J16F-IN2)") (class "Default")
      (node (ref "J16") (pin "H1") (pinfunction "IN2_H1") (pintype "passive"))
      (node (ref "J16") (pin "J1") (pinfunction "IN3_J1") (pintype "input"))
      (node (ref "J16") (pin "K1") (pinfunction "IN4_K1") (pintype "input"))
    )
    (net (code "1068") (name "Net-(J16G-IN2)") (class "Default")
      (node (ref "J16") (pin "L2") (pinfunction "IN2_L2") (pintype "passive"))
      (node (ref "J16") (pin "M2") (pinfunction "IN3_M2") (pintype "input"))
      (node (ref "J16") (pin "N2") (pinfunction "IN4_N2") (pintype "input"))
    )
    (net (code "1069") (name "Net-(J16H-IN2)") (class "Default")
      (node (ref "J16") (pin "N1") (pinfunction "IN2_N1") (pintype "passive"))
      (node (ref "J16") (pin "P1") (pinfunction "IN3_P1") (pintype "input"))
      (node (ref "J16") (pin "R1") (pinfunction "IN4_R1") (pintype "input"))
    )
    (net (code "1070") (name "Net-(J16I-IN2)") (class "Default")
      (node (ref "J16") (pin "S2") (pinfunction "IN2_S2") (pintype "passive"))
      (node (ref "J16") (pin "T2") (pinfunction "IN3_T2") (pintype "input"))
      (node (ref "J16") (pin "U2") (pinfunction "IN4_U2") (pintype "input"))
    )
    (net (code "1071") (name "Net-(J17A-IN2)") (class "Default")
      (node (ref "J17") (pin "B1") (pinfunction "IN2_B1") (pintype "passive"))
      (node (ref "J17") (pin "C1") (pinfunction "IN3_C1") (pintype "input"))
      (node (ref "J17") (pin "D1") (pinfunction "IN4_D1") (pintype "input"))
    )
    (net (code "1072") (name "Net-(J17E-IN2)") (class "Default")
      (node (ref "J17") (pin "E2") (pinfunction "IN2_E2") (pintype "passive"))
      (node (ref "J17") (pin "F2") (pinfunction "IN3_F2") (pintype "input"))
      (node (ref "J17") (pin "H2") (pinfunction "IN4_H2") (pintype "input"))
    )
    (net (code "1073") (name "Net-(J17F-IN2)") (class "Default")
      (node (ref "J17") (pin "H1") (pinfunction "IN2_H1") (pintype "passive"))
      (node (ref "J17") (pin "J1") (pinfunction "IN3_J1") (pintype "input"))
      (node (ref "J17") (pin "K1") (pinfunction "IN4_K1") (pintype "input"))
    )
    (net (code "1074") (name "Net-(J17G-IN2)") (class "Default")
      (node (ref "J17") (pin "L2") (pinfunction "IN2_L2") (pintype "passive"))
      (node (ref "J17") (pin "M2") (pinfunction "IN3_M2") (pintype "input"))
      (node (ref "J17") (pin "N2") (pinfunction "IN4_N2") (pintype "input"))
    )
    (net (code "1075") (name "Net-(J17H-IN2)") (class "Default")
      (node (ref "J17") (pin "N1") (pinfunction "IN2_N1") (pintype "passive"))
      (node (ref "J17") (pin "P1") (pinfunction "IN3_P1") (pintype "input"))
      (node (ref "J17") (pin "R1") (pinfunction "IN4_R1") (pintype "input"))
    )
    (net (code "1076") (name "Net-(J17I-IN2)") (class "Default")
      (node (ref "J17") (pin "S2") (pinfunction "IN2_S2") (pintype "passive"))
      (node (ref "J17") (pin "T2") (pinfunction "IN3_T2") (pintype "input"))
      (node (ref "J17") (pin "U2") (pinfunction "IN4_U2") (pintype "input"))
    )
    (net (code "1077") (name "Net-(J18A-IN2)") (class "Default")
      (node (ref "J18") (pin "B1") (pinfunction "IN2_B1") (pintype "passive"))
      (node (ref "J18") (pin "C1") (pinfunction "IN3_C1") (pintype "input"))
      (node (ref "J18") (pin "D1") (pinfunction "IN4_D1") (pintype "input"))
    )
    (net (code "1078") (name "Net-(J18E-IN2)") (class "Default")
      (node (ref "J18") (pin "E2") (pinfunction "IN2_E2") (pintype "passive"))
      (node (ref "J18") (pin "F2") (pinfunction "IN3_F2") (pintype "input"))
      (node (ref "J18") (pin "H2") (pinfunction "IN4_H2") (pintype "input"))
    )
    (net (code "1079") (name "Net-(J18F-IN2)") (class "Default")
      (node (ref "J18") (pin "H1") (pinfunction "IN2_H1") (pintype "passive"))
      (node (ref "J18") (pin "J1") (pinfunction "IN3_J1") (pintype "input"))
      (node (ref "J18") (pin "K1") (pinfunction "IN4_K1") (pintype "input"))
    )
    (net (code "1080") (name "Net-(J18G-IN2)") (class "Default")
      (node (ref "J18") (pin "L2") (pinfunction "IN2_L2") (pintype "passive"))
      (node (ref "J18") (pin "M2") (pinfunction "IN3_M2") (pintype "input"))
      (node (ref "J18") (pin "N2") (pinfunction "IN4_N2") (pintype "input"))
    )
    (net (code "1081") (name "Net-(J18H-IN2)") (class "Default")
      (node (ref "J18") (pin "N1") (pinfunction "IN2_N1") (pintype "passive"))
      (node (ref "J18") (pin "P1") (pinfunction "IN3_P1") (pintype "input"))
      (node (ref "J18") (pin "R1") (pinfunction "IN4_R1") (pintype "input"))
    )
    (net (code "1082") (name "Net-(J18I-IN2)") (class "Default")
      (node (ref "J18") (pin "S2") (pinfunction "IN2_S2") (pintype "passive"))
      (node (ref "J18") (pin "T2") (pinfunction "IN3_T2") (pintype "input"))
      (node (ref "J18") (pin "U2") (pinfunction "IN4_U2") (pintype "input"))
    )
    (net (code "1083") (name "Net-(J19A-IN2)") (class "Default")
      (node (ref "J19") (pin "B1") (pinfunction "IN2_B1") (pintype "passive"))
      (node (ref "J19") (pin "C1") (pinfunction "IN3_C1") (pintype "input"))
      (node (ref "J19") (pin "D1") (pinfunction "IN4_D1") (pintype "input"))
    )
    (net (code "1084") (name "Net-(J19E-IN2)") (class "Default")
      (node (ref "J19") (pin "E2") (pinfunction "IN2_E2") (pintype "passive"))
      (node (ref "J19") (pin "F2") (pinfunction "IN3_F2") (pintype "input"))
      (node (ref "J19") (pin "H2") (pinfunction "IN4_H2") (pintype "input"))
    )
    (net (code "1085") (name "Net-(J19F-IN2)") (class "Default")
      (node (ref "J19") (pin "H1") (pinfunction "IN2_H1") (pintype "passive"))
      (node (ref "J19") (pin "J1") (pinfunction "IN3_J1") (pintype "input"))
      (node (ref "J19") (pin "K1") (pinfunction "IN4_K1") (pintype "input"))
    )
    (net (code "1086") (name "Net-(J19G-IN2)") (class "Default")
      (node (ref "J19") (pin "L2") (pinfunction "IN2_L2") (pintype "passive"))
      (node (ref "J19") (pin "M2") (pinfunction "IN3_M2") (pintype "input"))
      (node (ref "J19") (pin "N2") (pinfunction "IN4_N2") (pintype "input"))
    )
    (net (code "1087") (name "Net-(J19H-IN2)") (class "Default")
      (node (ref "J19") (pin "N1") (pinfunction "IN2_N1") (pintype "passive"))
      (node (ref "J19") (pin "P1") (pinfunction "IN3_P1") (pintype "input"))
      (node (ref "J19") (pin "R1") (pinfunction "IN4_R1") (pintype "input"))
    )
    (net (code "1088") (name "Net-(J19I-IN2)") (class "Default")
      (node (ref "J19") (pin "S2") (pinfunction "IN2_S2") (pintype "passive"))
      (node (ref "J19") (pin "T2") (pinfunction "IN3_T2") (pintype "input"))
      (node (ref "J19") (pin "U2") (pinfunction "IN4_U2") (pintype "input"))
    )
    (net (code "1089") (name "Net-(J20A-IN2)") (class "Default")
      (node (ref "J20") (pin "B1") (pinfunction "IN2_B1") (pintype "passive"))
      (node (ref "J20") (pin "C1") (pinfunction "IN3_C1") (pintype "input"))
      (node (ref "J20") (pin "D1") (pinfunction "IN4_D1") (pintype "input"))
    )
    (net (code "1090") (name "Net-(J20E-IN2)") (class "Default")
      (node (ref "J20") (pin "E2") (pinfunction "IN2_E2") (pintype "passive"))
      (node (ref "J20") (pin "F2") (pinfunction "IN3_F2") (pintype "input"))
      (node (ref "J20") (pin "H2") (pinfunction "IN4_H2") (pintype "input"))
    )
    (net (code "1091") (name "Net-(J20F-IN2)") (class "Default")
      (node (ref "J20") (pin "H1") (pinfunction "IN2_H1") (pintype "passive"))
      (node (ref "J20") (pin "J1") (pinfunction "IN3_J1") (pintype "input"))
      (node (ref "J20") (pin "K1") (pinfunction "IN4_K1") (pintype "input"))
    )
    (net (code "1092") (name "Net-(J20G-IN2)") (class "Default")
      (node (ref "J20") (pin "L2") (pinfunction "IN2_L2") (pintype "passive"))
      (node (ref "J20") (pin "M2") (pinfunction "IN3_M2") (pintype "input"))
      (node (ref "J20") (pin "N2") (pinfunction "IN4_N2") (pintype "input"))
    )
    (net (code "1093") (name "Net-(J20H-IN2)") (class "Default")
      (node (ref "J20") (pin "N1") (pinfunction "IN2_N1") (pintype "passive"))
      (node (ref "J20") (pin "P1") (pinfunction "IN3_P1") (pintype "input"))
      (node (ref "J20") (pin "R1") (pinfunction "IN4_R1") (pintype "input"))
    )
    (net (code "1094") (name "Net-(J20I-IN2)") (class "Default")
      (node (ref "J20") (pin "S2") (pinfunction "IN2_S2") (pintype "passive"))
      (node (ref "J20") (pin "T2") (pinfunction "IN3_T2") (pintype "input"))
      (node (ref "J20") (pin "U2") (pinfunction "IN4_U2") (pintype "input"))
    )
    (net (code "1095") (name "OP1") (class "Default")
      (node (ref "E27") (pin "H1") (pinfunction "IN3A_H1") (pintype "input"))
      (node (ref "E28") (pin "C1") (pinfunction "IN1C_C1") (pintype "input"))
      (node (ref "E28") (pin "N1") (pinfunction "IN5B_N1") (pintype "input"))
      (node (ref "E30") (pin "L2") (pinfunction "IN3A_L2") (pintype "input"))
      (node (ref "F25") (pin "C1") (pinfunction "OUT_C1") (pintype "output"))
      (node (ref "F26") (pin "B1") (pinfunction "IN2_B1") (pintype "input"))
      (node (ref "F26") (pin "E2") (pinfunction "IN2_E2") (pintype "input"))
      (node (ref "F26") (pin "F1") (pinfunction "IN2_F1") (pintype "input"))
      (node (ref "F26") (pin "K2") (pinfunction "IN2_K2") (pintype "input"))
      (node (ref "F26") (pin "L1") (pinfunction "IN2_L1") (pintype "input"))
      (node (ref "F29") (pin "T2") (pinfunction "IN1_T2") (pintype "input"))
      (node (ref "F32") (pin "H2") (pinfunction "IN1_H2") (pintype "input"))
    )
    (net (code "1096") (name "OP1_") (class "Default")
      (node (ref "F24") (pin "A1") (pinfunction "IN1_A1") (pintype "input"))
      (node (ref "F25") (pin "A1") (pinfunction "IN1_A1") (pintype "input"))
      (node (ref "F27") (pin "V2") (pinfunction "OUT_V2") (pintype "output"))
    )
    (net (code "1097") (name "OP2") (class "Default")
      (node (ref "B04") (pin "E2") (pinfunction "IN2_E2") (pintype "input"))
      (node (ref "D18") (pin "E2") (pinfunction "IN2_E2") (pintype "input"))
      (node (ref "D18") (pin "F1") (pinfunction "IN2_F1") (pintype "input"))
      (node (ref "D21") (pin "K1") (pinfunction "IN4_K1") (pintype "input"))
      (node (ref "E13") (pin "C1") (pinfunction "IN1C_C1") (pintype "input"))
      (node (ref "E25") (pin "R2") (pinfunction "IN3_R2") (pintype "input"))
      (node (ref "E28") (pin "P2") (pinfunction "IN4B_P2") (pintype "input"))
      (node (ref "E30") (pin "D2") (pinfunction "IN1A_D2") (pintype "input"))
      (node (ref "F28") (pin "N2") (pinfunction "IN1_N2") (pintype "input"))
      (node (ref "F29") (pin "K1") (pinfunction "OUT_K1") (pintype "output"))
    )
    (net (code "1098") (name "OPR") (class "Default")
      (node (ref "D13") (pin "L2") (pinfunction "IN1_L2") (pintype "input"))
      (node (ref "D14") (pin "D2") (pinfunction "IN1_D2") (pintype "input"))
      (node (ref "D20") (pin "N1") (pinfunction "IN2_N1") (pintype "input"))
      (node (ref "D21") (pin "F2") (pinfunction "IN3_F2") (pintype "input"))
      (node (ref "E22") (pin "S2") (pinfunction "OUT_S2") (pintype "output"))
      (node (ref "E25") (pin "V2") (pinfunction "IN3_V2") (pintype "input"))
      (node (ref "E26") (pin "S2") (pinfunction "IN4D_S2") (pintype "input"))
      (node (ref "F27") (pin "F1") (pinfunction "IN1_F1") (pintype "input"))
      (node (ref "F27") (pin "R2") (pinfunction "IN1_R2") (pintype "input"))
    )
    (net (code "1099") (name "OPR_") (class "Default")
      (node (ref "D40") (pin "D2") (pinfunction "P$2_D2") (pintype "bidirectional"))
      (node (ref "E21") (pin "V1") (pinfunction "OUT_V1") (pintype "output"))
      (node (ref "E22") (pin "P2") (pinfunction "IN1_P2") (pintype "input"))
    )
    (net (code "1100") (name "OSR_") (class "Default")
      (node (ref "A06") (pin "E2") (pinfunction "IN2_E2") (pintype "input"))
      (node (ref "F28") (pin "S2") (pinfunction "OUT_S2") (pintype "output"))
    )
    (net (code "1101") (name "PAUSE_") (class "Default")
      (node (ref "D40") (pin "M1") (pinfunction "P$2_M1") (pintype "bidirectional"))
      (node (ref "E14") (pin "B1") (pinfunction "IN2_B1") (pintype "input"))
      (node (ref "E18") (pin "M1") (pinfunction "0_M1") (pintype "output"))
    )
    (net (code "1102") (name "PC00_") (class "Default")
      (node (ref "E40") (pin "J2") (pinfunction "P$2_J2") (pintype "bidirectional"))
      (node (ref "EF34") (pin "AR2") (pinfunction "AR2_AR2") (pintype "output"))
    )
    (net (code "1103") (name "PC01_") (class "Default")
      (node (ref "E40") (pin "S1") (pinfunction "P$2_S1") (pintype "bidirectional"))
      (node (ref "EF34") (pin "AP2") (pinfunction "AP2_AP2") (pintype "output"))
    )
    (net (code "1104") (name "PC02_") (class "Default")
      (node (ref "E40") (pin "P2") (pinfunction "P$2_P2") (pintype "bidirectional"))
      (node (ref "EF35") (pin "AR2") (pinfunction "AR2_AR2") (pintype "output"))
    )
    (net (code "1105") (name "PC03_") (class "Default")
      (node (ref "E40") (pin "N1") (pinfunction "P$2_N1") (pintype "bidirectional"))
      (node (ref "EF35") (pin "AP2") (pinfunction "AP2_AP2") (pintype "output"))
    )
    (net (code "1106") (name "PC04_") (class "Default")
      (node (ref "E40") (pin "C1") (pinfunction "P$2_C1") (pintype "bidirectional"))
      (node (ref "EF36") (pin "AR2") (pinfunction "AR2_AR2") (pintype "output"))
    )
    (net (code "1107") (name "PC05_") (class "Default")
      (node (ref "E40") (pin "D1") (pinfunction "P$2_D1") (pintype "bidirectional"))
      (node (ref "EF36") (pin "AP2") (pinfunction "AP2_AP2") (pintype "output"))
    )
    (net (code "1108") (name "PC06_") (class "Default")
      (node (ref "EF37") (pin "AR2") (pinfunction "AR2_AR2") (pintype "output"))
      (node (ref "F40") (pin "J2") (pinfunction "P$2_J2") (pintype "bidirectional"))
    )
    (net (code "1109") (name "PC07_") (class "Default")
      (node (ref "EF37") (pin "AP2") (pinfunction "AP2_AP2") (pintype "output"))
      (node (ref "F40") (pin "S1") (pinfunction "P$2_S1") (pintype "bidirectional"))
    )
    (net (code "1110") (name "PC08_") (class "Default")
      (node (ref "EF38") (pin "AR2") (pinfunction "AR2_AR2") (pintype "output"))
      (node (ref "F40") (pin "P2") (pinfunction "P$2_P2") (pintype "bidirectional"))
    )
    (net (code "1111") (name "PC09_") (class "Default")
      (node (ref "EF38") (pin "AP2") (pinfunction "AP2_AP2") (pintype "output"))
      (node (ref "F40") (pin "N1") (pinfunction "P$2_N1") (pintype "bidirectional"))
    )
    (net (code "1112") (name "PC10_") (class "Default")
      (node (ref "EF39") (pin "AR2") (pinfunction "AR2_AR2") (pintype "output"))
      (node (ref "F40") (pin "C1") (pinfunction "P$2_C1") (pintype "bidirectional"))
    )
    (net (code "1113") (name "PC11_") (class "Default")
      (node (ref "EF39") (pin "AP2") (pinfunction "AP2_AP2") (pintype "output"))
      (node (ref "F40") (pin "D1") (pinfunction "P$2_D1") (pintype "bidirectional"))
    )
    (net (code "1114") (name "PC_ENABLE") (class "Default")
      (node (ref "EF34") (pin "BS2") (pinfunction "BS2_BS2") (pintype "input"))
      (node (ref "EF35") (pin "BS2") (pinfunction "BS2_BS2") (pintype "input"))
      (node (ref "EF36") (pin "BS2") (pinfunction "BS2_BS2") (pintype "input"))
      (node (ref "EF37") (pin "BS2") (pinfunction "BS2_BS2") (pintype "input"))
      (node (ref "EF38") (pin "BS2") (pinfunction "BS2_BS2") (pintype "input"))
      (node (ref "EF39") (pin "BS2") (pinfunction "BS2_BS2") (pintype "input"))
      (node (ref "F30") (pin "E1") (pinfunction "OUT_E1") (pintype "open_collector"))
    )
    (net (code "1115") (name "PC_ENABLE_") (class "Default")
      (node (ref "F09") (pin "M2") (pinfunction "IN7_M2") (pintype "input"))
      (node (ref "F11") (pin "P1") (pinfunction "IN3_P1") (pintype "input"))
      (node (ref "F27") (pin "H2") (pinfunction "IN4_H2") (pintype "input"))
      (node (ref "F32") (pin "N1") (pinfunction "OUT_N1") (pintype "output"))
    )
    (net (code "1116") (name "PC_INCREMENT") (class "Default")
      (node (ref "E26") (pin "F1") (pinfunction "IN2B_F1") (pintype "input"))
      (node (ref "E27") (pin "F1") (pinfunction "IN2B_F1") (pintype "input"))
      (node (ref "E30") (pin "F1") (pinfunction "IN2B_F1") (pintype "input"))
      (node (ref "F28") (pin "V1") (pinfunction "OUT_V1") (pintype "output"))
    )
    (net (code "1117") (name "PC_LOAD") (class "Default")
      (node (ref "A15") (pin "H1") (pinfunction "IN1_H1") (pintype "input"))
      (node (ref "E32") (pin "J2") (pinfunction "OUT_J2") (pintype "open_collector"))
      (node (ref "EF34") (pin "AN2") (pinfunction "AN2_AN2") (pintype "input"))
      (node (ref "EF35") (pin "AN2") (pinfunction "AN2_AN2") (pintype "input"))
      (node (ref "EF36") (pin "AN2") (pinfunction "AN2_AN2") (pintype "input"))
      (node (ref "EF37") (pin "AN2") (pinfunction "AN2_AN2") (pintype "input"))
      (node (ref "EF38") (pin "AN2") (pinfunction "AN2_AN2") (pintype "input"))
      (node (ref "EF39") (pin "AN2") (pinfunction "AN2_AN2") (pintype "input"))
      (node (ref "F25") (pin "P1") (pinfunction "IN1_P1") (pintype "input"))
    )
    (net (code "1118") (name "PC_LOADXSR_ENABLE_") (class "Default")
      (node (ref "A15") (pin "K1") (pinfunction "OUT_K1") (pintype "output"))
      (node (ref "A17") (pin "A1") (pinfunction "IN1_A1") (pintype "input"))
      (node (ref "A17") (pin "R2") (pinfunction "IN2_R2") (pintype "input"))
      (node (ref "A18") (pin "A1") (pinfunction "IN1_A1") (pintype "input"))
      (node (ref "B06") (pin "H1") (pinfunction "IN1_H1") (pintype "input"))
    )
    (net (code "1119") (name "PC_LOAD_") (class "Default")
      (node (ref "B04") (pin "M1") (pinfunction "IN3_M1") (pintype "input"))
      (node (ref "E18") (pin "R1") (pinfunction "S_R1") (pintype "input"))
      (node (ref "F25") (pin "S1") (pinfunction "OUT_S1") (pintype "output"))
    )
    (net (code "1120") (name "POWER_CLEAR_") (class "Default")
      (node (ref "AB02") (pin "AS2") (pinfunction "AS2_AS2") (pintype "bidirectional"))
      (node (ref "B21") (pin "T2") (pinfunction "IN1_T2") (pintype "input"))
      (node (ref "B21") (pin "U2") (pinfunction "IN2_U2") (pintype "input"))
    )
    (net (code "1121") (name "POWER_OK_") (class "Default")
      (node (ref "AB02") (pin "AJ2") (pinfunction "AJ2_AJ2") (pintype "bidirectional"))
      (node (ref "E13") (pin "L1") (pinfunction "IN4B_L1") (pintype "input"))
    )
    (net (code "1122") (name "PROCESSOR_IOT_") (class "Default")
      (node (ref "F19") (pin "D1") (pinfunction "IN4_D1") (pintype "input"))
      (node (ref "F21") (pin "V2") (pinfunction "OUT_V2") (pintype "output"))
    )
    (net (code "1123") (name "PWR_LOW_") (class "Default")
      (node (ref "A04") (pin "R2") (pinfunction "R2_R2") (pintype "output"))
      (node (ref "J15") (pin "E2") (pinfunction "IN2_E2") (pintype "passive"))
    )
    (net (code "1124") (name "PWR_SKIP_") (class "Default")
      (node (ref "A04") (pin "L2") (pinfunction "L2_L2") (pintype "output"))
      (node (ref "J15") (pin "C1") (pinfunction "IN3_C1") (pintype "input"))
    )
    (net (code "1125") (name "R0") (class "Default")
      (node (ref "C09") (pin "L2") (pinfunction "IN1_L2") (pintype "input"))
      (node (ref "D05") (pin "J2") (pinfunction "OUT_J2") (pintype "output"))
      (node (ref "D10") (pin "R2") (pinfunction "IN1_R2") (pintype "input"))
    )
    (net (code "1126") (name "R0_") (class "Default")
      (node (ref "C09") (pin "N2") (pinfunction "OUT_N2") (pintype "output"))
      (node (ref "D10") (pin "M1") (pinfunction "IN1_M1") (pintype "input"))
    )
    (net (code "1127") (name "RESTART") (class "Default")
      (node (ref "A04") (pin "N2") (pinfunction "N2_N2") (pintype "output"))
      (node (ref "E12") (pin "L2") (pinfunction "IN1_L2") (pintype "input"))
    )
    (net (code "1128") (name "RESTART_") (class "Default")
      (node (ref "A04") (pin "U1") (pinfunction "U1_U1") (pintype "output"))
      (node (ref "E11") (pin "E1") (pinfunction "IN2_E1") (pintype "input"))
      (node (ref "E14") (pin "D2") (pinfunction "IN1_D2") (pintype "input"))
      (node (ref "E14") (pin "K2") (pinfunction "IN2_K2") (pintype "input"))
      (node (ref "EF10") (pin "AR2") (pinfunction "CR2_AR2") (pintype "input"))
    )
    (net (code "1129") (name "RIB") (class "Default")
      (node (ref "A05") (pin "H2") (pinfunction "IN1_H2") (pintype "input"))
      (node (ref "A11") (pin "D2") (pinfunction "IN1_D2") (pintype "input"))
      (node (ref "A11") (pin "L1") (pinfunction "IN1_L1") (pintype "input"))
      (node (ref "A11") (pin "P2") (pinfunction "IN1_P2") (pintype "input"))
      (node (ref "A13") (pin "H2") (pinfunction "IN1_H2") (pintype "input"))
      (node (ref "A13") (pin "L2") (pinfunction "IN1_L2") (pintype "input"))
      (node (ref "A13") (pin "P2") (pinfunction "IN1_P2") (pintype "input"))
      (node (ref "A14") (pin "N2") (pinfunction "OUT_N2") (pintype "output"))
    )
    (net (code "1130") (name "RIGHT_SHIFT") (class "Default")
      (node (ref "C14") (pin "A1") (pinfunction "IN1_A1") (pintype "input"))
      (node (ref "C14") (pin "H1") (pinfunction "IN1_H1") (pintype "input"))
      (node (ref "C14") (pin "L2") (pinfunction "IN1_L2") (pintype "input"))
      (node (ref "C15") (pin "A1") (pinfunction "IN1_A1") (pintype "input"))
      (node (ref "C15") (pin "H1") (pinfunction "IN1_H1") (pintype "input"))
      (node (ref "C15") (pin "L2") (pinfunction "IN1_L2") (pintype "input"))
      (node (ref "C16") (pin "A1") (pinfunction "IN1_A1") (pintype "input"))
      (node (ref "C16") (pin "H1") (pinfunction "IN1_H1") (pintype "input"))
      (node (ref "C16") (pin "L2") (pinfunction "IN1_L2") (pintype "input"))
      (node (ref "C17") (pin "A1") (pinfunction "IN1_A1") (pintype "input"))
      (node (ref "C17") (pin "H1") (pinfunction "IN1_H1") (pintype "input"))
      (node (ref "C17") (pin "L2") (pinfunction "IN1_L2") (pintype "input"))
      (node (ref "E31") (pin "L1") (pinfunction "OUT_L1") (pintype "open_collector"))
      (node (ref "EF34") (pin "AD2") (pinfunction "AD2_AD2") (pintype "input"))
      (node (ref "EF35") (pin "AD2") (pinfunction "AD2_AD2") (pintype "input"))
      (node (ref "EF36") (pin "AD2") (pinfunction "AD2_AD2") (pintype "input"))
      (node (ref "EF37") (pin "AD2") (pinfunction "AD2_AD2") (pintype "input"))
      (node (ref "EF38") (pin "AD2") (pinfunction "AD2_AD2") (pintype "input"))
      (node (ref "EF39") (pin "AD2") (pinfunction "AD2_AD2") (pintype "input"))
      (node (ref "F33") (pin "D1") (pinfunction "IN1D_D1") (pintype "input"))
    )
    (net (code "1131") (name "RMF_") (class "Default")
      (node (ref "A06") (pin "V2") (pinfunction "OUT_V2") (pintype "output"))
      (node (ref "A13") (pin "B1") (pinfunction "IN2_B1") (pintype "input"))
      (node (ref "A15") (pin "L2") (pinfunction "IN1_L2") (pintype "input"))
      (node (ref "A15") (pin "M1") (pinfunction "IN2_M1") (pintype "input"))
      (node (ref "B06") (pin "E1") (pinfunction "IN2_E1") (pintype "input"))
    )
    (net (code "1132") (name "RUN") (class "Default")
      (node (ref "B10") (pin "J2") (pinfunction "J2_J2") (pintype "input"))
      (node (ref "E14") (pin "C1") (pinfunction "IN3_C1") (pintype "input"))
      (node (ref "E18") (pin "P2") (pinfunction "1_P2") (pintype "output"))
    )
    (net (code "1133") (name "RUN_") (class "Default")
      (node (ref "D40") (pin "F1") (pinfunction "P$2_F1") (pintype "bidirectional"))
      (node (ref "E18") (pin "R2") (pinfunction "0_R2") (pintype "output"))
      (node (ref "EF10") (pin "AP2") (pinfunction "CP2_AP2") (pintype "input"))
      (node (ref "F21") (pin "E1") (pinfunction "IN2_E1") (pintype "input"))
      (node (ref "H19") (pin "H2") (pinfunction "IN2_H2") (pintype "input"))
    )
    (net (code "1134") (name "S") (class "Default")
      (node (ref "C07") (pin "U2") (pinfunction "IN2_U2") (pintype "input"))
      (node (ref "C10") (pin "R1") (pinfunction "IN2_R1") (pintype "input"))
      (node (ref "C11") (pin "L2") (pinfunction "IN3_L2") (pintype "input"))
      (node (ref "C11") (pin "P2") (pinfunction "IN2_P2") (pintype "input"))
      (node (ref "D07") (pin "T2") (pinfunction "IN1_T2") (pintype "input"))
      (node (ref "D09") (pin "A1") (pinfunction "IN1_A1") (pintype "input"))
      (node (ref "D10") (pin "D2") (pinfunction "IN1_D2") (pintype "input"))
      (node (ref "D10") (pin "K1") (pinfunction "IN4_K1") (pintype "input"))
      (node (ref "D11") (pin "F1") (pinfunction "0_F1") (pintype "output"))
    )
    (net (code "1135") (name "SC0") (class "Default")
      (node (ref "C21") (pin "F2") (pinfunction "IN3_F2") (pintype "input"))
      (node (ref "C22") (pin "E1") (pinfunction "1_E1") (pintype "output"))
      (node (ref "D23") (pin "L1") (pinfunction "IN4B_L1") (pintype "input"))
      (node (ref "EF37") (pin "BN1") (pinfunction "BN1_BN1") (pintype "input"))
    )
    (net (code "1136") (name "SC0_") (class "Default")
      (node (ref "C21") (pin "C1") (pinfunction "IN3_C1") (pintype "input"))
      (node (ref "C22") (pin "F1") (pinfunction "0_F1") (pintype "output"))
      (node (ref "C40") (pin "S2") (pinfunction "P$2_S2") (pintype "bidirectional"))
    )
    (net (code "1137") (name "SC0_3_0") (class "Default")
      (node (ref "C18") (pin "S2") (pinfunction "OUT_S2") (pintype "output"))
      (node (ref "D13") (pin "P2") (pinfunction "IN1_P2") (pintype "input"))
      (node (ref "D19") (pin "E1") (pinfunction "IN1_E1") (pintype "input"))
      (node (ref "D23") (pin "F2") (pinfunction "IN1C_F2") (pintype "input"))
    )
    (net (code "1138") (name "SC0_3_0_") (class "Default")
      (node (ref "C18") (pin "P2") (pinfunction "IN1_P2") (pintype "input"))
      (node (ref "D17") (pin "N2") (pinfunction "IN1_N2") (pintype "input"))
      (node (ref "D22") (pin "J2") (pinfunction "OUT_J2") (pintype "open_collector"))
    )
    (net (code "1139") (name "SC1") (class "Default")
      (node (ref "C21") (pin "L2") (pinfunction "IN3_L2") (pintype "input"))
      (node (ref "C22") (pin "H2") (pinfunction "1_H2") (pintype "output"))
      (node (ref "D17") (pin "E1") (pinfunction "IN1_E1") (pintype "input"))
      (node (ref "D19") (pin "J2") (pinfunction "IN1_J2") (pintype "input"))
      (node (ref "D20") (pin "L2") (pinfunction "IN2_L2") (pintype "input"))
      (node (ref "D22") (pin "A1") (pinfunction "IN1_A1") (pintype "input"))
      (node (ref "D23") (pin "B1") (pinfunction "IN1B_B1") (pintype "input"))
      (node (ref "EF38") (pin "BD1") (pinfunction "BD1_BD1") (pintype "input"))
    )
    (net (code "1140") (name "SC1_") (class "Default")
      (node (ref "C21") (pin "H1") (pinfunction "IN3_H1") (pintype "input"))
      (node (ref "C22") (pin "J2") (pinfunction "0_J2") (pintype "output"))
      (node (ref "C40") (pin "M2") (pinfunction "P$2_M2") (pintype "bidirectional"))
      (node (ref "D22") (pin "E2") (pinfunction "IN2_E2") (pintype "input"))
    )
    (net (code "1141") (name "SC2") (class "Default")
      (node (ref "C21") (pin "R2") (pinfunction "IN3_R2") (pintype "input"))
      (node (ref "C22") (pin "L1") (pinfunction "1_L1") (pintype "output"))
      (node (ref "D17") (pin "H1") (pinfunction "IN3_H1") (pintype "input"))
      (node (ref "D19") (pin "A1") (pinfunction "IN1_A1") (pintype "input"))
      (node (ref "D19") (pin "L2") (pinfunction "IN3_L2") (pintype "input"))
      (node (ref "D22") (pin "B1") (pinfunction "IN2_B1") (pintype "input"))
      (node (ref "EF38") (pin "BN1") (pinfunction "BN1_BN1") (pintype "input"))
    )
    (net (code "1142") (name "SC2_") (class "Default")
      (node (ref "C21") (pin "M1") (pinfunction "IN3_M1") (pintype "input"))
      (node (ref "C22") (pin "M1") (pinfunction "0_M1") (pintype "output"))
      (node (ref "C40") (pin "N2") (pinfunction "P$2_N2") (pintype "bidirectional"))
      (node (ref "D22") (pin "F2") (pinfunction "IN3_F2") (pintype "input"))
    )
    (net (code "1143") (name "SC3") (class "Default")
      (node (ref "C18") (pin "H1") (pinfunction "IN1_H1") (pintype "input"))
      (node (ref "C21") (pin "U2") (pinfunction "IN2_U2") (pintype "input"))
      (node (ref "C22") (pin "P2") (pinfunction "1_P2") (pintype "output"))
      (node (ref "D19") (pin "B1") (pinfunction "IN2_B1") (pintype "input"))
      (node (ref "D22") (pin "C1") (pinfunction "IN3_C1") (pintype "input"))
      (node (ref "D23") (pin "C1") (pinfunction "IN1C_C1") (pintype "input"))
      (node (ref "EF39") (pin "BD1") (pinfunction "BD1_BD1") (pintype "input"))
    )
    (net (code "1144") (name "SC3_") (class "Default")
      (node (ref "C21") (pin "P1") (pinfunction "IN1_P1") (pintype "input"))
      (node (ref "C22") (pin "R2") (pinfunction "0_R2") (pintype "output"))
      (node (ref "C40") (pin "L2") (pinfunction "P$2_L2") (pintype "bidirectional"))
      (node (ref "D22") (pin "H2") (pinfunction "IN4_H2") (pintype "input"))
    )
    (net (code "1145") (name "SC4") (class "Default")
      (node (ref "C18") (pin "J1") (pinfunction "IN2_J1") (pintype "input"))
      (node (ref "C21") (pin "S1") (pinfunction "IN3_S1") (pintype "input"))
      (node (ref "C22") (pin "S1") (pinfunction "1_S1") (pintype "output"))
      (node (ref "D19") (pin "C1") (pinfunction "IN3_C1") (pintype "input"))
      (node (ref "D19") (pin "K2") (pinfunction "IN2_K2") (pintype "input"))
      (node (ref "D22") (pin "D1") (pinfunction "IN4_D1") (pintype "input"))
      (node (ref "D23") (pin "D1") (pinfunction "IN1D_D1") (pintype "input"))
      (node (ref "EF39") (pin "BN1") (pinfunction "BN1_BN1") (pintype "input"))
    )
    (net (code "1146") (name "SC4_") (class "Default")
      (node (ref "C18") (pin "M2") (pinfunction "IN2_M2") (pintype "input"))
      (node (ref "C21") (pin "V2") (pinfunction "IN3_V2") (pintype "input"))
      (node (ref "C22") (pin "U1") (pinfunction "0_U1") (pintype "output"))
      (node (ref "C40") (pin "F1") (pinfunction "P$2_F1") (pintype "bidirectional"))
      (node (ref "D13") (pin "R2") (pinfunction "IN2_R2") (pintype "input"))
      (node (ref "D19") (pin "H1") (pinfunction "IN3_H1") (pintype "input"))
      (node (ref "D23") (pin "H2") (pinfunction "IN1D_H2") (pintype "input"))
    )
    (net (code "1147") (name "SCL_") (class "Default")
      (node (ref "D14") (pin "J1") (pinfunction "IN2_J1") (pintype "input"))
      (node (ref "D17") (pin "T2") (pinfunction "IN1_T2") (pintype "input"))
      (node (ref "D19") (pin "S2") (pinfunction "OUT_S2") (pintype "output"))
    )
    (net (code "1148") (name "SC_0_") (class "Default")
      (node (ref "D13") (pin "S2") (pinfunction "OUT_S2") (pintype "output"))
      (node (ref "D13") (pin "T2") (pinfunction "IN1_T2") (pintype "input"))
    )
    (net (code "1149") (name "SC_ENABLE") (class "Default")
      (node (ref "D22") (pin "P2") (pinfunction "OUT_P2") (pintype "open_collector"))
      (node (ref "EF34") (pin "BF2") (pinfunction "BF2_BF2") (pintype "input"))
      (node (ref "EF35") (pin "BF2") (pinfunction "BF2_BF2") (pintype "input"))
      (node (ref "EF36") (pin "BF2") (pinfunction "BF2_BF2") (pintype "input"))
      (node (ref "EF37") (pin "BF2") (pinfunction "BF2_BF2") (pintype "input"))
      (node (ref "EF38") (pin "BF2") (pinfunction "BF2_BF2") (pintype "input"))
      (node (ref "EF39") (pin "BF2") (pinfunction "BF2_BF2") (pintype "input"))
    )
    (net (code "1150") (name "SC_FULL") (class "Default")
      (node (ref "C18") (pin "C1") (pinfunction "OUT_C1") (pintype "output"))
      (node (ref "C21") (pin "B1") (pinfunction "IN2_B1") (pintype "input"))
      (node (ref "D23") (pin "K1") (pinfunction "IN4A_K1") (pintype "input"))
    )
    (net (code "1151") (name "SC_LOAD") (class "Default")
      (node (ref "C22") (pin "B1") (pinfunction "C_B1") (pintype "input"))
      (node (ref "C22") (pin "D2") (pinfunction "C_D2") (pintype "input"))
      (node (ref "C22") (pin "H1") (pinfunction "C_H1") (pintype "input"))
      (node (ref "C22") (pin "L2") (pinfunction "C_L2") (pintype "input"))
      (node (ref "C22") (pin "N1") (pinfunction "C_N1") (pintype "input"))
      (node (ref "D22") (pin "V2") (pinfunction "OUT_V2") (pintype "open_collector"))
    )
    (net (code "1152") (name "SF0") (class "Default")
      (node (ref "A11") (pin "E2") (pinfunction "IN2_E2") (pintype "input"))
      (node (ref "A18") (pin "J1") (pinfunction "IN2_J1") (pintype "input"))
      (node (ref "B19") (pin "E1") (pinfunction "1_E1") (pintype "output"))
    )
    (net (code "1153") (name "SF1") (class "Default")
      (node (ref "A11") (pin "M1") (pinfunction "IN2_M1") (pintype "input"))
      (node (ref "A18") (pin "M2") (pinfunction "IN2_M2") (pintype "input"))
      (node (ref "B19") (pin "H2") (pinfunction "1_H2") (pintype "output"))
    )
    (net (code "1154") (name "SF2") (class "Default")
      (node (ref "A11") (pin "R2") (pinfunction "IN2_R2") (pintype "input"))
      (node (ref "A18") (pin "U2") (pinfunction "IN2_U2") (pintype "input"))
      (node (ref "B19") (pin "L1") (pinfunction "1_L1") (pintype "output"))
    )
    (net (code "1155") (name "SF3") (class "Default")
      (node (ref "A12") (pin "J1") (pinfunction "IN2_J1") (pintype "input"))
      (node (ref "A13") (pin "J2") (pinfunction "IN2_J2") (pintype "input"))
      (node (ref "B19") (pin "P2") (pinfunction "1_P2") (pintype "output"))
    )
    (net (code "1156") (name "SF4") (class "Default")
      (node (ref "A12") (pin "M2") (pinfunction "IN2_M2") (pintype "input"))
      (node (ref "A13") (pin "M2") (pinfunction "IN2_M2") (pintype "input"))
      (node (ref "B19") (pin "S1") (pinfunction "1_S1") (pintype "output"))
    )
    (net (code "1157") (name "SF5") (class "Default")
      (node (ref "A12") (pin "U2") (pinfunction "IN2_U2") (pintype "input"))
      (node (ref "A13") (pin "R2") (pinfunction "IN2_R2") (pintype "input"))
      (node (ref "B19") (pin "V2") (pinfunction "1_V2") (pintype "output"))
    )
    (net (code "1158") (name "SF_ENABLE") (class "Default")
      (node (ref "A12") (pin "H1") (pinfunction "IN1_H1") (pintype "input"))
      (node (ref "A12") (pin "L2") (pinfunction "IN1_L2") (pintype "input"))
      (node (ref "A12") (pin "T2") (pinfunction "IN1_T2") (pintype "input"))
      (node (ref "A15") (pin "N2") (pinfunction "OUT_N2") (pintype "output"))
      (node (ref "A18") (pin "H1") (pinfunction "IN1_H1") (pintype "input"))
      (node (ref "A18") (pin "L2") (pinfunction "IN1_L2") (pintype "input"))
      (node (ref "A18") (pin "T2") (pinfunction "IN1_T2") (pintype "input"))
      (node (ref "B06") (pin "R1") (pinfunction "IN2_R1") (pintype "input"))
    )
    (net (code "1159") (name "SHUT_DOWN_") (class "Default")
      (node (ref "A04") (pin "U2") (pinfunction "U2_U2") (pintype "input"))
      (node (ref "AB02") (pin "AF2") (pinfunction "AF2_AF2") (pintype "output"))
    )
    (net (code "1160") (name "SINT") (class "Default")
      (node (ref "A05") (pin "V2") (pinfunction "OUT_V2") (pintype "output"))
      (node (ref "B04") (pin "L2") (pinfunction "IN3_L2") (pintype "input"))
    )
    (net (code "1161") (name "SKIP_") (class "Default")
      (node (ref "B04") (pin "U2") (pinfunction "IN2_U2") (pintype "input"))
      (node (ref "E18") (pin "S1") (pinfunction "1_S1") (pintype "output"))
      (node (ref "F25") (pin "U2") (pinfunction "IN2_U2") (pintype "input"))
    )
    (net (code "1162") (name "SKIP_OR") (class "Default")
      (node (ref "B04") (pin "V1") (pinfunction "OUT_V1") (pintype "output"))
      (node (ref "E27") (pin "L1") (pinfunction "IN4B_L1") (pintype "input"))
    )
    (net (code "1163") (name "SLOW_CYCLE") (class "Default")
      (node (ref "E12") (pin "N1") (pinfunction "OUT_N1") (pintype "output"))
      (node (ref "E15") (pin "R1") (pinfunction "IN2_R1") (pintype "input"))
    )
    (net (code "1164") (name "SLOW_CYCLE_") (class "Default")
      (node (ref "E12") (pin "M1") (pinfunction "IN2_M1") (pintype "input"))
      (node (ref "E14") (pin "M1") (pinfunction "IN3_M1") (pintype "input"))
      (node (ref "F19") (pin "E1") (pinfunction "OUT_E1") (pintype "output"))
    )
    (net (code "1165") (name "SPECIAL_CYCLE_") (class "Default")
      (node (ref "E24") (pin "K1") (pinfunction "OUT_K1") (pintype "output"))
      (node (ref "F23") (pin "M1") (pinfunction "IN1_M1") (pintype "input"))
      (node (ref "F23") (pin "M2") (pinfunction "IN3_M2") (pintype "input"))
    )
    (net (code "1166") (name "SR00") (class "Default")
      (node (ref "A40") (pin "L2") (pinfunction "P$2_L2") (pintype "bidirectional"))
      (node (ref "EF34") (pin "BE1") (pinfunction "BE1_BE1") (pintype "input"))
    )
    (net (code "1167") (name "SR01") (class "Default")
      (node (ref "A40") (pin "M2") (pinfunction "P$2_M2") (pintype "bidirectional"))
      (node (ref "EF34") (pin "BD2") (pinfunction "BD2_BD2") (pintype "input"))
    )
    (net (code "1168") (name "SR02") (class "Default")
      (node (ref "A40") (pin "R2") (pinfunction "P$2_R2") (pintype "bidirectional"))
      (node (ref "EF35") (pin "BE1") (pinfunction "BE1_BE1") (pintype "input"))
    )
    (net (code "1169") (name "SR03") (class "Default")
      (node (ref "A40") (pin "S2") (pinfunction "P$2_S2") (pintype "bidirectional"))
      (node (ref "EF35") (pin "BD2") (pinfunction "BD2_BD2") (pintype "input"))
    )
    (net (code "1170") (name "SR04") (class "Default")
      (node (ref "A40") (pin "T2") (pinfunction "P$2_T2") (pintype "bidirectional"))
      (node (ref "EF36") (pin "BE1") (pinfunction "BE1_BE1") (pintype "input"))
    )
    (net (code "1171") (name "SR05") (class "Default")
      (node (ref "A40") (pin "U2") (pinfunction "P$2_U2") (pintype "bidirectional"))
      (node (ref "EF36") (pin "BD2") (pinfunction "BD2_BD2") (pintype "input"))
    )
    (net (code "1172") (name "SR06") (class "Default")
      (node (ref "A40") (pin "V2") (pinfunction "P$2_V2") (pintype "bidirectional"))
      (node (ref "EF37") (pin "BE1") (pinfunction "BE1_BE1") (pintype "input"))
    )
    (net (code "1173") (name "SR07") (class "Default")
      (node (ref "B40") (pin "D2") (pinfunction "P$2_D2") (pintype "bidirectional"))
      (node (ref "EF37") (pin "BD2") (pinfunction "BD2_BD2") (pintype "input"))
    )
    (net (code "1174") (name "SR08") (class "Default")
      (node (ref "B40") (pin "E2") (pinfunction "P$2_E2") (pintype "bidirectional"))
      (node (ref "EF38") (pin "BE1") (pinfunction "BE1_BE1") (pintype "input"))
    )
    (net (code "1175") (name "SR09") (class "Default")
      (node (ref "B40") (pin "F2") (pinfunction "P$2_F2") (pintype "bidirectional"))
      (node (ref "EF38") (pin "BD2") (pinfunction "BD2_BD2") (pintype "input"))
    )
    (net (code "1176") (name "SR10") (class "Default")
      (node (ref "B40") (pin "H2") (pinfunction "P$2_H2") (pintype "bidirectional"))
      (node (ref "EF39") (pin "BE1") (pinfunction "BE1_BE1") (pintype "input"))
    )
    (net (code "1177") (name "SR11") (class "Default")
      (node (ref "B40") (pin "J2") (pinfunction "P$2_J2") (pintype "bidirectional"))
      (node (ref "EF39") (pin "BD2") (pinfunction "BD2_BD2") (pintype "input"))
    )
    (net (code "1178") (name "SR_ENABLE") (class "Default")
      (node (ref "A12") (pin "D1") (pinfunction "IN1_D1") (pintype "input"))
      (node (ref "A12") (pin "H2") (pinfunction "IN1_H2") (pintype "input"))
      (node (ref "A12") (pin "P1") (pinfunction "IN1_P1") (pintype "input"))
      (node (ref "A18") (pin "D1") (pinfunction "IN1_D1") (pintype "input"))
      (node (ref "A18") (pin "H2") (pinfunction "IN1_H2") (pintype "input"))
      (node (ref "A18") (pin "P1") (pinfunction "IN1_P1") (pintype "input"))
      (node (ref "EF34") (pin "BC1") (pinfunction "BC1_BC1") (pintype "input"))
      (node (ref "EF35") (pin "BC1") (pinfunction "BC1_BC1") (pintype "input"))
      (node (ref "EF36") (pin "BC1") (pinfunction "BC1_BC1") (pintype "input"))
      (node (ref "EF37") (pin "BC1") (pinfunction "BC1_BC1") (pintype "input"))
      (node (ref "EF38") (pin "BC1") (pinfunction "BC1_BC1") (pintype "input"))
      (node (ref "EF39") (pin "BC1") (pinfunction "BC1_BC1") (pintype "input"))
      (node (ref "F30") (pin "S1") (pinfunction "OUT_S1") (pintype "open_collector"))
    )
    (net (code "1179") (name "STOP_OK") (class "Default")
      (node (ref "A04") (pin "P2") (pinfunction "P2_P2") (pintype "output"))
      (node (ref "AB02") (pin "AH2") (pinfunction "AH2_AH2") (pintype "input"))
      (node (ref "E13") (pin "K1") (pinfunction "IN4A_K1") (pintype "input"))
    )
    (net (code "1180") (name "STORE_") (class "Default")
      (node (ref "D07") (pin "D2") (pinfunction "IN1_D2") (pintype "input"))
      (node (ref "D09") (pin "P1") (pinfunction "IN1_P1") (pintype "input"))
      (node (ref "D10") (pin "S1") (pinfunction "OUT_S1") (pintype "output"))
      (node (ref "F31") (pin "C1") (pinfunction "IN3_C1") (pintype "input"))
    )
    (net (code "1181") (name "STROBE_") (class "Default")
      (node (ref "B10") (pin "E2") (pinfunction "E2_E2") (pintype "open_collector"))
      (node (ref "E15") (pin "H2") (pinfunction "IN1_H2") (pintype "input"))
      (node (ref "E18") (pin "A1") (pinfunction "R_A1") (pintype "input"))
      (node (ref "E19") (pin "D1") (pinfunction "S_D1") (pintype "input"))
      (node (ref "EF10") (pin "BE2") (pinfunction "P$1_BE2") (pintype "passive"))
      (node (ref "F20") (pin "D1") (pinfunction "IN1_D1") (pintype "input"))
      (node (ref "H05") (pin "P2") (pinfunction "P$2_P2") (pintype "bidirectional"))
    )
    (net (code "1182") (name "S_") (class "Default")
      (node (ref "D09") (pin "R2") (pinfunction "IN3_R2") (pintype "input"))
      (node (ref "D11") (pin "E1") (pinfunction "1_E1") (pintype "output"))
      (node (ref "E09") (pin "A1") (pinfunction "IN1_A1") (pintype "input"))
    )
    (net (code "1183") (name "S_SET_") (class "Default")
      (node (ref "C11") (pin "C1") (pinfunction "IN3_C1") (pintype "input"))
      (node (ref "D10") (pin "E1") (pinfunction "OUT_E1") (pintype "output"))
      (node (ref "D11") (pin "C1") (pinfunction "D_C1") (pintype "input"))
    )
    (net (code "1184") (name "S_UF") (class "Default")
      (node (ref "A05") (pin "J2") (pinfunction "IN2_J2") (pintype "input"))
      (node (ref "B05") (pin "S1") (pinfunction "1_S1") (pintype "output"))
      (node (ref "B06") (pin "P1") (pinfunction "IN1_P1") (pintype "input"))
    )
    (net (code "1185") (name "TAD") (class "Default")
      (node (ref "E22") (pin "F1") (pinfunction "OUT_F1") (pintype "output"))
      (node (ref "F28") (pin "A1") (pinfunction "IN1_A1") (pintype "input"))
    )
    (net (code "1186") (name "TAD_") (class "Default")
      (node (ref "D40") (pin "T2") (pinfunction "P$2_T2") (pintype "bidirectional"))
      (node (ref "E21") (pin "D1") (pinfunction "OUT_D1") (pintype "output"))
      (node (ref "E22") (pin "D1") (pinfunction "IN1_D1") (pintype "input"))
      (node (ref "F26") (pin "U2") (pinfunction "IN2_U2") (pintype "input"))
    )
    (net (code "1187") (name "TP1") (class "Default")
      (node (ref "D07") (pin "U2") (pinfunction "IN2_U2") (pintype "input"))
      (node (ref "E09") (pin "B1") (pinfunction "IN2_B1") (pintype "input"))
      (node (ref "E15") (pin "K2") (pinfunction "OUT_K2") (pintype "output"))
      (node (ref "E20") (pin "L2") (pinfunction "C_L2") (pintype "input"))
      (node (ref "E26") (pin "E1") (pinfunction "IN2A_E1") (pintype "input"))
      (node (ref "E26") (pin "S1") (pinfunction "IN1A_S1") (pintype "input"))
    )
    (net (code "1188") (name "TP2") (class "Default")
      (node (ref "E15") (pin "L1") (pinfunction "IN1_L1") (pintype "input"))
      (node (ref "E17") (pin "F1") (pinfunction "OUT_F1") (pintype "output"))
      (node (ref "E19") (pin "B1") (pinfunction "C_B1") (pintype "input"))
      (node (ref "E22") (pin "L1") (pinfunction "IN1_L1") (pintype "input"))
      (node (ref "E33") (pin "D2") (pinfunction "C_D2") (pintype "input"))
      (node (ref "F25") (pin "P2") (pinfunction "IN1_P2") (pintype "input"))
      (node (ref "F32") (pin "J1") (pinfunction "IN2_J1") (pintype "input"))
    )
    (net (code "1189") (name "TP2E_") (class "Default")
      (node (ref "B04") (pin "K1") (pinfunction "IN1_K1") (pintype "input"))
      (node (ref "B04") (pin "L1") (pinfunction "IN2_L1") (pintype "input"))
      (node (ref "E25") (pin "R1") (pinfunction "IN2_R1") (pintype "input"))
      (node (ref "F25") (pin "S2") (pinfunction "OUT_S2") (pintype "output"))
    )
    (net (code "1190") (name "TP3") (class "Default")
      (node (ref "A13") (pin "D2") (pinfunction "IN1_D2") (pintype "input"))
      (node (ref "A14") (pin "P2") (pinfunction "IN1_P2") (pintype "input"))
      (node (ref "A19") (pin "L1") (pinfunction "IN1_L1") (pintype "input"))
      (node (ref "A20") (pin "B1") (pinfunction "IN2_B1") (pintype "input"))
      (node (ref "B04") (pin "K2") (pinfunction "IN2_K2") (pintype "input"))
      (node (ref "B05") (pin "L2") (pinfunction "C_L2") (pintype "input"))
      (node (ref "B10") (pin "V2") (pinfunction "V2_V2") (pintype "input"))
      (node (ref "B11") (pin "L2") (pinfunction "C_L2") (pintype "input"))
      (node (ref "C08") (pin "J2") (pinfunction "IN2_J2") (pintype "input"))
      (node (ref "D09") (pin "U2") (pinfunction "IN2_U2") (pintype "input"))
      (node (ref "D12") (pin "P2") (pinfunction "IN1_P2") (pintype "input"))
      (node (ref "D14") (pin "P2") (pinfunction "IN1_P2") (pintype "input"))
      (node (ref "D14") (pin "T2") (pinfunction "IN1_T2") (pintype "input"))
      (node (ref "D17") (pin "U2") (pinfunction "IN2_U2") (pintype "input"))
      (node (ref "D18") (pin "M1") (pinfunction "IN3_M1") (pintype "input"))
      (node (ref "E14") (pin "K1") (pinfunction "IN1_K1") (pintype "input"))
      (node (ref "E15") (pin "P1") (pinfunction "IN1_P1") (pintype "input"))
      (node (ref "E17") (pin "J1") (pinfunction "OUT_J1") (pintype "output"))
      (node (ref "E18") (pin "L2") (pinfunction "C_L2") (pintype "input"))
      (node (ref "E19") (pin "D2") (pinfunction "C_D2") (pintype "input"))
      (node (ref "E25") (pin "T2") (pinfunction "IN1_T2") (pintype "input"))
      (node (ref "E26") (pin "A1") (pinfunction "IN1A_A1") (pintype "input"))
      (node (ref "E26") (pin "E2") (pinfunction "IN1B_E2") (pintype "input"))
      (node (ref "E26") (pin "H1") (pinfunction "IN3A_H1") (pintype "input"))
      (node (ref "E26") (pin "M1") (pinfunction "IN5A_M1") (pintype "input"))
      (node (ref "E26") (pin "P2") (pinfunction "IN4B_P2") (pintype "input"))
      (node (ref "F26") (pin "N2") (pinfunction "IN1_N2") (pintype "input"))
    )
    (net (code "1191") (name "TP4") (class "Default")
      (node (ref "D11") (pin "B1") (pinfunction "C_B1") (pintype "input"))
      (node (ref "D11") (pin "D2") (pinfunction "C_D2") (pintype "input"))
      (node (ref "E15") (pin "F2") (pinfunction "OUT_F2") (pintype "output"))
      (node (ref "E18") (pin "B1") (pinfunction "C_B1") (pintype "input"))
      (node (ref "E19") (pin "H1") (pinfunction "C_H1") (pintype "input"))
      (node (ref "E23") (pin "B1") (pinfunction "C_B1") (pintype "input"))
      (node (ref "E23") (pin "D2") (pinfunction "C_D2") (pintype "input"))
      (node (ref "E23") (pin "H1") (pinfunction "C_H1") (pintype "input"))
      (node (ref "E23") (pin "L2") (pinfunction "C_L2") (pintype "input"))
      (node (ref "E23") (pin "N1") (pinfunction "C_N1") (pintype "input"))
      (node (ref "E23") (pin "S2") (pinfunction "C_S2") (pintype "input"))
      (node (ref "E24") (pin "H2") (pinfunction "IN1_H2") (pintype "input"))
      (node (ref "E33") (pin "B1") (pinfunction "C_B1") (pintype "input"))
      (node (ref "F32") (pin "D2") (pinfunction "IN1_D2") (pintype "input"))
    )
    (net (code "1192") (name "TS1") (class "Default")
      (node (ref "C07") (pin "V2") (pinfunction "IN1_V2") (pintype "input"))
      (node (ref "E18") (pin "E1") (pinfunction "1_E1") (pintype "output"))
      (node (ref "E27") (pin "E1") (pinfunction "IN2A_E1") (pintype "input"))
      (node (ref "E30") (pin "E1") (pinfunction "IN2A_E1") (pintype "input"))
    )
    (net (code "1193") (name "TS1_") (class "Default")
      (node (ref "E18") (pin "F1") (pinfunction "0_F1") (pintype "output"))
      (node (ref "H12") (pin "N2") (pinfunction "IN2_N2") (pintype "input"))
    )
    (net (code "1194") (name "TS2") (class "Default")
      (node (ref "C11") (pin "H1") (pinfunction "IN3_H1") (pintype "input"))
      (node (ref "C11") (pin "J2") (pinfunction "IN1_J2") (pintype "input"))
      (node (ref "D09") (pin "B1") (pinfunction "IN2_B1") (pintype "input"))
      (node (ref "D10") (pin "F1") (pinfunction "IN1_F1") (pintype "input"))
      (node (ref "E19") (pin "E1") (pinfunction "1_E1") (pintype "output"))
      (node (ref "E27") (pin "A1") (pinfunction "IN1A_A1") (pintype "input"))
      (node (ref "E27") (pin "P2") (pinfunction "IN4B_P2") (pintype "input"))
      (node (ref "E28") (pin "D2") (pinfunction "IN1A_D2") (pintype "input"))
      (node (ref "E29") (pin "E1") (pinfunction "IN2A_E1") (pintype "input"))
      (node (ref "E30") (pin "P2") (pinfunction "IN4B_P2") (pintype "input"))
      (node (ref "F28") (pin "E1") (pinfunction "IN1_E1") (pintype "input"))
      (node (ref "F28") (pin "K1") (pinfunction "IN1_K1") (pintype "input"))
    )
    (net (code "1195") (name "TS3") (class "Default")
      (node (ref "C11") (pin "K1") (pinfunction "IN1_K1") (pintype "input"))
      (node (ref "C11") (pin "N2") (pinfunction "IN1_N2") (pintype "input"))
      (node (ref "C12") (pin "E2") (pinfunction "IN2_E2") (pintype "input"))
      (node (ref "D09") (pin "D2") (pinfunction "IN1_D2") (pintype "input"))
      (node (ref "D10") (pin "P1") (pinfunction "IN3_P1") (pintype "input"))
      (node (ref "D10") (pin "T2") (pinfunction "IN3_T2") (pintype "input"))
      (node (ref "E19") (pin "H2") (pinfunction "1_H2") (pintype "output"))
      (node (ref "E27") (pin "M1") (pinfunction "IN5A_M1") (pintype "input"))
      (node (ref "E29") (pin "A1") (pinfunction "IN1A_A1") (pintype "input"))
      (node (ref "E30") (pin "M1") (pinfunction "IN5A_M1") (pintype "input"))
      (node (ref "F26") (pin "R1") (pinfunction "IN2_R1") (pintype "input"))
      (node (ref "F27") (pin "A1") (pinfunction "IN1_A1") (pintype "input"))
      (node (ref "F27") (pin "H1") (pinfunction "IN2_H1") (pintype "input"))
      (node (ref "F27") (pin "S2") (pinfunction "IN2_S2") (pintype "input"))
      (node (ref "F28") (pin "B1") (pinfunction "IN2_B1") (pintype "input"))
    )
    (net (code "1196") (name "TS3_") (class "Default")
      (node (ref "E19") (pin "J2") (pinfunction "0_J2") (pintype "output"))
      (node (ref "H12") (pin "H2") (pinfunction "IN2_H2") (pintype "input"))
    )
    (net (code "1197") (name "TS4") (class "Default")
      (node (ref "C12") (pin "L2") (pinfunction "IN2_L2") (pintype "input"))
      (node (ref "E19") (pin "L1") (pinfunction "1_L1") (pintype "output"))
      (node (ref "E29") (pin "K1") (pinfunction "IN4A_K1") (pintype "input"))
      (node (ref "E29") (pin "M1") (pinfunction "IN5A_M1") (pintype "input"))
      (node (ref "E30") (pin "H1") (pinfunction "IN3A_H1") (pintype "input"))
      (node (ref "F27") (pin "D2") (pinfunction "IN1_D2") (pintype "input"))
      (node (ref "F29") (pin "L1") (pinfunction "IN1_L1") (pintype "input"))
      (node (ref "F32") (pin "L1") (pinfunction "IN1_L1") (pintype "input"))
    )
    (net (code "1198") (name "TS4_") (class "Default")
      (node (ref "A19") (pin "J1") (pinfunction "IN2_J1") (pintype "input"))
      (node (ref "E19") (pin "M1") (pinfunction "0_M1") (pintype "output"))
    )
    (net (code "1199") (name "TT_AC_LOAD_") (class "Default")
      (node (ref "D09") (pin "V1") (pinfunction "OUT_V1") (pintype "output"))
      (node (ref "E32") (pin "M2") (pinfunction "IN3_M2") (pintype "input"))
    )
    (net (code "1200") (name "TT_CARRY_INSERT") (class "Default")
      (node (ref "C09") (pin "P1") (pinfunction "IN1_P1") (pintype "input"))
      (node (ref "D09") (pin "N1") (pinfunction "OUT_N1") (pintype "output"))
      (node (ref "E26") (pin "J1") (pinfunction "IN3B_J1") (pintype "input"))
    )
    (net (code "1201") (name "TT_CARRY_INSERT_") (class "Default")
      (node (ref "C09") (pin "S1") (pinfunction "OUT_S1") (pintype "output"))
      (node (ref "E31") (pin "P1") (pinfunction "IN3_P1") (pintype "input"))
      (node (ref "F09") (pin "N2") (pinfunction "IN8_N2") (pintype "input"))
      (node (ref "F27") (pin "N2") (pinfunction "IN4_N2") (pintype "input"))
    )
    (net (code "1202") (name "TT_CARRY_INSERT_C_") (class "Default")
      (node (ref "D09") (pin "H2") (pinfunction "OUT_H2") (pintype "output"))
      (node (ref "D09") (pin "K1") (pinfunction "IN1_K1") (pintype "input"))
    )
    (net (code "1203") (name "TT_CARRY_INSERT_S") (class "Default")
      (node (ref "C09") (pin "S2") (pinfunction "OUT_S2") (pintype "output"))
      (node (ref "EF39") (pin "BE2") (pinfunction "BE2_BE2") (pintype "input"))
    )
    (net (code "1204") (name "TT_CARRY_INSERT_S_") (class "Default")
      (node (ref "C09") (pin "P2") (pinfunction "IN1_P2") (pintype "input"))
      (node (ref "C11") (pin "S2") (pinfunction "OUT_S2") (pintype "output"))
      (node (ref "D09") (pin "L1") (pinfunction "IN2_L1") (pintype "input"))
    )
    (net (code "1205") (name "TT_CYCLE_") (class "Default")
      (node (ref "C10") (pin "N1") (pinfunction "OUT_N1") (pintype "output"))
      (node (ref "F28") (pin "V2") (pinfunction "IN3_V2") (pintype "input"))
    )
    (net (code "1206") (name "TT_DATA") (class "Default")
      (node (ref "C10") (pin "N2") (pinfunction "OUT_N2") (pintype "output"))
      (node (ref "F33") (pin "H2") (pinfunction "IN1D_H2") (pintype "input"))
    )
    (net (code "1207") (name "TT_INCREMENT_") (class "Default")
      (node (ref "D10") (pin "L1") (pinfunction "OUT_L1") (pintype "output"))
      (node (ref "F25") (pin "E2") (pinfunction "IN2_E2") (pintype "input"))
      (node (ref "F25") (pin "J1") (pinfunction "IN2_J1") (pintype "input"))
      (node (ref "F25") (pin "J2") (pinfunction "IN2_J2") (pintype "input"))
    )
    (net (code "1208") (name "TT_INST") (class "Default")
      (node (ref "C10") (pin "F2") (pinfunction "OUT_F2") (pintype "output"))
      (node (ref "C11") (pin "M1") (pinfunction "IN3_M1") (pintype "input"))
      (node (ref "D10") (pin "A1") (pinfunction "IN1_A1") (pintype "input"))
    )
    (net (code "1209") (name "TT_INST_") (class "Default")
      (node (ref "C10") (pin "E2") (pinfunction "IN2_E2") (pintype "input"))
      (node (ref "C10") (pin "M1") (pinfunction "IN2_M1") (pintype "input"))
      (node (ref "D09") (pin "P2") (pinfunction "IN2_P2") (pintype "input"))
      (node (ref "D10") (pin "P2") (pinfunction "OUT_P2") (pintype "output"))
      (node (ref "F19") (pin "C1") (pinfunction "IN3_C1") (pintype "input"))
      (node (ref "F28") (pin "S1") (pinfunction "IN3_S1") (pintype "input"))
      (node (ref "F33") (pin "F2") (pinfunction "IN1C_F2") (pintype "input"))
      (node (ref "H19") (pin "N2") (pinfunction "IN2_N2") (pintype "input"))
    )
    (net (code "1210") (name "TT_IO_ENABLE_") (class "Default")
      (node (ref "C11") (pin "F2") (pinfunction "IN3_F2") (pintype "input"))
      (node (ref "C11") (pin "N1") (pinfunction "OUT_N1") (pintype "output"))
      (node (ref "D09") (pin "S1") (pinfunction "IN3_S1") (pintype "input"))
      (node (ref "F30") (pin "H2") (pinfunction "IN4_H2") (pintype "input"))
    )
    (net (code "1211") (name "TT_LINE_SHIFT_") (class "Default")
      (node (ref "C09") (pin "D2") (pinfunction "IN1_D2") (pintype "input"))
      (node (ref "C11") (pin "M2") (pinfunction "OUT_M2") (pintype "output"))
      (node (ref "EF34") (pin "AB2") (pinfunction "AB2_AB2") (pintype "input"))
      (node (ref "EF35") (pin "AB2") (pinfunction "AB2_AB2") (pintype "input"))
      (node (ref "EF36") (pin "AB2") (pinfunction "AB2_AB2") (pintype "input"))
      (node (ref "EF37") (pin "AB2") (pinfunction "AB2_AB2") (pintype "input"))
      (node (ref "EF38") (pin "AB2") (pinfunction "AB2_AB2") (pintype "input"))
      (node (ref "EF39") (pin "AB2") (pinfunction "AB2_AB2") (pintype "input"))
    )
    (net (code "1212") (name "TT_L_DISABLE") (class "Default")
      (node (ref "C10") (pin "L1") (pinfunction "IN1_L1") (pintype "input"))
      (node (ref "D09") (pin "S2") (pinfunction "OUT_S2") (pintype "output"))
      (node (ref "E28") (pin "J1") (pinfunction "IN3B_J1") (pintype "input"))
    )
    (net (code "1213") (name "TT_RIGHT_SHIFT_ENABLE") (class "Default")
      (node (ref "C10") (pin "E1") (pinfunction "IN2_E1") (pintype "input"))
      (node (ref "C11") (pin "H2") (pinfunction "OUT_H2") (pintype "output"))
    )
    (net (code "1214") (name "TT_RIGHT_SHIFT_ENABLE_") (class "Default")
      (node (ref "C09") (pin "E2") (pinfunction "IN2_E2") (pintype "input"))
      (node (ref "C10") (pin "F1") (pinfunction "OUT_F1") (pintype "output"))
      (node (ref "E31") (pin "H1") (pinfunction "IN2_H1") (pintype "input"))
    )
    (net (code "1215") (name "TT_SET_") (class "Default")
      (node (ref "C10") (pin "C1") (pinfunction "OUT_C1") (pintype "output"))
      (node (ref "E25") (pin "E1") (pinfunction "IN1_E1") (pintype "input"))
      (node (ref "F28") (pin "L2") (pinfunction "IN3_L2") (pintype "input"))
    )
    (net (code "1216") (name "TT_SHIFT_ENABLE") (class "Default")
      (node (ref "C09") (pin "F2") (pinfunction "OUT_F2") (pintype "output"))
      (node (ref "C09") (pin "H1") (pinfunction "IN1_H1") (pintype "input"))
      (node (ref "F33") (pin "E2") (pinfunction "IN1B_E2") (pintype "input"))
    )
    (net (code "1217") (name "TT_SHIFT_ENABLE_") (class "Default")
      (node (ref "C09") (pin "K1") (pinfunction "OUT_K1") (pintype "output"))
      (node (ref "F24") (pin "B1") (pinfunction "IN2_B1") (pintype "input"))
    )
    (net (code "1218") (name "UB") (class "Default")
      (node (ref "B05") (pin "E1") (pinfunction "1_E1") (pintype "output"))
      (node (ref "B06") (pin "P2") (pinfunction "IN1_P2") (pintype "input"))
    )
    (net (code "1219") (name "UF") (class "Default")
      (node (ref "A05") (pin "M1") (pinfunction "IN2_M1") (pintype "input"))
      (node (ref "B05") (pin "H2") (pinfunction "1_H2") (pintype "output"))
      (node (ref "B05") (pin "P1") (pinfunction "D_P1") (pintype "input"))
    )
    (net (code "1220") (name "UF_") (class "Default")
      (node (ref "A06") (pin "J1") (pinfunction "IN2_J1") (pintype "input"))
      (node (ref "B05") (pin "J2") (pinfunction "0_J2") (pintype "output"))
      (node (ref "E13") (pin "D1") (pinfunction "IN1D_D1") (pintype "input"))
      (node (ref "F11") (pin "D1") (pinfunction "IN4_D1") (pintype "input"))
    )
    (net (code "1221") (name "UINT") (class "Default")
      (node (ref "A05") (pin "M2") (pinfunction "IN2_M2") (pintype "input"))
      (node (ref "B04") (pin "J2") (pinfunction "IN1_J2") (pintype "input"))
      (node (ref "B05") (pin "P2") (pinfunction "1_P2") (pintype "output"))
    )
    (net (code "1222") (name "UINT_") (class "Default")
      (node (ref "A05") (pin "S2") (pinfunction "OUT_S2") (pintype "output"))
      (node (ref "J15") (pin "F2") (pinfunction "IN3_F2") (pintype "input"))
    )
    (net (code "1223") (name "USF_") (class "Default")
      (node (ref "B04") (pin "T2") (pinfunction "IN1_T2") (pintype "input"))
      (node (ref "B05") (pin "V1") (pinfunction "0_V1") (pintype "output"))
    )
    (net (code "1224") (name "VCC") (class "Default")
      (node (ref "A40") (pin "A2") (pinfunction "P$2_A2") (pintype "bidirectional"))
      (node (ref "B40") (pin "A2") (pinfunction "P$2_A2") (pintype "bidirectional"))
      (node (ref "C40") (pin "A2") (pinfunction "P$2_A2") (pintype "bidirectional"))
      (node (ref "E40") (pin "A2") (pinfunction "P$2_A2") (pintype "bidirectional"))
      (node (ref "F40") (pin "A2") (pinfunction "P$2_A2") (pintype "bidirectional"))
    )
    (net (code "1225") (name "WC_OVERFLOW_") (class "Default")
      (node (ref "E33") (pin "H2") (pinfunction "1_H2") (pintype "output"))
      (node (ref "H19") (pin "U2") (pinfunction "IN2_U2") (pintype "input"))
    )
    (net (code "1226") (name "WC_SET") (class "Default")
      (node (ref "E23") (pin "M2") (pinfunction "D_M2") (pintype "input"))
      (node (ref "F22") (pin "N2") (pinfunction "OUT_N2") (pintype "output"))
    )
    (net (code "1227") (name "WC_SET_") (class "Default")
      (node (ref "A19") (pin "A1") (pinfunction "IN1_A1") (pintype "input"))
      (node (ref "F22") (pin "L2") (pinfunction "IN1_L2") (pintype "input"))
      (node (ref "F22") (pin "R1") (pinfunction "IN2_R1") (pintype "input"))
      (node (ref "F22") (pin "V2") (pinfunction "OUT_V2") (pintype "output"))
    )
    (net (code "1228") (name "WORD_COUNT") (class "Default")
      (node (ref "E23") (pin "P1") (pinfunction "D_P1") (pintype "input"))
      (node (ref "E23") (pin "P2") (pinfunction "1_P2") (pintype "output"))
      (node (ref "E27") (pin "D2") (pinfunction "IN1A_D2") (pintype "input"))
      (node (ref "E30") (pin "J1") (pinfunction "IN3B_J1") (pintype "input"))
    )
    (net (code "1229") (name "WORD_COUNT_") (class "Default")
      (node (ref "A19") (pin "B1") (pinfunction "IN2_B1") (pintype "input"))
      (node (ref "D40") (pin "A1") (pinfunction "P$2_A1") (pintype "bidirectional"))
      (node (ref "E12") (pin "P2") (pinfunction "IN1_P2") (pintype "input"))
      (node (ref "E23") (pin "R2") (pinfunction "0_R2") (pintype "output"))
      (node (ref "E25") (pin "H1") (pinfunction "IN3_H1") (pintype "input"))
    )
    (net (code "1230") (name "unconnected-(A04-PadT2)") (class "Default")
      (node (ref "A04") (pin "T2") (pinfunction "T2_T2") (pintype "output"))
    )
    (net (code "1231") (name "unconnected-(A08C-ODD-PadK1)") (class "Default")
      (node (ref "A08") (pin "K1") (pinfunction "ODD_K1") (pintype "output"))
    )
    (net (code "1232") (name "unconnected-(A10C-EVEN-PadL1)") (class "Default")
      (node (ref "A10") (pin "L1") (pinfunction "EVEN_L1") (pintype "output"))
    )
    (net (code "1233") (name "unconnected-(AB02-PadBJ2)") (class "Default")
      (node (ref "AB02") (pin "BJ2") (pinfunction "BJ2_BJ2") (pintype "output"))
    )
    (net (code "1234") (name "unconnected-(AB02-PadBK2)") (class "Default")
      (node (ref "AB02") (pin "BK2") (pinfunction "BK2_BK2") (pintype "passive"))
    )
    (net (code "1235") (name "unconnected-(AB02-PadBR2)") (class "Default")
      (node (ref "AB02") (pin "BR2") (pinfunction "BR2_BR2") (pintype "passive"))
    )
    (net (code "1236") (name "unconnected-(AB02-PadBS2)") (class "Default")
      (node (ref "AB02") (pin "BS2") (pinfunction "BS2_BS2") (pintype "passive"))
    )
    (net (code "1237") (name "unconnected-(B05A-0-PadF1)") (class "Default")
      (node (ref "B05") (pin "F1") (pinfunction "0_F1") (pintype "output"))
    )
    (net (code "1238") (name "unconnected-(B05G-0-PadU1)") (class "Default")
      (node (ref "B05") (pin "U1") (pinfunction "0_U1") (pintype "output"))
    )
    (net (code "1239") (name "unconnected-(B05H-1-PadV2)") (class "Default")
      (node (ref "B05") (pin "V2") (pinfunction "1_V2") (pintype "output"))
    )
    (net (code "1240") (name "unconnected-(B11A-1-PadE1)") (class "Default")
      (node (ref "B11") (pin "E1") (pinfunction "1_E1") (pintype "output"))
    )
    (net (code "1241") (name "unconnected-(B11D-1-PadH2)") (class "Default")
      (node (ref "B11") (pin "H2") (pinfunction "1_H2") (pintype "output"))
    )
    (net (code "1242") (name "unconnected-(B11E-1-PadL1)") (class "Default")
      (node (ref "B11") (pin "L1") (pinfunction "1_L1") (pintype "output"))
    )
    (net (code "1243") (name "unconnected-(B11F-0-PadR2)") (class "Default")
      (node (ref "B11") (pin "R2") (pinfunction "0_R2") (pintype "output"))
    )
    (net (code "1244") (name "unconnected-(B11G-0-PadU1)") (class "Default")
      (node (ref "B11") (pin "U1") (pinfunction "0_U1") (pintype "output"))
    )
    (net (code "1245") (name "unconnected-(B17F-0-PadR2)") (class "Default")
      (node (ref "B17") (pin "R2") (pinfunction "0_R2") (pintype "output"))
    )
    (net (code "1246") (name "unconnected-(B17G-0-PadU1)") (class "Default")
      (node (ref "B17") (pin "U1") (pinfunction "0_U1") (pintype "output"))
    )
    (net (code "1247") (name "unconnected-(B17H-0-PadV1)") (class "Default")
      (node (ref "B17") (pin "V1") (pinfunction "0_V1") (pintype "output"))
    )
    (net (code "1248") (name "unconnected-(B18F-0-PadR2)") (class "Default")
      (node (ref "B18") (pin "R2") (pinfunction "0_R2") (pintype "output"))
    )
    (net (code "1249") (name "unconnected-(B18G-0-PadU1)") (class "Default")
      (node (ref "B18") (pin "U1") (pinfunction "0_U1") (pintype "output"))
    )
    (net (code "1250") (name "unconnected-(B18H-0-PadV1)") (class "Default")
      (node (ref "B18") (pin "V1") (pinfunction "0_V1") (pintype "output"))
    )
    (net (code "1251") (name "unconnected-(B19A-0-PadF1)") (class "Default")
      (node (ref "B19") (pin "F1") (pinfunction "0_F1") (pintype "output"))
    )
    (net (code "1252") (name "unconnected-(B19D-0-PadJ2)") (class "Default")
      (node (ref "B19") (pin "J2") (pinfunction "0_J2") (pintype "output"))
    )
    (net (code "1253") (name "unconnected-(B19E-0-PadM1)") (class "Default")
      (node (ref "B19") (pin "M1") (pinfunction "0_M1") (pintype "output"))
    )
    (net (code "1254") (name "unconnected-(B19F-0-PadR2)") (class "Default")
      (node (ref "B19") (pin "R2") (pinfunction "0_R2") (pintype "output"))
    )
    (net (code "1255") (name "unconnected-(B19G-0-PadU1)") (class "Default")
      (node (ref "B19") (pin "U1") (pinfunction "0_U1") (pintype "output"))
    )
    (net (code "1256") (name "unconnected-(B19H-0-PadV1)") (class "Default")
      (node (ref "B19") (pin "V1") (pinfunction "0_V1") (pintype "output"))
    )
    (net (code "1257") (name "unconnected-(C13-PadJ2)") (class "Default")
      (node (ref "C13") (pin "J2") (pinfunction "J2_J2") (pintype "output"))
    )
    (net (code "1258") (name "unconnected-(C13-PadK2)") (class "Default")
      (node (ref "C13") (pin "K2") (pinfunction "K2_K2") (pintype "output"))
    )
    (net (code "1259") (name "unconnected-(C13-PadL2)") (class "Default")
      (node (ref "C13") (pin "L2") (pinfunction "L2_L2") (pintype "output"))
    )
    (net (code "1260") (name "unconnected-(C13-PadM2)") (class "Default")
      (node (ref "C13") (pin "M2") (pinfunction "M2_M2") (pintype "output"))
    )
    (net (code "1261") (name "unconnected-(C13-PadN2)") (class "Default")
      (node (ref "C13") (pin "N2") (pinfunction "N2_N2") (pintype "output"))
    )
    (net (code "1262") (name "unconnected-(C13-PadR2)") (class "Default")
      (node (ref "C13") (pin "R2") (pinfunction "R2_R2") (pintype "output"))
    )
    (net (code "1263") (name "unconnected-(C13-PadT2)") (class "Default")
      (node (ref "C13") (pin "T2") (pinfunction "T2_T2") (pintype "output"))
    )
    (net (code "1264") (name "unconnected-(C13-PadU2)") (class "Default")
      (node (ref "C13") (pin "U2") (pinfunction "U2_U2") (pintype "output"))
    )
    (net (code "1265") (name "unconnected-(C13-PadV2)") (class "Default")
      (node (ref "C13") (pin "V2") (pinfunction "V2_V2") (pintype "output"))
    )
    (net (code "1266") (name "unconnected-(C22H-0-PadV1)") (class "Default")
      (node (ref "C22") (pin "V1") (pinfunction "0_V1") (pintype "output"))
    )
    (net (code "1267") (name "unconnected-(D06-PadJ2)") (class "Default")
      (node (ref "D06") (pin "J2") (pinfunction "J2_J2") (pintype "output"))
    )
    (net (code "1268") (name "unconnected-(D06-PadK2)") (class "Default")
      (node (ref "D06") (pin "K2") (pinfunction "K2_K2") (pintype "output"))
    )
    (net (code "1269") (name "unconnected-(D06-PadL2)") (class "Default")
      (node (ref "D06") (pin "L2") (pinfunction "L2_L2") (pintype "output"))
    )
    (net (code "1270") (name "unconnected-(D06-PadM2)") (class "Default")
      (node (ref "D06") (pin "M2") (pinfunction "M2_M2") (pintype "output"))
    )
    (net (code "1271") (name "unconnected-(D06-PadN2)") (class "Default")
      (node (ref "D06") (pin "N2") (pinfunction "N2_N2") (pintype "output"))
    )
    (net (code "1272") (name "unconnected-(D06-PadP2)") (class "Default")
      (node (ref "D06") (pin "P2") (pinfunction "P2_P2") (pintype "output"))
    )
    (net (code "1273") (name "unconnected-(D06-PadS2)") (class "Default")
      (node (ref "D06") (pin "S2") (pinfunction "S2_S2") (pintype "output"))
    )
    (net (code "1274") (name "unconnected-(D06-PadT2)") (class "Default")
      (node (ref "D06") (pin "T2") (pinfunction "T2_T2") (pintype "output"))
    )
    (net (code "1275") (name "unconnected-(D06-PadU2)") (class "Default")
      (node (ref "D06") (pin "U2") (pinfunction "U2_U2") (pintype "output"))
    )
    (net (code "1276") (name "unconnected-(D06-PadV2)") (class "Default")
      (node (ref "D06") (pin "V2") (pinfunction "V2_V2") (pintype "output"))
    )
    (net (code "1277") (name "unconnected-(D24G-0-PadU1)") (class "Default")
      (node (ref "D24") (pin "U1") (pinfunction "0_U1") (pintype "output"))
    )
    (net (code "1278") (name "unconnected-(D24H-0-PadV1)") (class "Default")
      (node (ref "D24") (pin "V1") (pinfunction "0_V1") (pintype "output"))
    )
    (net (code "1279") (name "unconnected-(E16-PadJ2)") (class "Default")
      (node (ref "E16") (pin "J2") (pinfunction "J2_J2") (pintype "output"))
    )
    (net (code "1280") (name "unconnected-(E16-PadK2)") (class "Default")
      (node (ref "E16") (pin "K2") (pinfunction "K2_K2") (pintype "output"))
    )
    (net (code "1281") (name "unconnected-(E16-PadL2)") (class "Default")
      (node (ref "E16") (pin "L2") (pinfunction "L2_L2") (pintype "output"))
    )
    (net (code "1282") (name "unconnected-(E16-PadM2)") (class "Default")
      (node (ref "E16") (pin "M2") (pinfunction "M2_M2") (pintype "output"))
    )
    (net (code "1283") (name "unconnected-(E16-PadN2)") (class "Default")
      (node (ref "E16") (pin "N2") (pinfunction "N2_N2") (pintype "output"))
    )
    (net (code "1284") (name "unconnected-(E16-PadP2)") (class "Default")
      (node (ref "E16") (pin "P2") (pinfunction "P2_P2") (pintype "output"))
    )
    (net (code "1285") (name "unconnected-(E16-PadS2)") (class "Default")
      (node (ref "E16") (pin "S2") (pinfunction "S2_S2") (pintype "output"))
    )
    (net (code "1286") (name "unconnected-(E16-PadT2)") (class "Default")
      (node (ref "E16") (pin "T2") (pinfunction "T2_T2") (pintype "output"))
    )
    (net (code "1287") (name "unconnected-(E16-PadU2)") (class "Default")
      (node (ref "E16") (pin "U2") (pinfunction "U2_U2") (pintype "output"))
    )
    (net (code "1288") (name "unconnected-(E16-PadV2)") (class "Default")
      (node (ref "E16") (pin "V2") (pinfunction "V2_V2") (pintype "output"))
    )
    (net (code "1289") (name "unconnected-(E17-PadJ2)") (class "Default")
      (node (ref "E17") (pin "J2") (pinfunction "J2_J2") (pintype "output"))
    )
    (net (code "1290") (name "unconnected-(E17-PadK2)") (class "Default")
      (node (ref "E17") (pin "K2") (pinfunction "K2_K2") (pintype "output"))
    )
    (net (code "1291") (name "unconnected-(E17-PadL2)") (class "Default")
      (node (ref "E17") (pin "L2") (pinfunction "L2_L2") (pintype "output"))
    )
    (net (code "1292") (name "unconnected-(E17-PadN2)") (class "Default")
      (node (ref "E17") (pin "N2") (pinfunction "N2_N2") (pintype "output"))
    )
    (net (code "1293") (name "unconnected-(E17-PadP2)") (class "Default")
      (node (ref "E17") (pin "P2") (pinfunction "P2_P2") (pintype "output"))
    )
    (net (code "1294") (name "unconnected-(E17-PadR2)") (class "Default")
      (node (ref "E17") (pin "R2") (pinfunction "R2_R2") (pintype "output"))
    )
    (net (code "1295") (name "unconnected-(E17-PadS2)") (class "Default")
      (node (ref "E17") (pin "S2") (pinfunction "S2_S2") (pintype "output"))
    )
    (net (code "1296") (name "unconnected-(E17-PadT2)") (class "Default")
      (node (ref "E17") (pin "T2") (pinfunction "T2_T2") (pintype "output"))
    )
    (net (code "1297") (name "unconnected-(E17-PadV2)") (class "Default")
      (node (ref "E17") (pin "V2") (pinfunction "V2_V2") (pintype "output"))
    )
    (net (code "1298") (name "unconnected-(E18D-0-PadJ2)") (class "Default")
      (node (ref "E18") (pin "J2") (pinfunction "0_J2") (pintype "output"))
    )
    (net (code "1299") (name "unconnected-(E18E-1-PadL1)") (class "Default")
      (node (ref "E18") (pin "L1") (pinfunction "1_L1") (pintype "output"))
    )
    (net (code "1300") (name "unconnected-(E18G-0-PadU1)") (class "Default")
      (node (ref "E18") (pin "U1") (pinfunction "0_U1") (pintype "output"))
    )
    (net (code "1301") (name "unconnected-(E19A-0-PadF1)") (class "Default")
      (node (ref "E19") (pin "F1") (pinfunction "0_F1") (pintype "output"))
    )
    (net (code "1302") (name "unconnected-(E20F-0-PadR2)") (class "Default")
      (node (ref "E20") (pin "R2") (pinfunction "0_R2") (pintype "output"))
    )
    (net (code "1303") (name "unconnected-(E20G-0-PadU1)") (class "Default")
      (node (ref "E20") (pin "U1") (pinfunction "0_U1") (pintype "output"))
    )
    (net (code "1304") (name "unconnected-(E22N-OUT-PadV2)") (class "Default")
      (node (ref "E22") (pin "V2") (pinfunction "OUT_V2") (pintype "output"))
    )
    (net (code "1305") (name "unconnected-(E23A-1-PadE1)") (class "Default")
      (node (ref "E23") (pin "E1") (pinfunction "1_E1") (pintype "output"))
    )
    (net (code "1306") (name "unconnected-(E23E-1-PadL1)") (class "Default")
      (node (ref "E23") (pin "L1") (pinfunction "1_L1") (pintype "output"))
    )
    (net (code "1307") (name "unconnected-(E33A-0-PadF1)") (class "Default")
      (node (ref "E33") (pin "F1") (pinfunction "0_F1") (pintype "output"))
    )
    (net (code "1308") (name "unconnected-(E33D-0-PadJ2)") (class "Default")
      (node (ref "E33") (pin "J2") (pinfunction "0_J2") (pintype "output"))
    )
    (net (code "1309") (name "unconnected-(E33E-1-PadL1)") (class "Default")
      (node (ref "E33") (pin "L1") (pinfunction "1_L1") (pintype "output"))
    )
    (net (code "1310") (name "unconnected-(E33F-1-PadP2)") (class "Default")
      (node (ref "E33") (pin "P2") (pinfunction "1_P2") (pintype "output"))
    )
    (net (code "1311") (name "unconnected-(EF10C-CN2-PadAN2)") (class "Default")
      (node (ref "EF10") (pin "AN2") (pinfunction "CN2_AN2") (pintype "output"))
    )
    (net (code "1312") (name "unconnected-(EF34-PadAJ1)") (class "Default")
      (node (ref "EF34") (pin "AJ1") (pinfunction "AJ1_AJ1") (pintype "output"))
    )
    (net (code "1313") (name "unconnected-(EF34-PadAK2)") (class "Default")
      (node (ref "EF34") (pin "AK2") (pinfunction "AK2_AK2") (pintype "output"))
    )
    (net (code "1314") (name "unconnected-(EF34-PadAL2)") (class "Default")
      (node (ref "EF34") (pin "AL2") (pinfunction "AL2_AL2") (pintype "output"))
    )
    (net (code "1315") (name "unconnected-(EF34-PadAM2)") (class "Default")
      (node (ref "EF34") (pin "AM2") (pinfunction "AM2_AM2") (pintype "output"))
    )
    (net (code "1316") (name "unconnected-(EF34-PadAN1)") (class "Default")
      (node (ref "EF34") (pin "AN1") (pinfunction "AN1_AN1") (pintype "output"))
    )
    (net (code "1317") (name "unconnected-(EF34-PadAP1)") (class "Default")
      (node (ref "EF34") (pin "AP1") (pinfunction "AP1_AP1") (pintype "output"))
    )
    (net (code "1318") (name "unconnected-(EF35-PadAJ1)") (class "Default")
      (node (ref "EF35") (pin "AJ1") (pinfunction "AJ1_AJ1") (pintype "output"))
    )
    (net (code "1319") (name "unconnected-(EF35-PadAK2)") (class "Default")
      (node (ref "EF35") (pin "AK2") (pinfunction "AK2_AK2") (pintype "output"))
    )
    (net (code "1320") (name "unconnected-(EF35-PadAL2)") (class "Default")
      (node (ref "EF35") (pin "AL2") (pinfunction "AL2_AL2") (pintype "output"))
    )
    (net (code "1321") (name "unconnected-(EF35-PadAM2)") (class "Default")
      (node (ref "EF35") (pin "AM2") (pinfunction "AM2_AM2") (pintype "output"))
    )
    (net (code "1322") (name "unconnected-(EF35-PadAN1)") (class "Default")
      (node (ref "EF35") (pin "AN1") (pinfunction "AN1_AN1") (pintype "output"))
    )
    (net (code "1323") (name "unconnected-(EF35-PadAP1)") (class "Default")
      (node (ref "EF35") (pin "AP1") (pinfunction "AP1_AP1") (pintype "output"))
    )
    (net (code "1324") (name "unconnected-(EF36-PadAJ1)") (class "Default")
      (node (ref "EF36") (pin "AJ1") (pinfunction "AJ1_AJ1") (pintype "output"))
    )
    (net (code "1325") (name "unconnected-(EF36-PadAK2)") (class "Default")
      (node (ref "EF36") (pin "AK2") (pinfunction "AK2_AK2") (pintype "output"))
    )
    (net (code "1326") (name "unconnected-(EF36-PadAL2)") (class "Default")
      (node (ref "EF36") (pin "AL2") (pinfunction "AL2_AL2") (pintype "output"))
    )
    (net (code "1327") (name "unconnected-(EF36-PadAM2)") (class "Default")
      (node (ref "EF36") (pin "AM2") (pinfunction "AM2_AM2") (pintype "output"))
    )
    (net (code "1328") (name "unconnected-(EF36-PadAN1)") (class "Default")
      (node (ref "EF36") (pin "AN1") (pinfunction "AN1_AN1") (pintype "output"))
    )
    (net (code "1329") (name "unconnected-(EF36-PadAP1)") (class "Default")
      (node (ref "EF36") (pin "AP1") (pinfunction "AP1_AP1") (pintype "output"))
    )
    (net (code "1330") (name "unconnected-(EF37-PadAJ1)") (class "Default")
      (node (ref "EF37") (pin "AJ1") (pinfunction "AJ1_AJ1") (pintype "output"))
    )
    (net (code "1331") (name "unconnected-(EF37-PadAK2)") (class "Default")
      (node (ref "EF37") (pin "AK2") (pinfunction "AK2_AK2") (pintype "output"))
    )
    (net (code "1332") (name "unconnected-(EF37-PadAL2)") (class "Default")
      (node (ref "EF37") (pin "AL2") (pinfunction "AL2_AL2") (pintype "output"))
    )
    (net (code "1333") (name "unconnected-(EF37-PadAM2)") (class "Default")
      (node (ref "EF37") (pin "AM2") (pinfunction "AM2_AM2") (pintype "output"))
    )
    (net (code "1334") (name "unconnected-(EF37-PadAN1)") (class "Default")
      (node (ref "EF37") (pin "AN1") (pinfunction "AN1_AN1") (pintype "output"))
    )
    (net (code "1335") (name "unconnected-(EF37-PadAP1)") (class "Default")
      (node (ref "EF37") (pin "AP1") (pinfunction "AP1_AP1") (pintype "output"))
    )
    (net (code "1336") (name "unconnected-(EF38-PadAJ1)") (class "Default")
      (node (ref "EF38") (pin "AJ1") (pinfunction "AJ1_AJ1") (pintype "output"))
    )
    (net (code "1337") (name "unconnected-(EF38-PadAK2)") (class "Default")
      (node (ref "EF38") (pin "AK2") (pinfunction "AK2_AK2") (pintype "output"))
    )
    (net (code "1338") (name "unconnected-(EF38-PadAL2)") (class "Default")
      (node (ref "EF38") (pin "AL2") (pinfunction "AL2_AL2") (pintype "output"))
    )
    (net (code "1339") (name "unconnected-(EF38-PadAN1)") (class "Default")
      (node (ref "EF38") (pin "AN1") (pinfunction "AN1_AN1") (pintype "output"))
    )
    (net (code "1340") (name "unconnected-(EF38-PadAP1)") (class "Default")
      (node (ref "EF38") (pin "AP1") (pinfunction "AP1_AP1") (pintype "output"))
    )
    (net (code "1341") (name "unconnected-(EF39-PadAJ1)") (class "Default")
      (node (ref "EF39") (pin "AJ1") (pinfunction "AJ1_AJ1") (pintype "output"))
    )
    (net (code "1342") (name "unconnected-(EF39-PadAK2)") (class "Default")
      (node (ref "EF39") (pin "AK2") (pinfunction "AK2_AK2") (pintype "output"))
    )
    (net (code "1343") (name "unconnected-(EF39-PadAL2)") (class "Default")
      (node (ref "EF39") (pin "AL2") (pinfunction "AL2_AL2") (pintype "output"))
    )
    (net (code "1344") (name "unconnected-(EF39-PadAM2)") (class "Default")
      (node (ref "EF39") (pin "AM2") (pinfunction "AM2_AM2") (pintype "output"))
    )
    (net (code "1345") (name "unconnected-(EF39-PadAN1)") (class "Default")
      (node (ref "EF39") (pin "AN1") (pinfunction "AN1_AN1") (pintype "output"))
    )
    (net (code "1346") (name "unconnected-(EF39-PadAP1)") (class "Default")
      (node (ref "EF39") (pin "AP1") (pinfunction "AP1_AP1") (pintype "output"))
    )
    (net (code "1347") (name "unconnected-(F12-PadJ2)") (class "Default")
      (node (ref "F12") (pin "J2") (pinfunction "J2_J2") (pintype "output"))
    )
    (net (code "1348") (name "unconnected-(F12-PadK2)") (class "Default")
      (node (ref "F12") (pin "K2") (pinfunction "K2_K2") (pintype "output"))
    )
    (net (code "1349") (name "unconnected-(F12-PadL2)") (class "Default")
      (node (ref "F12") (pin "L2") (pinfunction "L2_L2") (pintype "output"))
    )
    (net (code "1350") (name "unconnected-(F12-PadM2)") (class "Default")
      (node (ref "F12") (pin "M2") (pinfunction "M2_M2") (pintype "output"))
    )
    (net (code "1351") (name "unconnected-(F12-PadN2)") (class "Default")
      (node (ref "F12") (pin "N2") (pinfunction "N2_N2") (pintype "output"))
    )
    (net (code "1352") (name "unconnected-(F12-PadP2)") (class "Default")
      (node (ref "F12") (pin "P2") (pinfunction "P2_P2") (pintype "output"))
    )
    (net (code "1353") (name "unconnected-(F12-PadR2)") (class "Default")
      (node (ref "F12") (pin "R2") (pinfunction "R2_R2") (pintype "output"))
    )
    (net (code "1354") (name "unconnected-(F12-PadS2)") (class "Default")
      (node (ref "F12") (pin "S2") (pinfunction "S2_S2") (pintype "output"))
    )
    (net (code "1355") (name "unconnected-(F12-PadU2)") (class "Default")
      (node (ref "F12") (pin "U2") (pinfunction "U2_U2") (pintype "output"))
    )
    (net (code "1356") (name "unconnected-(F12-PadV2)") (class "Default")
      (node (ref "F12") (pin "V2") (pinfunction "V2_V2") (pintype "output"))
    )
    (net (code "1357") (name "unconnected-(F13-PadJ2)") (class "Default")
      (node (ref "F13") (pin "J2") (pinfunction "J2_J2") (pintype "output"))
    )
    (net (code "1358") (name "unconnected-(F13-PadK2)") (class "Default")
      (node (ref "F13") (pin "K2") (pinfunction "K2_K2") (pintype "output"))
    )
    (net (code "1359") (name "unconnected-(F13-PadL2)") (class "Default")
      (node (ref "F13") (pin "L2") (pinfunction "L2_L2") (pintype "output"))
    )
    (net (code "1360") (name "unconnected-(F13-PadN2)") (class "Default")
      (node (ref "F13") (pin "N2") (pinfunction "N2_N2") (pintype "output"))
    )
    (net (code "1361") (name "unconnected-(F13-PadP2)") (class "Default")
      (node (ref "F13") (pin "P2") (pinfunction "P2_P2") (pintype "output"))
    )
    (net (code "1362") (name "unconnected-(F13-PadR2)") (class "Default")
      (node (ref "F13") (pin "R2") (pinfunction "R2_R2") (pintype "output"))
    )
    (net (code "1363") (name "unconnected-(F13-PadS2)") (class "Default")
      (node (ref "F13") (pin "S2") (pinfunction "S2_S2") (pintype "output"))
    )
    (net (code "1364") (name "unconnected-(F13-PadU2)") (class "Default")
      (node (ref "F13") (pin "U2") (pinfunction "U2_U2") (pintype "output"))
    )
    (net (code "1365") (name "unconnected-(F13-PadV2)") (class "Default")
      (node (ref "F13") (pin "V2") (pinfunction "V2_V2") (pintype "output"))
    )
    (net (code "1366") (name "unconnected-(F14-PadJ2)") (class "Default")
      (node (ref "F14") (pin "J2") (pinfunction "J2_J2") (pintype "output"))
    )
    (net (code "1367") (name "unconnected-(F14-PadK2)") (class "Default")
      (node (ref "F14") (pin "K2") (pinfunction "K2_K2") (pintype "output"))
    )
    (net (code "1368") (name "unconnected-(F14-PadL2)") (class "Default")
      (node (ref "F14") (pin "L2") (pinfunction "L2_L2") (pintype "output"))
    )
    (net (code "1369") (name "unconnected-(F14-PadM2)") (class "Default")
      (node (ref "F14") (pin "M2") (pinfunction "M2_M2") (pintype "output"))
    )
    (net (code "1370") (name "unconnected-(F14-PadN2)") (class "Default")
      (node (ref "F14") (pin "N2") (pinfunction "N2_N2") (pintype "output"))
    )
    (net (code "1371") (name "unconnected-(F14-PadP2)") (class "Default")
      (node (ref "F14") (pin "P2") (pinfunction "P2_P2") (pintype "output"))
    )
    (net (code "1372") (name "unconnected-(F14-PadR2)") (class "Default")
      (node (ref "F14") (pin "R2") (pinfunction "R2_R2") (pintype "output"))
    )
    (net (code "1373") (name "unconnected-(F14-PadU2)") (class "Default")
      (node (ref "F14") (pin "U2") (pinfunction "U2_U2") (pintype "output"))
    )
    (net (code "1374") (name "unconnected-(F14-PadV2)") (class "Default")
      (node (ref "F14") (pin "V2") (pinfunction "V2_V2") (pintype "output"))
    )
    (net (code "1375") (name "unconnected-(F15-PadJ2)") (class "Default")
      (node (ref "F15") (pin "J2") (pinfunction "J2_J2") (pintype "output"))
    )
    (net (code "1376") (name "unconnected-(F15-PadK2)") (class "Default")
      (node (ref "F15") (pin "K2") (pinfunction "K2_K2") (pintype "output"))
    )
    (net (code "1377") (name "unconnected-(F15-PadL2)") (class "Default")
      (node (ref "F15") (pin "L2") (pinfunction "L2_L2") (pintype "output"))
    )
    (net (code "1378") (name "unconnected-(F15-PadN2)") (class "Default")
      (node (ref "F15") (pin "N2") (pinfunction "N2_N2") (pintype "output"))
    )
    (net (code "1379") (name "unconnected-(F15-PadP2)") (class "Default")
      (node (ref "F15") (pin "P2") (pinfunction "P2_P2") (pintype "output"))
    )
    (net (code "1380") (name "unconnected-(F15-PadR2)") (class "Default")
      (node (ref "F15") (pin "R2") (pinfunction "R2_R2") (pintype "output"))
    )
    (net (code "1381") (name "unconnected-(F15-PadS2)") (class "Default")
      (node (ref "F15") (pin "S2") (pinfunction "S2_S2") (pintype "output"))
    )
    (net (code "1382") (name "unconnected-(F15-PadU2)") (class "Default")
      (node (ref "F15") (pin "U2") (pinfunction "U2_U2") (pintype "output"))
    )
    (net (code "1383") (name "unconnected-(F15-PadV2)") (class "Default")
      (node (ref "F15") (pin "V2") (pinfunction "V2_V2") (pintype "output"))
    )
    (net (code "1384") (name "unconnected-(F16-PadJ2)") (class "Default")
      (node (ref "F16") (pin "J2") (pinfunction "J2_J2") (pintype "output"))
    )
    (net (code "1385") (name "unconnected-(F16-PadK2)") (class "Default")
      (node (ref "F16") (pin "K2") (pinfunction "K2_K2") (pintype "output"))
    )
    (net (code "1386") (name "unconnected-(F16-PadL2)") (class "Default")
      (node (ref "F16") (pin "L2") (pinfunction "L2_L2") (pintype "output"))
    )
    (net (code "1387") (name "unconnected-(F16-PadM2)") (class "Default")
      (node (ref "F16") (pin "M2") (pinfunction "M2_M2") (pintype "output"))
    )
    (net (code "1388") (name "unconnected-(F16-PadN2)") (class "Default")
      (node (ref "F16") (pin "N2") (pinfunction "N2_N2") (pintype "output"))
    )
    (net (code "1389") (name "unconnected-(F16-PadP2)") (class "Default")
      (node (ref "F16") (pin "P2") (pinfunction "P2_P2") (pintype "output"))
    )
    (net (code "1390") (name "unconnected-(F16-PadR2)") (class "Default")
      (node (ref "F16") (pin "R2") (pinfunction "R2_R2") (pintype "output"))
    )
    (net (code "1391") (name "unconnected-(F16-PadU2)") (class "Default")
      (node (ref "F16") (pin "U2") (pinfunction "U2_U2") (pintype "output"))
    )
    (net (code "1392") (name "unconnected-(F16-PadV2)") (class "Default")
      (node (ref "F16") (pin "V2") (pinfunction "V2_V2") (pintype "output"))
    )
    (net (code "1393") (name "unconnected-(F17-PadJ2)") (class "Default")
      (node (ref "F17") (pin "J2") (pinfunction "J2_J2") (pintype "output"))
    )
    (net (code "1394") (name "unconnected-(F17-PadK2)") (class "Default")
      (node (ref "F17") (pin "K2") (pinfunction "K2_K2") (pintype "output"))
    )
    (net (code "1395") (name "unconnected-(F17-PadL2)") (class "Default")
      (node (ref "F17") (pin "L2") (pinfunction "L2_L2") (pintype "output"))
    )
    (net (code "1396") (name "unconnected-(F17-PadN2)") (class "Default")
      (node (ref "F17") (pin "N2") (pinfunction "N2_N2") (pintype "output"))
    )
    (net (code "1397") (name "unconnected-(F17-PadP2)") (class "Default")
      (node (ref "F17") (pin "P2") (pinfunction "P2_P2") (pintype "output"))
    )
    (net (code "1398") (name "unconnected-(F17-PadR2)") (class "Default")
      (node (ref "F17") (pin "R2") (pinfunction "R2_R2") (pintype "output"))
    )
    (net (code "1399") (name "unconnected-(F17-PadS2)") (class "Default")
      (node (ref "F17") (pin "S2") (pinfunction "S2_S2") (pintype "output"))
    )
    (net (code "1400") (name "unconnected-(F17-PadU2)") (class "Default")
      (node (ref "F17") (pin "U2") (pinfunction "U2_U2") (pintype "output"))
    )
    (net (code "1401") (name "unconnected-(F17-PadV2)") (class "Default")
      (node (ref "F17") (pin "V2") (pinfunction "V2_V2") (pintype "output"))
    )
    (net (code "1402") (name "unconnected-(F18-PadJ2)") (class "Default")
      (node (ref "F18") (pin "J2") (pinfunction "J2_J2") (pintype "output"))
    )
    (net (code "1403") (name "unconnected-(F18-PadK2)") (class "Default")
      (node (ref "F18") (pin "K2") (pinfunction "K2_K2") (pintype "output"))
    )
    (net (code "1404") (name "unconnected-(F18-PadL2)") (class "Default")
      (node (ref "F18") (pin "L2") (pinfunction "L2_L2") (pintype "output"))
    )
    (net (code "1405") (name "unconnected-(F18-PadM2)") (class "Default")
      (node (ref "F18") (pin "M2") (pinfunction "M2_M2") (pintype "output"))
    )
    (net (code "1406") (name "unconnected-(F18-PadN2)") (class "Default")
      (node (ref "F18") (pin "N2") (pinfunction "N2_N2") (pintype "output"))
    )
    (net (code "1407") (name "unconnected-(F18-PadP2)") (class "Default")
      (node (ref "F18") (pin "P2") (pinfunction "P2_P2") (pintype "output"))
    )
    (net (code "1408") (name "unconnected-(F18-PadR2)") (class "Default")
      (node (ref "F18") (pin "R2") (pinfunction "R2_R2") (pintype "output"))
    )
    (net (code "1409") (name "unconnected-(F18-PadU2)") (class "Default")
      (node (ref "F18") (pin "U2") (pinfunction "U2_U2") (pintype "output"))
    )
    (net (code "1410") (name "unconnected-(F18-PadV2)") (class "Default")
      (node (ref "F18") (pin "V2") (pinfunction "V2_V2") (pintype "output"))
    )
    (net (code "1411") (name "unconnected-(J15A-IN2-PadB1)") (class "Default")
      (node (ref "J15") (pin "B1") (pinfunction "IN2_B1") (pintype "passive"))
    )
  )
)
